# pdp8i-fpga.net
KiCad netlist of a schematic drawn in EAGLE
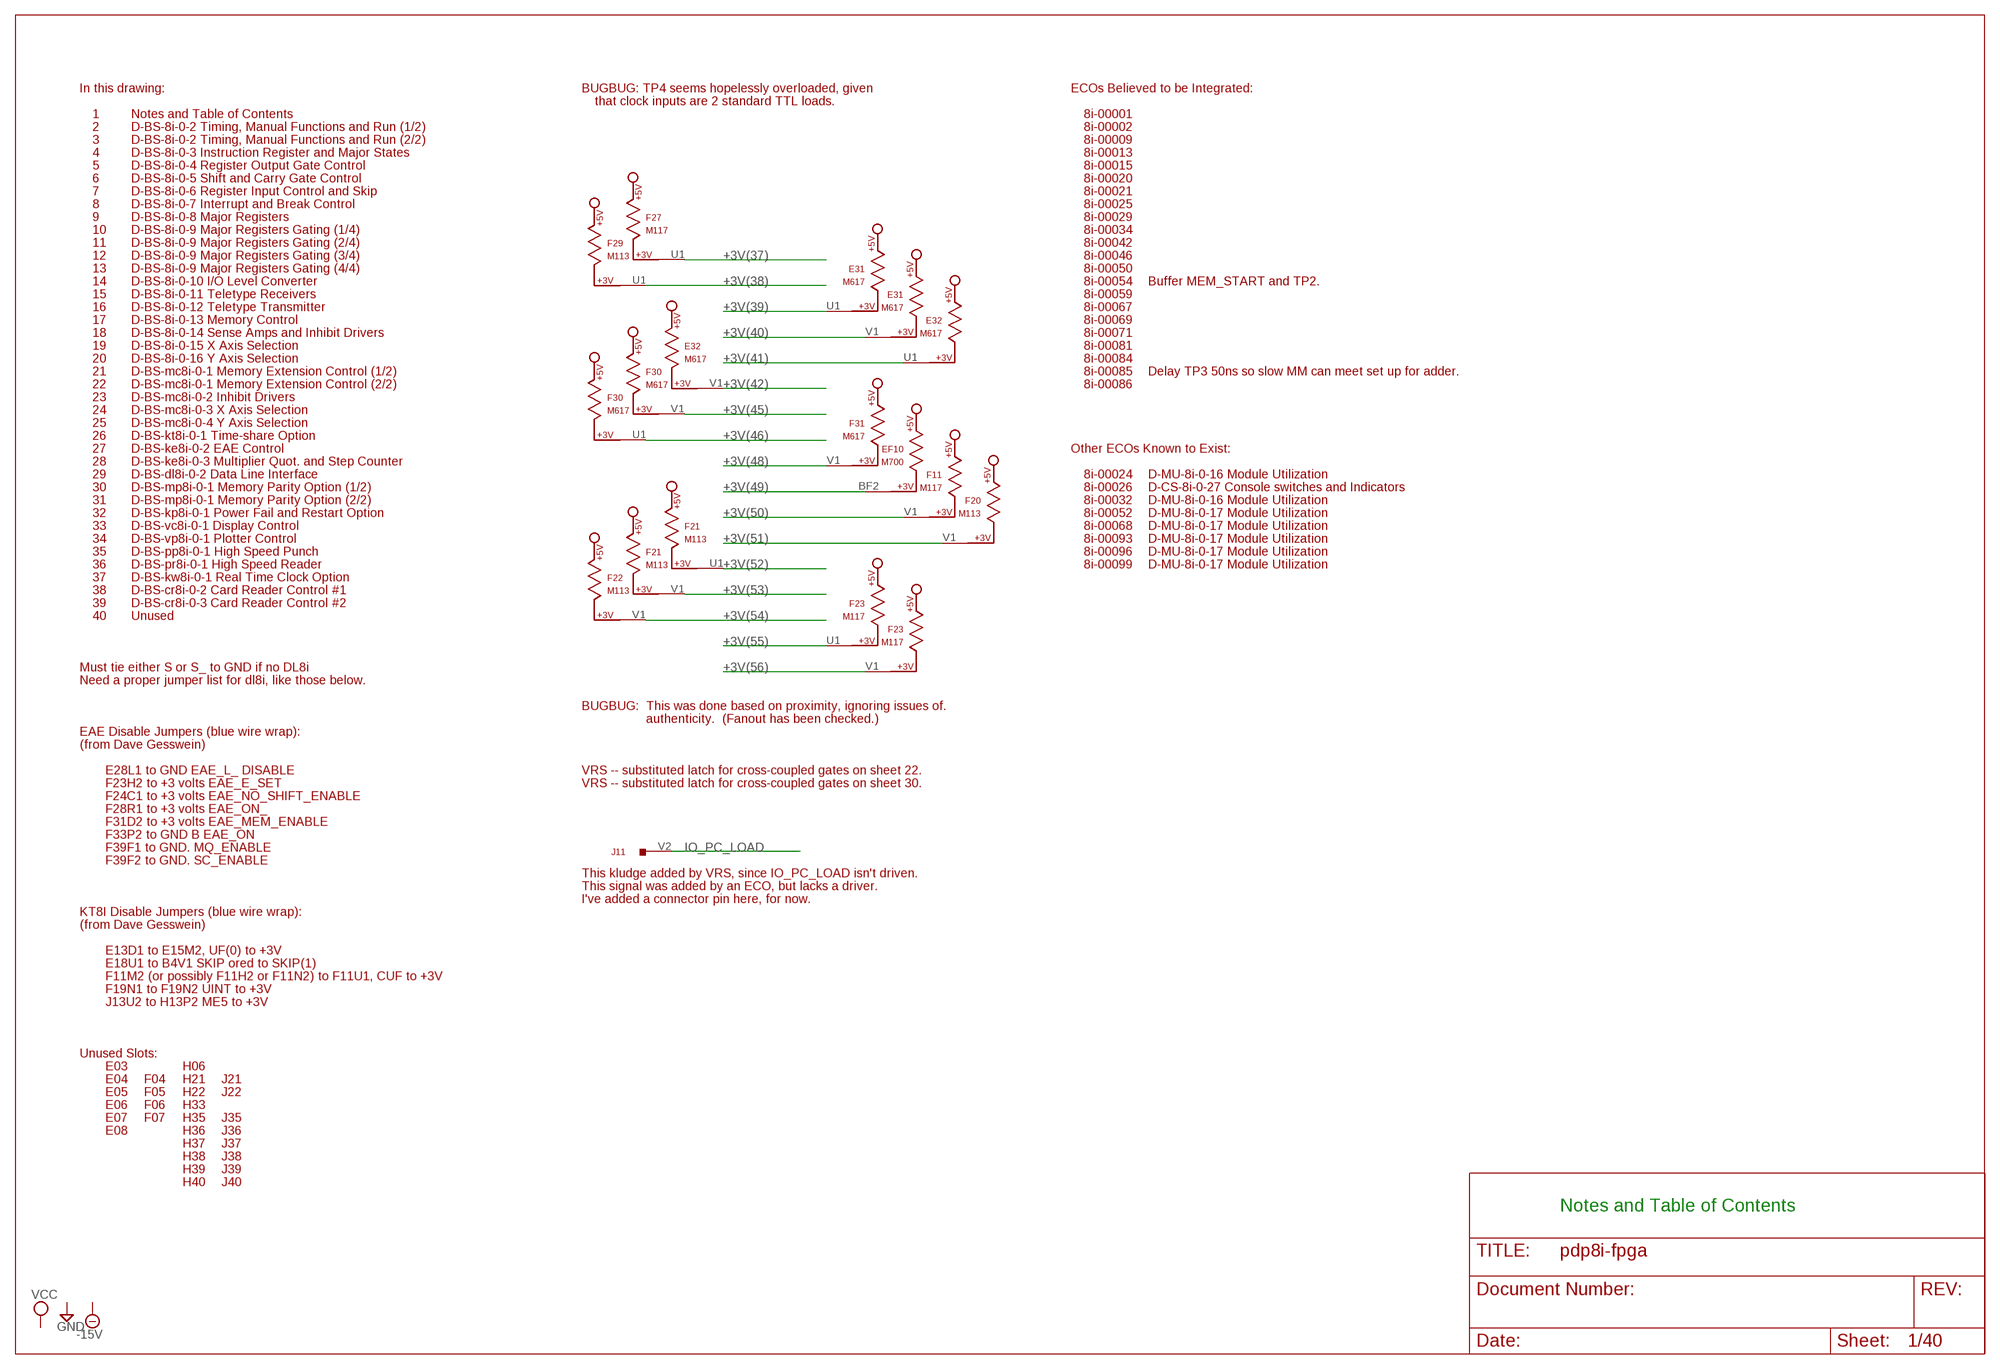
[diagram p0: schematic, sheet 1]
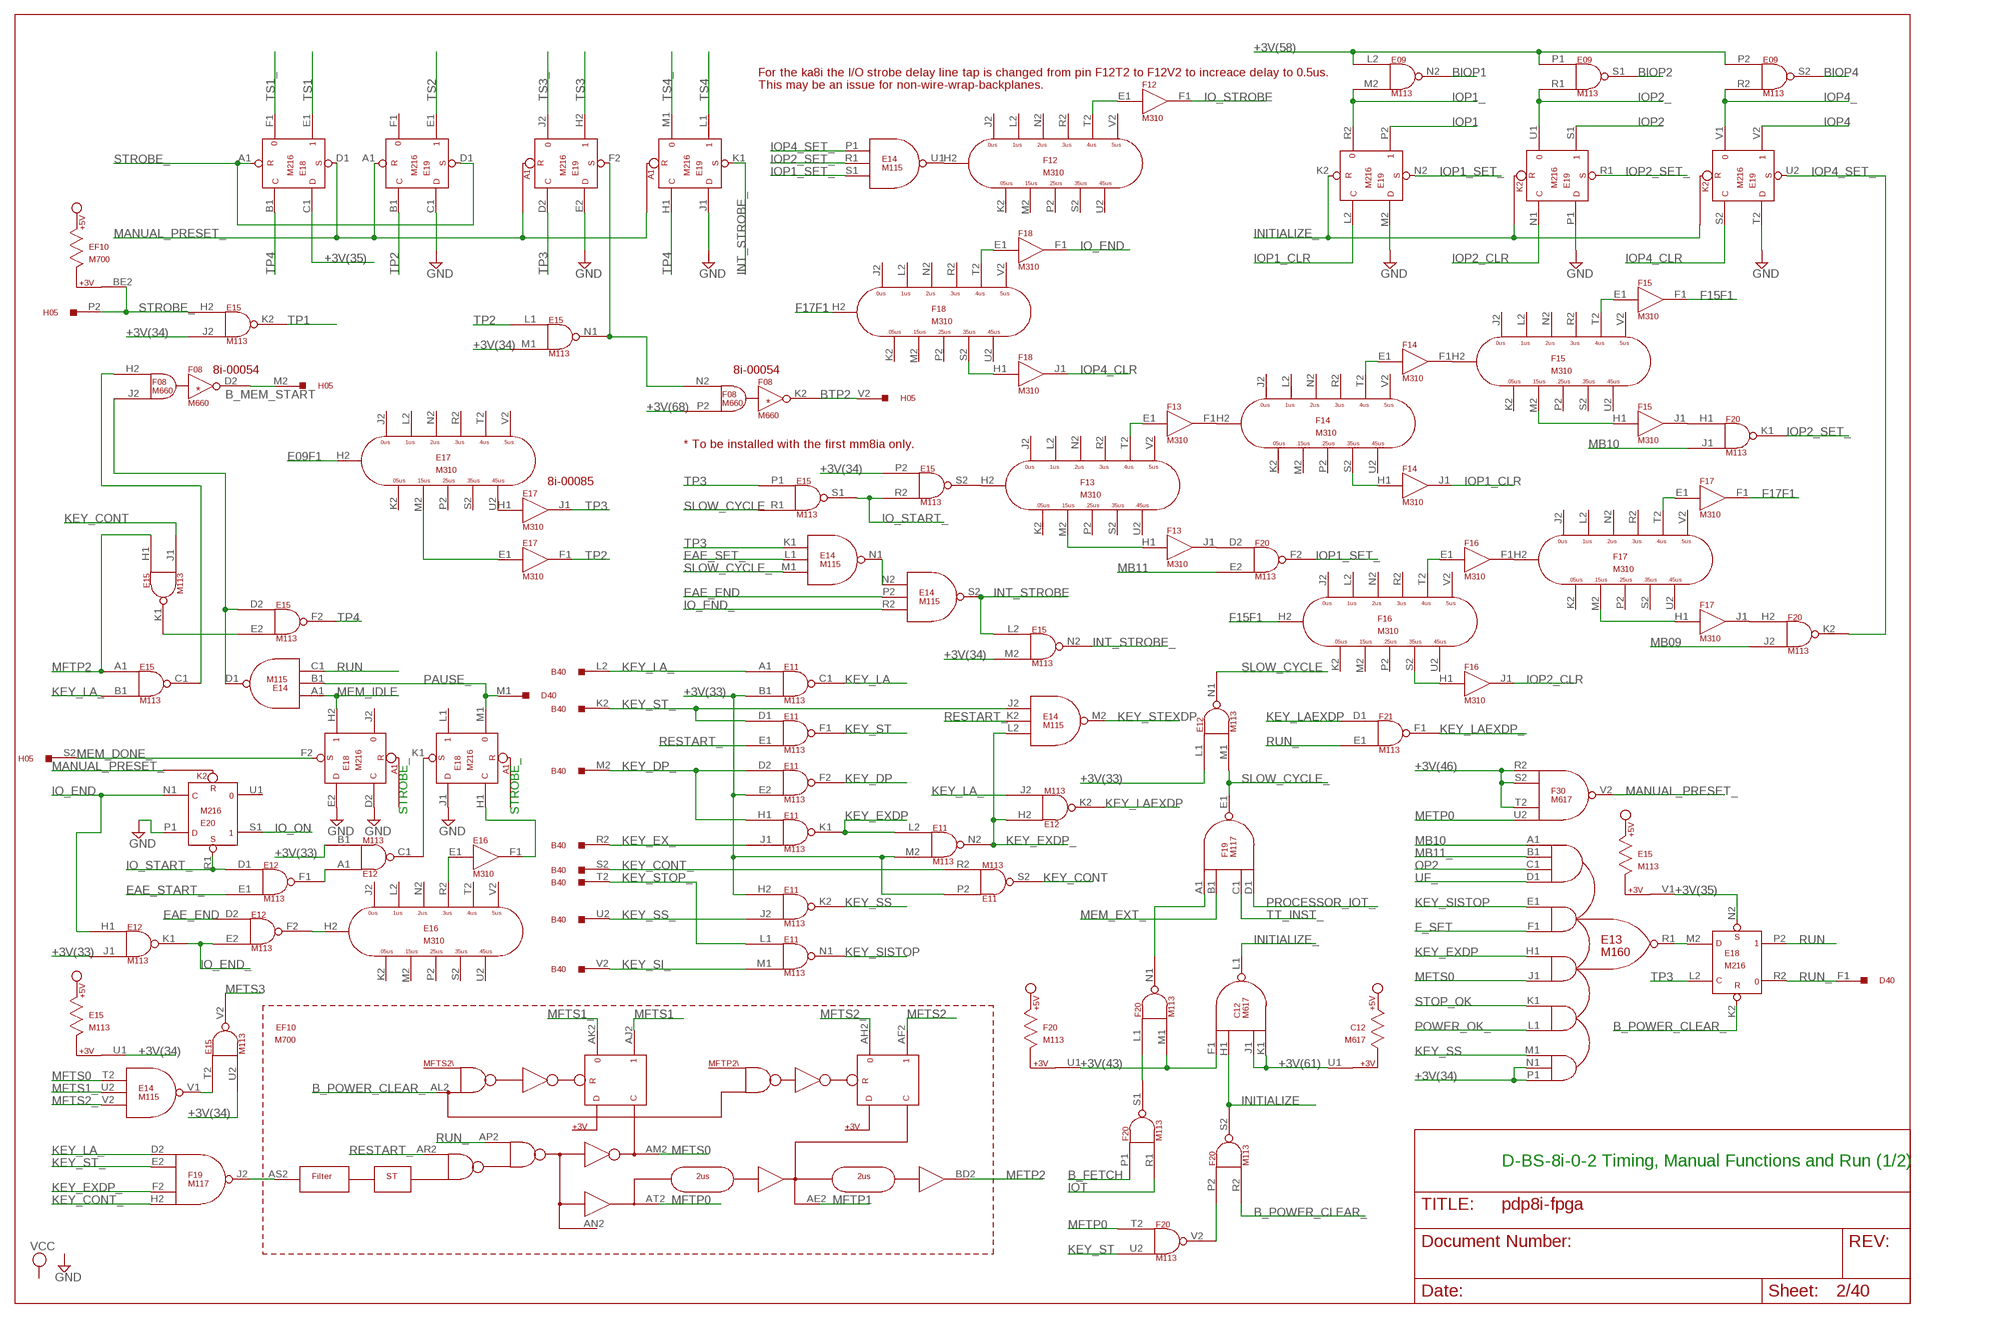
[diagram p1: schematic, sheet 2]
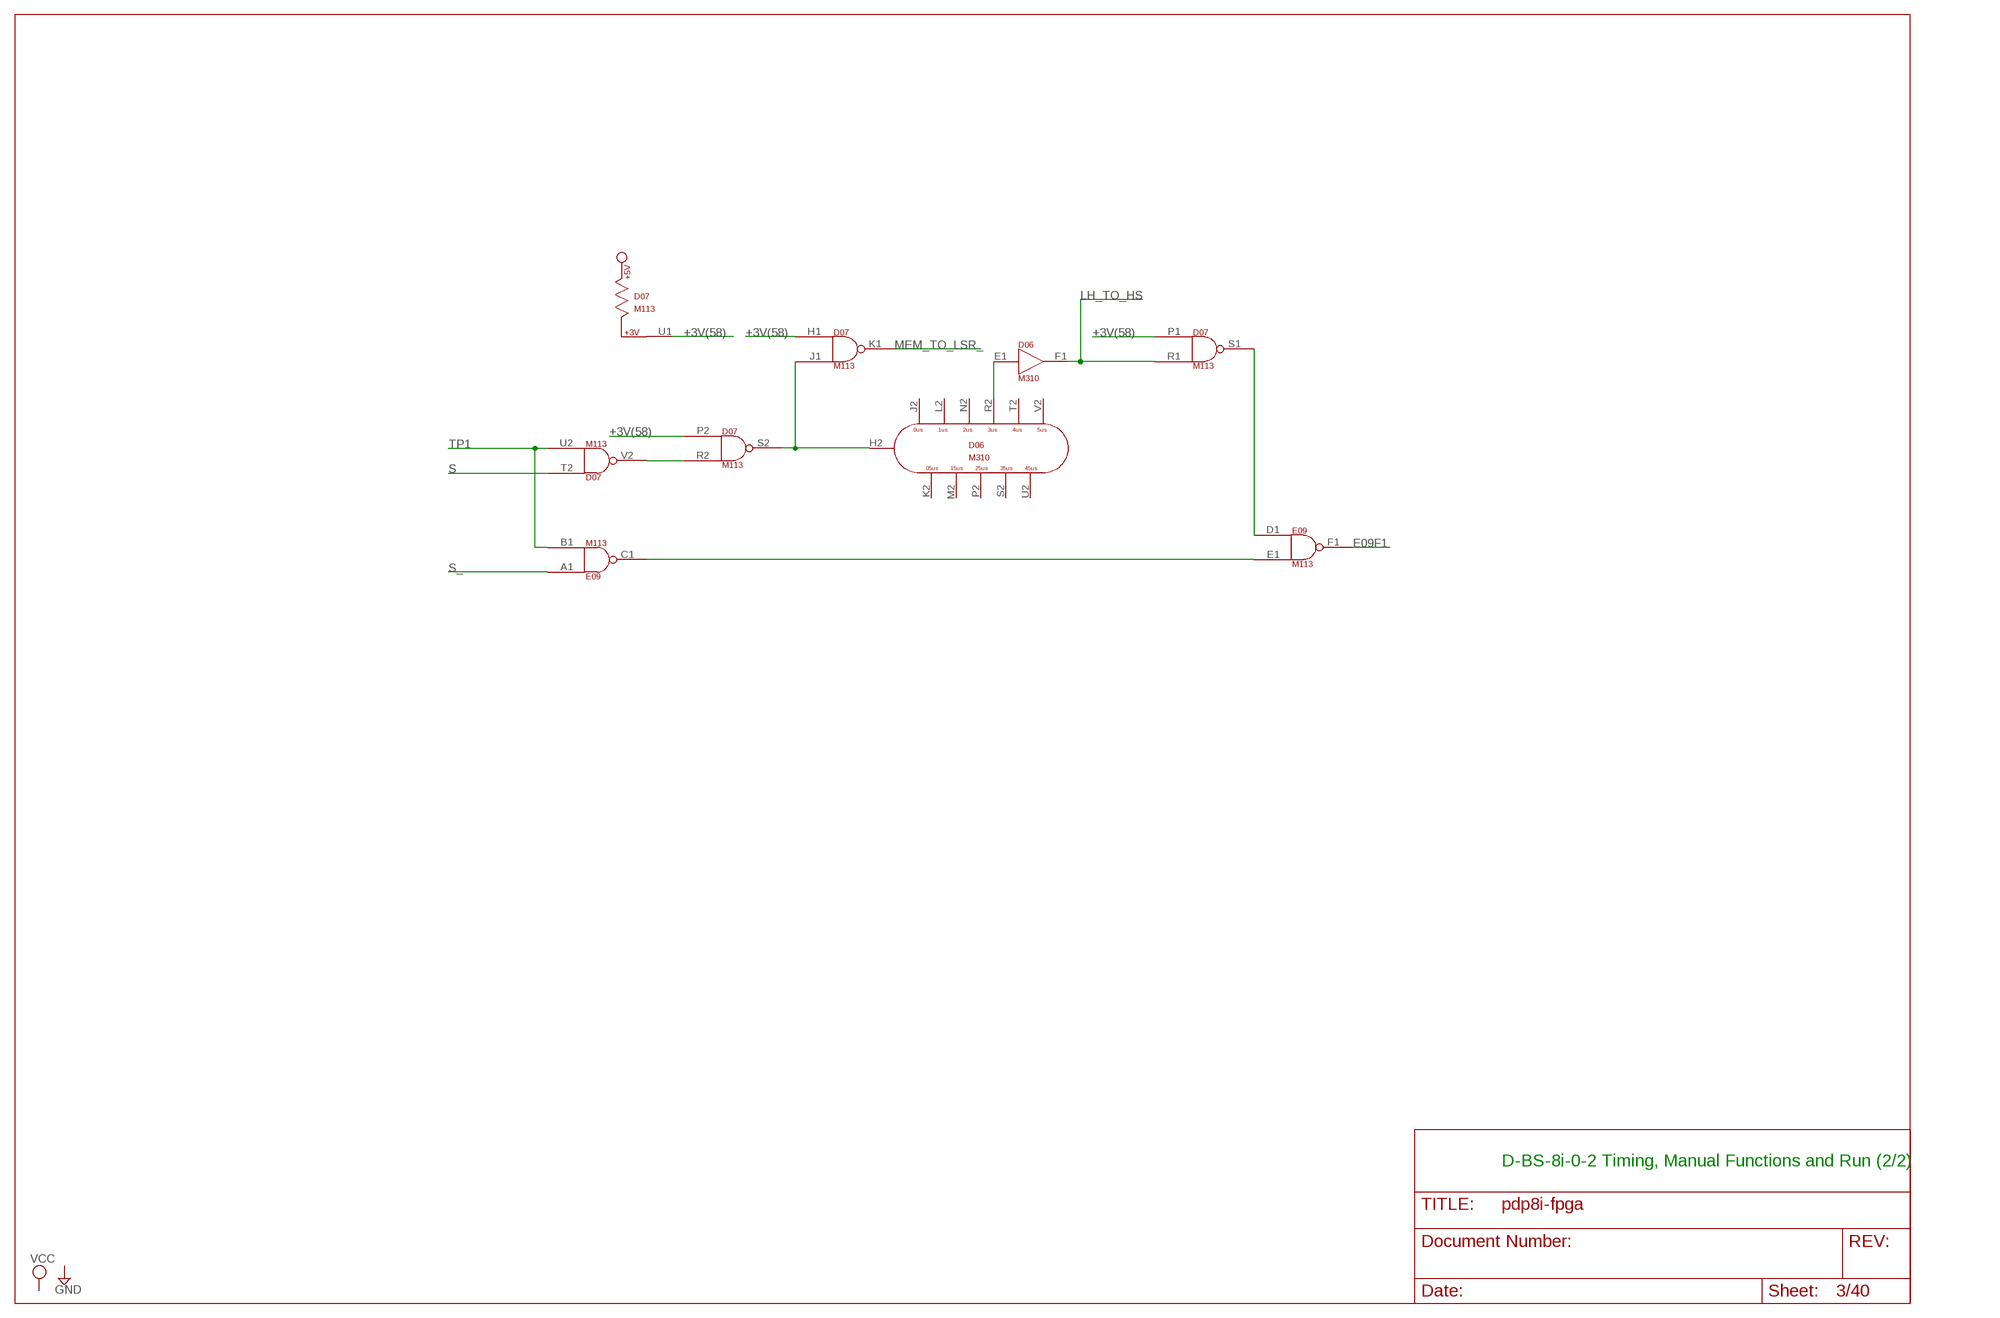
[diagram p2: schematic, sheet 3]
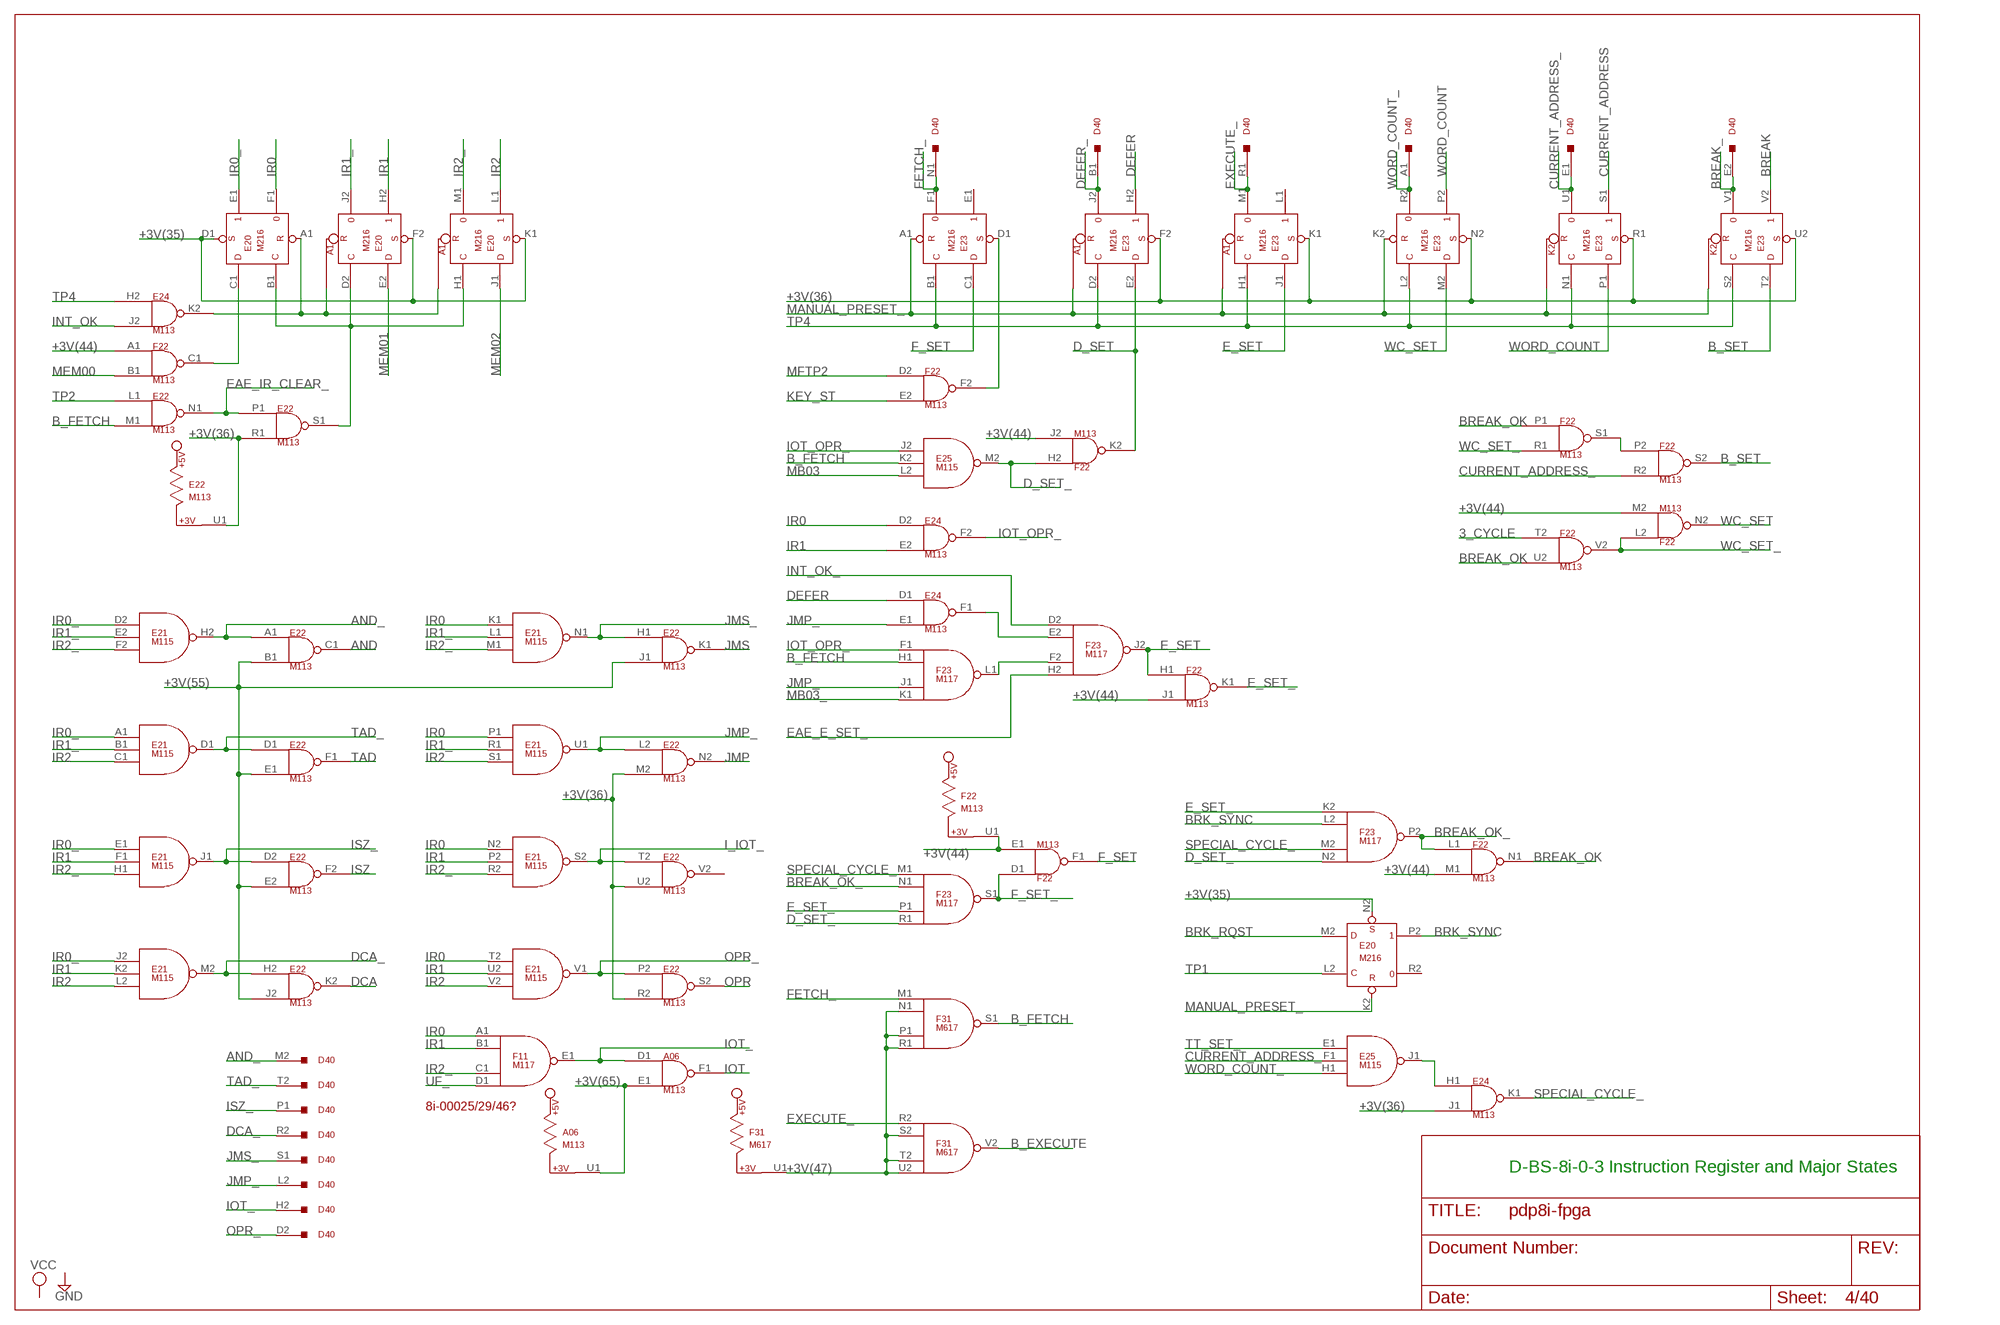
[diagram p3: schematic, sheet 4]
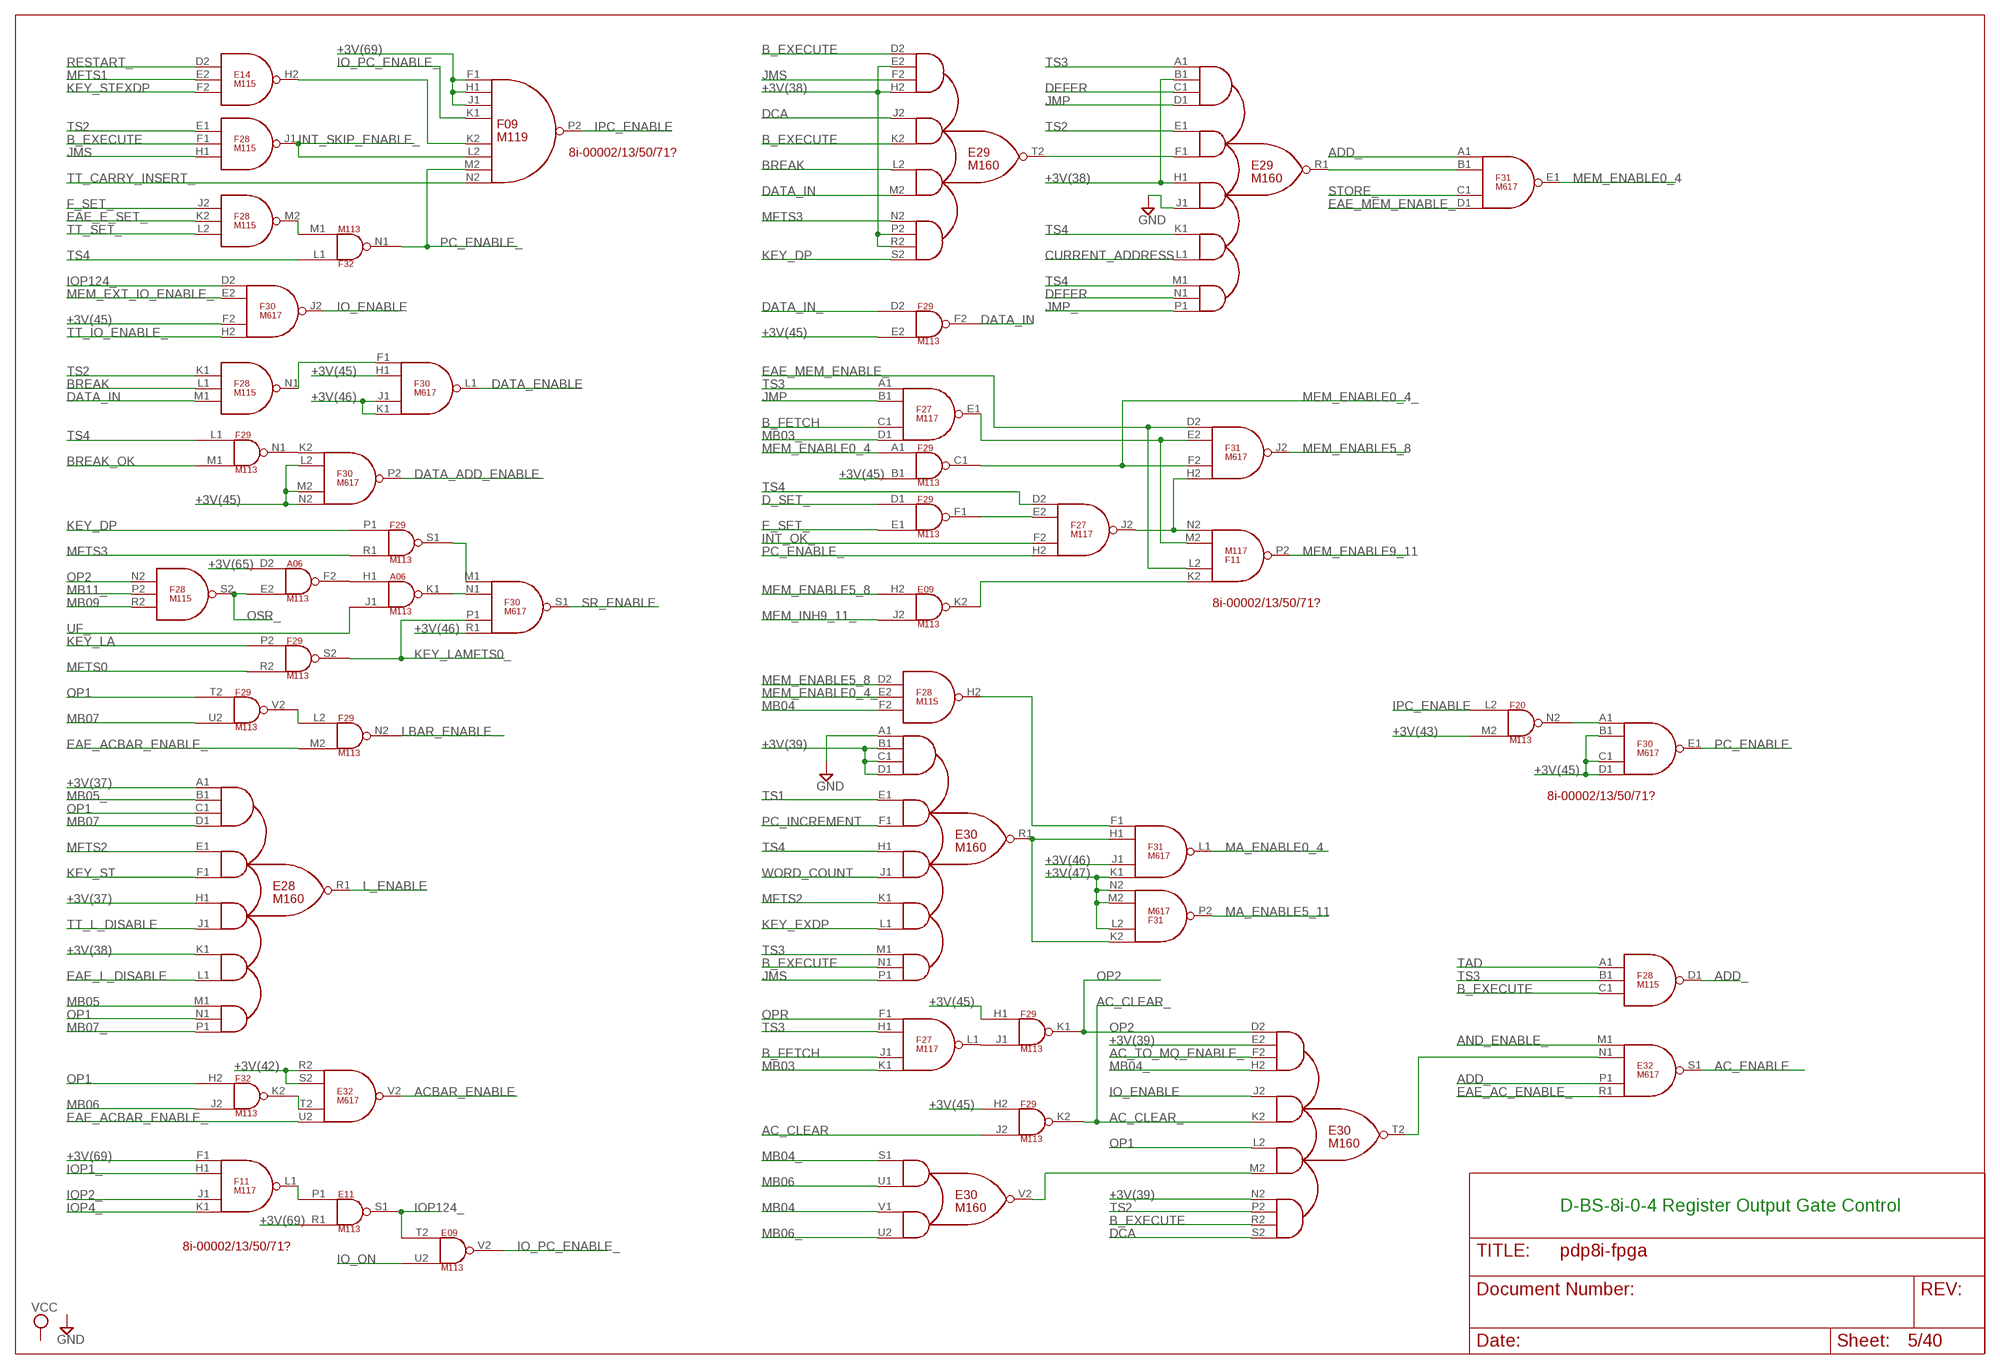
[diagram p4: schematic, sheet 5]
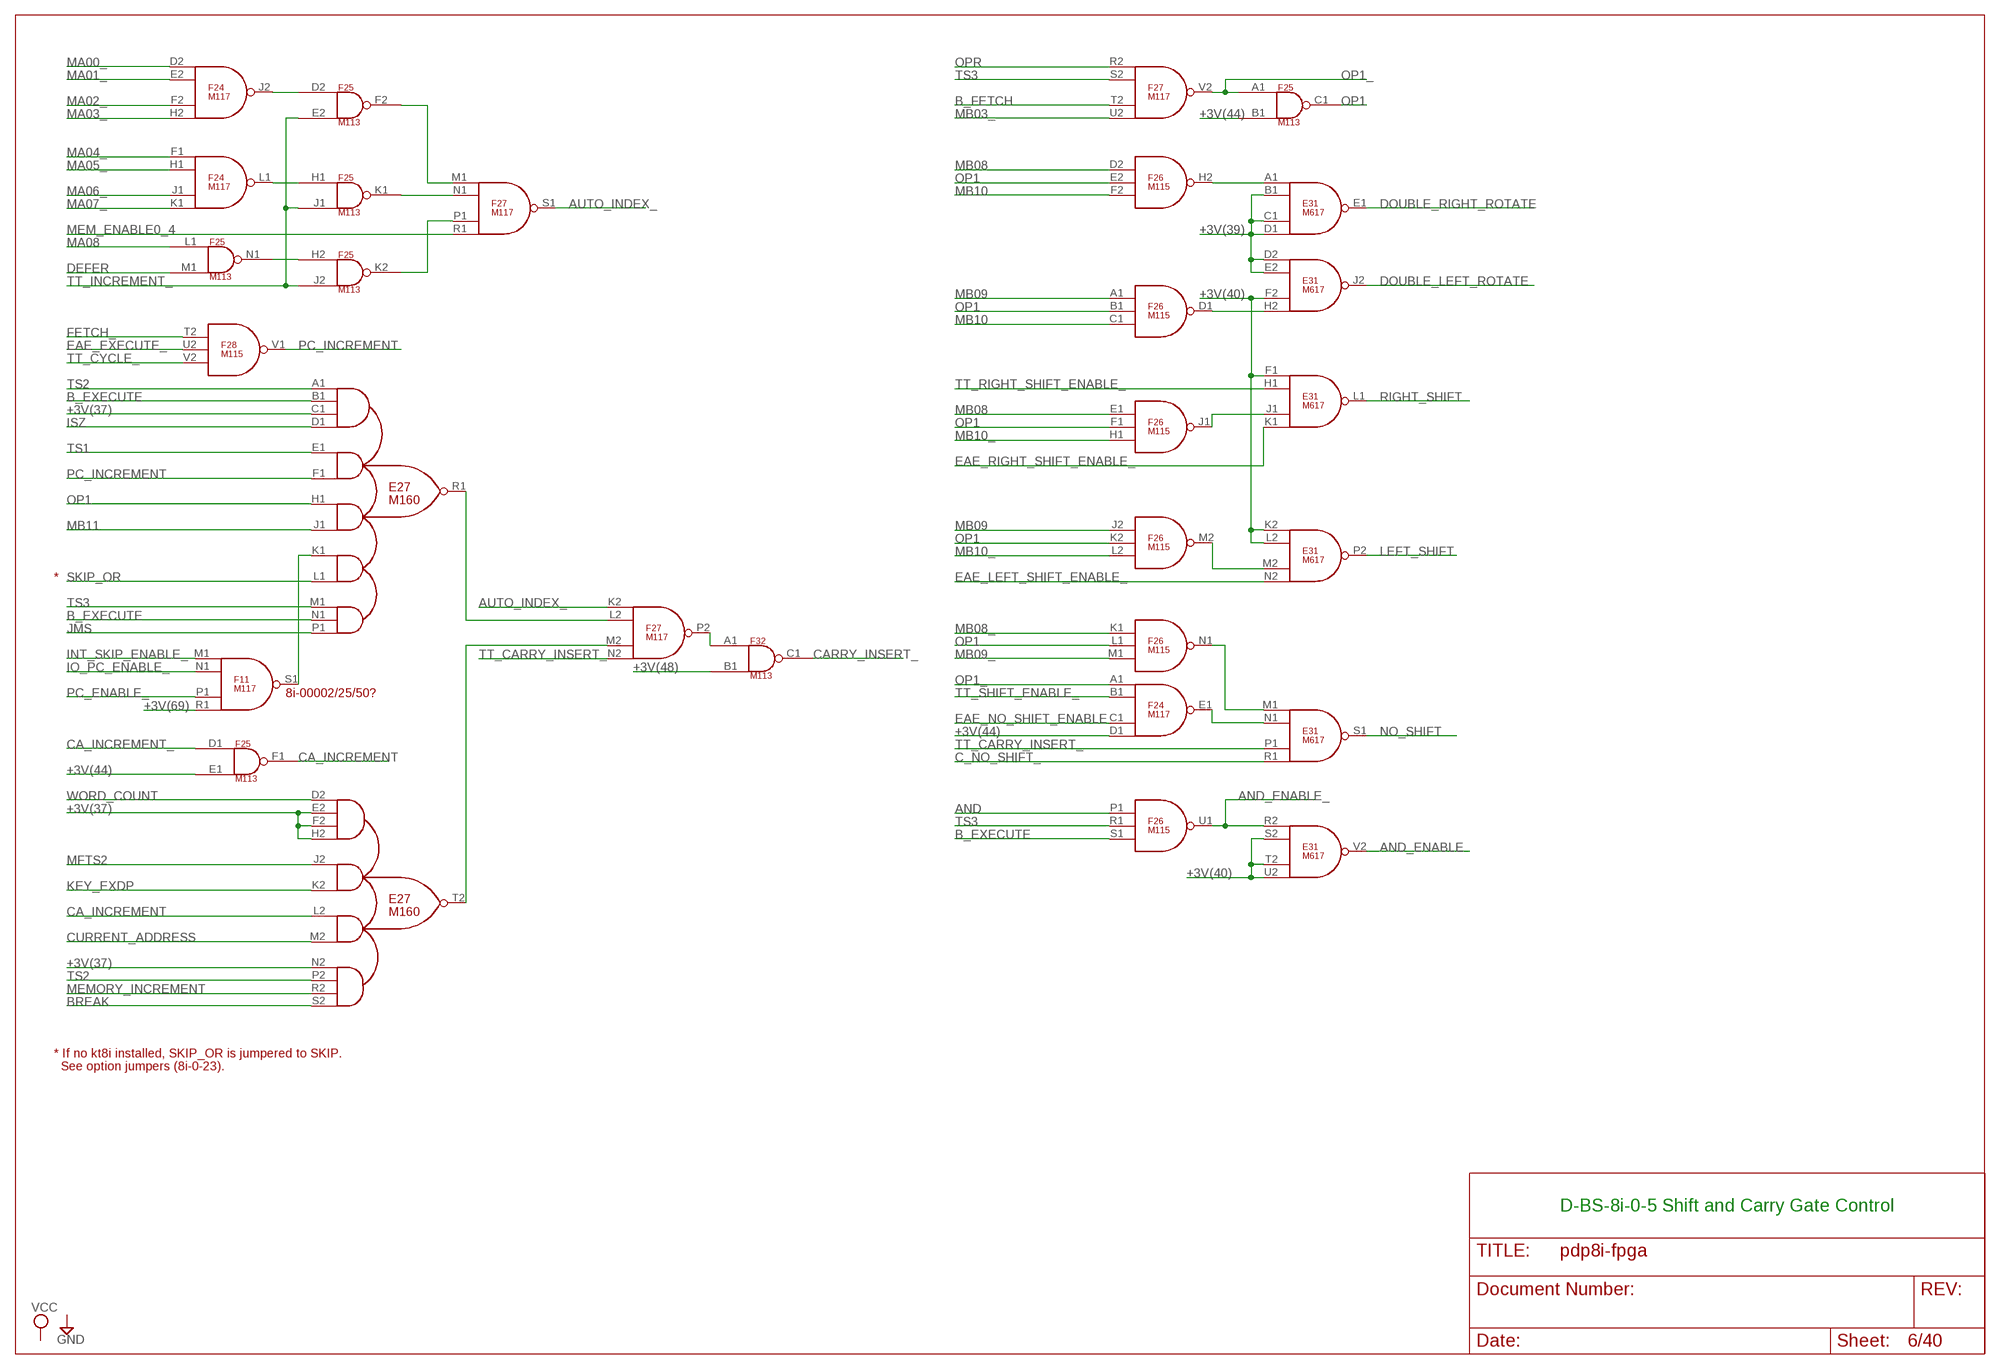
[diagram p5: schematic, sheet 6]
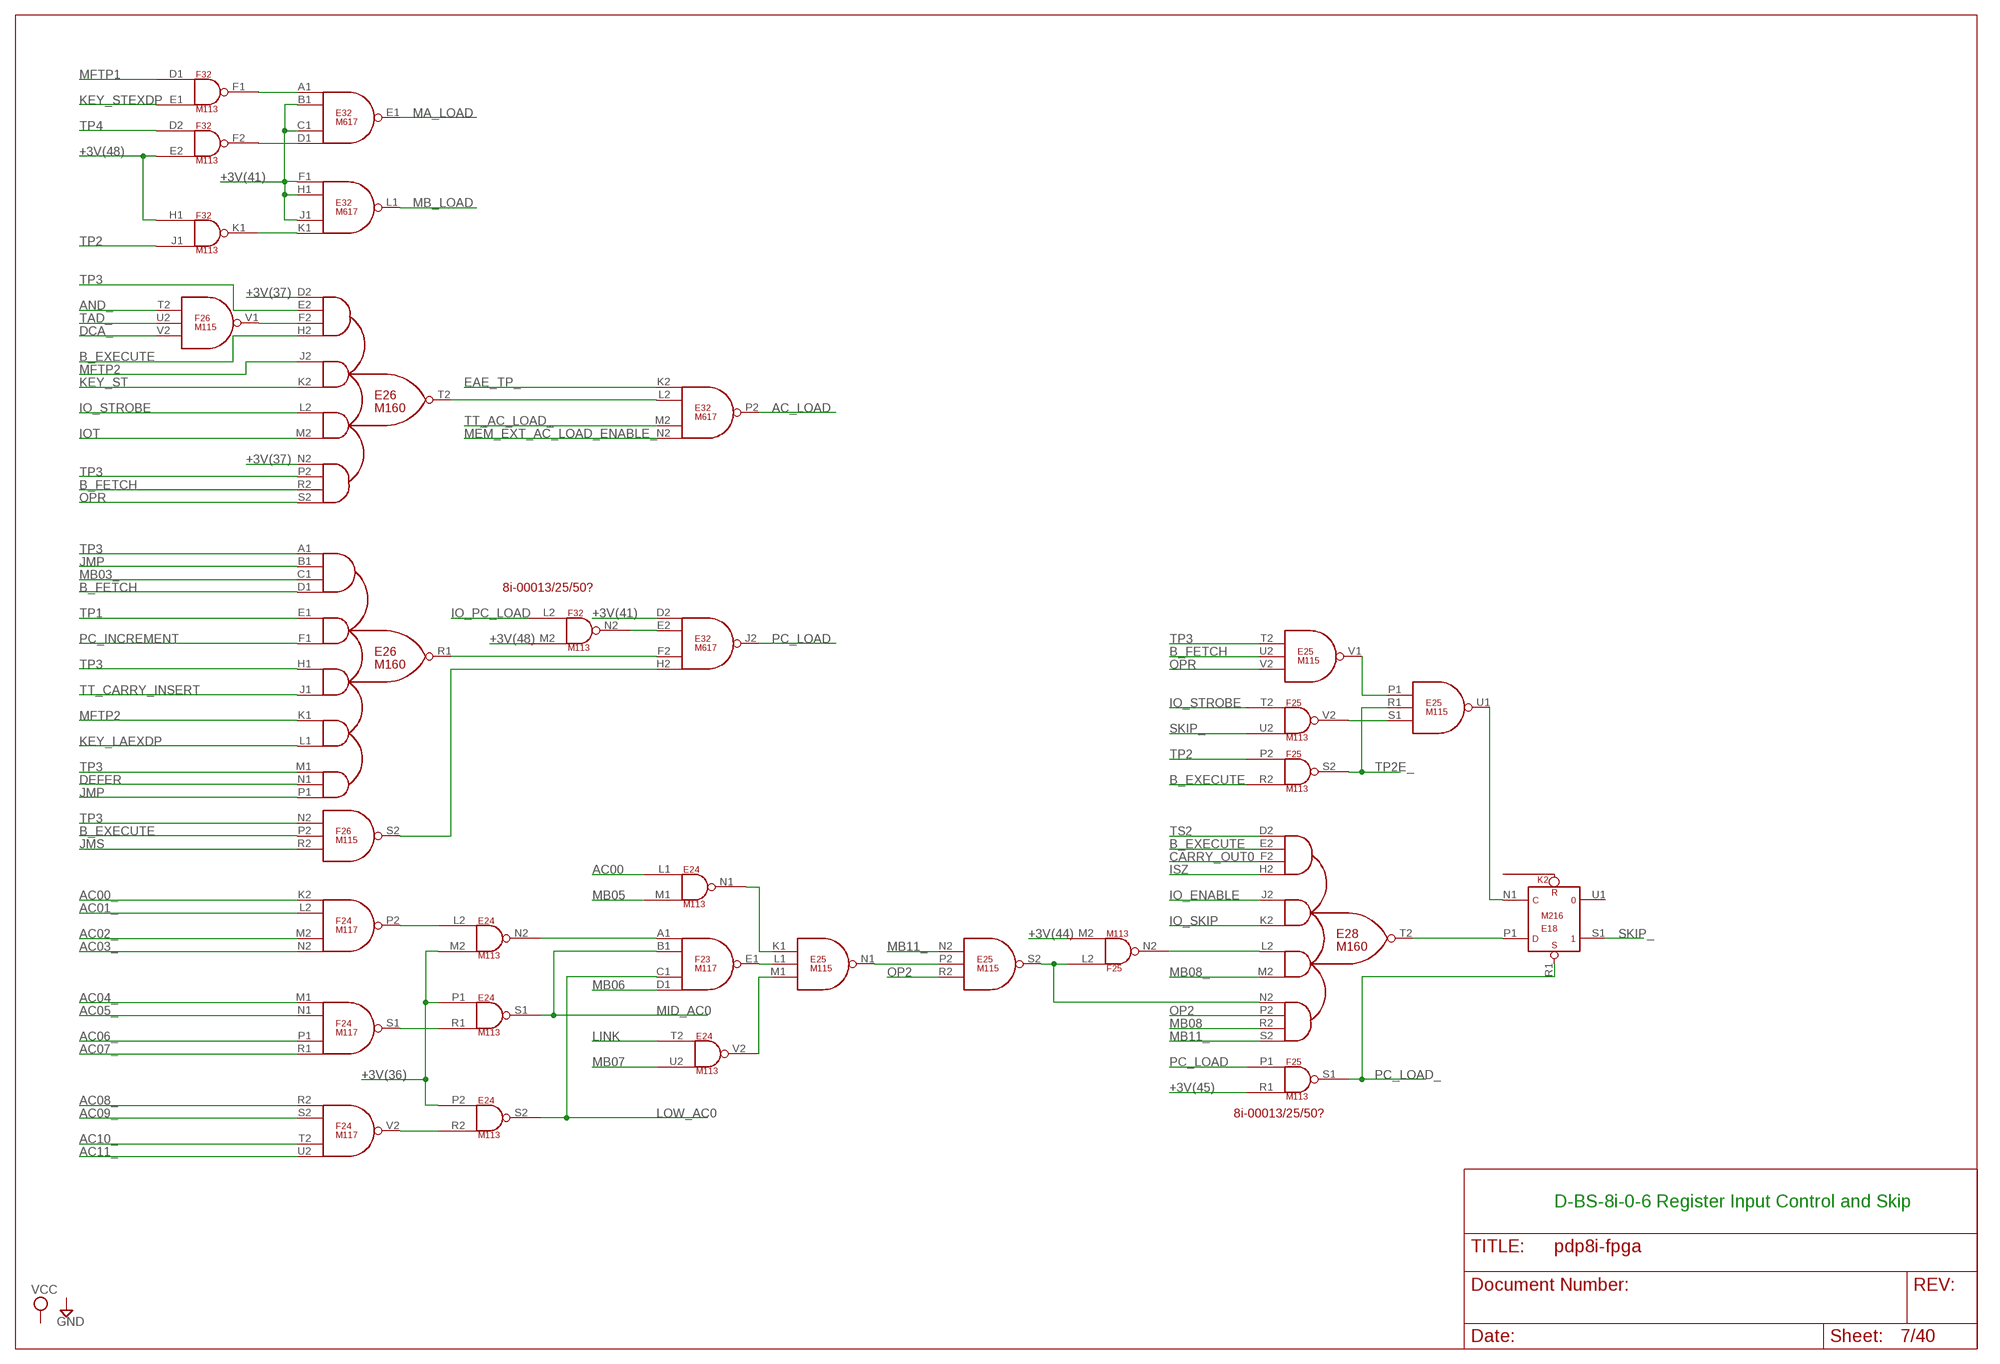
[diagram p6: schematic, sheet 7]
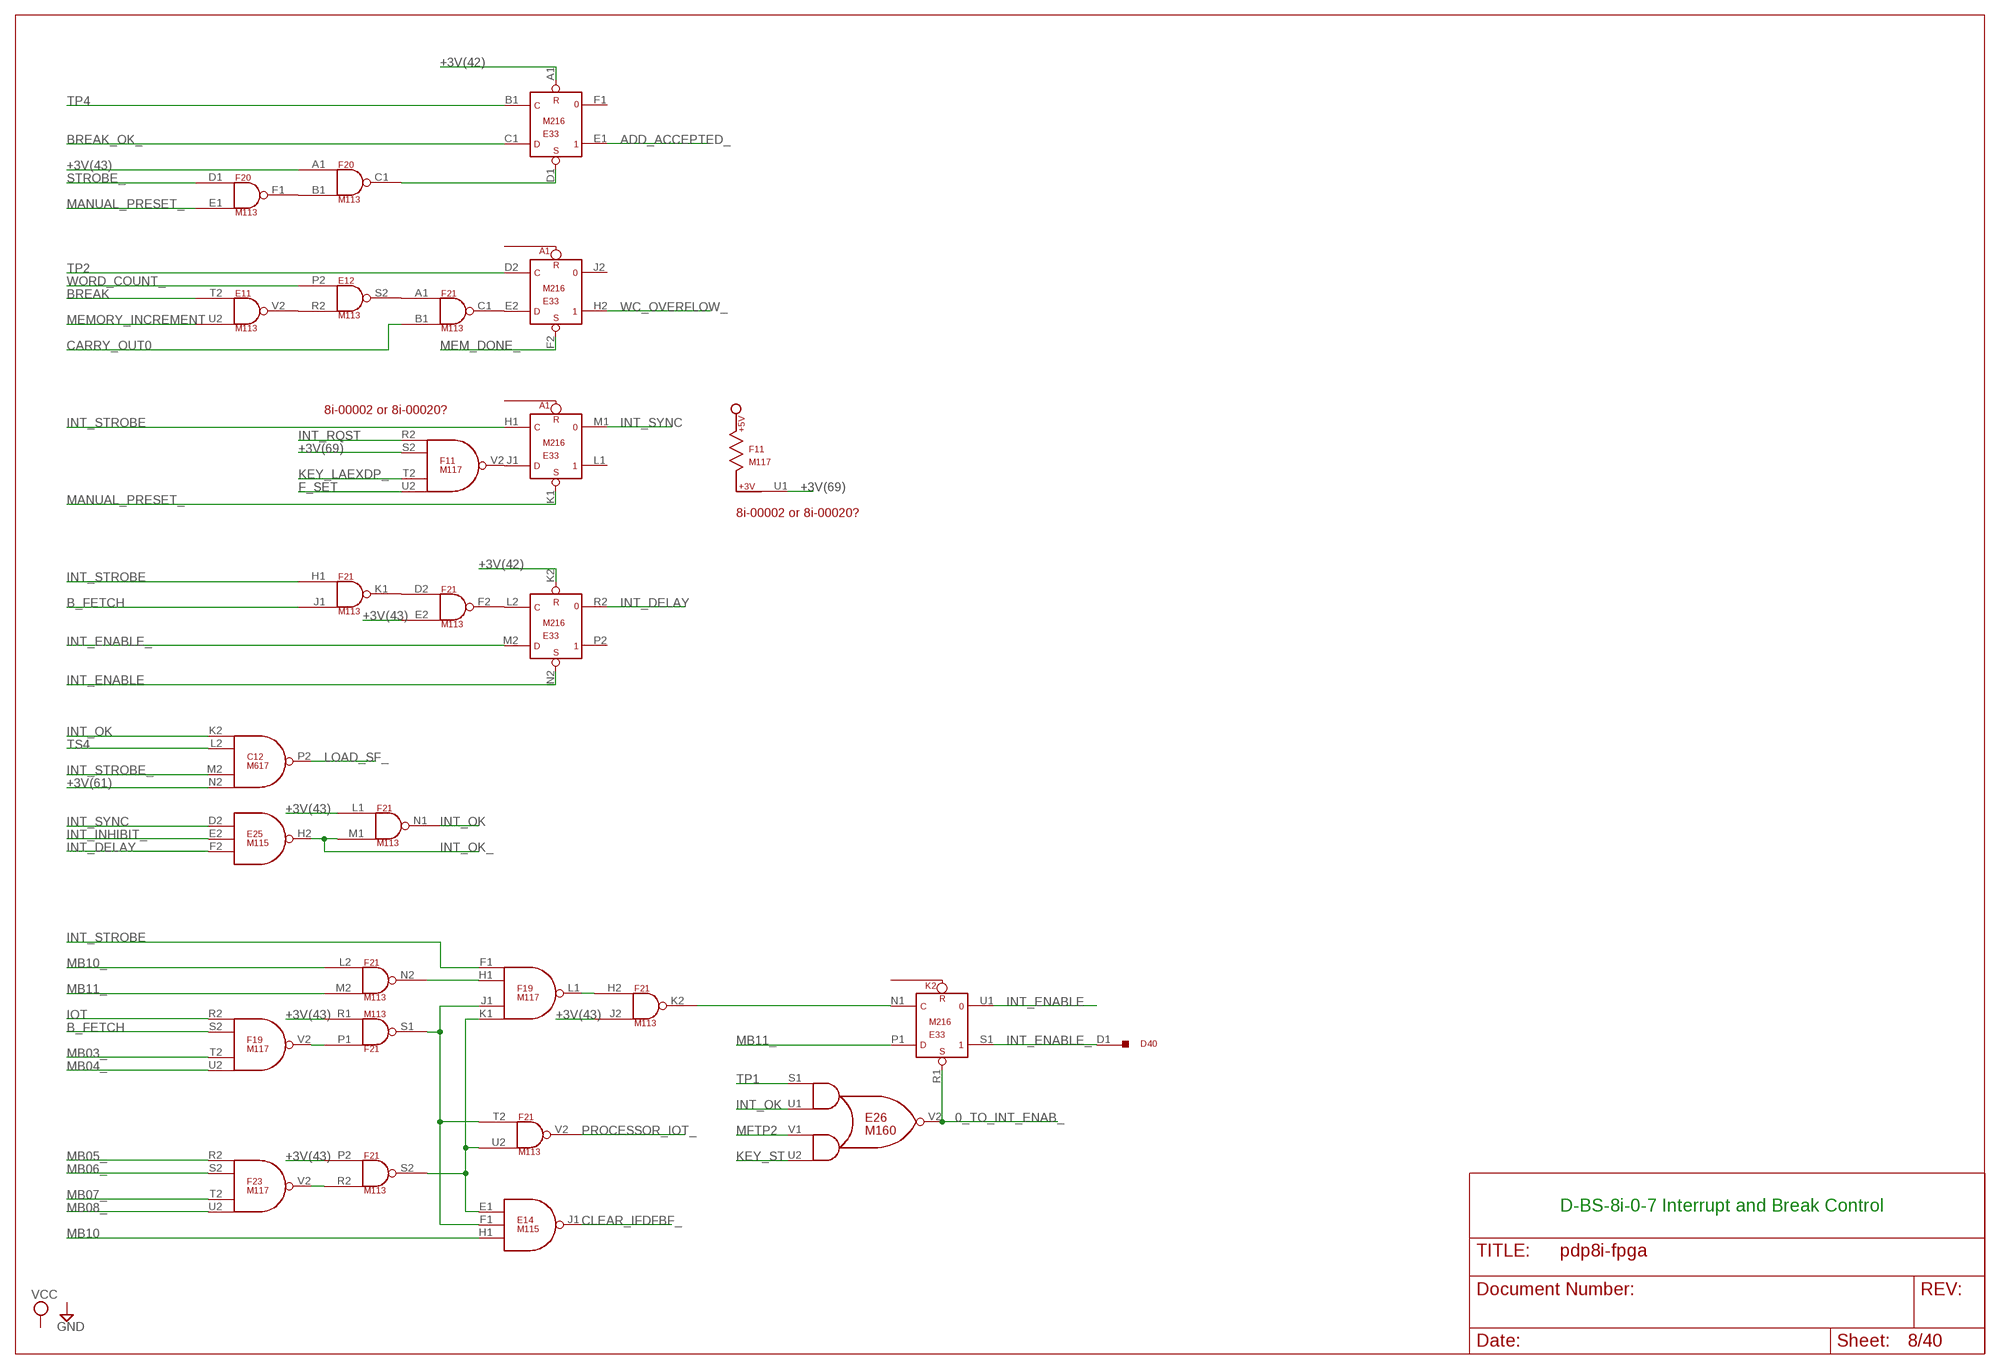
[diagram p7: schematic, sheet 8]
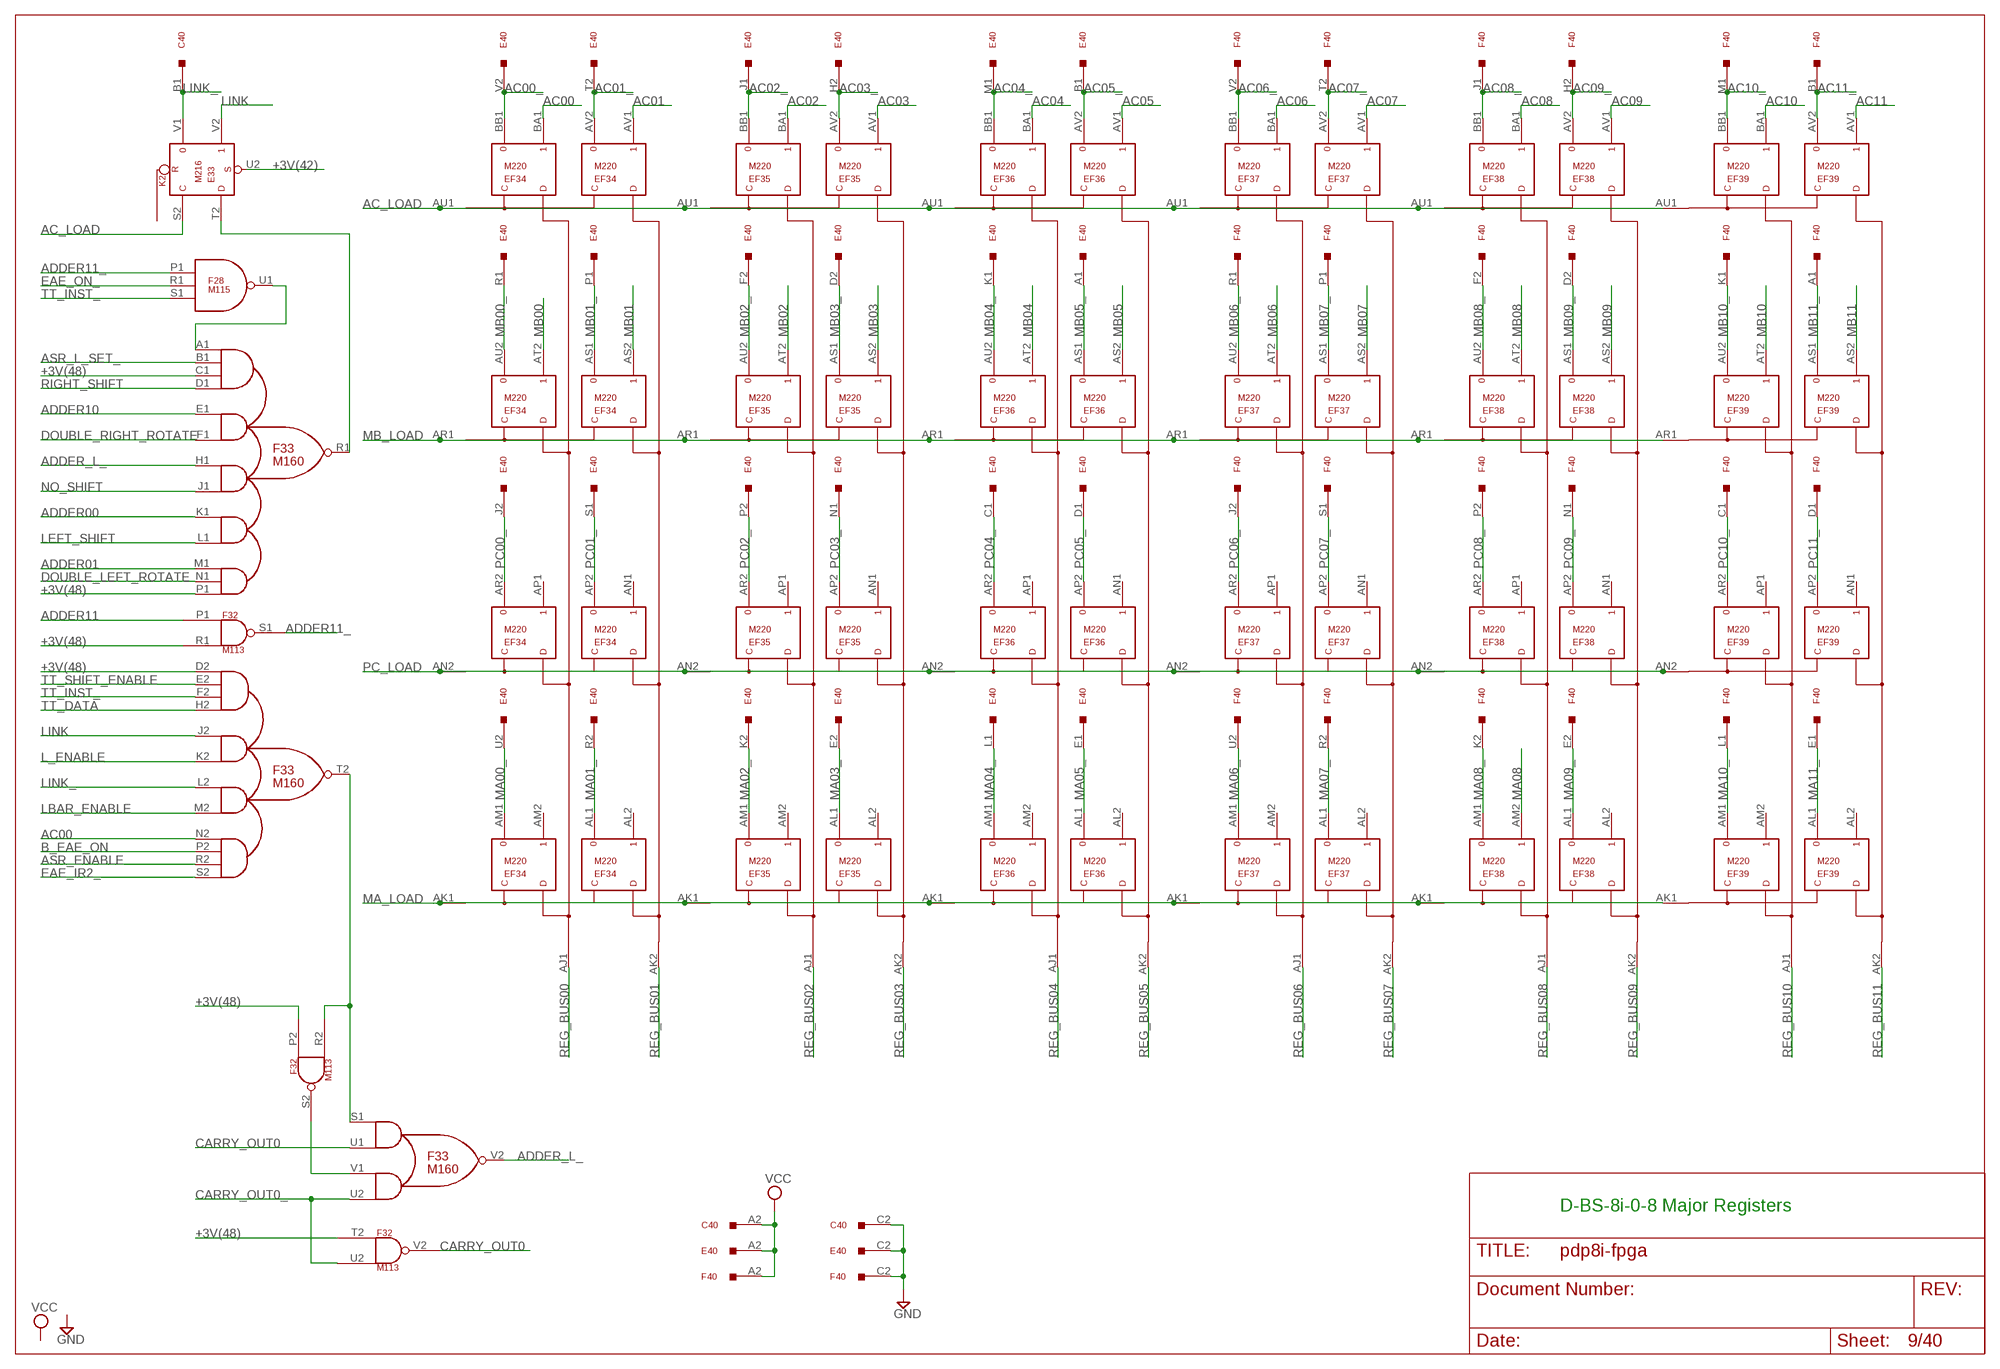
[diagram p8: schematic, sheet 9]
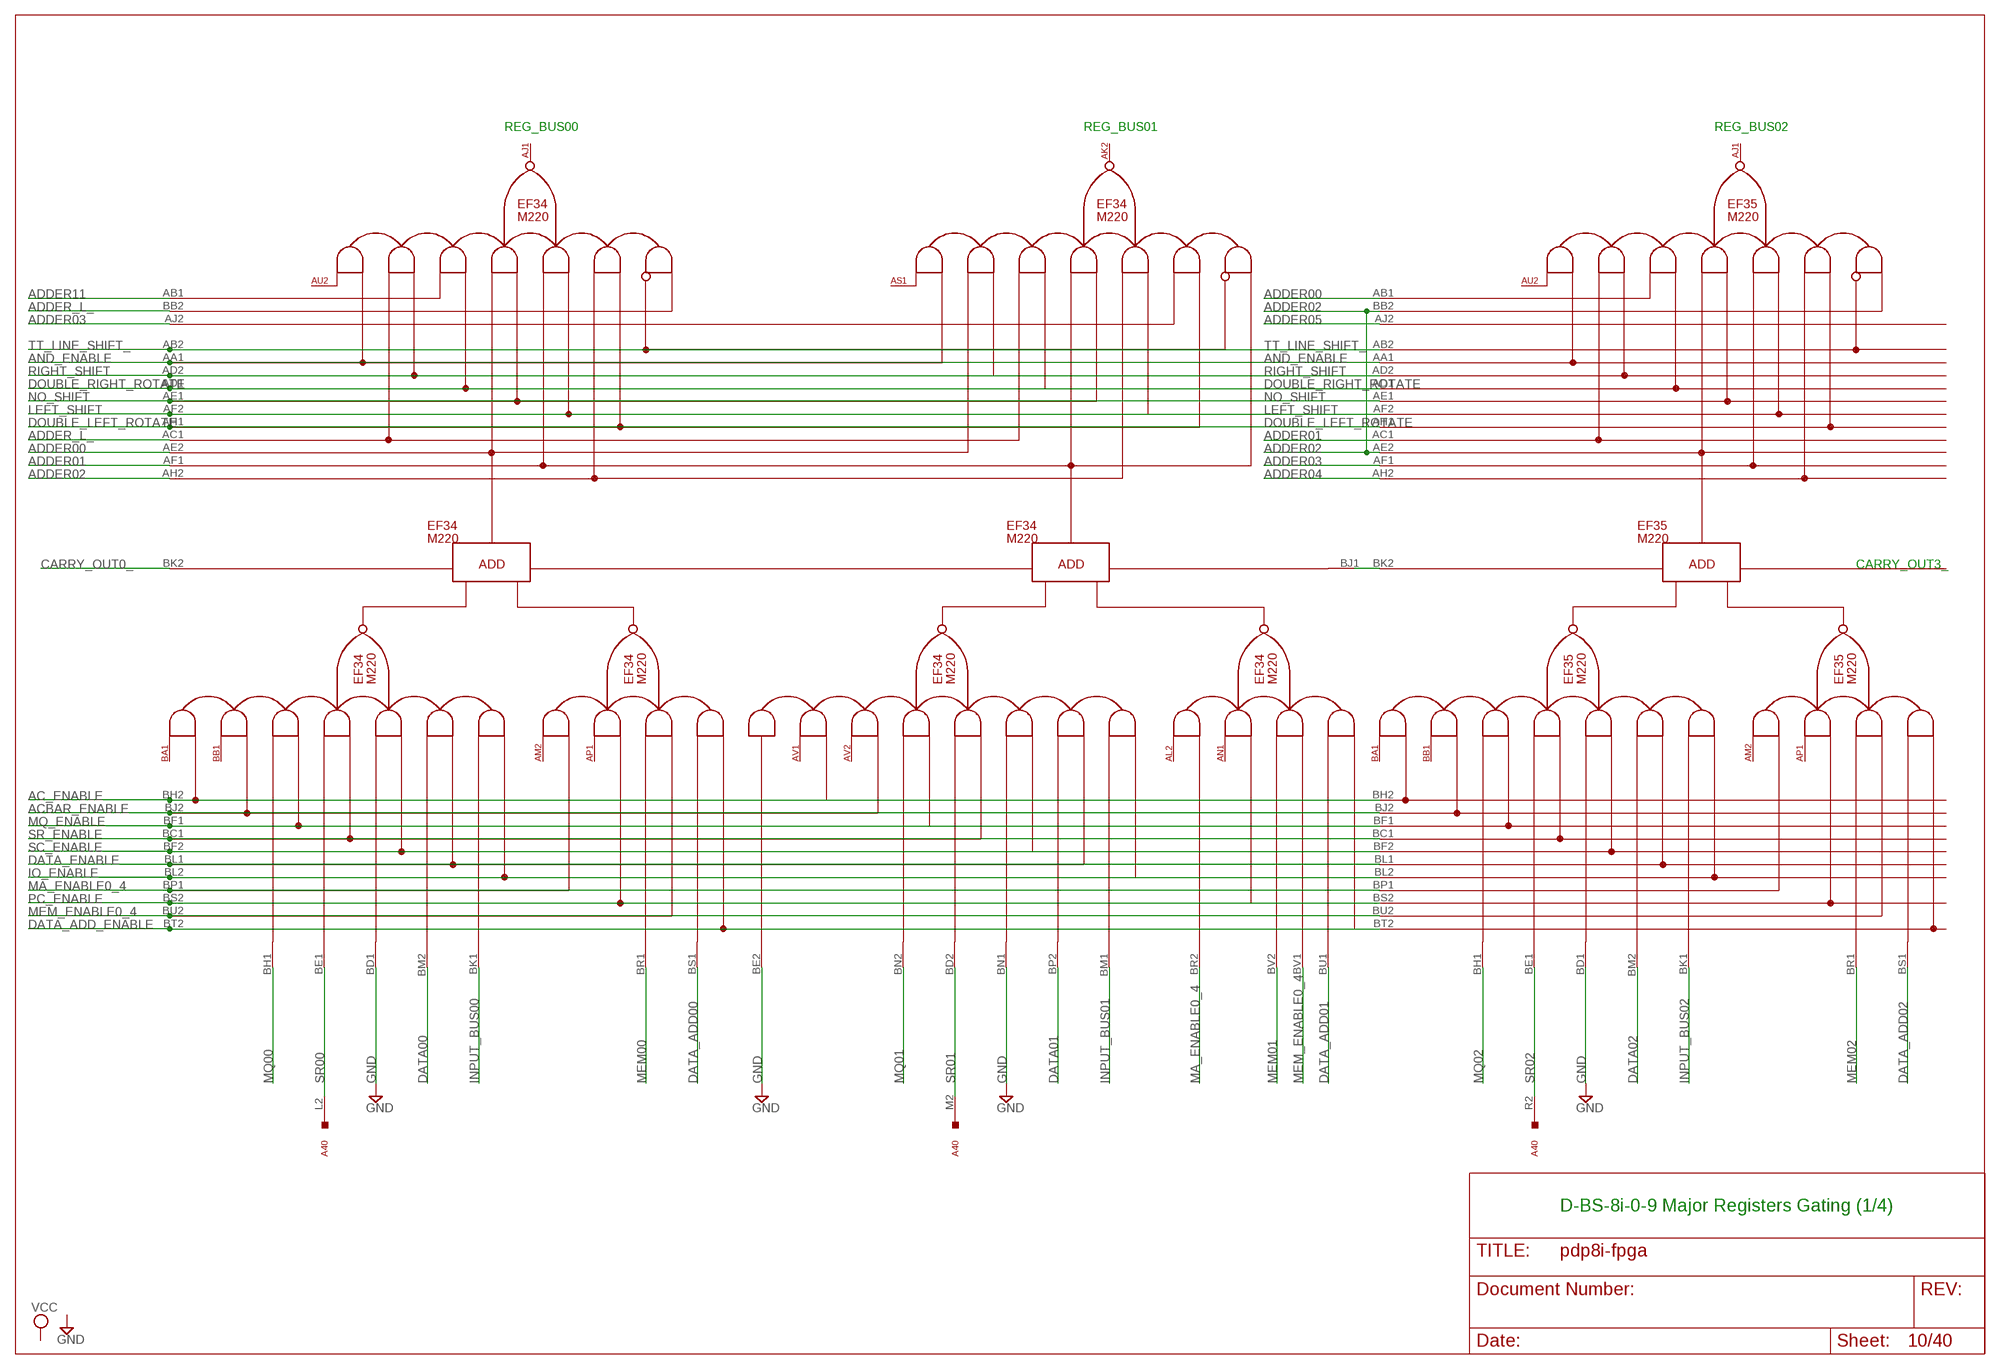
[diagram p9: schematic, sheet 10]
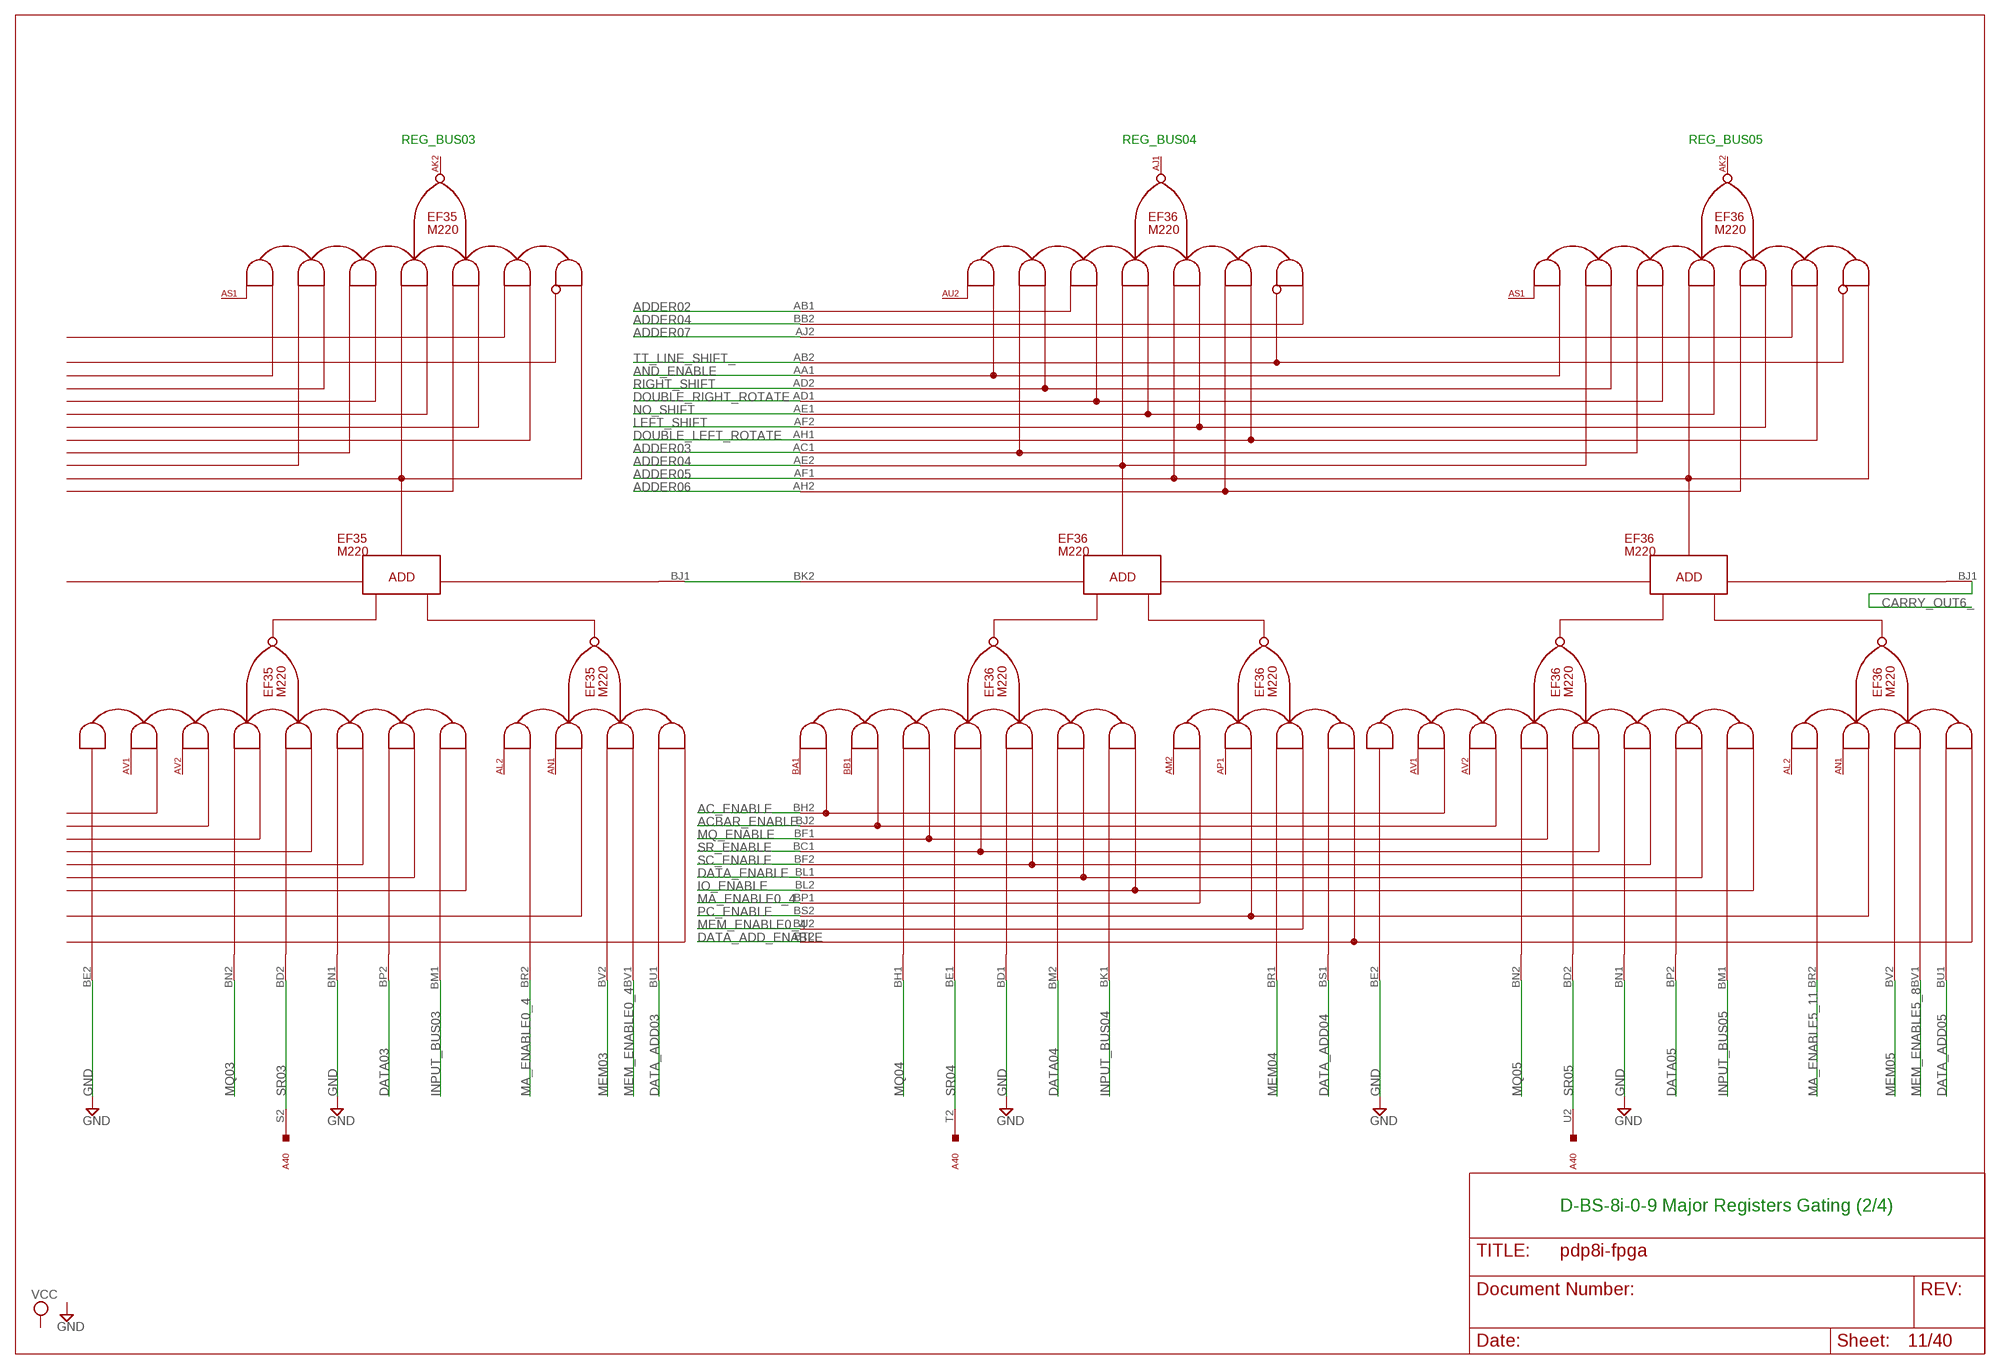
[diagram p10: schematic, sheet 11]
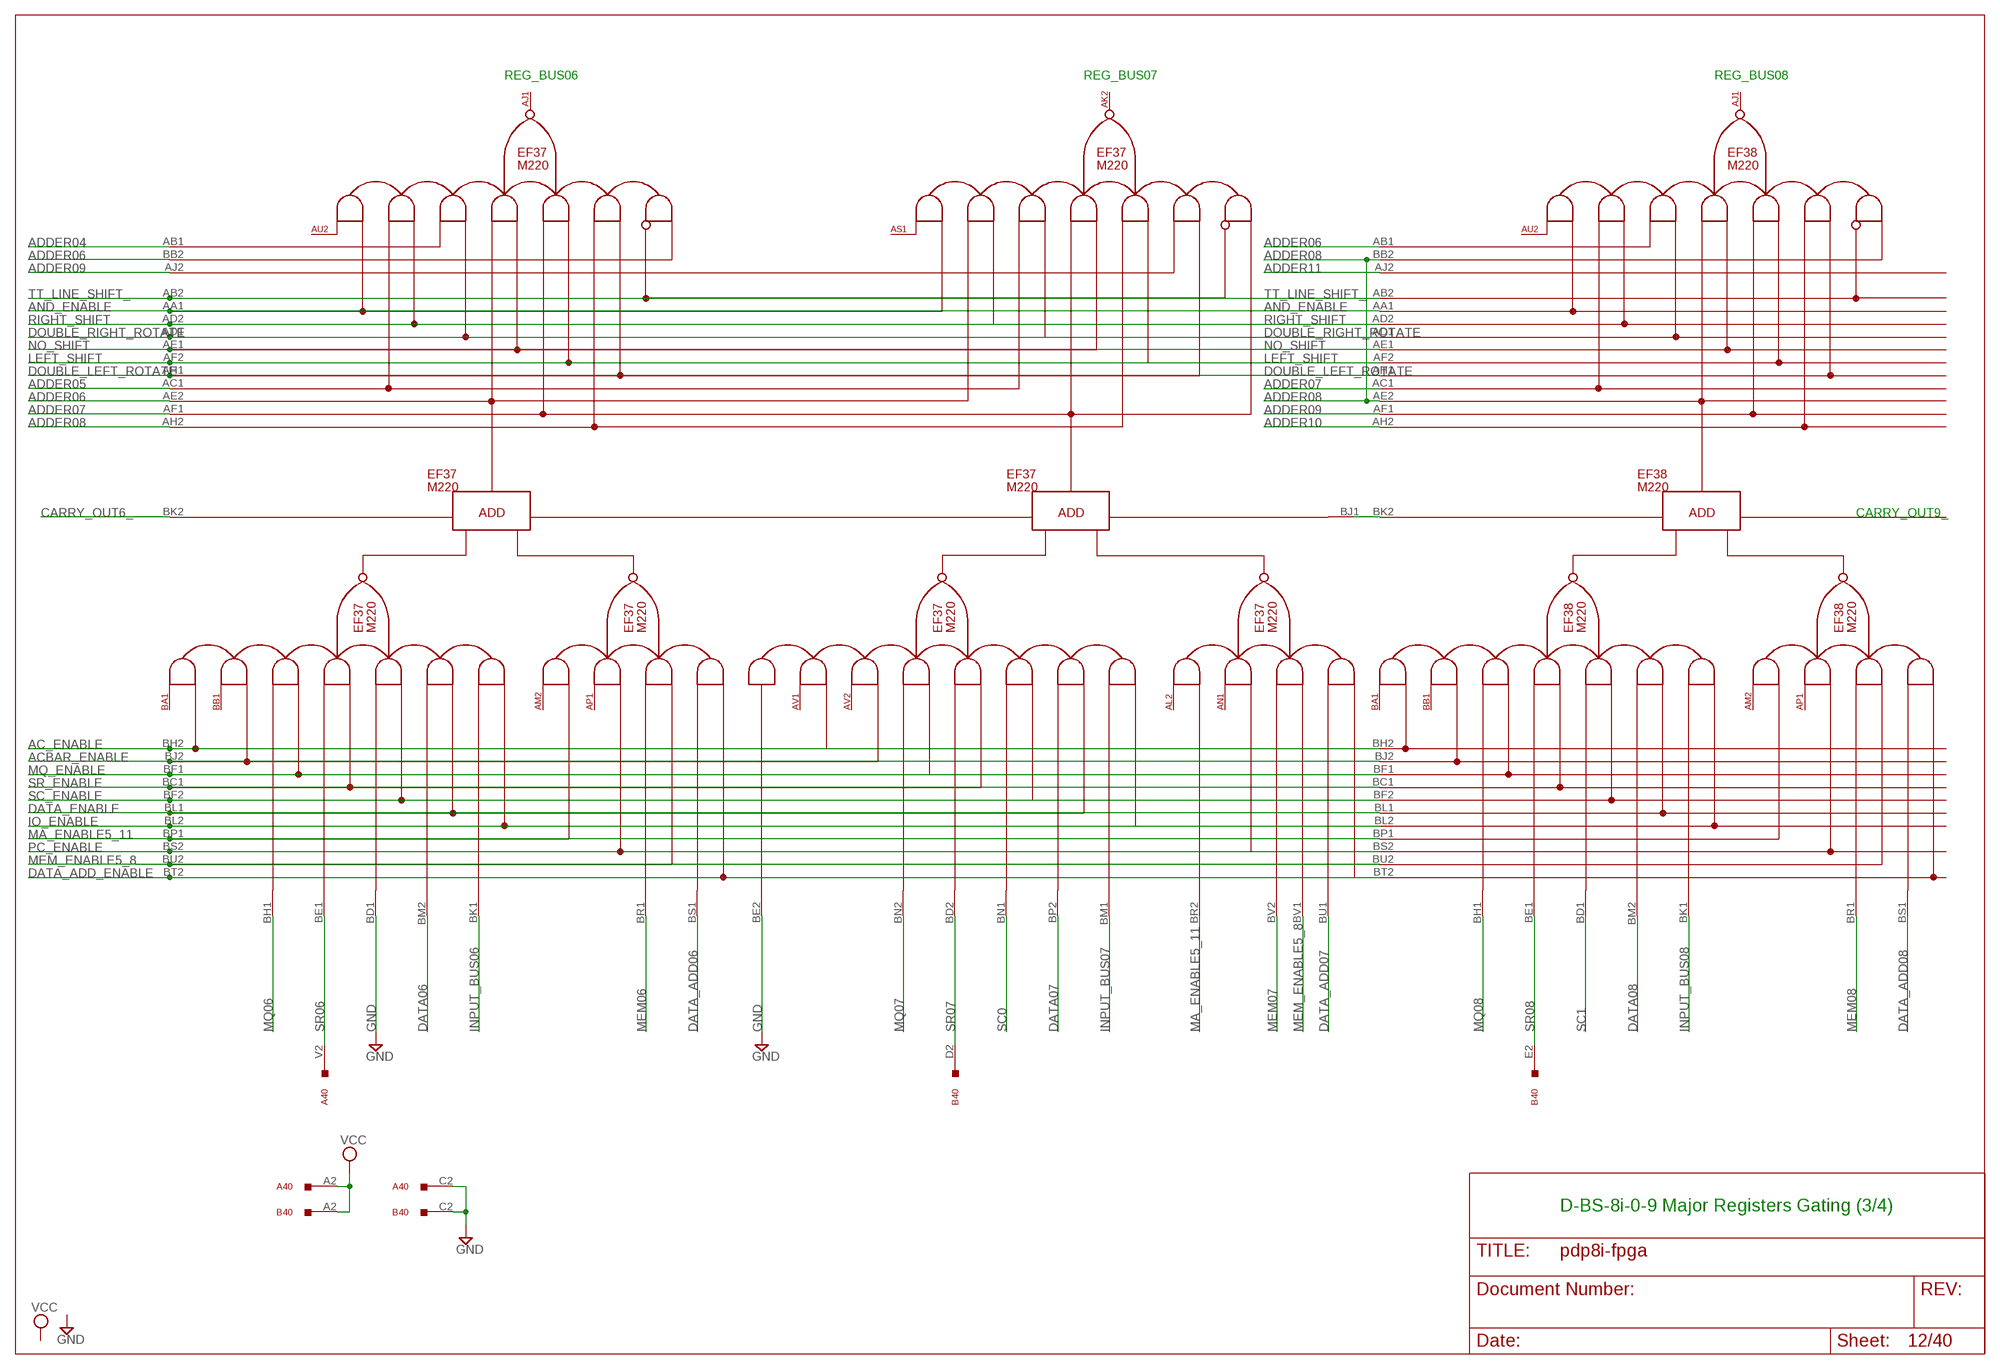
[diagram p11: schematic, sheet 12]
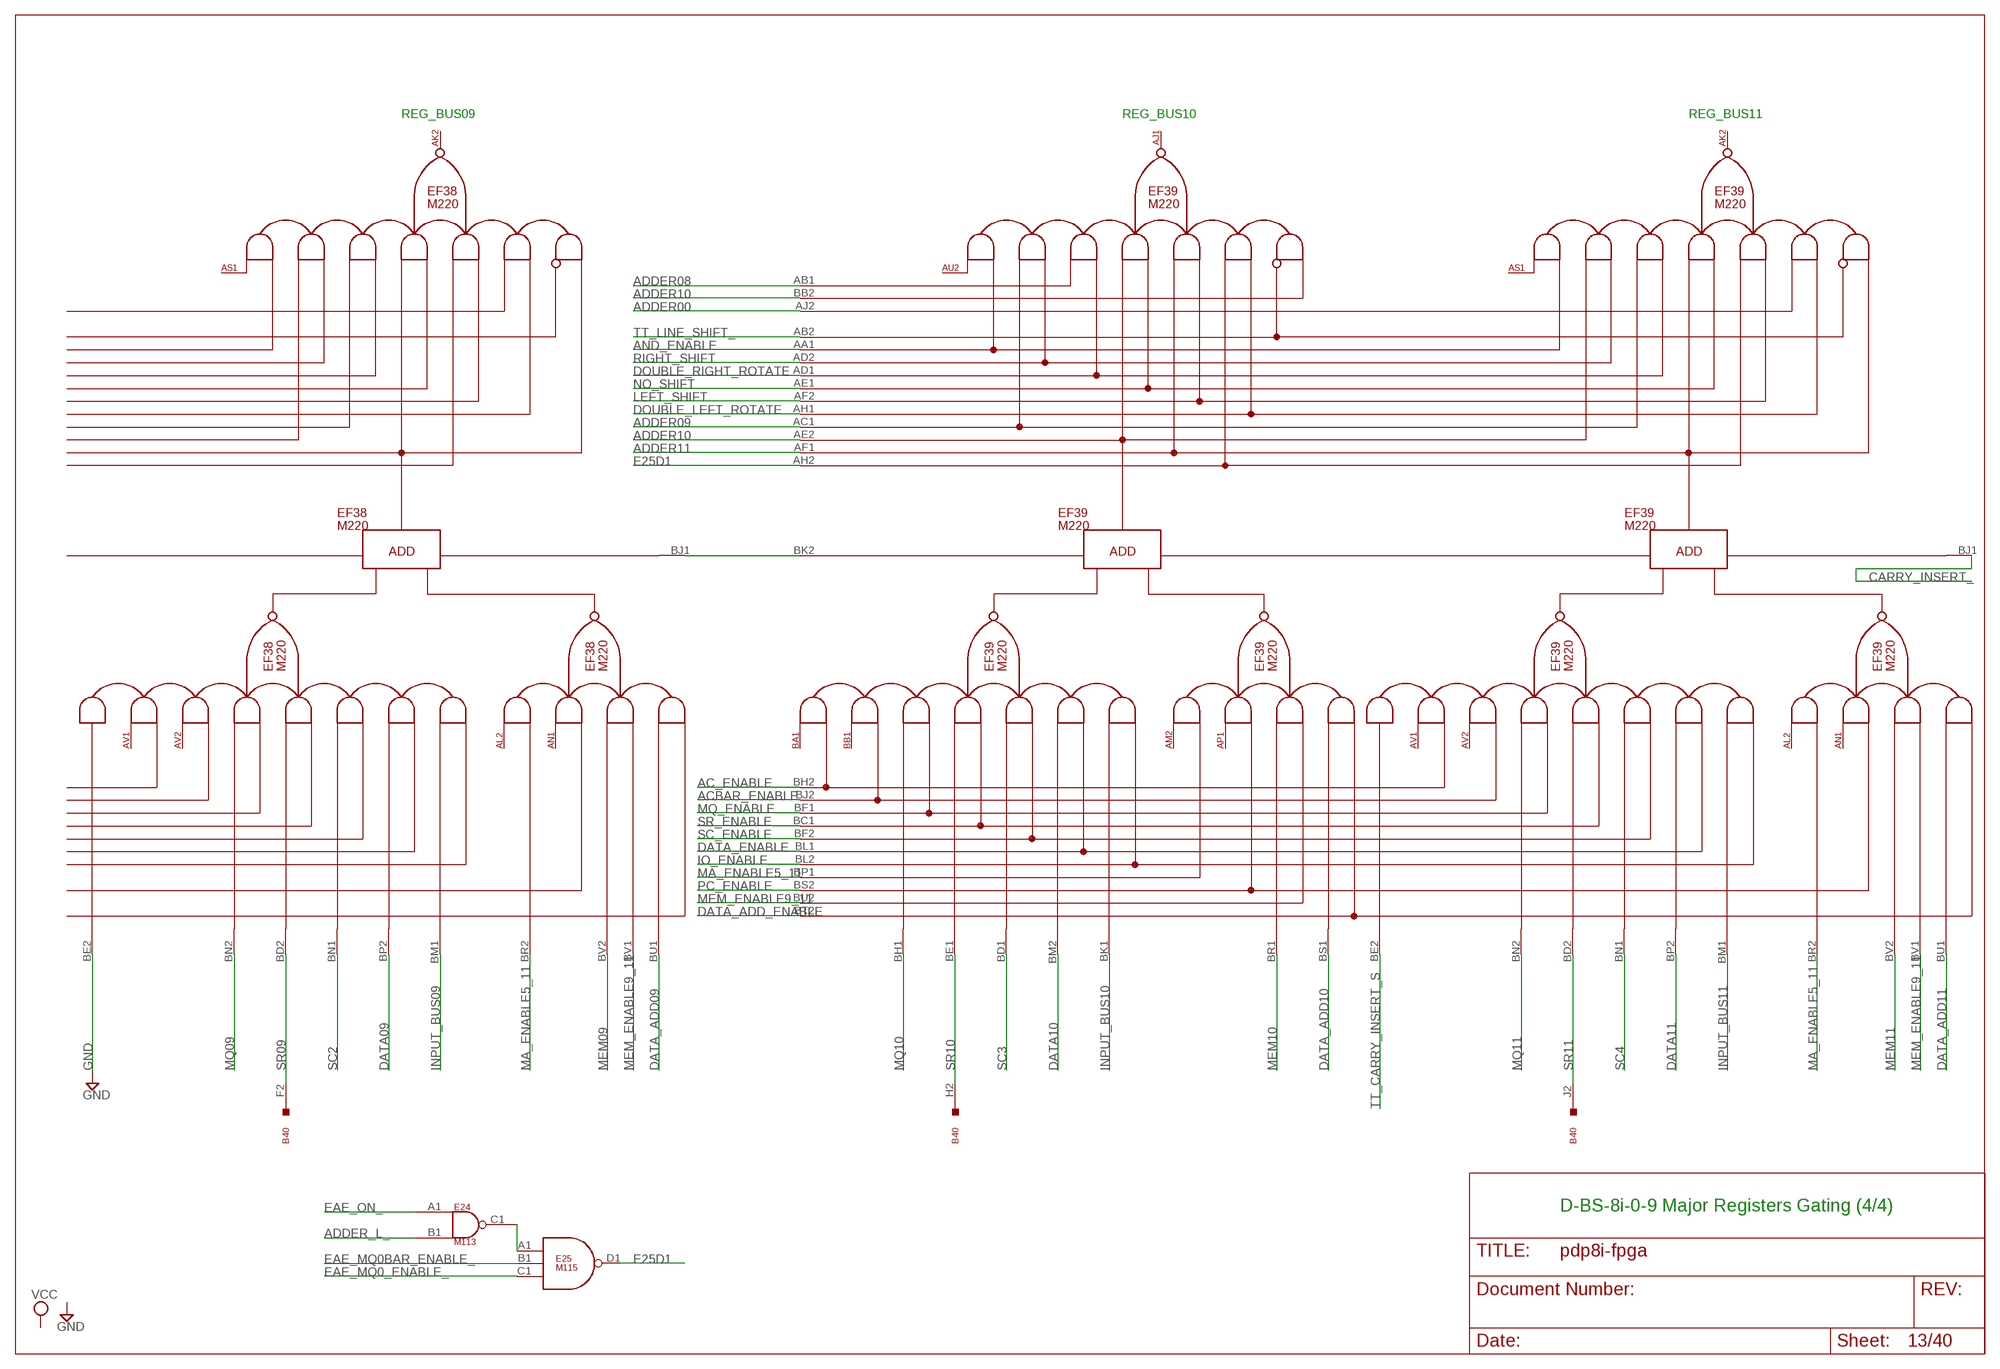
[diagram p12: schematic, sheet 13]
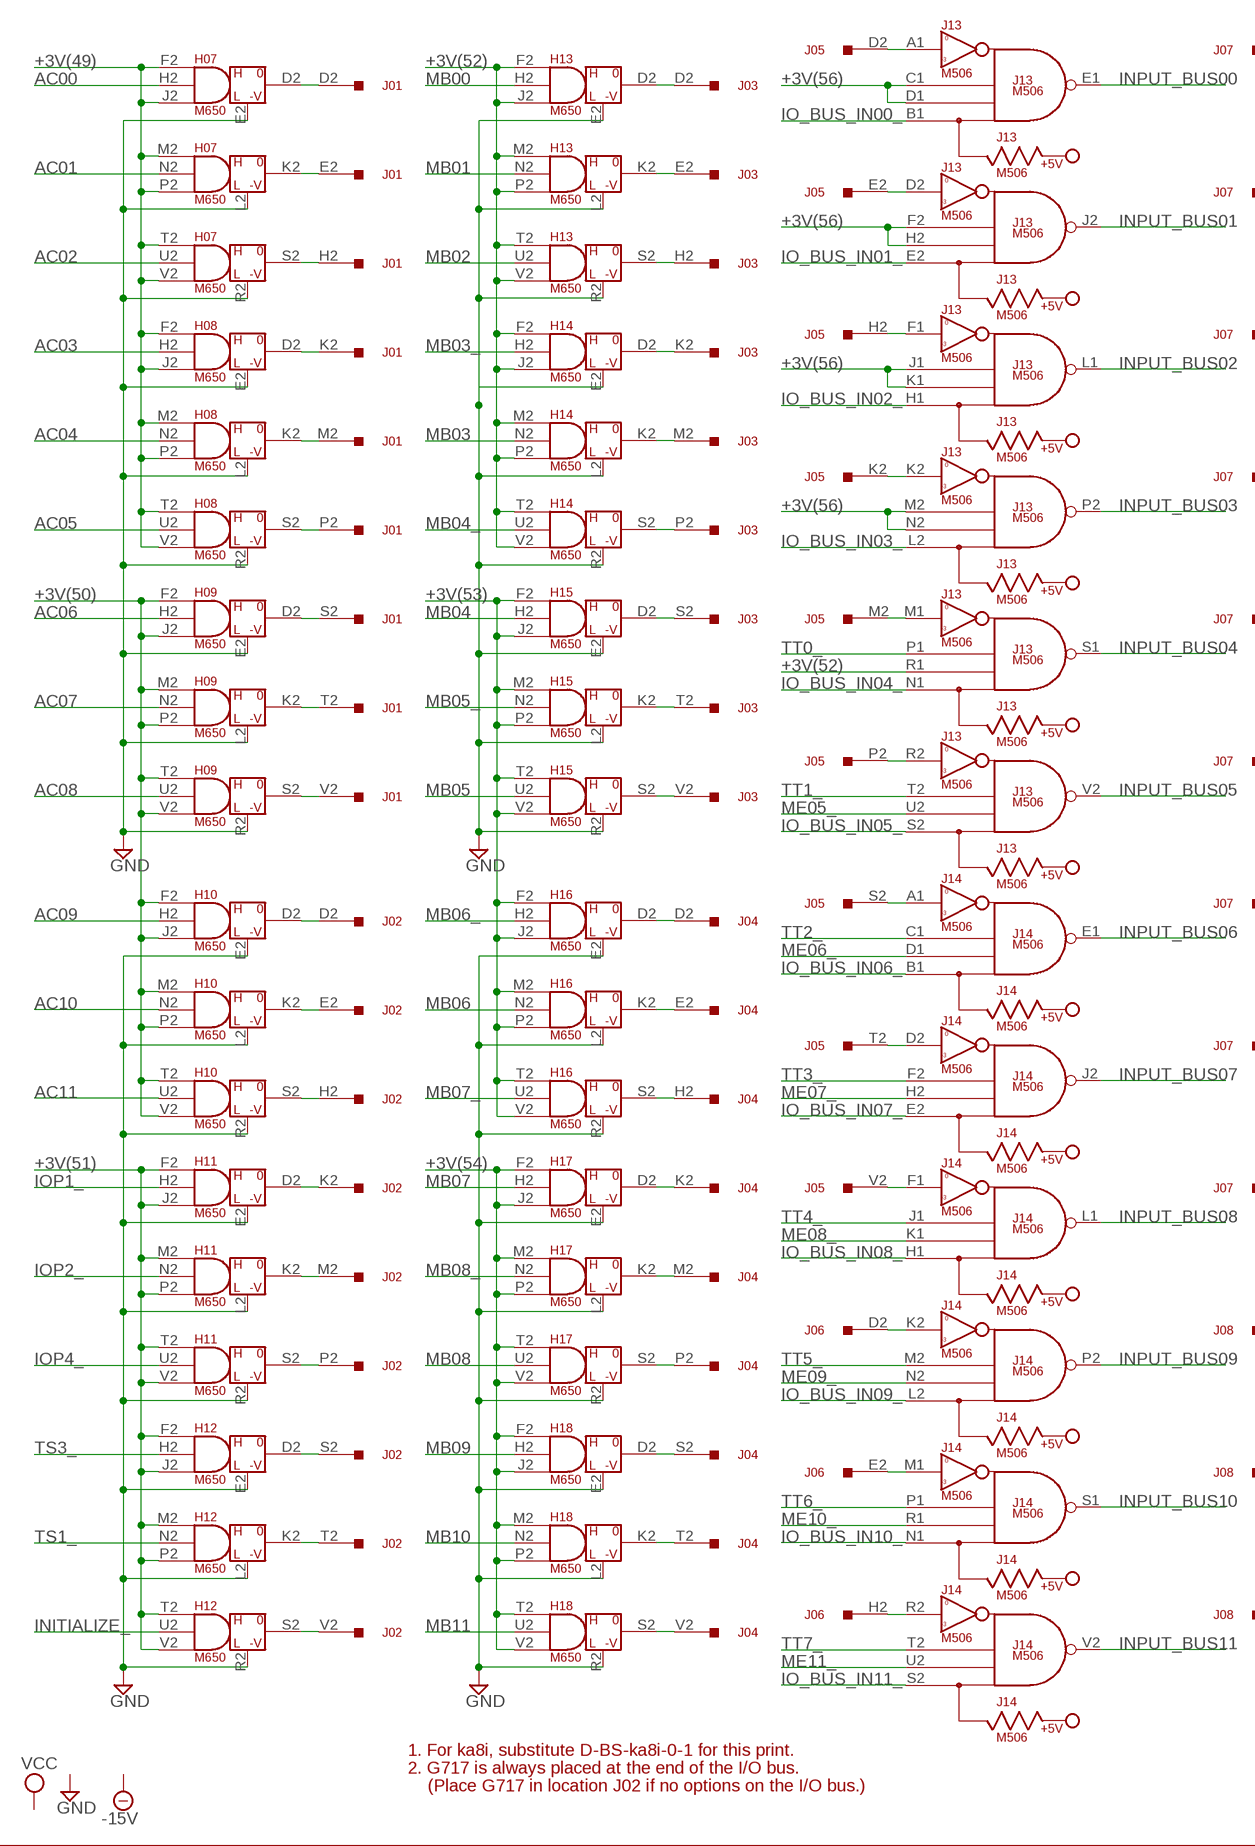
[diagram p13: schematic, sheet 14, part 1 of 2]
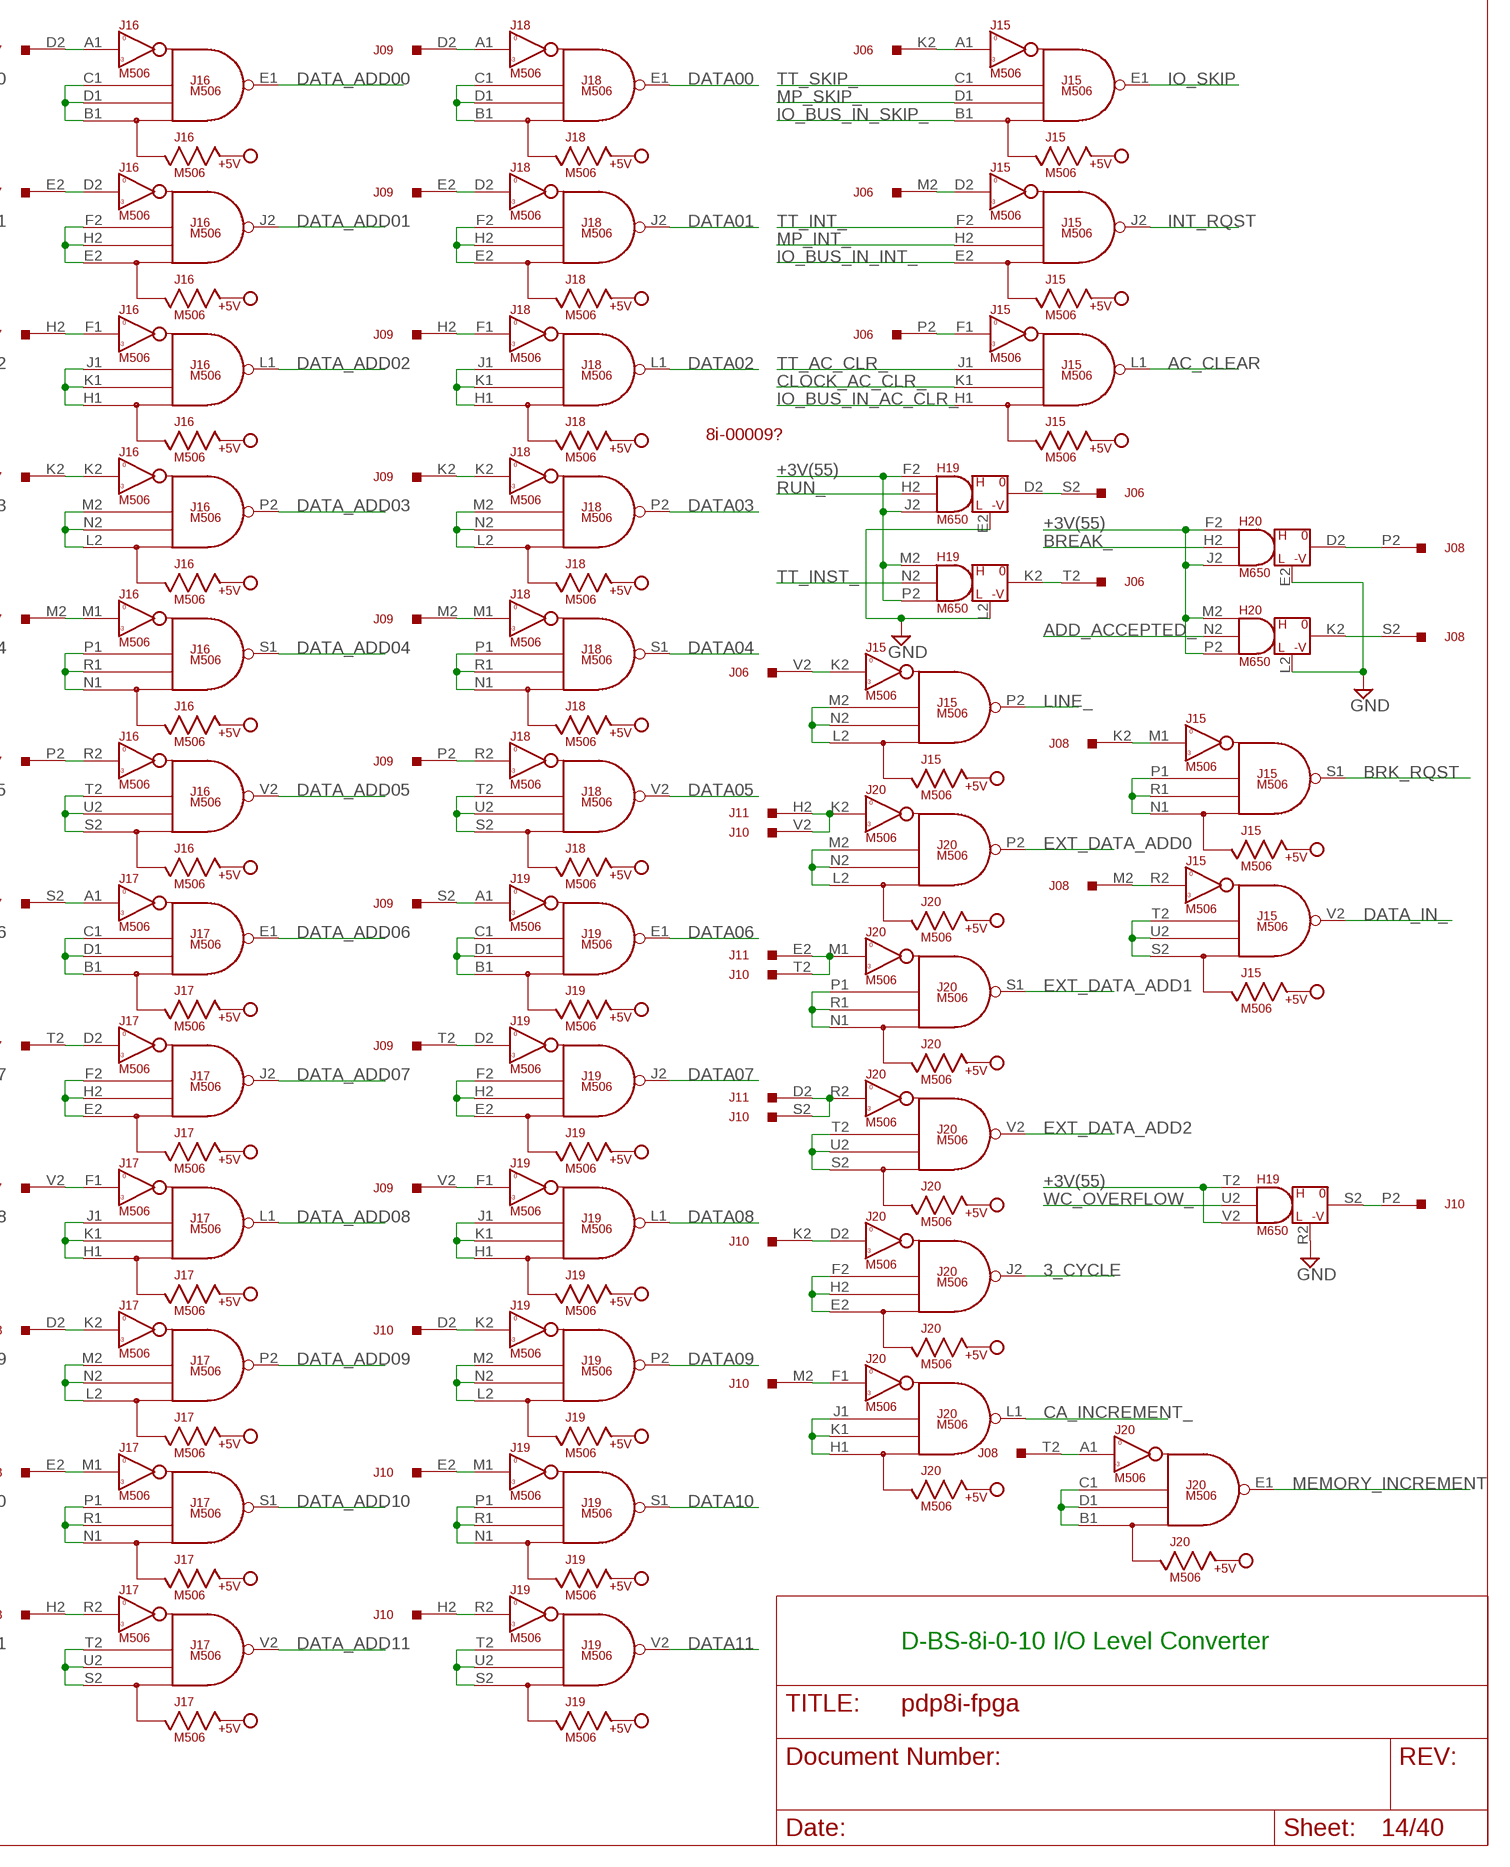
[diagram p14: schematic, sheet 14, part 2 of 2]
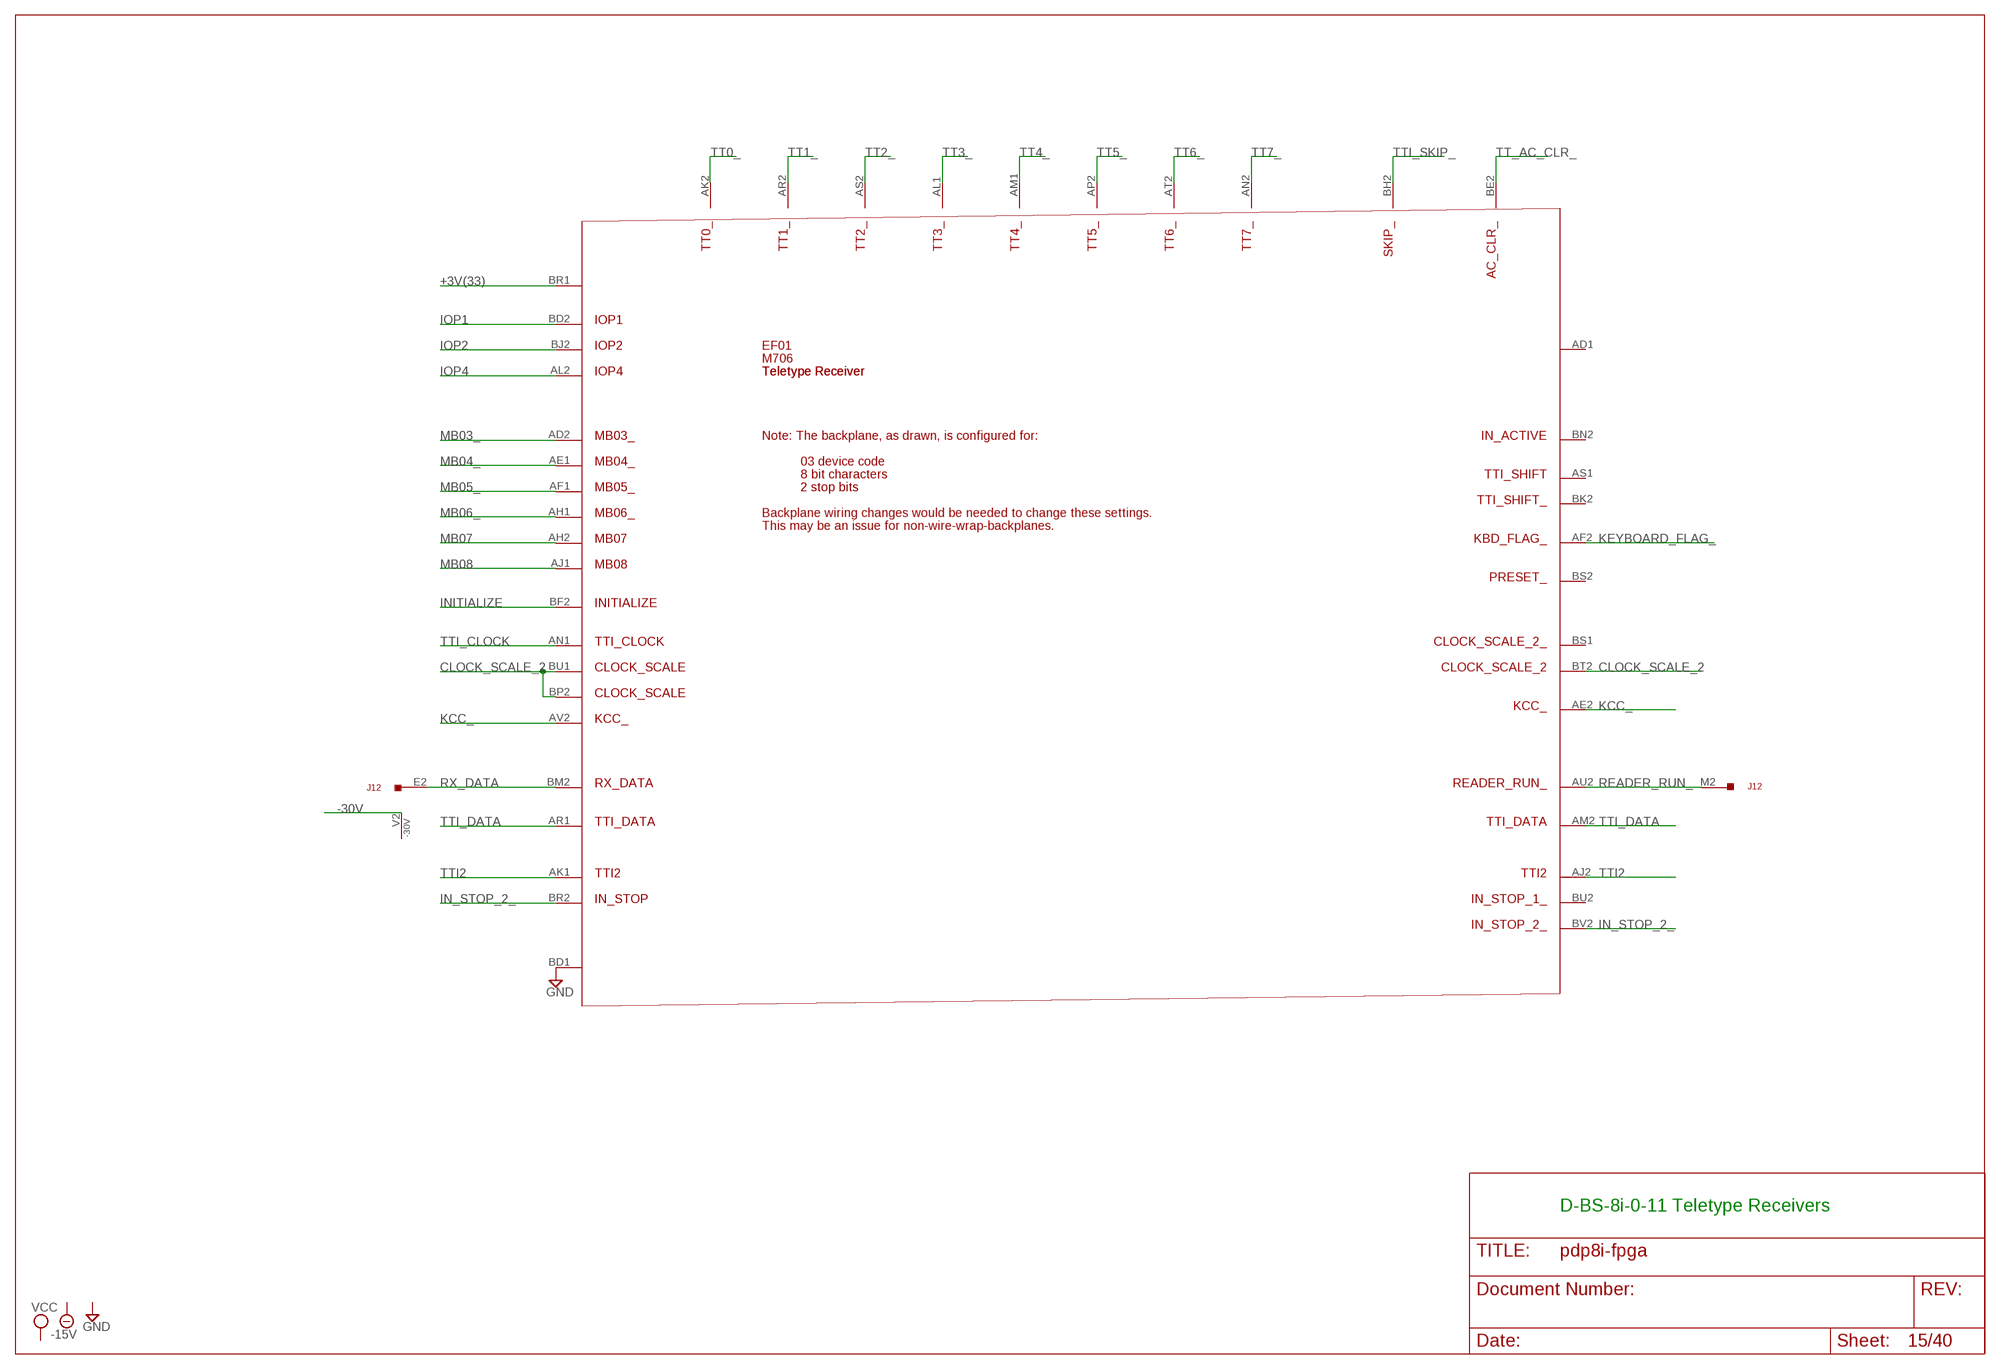
[diagram p15: schematic, sheet 15]
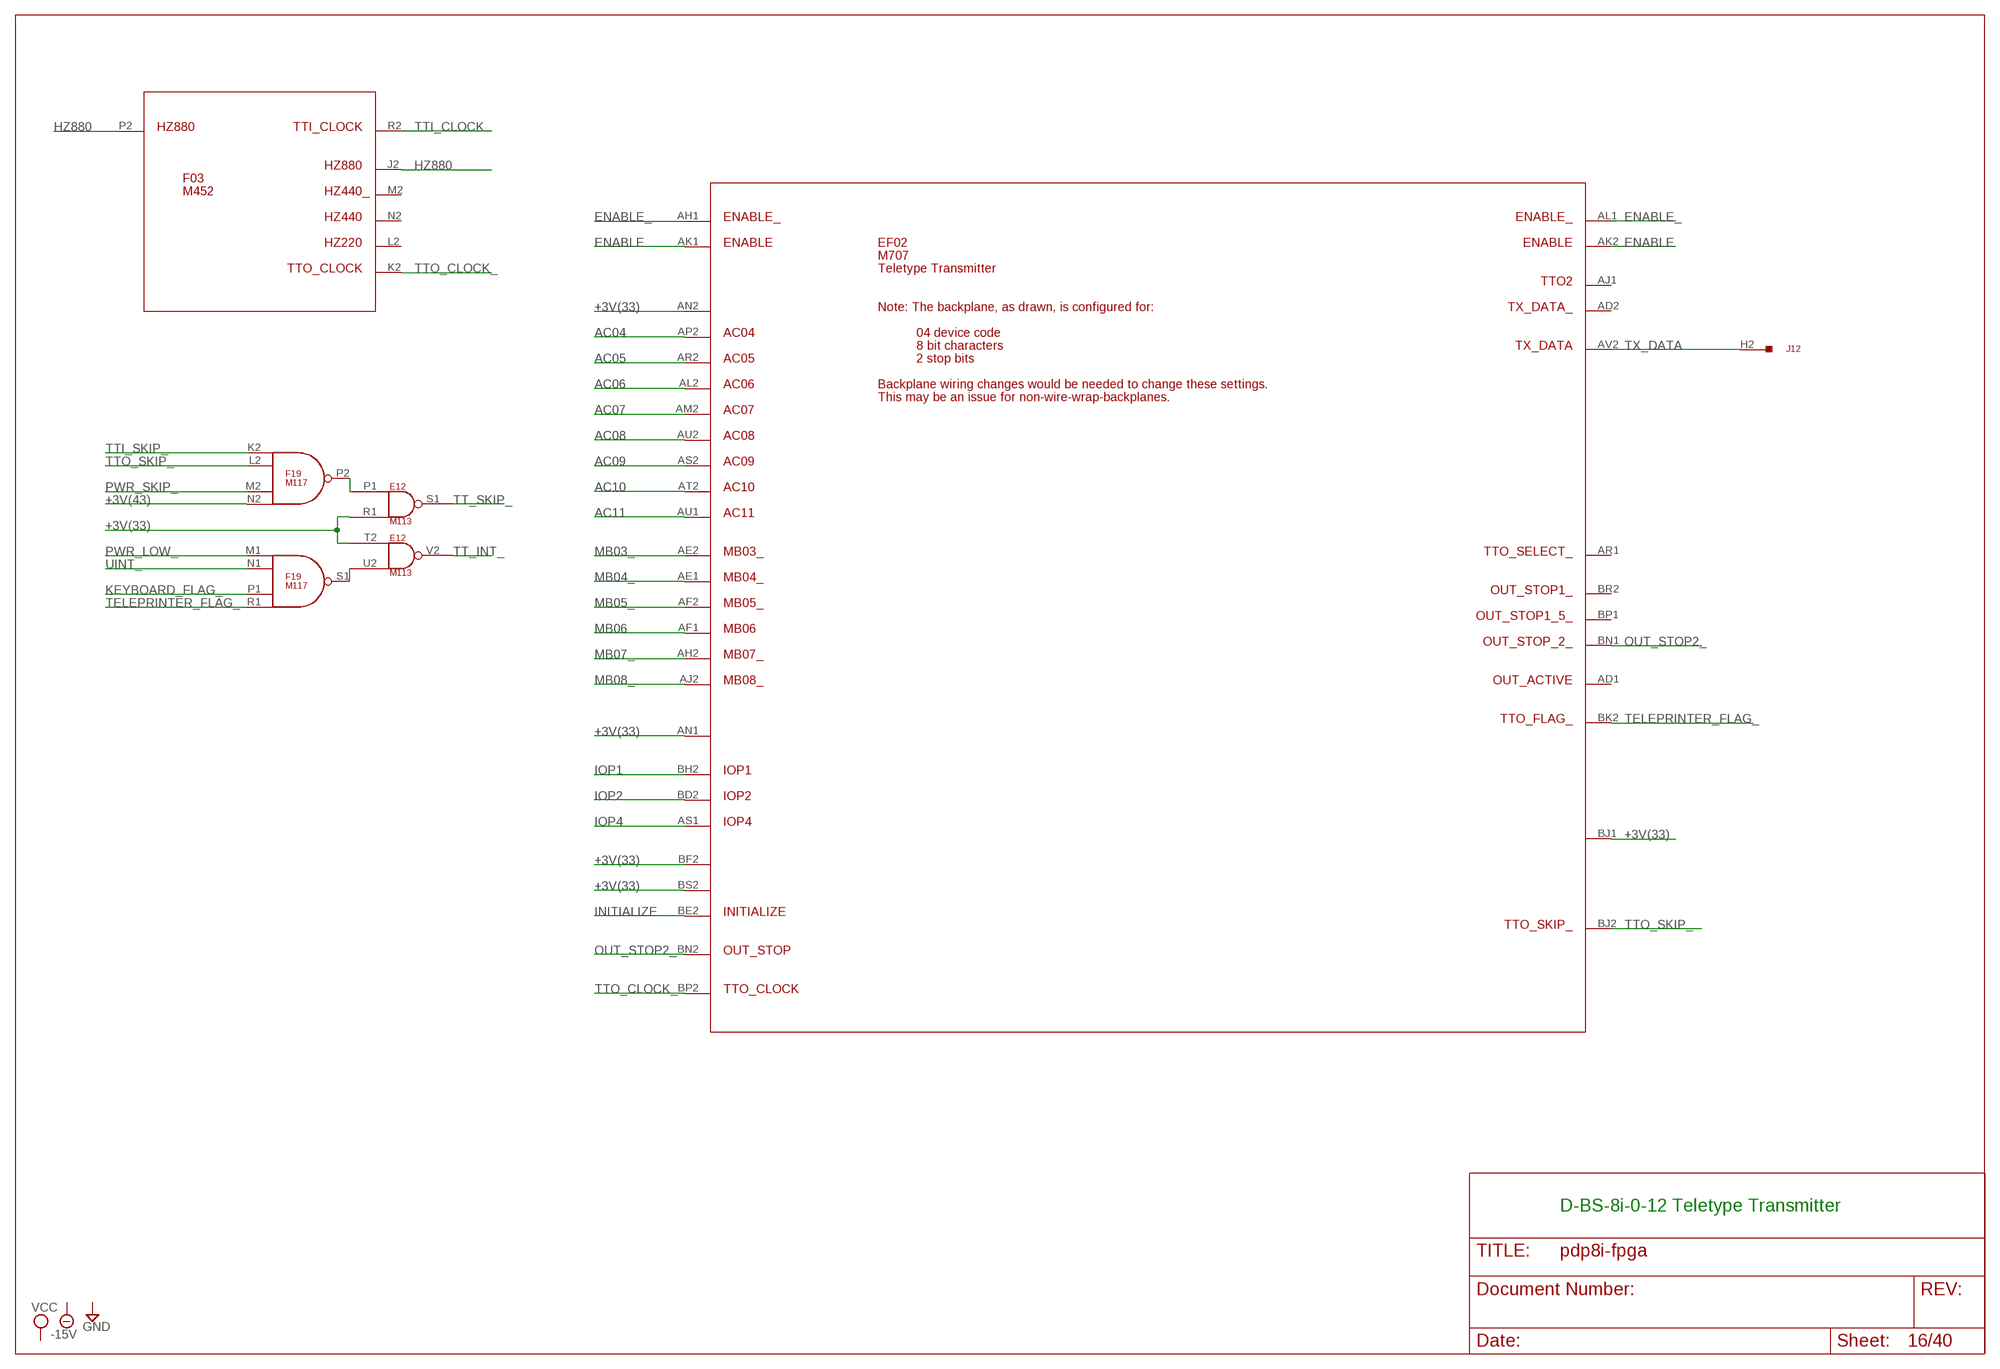
[diagram p16: schematic, sheet 16]
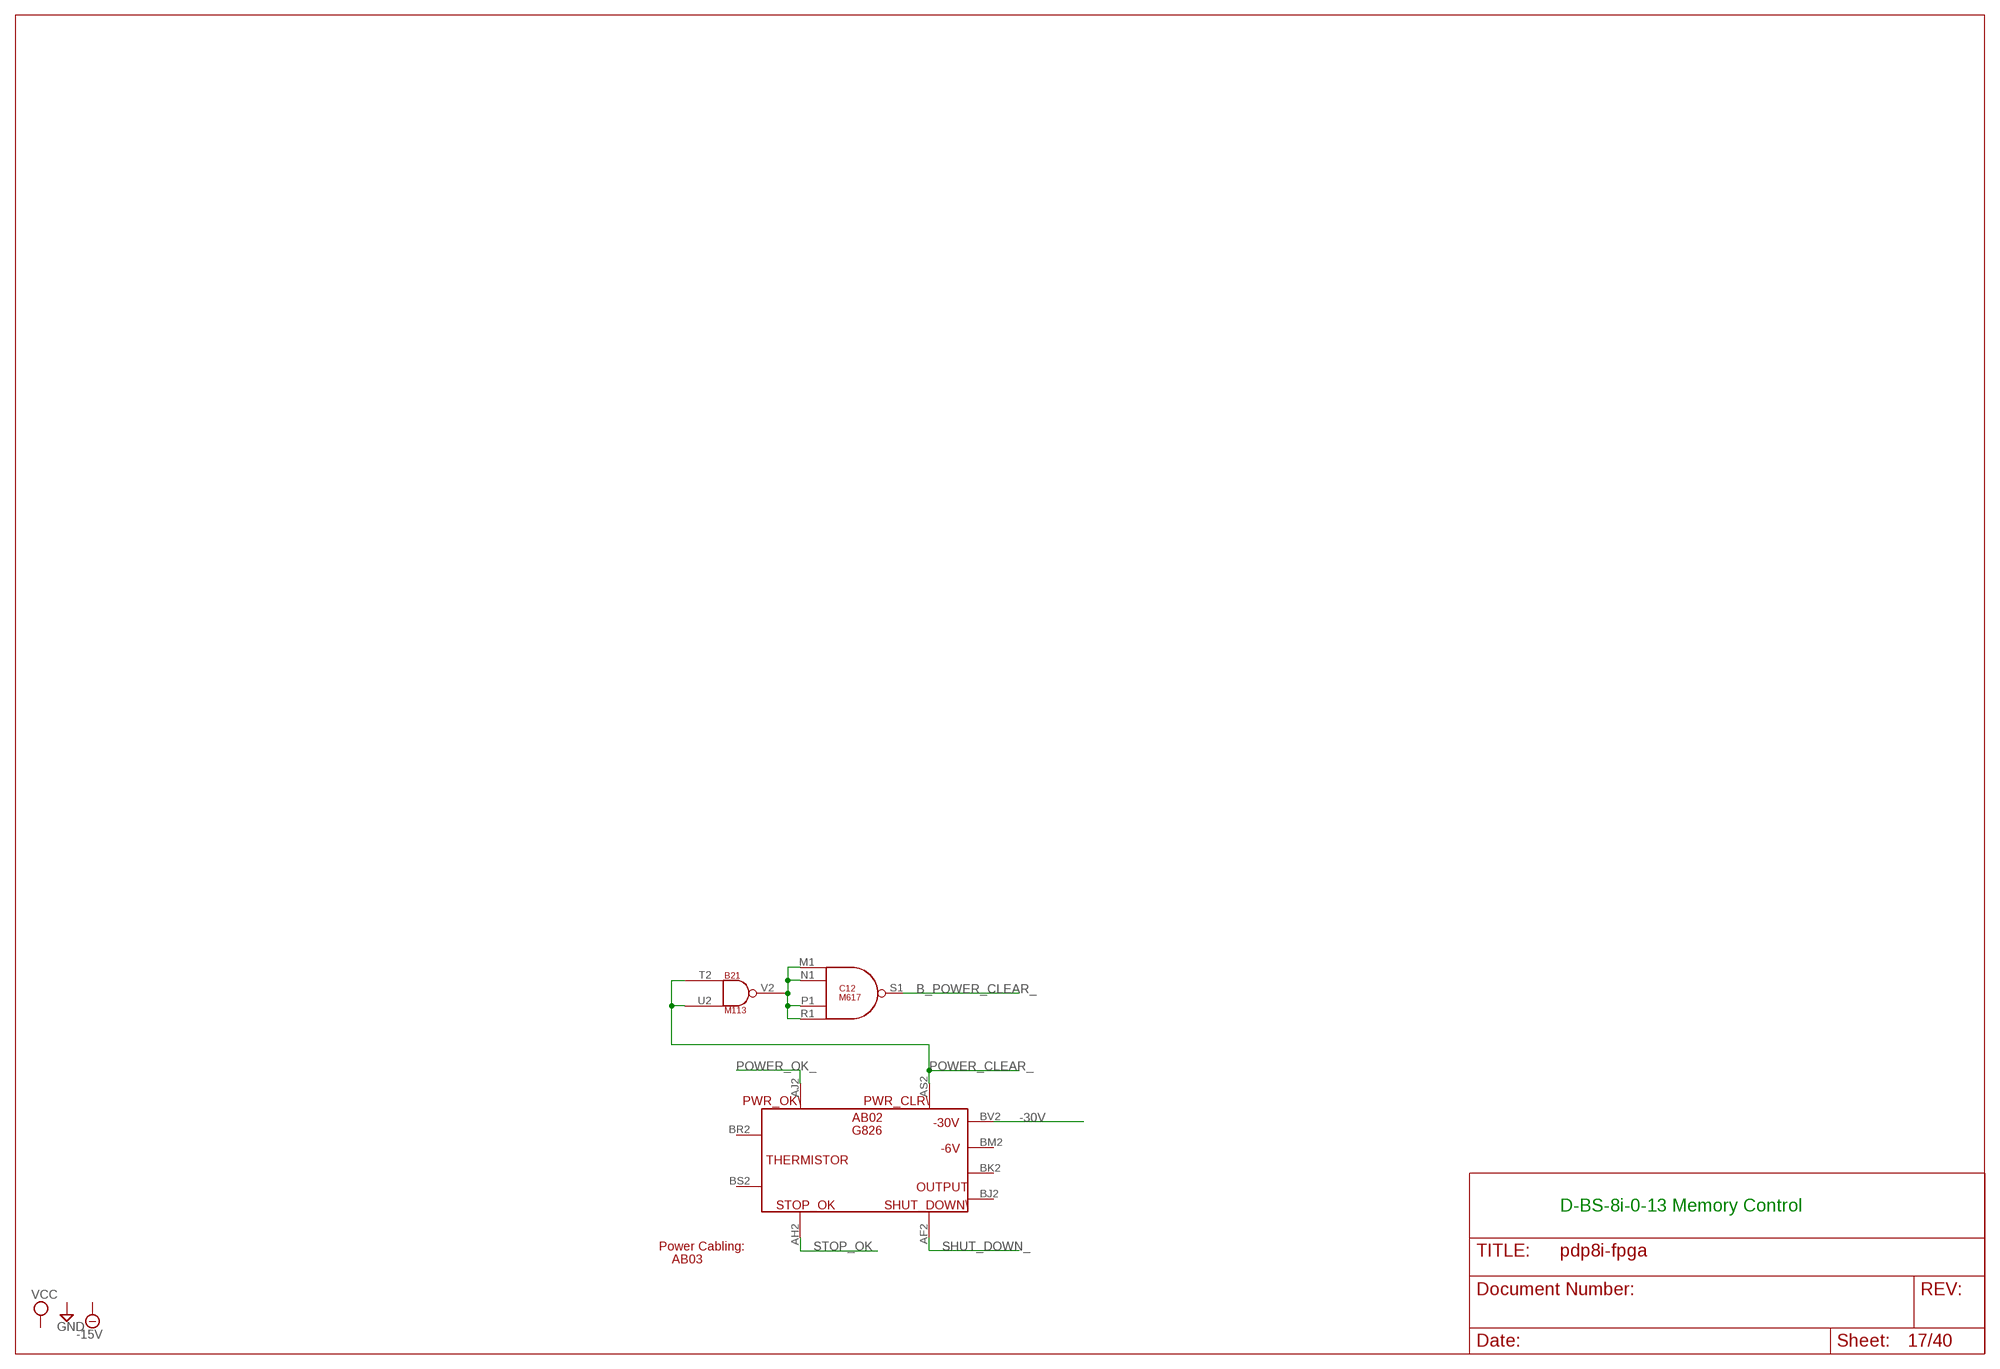
[diagram p17: schematic, sheet 17]
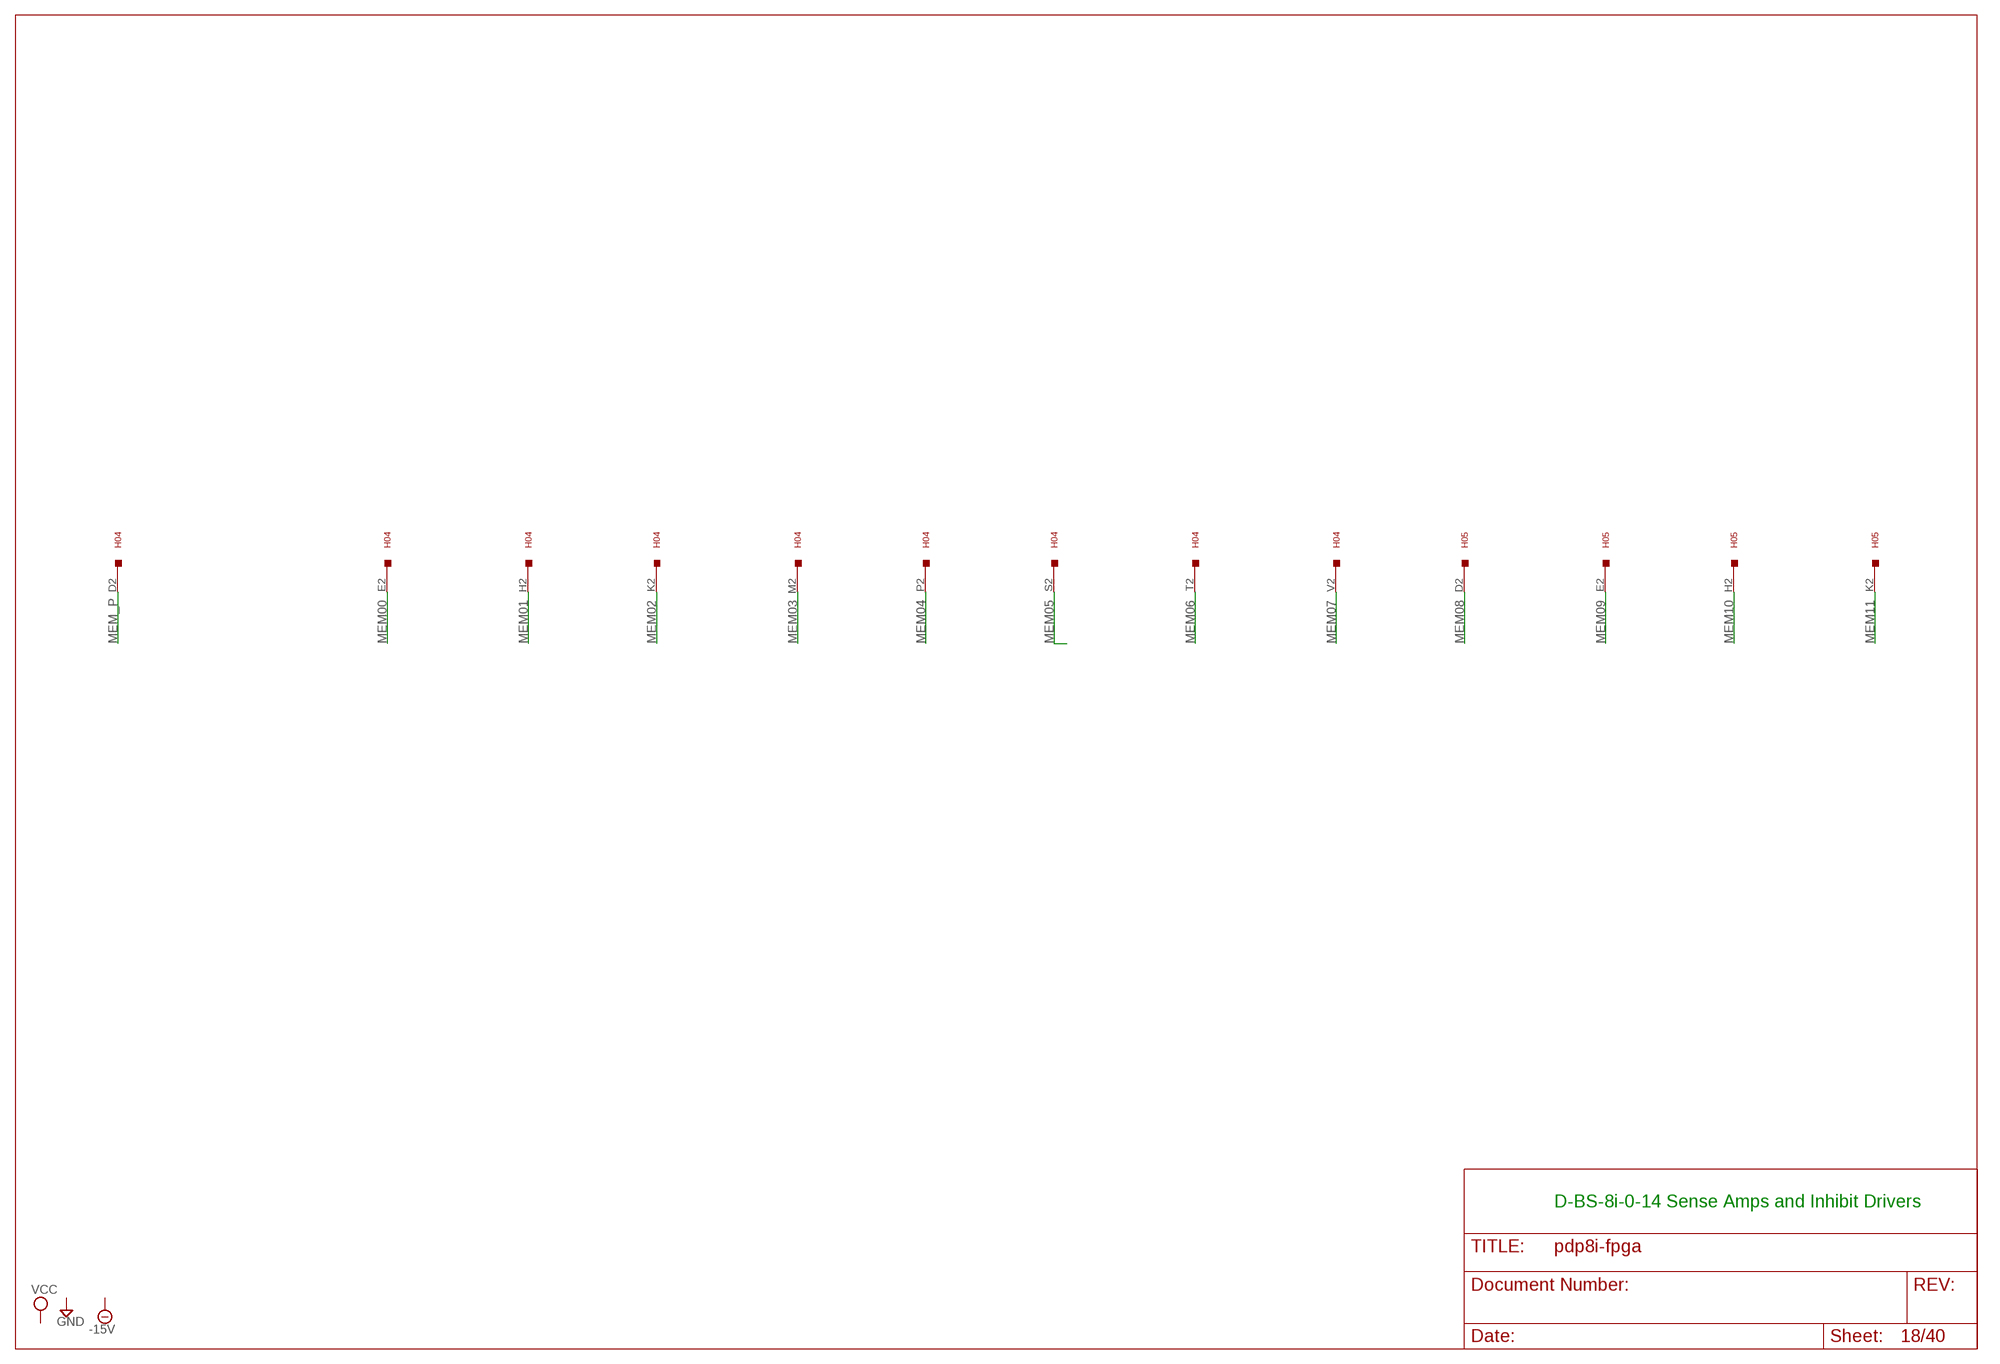
[diagram p18: schematic, sheet 18]
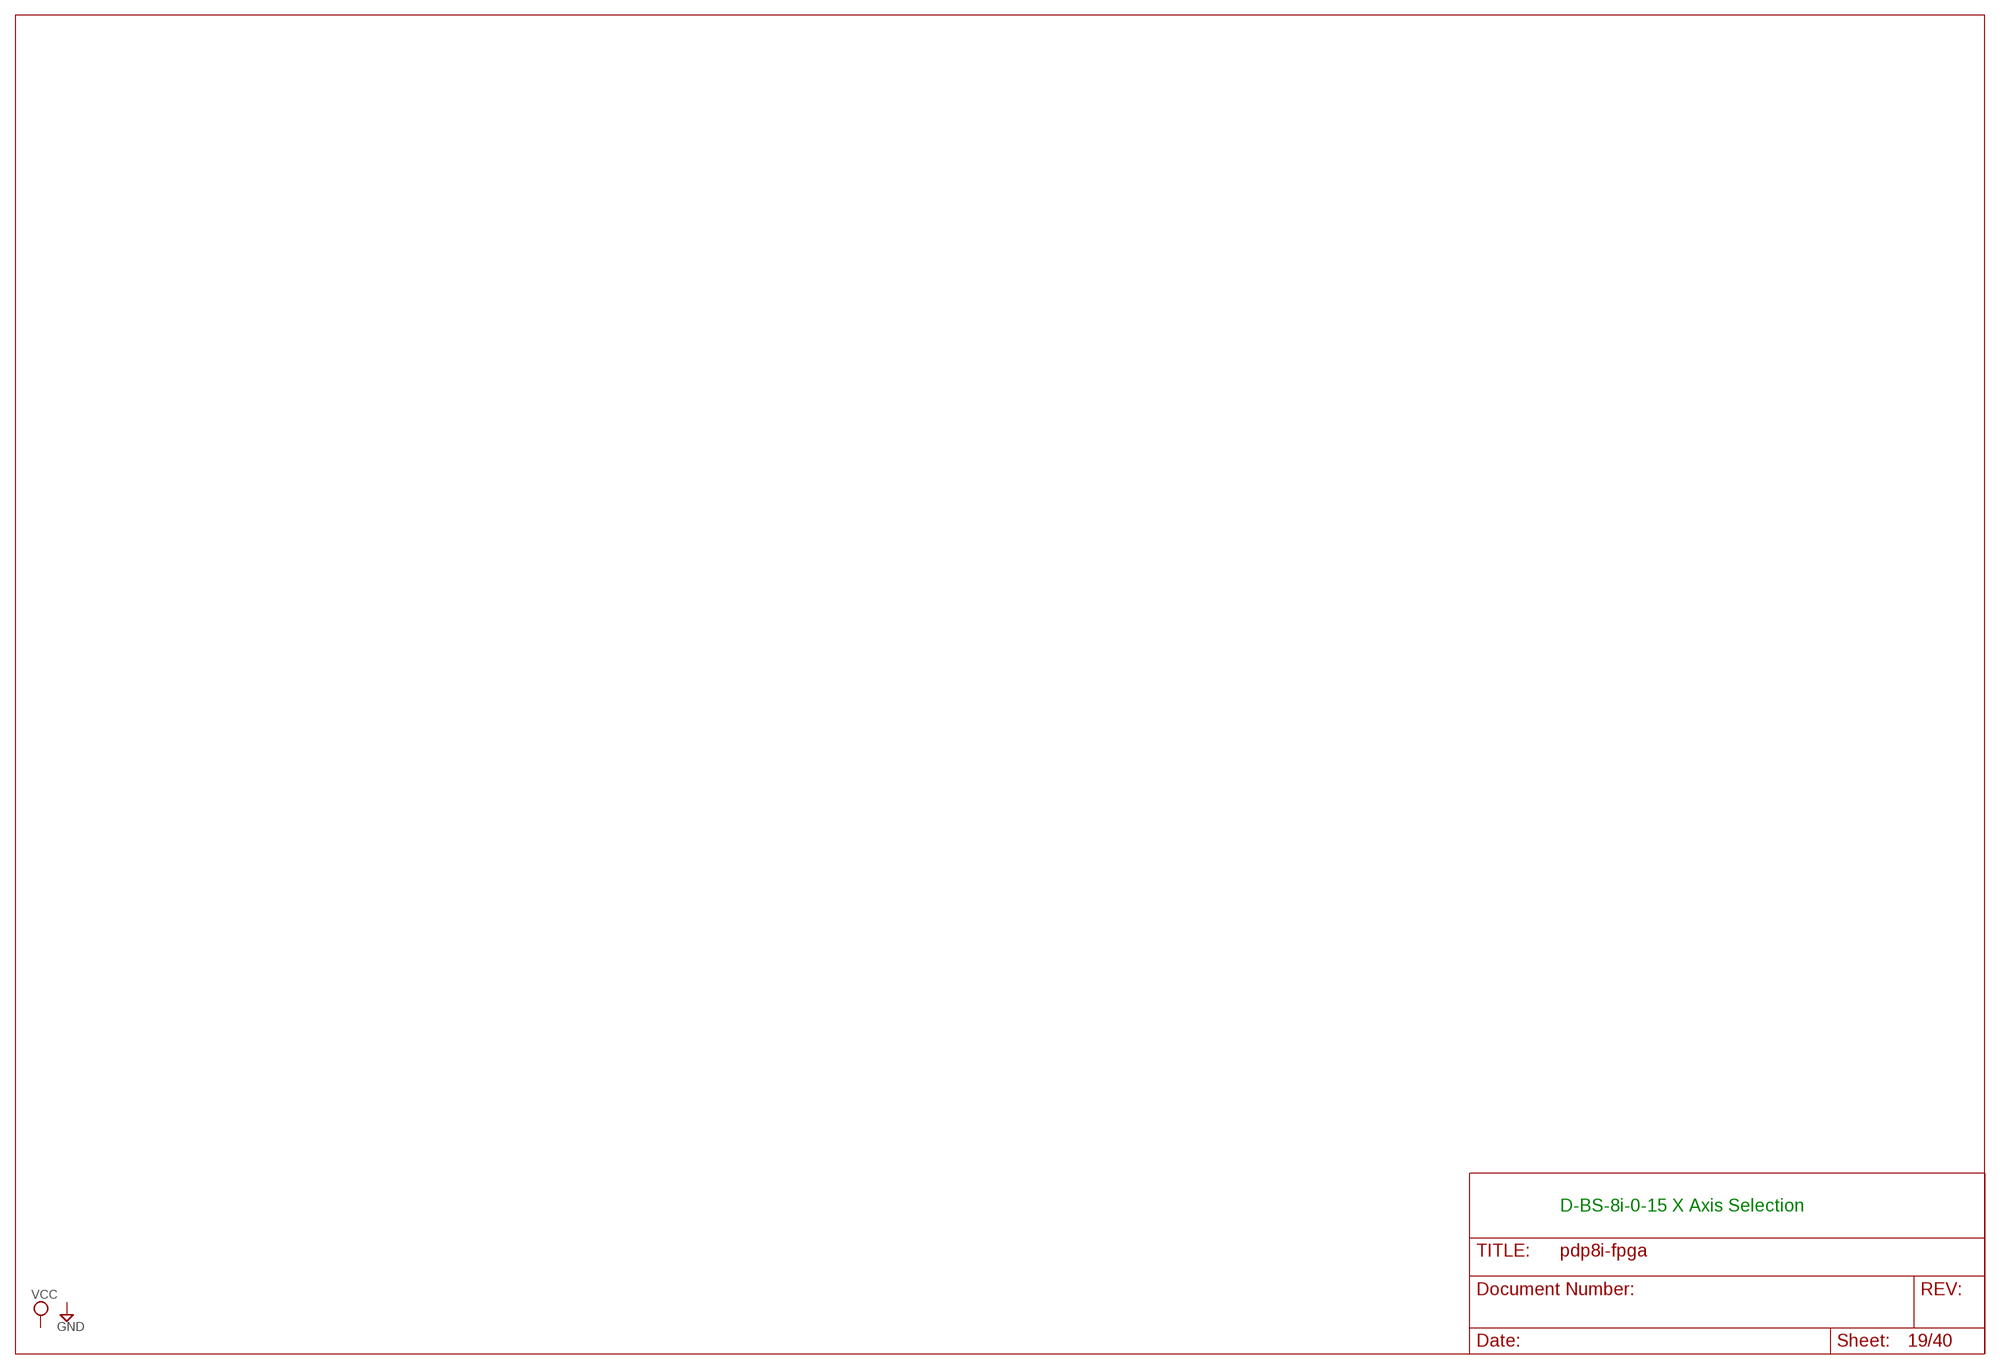
[diagram p19: schematic, sheet 19]
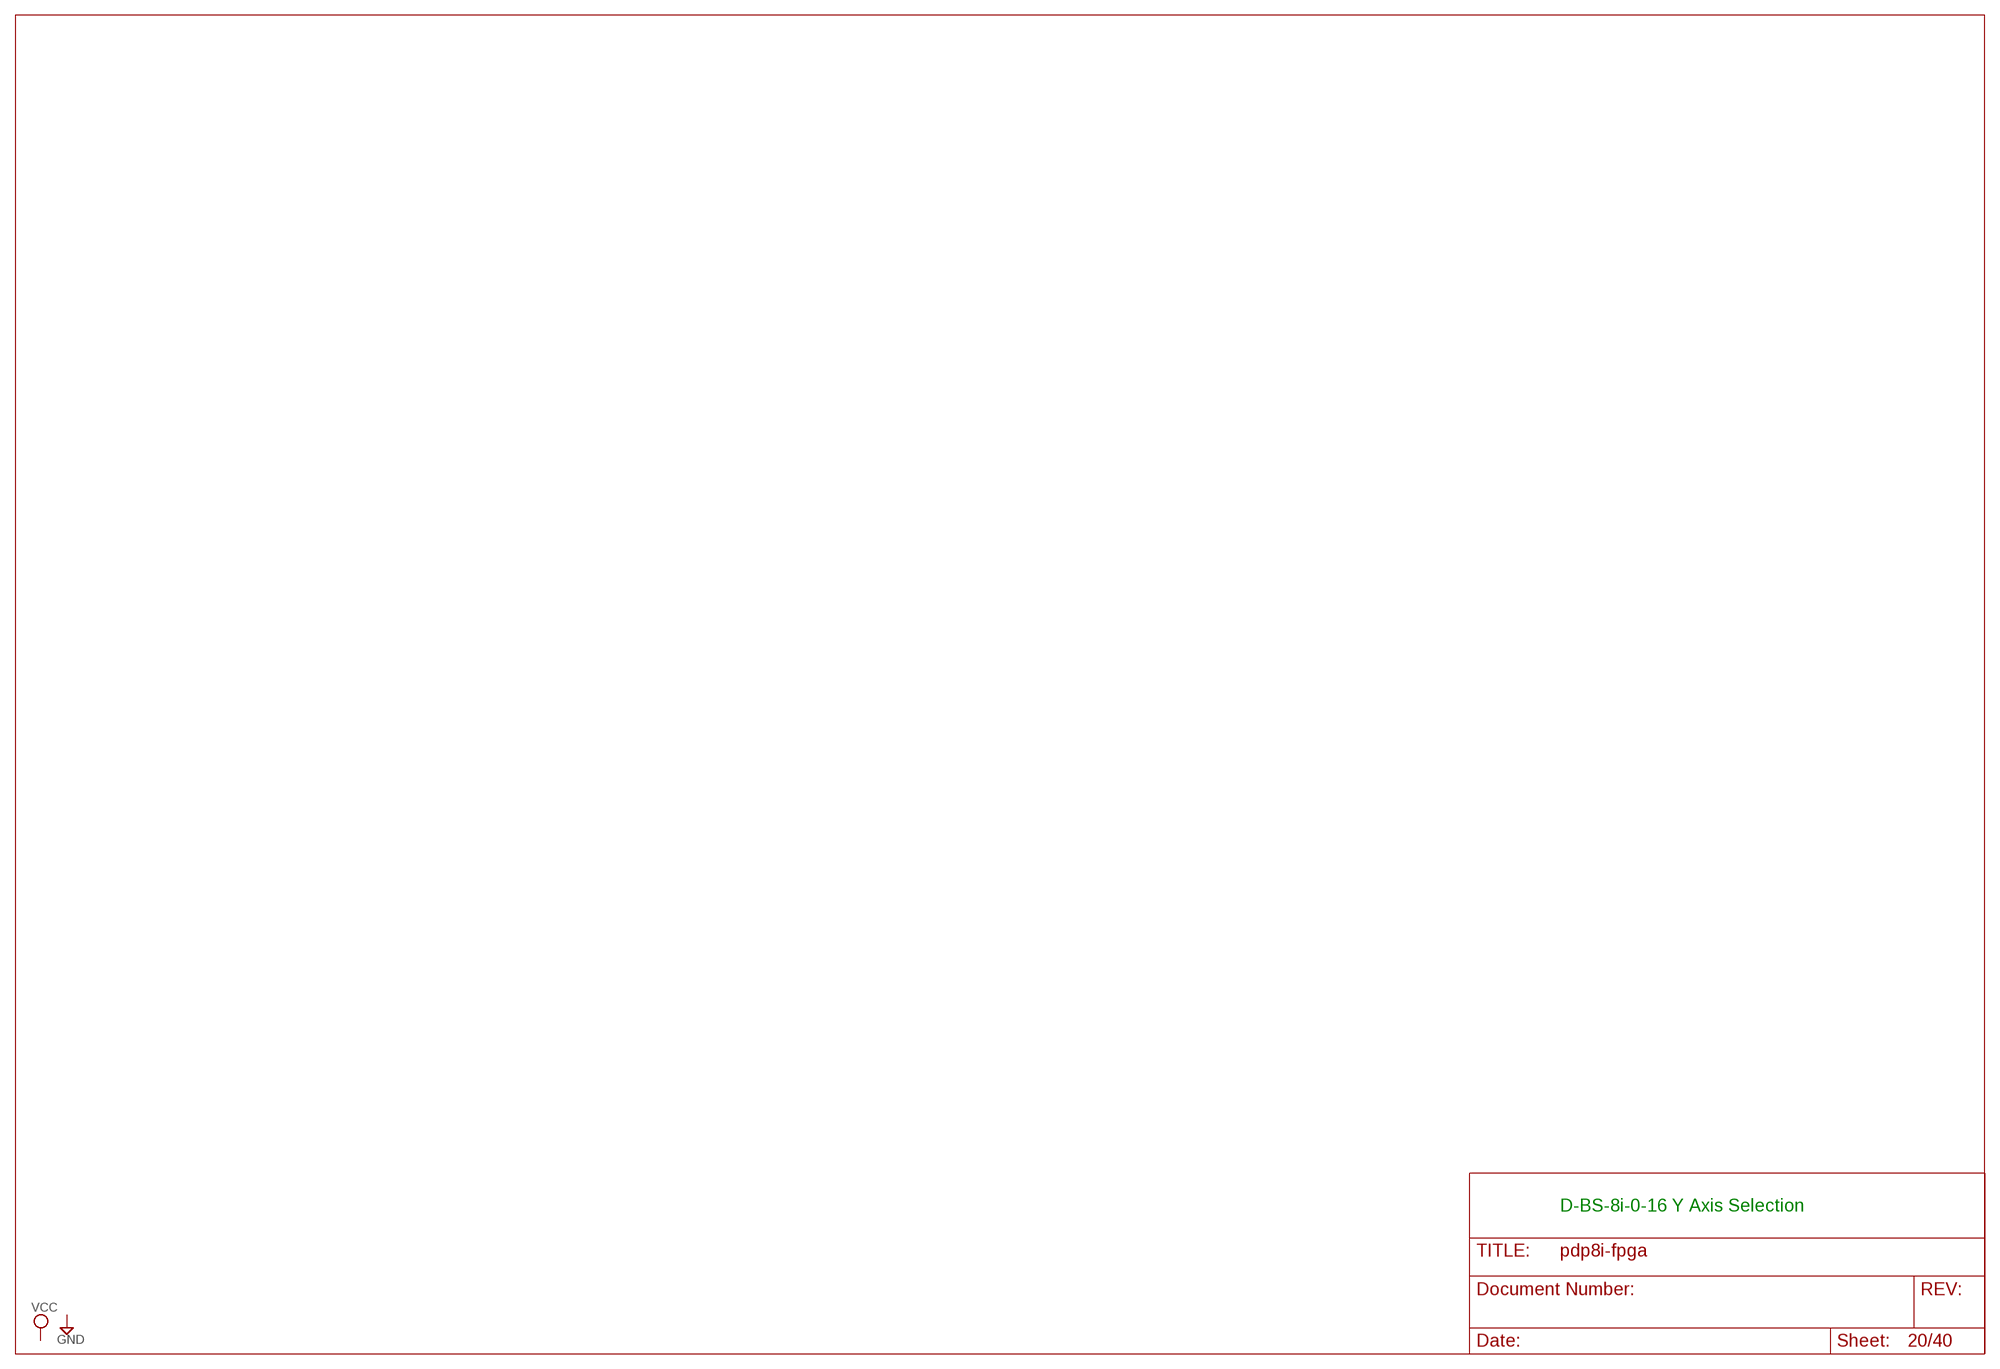
[diagram p20: schematic, sheet 20]
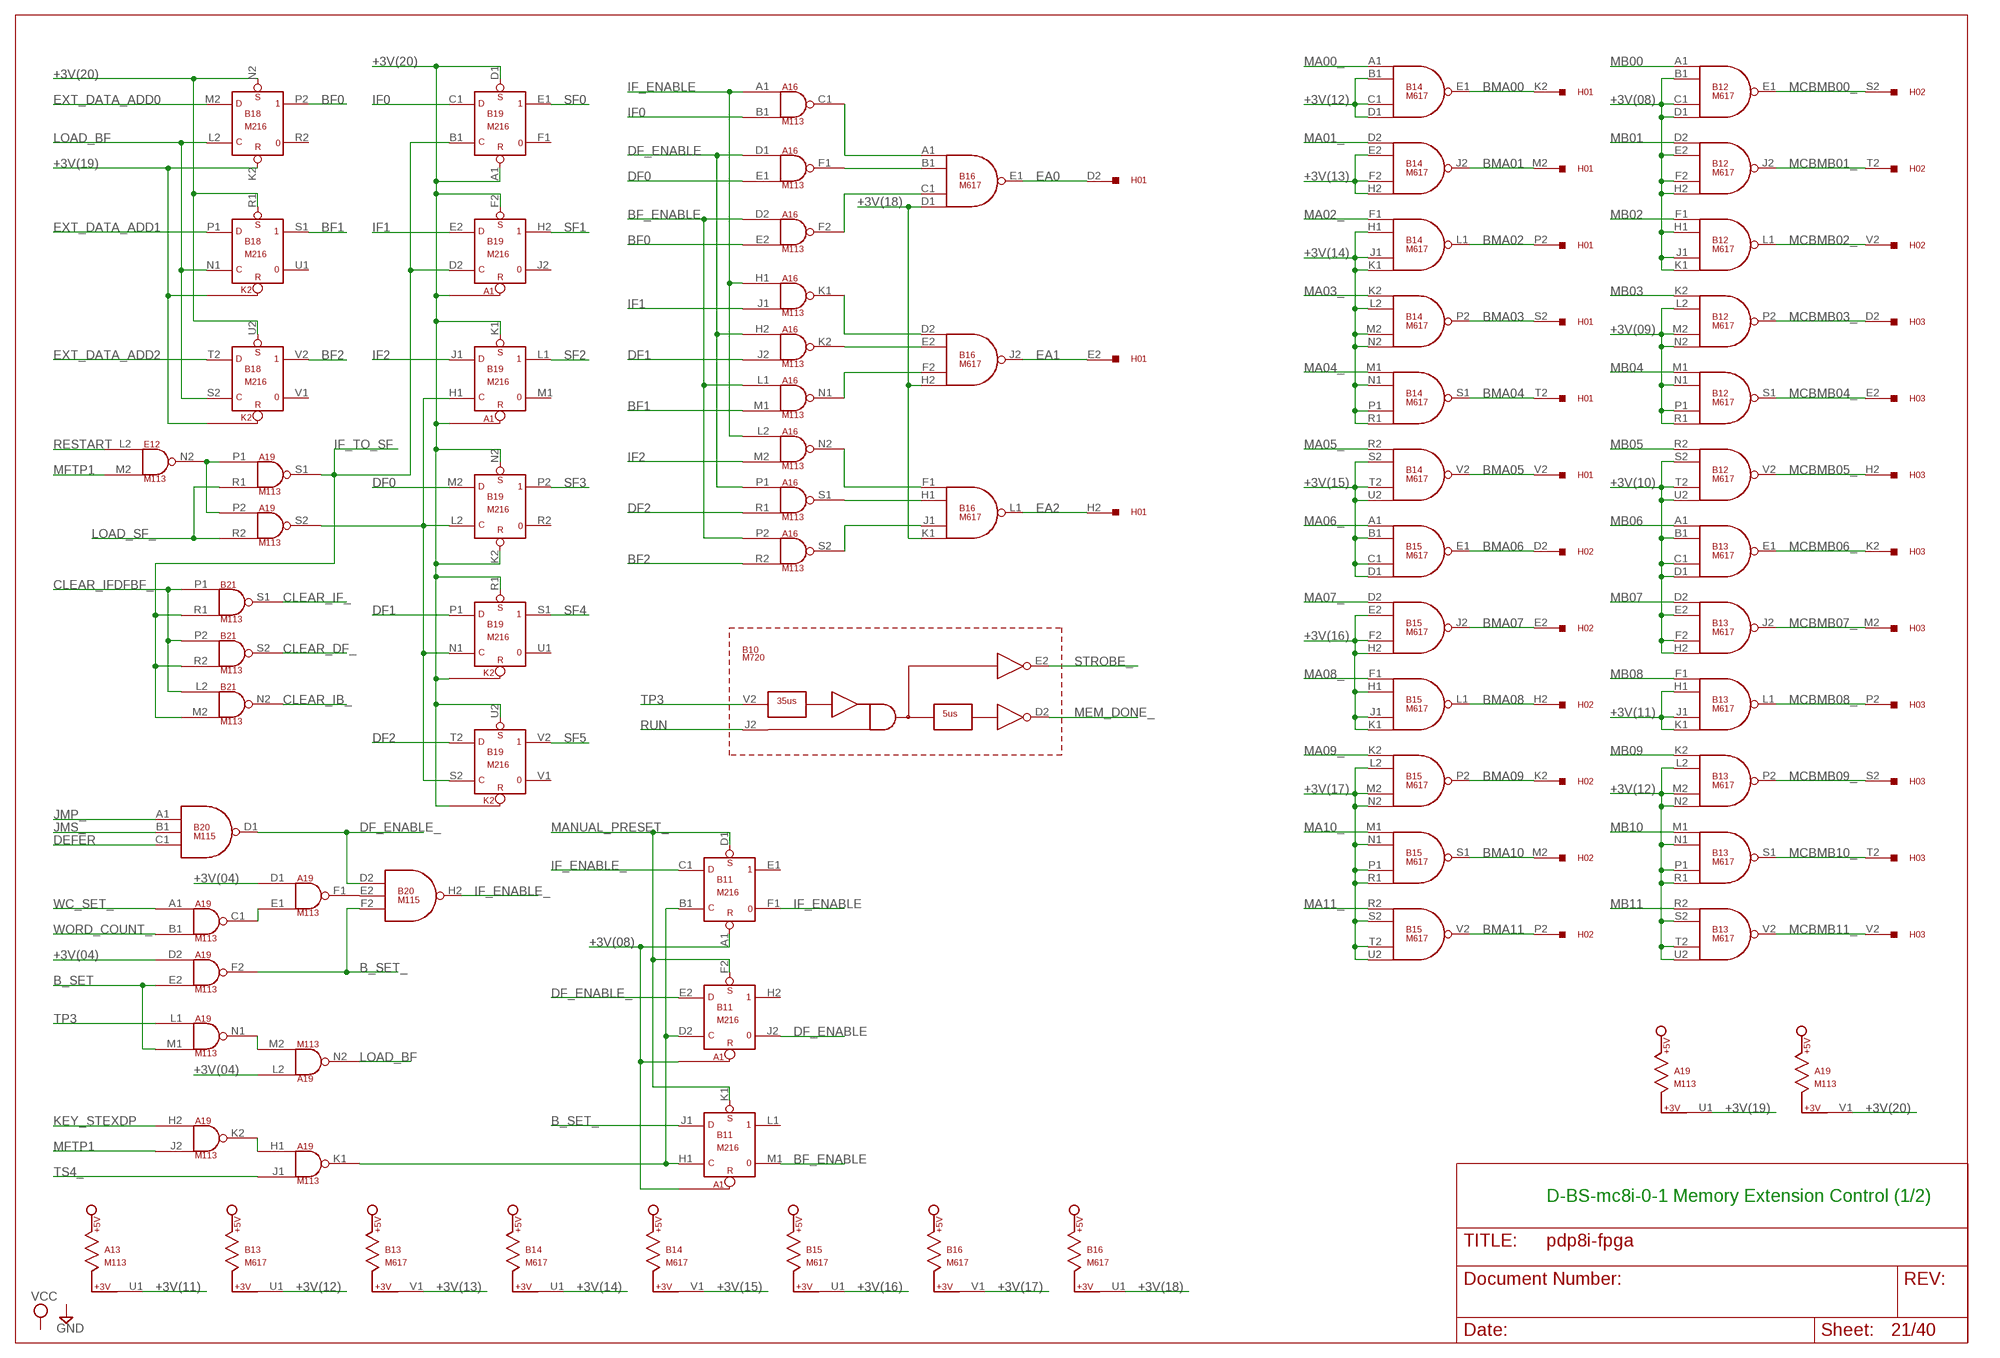
[diagram p21: schematic, sheet 21]
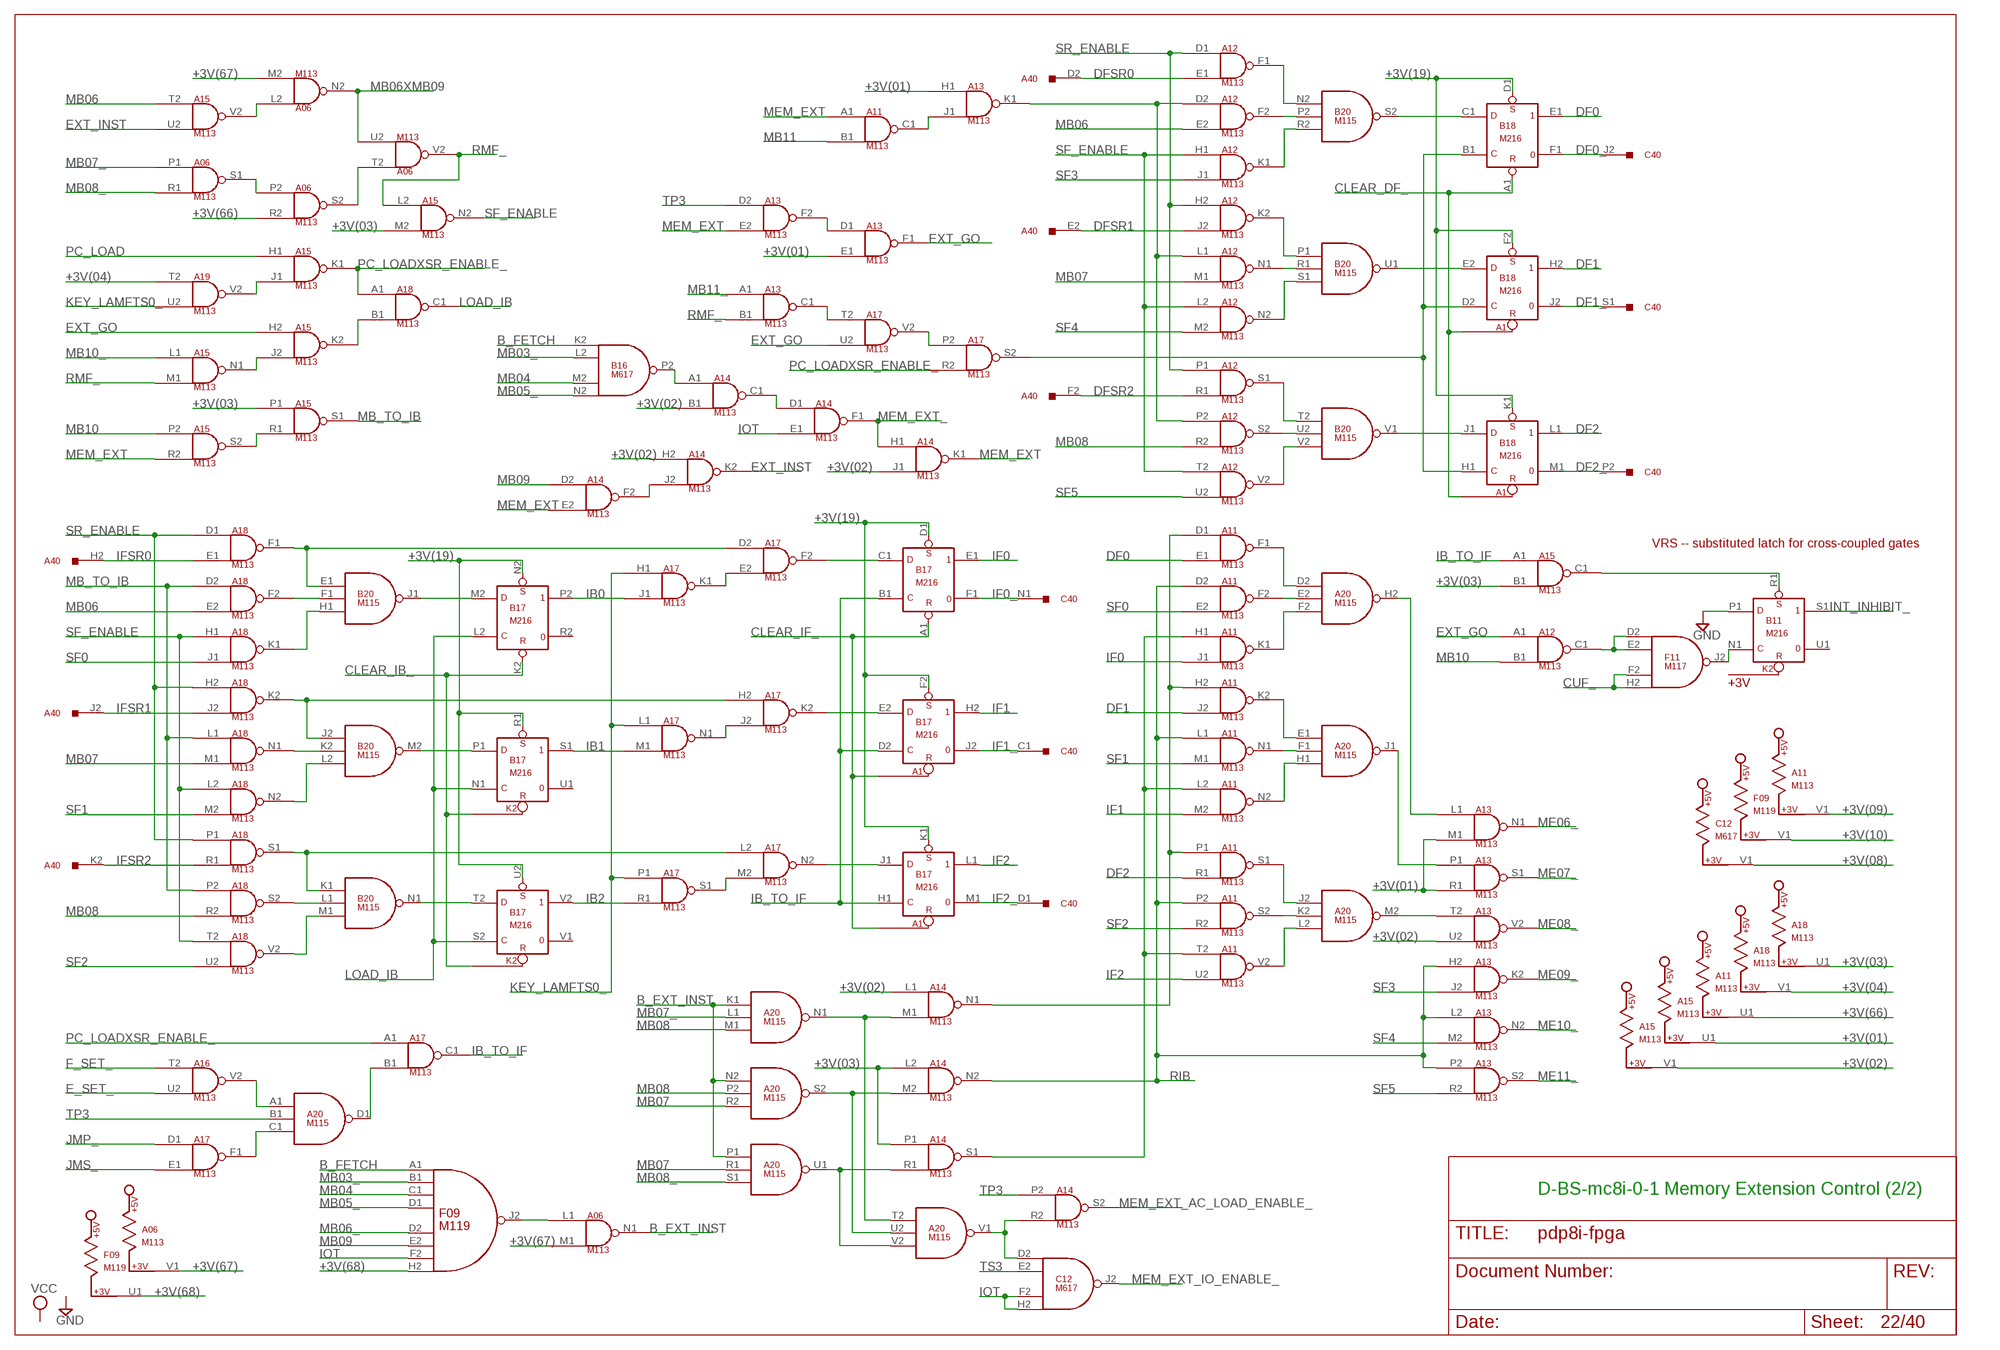
[diagram p22: schematic, sheet 22]
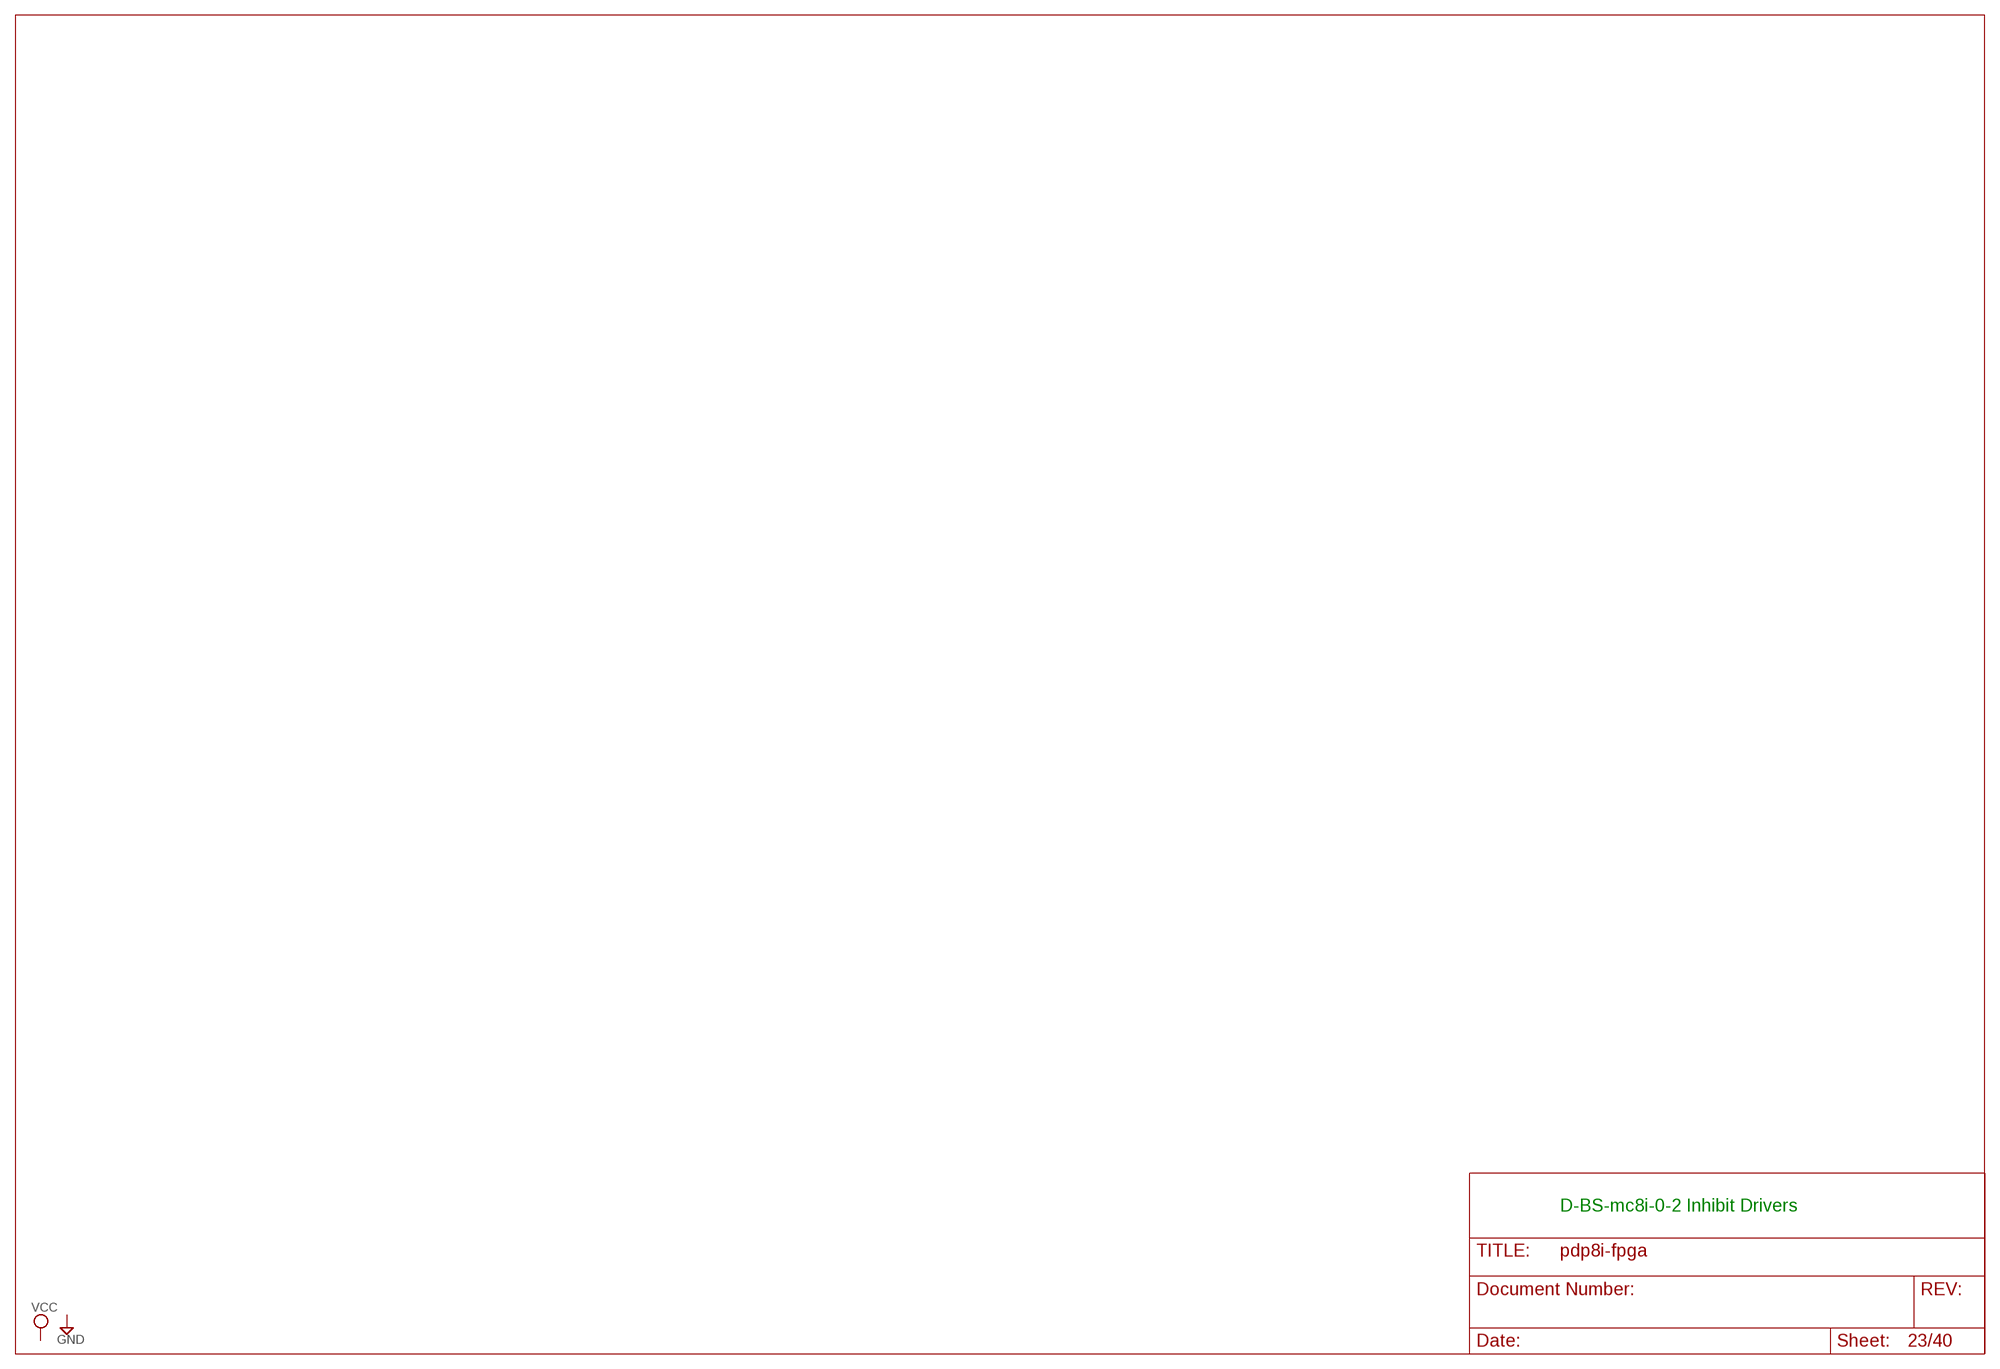
[diagram p23: schematic, sheet 23]
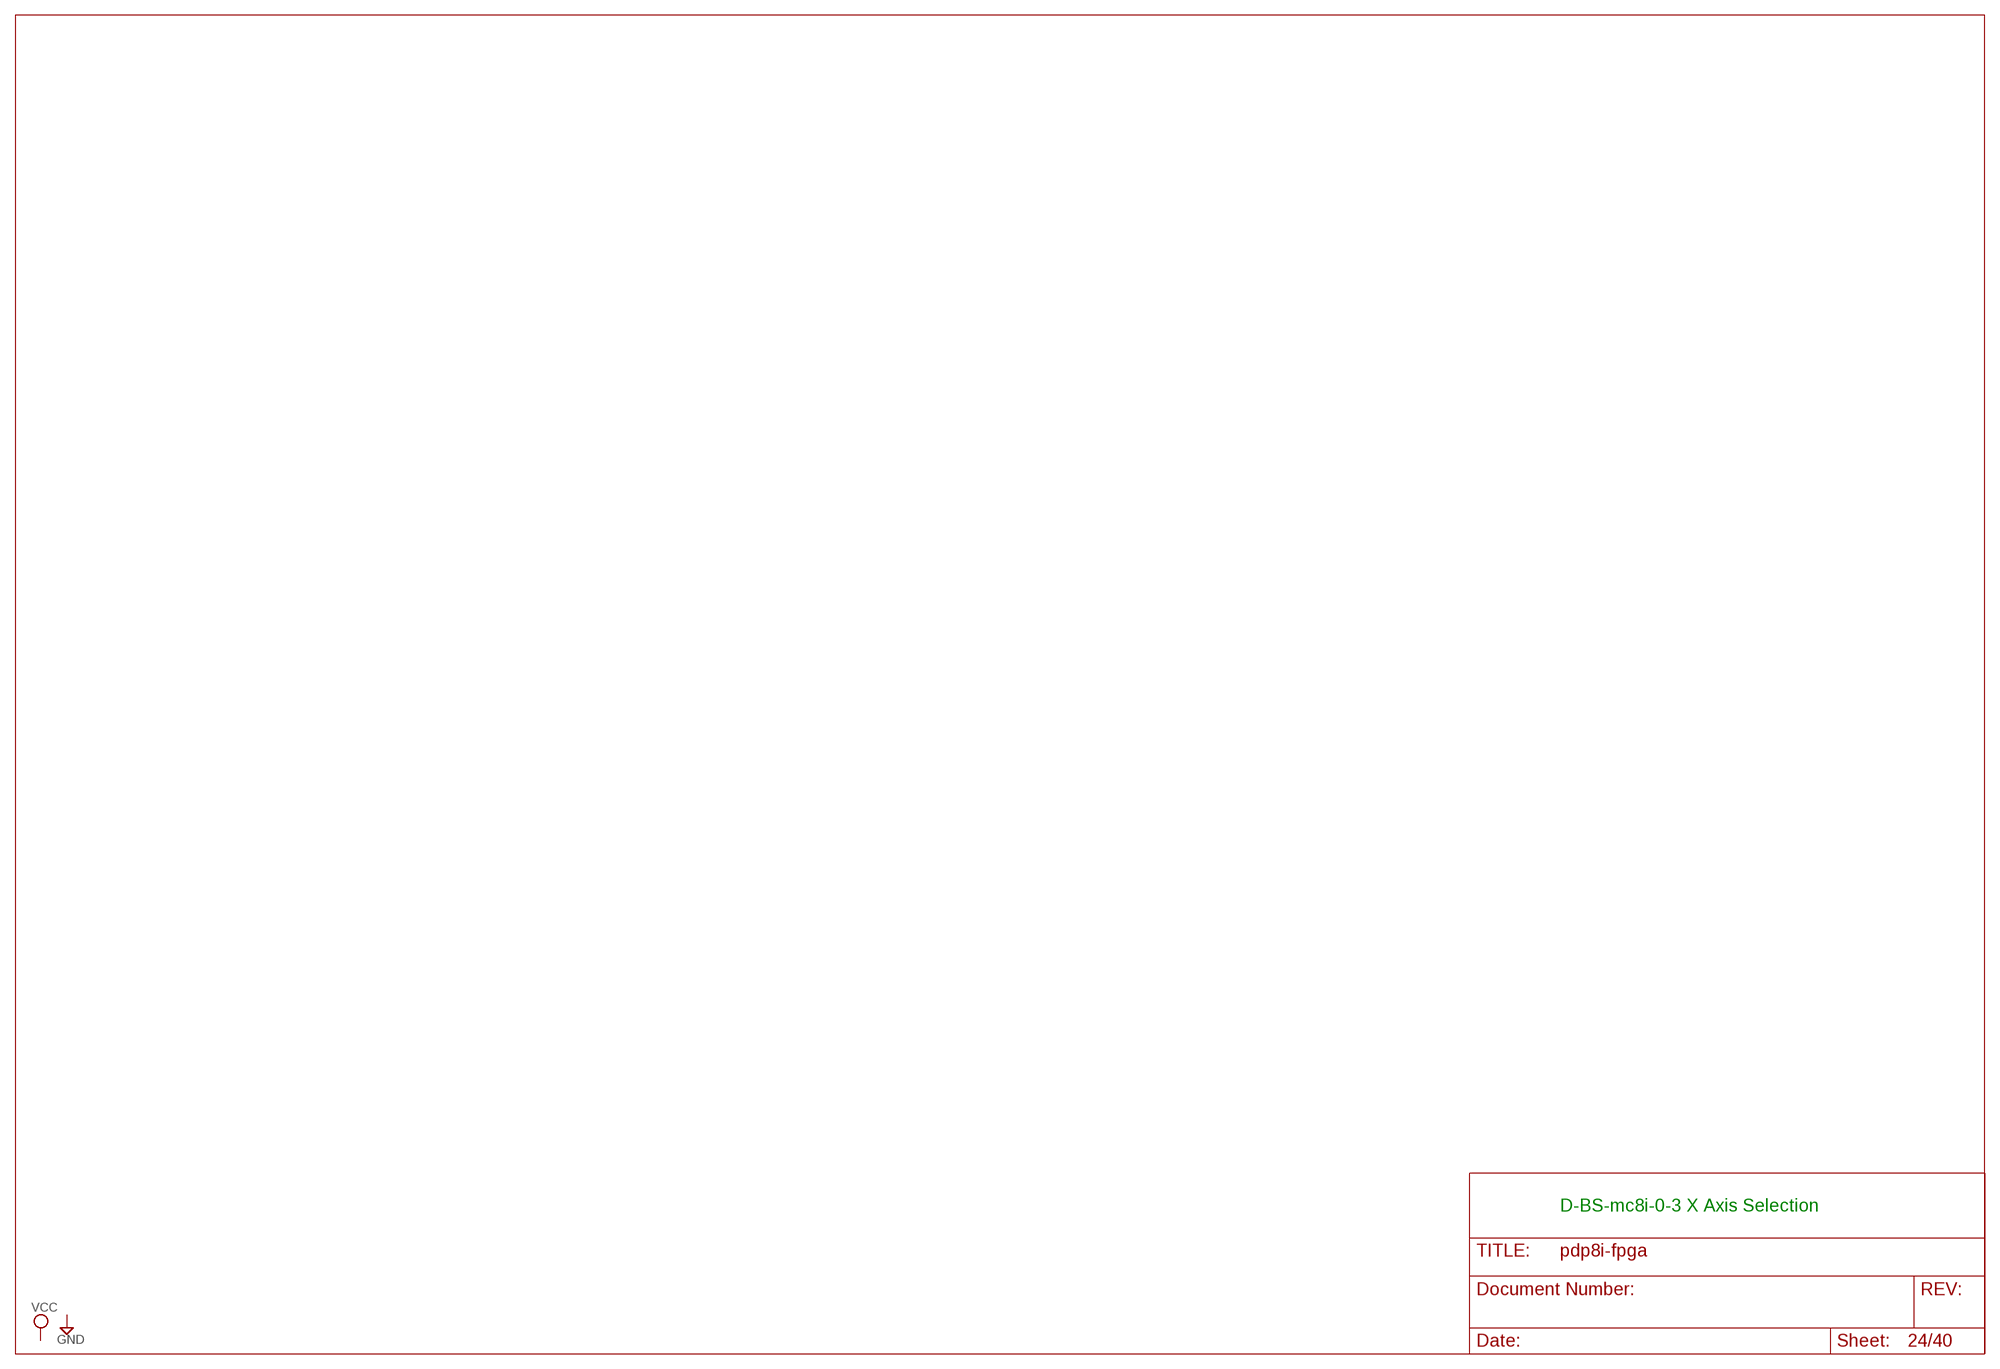
[diagram p24: schematic, sheet 24]
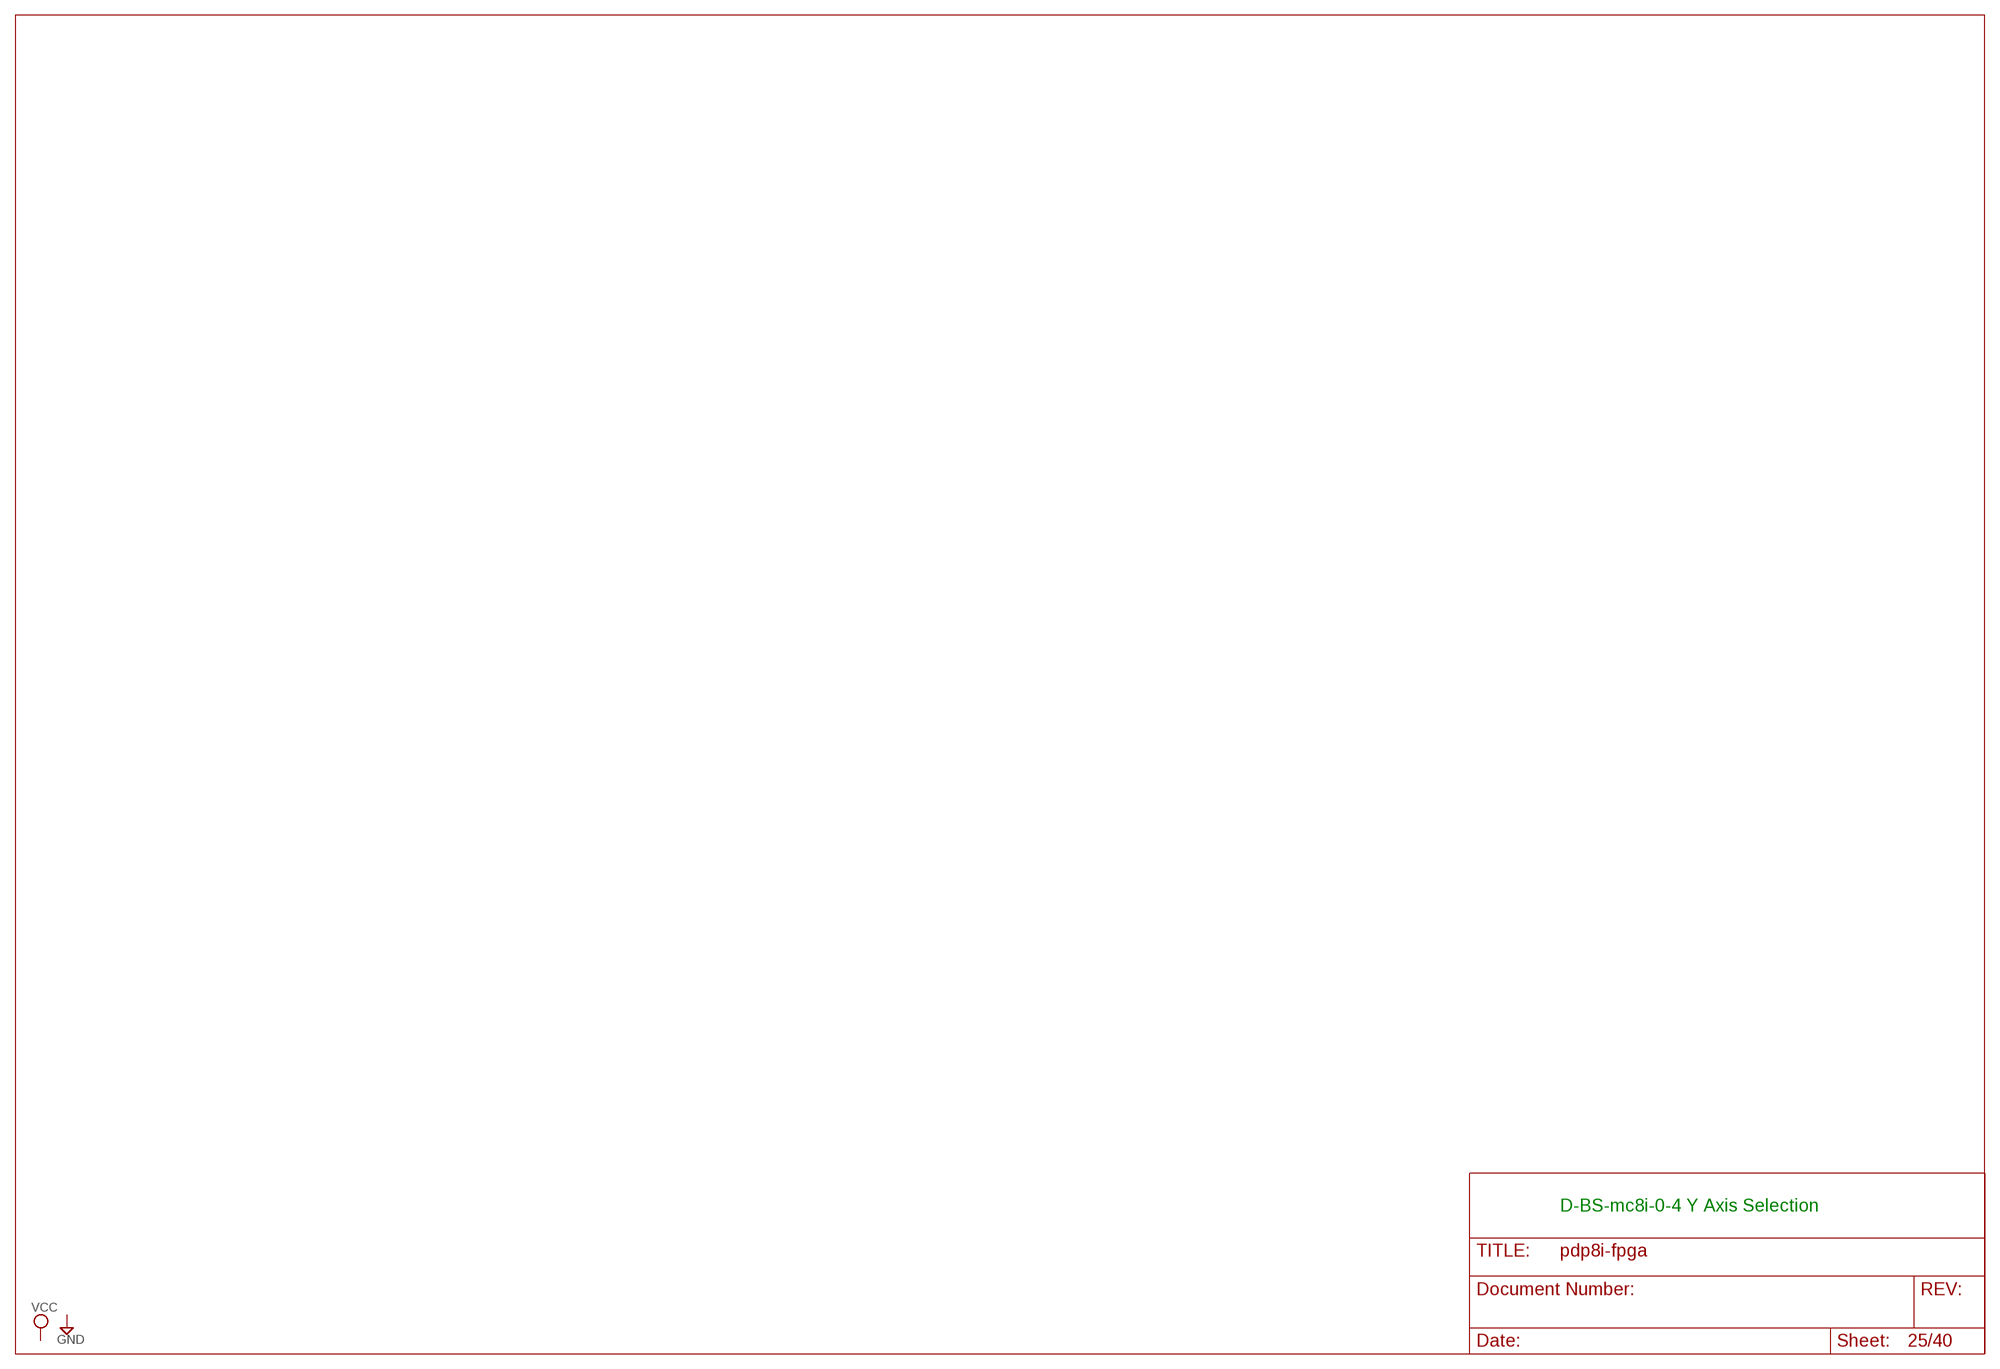
[diagram p25: schematic, sheet 25]
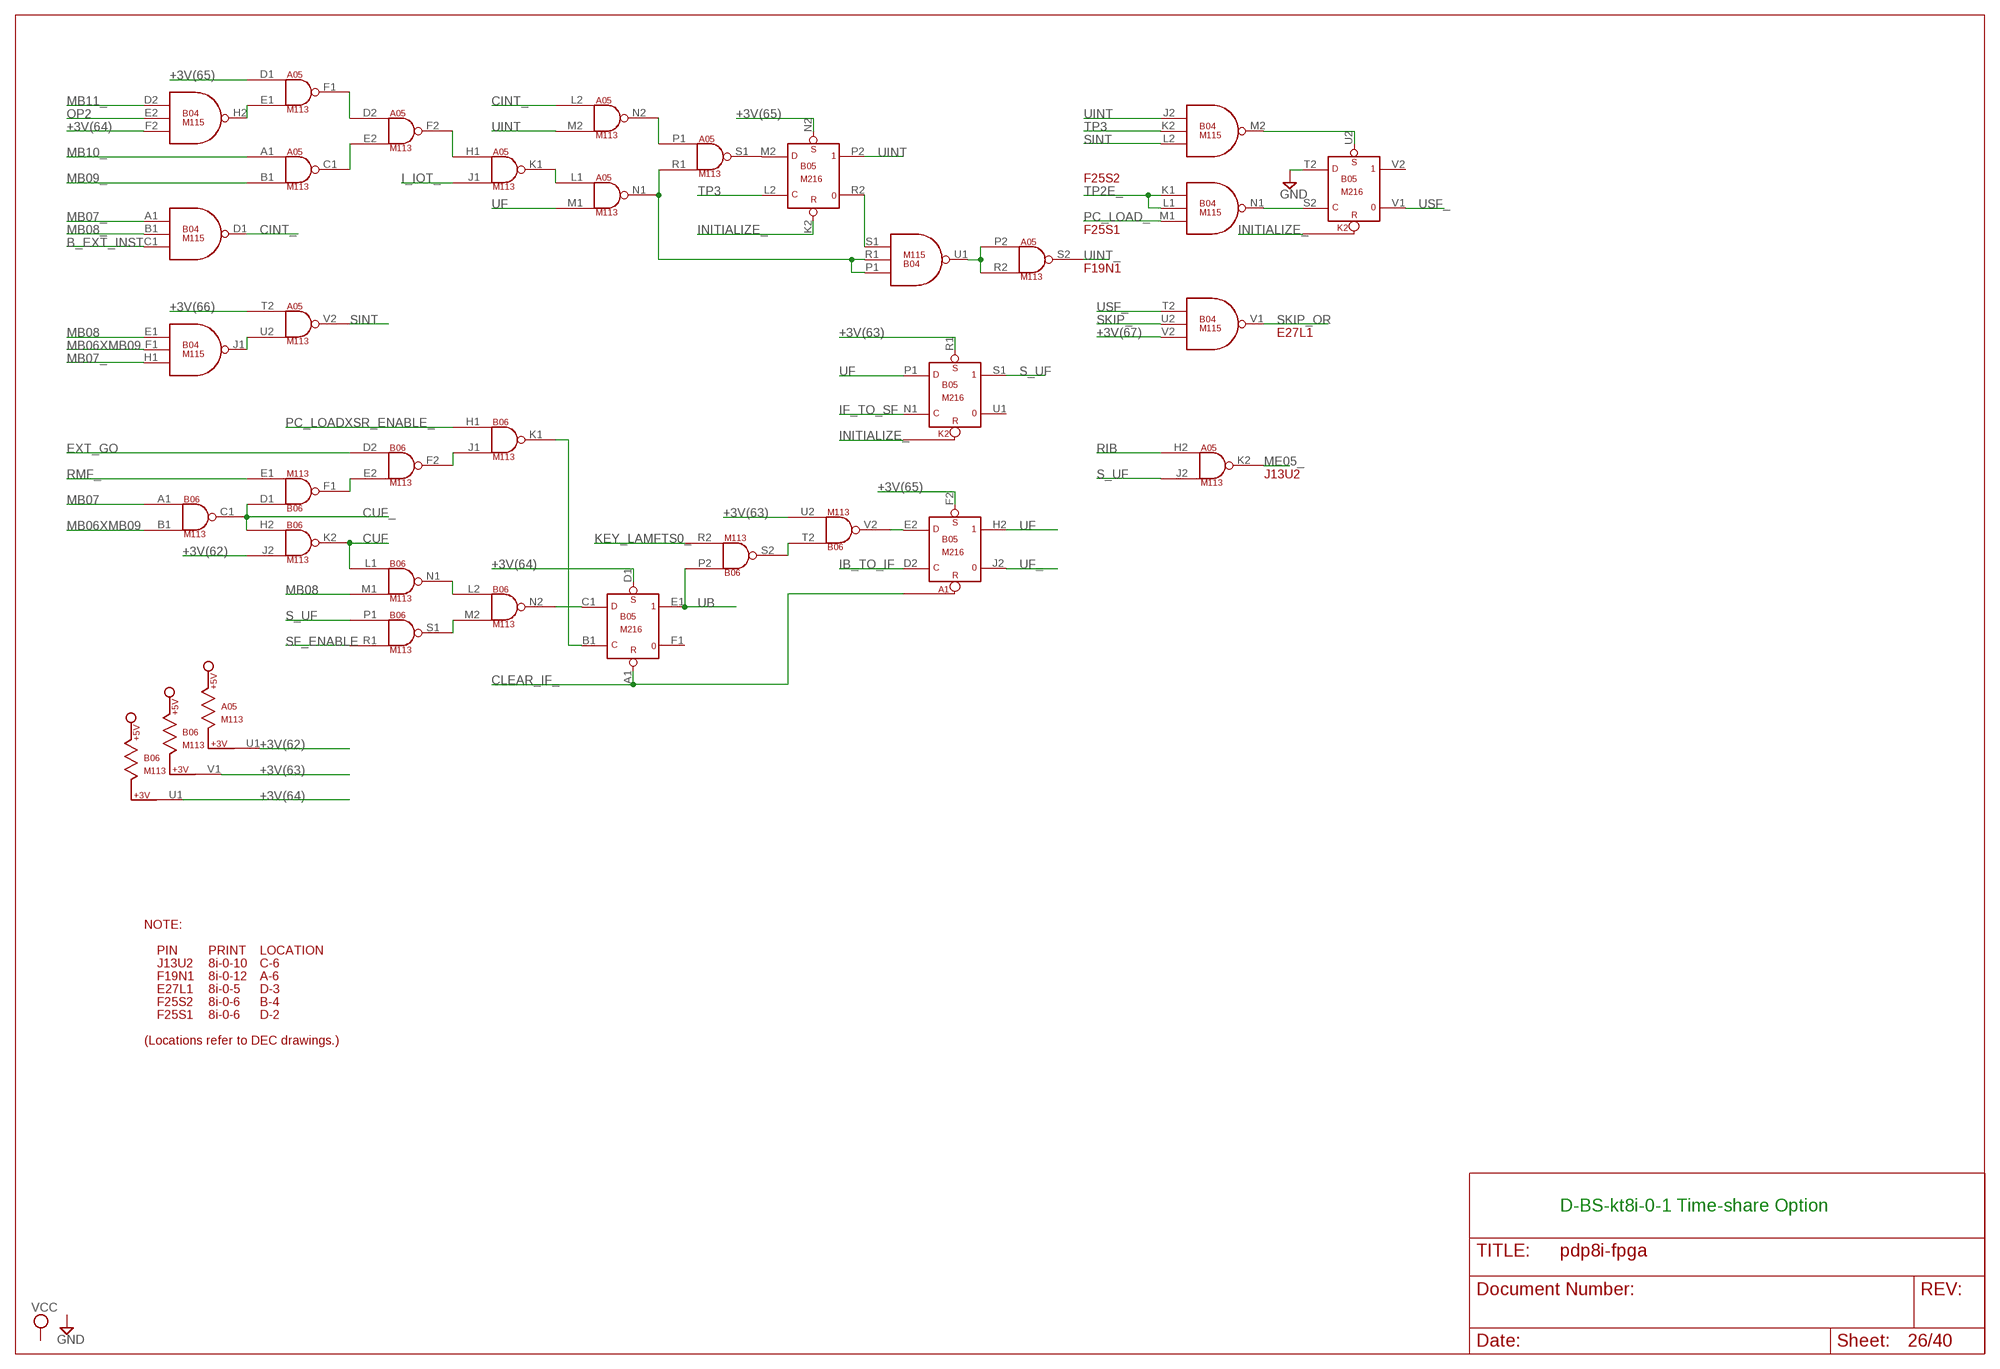
[diagram p26: schematic, sheet 26]
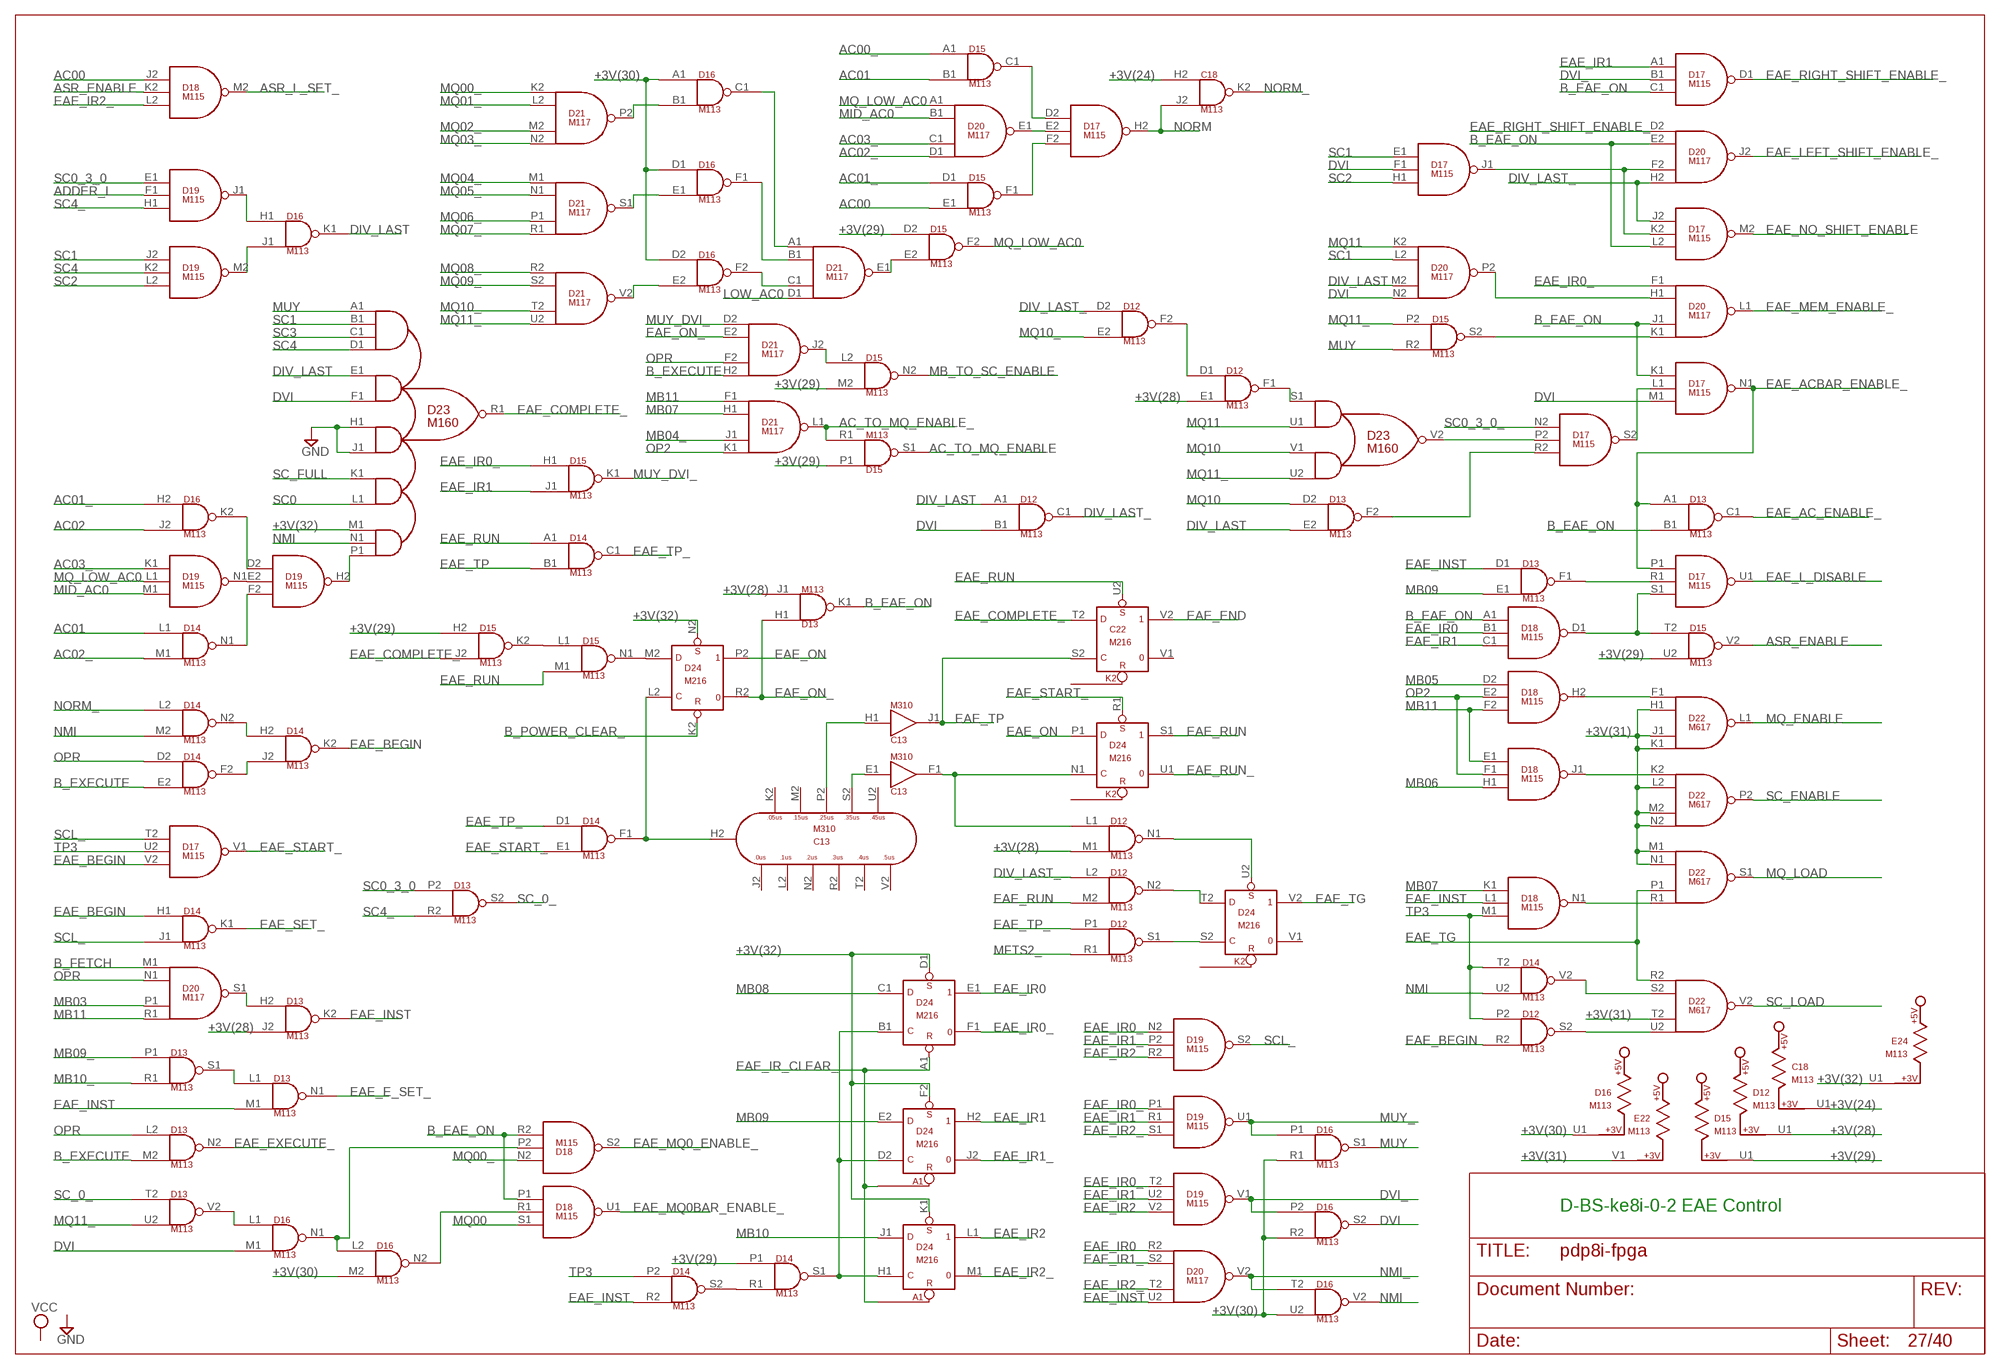
[diagram p27: schematic, sheet 27]
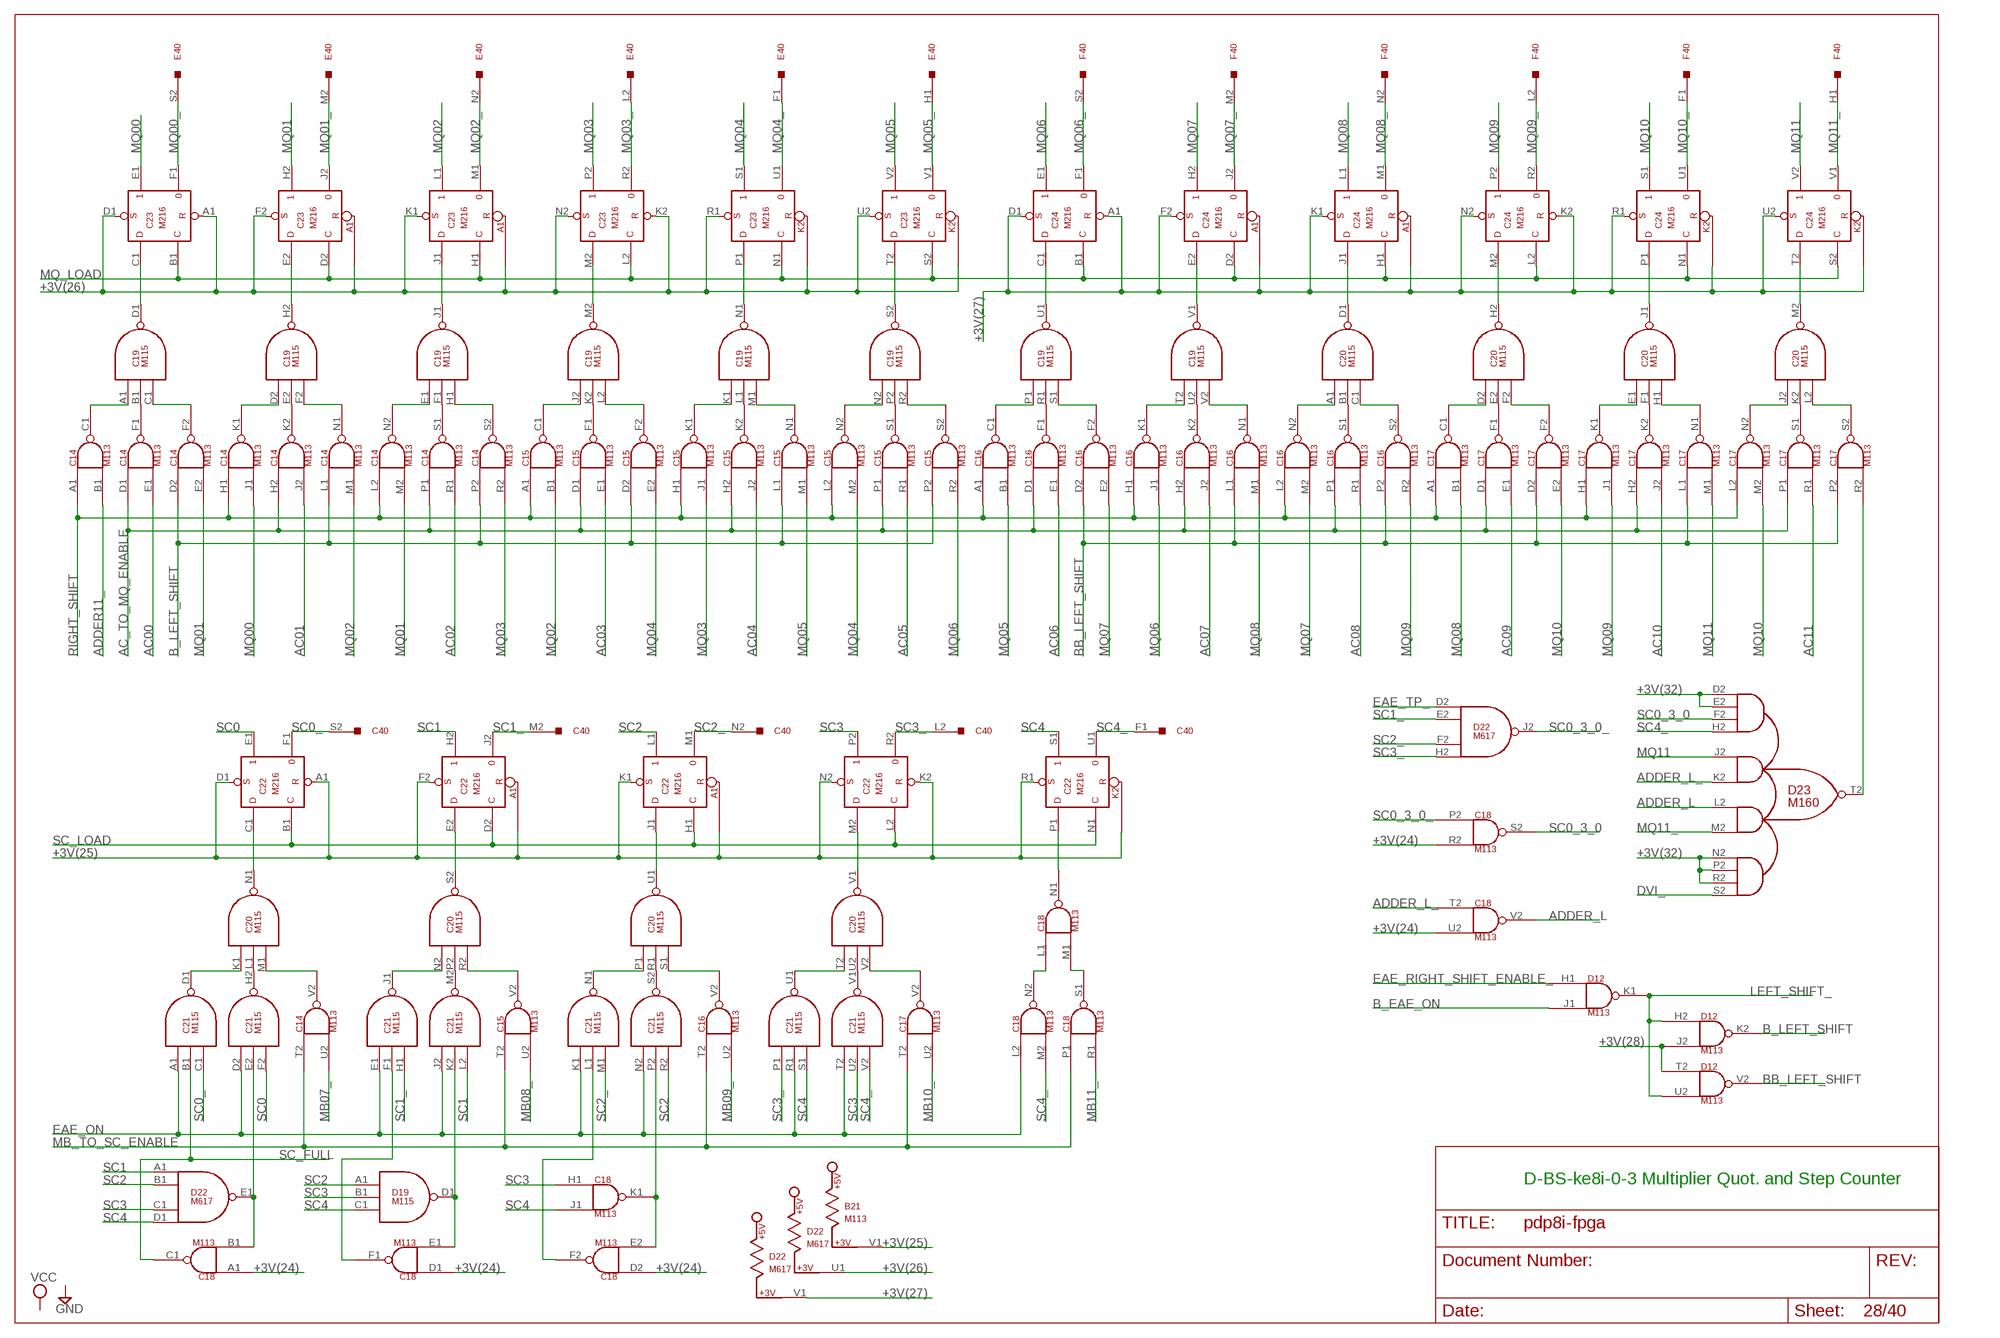
[diagram p28: schematic, sheet 28]
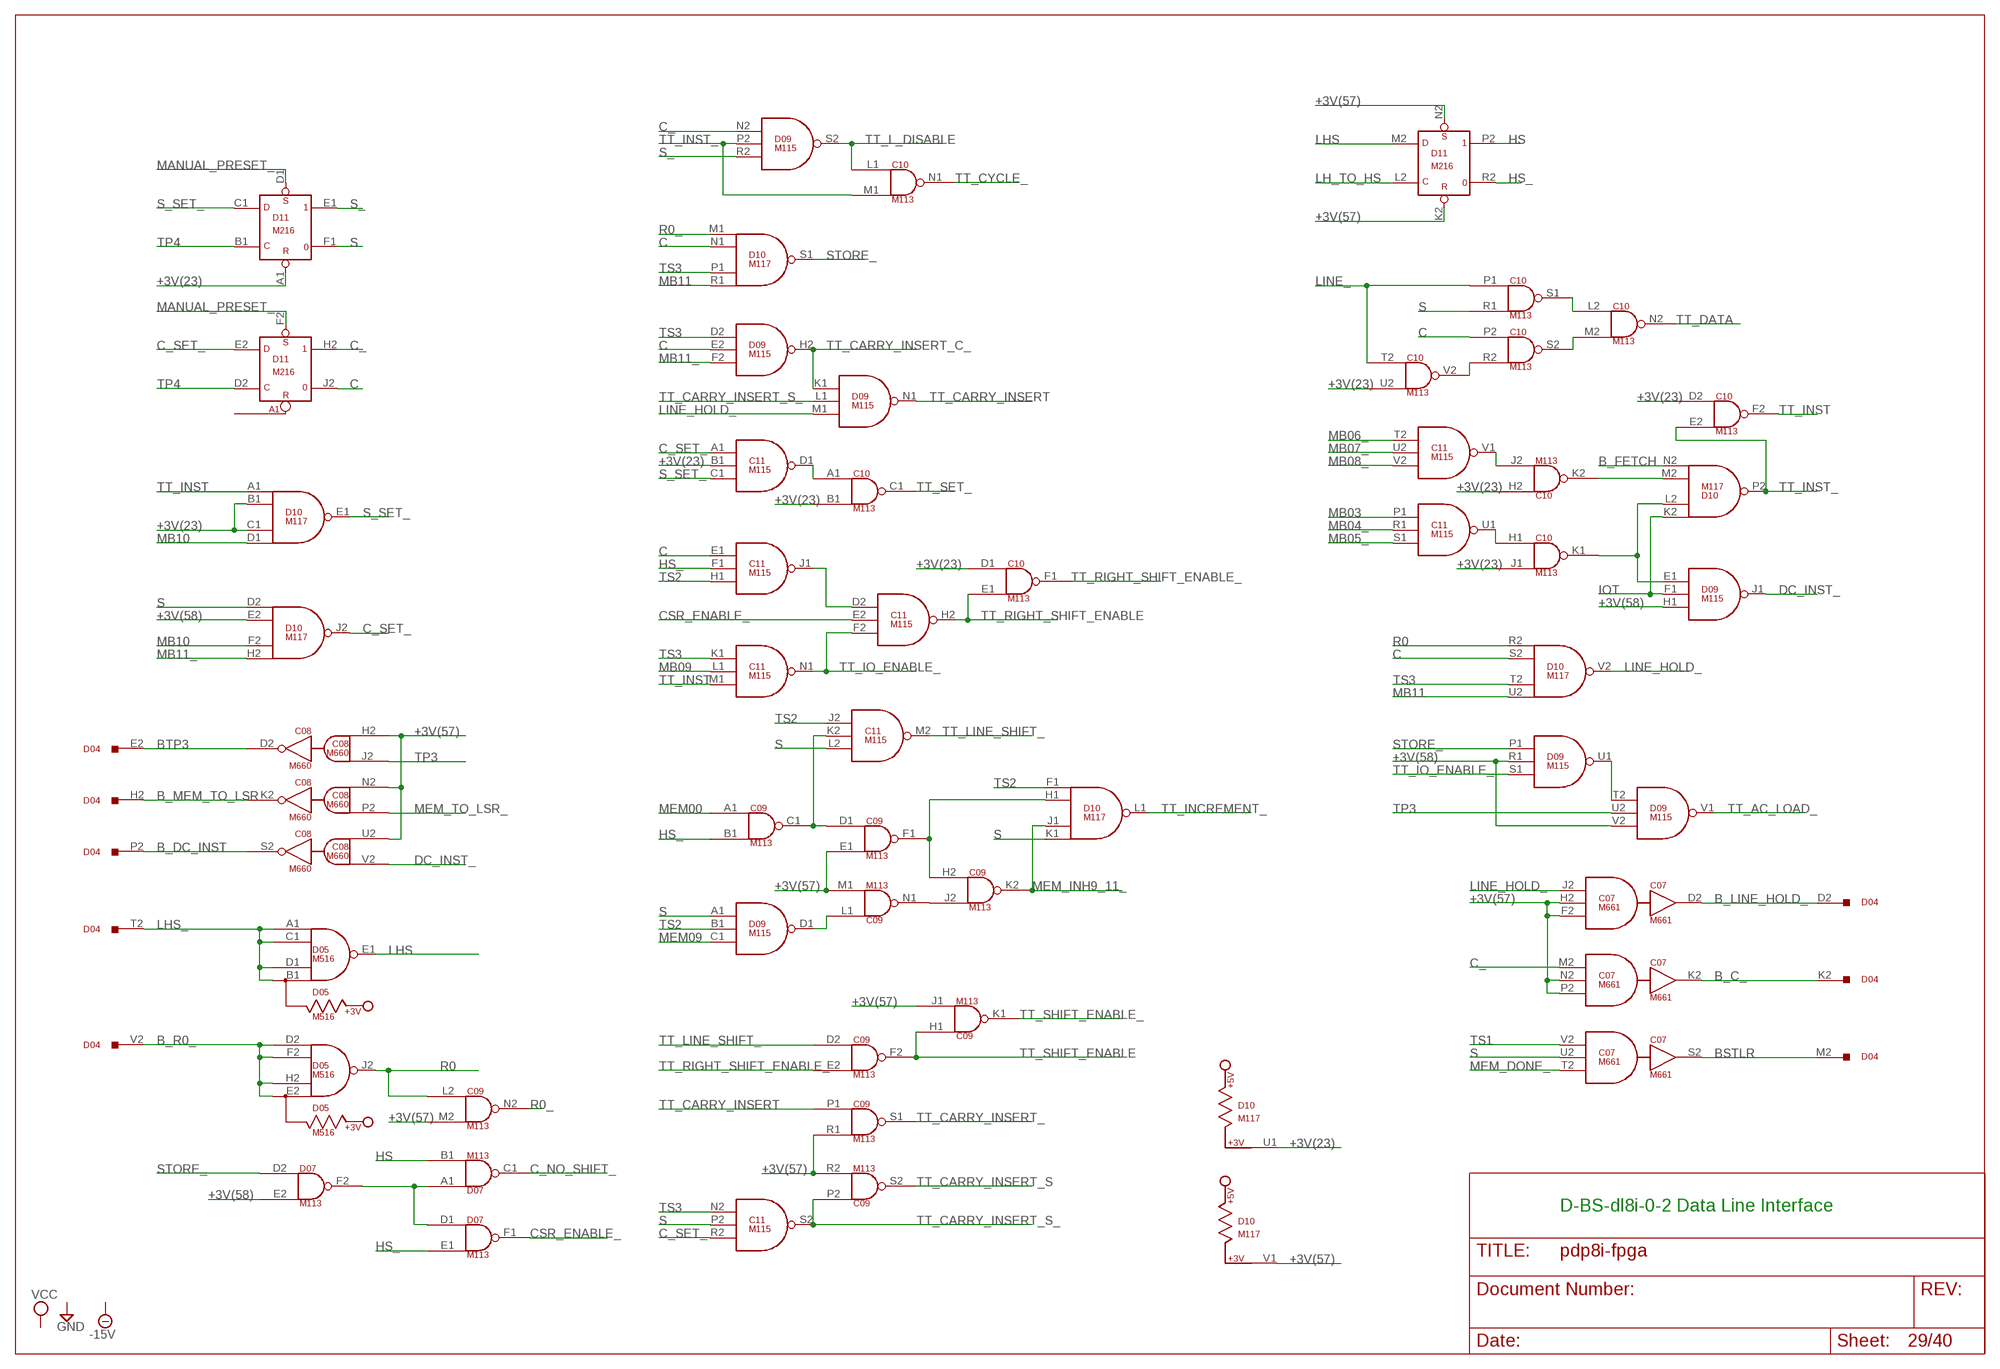
[diagram p29: schematic, sheet 29]
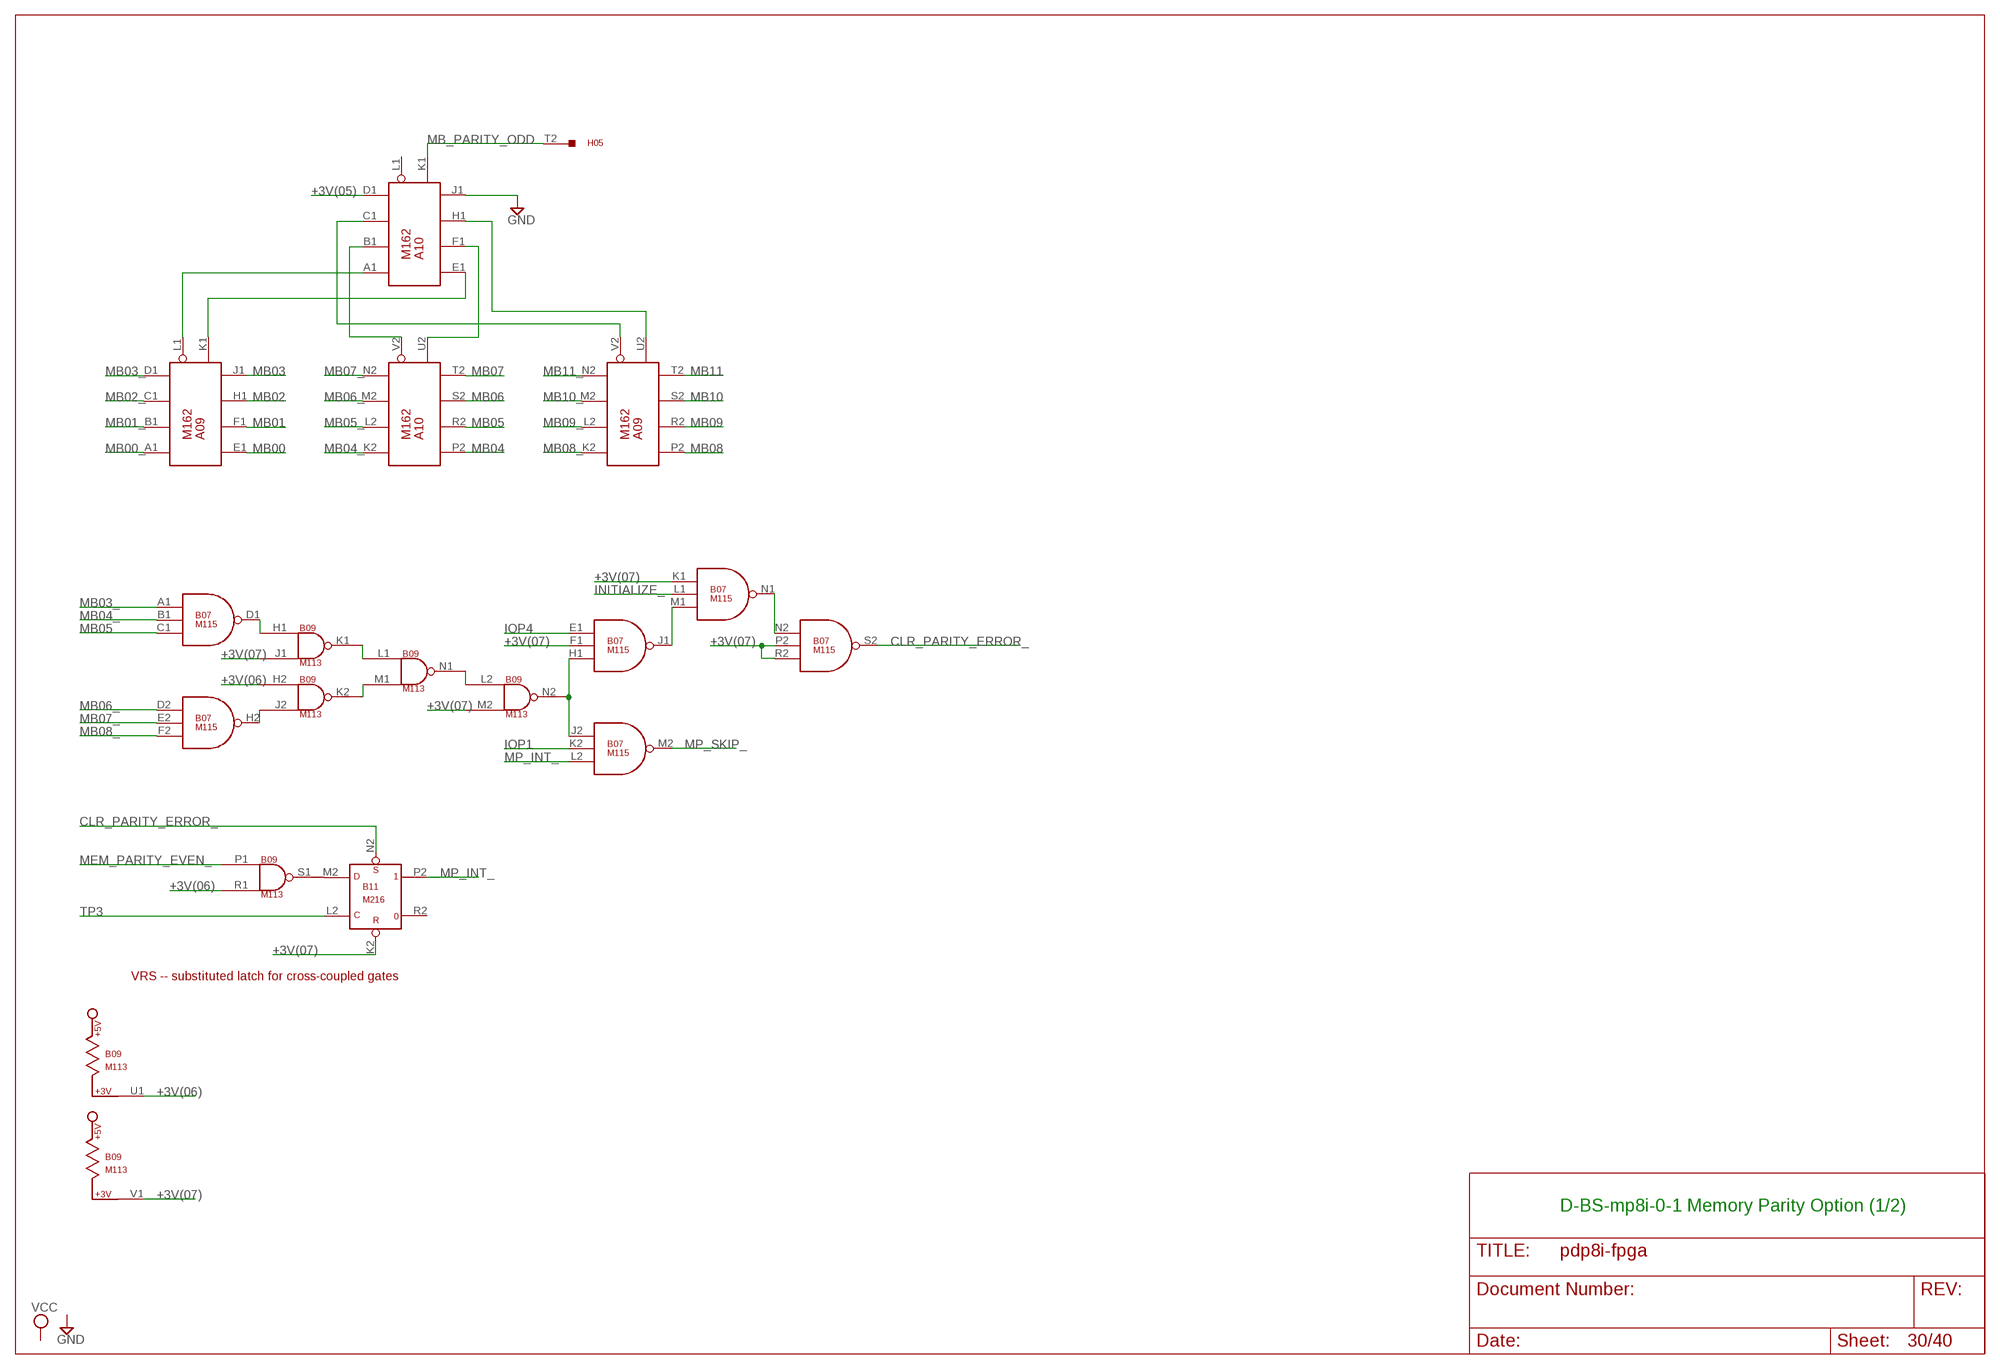
[diagram p30: schematic, sheet 30]
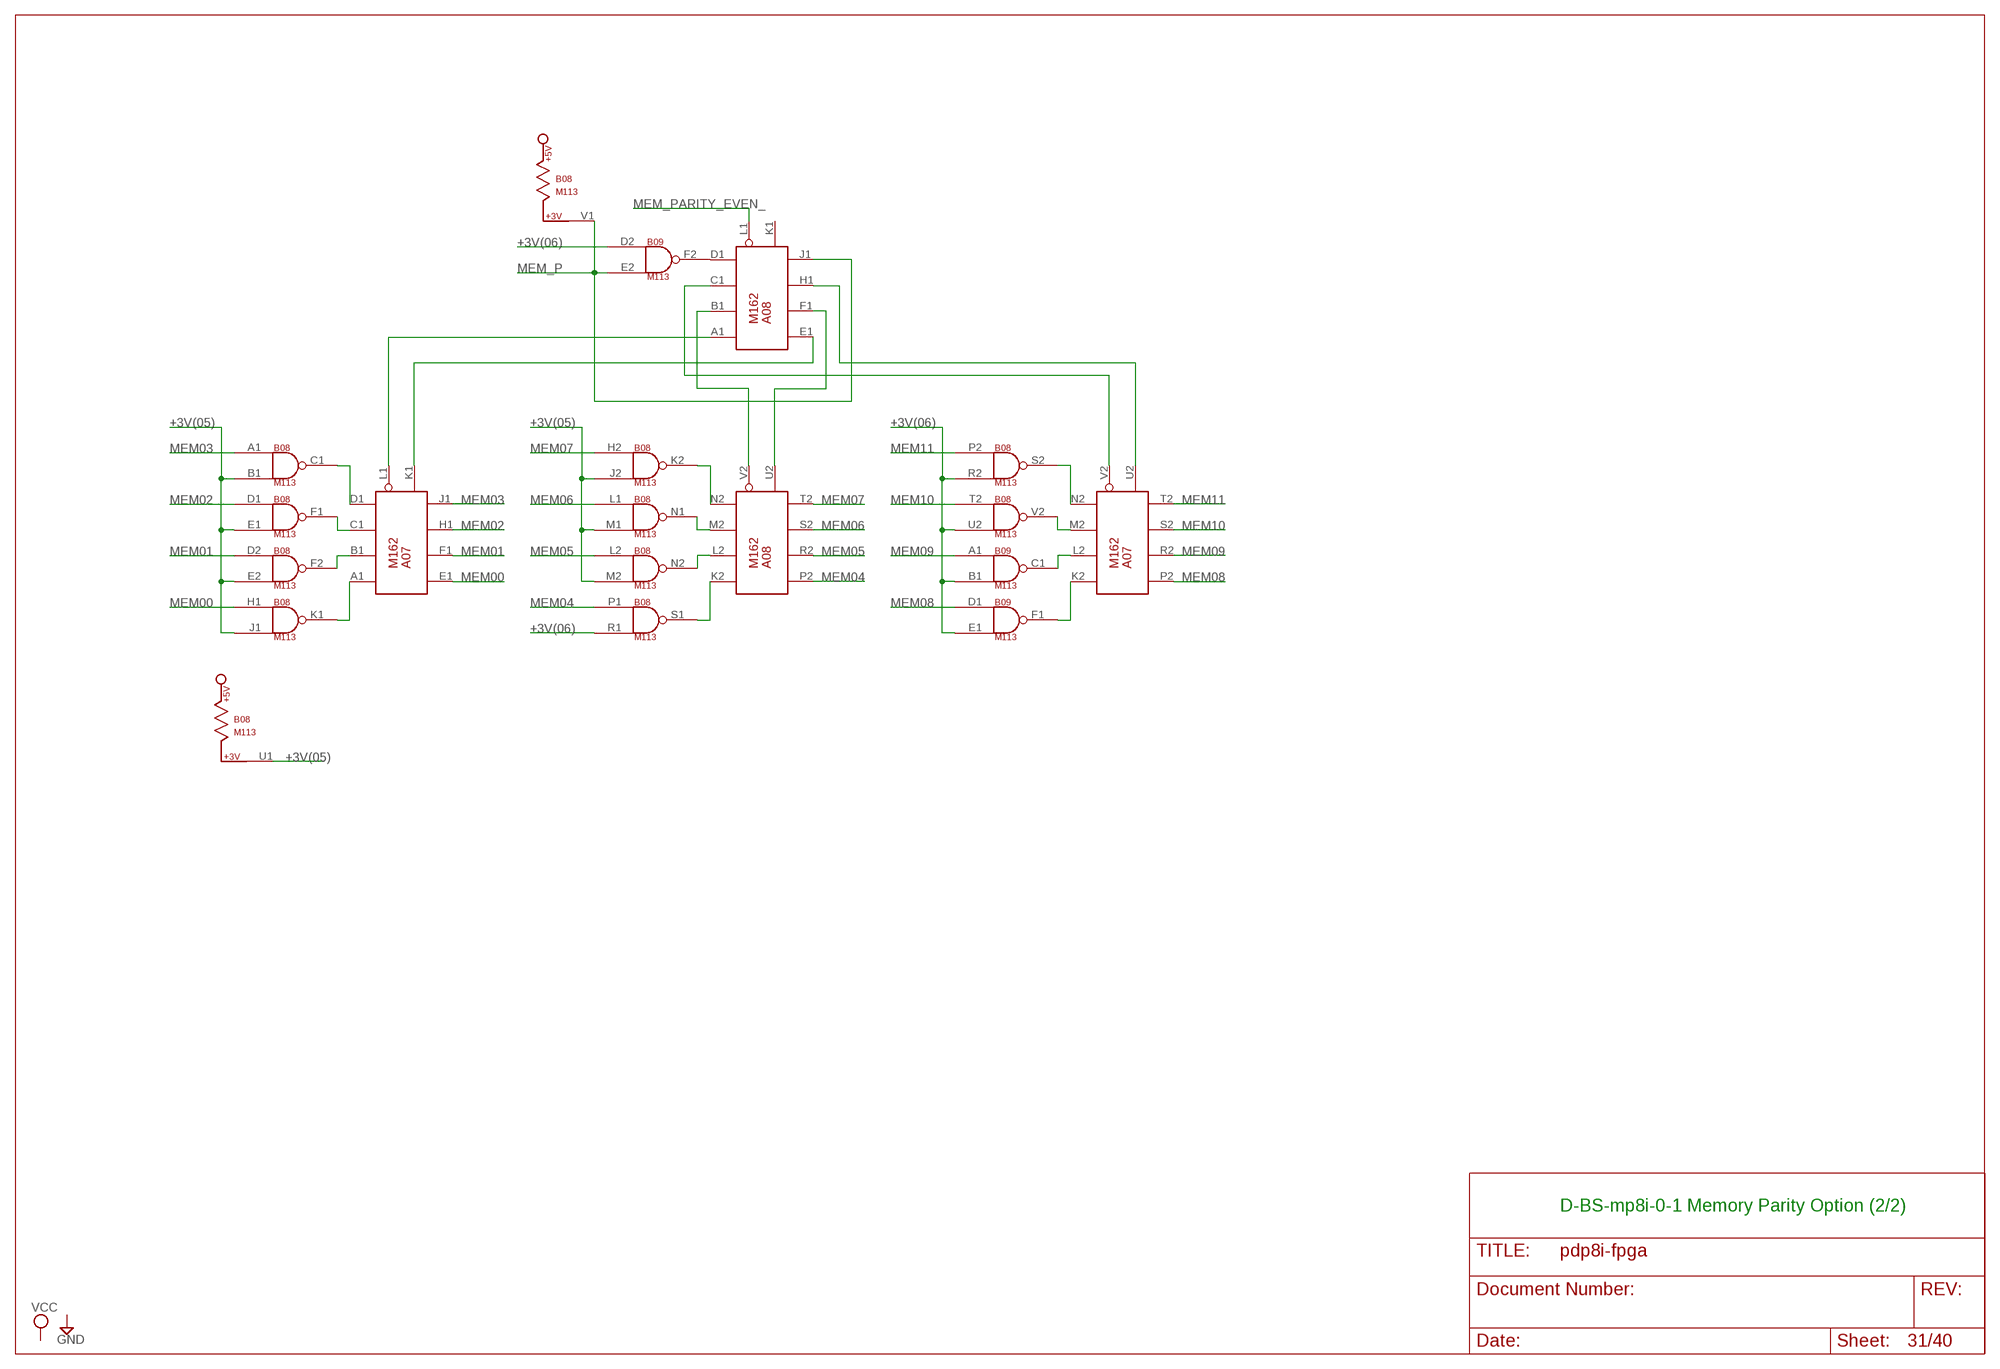
[diagram p31: schematic, sheet 31]
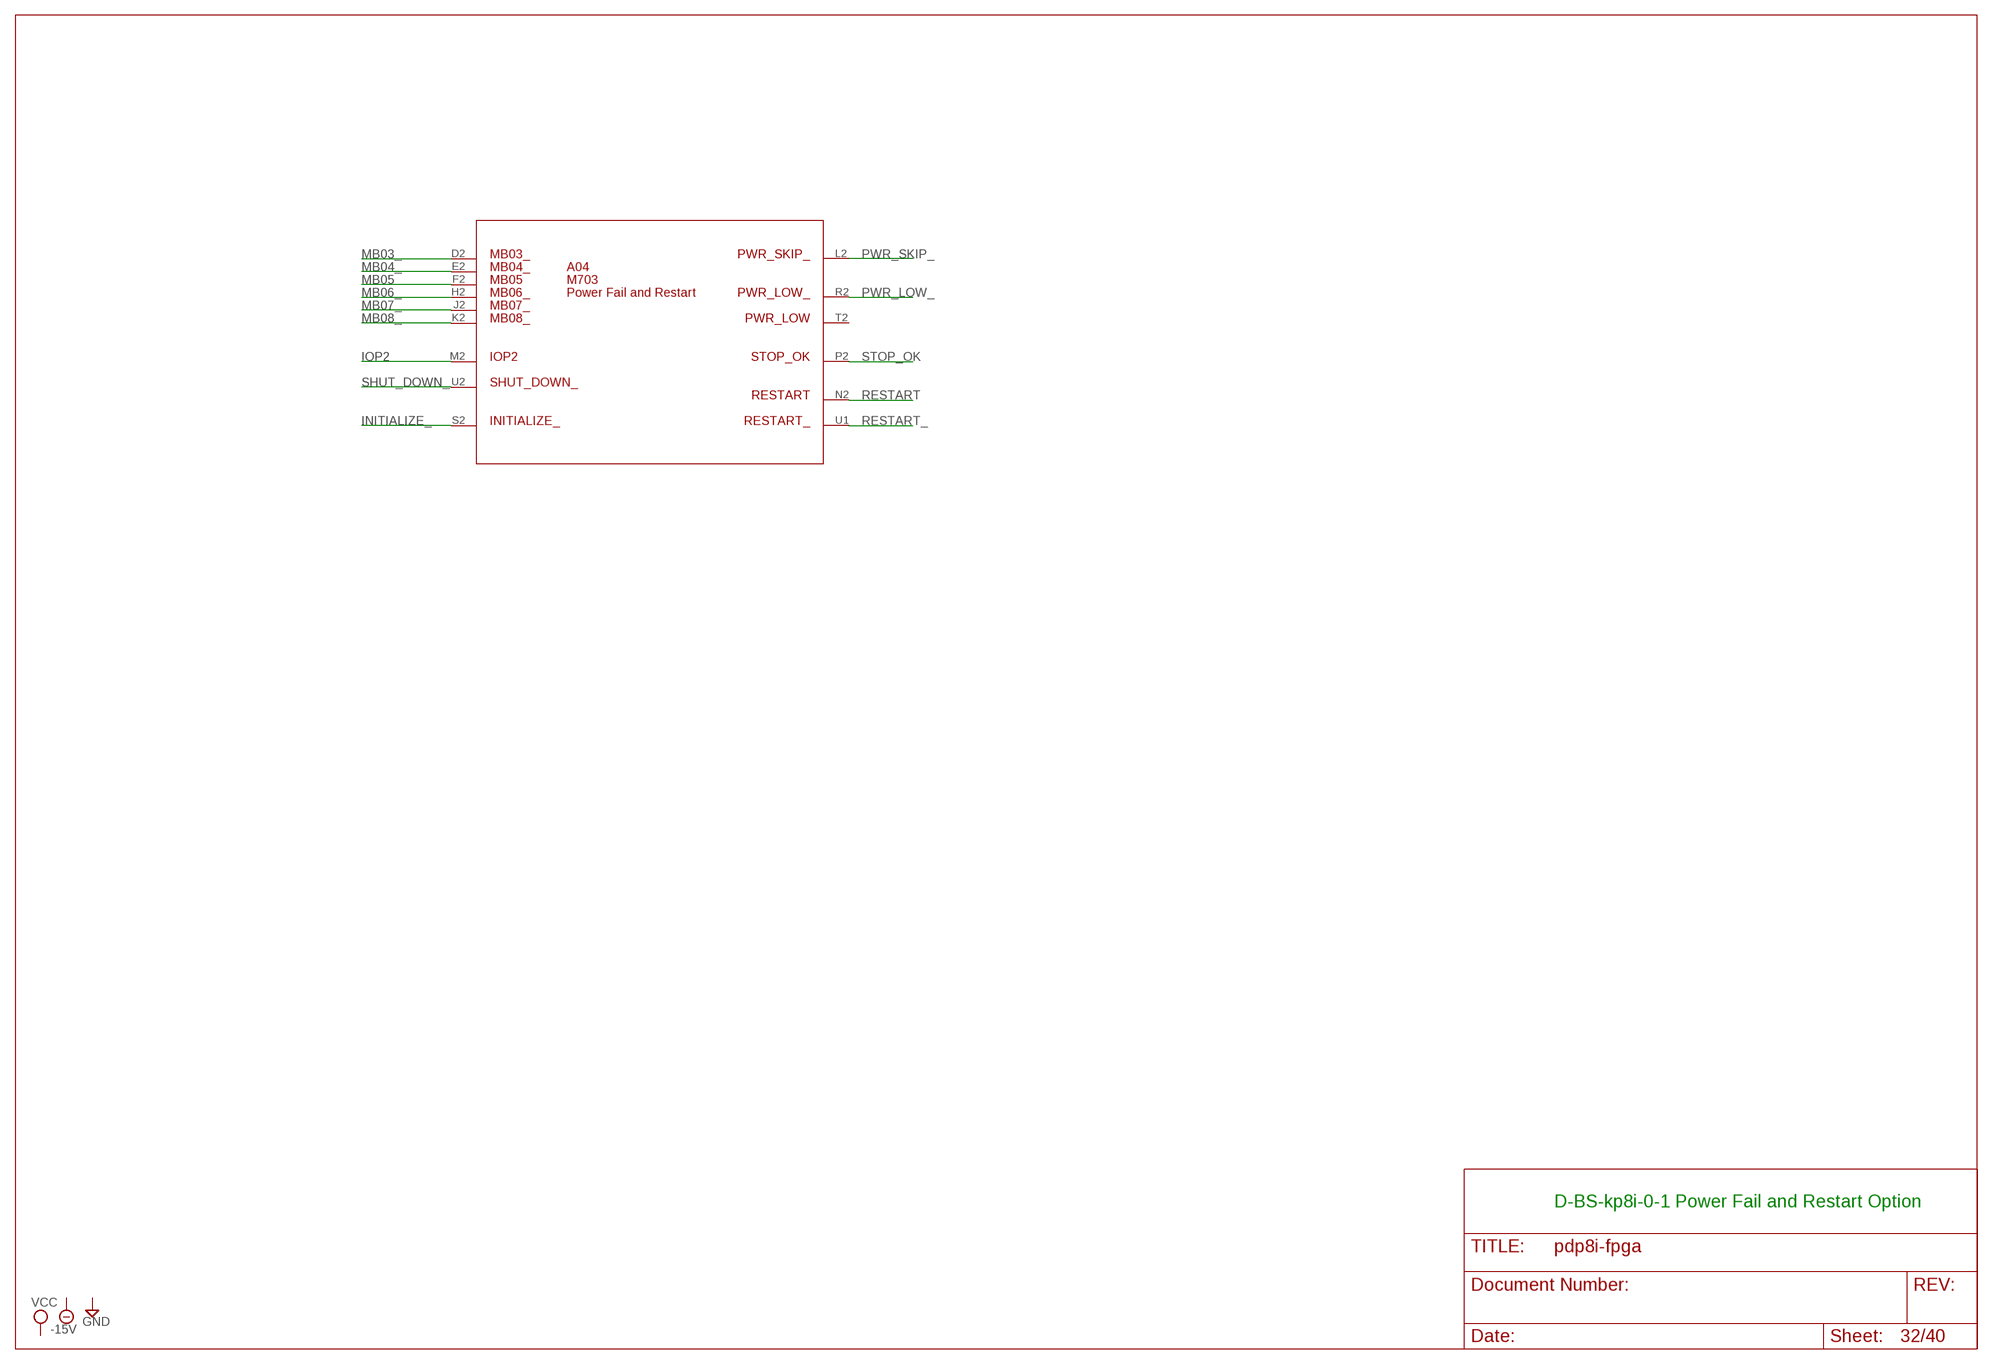
[diagram p32: schematic, sheet 32]
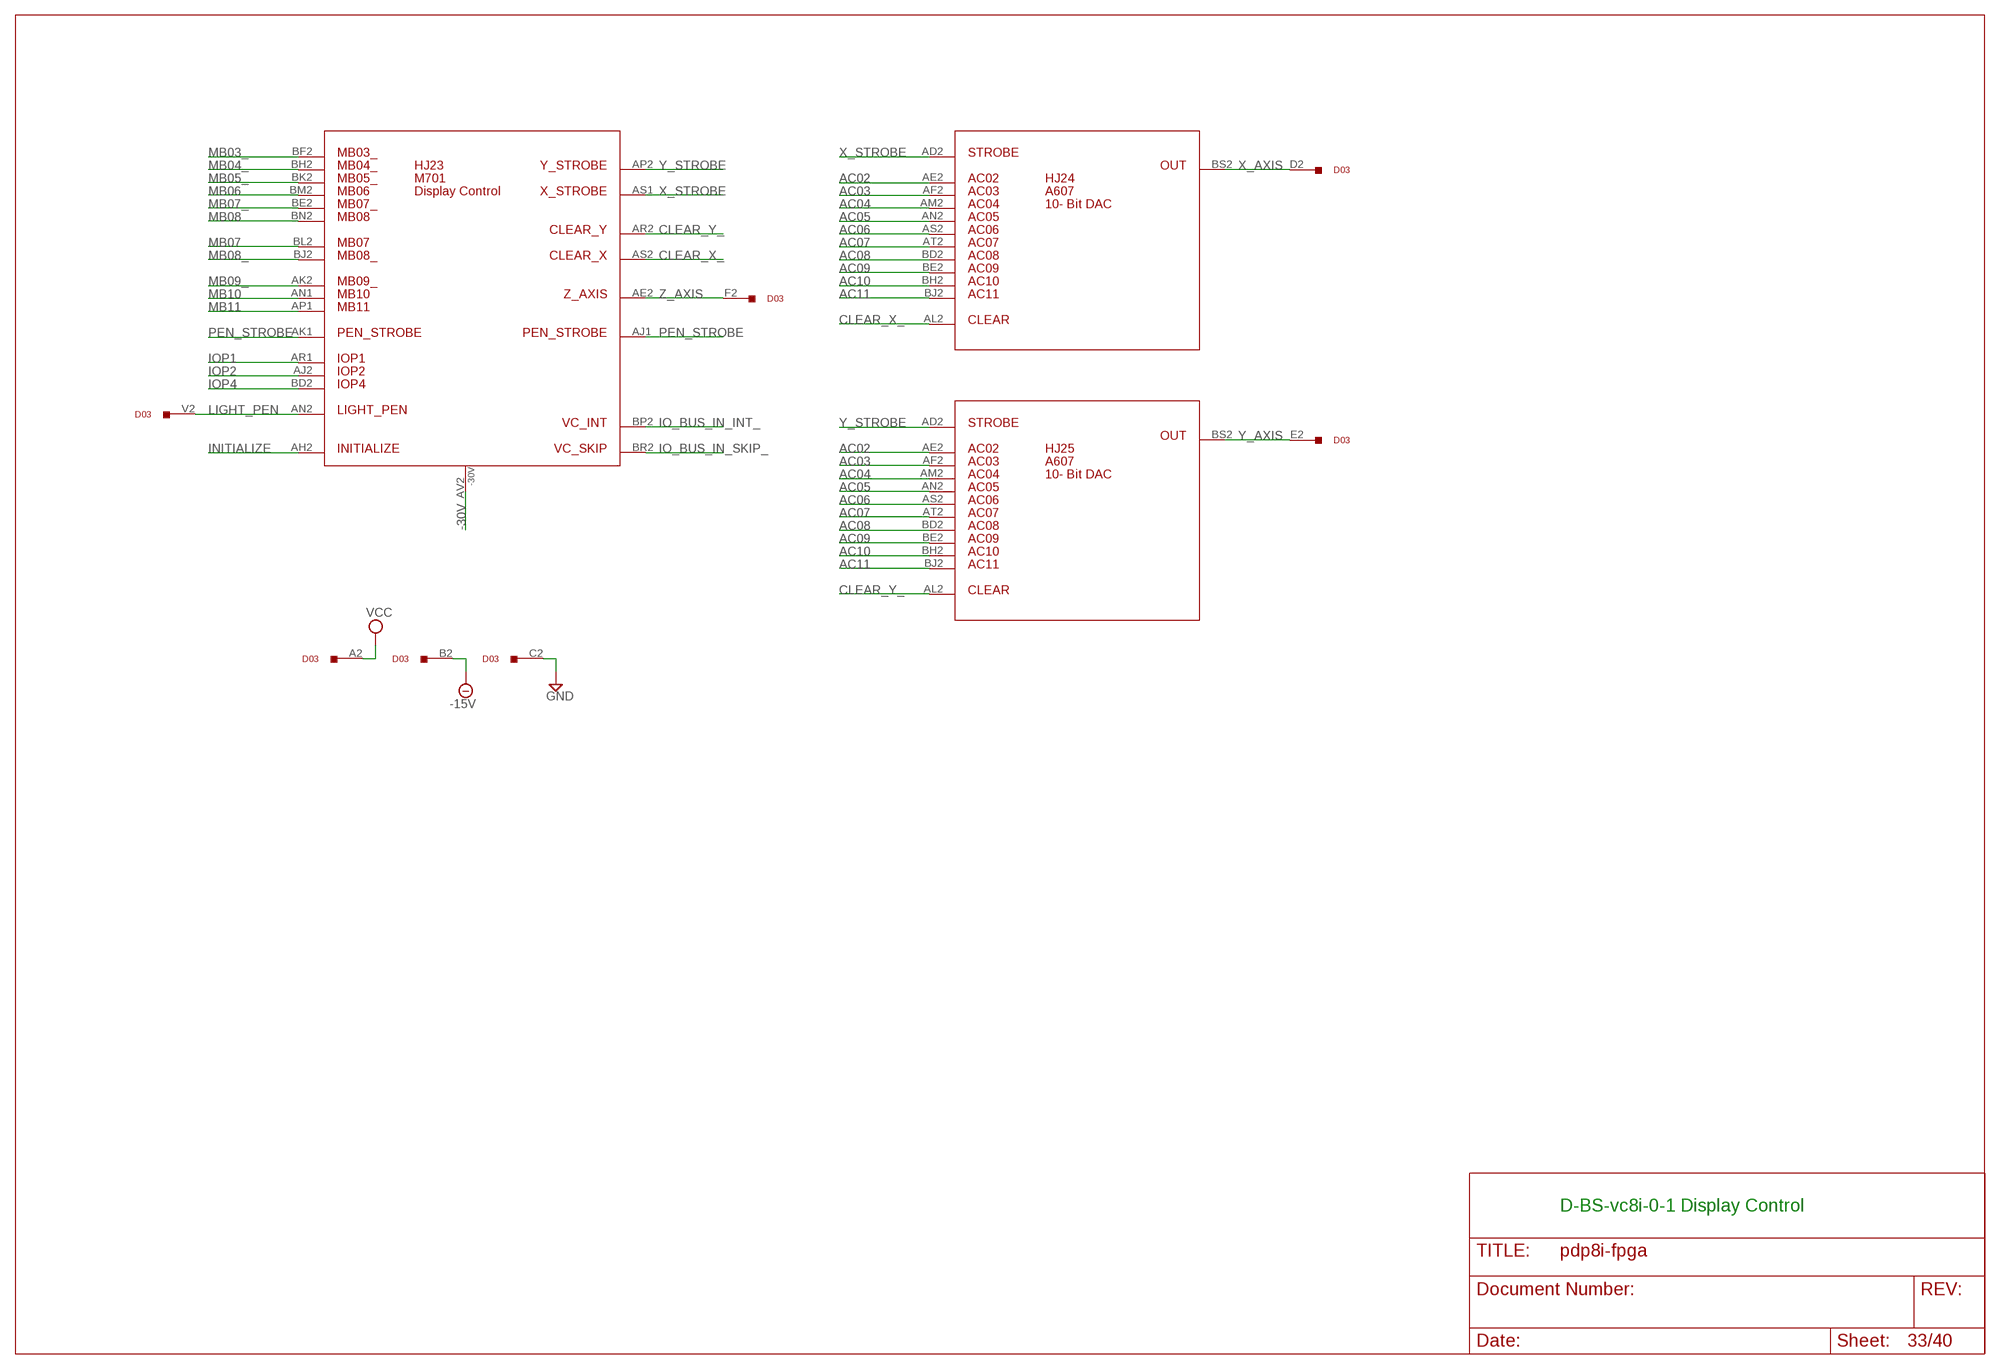
[diagram p33: schematic, sheet 33]
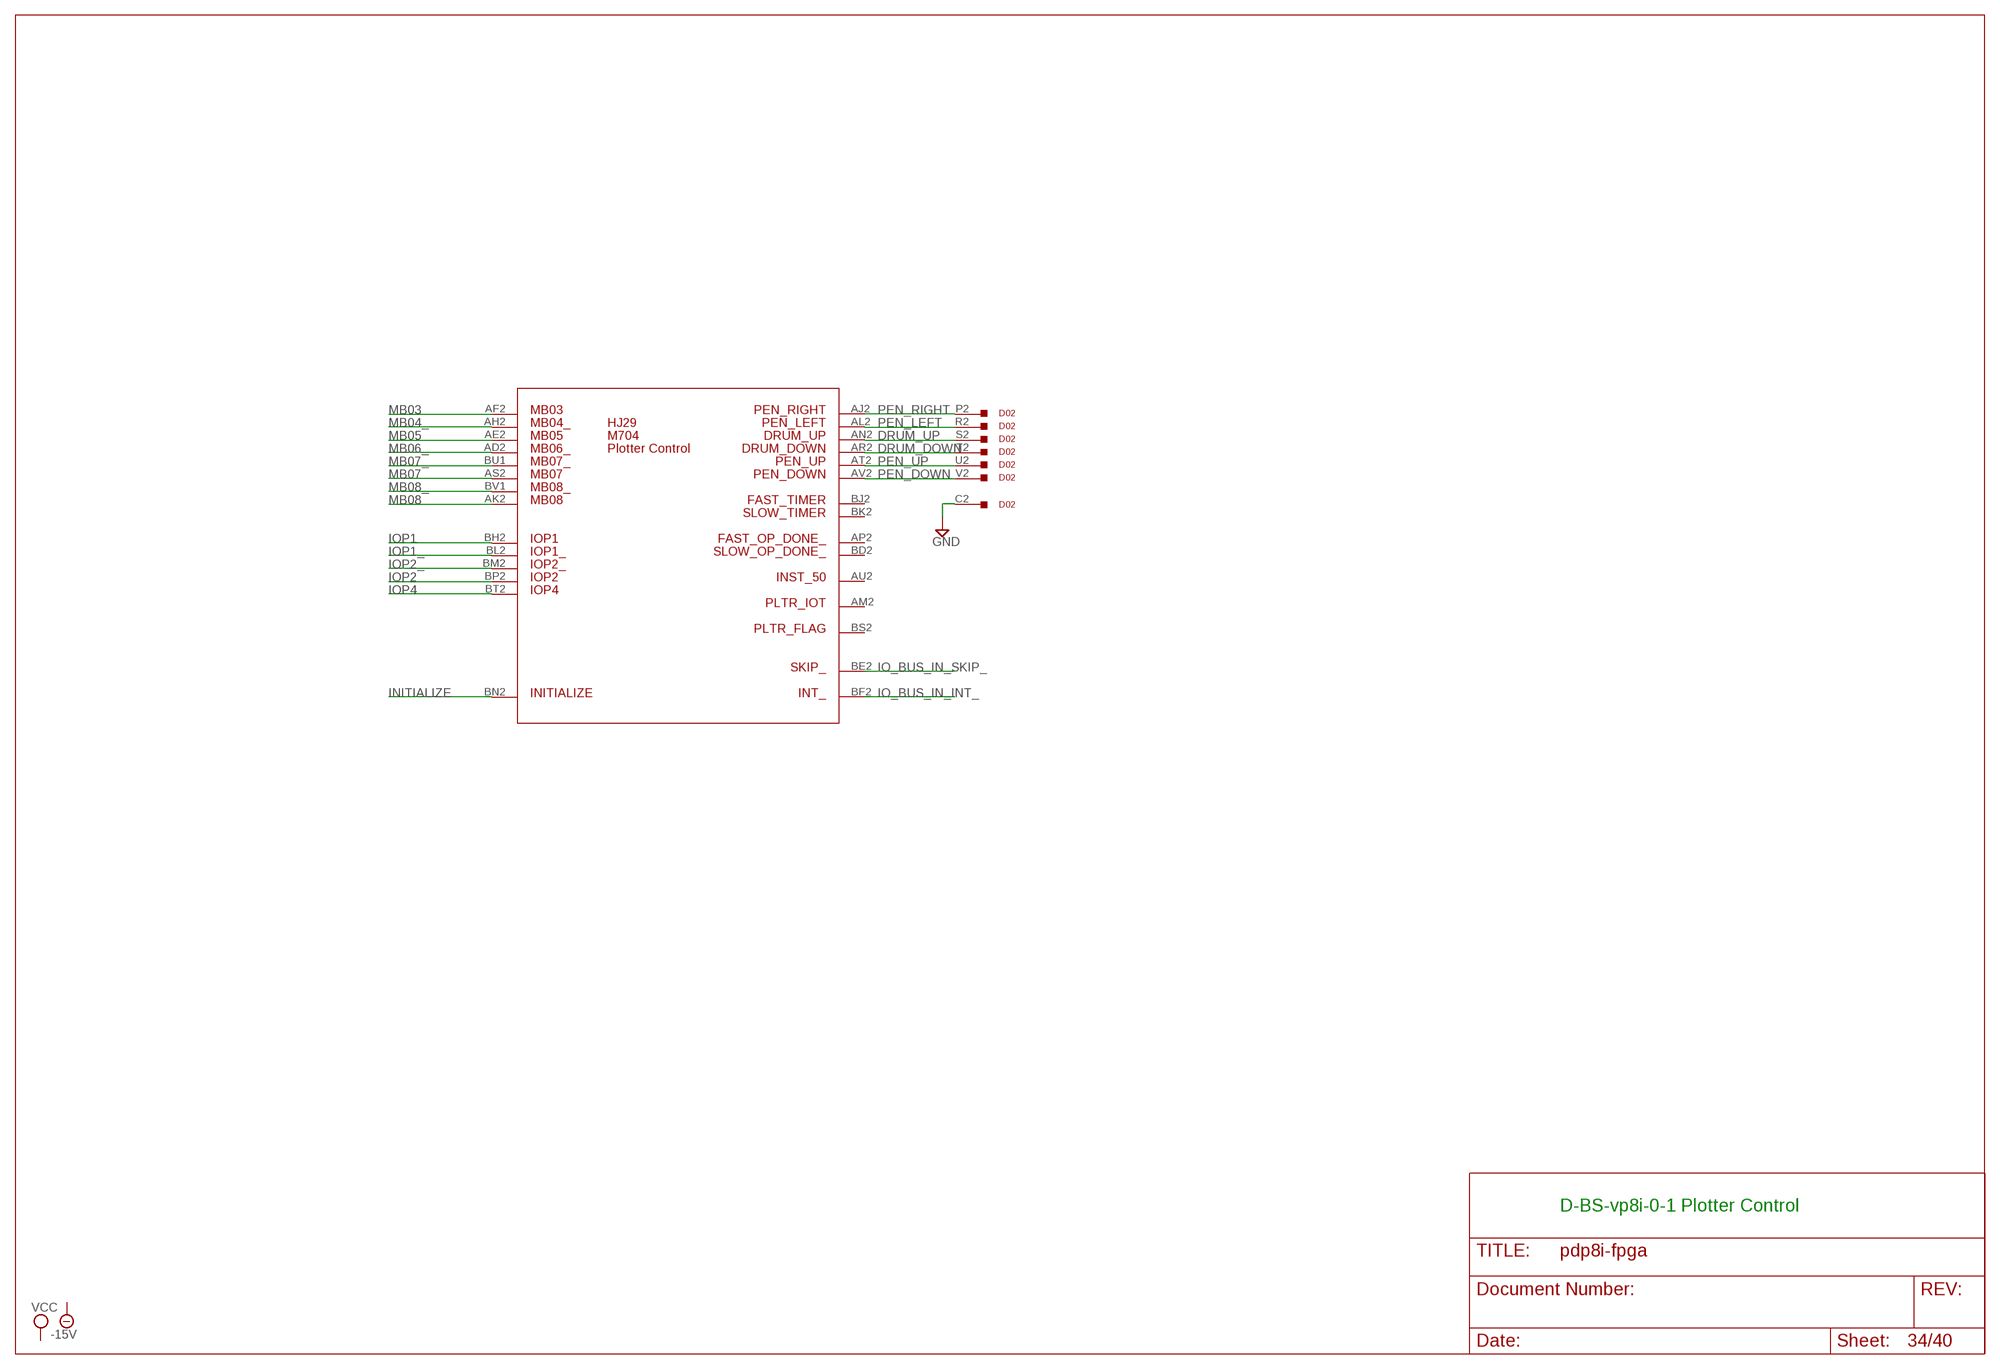
[diagram p34: schematic, sheet 34]
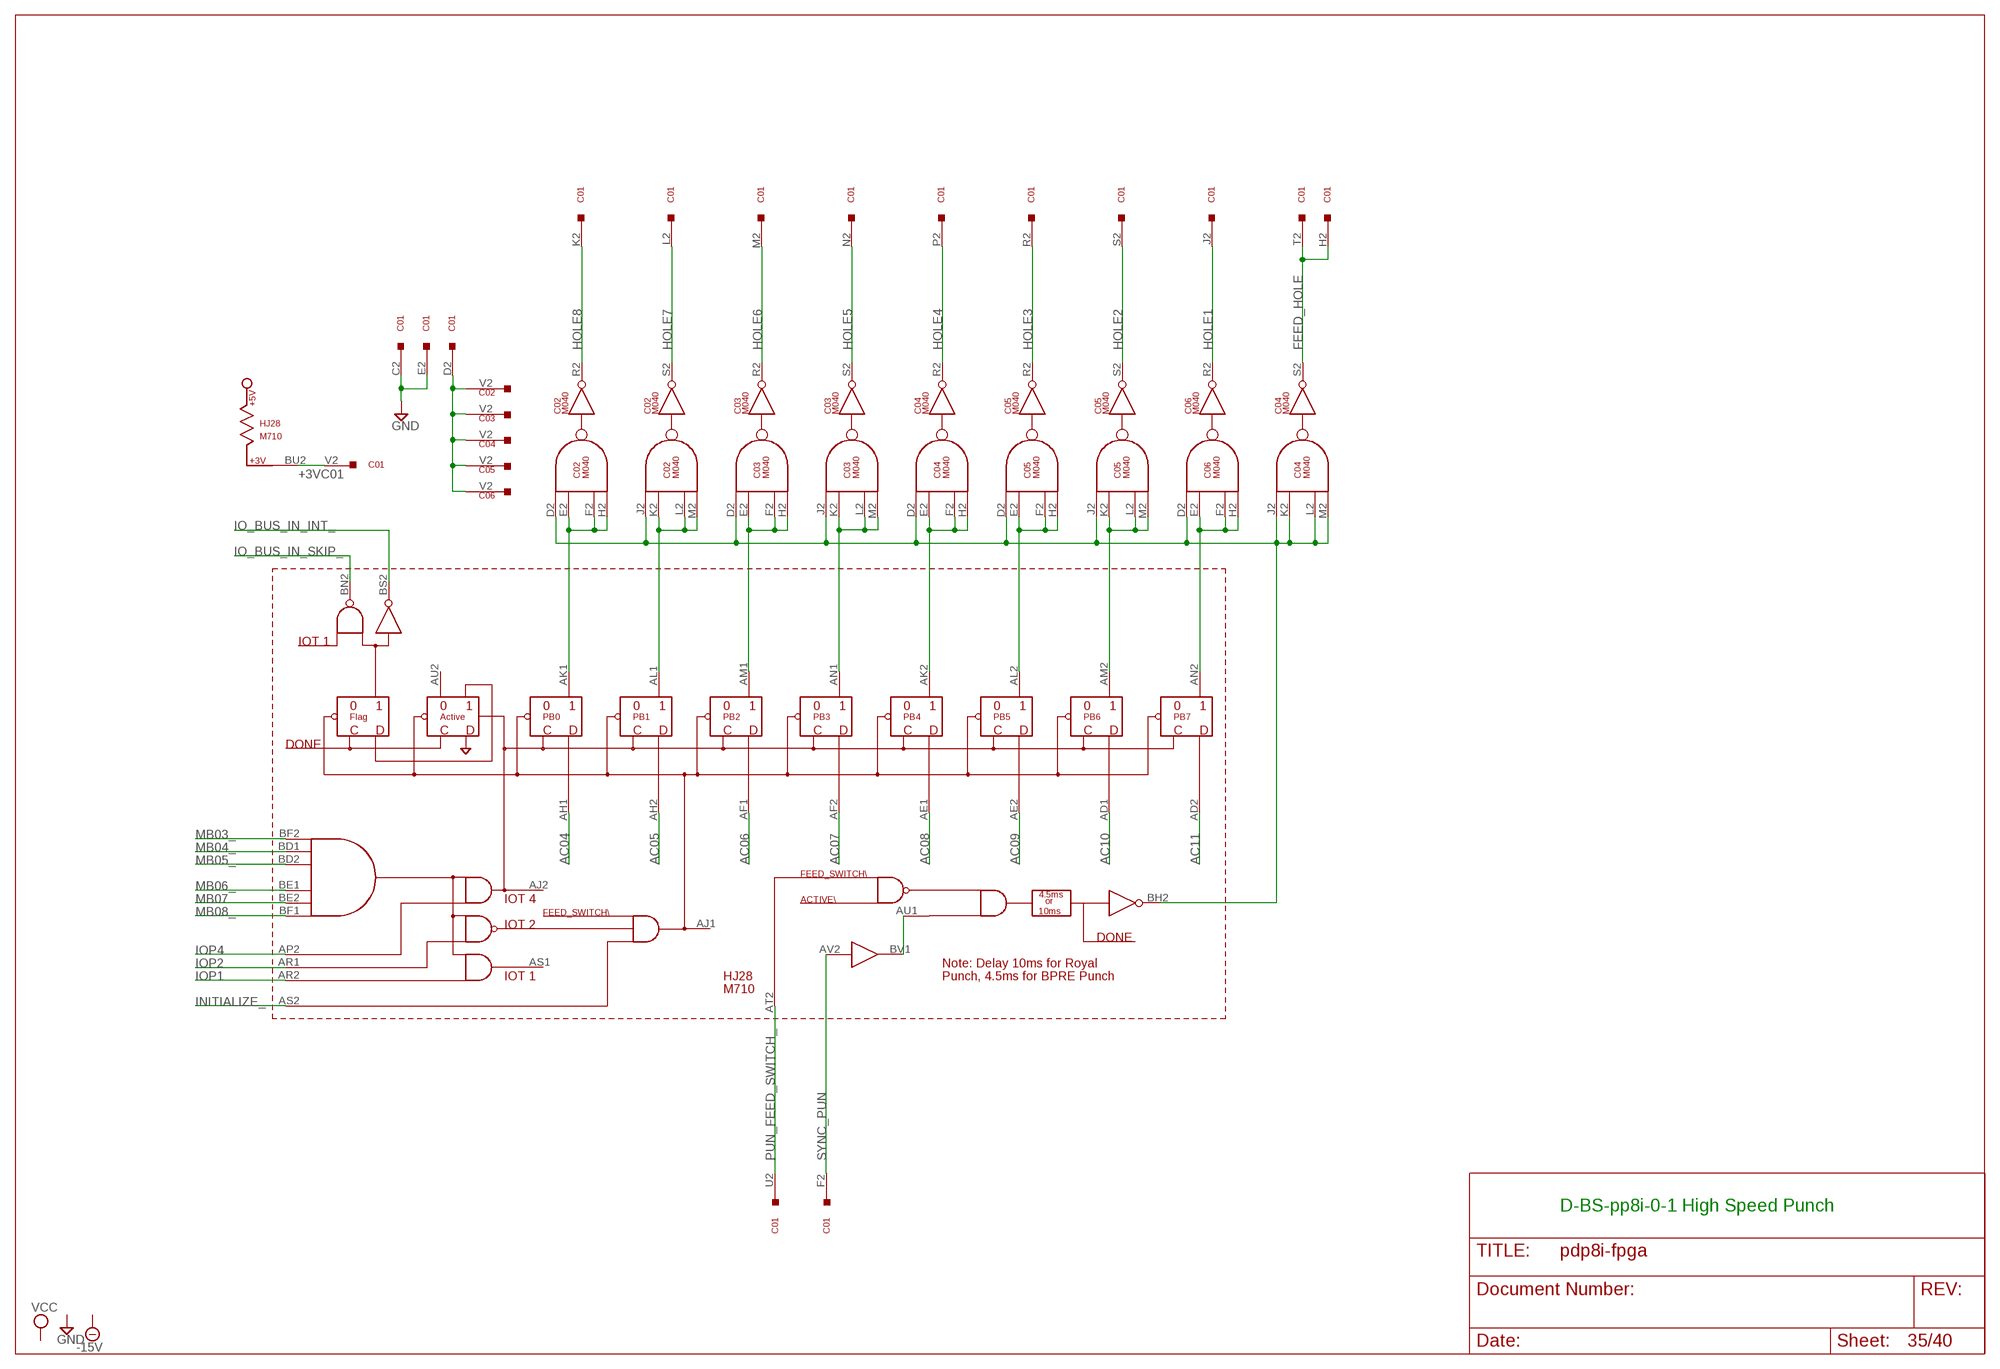
[diagram p35: schematic, sheet 35]
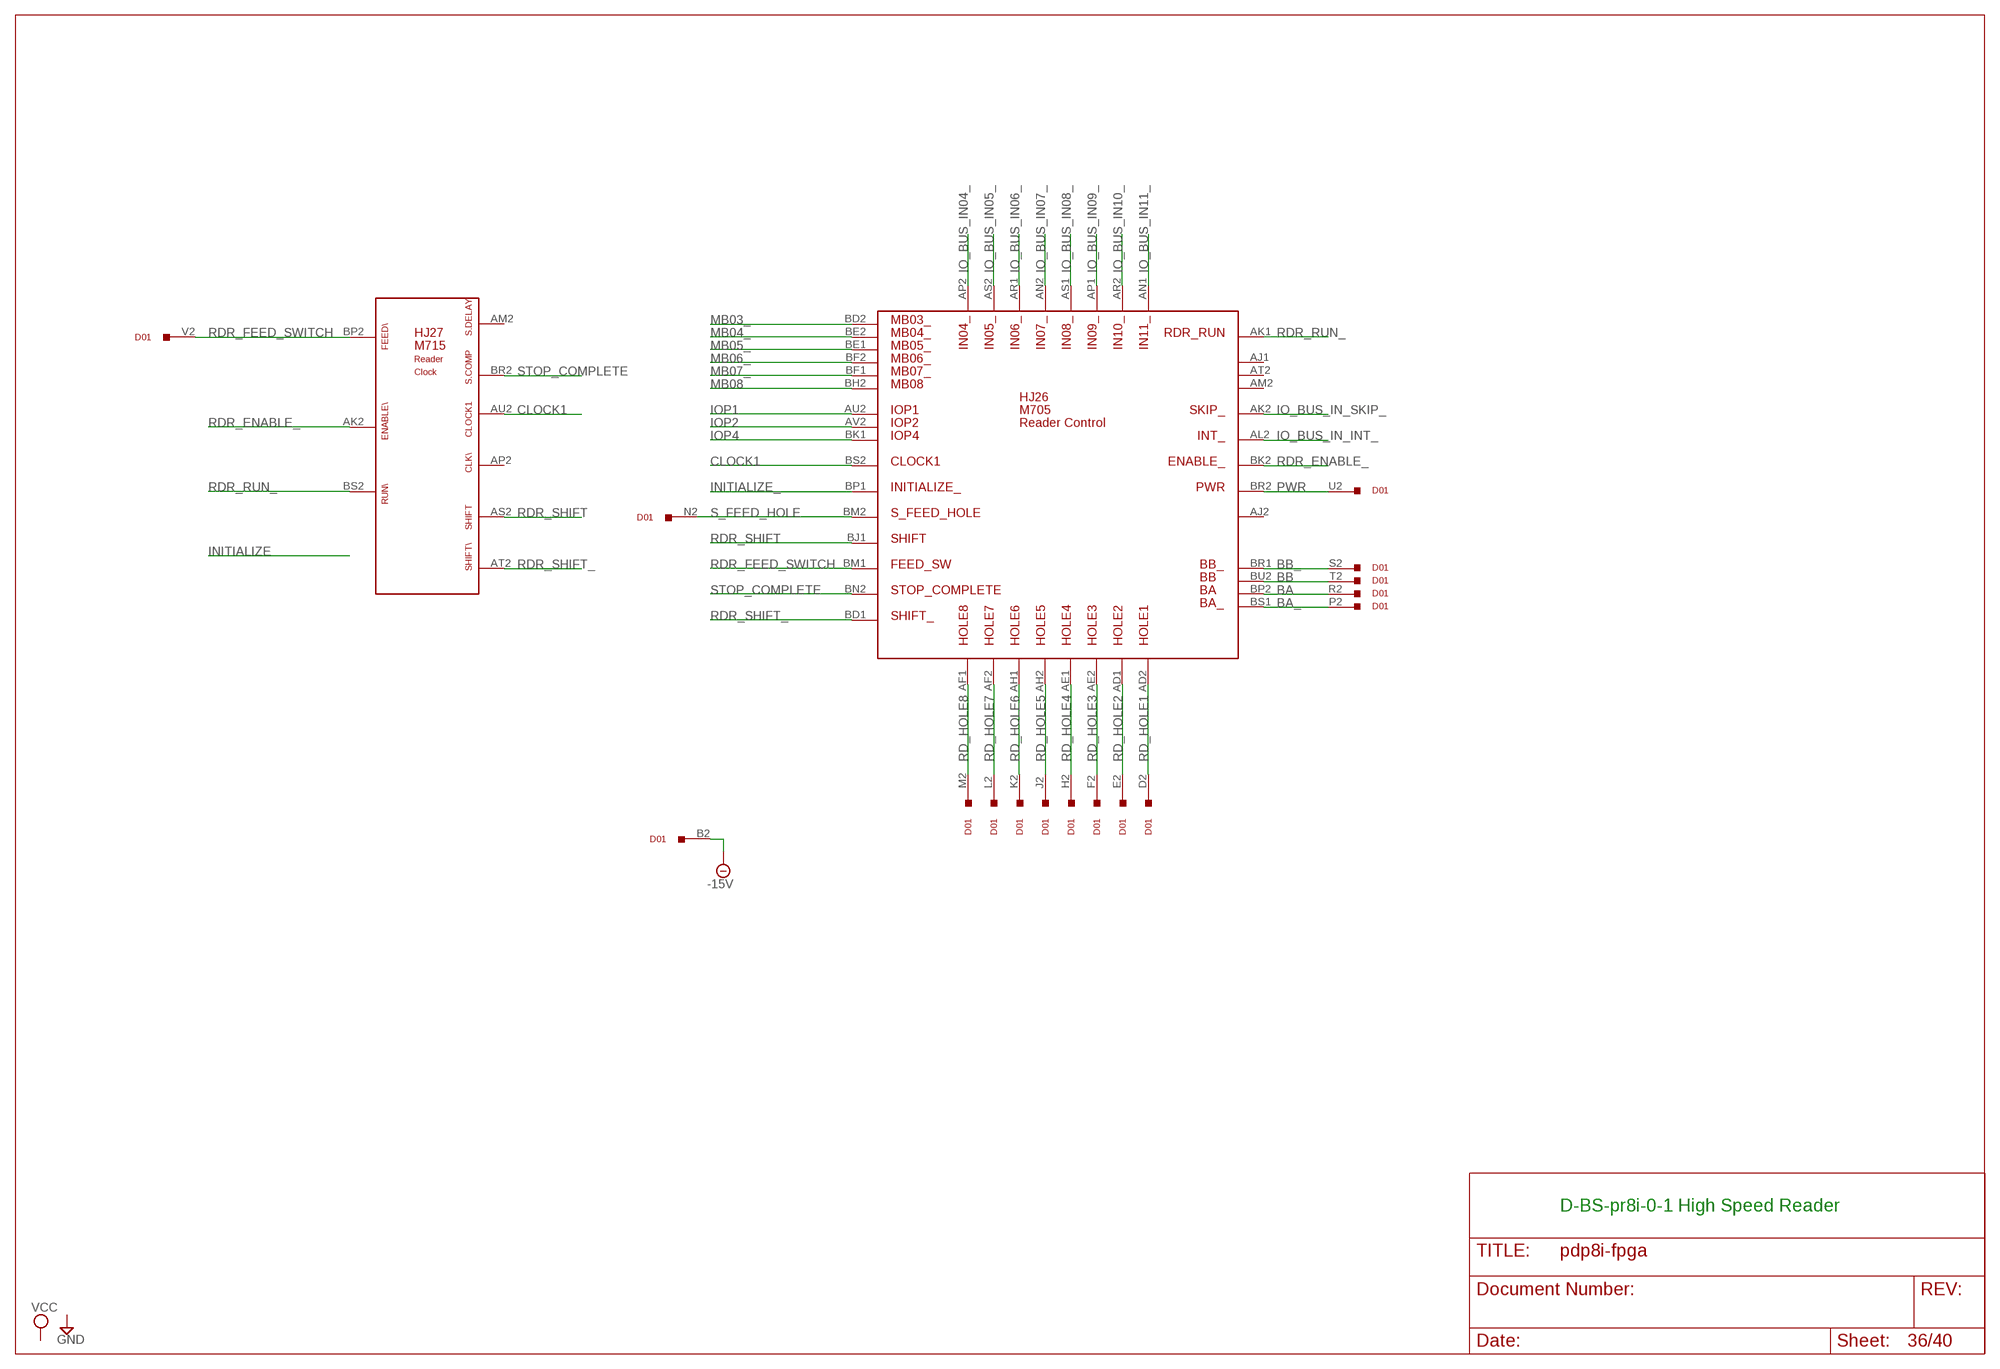
[diagram p36: schematic, sheet 36]
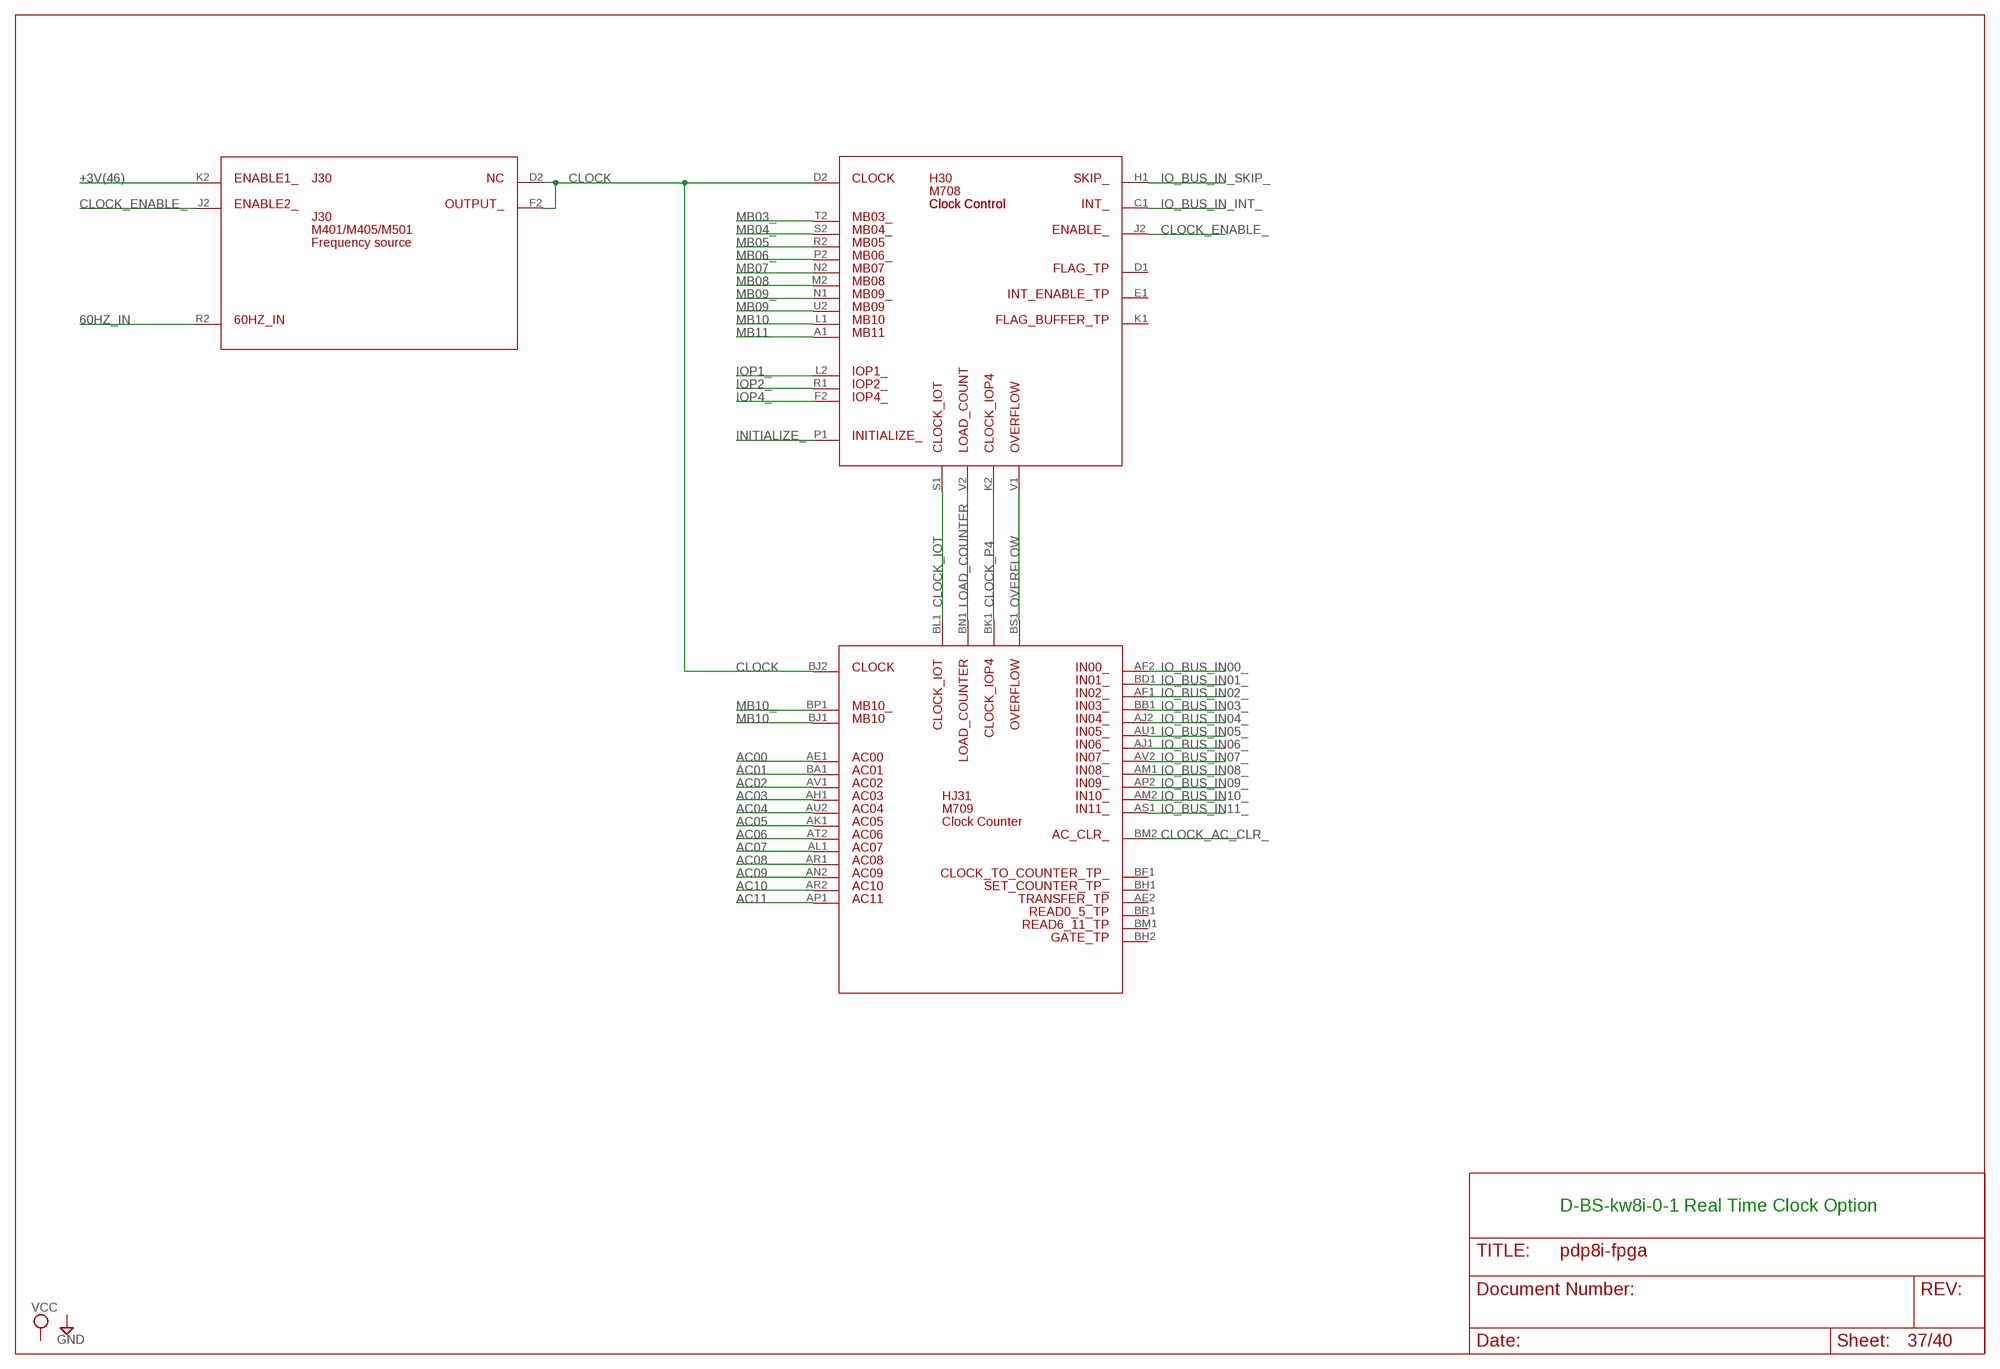
[diagram p37: schematic, sheet 37]
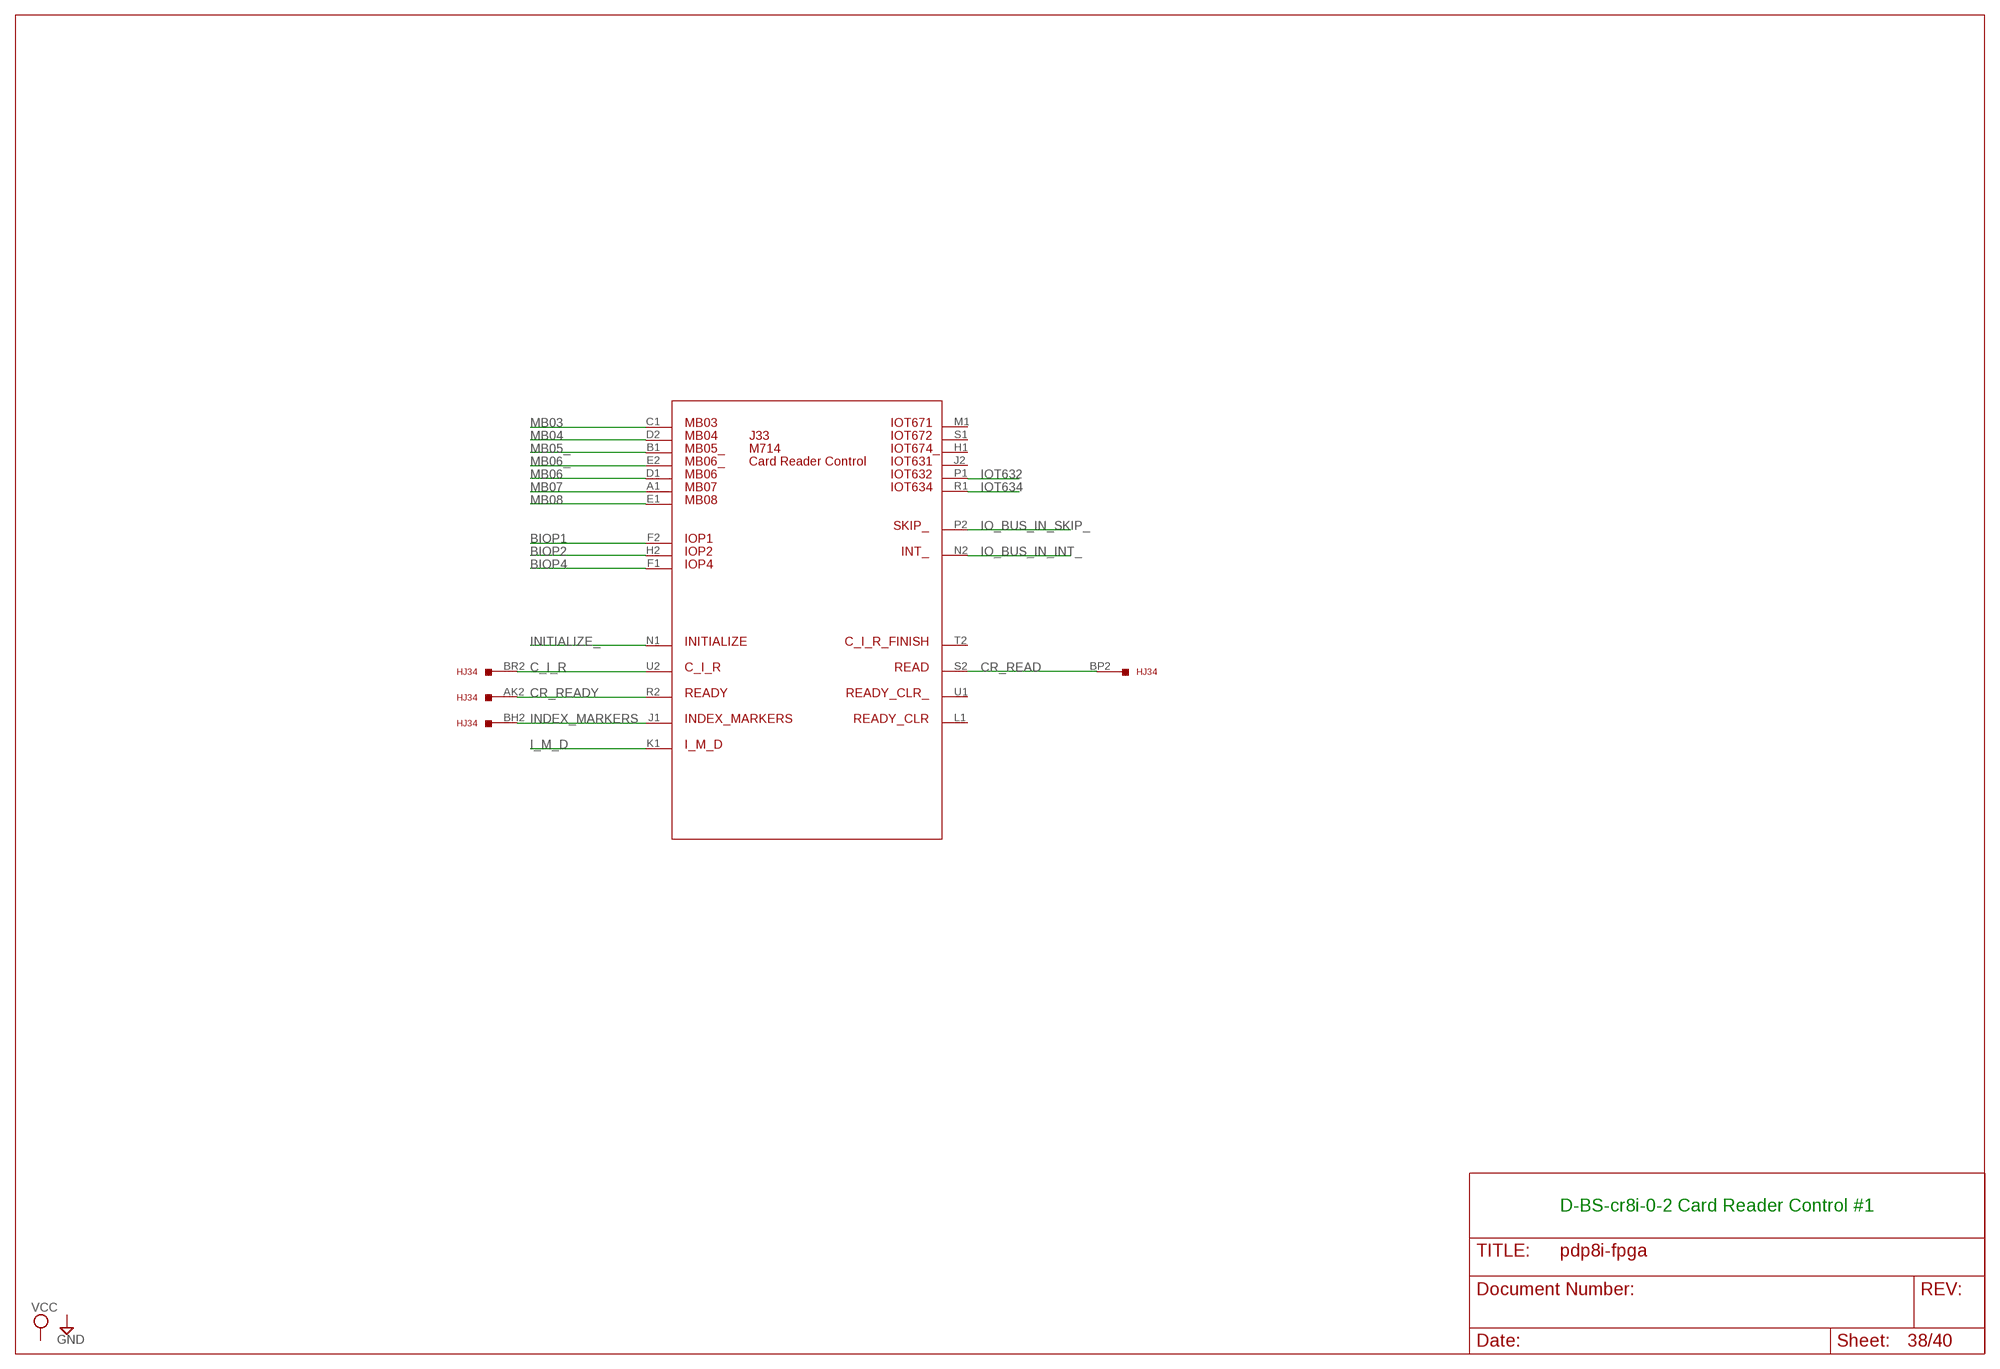
[diagram p38: schematic, sheet 38]
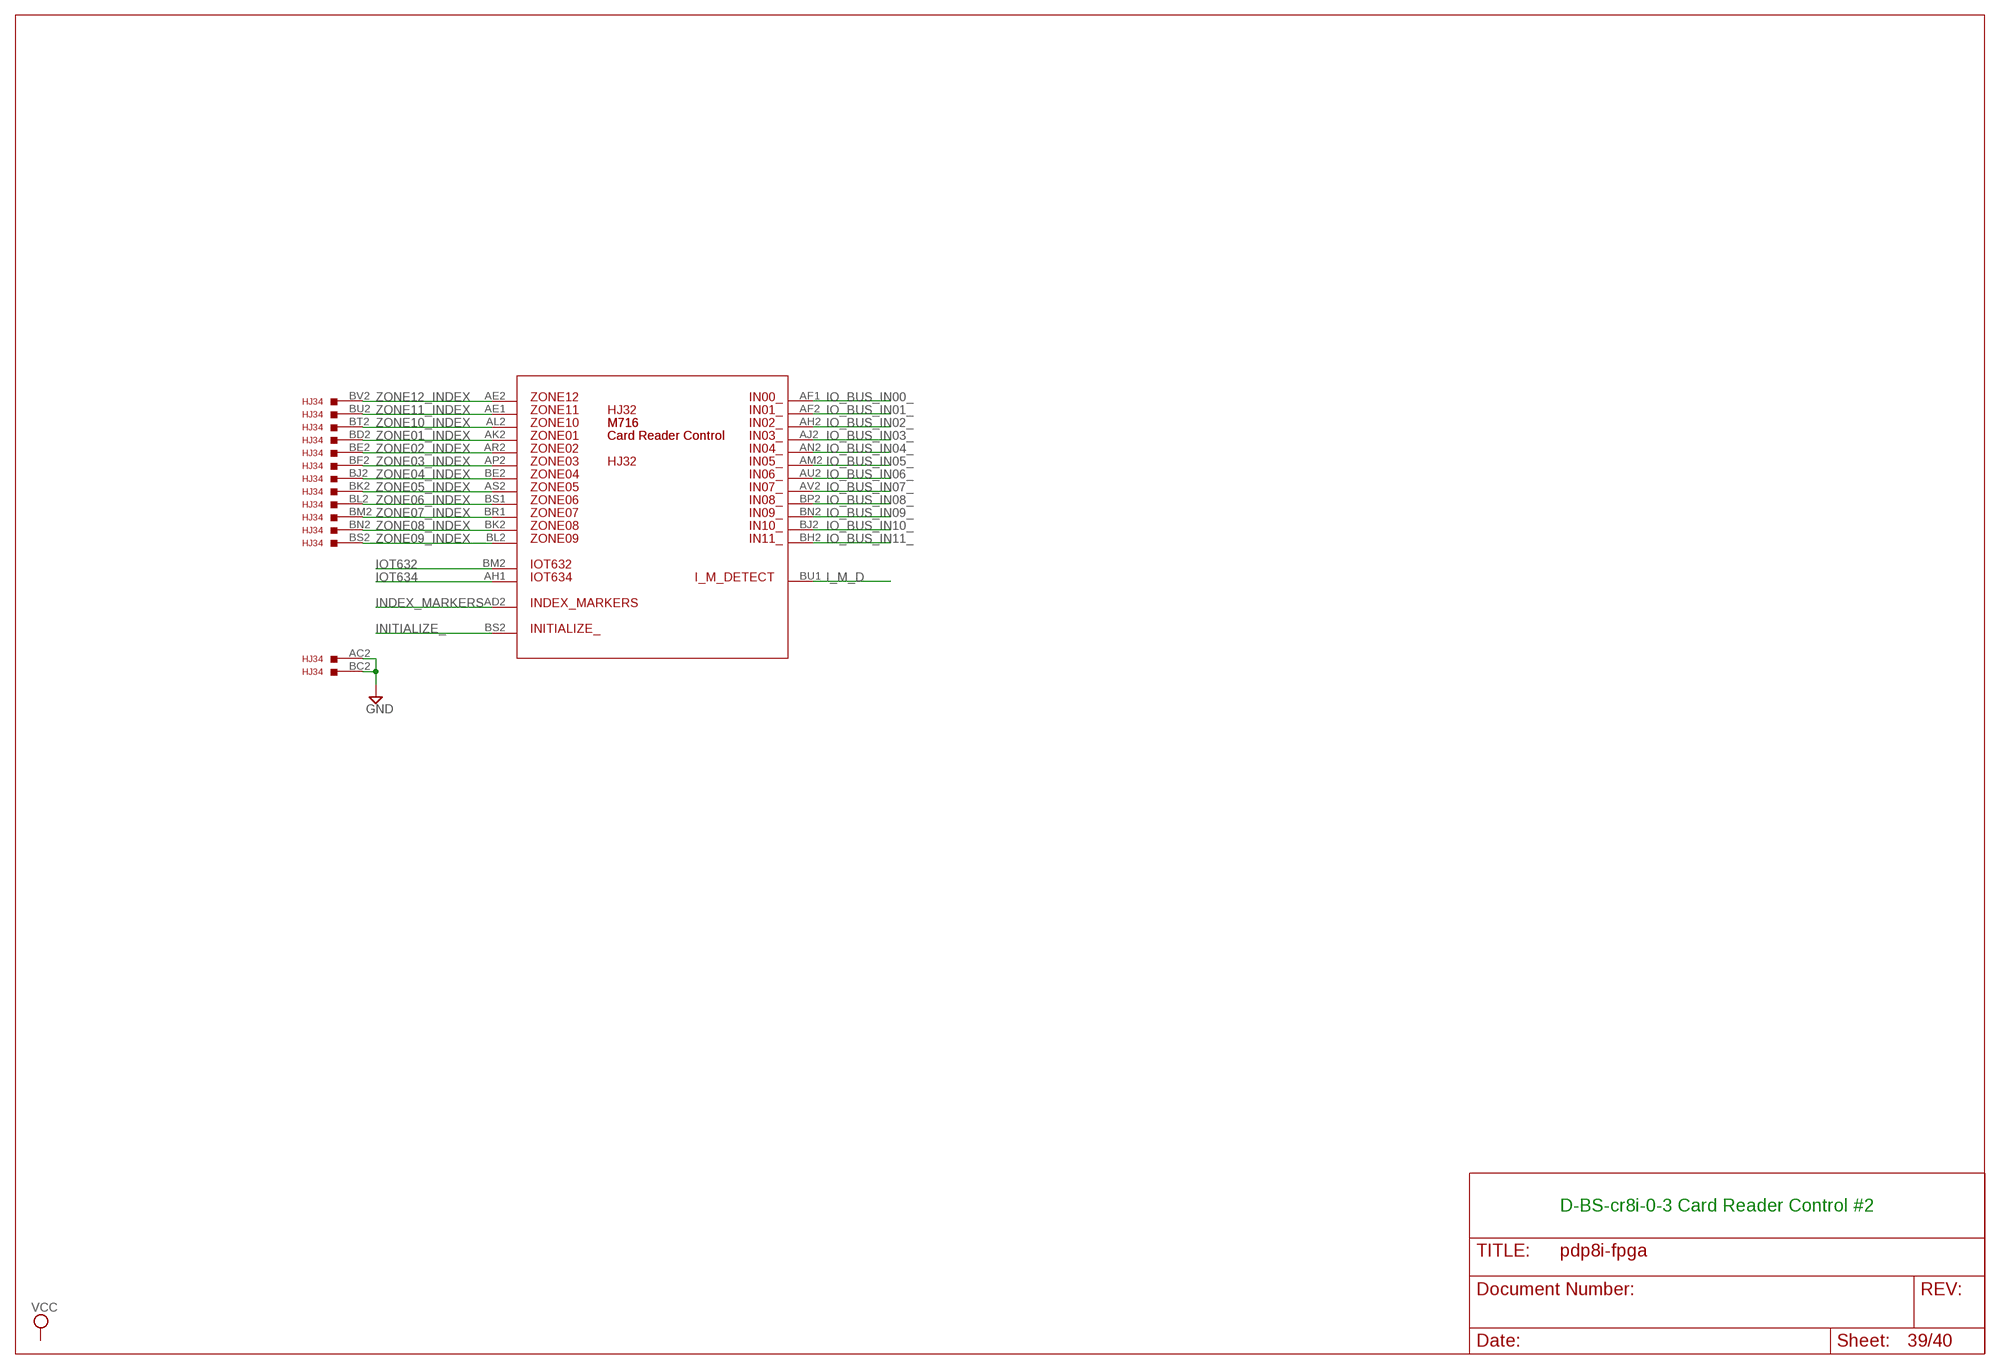
[diagram p39: schematic, sheet 39]
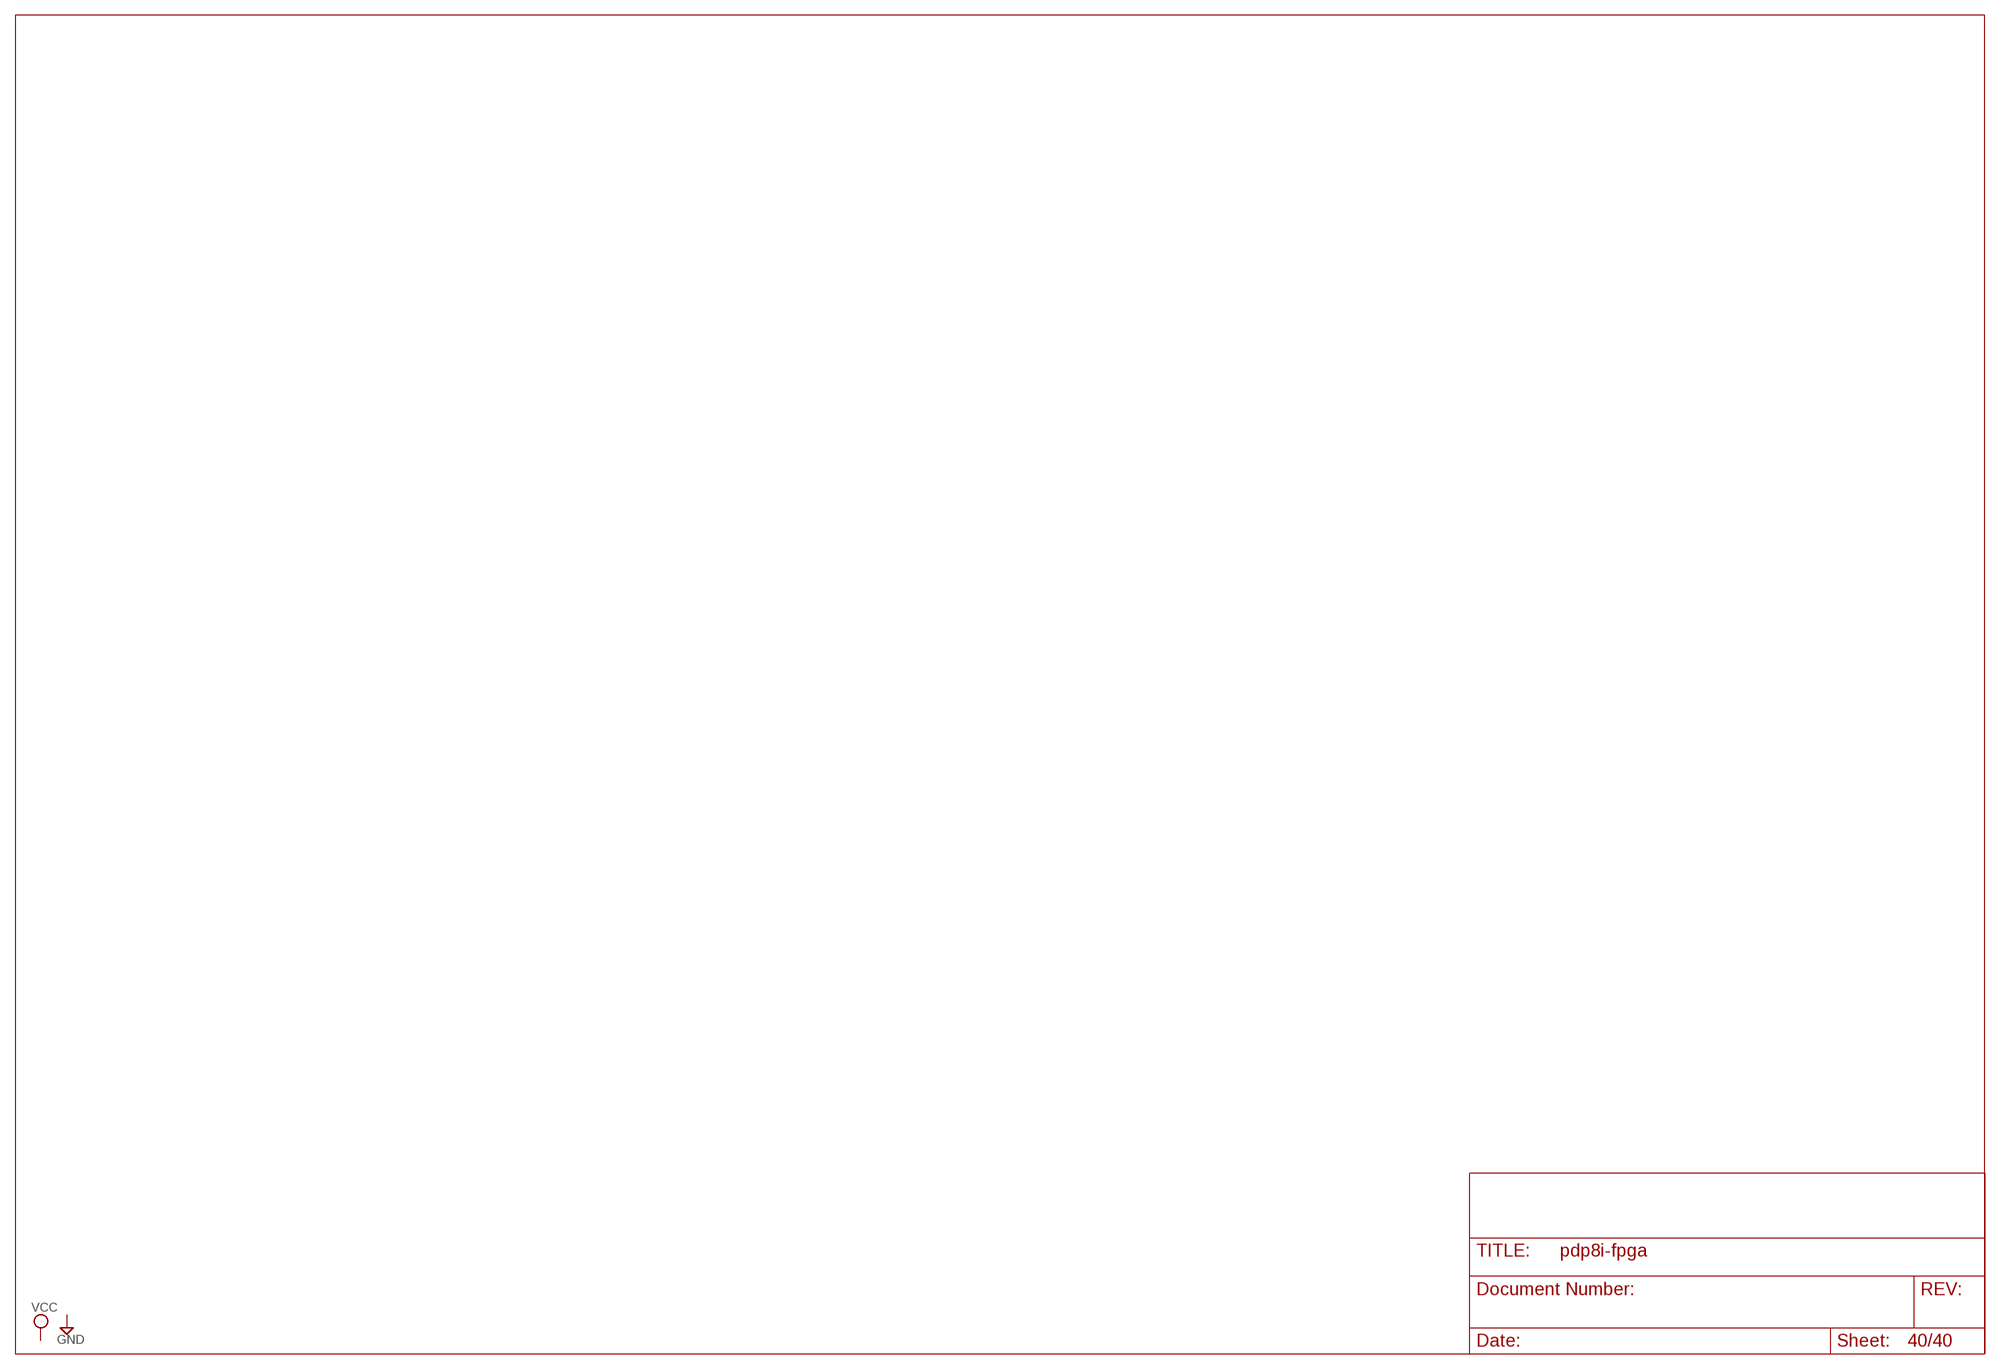
[diagram p40: schematic, sheet 40]

(export (version "E")
  (design (tool "Eeschema 10.0.6"))
  (components
    (comp (ref "C40")
      (value "M900")
      (footprint "eagle-import:H807")
      (libsource (lib "eagle-import") (part "M916"))
    )
    (comp (ref "E33")
      (value "M216")
      (footprint "eagle-import:H807")
      (libsource (lib "eagle-import") (part "M206X"))
    )
    (comp (ref "E40")
      (value "M900")
      (footprint "eagle-import:H807")
      (libsource (lib "eagle-import") (part "M916"))
    )
    (comp (ref "EF34")
      (value "M220")
      (footprint "eagle-import:H807-2")
      (libsource (lib "eagle-import") (part "M220"))
    )
    (comp (ref "EF35")
      (value "M220")
      (footprint "eagle-import:H807-2")
      (libsource (lib "eagle-import") (part "M220"))
    )
    (comp (ref "EF36")
      (value "M220")
      (footprint "eagle-import:H807-2")
      (libsource (lib "eagle-import") (part "M220"))
    )
    (comp (ref "EF37")
      (value "M220")
      (footprint "eagle-import:H807-2")
      (libsource (lib "eagle-import") (part "M220"))
    )
    (comp (ref "EF38")
      (value "M220")
      (footprint "eagle-import:H807-2")
      (libsource (lib "eagle-import") (part "M220"))
    )
    (comp (ref "EF39")
      (value "M220")
      (footprint "eagle-import:H807-2")
      (libsource (lib "eagle-import") (part "M220"))
    )
    (comp (ref "F28")
      (value "M115")
      (footprint "eagle-import:H807")
      (libsource (lib "eagle-import") (part "M115"))
    )
    (comp (ref "F32")
      (value "M113")
      (footprint "eagle-import:H807")
      (libsource (lib "eagle-import") (part "M113"))
    )
    (comp (ref "F33")
      (value "M160")
      (footprint "eagle-import:H807")
      (libsource (lib "eagle-import") (part "M160"))
    )
    (comp (ref "F40")
      (value "M900")
      (footprint "eagle-import:H807")
      (libsource (lib "eagle-import") (part "M916"))
    )
    (comp (ref "A06")
      (value "M113")
      (footprint "eagle-import:H807")
      (libsource (lib "eagle-import") (part "M113"))
    )
    (comp (ref "D40")
      (value "M900")
      (footprint "eagle-import:H807")
      (libsource (lib "eagle-import") (part "M916"))
    )
    (comp (ref "E20")
      (value "M216")
      (footprint "eagle-import:H807")
      (libsource (lib "eagle-import") (part "M206X"))
    )
    (comp (ref "E21")
      (value "M115")
      (footprint "eagle-import:H807")
      (libsource (lib "eagle-import") (part "M115"))
    )
    (comp (ref "E22")
      (value "M113")
      (footprint "eagle-import:H807")
      (libsource (lib "eagle-import") (part "M113"))
    )
    (comp (ref "E23")
      (value "M216")
      (footprint "eagle-import:H807")
      (libsource (lib "eagle-import") (part "M206X"))
    )
    (comp (ref "E24")
      (value "M113")
      (footprint "eagle-import:H807")
      (libsource (lib "eagle-import") (part "M113"))
    )
    (comp (ref "E25")
      (value "M115")
      (footprint "eagle-import:H807")
      (libsource (lib "eagle-import") (part "M115"))
    )
    (comp (ref "F11")
      (value "M117")
      (footprint "eagle-import:H807")
      (libsource (lib "eagle-import") (part "M117"))
    )
    (comp (ref "F22")
      (value "M113")
      (footprint "eagle-import:H807")
      (libsource (lib "eagle-import") (part "M113"))
    )
    (comp (ref "F23")
      (value "M117")
      (footprint "eagle-import:H807")
      (libsource (lib "eagle-import") (part "M117"))
    )
    (comp (ref "F31")
      (value "M617")
      (footprint "eagle-import:H807")
      (libsource (lib "eagle-import") (part "M617"))
    )
    (comp (ref "A11")
      (value "M113")
      (footprint "eagle-import:H807")
      (libsource (lib "eagle-import") (part "M113"))
    )
    (comp (ref "A12")
      (value "M113")
      (footprint "eagle-import:H807")
      (libsource (lib "eagle-import") (part "M113"))
    )
    (comp (ref "A13")
      (value "M113")
      (footprint "eagle-import:H807")
      (libsource (lib "eagle-import") (part "M113"))
    )
    (comp (ref "A14")
      (value "M113")
      (footprint "eagle-import:H807")
      (libsource (lib "eagle-import") (part "M113"))
    )
    (comp (ref "A15")
      (value "M113")
      (footprint "eagle-import:H807")
      (libsource (lib "eagle-import") (part "M113"))
    )
    (comp (ref "A16")
      (value "M113")
      (footprint "eagle-import:H807")
      (libsource (lib "eagle-import") (part "M113"))
    )
    (comp (ref "A17")
      (value "M113")
      (footprint "eagle-import:H807")
      (libsource (lib "eagle-import") (part "M113"))
    )
    (comp (ref "A18")
      (value "M113")
      (footprint "eagle-import:H807")
      (libsource (lib "eagle-import") (part "M113"))
    )
    (comp (ref "A19")
      (value "M113")
      (footprint "eagle-import:H807")
      (libsource (lib "eagle-import") (part "M113"))
    )
    (comp (ref "A20")
      (value "M115")
      (footprint "eagle-import:H807")
      (libsource (lib "eagle-import") (part "M115"))
    )
    (comp (ref "A40")
      (value "W077")
      (footprint "eagle-import:H807")
      (libsource (lib "eagle-import") (part "M916"))
    )
    (comp (ref "B11")
      (value "M216")
      (footprint "eagle-import:H807")
      (libsource (lib "eagle-import") (part "M216"))
    )
    (comp (ref "B16")
      (value "M617")
      (footprint "eagle-import:H807")
      (libsource (lib "eagle-import") (part "M617"))
    )
    (comp (ref "B17")
      (value "M216")
      (footprint "eagle-import:H807")
      (libsource (lib "eagle-import") (part "M216"))
    )
    (comp (ref "B18")
      (value "M216")
      (footprint "eagle-import:H807")
      (libsource (lib "eagle-import") (part "M216"))
    )
    (comp (ref "B20")
      (value "M115")
      (footprint "eagle-import:H807")
      (libsource (lib "eagle-import") (part "M115"))
    )
    (comp (ref "C12")
      (value "M617")
      (footprint "eagle-import:H807")
      (libsource (lib "eagle-import") (part "M617"))
    )
    (comp (ref "F09")
      (value "M119")
      (footprint "eagle-import:H807")
      (libsource (lib "eagle-import") (part "M119"))
    )
    (comp (ref "D02")
      (value "W023")
      (footprint "eagle-import:H807")
      (libsource (lib "eagle-import") (part "W023"))
    )
    (comp (ref "HJ29")
      (value "M704")
      (footprint "eagle-import:H807-2")
      (libsource (lib "eagle-import") (part "M704"))
    )
    (comp (ref "A09")
      (value "M162")
      (footprint "eagle-import:H807")
      (libsource (lib "eagle-import") (part "M162"))
    )
    (comp (ref "A10")
      (value "M162")
      (footprint "eagle-import:H807")
      (libsource (lib "eagle-import") (part "M162"))
    )
    (comp (ref "B07")
      (value "M115")
      (footprint "eagle-import:H807")
      (libsource (lib "eagle-import") (part "M115"))
    )
    (comp (ref "B09")
      (value "M113")
      (footprint "eagle-import:H807")
      (libsource (lib "eagle-import") (part "M113"))
    )
    (comp (ref "H05")
      (value "W011")
      (footprint "eagle-import:H807")
      (libsource (lib "eagle-import") (part "W011"))
    )
    (comp (ref "A04")
      (value "M703")
      (footprint "eagle-import:H807")
      (libsource (lib "eagle-import") (part "M703"))
    )
    (comp (ref "H07")
      (value "M650")
      (footprint "eagle-import:H807")
      (libsource (lib "eagle-import") (part "M650"))
    )
    (comp (ref "H08")
      (value "M650")
      (footprint "eagle-import:H807")
      (libsource (lib "eagle-import") (part "M650"))
    )
    (comp (ref "H09")
      (value "M650")
      (footprint "eagle-import:H807")
      (libsource (lib "eagle-import") (part "M650"))
    )
    (comp (ref "H10")
      (value "M650")
      (footprint "eagle-import:H807")
      (libsource (lib "eagle-import") (part "M650"))
    )
    (comp (ref "H11")
      (value "M650")
      (footprint "eagle-import:H807")
      (libsource (lib "eagle-import") (part "M650"))
    )
    (comp (ref "H12")
      (value "M650")
      (footprint "eagle-import:H807")
      (libsource (lib "eagle-import") (part "M650"))
    )
    (comp (ref "H13")
      (value "M650")
      (footprint "eagle-import:H807")
      (libsource (lib "eagle-import") (part "M650"))
    )
    (comp (ref "H14")
      (value "M650")
      (footprint "eagle-import:H807")
      (libsource (lib "eagle-import") (part "M650"))
    )
    (comp (ref "H15")
      (value "M650")
      (footprint "eagle-import:H807")
      (libsource (lib "eagle-import") (part "M650"))
    )
    (comp (ref "H16")
      (value "M650")
      (footprint "eagle-import:H807")
      (libsource (lib "eagle-import") (part "M650"))
    )
    (comp (ref "H17")
      (value "M650")
      (footprint "eagle-import:H807")
      (libsource (lib "eagle-import") (part "M650"))
    )
    (comp (ref "H18")
      (value "M650")
      (footprint "eagle-import:H807")
      (libsource (lib "eagle-import") (part "M650"))
    )
    (comp (ref "H19")
      (value "M650")
      (footprint "eagle-import:H807")
      (libsource (lib "eagle-import") (part "M650"))
    )
    (comp (ref "H20")
      (value "M650")
      (footprint "eagle-import:H807")
      (libsource (lib "eagle-import") (part "M650"))
    )
    (comp (ref "J01")
      (value "W011")
      (footprint "eagle-import:H807")
      (libsource (lib "eagle-import") (part "W011"))
    )
    (comp (ref "J02")
      (value "W011")
      (footprint "eagle-import:H807")
      (libsource (lib "eagle-import") (part "W011"))
    )
    (comp (ref "J03")
      (value "W011")
      (footprint "eagle-import:H807")
      (libsource (lib "eagle-import") (part "W011"))
    )
    (comp (ref "J04")
      (value "W011")
      (footprint "eagle-import:H807")
      (libsource (lib "eagle-import") (part "W011"))
    )
    (comp (ref "J05")
      (value "W011")
      (footprint "eagle-import:H807")
      (libsource (lib "eagle-import") (part "W011"))
    )
    (comp (ref "J06")
      (value "W011")
      (footprint "eagle-import:H807")
      (libsource (lib "eagle-import") (part "W011"))
    )
    (comp (ref "J07")
      (value "W011")
      (footprint "eagle-import:H807")
      (libsource (lib "eagle-import") (part "W011"))
    )
    (comp (ref "J08")
      (value "W011")
      (footprint "eagle-import:H807")
      (libsource (lib "eagle-import") (part "W011"))
    )
    (comp (ref "J09")
      (value "W011")
      (footprint "eagle-import:H807")
      (libsource (lib "eagle-import") (part "W011"))
    )
    (comp (ref "J10")
      (value "W011")
      (footprint "eagle-import:H807")
      (libsource (lib "eagle-import") (part "W011"))
    )
    (comp (ref "J11")
      (value "W011")
      (footprint "eagle-import:H807")
      (libsource (lib "eagle-import") (part "W011"))
    )
    (comp (ref "J13")
      (value "M506")
      (footprint "eagle-import:H807")
      (libsource (lib "eagle-import") (part "M506"))
    )
    (comp (ref "J14")
      (value "M506")
      (footprint "eagle-import:H807")
      (libsource (lib "eagle-import") (part "M506"))
    )
    (comp (ref "J15")
      (value "M506")
      (footprint "eagle-import:H807")
      (libsource (lib "eagle-import") (part "M506"))
    )
    (comp (ref "J16")
      (value "M506")
      (footprint "eagle-import:H807")
      (libsource (lib "eagle-import") (part "M506"))
    )
    (comp (ref "J17")
      (value "M506")
      (footprint "eagle-import:H807")
      (libsource (lib "eagle-import") (part "M506"))
    )
    (comp (ref "J18")
      (value "M506")
      (footprint "eagle-import:H807")
      (libsource (lib "eagle-import") (part "M506"))
    )
    (comp (ref "J19")
      (value "M506")
      (footprint "eagle-import:H807")
      (libsource (lib "eagle-import") (part "M506"))
    )
    (comp (ref "J20")
      (value "M506")
      (footprint "eagle-import:H807")
      (libsource (lib "eagle-import") (part "M506"))
    )
    (comp (ref "C01")
      (value "W023")
      (footprint "eagle-import:H807")
      (libsource (lib "eagle-import") (part "W023"))
    )
    (comp (ref "C02")
      (value "M040")
      (footprint "eagle-import:H807")
      (libsource (lib "eagle-import") (part "M040"))
    )
    (comp (ref "C03")
      (value "M040")
      (footprint "eagle-import:H807")
      (libsource (lib "eagle-import") (part "M040"))
    )
    (comp (ref "C04")
      (value "M040")
      (footprint "eagle-import:H807")
      (libsource (lib "eagle-import") (part "M040"))
    )
    (comp (ref "C05")
      (value "M040")
      (footprint "eagle-import:H807")
      (libsource (lib "eagle-import") (part "M040"))
    )
    (comp (ref "C06")
      (value "M040")
      (footprint "eagle-import:H807")
      (libsource (lib "eagle-import") (part "M040"))
    )
    (comp (ref "HJ28")
      (value "M710")
      (footprint "eagle-import:H807-2")
      (libsource (lib "eagle-import") (part "M710"))
    )
    (comp (ref "EF01")
      (value "M706")
      (footprint "eagle-import:H807-2")
      (libsource (lib "eagle-import") (part "M706"))
    )
    (comp (ref "J12")
      (value "W076")
      (footprint "eagle-import:H807")
      (libsource (lib "eagle-import") (part "W076"))
    )
    (comp (ref "C07")
      (value "M661")
      (footprint "eagle-import:H807")
      (libsource (lib "eagle-import") (part "M661"))
    )
    (comp (ref "C08")
      (value "M660")
      (footprint "eagle-import:H807")
      (libsource (lib "eagle-import") (part "M660"))
    )
    (comp (ref "C09")
      (value "M113")
      (footprint "eagle-import:H807")
      (libsource (lib "eagle-import") (part "M113"))
    )
    (comp (ref "C10")
      (value "M113")
      (footprint "eagle-import:H807")
      (libsource (lib "eagle-import") (part "M113"))
    )
    (comp (ref "C11")
      (value "M115")
      (footprint "eagle-import:H807")
      (libsource (lib "eagle-import") (part "M115"))
    )
    (comp (ref "D04")
      (value "W011")
      (footprint "eagle-import:H807")
      (libsource (lib "eagle-import") (part "W011"))
    )
    (comp (ref "D05")
      (value "M516")
      (footprint "eagle-import:H807")
      (libsource (lib "eagle-import") (part "M516"))
    )
    (comp (ref "D07")
      (value "M113")
      (footprint "eagle-import:H807")
      (libsource (lib "eagle-import") (part "M113"))
    )
    (comp (ref "D09")
      (value "M115")
      (footprint "eagle-import:H807")
      (libsource (lib "eagle-import") (part "M115"))
    )
    (comp (ref "D10")
      (value "M117")
      (footprint "eagle-import:H807")
      (libsource (lib "eagle-import") (part "M117"))
    )
    (comp (ref "D11")
      (value "M216")
      (footprint "eagle-import:H807")
      (libsource (lib "eagle-import") (part "M216"))
    )
    (comp (ref "C13")
      (value "M310")
      (footprint "eagle-import:H807")
      (libsource (lib "eagle-import") (part "M310"))
    )
    (comp (ref "C18")
      (value "M113")
      (footprint "eagle-import:H807")
      (libsource (lib "eagle-import") (part "M113"))
    )
    (comp (ref "C22")
      (value "M216")
      (footprint "eagle-import:H807")
      (libsource (lib "eagle-import") (part "M216"))
    )
    (comp (ref "D12")
      (value "M113")
      (footprint "eagle-import:H807")
      (libsource (lib "eagle-import") (part "M113"))
    )
    (comp (ref "D13")
      (value "M113")
      (footprint "eagle-import:H807")
      (libsource (lib "eagle-import") (part "M113"))
    )
    (comp (ref "D14")
      (value "M113")
      (footprint "eagle-import:H807")
      (libsource (lib "eagle-import") (part "M113"))
    )
    (comp (ref "D15")
      (value "M113")
      (footprint "eagle-import:H807")
      (libsource (lib "eagle-import") (part "M113"))
    )
    (comp (ref "D16")
      (value "M113")
      (footprint "eagle-import:H807")
      (libsource (lib "eagle-import") (part "M113"))
    )
    (comp (ref "D17")
      (value "M115")
      (footprint "eagle-import:H807")
      (libsource (lib "eagle-import") (part "M115"))
    )
    (comp (ref "D18")
      (value "M115")
      (footprint "eagle-import:H807")
      (libsource (lib "eagle-import") (part "M115"))
    )
    (comp (ref "D19")
      (value "M115")
      (footprint "eagle-import:H807")
      (libsource (lib "eagle-import") (part "M115"))
    )
    (comp (ref "D20")
      (value "M117")
      (footprint "eagle-import:H807")
      (libsource (lib "eagle-import") (part "M117"))
    )
    (comp (ref "D21")
      (value "M117")
      (footprint "eagle-import:H807")
      (libsource (lib "eagle-import") (part "M117"))
    )
    (comp (ref "D22")
      (value "M617")
      (footprint "eagle-import:H807")
      (libsource (lib "eagle-import") (part "M617"))
    )
    (comp (ref "D23")
      (value "M160")
      (footprint "eagle-import:H807")
      (libsource (lib "eagle-import") (part "M160"))
    )
    (comp (ref "D24")
      (value "M216")
      (footprint "eagle-import:H807")
      (libsource (lib "eagle-import") (part "M216"))
    )
    (comp (ref "D03")
      (value "W023")
      (footprint "eagle-import:H807")
      (libsource (lib "eagle-import") (part "W023"))
    )
    (comp (ref "HJ23")
      (value "M701")
      (footprint "eagle-import:H807-2")
      (libsource (lib "eagle-import") (part "M701"))
    )
    (comp (ref "HJ24")
      (value "A607")
      (footprint "eagle-import:H807-2")
      (libsource (lib "eagle-import") (part "A607"))
    )
    (comp (ref "HJ25")
      (value "A607")
      (footprint "eagle-import:H807-2")
      (libsource (lib "eagle-import") (part "A607"))
    )
    (comp (ref "HJ32")
      (value "M716")
      (footprint "eagle-import:H807-2")
      (libsource (lib "eagle-import") (part "M716"))
    )
    (comp (ref "HJ34")
      (value "W991")
      (footprint "eagle-import:H807-2")
      (libsource (lib "eagle-import") (part "W991"))
    )
    (comp (ref "D06")
      (value "M310")
      (footprint "eagle-import:H807")
      (libsource (lib "eagle-import") (part "M310"))
    )
    (comp (ref "E09")
      (value "M113")
      (footprint "eagle-import:H807")
      (libsource (lib "eagle-import") (part "M113"))
    )
    (comp (ref "B40")
      (value "W077")
      (footprint "eagle-import:H807")
      (libsource (lib "eagle-import") (part "M916"))
    )
    (comp (ref "E11")
      (value "M113")
      (footprint "eagle-import:H807")
      (libsource (lib "eagle-import") (part "M113"))
    )
    (comp (ref "E12")
      (value "M113")
      (footprint "eagle-import:H807")
      (libsource (lib "eagle-import") (part "M113"))
    )
    (comp (ref "E13")
      (value "M160")
      (footprint "eagle-import:H807")
      (libsource (lib "eagle-import") (part "M160"))
    )
    (comp (ref "E14")
      (value "M115")
      (footprint "eagle-import:H807")
      (libsource (lib "eagle-import") (part "M115"))
    )
    (comp (ref "E15")
      (value "M113")
      (footprint "eagle-import:H807")
      (libsource (lib "eagle-import") (part "M113"))
    )
    (comp (ref "E16")
      (value "M310")
      (footprint "eagle-import:H807")
      (libsource (lib "eagle-import") (part "M310"))
    )
    (comp (ref "E17")
      (value "M310")
      (footprint "eagle-import:H807")
      (libsource (lib "eagle-import") (part "M310"))
    )
    (comp (ref "E18")
      (value "M216")
      (footprint "eagle-import:H807")
      (libsource (lib "eagle-import") (part "M206X"))
    )
    (comp (ref "E19")
      (value "M216")
      (footprint "eagle-import:H807")
      (libsource (lib "eagle-import") (part "M206X"))
    )
    (comp (ref "EF10")
      (value "M700")
      (footprint "eagle-import:H807-2")
      (libsource (lib "eagle-import") (part "M700"))
    )
    (comp (ref "F08")
      (value "M660")
      (footprint "eagle-import:H807")
      (libsource (lib "eagle-import") (part "M660"))
    )
    (comp (ref "F12")
      (value "M310")
      (footprint "eagle-import:H807")
      (libsource (lib "eagle-import") (part "M310"))
    )
    (comp (ref "F13")
      (value "M310")
      (footprint "eagle-import:H807")
      (libsource (lib "eagle-import") (part "M310"))
    )
    (comp (ref "F14")
      (value "M310")
      (footprint "eagle-import:H807")
      (libsource (lib "eagle-import") (part "M310"))
    )
    (comp (ref "F15")
      (value "M310")
      (footprint "eagle-import:H807")
      (libsource (lib "eagle-import") (part "M310"))
    )
    (comp (ref "F16")
      (value "M310")
      (footprint "eagle-import:H807")
      (libsource (lib "eagle-import") (part "M310"))
    )
    (comp (ref "F17")
      (value "M310")
      (footprint "eagle-import:H807")
      (libsource (lib "eagle-import") (part "M310"))
    )
    (comp (ref "F18")
      (value "M310")
      (footprint "eagle-import:H807")
      (libsource (lib "eagle-import") (part "M310"))
    )
    (comp (ref "F19")
      (value "M117")
      (footprint "eagle-import:H807")
      (libsource (lib "eagle-import") (part "M117"))
    )
    (comp (ref "F20")
      (value "M113")
      (footprint "eagle-import:H807")
      (libsource (lib "eagle-import") (part "M113"))
    )
    (comp (ref "F21")
      (value "M113")
      (footprint "eagle-import:H807")
      (libsource (lib "eagle-import") (part "M113"))
    )
    (comp (ref "F30")
      (value "M617")
      (footprint "eagle-import:H807")
      (libsource (lib "eagle-import") (part "M617"))
    )
    (comp (ref "E26")
      (value "M160")
      (footprint "eagle-import:H807")
      (libsource (lib "eagle-import") (part "M160"))
    )
    (comp (ref "E28")
      (value "M160")
      (footprint "eagle-import:H807")
      (libsource (lib "eagle-import") (part "M160"))
    )
    (comp (ref "E29")
      (value "M160")
      (footprint "eagle-import:H807")
      (libsource (lib "eagle-import") (part "M160"))
    )
    (comp (ref "E30")
      (value "M160")
      (footprint "eagle-import:H807")
      (libsource (lib "eagle-import") (part "M160"))
    )
    (comp (ref "E32")
      (value "M617")
      (footprint "eagle-import:H807")
      (libsource (lib "eagle-import") (part "M617"))
    )
    (comp (ref "F27")
      (value "M117")
      (footprint "eagle-import:H807")
      (libsource (lib "eagle-import") (part "M117"))
    )
    (comp (ref "F29")
      (value "M113")
      (footprint "eagle-import:H807")
      (libsource (lib "eagle-import") (part "M113"))
    )
    (comp (ref "EF02")
      (value "M707")
      (footprint "eagle-import:H807-2")
      (libsource (lib "eagle-import") (part "M707"))
    )
    (comp (ref "F03")
      (value "M452")
      (footprint "eagle-import:H807")
      (libsource (lib "eagle-import") (part "M452"))
    )
    (comp (ref "B21")
      (value "M113")
      (footprint "eagle-import:H807")
      (libsource (lib "eagle-import") (part "M113"))
    )
    (comp (ref "C14")
      (value "M113")
      (footprint "eagle-import:H807")
      (libsource (lib "eagle-import") (part "M113"))
    )
    (comp (ref "C15")
      (value "M113")
      (footprint "eagle-import:H807")
      (libsource (lib "eagle-import") (part "M113"))
    )
    (comp (ref "C16")
      (value "M113")
      (footprint "eagle-import:H807")
      (libsource (lib "eagle-import") (part "M113"))
    )
    (comp (ref "C17")
      (value "M113")
      (footprint "eagle-import:H807")
      (libsource (lib "eagle-import") (part "M113"))
    )
    (comp (ref "C19")
      (value "M115")
      (footprint "eagle-import:H807")
      (libsource (lib "eagle-import") (part "M115"))
    )
    (comp (ref "C20")
      (value "M115")
      (footprint "eagle-import:H807")
      (libsource (lib "eagle-import") (part "M115"))
    )
    (comp (ref "C21")
      (value "M115")
      (footprint "eagle-import:H807")
      (libsource (lib "eagle-import") (part "M115"))
    )
    (comp (ref "C23")
      (value "M216")
      (footprint "eagle-import:H807")
      (libsource (lib "eagle-import") (part "M216"))
    )
    (comp (ref "C24")
      (value "M216")
      (footprint "eagle-import:H807")
      (libsource (lib "eagle-import") (part "M216"))
    )
    (comp (ref "D01")
      (value "W077")
      (footprint "eagle-import:H807")
      (libsource (lib "eagle-import") (part "W023"))
    )
    (comp (ref "HJ26")
      (value "M705")
      (footprint "eagle-import:H807-2")
      (libsource (lib "eagle-import") (part "M705"))
    )
    (comp (ref "HJ27")
      (value "M715")
      (footprint "eagle-import:H807-2")
      (libsource (lib "eagle-import") (part "M715"))
    )
    (comp (ref "A07")
      (value "M162")
      (footprint "eagle-import:H807")
      (libsource (lib "eagle-import") (part "M162"))
    )
    (comp (ref "A08")
      (value "M162")
      (footprint "eagle-import:H807")
      (libsource (lib "eagle-import") (part "M162"))
    )
    (comp (ref "B08")
      (value "M113")
      (footprint "eagle-import:H807")
      (libsource (lib "eagle-import") (part "M113"))
    )
    (comp (ref "H04")
      (value "W011")
      (footprint "eagle-import:H807")
      (libsource (lib "eagle-import") (part "W011"))
    )
    (comp (ref "A05")
      (value "M113")
      (footprint "eagle-import:H807")
      (libsource (lib "eagle-import") (part "M113"))
    )
    (comp (ref "B04")
      (value "M115")
      (footprint "eagle-import:H807")
      (libsource (lib "eagle-import") (part "M115"))
    )
    (comp (ref "B05")
      (value "M216")
      (footprint "eagle-import:H807")
      (libsource (lib "eagle-import") (part "M216"))
    )
    (comp (ref "B06")
      (value "M113")
      (footprint "eagle-import:H807")
      (libsource (lib "eagle-import") (part "M113"))
    )
    (comp (ref "E27")
      (value "M160")
      (footprint "eagle-import:H807")
      (libsource (lib "eagle-import") (part "M160"))
    )
    (comp (ref "E31")
      (value "M617")
      (footprint "eagle-import:H807")
      (libsource (lib "eagle-import") (part "M617"))
    )
    (comp (ref "F24")
      (value "M117")
      (footprint "eagle-import:H807")
      (libsource (lib "eagle-import") (part "M117"))
    )
    (comp (ref "F25")
      (value "M113")
      (footprint "eagle-import:H807")
      (libsource (lib "eagle-import") (part "M113"))
    )
    (comp (ref "F26")
      (value "M115")
      (footprint "eagle-import:H807")
      (libsource (lib "eagle-import") (part "M115"))
    )
    (comp (ref "AB02")
      (value "G826")
      (footprint "eagle-import:H807-2")
      (libsource (lib "eagle-import") (part "G826"))
    )
    (comp (ref "AB03")
      (value "G792")
      (footprint "eagle-import:H807-2")
      (libsource (lib "eagle-import") (part "G792"))
    )
    (comp (ref "E03")
      (value "EMPTY")
      (footprint "eagle-import:H807")
      (libsource (lib "eagle-import") (part "EMPTY"))
    )
    (comp (ref "E04")
      (value "EMPTY")
      (footprint "eagle-import:H807")
      (libsource (lib "eagle-import") (part "EMPTY"))
    )
    (comp (ref "E05")
      (value "EMPTY")
      (footprint "eagle-import:H807")
      (libsource (lib "eagle-import") (part "EMPTY"))
    )
    (comp (ref "E06")
      (value "EMPTY")
      (footprint "eagle-import:H807")
      (libsource (lib "eagle-import") (part "EMPTY"))
    )
    (comp (ref "E07")
      (value "EMPTY")
      (footprint "eagle-import:H807")
      (libsource (lib "eagle-import") (part "EMPTY"))
    )
    (comp (ref "E08")
      (value "EMPTY")
      (footprint "eagle-import:H807")
      (libsource (lib "eagle-import") (part "EMPTY"))
    )
    (comp (ref "F04")
      (value "EMPTY")
      (footprint "eagle-import:H807")
      (libsource (lib "eagle-import") (part "EMPTY"))
    )
    (comp (ref "F05")
      (value "EMPTY")
      (footprint "eagle-import:H807")
      (libsource (lib "eagle-import") (part "EMPTY"))
    )
    (comp (ref "F06")
      (value "EMPTY")
      (footprint "eagle-import:H807")
      (libsource (lib "eagle-import") (part "EMPTY"))
    )
    (comp (ref "F07")
      (value "EMPTY")
      (footprint "eagle-import:H807")
      (libsource (lib "eagle-import") (part "EMPTY"))
    )
    (comp (ref "H06")
      (value "EMPTY")
      (footprint "eagle-import:H807")
      (libsource (lib "eagle-import") (part "EMPTY"))
    )
    (comp (ref "H21")
      (value "EMPTY")
      (footprint "eagle-import:H807")
      (libsource (lib "eagle-import") (part "EMPTY"))
    )
    (comp (ref "H22")
      (value "EMPTY")
      (footprint "eagle-import:H807")
      (libsource (lib "eagle-import") (part "EMPTY"))
    )
    (comp (ref "H33")
      (value "EMPTY")
      (footprint "eagle-import:H807")
      (libsource (lib "eagle-import") (part "EMPTY"))
    )
    (comp (ref "H35")
      (value "EMPTY")
      (footprint "eagle-import:H807")
      (libsource (lib "eagle-import") (part "EMPTY"))
    )
    (comp (ref "H36")
      (value "EMPTY")
      (footprint "eagle-import:H807")
      (libsource (lib "eagle-import") (part "EMPTY"))
    )
    (comp (ref "H37")
      (value "EMPTY")
      (footprint "eagle-import:H807")
      (libsource (lib "eagle-import") (part "EMPTY"))
    )
    (comp (ref "H38")
      (value "EMPTY")
      (footprint "eagle-import:H807")
      (libsource (lib "eagle-import") (part "EMPTY"))
    )
    (comp (ref "H39")
      (value "EMPTY")
      (footprint "eagle-import:H807")
      (libsource (lib "eagle-import") (part "EMPTY"))
    )
    (comp (ref "H40")
      (value "EMPTY")
      (footprint "eagle-import:H807")
      (libsource (lib "eagle-import") (part "EMPTY"))
    )
    (comp (ref "J21")
      (value "EMPTY")
      (footprint "eagle-import:H807")
      (libsource (lib "eagle-import") (part "EMPTY"))
    )
    (comp (ref "J22")
      (value "EMPTY")
      (footprint "eagle-import:H807")
      (libsource (lib "eagle-import") (part "EMPTY"))
    )
    (comp (ref "J35")
      (value "EMPTY")
      (footprint "eagle-import:H807")
      (libsource (lib "eagle-import") (part "EMPTY"))
    )
    (comp (ref "J36")
      (value "EMPTY")
      (footprint "eagle-import:H807")
      (libsource (lib "eagle-import") (part "EMPTY"))
    )
    (comp (ref "J37")
      (value "EMPTY")
      (footprint "eagle-import:H807")
      (libsource (lib "eagle-import") (part "EMPTY"))
    )
    (comp (ref "J38")
      (value "EMPTY")
      (footprint "eagle-import:H807")
      (libsource (lib "eagle-import") (part "EMPTY"))
    )
    (comp (ref "J39")
      (value "EMPTY")
      (footprint "eagle-import:H807")
      (libsource (lib "eagle-import") (part "EMPTY"))
    )
    (comp (ref "J40")
      (value "EMPTY")
      (footprint "eagle-import:H807")
      (libsource (lib "eagle-import") (part "EMPTY"))
    )
    (comp (ref "B10")
      (value "M720")
      (footprint "eagle-import:H807")
      (libsource (lib "eagle-import") (part "M720"))
    )
    (comp (ref "B12")
      (value "M617")
      (footprint "eagle-import:H807")
      (libsource (lib "eagle-import") (part "M617"))
    )
    (comp (ref "B13")
      (value "M617")
      (footprint "eagle-import:H807")
      (libsource (lib "eagle-import") (part "M617"))
    )
    (comp (ref "B14")
      (value "M617")
      (footprint "eagle-import:H807")
      (libsource (lib "eagle-import") (part "M617"))
    )
    (comp (ref "B15")
      (value "M617")
      (footprint "eagle-import:H807")
      (libsource (lib "eagle-import") (part "M617"))
    )
    (comp (ref "B19")
      (value "M216")
      (footprint "eagle-import:H807")
      (libsource (lib "eagle-import") (part "M216"))
    )
    (comp (ref "H01")
      (value "W011")
      (footprint "eagle-import:H807")
      (libsource (lib "eagle-import") (part "W011"))
    )
    (comp (ref "H02")
      (value "W011")
      (footprint "eagle-import:H807")
      (libsource (lib "eagle-import") (part "W011"))
    )
    (comp (ref "H03")
      (value "W011")
      (footprint "eagle-import:H807")
      (libsource (lib "eagle-import") (part "W011"))
    )
    (comp (ref "J33")
      (value "M714")
      (footprint "eagle-import:H807")
      (libsource (lib "eagle-import") (part "M714"))
    )
    (comp (ref "H30")
      (value "M708")
      (footprint "eagle-import:H807")
      (libsource (lib "eagle-import") (part "M708"))
    )
    (comp (ref "HJ31")
      (value "M709")
      (footprint "eagle-import:H807-2")
      (libsource (lib "eagle-import") (part "M709"))
    )
    (comp (ref "J30")
      (value "M401/M405/M501")
      (footprint "eagle-import:H807")
      (libsource (lib "eagle-import") (part "M501"))
    )
  )
  (nets
    (net (code "1") (name "+3V(01)") (class "Default")
      (node (ref "A13") (pin "E1") (pinfunction "IN2_E1") (pintype "input"))
      (node (ref "A13") (pin "H1") (pinfunction "IN1_H1") (pintype "input"))
      (node (ref "A13") (pin "M1") (pinfunction "IN2_M1") (pintype "input"))
      (node (ref "A13") (pin "R1") (pinfunction "IN2_R1") (pintype "input"))
      (node (ref "A15") (pin "U1") (pinfunction "P$1_U1") (pintype "passive"))
    )
    (net (code "2") (name "+3V(02)") (class "Default")
      (node (ref "A13") (pin "U2") (pinfunction "IN2_U2") (pintype "input"))
      (node (ref "A14") (pin "B1") (pinfunction "IN2_B1") (pintype "input"))
      (node (ref "A14") (pin "H2") (pinfunction "IN1_H2") (pintype "input"))
      (node (ref "A14") (pin "J1") (pinfunction "IN2_J1") (pintype "input"))
      (node (ref "A14") (pin "L1") (pinfunction "IN1_L1") (pintype "input"))
      (node (ref "A15") (pin "V1") (pinfunction "P$1_V1") (pintype "passive"))
    )
    (net (code "3") (name "+3V(03)") (class "Default")
      (node (ref "A14") (pin "L2") (pinfunction "IN1_L2") (pintype "input"))
      (node (ref "A14") (pin "P1") (pinfunction "IN1_P1") (pintype "input"))
      (node (ref "A15") (pin "B1") (pinfunction "IN2_B1") (pintype "input"))
      (node (ref "A15") (pin "M2") (pinfunction "IN2_M2") (pintype "input"))
      (node (ref "A15") (pin "P1") (pinfunction "IN1_P1") (pintype "input"))
      (node (ref "A18") (pin "U1") (pinfunction "P$1_U1") (pintype "passive"))
    )
    (net (code "4") (name "+3V(04)") (class "Default")
      (node (ref "A18") (pin "V1") (pinfunction "P$1_V1") (pintype "passive"))
      (node (ref "A19") (pin "D1") (pinfunction "IN1_D1") (pintype "input"))
      (node (ref "A19") (pin "D2") (pinfunction "IN1_D2") (pintype "input"))
      (node (ref "A19") (pin "L2") (pinfunction "IN1_L2") (pintype "input"))
      (node (ref "A19") (pin "T2") (pinfunction "IN1_T2") (pintype "input"))
    )
    (net (code "5") (name "+3V(05)") (class "Default")
      (node (ref "A10") (pin "D1") (pinfunction "8B_D1") (pintype "input"))
      (node (ref "B08") (pin "B1") (pinfunction "IN2_B1") (pintype "input"))
      (node (ref "B08") (pin "E1") (pinfunction "IN2_E1") (pintype "input"))
      (node (ref "B08") (pin "E2") (pinfunction "IN2_E2") (pintype "input"))
      (node (ref "B08") (pin "J1") (pinfunction "IN2_J1") (pintype "input"))
      (node (ref "B08") (pin "J2") (pinfunction "IN2_J2") (pintype "input"))
      (node (ref "B08") (pin "M1") (pinfunction "IN2_M1") (pintype "input"))
      (node (ref "B08") (pin "M2") (pinfunction "IN2_M2") (pintype "input"))
      (node (ref "B08") (pin "U1") (pinfunction "P$1_U1") (pintype "passive"))
    )
    (net (code "6") (name "+3V(06)") (class "Default")
      (node (ref "B08") (pin "R1") (pinfunction "IN2_R1") (pintype "input"))
      (node (ref "B08") (pin "R2") (pinfunction "IN2_R2") (pintype "input"))
      (node (ref "B08") (pin "U2") (pinfunction "IN2_U2") (pintype "input"))
      (node (ref "B09") (pin "B1") (pinfunction "IN2_B1") (pintype "input"))
      (node (ref "B09") (pin "D2") (pinfunction "IN1_D2") (pintype "input"))
      (node (ref "B09") (pin "E1") (pinfunction "IN2_E1") (pintype "input"))
      (node (ref "B09") (pin "H2") (pinfunction "IN1_H2") (pintype "input"))
      (node (ref "B09") (pin "R1") (pinfunction "IN2_R1") (pintype "input"))
      (node (ref "B09") (pin "U1") (pinfunction "P$1_U1") (pintype "passive"))
    )
    (net (code "7") (name "+3V(07)") (class "Default")
      (node (ref "B07") (pin "F1") (pinfunction "IN2_F1") (pintype "input"))
      (node (ref "B07") (pin "K1") (pinfunction "IN1_K1") (pintype "input"))
      (node (ref "B07") (pin "P2") (pinfunction "IN2_P2") (pintype "input"))
      (node (ref "B07") (pin "R2") (pinfunction "IN3_R2") (pintype "input"))
      (node (ref "B09") (pin "J1") (pinfunction "IN2_J1") (pintype "input"))
      (node (ref "B09") (pin "M2") (pinfunction "IN2_M2") (pintype "input"))
      (node (ref "B09") (pin "V1") (pinfunction "P$1_V1") (pintype "passive"))
      (node (ref "B11") (pin "K2") (pinfunction "R_K2") (pintype "input"))
    )
    (net (code "8") (name "+3V(08)") (class "Default")
      (node (ref "B11") (pin "A1") (pinfunction "R_A1") (pintype "input"))
      (node (ref "B12") (pin "B1") (pinfunction "IN2_B1") (pintype "input"))
      (node (ref "B12") (pin "C1") (pinfunction "IN3_C1") (pintype "input"))
      (node (ref "B12") (pin "D1") (pinfunction "IN4_D1") (pintype "input"))
      (node (ref "B12") (pin "E2") (pinfunction "IN2_E2") (pintype "input"))
      (node (ref "B12") (pin "F2") (pinfunction "IN3_F2") (pintype "input"))
      (node (ref "B12") (pin "H1") (pinfunction "IN2_H1") (pintype "input"))
      (node (ref "B12") (pin "H2") (pinfunction "IN4_H2") (pintype "input"))
      (node (ref "B12") (pin "J1") (pinfunction "IN3_J1") (pintype "input"))
      (node (ref "B12") (pin "K1") (pinfunction "IN4_K1") (pintype "input"))
      (node (ref "C12") (pin "V1") (pinfunction "P$1_V1") (pintype "passive"))
    )
    (net (code "9") (name "+3V(09)") (class "Default")
      (node (ref "A11") (pin "V1") (pinfunction "P$1_V1") (pintype "passive"))
      (node (ref "B12") (pin "L2") (pinfunction "IN2_L2") (pintype "input"))
      (node (ref "B12") (pin "M2") (pinfunction "IN3_M2") (pintype "input"))
      (node (ref "B12") (pin "N1") (pinfunction "IN2_N1") (pintype "input"))
      (node (ref "B12") (pin "N2") (pinfunction "IN4_N2") (pintype "input"))
      (node (ref "B12") (pin "P1") (pinfunction "IN3_P1") (pintype "input"))
      (node (ref "B12") (pin "R1") (pinfunction "IN4_R1") (pintype "input"))
    )
    (net (code "10") (name "+3V(10)") (class "Default")
      (node (ref "B12") (pin "S2") (pinfunction "IN2_S2") (pintype "input"))
      (node (ref "B12") (pin "T2") (pinfunction "IN3_T2") (pintype "input"))
      (node (ref "B12") (pin "U2") (pinfunction "IN4_U2") (pintype "input"))
      (node (ref "B13") (pin "B1") (pinfunction "IN2_B1") (pintype "input"))
      (node (ref "B13") (pin "C1") (pinfunction "IN3_C1") (pintype "input"))
      (node (ref "B13") (pin "D1") (pinfunction "IN4_D1") (pintype "input"))
      (node (ref "B13") (pin "E2") (pinfunction "IN2_E2") (pintype "input"))
      (node (ref "B13") (pin "F2") (pinfunction "IN3_F2") (pintype "input"))
      (node (ref "B13") (pin "H2") (pinfunction "IN4_H2") (pintype "input"))
      (node (ref "F09") (pin "V1") (pinfunction "P$1_V1") (pintype "passive"))
    )
    (net (code "11") (name "+3V(11)") (class "Default")
      (node (ref "A13") (pin "U1") (pinfunction "P$1_U1") (pintype "passive"))
      (node (ref "B13") (pin "H1") (pinfunction "IN2_H1") (pintype "input"))
      (node (ref "B13") (pin "J1") (pinfunction "IN3_J1") (pintype "input"))
      (node (ref "B13") (pin "K1") (pinfunction "IN4_K1") (pintype "input"))
    )
    (net (code "12") (name "+3V(12)") (class "Default")
      (node (ref "B13") (pin "L2") (pinfunction "IN2_L2") (pintype "input"))
      (node (ref "B13") (pin "M2") (pinfunction "IN3_M2") (pintype "input"))
      (node (ref "B13") (pin "N1") (pinfunction "IN2_N1") (pintype "input"))
      (node (ref "B13") (pin "N2") (pinfunction "IN4_N2") (pintype "input"))
      (node (ref "B13") (pin "P1") (pinfunction "IN3_P1") (pintype "input"))
      (node (ref "B13") (pin "R1") (pinfunction "IN4_R1") (pintype "input"))
      (node (ref "B13") (pin "S2") (pinfunction "IN2_S2") (pintype "input"))
      (node (ref "B13") (pin "T2") (pinfunction "IN3_T2") (pintype "input"))
      (node (ref "B13") (pin "U1") (pinfunction "P$1_U1") (pintype "passive"))
      (node (ref "B13") (pin "U2") (pinfunction "IN4_U2") (pintype "input"))
      (node (ref "B14") (pin "B1") (pinfunction "IN2_B1") (pintype "input"))
      (node (ref "B14") (pin "C1") (pinfunction "IN3_C1") (pintype "input"))
      (node (ref "B14") (pin "D1") (pinfunction "IN4_D1") (pintype "input"))
    )
    (net (code "13") (name "+3V(13)") (class "Default")
      (node (ref "B13") (pin "V1") (pinfunction "P$1_V1") (pintype "passive"))
      (node (ref "B14") (pin "E2") (pinfunction "IN2_E2") (pintype "input"))
      (node (ref "B14") (pin "F2") (pinfunction "IN3_F2") (pintype "input"))
      (node (ref "B14") (pin "H2") (pinfunction "IN4_H2") (pintype "input"))
    )
    (net (code "14") (name "+3V(14)") (class "Default")
      (node (ref "B14") (pin "H1") (pinfunction "IN2_H1") (pintype "input"))
      (node (ref "B14") (pin "J1") (pinfunction "IN3_J1") (pintype "input"))
      (node (ref "B14") (pin "K1") (pinfunction "IN4_K1") (pintype "input"))
      (node (ref "B14") (pin "L2") (pinfunction "IN2_L2") (pintype "input"))
      (node (ref "B14") (pin "M2") (pinfunction "IN3_M2") (pintype "input"))
      (node (ref "B14") (pin "N1") (pinfunction "IN2_N1") (pintype "input"))
      (node (ref "B14") (pin "N2") (pinfunction "IN4_N2") (pintype "input"))
      (node (ref "B14") (pin "P1") (pinfunction "IN3_P1") (pintype "input"))
      (node (ref "B14") (pin "R1") (pinfunction "IN4_R1") (pintype "input"))
      (node (ref "B14") (pin "U1") (pinfunction "P$1_U1") (pintype "passive"))
    )
    (net (code "15") (name "+3V(15)") (class "Default")
      (node (ref "B14") (pin "S2") (pinfunction "IN2_S2") (pintype "input"))
      (node (ref "B14") (pin "T2") (pinfunction "IN3_T2") (pintype "input"))
      (node (ref "B14") (pin "U2") (pinfunction "IN4_U2") (pintype "input"))
      (node (ref "B14") (pin "V1") (pinfunction "P$1_V1") (pintype "passive"))
      (node (ref "B15") (pin "B1") (pinfunction "IN2_B1") (pintype "input"))
      (node (ref "B15") (pin "C1") (pinfunction "IN3_C1") (pintype "input"))
      (node (ref "B15") (pin "D1") (pinfunction "IN4_D1") (pintype "input"))
    )
    (net (code "16") (name "+3V(16)") (class "Default")
      (node (ref "B15") (pin "E2") (pinfunction "IN2_E2") (pintype "input"))
      (node (ref "B15") (pin "F2") (pinfunction "IN3_F2") (pintype "input"))
      (node (ref "B15") (pin "H1") (pinfunction "IN2_H1") (pintype "input"))
      (node (ref "B15") (pin "H2") (pinfunction "IN4_H2") (pintype "input"))
      (node (ref "B15") (pin "J1") (pinfunction "IN3_J1") (pintype "input"))
      (node (ref "B15") (pin "K1") (pinfunction "IN4_K1") (pintype "input"))
      (node (ref "B15") (pin "U1") (pinfunction "P$1_U1") (pintype "passive"))
    )
    (net (code "17") (name "+3V(17)") (class "Default")
      (node (ref "B15") (pin "L2") (pinfunction "IN2_L2") (pintype "input"))
      (node (ref "B15") (pin "M2") (pinfunction "IN3_M2") (pintype "input"))
      (node (ref "B15") (pin "N1") (pinfunction "IN2_N1") (pintype "input"))
      (node (ref "B15") (pin "N2") (pinfunction "IN4_N2") (pintype "input"))
      (node (ref "B15") (pin "P1") (pinfunction "IN3_P1") (pintype "input"))
      (node (ref "B15") (pin "R1") (pinfunction "IN4_R1") (pintype "input"))
      (node (ref "B15") (pin "S2") (pinfunction "IN2_S2") (pintype "input"))
      (node (ref "B15") (pin "T2") (pinfunction "IN3_T2") (pintype "input"))
      (node (ref "B15") (pin "U2") (pinfunction "IN4_U2") (pintype "input"))
      (node (ref "B16") (pin "V1") (pinfunction "P$1_V1") (pintype "passive"))
    )
    (net (code "18") (name "+3V(18)") (class "Default")
      (node (ref "B16") (pin "D1") (pinfunction "IN4_D1") (pintype "input"))
      (node (ref "B16") (pin "H2") (pinfunction "IN4_H2") (pintype "input"))
      (node (ref "B16") (pin "K1") (pinfunction "IN4_K1") (pintype "input"))
      (node (ref "B16") (pin "U1") (pinfunction "P$1_U1") (pintype "passive"))
    )
    (net (code "19") (name "+3V(19)") (class "Default")
      (node (ref "A19") (pin "U1") (pinfunction "P$1_U1") (pintype "passive"))
      (node (ref "B17") (pin "D1") (pinfunction "S_D1") (pintype "input"))
      (node (ref "B17") (pin "F2") (pinfunction "S_F2") (pintype "input"))
      (node (ref "B17") (pin "K1") (pinfunction "S_K1") (pintype "input"))
      (node (ref "B17") (pin "N2") (pinfunction "S_N2") (pintype "input"))
      (node (ref "B17") (pin "R1") (pinfunction "S_R1") (pintype "input"))
      (node (ref "B17") (pin "U2") (pinfunction "S_U2") (pintype "input"))
      (node (ref "B18") (pin "D1") (pinfunction "S_D1") (pintype "input"))
      (node (ref "B18") (pin "F2") (pinfunction "S_F2") (pintype "input"))
      (node (ref "B18") (pin "K1") (pinfunction "S_K1") (pintype "input"))
      (node (ref "B18") (pin "K2") (pinfunction "R_K2") (pintype "input"))
    )
    (net (code "20") (name "+3V(20)") (class "Default")
      (node (ref "A19") (pin "V1") (pinfunction "P$1_V1") (pintype "passive"))
      (node (ref "B18") (pin "N2") (pinfunction "S_N2") (pintype "input"))
      (node (ref "B18") (pin "R1") (pinfunction "S_R1") (pintype "input"))
      (node (ref "B18") (pin "U2") (pinfunction "S_U2") (pintype "input"))
      (node (ref "B19") (pin "A1") (pinfunction "R_A1") (pintype "input"))
      (node (ref "B19") (pin "D1") (pinfunction "S_D1") (pintype "input"))
      (node (ref "B19") (pin "F2") (pinfunction "S_F2") (pintype "input"))
      (node (ref "B19") (pin "K1") (pinfunction "S_K1") (pintype "input"))
      (node (ref "B19") (pin "K2") (pinfunction "R_K2") (pintype "input"))
      (node (ref "B19") (pin "N2") (pinfunction "S_N2") (pintype "input"))
      (node (ref "B19") (pin "R1") (pinfunction "S_R1") (pintype "input"))
      (node (ref "B19") (pin "U2") (pinfunction "S_U2") (pintype "input"))
    )
    (net (code "21") (name "+3V(23)") (class "Default")
      (node (ref "C10") (pin "B1") (pinfunction "IN2_B1") (pintype "input"))
      (node (ref "C10") (pin "D1") (pinfunction "IN1_D1") (pintype "input"))
      (node (ref "C10") (pin "D2") (pinfunction "IN1_D2") (pintype "input"))
      (node (ref "C10") (pin "H2") (pinfunction "IN1_H2") (pintype "input"))
      (node (ref "C10") (pin "J1") (pinfunction "IN2_J1") (pintype "input"))
      (node (ref "C10") (pin "U2") (pinfunction "IN2_U2") (pintype "input"))
      (node (ref "C11") (pin "B1") (pinfunction "IN2_B1") (pintype "input"))
      (node (ref "D10") (pin "B1") (pinfunction "IN2_B1") (pintype "input"))
      (node (ref "D10") (pin "C1") (pinfunction "IN3_C1") (pintype "input"))
      (node (ref "D10") (pin "U1") (pinfunction "P$1_U1") (pintype "passive"))
      (node (ref "D11") (pin "A1") (pinfunction "R_A1") (pintype "input"))
    )
    (net (code "22") (name "+3V(24)") (class "Default")
      (node (ref "C18") (pin "A1") (pinfunction "IN1_A1") (pintype "input"))
      (node (ref "C18") (pin "D1") (pinfunction "IN1_D1") (pintype "input"))
      (node (ref "C18") (pin "D2") (pinfunction "IN1_D2") (pintype "input"))
      (node (ref "C18") (pin "H2") (pinfunction "IN1_H2") (pintype "input"))
      (node (ref "C18") (pin "R2") (pinfunction "IN2_R2") (pintype "input"))
      (node (ref "C18") (pin "U1") (pinfunction "P$1_U1") (pintype "passive"))
      (node (ref "C18") (pin "U2") (pinfunction "IN2_U2") (pintype "input"))
    )
    (net (code "23") (name "+3V(25)") (class "Default")
      (node (ref "B21") (pin "V1") (pinfunction "P$1_V1") (pintype "passive"))
      (node (ref "C22") (pin "A1") (pinfunction "R_A1") (pintype "input"))
      (node (ref "C22") (pin "D1") (pinfunction "S_D1") (pintype "input"))
      (node (ref "C22") (pin "F2") (pinfunction "S_F2") (pintype "input"))
      (node (ref "C22") (pin "K1") (pinfunction "S_K1") (pintype "input"))
      (node (ref "C22") (pin "K2") (pinfunction "R_K2") (pintype "input"))
      (node (ref "C22") (pin "N2") (pinfunction "S_N2") (pintype "input"))
      (node (ref "C22") (pin "R1") (pinfunction "S_R1") (pintype "input"))
    )
    (net (code "24") (name "+3V(26)") (class "Default")
      (node (ref "C23") (pin "A1") (pinfunction "R_A1") (pintype "input"))
      (node (ref "C23") (pin "D1") (pinfunction "S_D1") (pintype "input"))
      (node (ref "C23") (pin "F2") (pinfunction "S_F2") (pintype "input"))
      (node (ref "C23") (pin "K1") (pinfunction "S_K1") (pintype "input"))
      (node (ref "C23") (pin "K2") (pinfunction "R_K2") (pintype "input"))
      (node (ref "C23") (pin "N2") (pinfunction "S_N2") (pintype "input"))
      (node (ref "C23") (pin "R1") (pinfunction "S_R1") (pintype "input"))
      (node (ref "C23") (pin "U2") (pinfunction "S_U2") (pintype "input"))
      (node (ref "D22") (pin "U1") (pinfunction "P$1_U1") (pintype "passive"))
    )
    (net (code "25") (name "+3V(27)") (class "Default")
      (node (ref "C24") (pin "A1") (pinfunction "R_A1") (pintype "input"))
      (node (ref "C24") (pin "D1") (pinfunction "S_D1") (pintype "input"))
      (node (ref "C24") (pin "F2") (pinfunction "S_F2") (pintype "input"))
      (node (ref "C24") (pin "K1") (pinfunction "S_K1") (pintype "input"))
      (node (ref "C24") (pin "K2") (pinfunction "R_K2") (pintype "input"))
      (node (ref "C24") (pin "N2") (pinfunction "S_N2") (pintype "input"))
      (node (ref "C24") (pin "R1") (pinfunction "S_R1") (pintype "input"))
      (node (ref "C24") (pin "U2") (pinfunction "S_U2") (pintype "input"))
      (node (ref "D22") (pin "V1") (pinfunction "P$1_V1") (pintype "passive"))
    )
    (net (code "26") (name "+3V(28)") (class "Default")
      (node (ref "D12") (pin "E1") (pinfunction "IN2_E1") (pintype "input"))
      (node (ref "D12") (pin "J2") (pinfunction "IN2_J2") (pintype "input"))
      (node (ref "D12") (pin "M1") (pinfunction "IN2_M1") (pintype "input"))
      (node (ref "D12") (pin "T2") (pinfunction "IN1_T2") (pintype "input"))
      (node (ref "D12") (pin "U1") (pinfunction "P$1_U1") (pintype "passive"))
      (node (ref "D13") (pin "J1") (pinfunction "IN2_J1") (pintype "input"))
      (node (ref "D13") (pin "J2") (pinfunction "IN2_J2") (pintype "input"))
    )
    (net (code "27") (name "+3V(29)") (class "Default")
      (node (ref "D14") (pin "P1") (pinfunction "IN1_P1") (pintype "input"))
      (node (ref "D15") (pin "D2") (pinfunction "IN1_D2") (pintype "input"))
      (node (ref "D15") (pin "H2") (pinfunction "IN1_H2") (pintype "input"))
      (node (ref "D15") (pin "M2") (pinfunction "IN2_M2") (pintype "input"))
      (node (ref "D15") (pin "P1") (pinfunction "IN1_P1") (pintype "input"))
      (node (ref "D15") (pin "U1") (pinfunction "P$1_U1") (pintype "passive"))
      (node (ref "D15") (pin "U2") (pinfunction "IN2_U2") (pintype "input"))
    )
    (net (code "28") (name "+3V(30)") (class "Default")
      (node (ref "D16") (pin "A1") (pinfunction "IN1_A1") (pintype "input"))
      (node (ref "D16") (pin "D1") (pinfunction "IN1_D1") (pintype "input"))
      (node (ref "D16") (pin "D2") (pinfunction "IN1_D2") (pintype "input"))
      (node (ref "D16") (pin "M2") (pinfunction "IN2_M2") (pintype "input"))
      (node (ref "D16") (pin "R1") (pinfunction "IN2_R1") (pintype "input"))
      (node (ref "D16") (pin "R2") (pinfunction "IN2_R2") (pintype "input"))
      (node (ref "D16") (pin "U1") (pinfunction "P$1_U1") (pintype "passive"))
      (node (ref "D16") (pin "U2") (pinfunction "IN2_U2") (pintype "input"))
    )
    (net (code "29") (name "+3V(31)") (class "Default")
      (node (ref "D22") (pin "H1") (pinfunction "IN2_H1") (pintype "input"))
      (node (ref "D22") (pin "J1") (pinfunction "IN3_J1") (pintype "input"))
      (node (ref "D22") (pin "K1") (pinfunction "IN4_K1") (pintype "input"))
      (node (ref "D22") (pin "L2") (pinfunction "IN2_L2") (pintype "input"))
      (node (ref "D22") (pin "M1") (pinfunction "IN1_M1") (pintype "input"))
      (node (ref "D22") (pin "M2") (pinfunction "IN3_M2") (pintype "input"))
      (node (ref "D22") (pin "N1") (pinfunction "IN2_N1") (pintype "input"))
      (node (ref "D22") (pin "N2") (pinfunction "IN4_N2") (pintype "input"))
      (node (ref "D22") (pin "T2") (pinfunction "IN3_T2") (pintype "input"))
      (node (ref "E22") (pin "V1") (pinfunction "P$1_V1") (pintype "passive"))
    )
    (net (code "30") (name "+3V(32)") (class "Default")
      (node (ref "D23") (pin "D2") (pinfunction "IN1A_D2") (pintype "input"))
      (node (ref "D23") (pin "E2") (pinfunction "IN1B_E2") (pintype "input"))
      (node (ref "D23") (pin "M1") (pinfunction "IN5A_M1") (pintype "input"))
      (node (ref "D23") (pin "N2") (pinfunction "IN4A_N2") (pintype "input"))
      (node (ref "D23") (pin "P2") (pinfunction "IN4B_P2") (pintype "input"))
      (node (ref "D23") (pin "R2") (pinfunction "IN4C_R2") (pintype "input"))
      (node (ref "D24") (pin "D1") (pinfunction "S_D1") (pintype "input"))
      (node (ref "D24") (pin "F2") (pinfunction "S_F2") (pintype "input"))
      (node (ref "D24") (pin "K1") (pinfunction "S_K1") (pintype "input"))
      (node (ref "D24") (pin "N2") (pinfunction "S_N2") (pintype "input"))
      (node (ref "E24") (pin "U1") (pinfunction "P$1_U1") (pintype "passive"))
    )
    (net (code "31") (name "+3V(33)") (class "Default")
      (node (ref "E11") (pin "B1") (pinfunction "IN2_B1") (pintype "input"))
      (node (ref "E11") (pin "E2") (pinfunction "IN2_E2") (pintype "input"))
      (node (ref "E11") (pin "H2") (pinfunction "IN1_H2") (pintype "input"))
      (node (ref "E11") (pin "M2") (pinfunction "IN2_M2") (pintype "input"))
      (node (ref "E11") (pin "P2") (pinfunction "IN1_P2") (pintype "input"))
      (node (ref "E12") (pin "B1") (pinfunction "IN2_B1") (pintype "input"))
      (node (ref "E12") (pin "J1") (pinfunction "IN2_J1") (pintype "input"))
      (node (ref "E12") (pin "L1") (pinfunction "IN1_L1") (pintype "input"))
      (node (ref "E12") (pin "R1") (pinfunction "IN2_R1") (pintype "input"))
      (node (ref "E12") (pin "T2") (pinfunction "IN1_T2") (pintype "input"))
      (node (ref "EF01") (pin "BR1") (pinfunction "BR1_BR1") (pintype "input"))
      (node (ref "EF02") (pin "AN1") (pinfunction "AN1_AN1") (pintype "input"))
      (node (ref "EF02") (pin "AN2") (pinfunction "AN2_AN2") (pintype "input"))
      (node (ref "EF02") (pin "BF2") (pinfunction "BF2_BF2") (pintype "input"))
      (node (ref "EF02") (pin "BJ1") (pinfunction "BJ1_BJ1") (pintype "output"))
      (node (ref "EF02") (pin "BS2") (pinfunction "BS2_BS2") (pintype "input"))
    )
    (net (code "32") (name "+3V(34)") (class "Default")
      (node (ref "E13") (pin "N1") (pinfunction "IN5B_N1") (pintype "input"))
      (node (ref "E13") (pin "P1") (pinfunction "IN5C_P1") (pintype "input"))
      (node (ref "E15") (pin "J2") (pinfunction "IN2_J2") (pintype "input"))
      (node (ref "E15") (pin "M1") (pinfunction "IN2_M1") (pintype "input"))
      (node (ref "E15") (pin "M2") (pinfunction "IN2_M2") (pintype "input"))
      (node (ref "E15") (pin "P2") (pinfunction "IN1_P2") (pintype "input"))
      (node (ref "E15") (pin "U1") (pinfunction "P$1_U1") (pintype "passive"))
      (node (ref "E15") (pin "U2") (pinfunction "IN2_U2") (pintype "input"))
    )
    (net (code "33") (name "+3V(35)") (class "Default")
      (node (ref "E15") (pin "V1") (pinfunction "P$1_V1") (pintype "passive"))
      (node (ref "E18") (pin "C1") (pinfunction "D_C1") (pintype "input"))
      (node (ref "E18") (pin "N2") (pinfunction "S_N2") (pintype "input"))
      (node (ref "E20") (pin "D1") (pinfunction "S_D1") (pintype "input"))
      (node (ref "E20") (pin "F2") (pinfunction "S_F2") (pintype "input"))
      (node (ref "E20") (pin "K1") (pinfunction "S_K1") (pintype "input"))
      (node (ref "E20") (pin "N2") (pinfunction "S_N2") (pintype "input"))
    )
    (net (code "34") (name "+3V(36)") (class "Default")
      (node (ref "E22") (pin "M2") (pinfunction "IN2_M2") (pintype "input"))
      (node (ref "E22") (pin "R1") (pinfunction "IN2_R1") (pintype "input"))
      (node (ref "E22") (pin "R2") (pinfunction "IN2_R2") (pintype "input"))
      (node (ref "E22") (pin "U1") (pinfunction "P$1_U1") (pintype "passive"))
      (node (ref "E22") (pin "U2") (pinfunction "IN2_U2") (pintype "input"))
      (node (ref "E23") (pin "F2") (pinfunction "S_F2") (pintype "input"))
      (node (ref "E23") (pin "K1") (pinfunction "S_K1") (pintype "input"))
      (node (ref "E23") (pin "N2") (pinfunction "S_N2") (pintype "input"))
      (node (ref "E23") (pin "R1") (pinfunction "S_R1") (pintype "input"))
      (node (ref "E23") (pin "U2") (pinfunction "S_U2") (pintype "input"))
      (node (ref "E24") (pin "J1") (pinfunction "IN2_J1") (pintype "input"))
      (node (ref "E24") (pin "M2") (pinfunction "IN2_M2") (pintype "input"))
      (node (ref "E24") (pin "P1") (pinfunction "IN1_P1") (pintype "input"))
      (node (ref "E24") (pin "P2") (pinfunction "IN1_P2") (pintype "input"))
    )
    (net (code "35") (name "+3V(37)") (class "Default")
      (node (ref "E26") (pin "D2") (pinfunction "IN1A_D2") (pintype "input"))
      (node (ref "E26") (pin "N2") (pinfunction "IN4A_N2") (pintype "input"))
      (node (ref "E27") (pin "C1") (pinfunction "IN1C_C1") (pintype "input"))
      (node (ref "E27") (pin "E2") (pinfunction "IN1B_E2") (pintype "input"))
      (node (ref "E27") (pin "F2") (pinfunction "IN1C_F2") (pintype "input"))
      (node (ref "E27") (pin "H2") (pinfunction "IN1D_H2") (pintype "input"))
      (node (ref "E27") (pin "N2") (pinfunction "IN4A_N2") (pintype "input"))
      (node (ref "E28") (pin "A1") (pinfunction "IN1A_A1") (pintype "input"))
      (node (ref "E28") (pin "H1") (pinfunction "IN3A_H1") (pintype "input"))
      (node (ref "F27") (pin "U1") (pinfunction "P$1_U1") (pintype "passive"))
    )
    (net (code "36") (name "+3V(38)") (class "Default")
      (node (ref "E28") (pin "K1") (pinfunction "IN4A_K1") (pintype "input"))
      (node (ref "E29") (pin "B1") (pinfunction "IN1B_B1") (pintype "input"))
      (node (ref "E29") (pin "E2") (pinfunction "IN1B_E2") (pintype "input"))
      (node (ref "E29") (pin "H1") (pinfunction "IN3A_H1") (pintype "input"))
      (node (ref "E29") (pin "H2") (pinfunction "IN1D_H2") (pintype "input"))
      (node (ref "E29") (pin "P2") (pinfunction "IN4B_P2") (pintype "input"))
      (node (ref "E29") (pin "R2") (pinfunction "IN4C_R2") (pintype "input"))
      (node (ref "F29") (pin "U1") (pinfunction "P$1_U1") (pintype "passive"))
    )
    (net (code "37") (name "+3V(39)") (class "Default")
      (node (ref "E30") (pin "B1") (pinfunction "IN1B_B1") (pintype "input"))
      (node (ref "E30") (pin "C1") (pinfunction "IN1C_C1") (pintype "input"))
      (node (ref "E30") (pin "D1") (pinfunction "IN1D_D1") (pintype "input"))
      (node (ref "E30") (pin "E2") (pinfunction "IN1B_E2") (pintype "input"))
      (node (ref "E30") (pin "N2") (pinfunction "IN4A_N2") (pintype "input"))
      (node (ref "E31") (pin "B1") (pinfunction "IN2_B1") (pintype "input"))
      (node (ref "E31") (pin "C1") (pinfunction "IN3_C1") (pintype "input"))
      (node (ref "E31") (pin "D1") (pinfunction "IN4_D1") (pintype "input"))
      (node (ref "E31") (pin "D2") (pinfunction "IN1_D2") (pintype "input"))
      (node (ref "E31") (pin "E2") (pinfunction "IN2_E2") (pintype "input"))
      (node (ref "E31") (pin "U1") (pinfunction "P$1_U1") (pintype "passive"))
    )
    (net (code "38") (name "+3V(40)") (class "Default")
      (node (ref "E31") (pin "F1") (pinfunction "IN1_F1") (pintype "input"))
      (node (ref "E31") (pin "F2") (pinfunction "IN3_F2") (pintype "input"))
      (node (ref "E31") (pin "K2") (pinfunction "IN1_K2") (pintype "input"))
      (node (ref "E31") (pin "L2") (pinfunction "IN2_L2") (pintype "input"))
      (node (ref "E31") (pin "S2") (pinfunction "IN2_S2") (pintype "input"))
      (node (ref "E31") (pin "T2") (pinfunction "IN3_T2") (pintype "input"))
      (node (ref "E31") (pin "U2") (pinfunction "IN4_U2") (pintype "input"))
      (node (ref "E31") (pin "V1") (pinfunction "P$1_V1") (pintype "passive"))
    )
    (net (code "39") (name "+3V(41)") (class "Default")
      (node (ref "E32") (pin "B1") (pinfunction "IN2_B1") (pintype "input"))
      (node (ref "E32") (pin "C1") (pinfunction "IN3_C1") (pintype "input"))
      (node (ref "E32") (pin "D2") (pinfunction "IN1_D2") (pintype "input"))
      (node (ref "E32") (pin "F1") (pinfunction "IN1_F1") (pintype "input"))
      (node (ref "E32") (pin "H1") (pinfunction "IN2_H1") (pintype "input"))
      (node (ref "E32") (pin "J1") (pinfunction "IN3_J1") (pintype "input"))
      (node (ref "E32") (pin "U1") (pinfunction "P$1_U1") (pintype "passive"))
    )
    (net (code "40") (name "+3V(42)") (class "Default")
      (node (ref "E32") (pin "R2") (pinfunction "IN1_R2") (pintype "input"))
      (node (ref "E32") (pin "S2") (pinfunction "IN2_S2") (pintype "input"))
      (node (ref "E32") (pin "V1") (pinfunction "P$1_V1") (pintype "passive"))
      (node (ref "E33") (pin "A1") (pinfunction "R_A1") (pintype "input"))
      (node (ref "E33") (pin "K2") (pinfunction "R_K2") (pintype "input"))
      (node (ref "E33") (pin "U2") (pinfunction "S_U2") (pintype "input"))
    )
    (net (code "41") (name "+3V(43)") (class "Default")
      (node (ref "C12") (pin "F1") (pinfunction "IN1_F1") (pintype "input"))
      (node (ref "F19") (pin "N2") (pinfunction "IN4_N2") (pintype "input"))
      (node (ref "F20") (pin "A1") (pinfunction "IN1_A1") (pintype "input"))
      (node (ref "F20") (pin "M1") (pinfunction "IN2_M1") (pintype "input"))
      (node (ref "F20") (pin "M2") (pinfunction "IN2_M2") (pintype "input"))
      (node (ref "F20") (pin "U1") (pinfunction "P$1_U1") (pintype "passive"))
      (node (ref "F21") (pin "E2") (pinfunction "IN2_E2") (pintype "input"))
      (node (ref "F21") (pin "J2") (pinfunction "IN2_J2") (pintype "input"))
      (node (ref "F21") (pin "L1") (pinfunction "IN1_L1") (pintype "input"))
      (node (ref "F21") (pin "P2") (pinfunction "IN1_P2") (pintype "input"))
      (node (ref "F21") (pin "R1") (pinfunction "IN2_R1") (pintype "input"))
    )
    (net (code "42") (name "+3V(44)") (class "Default")
      (node (ref "F22") (pin "A1") (pinfunction "IN1_A1") (pintype "input"))
      (node (ref "F22") (pin "E1") (pinfunction "IN2_E1") (pintype "input"))
      (node (ref "F22") (pin "J1") (pinfunction "IN2_J1") (pintype "input"))
      (node (ref "F22") (pin "J2") (pinfunction "IN2_J2") (pintype "input"))
      (node (ref "F22") (pin "M1") (pinfunction "IN2_M1") (pintype "input"))
      (node (ref "F22") (pin "M2") (pinfunction "IN2_M2") (pintype "input"))
      (node (ref "F22") (pin "U1") (pinfunction "P$1_U1") (pintype "passive"))
      (node (ref "F24") (pin "D1") (pinfunction "IN4_D1") (pintype "input"))
      (node (ref "F25") (pin "B1") (pinfunction "IN2_B1") (pintype "input"))
      (node (ref "F25") (pin "E1") (pinfunction "IN2_E1") (pintype "input"))
      (node (ref "F25") (pin "M2") (pinfunction "IN2_M2") (pintype "input"))
    )
    (net (code "43") (name "+3V(45)") (class "Default")
      (node (ref "F25") (pin "R1") (pinfunction "IN2_R1") (pintype "input"))
      (node (ref "F29") (pin "B1") (pinfunction "IN2_B1") (pintype "input"))
      (node (ref "F29") (pin "E2") (pinfunction "IN2_E2") (pintype "input"))
      (node (ref "F29") (pin "H1") (pinfunction "IN1_H1") (pintype "input"))
      (node (ref "F29") (pin "H2") (pinfunction "IN1_H2") (pintype "input"))
      (node (ref "F30") (pin "B1") (pinfunction "IN2_B1") (pintype "input"))
      (node (ref "F30") (pin "C1") (pinfunction "IN3_C1") (pintype "input"))
      (node (ref "F30") (pin "D1") (pinfunction "IN4_D1") (pintype "input"))
      (node (ref "F30") (pin "F2") (pinfunction "IN3_F2") (pintype "input"))
      (node (ref "F30") (pin "H1") (pinfunction "IN2_H1") (pintype "input"))
      (node (ref "F30") (pin "L2") (pinfunction "IN2_L2") (pintype "input"))
      (node (ref "F30") (pin "M2") (pinfunction "IN3_M2") (pintype "input"))
      (node (ref "F30") (pin "N2") (pinfunction "IN4_N2") (pintype "input"))
      (node (ref "F30") (pin "V1") (pinfunction "P$1_V1") (pintype "passive"))
    )
    (net (code "44") (name "+3V(46)") (class "Default")
      (node (ref "F30") (pin "J1") (pinfunction "IN3_J1") (pintype "input"))
      (node (ref "F30") (pin "K1") (pinfunction "IN4_K1") (pintype "input"))
      (node (ref "F30") (pin "R1") (pinfunction "IN4_R1") (pintype "input"))
      (node (ref "F30") (pin "R2") (pinfunction "IN1_R2") (pintype "input"))
      (node (ref "F30") (pin "S2") (pinfunction "IN2_S2") (pintype "input"))
      (node (ref "F30") (pin "T2") (pinfunction "IN3_T2") (pintype "input"))
      (node (ref "F30") (pin "U1") (pinfunction "P$1_U1") (pintype "passive"))
      (node (ref "F31") (pin "J1") (pinfunction "IN3_J1") (pintype "input"))
      (node (ref "J30") (pin "K2") (pinfunction "K2_K2") (pintype "input"))
    )
    (net (code "45") (name "+3V(47)") (class "Default")
      (node (ref "F31") (pin "K1") (pinfunction "IN4_K1") (pintype "input"))
      (node (ref "F31") (pin "L2") (pinfunction "IN2_L2") (pintype "input"))
      (node (ref "F31") (pin "M2") (pinfunction "IN3_M2") (pintype "input"))
      (node (ref "F31") (pin "N1") (pinfunction "IN2_N1") (pintype "input"))
      (node (ref "F31") (pin "N2") (pinfunction "IN4_N2") (pintype "input"))
      (node (ref "F31") (pin "P1") (pinfunction "IN3_P1") (pintype "input"))
      (node (ref "F31") (pin "R1") (pinfunction "IN4_R1") (pintype "input"))
      (node (ref "F31") (pin "S2") (pinfunction "IN2_S2") (pintype "input"))
      (node (ref "F31") (pin "T2") (pinfunction "IN3_T2") (pintype "input"))
      (node (ref "F31") (pin "U1") (pinfunction "P$1_U1") (pintype "passive"))
      (node (ref "F31") (pin "U2") (pinfunction "IN4_U2") (pintype "input"))
    )
    (net (code "46") (name "+3V(48)") (class "Default")
      (node (ref "F31") (pin "V1") (pinfunction "P$1_V1") (pintype "passive"))
      (node (ref "F32") (pin "B1") (pinfunction "IN2_B1") (pintype "input"))
      (node (ref "F32") (pin "E2") (pinfunction "IN2_E2") (pintype "input"))
      (node (ref "F32") (pin "H1") (pinfunction "IN1_H1") (pintype "input"))
      (node (ref "F32") (pin "M2") (pinfunction "IN2_M2") (pintype "input"))
      (node (ref "F32") (pin "P2") (pinfunction "IN1_P2") (pintype "input"))
      (node (ref "F32") (pin "R1") (pinfunction "IN2_R1") (pintype "input"))
      (node (ref "F32") (pin "T2") (pinfunction "IN1_T2") (pintype "input"))
      (node (ref "F33") (pin "C1") (pinfunction "IN1C_C1") (pintype "input"))
      (node (ref "F33") (pin "D2") (pinfunction "IN1A_D2") (pintype "input"))
      (node (ref "F33") (pin "P1") (pinfunction "IN5C_P1") (pintype "input"))
    )
    (net (code "47") (name "+3V(49)") (class "Default")
      (node (ref "EF10") (pin "BF2") (pinfunction "P$1_BF2") (pintype "passive"))
      (node (ref "H07") (pin "F2") (pinfunction "IN1_F2") (pintype "input"))
      (node (ref "H07") (pin "J2") (pinfunction "IN3_J2") (pintype "input"))
      (node (ref "H07") (pin "M2") (pinfunction "IN1_M2") (pintype "input"))
      (node (ref "H07") (pin "P2") (pinfunction "IN3_P2") (pintype "input"))
      (node (ref "H07") (pin "T2") (pinfunction "IN1_T2") (pintype "input"))
      (node (ref "H07") (pin "V2") (pinfunction "IN3_V2") (pintype "input"))
      (node (ref "H08") (pin "F2") (pinfunction "IN1_F2") (pintype "input"))
      (node (ref "H08") (pin "J2") (pinfunction "IN3_J2") (pintype "input"))
      (node (ref "H08") (pin "M2") (pinfunction "IN1_M2") (pintype "input"))
      (node (ref "H08") (pin "P2") (pinfunction "IN3_P2") (pintype "input"))
      (node (ref "H08") (pin "T2") (pinfunction "IN1_T2") (pintype "input"))
      (node (ref "H08") (pin "V2") (pinfunction "IN3_V2") (pintype "input"))
    )
    (net (code "48") (name "+3V(50)") (class "Default")
      (node (ref "F11") (pin "V1") (pinfunction "P$1_V1") (pintype "passive"))
      (node (ref "H09") (pin "F2") (pinfunction "IN1_F2") (pintype "input"))
      (node (ref "H09") (pin "J2") (pinfunction "IN3_J2") (pintype "input"))
      (node (ref "H09") (pin "M2") (pinfunction "IN1_M2") (pintype "input"))
      (node (ref "H09") (pin "P2") (pinfunction "IN3_P2") (pintype "input"))
      (node (ref "H09") (pin "T2") (pinfunction "IN1_T2") (pintype "input"))
      (node (ref "H09") (pin "V2") (pinfunction "IN3_V2") (pintype "input"))
      (node (ref "H10") (pin "F2") (pinfunction "IN1_F2") (pintype "input"))
      (node (ref "H10") (pin "J2") (pinfunction "IN3_J2") (pintype "input"))
      (node (ref "H10") (pin "M2") (pinfunction "IN1_M2") (pintype "input"))
      (node (ref "H10") (pin "P2") (pinfunction "IN3_P2") (pintype "input"))
      (node (ref "H10") (pin "T2") (pinfunction "IN1_T2") (pintype "input"))
      (node (ref "H10") (pin "V2") (pinfunction "IN3_V2") (pintype "input"))
    )
    (net (code "49") (name "+3V(51)") (class "Default")
      (node (ref "F20") (pin "V1") (pinfunction "P$1_V1") (pintype "passive"))
      (node (ref "H11") (pin "F2") (pinfunction "IN1_F2") (pintype "input"))
      (node (ref "H11") (pin "J2") (pinfunction "IN3_J2") (pintype "input"))
      (node (ref "H11") (pin "M2") (pinfunction "IN1_M2") (pintype "input"))
      (node (ref "H11") (pin "P2") (pinfunction "IN3_P2") (pintype "input"))
      (node (ref "H11") (pin "T2") (pinfunction "IN1_T2") (pintype "input"))
      (node (ref "H11") (pin "V2") (pinfunction "IN3_V2") (pintype "input"))
      (node (ref "H12") (pin "F2") (pinfunction "IN1_F2") (pintype "input"))
      (node (ref "H12") (pin "J2") (pinfunction "IN3_J2") (pintype "input"))
      (node (ref "H12") (pin "M2") (pinfunction "IN1_M2") (pintype "input"))
      (node (ref "H12") (pin "P2") (pinfunction "IN3_P2") (pintype "input"))
      (node (ref "H12") (pin "T2") (pinfunction "IN1_T2") (pintype "input"))
      (node (ref "H12") (pin "V2") (pinfunction "IN3_V2") (pintype "input"))
    )
    (net (code "50") (name "+3V(52)") (class "Default")
      (node (ref "F21") (pin "U1") (pinfunction "P$1_U1") (pintype "passive"))
      (node (ref "H13") (pin "F2") (pinfunction "IN1_F2") (pintype "input"))
      (node (ref "H13") (pin "J2") (pinfunction "IN3_J2") (pintype "input"))
      (node (ref "H13") (pin "M2") (pinfunction "IN1_M2") (pintype "input"))
      (node (ref "H13") (pin "P2") (pinfunction "IN3_P2") (pintype "input"))
      (node (ref "H13") (pin "T2") (pinfunction "IN1_T2") (pintype "input"))
      (node (ref "H13") (pin "V2") (pinfunction "IN3_V2") (pintype "input"))
      (node (ref "H14") (pin "F2") (pinfunction "IN1_F2") (pintype "input"))
      (node (ref "H14") (pin "J2") (pinfunction "IN3_J2") (pintype "input"))
      (node (ref "H14") (pin "M2") (pinfunction "IN1_M2") (pintype "input"))
      (node (ref "H14") (pin "P2") (pinfunction "IN3_P2") (pintype "input"))
      (node (ref "H14") (pin "T2") (pinfunction "IN1_T2") (pintype "input"))
      (node (ref "H14") (pin "V2") (pinfunction "IN3_V2") (pintype "input"))
      (node (ref "J13") (pin "R1") (pinfunction "IN4_R1") (pintype "input"))
    )
    (net (code "51") (name "+3V(53)") (class "Default")
      (node (ref "F21") (pin "V1") (pinfunction "P$1_V1") (pintype "passive"))
      (node (ref "H15") (pin "F2") (pinfunction "IN1_F2") (pintype "input"))
      (node (ref "H15") (pin "J2") (pinfunction "IN3_J2") (pintype "input"))
      (node (ref "H15") (pin "M2") (pinfunction "IN1_M2") (pintype "input"))
      (node (ref "H15") (pin "P2") (pinfunction "IN3_P2") (pintype "input"))
      (node (ref "H15") (pin "T2") (pinfunction "IN1_T2") (pintype "input"))
      (node (ref "H15") (pin "V2") (pinfunction "IN3_V2") (pintype "input"))
      (node (ref "H16") (pin "F2") (pinfunction "IN1_F2") (pintype "input"))
      (node (ref "H16") (pin "J2") (pinfunction "IN3_J2") (pintype "input"))
      (node (ref "H16") (pin "M2") (pinfunction "IN1_M2") (pintype "input"))
      (node (ref "H16") (pin "P2") (pinfunction "IN3_P2") (pintype "input"))
      (node (ref "H16") (pin "T2") (pinfunction "IN1_T2") (pintype "input"))
      (node (ref "H16") (pin "V2") (pinfunction "IN3_V2") (pintype "input"))
    )
    (net (code "52") (name "+3V(54)") (class "Default")
      (node (ref "F22") (pin "V1") (pinfunction "P$1_V1") (pintype "passive"))
      (node (ref "H17") (pin "F2") (pinfunction "IN1_F2") (pintype "input"))
      (node (ref "H17") (pin "J2") (pinfunction "IN3_J2") (pintype "input"))
      (node (ref "H17") (pin "M2") (pinfunction "IN1_M2") (pintype "input"))
      (node (ref "H17") (pin "P2") (pinfunction "IN3_P2") (pintype "input"))
      (node (ref "H17") (pin "T2") (pinfunction "IN1_T2") (pintype "input"))
      (node (ref "H17") (pin "V2") (pinfunction "IN3_V2") (pintype "input"))
      (node (ref "H18") (pin "F2") (pinfunction "IN1_F2") (pintype "input"))
      (node (ref "H18") (pin "J2") (pinfunction "IN3_J2") (pintype "input"))
      (node (ref "H18") (pin "M2") (pinfunction "IN1_M2") (pintype "input"))
      (node (ref "H18") (pin "P2") (pinfunction "IN3_P2") (pintype "input"))
      (node (ref "H18") (pin "T2") (pinfunction "IN1_T2") (pintype "input"))
      (node (ref "H18") (pin "V2") (pinfunction "IN3_V2") (pintype "input"))
    )
    (net (code "53") (name "+3V(55)") (class "Default")
      (node (ref "E22") (pin "B1") (pinfunction "IN2_B1") (pintype "input"))
      (node (ref "E22") (pin "E1") (pinfunction "IN2_E1") (pintype "input"))
      (node (ref "E22") (pin "E2") (pinfunction "IN2_E2") (pintype "input"))
      (node (ref "E22") (pin "J1") (pinfunction "IN2_J1") (pintype "input"))
      (node (ref "E22") (pin "J2") (pinfunction "IN2_J2") (pintype "input"))
      (node (ref "F23") (pin "U1") (pinfunction "P$1_U1") (pintype "passive"))
      (node (ref "H19") (pin "F2") (pinfunction "IN1_F2") (pintype "input"))
      (node (ref "H19") (pin "J2") (pinfunction "IN3_J2") (pintype "input"))
      (node (ref "H19") (pin "M2") (pinfunction "IN1_M2") (pintype "input"))
      (node (ref "H19") (pin "P2") (pinfunction "IN3_P2") (pintype "input"))
      (node (ref "H19") (pin "T2") (pinfunction "IN1_T2") (pintype "input"))
      (node (ref "H19") (pin "V2") (pinfunction "IN3_V2") (pintype "input"))
      (node (ref "H20") (pin "F2") (pinfunction "IN1_F2") (pintype "input"))
      (node (ref "H20") (pin "J2") (pinfunction "IN3_J2") (pintype "input"))
      (node (ref "H20") (pin "M2") (pinfunction "IN1_M2") (pintype "input"))
      (node (ref "H20") (pin "P2") (pinfunction "IN3_P2") (pintype "input"))
    )
    (net (code "54") (name "+3V(56)") (class "Default")
      (node (ref "F23") (pin "V1") (pinfunction "P$1_V1") (pintype "passive"))
      (node (ref "J13") (pin "C1") (pinfunction "IN3_C1") (pintype "input"))
      (node (ref "J13") (pin "D1") (pinfunction "IN4_D1") (pintype "input"))
      (node (ref "J13") (pin "F2") (pinfunction "IN3_F2") (pintype "input"))
      (node (ref "J13") (pin "H2") (pinfunction "IN4_H2") (pintype "input"))
      (node (ref "J13") (pin "J1") (pinfunction "IN3_J1") (pintype "input"))
      (node (ref "J13") (pin "K1") (pinfunction "IN4_K1") (pintype "input"))
      (node (ref "J13") (pin "M2") (pinfunction "IN3_M2") (pintype "input"))
      (node (ref "J13") (pin "N2") (pinfunction "IN4_N2") (pintype "input"))
    )
    (net (code "55") (name "+3V(57)") (class "Default")
      (node (ref "C07") (pin "F2") (pinfunction "IN3_F2") (pintype "input"))
      (node (ref "C07") (pin "H2") (pinfunction "IN2_H2") (pintype "input"))
      (node (ref "C07") (pin "N2") (pinfunction "IN2_N2") (pintype "input"))
      (node (ref "C07") (pin "P2") (pinfunction "IN3_P2") (pintype "input"))
      (node (ref "C08") (pin "H2") (pinfunction "IN1_H2") (pintype "input"))
      (node (ref "C08") (pin "N2") (pinfunction "IN1_N2") (pintype "input"))
      (node (ref "C08") (pin "U2") (pinfunction "IN1_U2") (pintype "input"))
      (node (ref "C09") (pin "E1") (pinfunction "IN2_E1") (pintype "input"))
      (node (ref "C09") (pin "J1") (pinfunction "IN2_J1") (pintype "input"))
      (node (ref "C09") (pin "M1") (pinfunction "IN2_M1") (pintype "input"))
      (node (ref "C09") (pin "M2") (pinfunction "IN2_M2") (pintype "input"))
      (node (ref "C09") (pin "R1") (pinfunction "IN2_R1") (pintype "input"))
      (node (ref "C09") (pin "R2") (pinfunction "IN2_R2") (pintype "input"))
      (node (ref "D10") (pin "V1") (pinfunction "P$1_V1") (pintype "passive"))
      (node (ref "D11") (pin "K2") (pinfunction "R_K2") (pintype "input"))
      (node (ref "D11") (pin "N2") (pinfunction "S_N2") (pintype "input"))
    )
    (net (code "56") (name "+3V(58)") (class "Default")
      (node (ref "D07") (pin "E2") (pinfunction "IN2_E2") (pintype "input"))
      (node (ref "D07") (pin "H1") (pinfunction "IN1_H1") (pintype "input"))
      (node (ref "D07") (pin "P1") (pinfunction "IN1_P1") (pintype "input"))
      (node (ref "D07") (pin "P2") (pinfunction "IN1_P2") (pintype "input"))
      (node (ref "D07") (pin "U1") (pinfunction "P$1_U1") (pintype "passive"))
      (node (ref "D09") (pin "H1") (pinfunction "IN3_H1") (pintype "input"))
      (node (ref "D09") (pin "R1") (pinfunction "IN2_R1") (pintype "input"))
      (node (ref "D09") (pin "V2") (pinfunction "IN3_V2") (pintype "input"))
      (node (ref "D10") (pin "E2") (pinfunction "IN2_E2") (pintype "input"))
      (node (ref "E09") (pin "L2") (pinfunction "IN1_L2") (pintype "input"))
      (node (ref "E09") (pin "P1") (pinfunction "IN1_P1") (pintype "input"))
      (node (ref "E09") (pin "P2") (pinfunction "IN1_P2") (pintype "input"))
    )
    (net (code "57") (name "+3V(61)") (class "Default")
      (node (ref "C12") (pin "J1") (pinfunction "IN3_J1") (pintype "input"))
      (node (ref "C12") (pin "K1") (pinfunction "IN4_K1") (pintype "input"))
      (node (ref "C12") (pin "N2") (pinfunction "IN4_N2") (pintype "input"))
      (node (ref "C12") (pin "U1") (pinfunction "P$1_U1") (pintype "passive"))
    )
    (net (code "58") (name "+3V(62)") (class "Default")
      (node (ref "A05") (pin "U1") (pinfunction "P$1_U1") (pintype "passive"))
      (node (ref "B06") (pin "J2") (pinfunction "IN2_J2") (pintype "input"))
    )
    (net (code "59") (name "+3V(63)") (class "Default")
      (node (ref "B05") (pin "R1") (pinfunction "S_R1") (pintype "input"))
      (node (ref "B06") (pin "U2") (pinfunction "IN2_U2") (pintype "input"))
      (node (ref "B06") (pin "V1") (pinfunction "P$1_V1") (pintype "passive"))
    )
    (net (code "60") (name "+3V(64)") (class "Default")
      (node (ref "B04") (pin "F2") (pinfunction "IN3_F2") (pintype "input"))
      (node (ref "B05") (pin "D1") (pinfunction "S_D1") (pintype "input"))
      (node (ref "B06") (pin "U1") (pinfunction "P$1_U1") (pintype "passive"))
    )
    (net (code "61") (name "+3V(65)") (class "Default")
      (node (ref "A05") (pin "D1") (pinfunction "IN1_D1") (pintype "input"))
      (node (ref "A06") (pin "D2") (pinfunction "IN1_D2") (pintype "input"))
      (node (ref "A06") (pin "E1") (pinfunction "IN2_E1") (pintype "input"))
      (node (ref "A06") (pin "U1") (pinfunction "P$1_U1") (pintype "passive"))
      (node (ref "B05") (pin "F2") (pinfunction "S_F2") (pintype "input"))
      (node (ref "B05") (pin "N2") (pinfunction "S_N2") (pintype "input"))
    )
    (net (code "62") (name "+3V(66)") (class "Default")
      (node (ref "A05") (pin "T2") (pinfunction "IN1_T2") (pintype "input"))
      (node (ref "A06") (pin "R2") (pinfunction "IN2_R2") (pintype "input"))
      (node (ref "A11") (pin "U1") (pinfunction "P$1_U1") (pintype "passive"))
    )
    (net (code "63") (name "+3V(67)") (class "Default")
      (node (ref "A06") (pin "M1") (pinfunction "IN2_M1") (pintype "input"))
      (node (ref "A06") (pin "M2") (pinfunction "IN2_M2") (pintype "input"))
      (node (ref "A06") (pin "V1") (pinfunction "P$1_V1") (pintype "passive"))
      (node (ref "B04") (pin "V2") (pinfunction "IN3_V2") (pintype "input"))
    )
    (net (code "64") (name "+3V(68)") (class "Default")
      (node (ref "F08") (pin "P2") (pinfunction "IN2_P2") (pintype "input"))
      (node (ref "F09") (pin "H2") (pinfunction "IN8_H2") (pintype "input"))
      (node (ref "F09") (pin "U1") (pinfunction "P$1_U1") (pintype "passive"))
    )
    (net (code "65") (name "+3V(69)") (class "Default")
      (node (ref "E11") (pin "R1") (pinfunction "IN2_R1") (pintype "input"))
      (node (ref "F09") (pin "F1") (pinfunction "IN1_F1") (pintype "input"))
      (node (ref "F09") (pin "H1") (pinfunction "IN2_H1") (pintype "input"))
      (node (ref "F09") (pin "J1") (pinfunction "IN3_J1") (pintype "input"))
      (node (ref "F11") (pin "F1") (pinfunction "IN1_F1") (pintype "input"))
      (node (ref "F11") (pin "R1") (pinfunction "IN4_R1") (pintype "input"))
      (node (ref "F11") (pin "S2") (pinfunction "IN2_S2") (pintype "input"))
      (node (ref "F11") (pin "U1") (pinfunction "P$1_U1") (pintype "passive"))
    )
    (net (code "66") (name "+3VC01") (class "Default")
      (node (ref "C01") (pin "V2") (pinfunction "P$2_V2") (pintype "bidirectional"))
      (node (ref "HJ28") (pin "BU2") (pinfunction "P$1_BU2") (pintype "passive"))
    )
    (net (code "67") (name "-6V") (class "Default")
      (node (ref "AB02") (pin "BM2") (pinfunction "-6V_BM2") (pintype "power_in"))
    )
    (net (code "68") (name "-15V") (class "Default")
      (node (ref "D01") (pin "B2") (pinfunction "P$2_B2") (pintype "bidirectional"))
      (node (ref "D03") (pin "B2") (pinfunction "P$2_B2") (pintype "bidirectional"))
    )
    (net (code "69") (name "-30V") (class "Default")
      (node (ref "AB02") (pin "BV2") (pinfunction "-30V_BV2") (pintype "power_in"))
      (node (ref "HJ23") (pin "AV2") (pinfunction "-30V_AV2") (pintype "power_in"))
      (node (ref "J12") (pin "V2") (pinfunction "-30V_V2") (pintype "power_in"))
    )
    (net (code "70") (name "0_TO_INT_ENAB_") (class "Default")
      (node (ref "E26") (pin "V2") (pinfunction "OUT_V2") (pintype "output"))
      (node (ref "E33") (pin "R1") (pinfunction "S_R1") (pintype "input"))
    )
    (net (code "71") (name "3_CYCLE") (class "Default")
      (node (ref "F22") (pin "T2") (pinfunction "IN1_T2") (pintype "input"))
      (node (ref "J20") (pin "J2") (pinfunction "OUT_J2") (pintype "output"))
    )
    (net (code "72") (name "60HZ_IN") (class "Default")
      (node (ref "J30") (pin "R2") (pinfunction "R2_R2") (pintype "input"))
    )
    (net (code "73") (name "AC00") (class "Default")
      (node (ref "C14") (pin "E1") (pinfunction "IN2_E1") (pintype "input"))
      (node (ref "D15") (pin "E1") (pinfunction "IN2_E1") (pintype "input"))
      (node (ref "D18") (pin "J2") (pinfunction "IN1_J2") (pintype "input"))
      (node (ref "E24") (pin "L1") (pinfunction "IN1_L1") (pintype "input"))
      (node (ref "EF34") (pin "BA1") (pinfunction "BA1_BA1") (pintype "output"))
      (node (ref "F33") (pin "N2") (pinfunction "IN4A_N2") (pintype "input"))
      (node (ref "H07") (pin "H2") (pinfunction "IN2_H2") (pintype "input"))
      (node (ref "HJ31") (pin "AE1") (pinfunction "AE1_AE1") (pintype "input"))
    )
    (net (code "74") (name "AC00_") (class "Default")
      (node (ref "D15") (pin "A1") (pinfunction "IN1_A1") (pintype "input"))
      (node (ref "E40") (pin "V2") (pinfunction "P$2_V2") (pintype "bidirectional"))
      (node (ref "EF34") (pin "BB1") (pinfunction "BB1_BB1") (pintype "output"))
      (node (ref "F24") (pin "K2") (pinfunction "IN1_K2") (pintype "input"))
    )
    (net (code "75") (name "AC01") (class "Default")
      (node (ref "C14") (pin "J2") (pinfunction "IN2_J2") (pintype "input"))
      (node (ref "D14") (pin "L1") (pinfunction "IN1_L1") (pintype "input"))
      (node (ref "D15") (pin "B1") (pinfunction "IN2_B1") (pintype "input"))
      (node (ref "EF34") (pin "AV1") (pinfunction "AV1_AV1") (pintype "output"))
      (node (ref "H07") (pin "N2") (pinfunction "IN2_N2") (pintype "input"))
      (node (ref "HJ31") (pin "BA1") (pinfunction "BA1_BA1") (pintype "input"))
    )
    (net (code "76") (name "AC01_") (class "Default")
      (node (ref "D15") (pin "D1") (pinfunction "IN1_D1") (pintype "input"))
      (node (ref "D16") (pin "H2") (pinfunction "IN1_H2") (pintype "input"))
      (node (ref "E40") (pin "T2") (pinfunction "P$2_T2") (pintype "bidirectional"))
      (node (ref "EF34") (pin "AV2") (pinfunction "AV2_AV2") (pintype "output"))
      (node (ref "F24") (pin "L2") (pinfunction "IN2_L2") (pintype "input"))
    )
    (net (code "77") (name "AC02") (class "Default")
      (node (ref "C14") (pin "R1") (pinfunction "IN2_R1") (pintype "input"))
      (node (ref "D16") (pin "J2") (pinfunction "IN2_J2") (pintype "input"))
      (node (ref "EF35") (pin "BA1") (pinfunction "BA1_BA1") (pintype "output"))
      (node (ref "H07") (pin "U2") (pinfunction "IN2_U2") (pintype "input"))
      (node (ref "HJ24") (pin "AE2") (pinfunction "AE2_AE2") (pintype "input"))
      (node (ref "HJ25") (pin "AE2") (pinfunction "AE2_AE2") (pintype "input"))
      (node (ref "HJ31") (pin "AV1") (pinfunction "AV1_AV1") (pintype "input"))
    )
    (net (code "78") (name "AC02_") (class "Default")
      (node (ref "D14") (pin "M1") (pinfunction "IN2_M1") (pintype "input"))
      (node (ref "D20") (pin "D1") (pinfunction "IN4_D1") (pintype "input"))
      (node (ref "E40") (pin "J1") (pinfunction "P$2_J1") (pintype "bidirectional"))
      (node (ref "EF35") (pin "BB1") (pinfunction "BB1_BB1") (pintype "output"))
      (node (ref "F24") (pin "M2") (pinfunction "IN3_M2") (pintype "input"))
    )
    (net (code "79") (name "AC03") (class "Default")
      (node (ref "C15") (pin "E1") (pinfunction "IN2_E1") (pintype "input"))
      (node (ref "EF35") (pin "AV1") (pinfunction "AV1_AV1") (pintype "output"))
      (node (ref "H08") (pin "H2") (pinfunction "IN2_H2") (pintype "input"))
      (node (ref "HJ24") (pin "AF2") (pinfunction "AF2_AF2") (pintype "input"))
      (node (ref "HJ25") (pin "AF2") (pinfunction "AF2_AF2") (pintype "input"))
      (node (ref "HJ31") (pin "AH1") (pinfunction "AH1_AH1") (pintype "input"))
    )
    (net (code "80") (name "AC03_") (class "Default")
      (node (ref "D19") (pin "K1") (pinfunction "IN1_K1") (pintype "input"))
      (node (ref "D20") (pin "C1") (pinfunction "IN3_C1") (pintype "input"))
      (node (ref "E40") (pin "H2") (pinfunction "P$2_H2") (pintype "bidirectional"))
      (node (ref "EF35") (pin "AV2") (pinfunction "AV2_AV2") (pintype "output"))
      (node (ref "F24") (pin "N2") (pinfunction "IN4_N2") (pintype "input"))
    )
    (net (code "81") (name "AC04") (class "Default")
      (node (ref "C15") (pin "J2") (pinfunction "IN2_J2") (pintype "input"))
      (node (ref "EF02") (pin "AP2") (pinfunction "AP2_AP2") (pintype "input"))
      (node (ref "EF36") (pin "BA1") (pinfunction "BA1_BA1") (pintype "output"))
      (node (ref "H08") (pin "N2") (pinfunction "IN2_N2") (pintype "input"))
      (node (ref "HJ24") (pin "AM2") (pinfunction "AM2_AM2") (pintype "input"))
      (node (ref "HJ25") (pin "AM2") (pinfunction "AM2_AM2") (pintype "input"))
      (node (ref "HJ28") (pin "AH1") (pinfunction "AH1_AH1") (pintype "input"))
      (node (ref "HJ31") (pin "AU2") (pinfunction "AU2_AU2") (pintype "input"))
    )
    (net (code "82") (name "AC04_") (class "Default")
      (node (ref "E40") (pin "M1") (pinfunction "P$2_M1") (pintype "bidirectional"))
      (node (ref "EF36") (pin "BB1") (pinfunction "BB1_BB1") (pintype "output"))
      (node (ref "F24") (pin "M1") (pinfunction "IN1_M1") (pintype "input"))
    )
    (net (code "83") (name "AC05") (class "Default")
      (node (ref "C15") (pin "R1") (pinfunction "IN2_R1") (pintype "input"))
      (node (ref "EF02") (pin "AR2") (pinfunction "AR2_AR2") (pintype "input"))
      (node (ref "EF36") (pin "AV1") (pinfunction "AV1_AV1") (pintype "output"))
      (node (ref "H08") (pin "U2") (pinfunction "IN2_U2") (pintype "input"))
      (node (ref "HJ24") (pin "AN2") (pinfunction "AN2_AN2") (pintype "input"))
      (node (ref "HJ25") (pin "AN2") (pinfunction "AN2_AN2") (pintype "input"))
      (node (ref "HJ28") (pin "AH2") (pinfunction "AH2_AH2") (pintype "input"))
      (node (ref "HJ31") (pin "AK1") (pinfunction "AK1_AK1") (pintype "input"))
    )
    (net (code "84") (name "AC05_") (class "Default")
      (node (ref "E40") (pin "B1") (pinfunction "P$2_B1") (pintype "bidirectional"))
      (node (ref "EF36") (pin "AV2") (pinfunction "AV2_AV2") (pintype "output"))
      (node (ref "F24") (pin "N1") (pinfunction "IN2_N1") (pintype "input"))
    )
    (net (code "85") (name "AC06") (class "Default")
      (node (ref "C16") (pin "E1") (pinfunction "IN2_E1") (pintype "input"))
      (node (ref "EF02") (pin "AL2") (pinfunction "AL2_AL2") (pintype "input"))
      (node (ref "EF37") (pin "BA1") (pinfunction "BA1_BA1") (pintype "output"))
      (node (ref "H09") (pin "H2") (pinfunction "IN2_H2") (pintype "input"))
      (node (ref "HJ24") (pin "AS2") (pinfunction "AS2_AS2") (pintype "input"))
      (node (ref "HJ25") (pin "AS2") (pinfunction "AS2_AS2") (pintype "input"))
      (node (ref "HJ28") (pin "AF1") (pinfunction "AF1_AF1") (pintype "input"))
      (node (ref "HJ31") (pin "AT2") (pinfunction "AT2_AT2") (pintype "input"))
    )
    (net (code "86") (name "AC06_") (class "Default")
      (node (ref "EF37") (pin "BB1") (pinfunction "BB1_BB1") (pintype "output"))
      (node (ref "F24") (pin "P1") (pinfunction "IN3_P1") (pintype "input"))
      (node (ref "F40") (pin "V2") (pinfunction "P$2_V2") (pintype "bidirectional"))
    )
    (net (code "87") (name "AC07") (class "Default")
      (node (ref "C16") (pin "J2") (pinfunction "IN2_J2") (pintype "input"))
      (node (ref "EF02") (pin "AM2") (pinfunction "AM2_AM2") (pintype "input"))
      (node (ref "EF37") (pin "AV1") (pinfunction "AV1_AV1") (pintype "output"))
      (node (ref "H09") (pin "N2") (pinfunction "IN2_N2") (pintype "input"))
      (node (ref "HJ24") (pin "AT2") (pinfunction "AT2_AT2") (pintype "input"))
      (node (ref "HJ25") (pin "AT2") (pinfunction "AT2_AT2") (pintype "input"))
      (node (ref "HJ28") (pin "AF2") (pinfunction "AF2_AF2") (pintype "input"))
      (node (ref "HJ31") (pin "AL1") (pinfunction "AL1_AL1") (pintype "input"))
    )
    (net (code "88") (name "AC07_") (class "Default")
      (node (ref "EF37") (pin "AV2") (pinfunction "AV2_AV2") (pintype "output"))
      (node (ref "F24") (pin "R1") (pinfunction "IN4_R1") (pintype "input"))
      (node (ref "F40") (pin "T2") (pinfunction "P$2_T2") (pintype "bidirectional"))
    )
    (net (code "89") (name "AC08") (class "Default")
      (node (ref "C16") (pin "R1") (pinfunction "IN2_R1") (pintype "input"))
      (node (ref "EF02") (pin "AU2") (pinfunction "AU2_AU2") (pintype "input"))
      (node (ref "EF38") (pin "BA1") (pinfunction "BA1_BA1") (pintype "output"))
      (node (ref "H09") (pin "U2") (pinfunction "IN2_U2") (pintype "input"))
      (node (ref "HJ24") (pin "BD2") (pinfunction "BD2_BD2") (pintype "input"))
      (node (ref "HJ25") (pin "BD2") (pinfunction "BD2_BD2") (pintype "input"))
      (node (ref "HJ28") (pin "AE1") (pinfunction "AE1_AE1") (pintype "input"))
      (node (ref "HJ31") (pin "AR1") (pinfunction "AR1_AR1") (pintype "input"))
    )
    (net (code "90") (name "AC08_") (class "Default")
      (node (ref "EF38") (pin "BB1") (pinfunction "BB1_BB1") (pintype "output"))
      (node (ref "F24") (pin "R2") (pinfunction "IN1_R2") (pintype "input"))
      (node (ref "F40") (pin "J1") (pinfunction "P$2_J1") (pintype "bidirectional"))
    )
    (net (code "91") (name "AC09") (class "Default")
      (node (ref "C17") (pin "E1") (pinfunction "IN2_E1") (pintype "input"))
      (node (ref "EF02") (pin "AS2") (pinfunction "AS2_AS2") (pintype "input"))
      (node (ref "EF38") (pin "AV1") (pinfunction "AV1_AV1") (pintype "output"))
      (node (ref "H10") (pin "H2") (pinfunction "IN2_H2") (pintype "input"))
      (node (ref "HJ24") (pin "BE2") (pinfunction "BE2_BE2") (pintype "input"))
      (node (ref "HJ25") (pin "BE2") (pinfunction "BE2_BE2") (pintype "input"))
      (node (ref "HJ28") (pin "AE2") (pinfunction "AE2_AE2") (pintype "input"))
      (node (ref "HJ31") (pin "AN2") (pinfunction "AN2_AN2") (pintype "input"))
    )
    (net (code "92") (name "AC09_") (class "Default")
      (node (ref "EF38") (pin "AV2") (pinfunction "AV2_AV2") (pintype "output"))
      (node (ref "F24") (pin "S2") (pinfunction "IN2_S2") (pintype "input"))
      (node (ref "F40") (pin "H2") (pinfunction "P$2_H2") (pintype "bidirectional"))
    )
    (net (code "93") (name "AC10") (class "Default")
      (node (ref "C17") (pin "J2") (pinfunction "IN2_J2") (pintype "input"))
      (node (ref "EF02") (pin "AT2") (pinfunction "AT2_AT2") (pintype "input"))
      (node (ref "EF39") (pin "BA1") (pinfunction "BA1_BA1") (pintype "output"))
      (node (ref "H10") (pin "N2") (pinfunction "IN2_N2") (pintype "input"))
      (node (ref "HJ24") (pin "BH2") (pinfunction "BH2_BH2") (pintype "input"))
      (node (ref "HJ25") (pin "BH2") (pinfunction "BH2_BH2") (pintype "input"))
      (node (ref "HJ28") (pin "AD1") (pinfunction "AD1_AD1") (pintype "input"))
      (node (ref "HJ31") (pin "AR2") (pinfunction "AR2_AR2") (pintype "input"))
    )
    (net (code "94") (name "AC10_") (class "Default")
      (node (ref "EF39") (pin "BB1") (pinfunction "BB1_BB1") (pintype "output"))
      (node (ref "F24") (pin "T2") (pinfunction "IN3_T2") (pintype "input"))
      (node (ref "F40") (pin "M1") (pinfunction "P$2_M1") (pintype "bidirectional"))
    )
    (net (code "95") (name "AC11") (class "Default")
      (node (ref "C17") (pin "R1") (pinfunction "IN2_R1") (pintype "input"))
      (node (ref "EF02") (pin "AU1") (pinfunction "AU1_AU1") (pintype "input"))
      (node (ref "EF39") (pin "AV1") (pinfunction "AV1_AV1") (pintype "output"))
      (node (ref "H10") (pin "U2") (pinfunction "IN2_U2") (pintype "input"))
      (node (ref "HJ24") (pin "BJ2") (pinfunction "BJ2_BJ2") (pintype "input"))
      (node (ref "HJ25") (pin "BJ2") (pinfunction "BJ2_BJ2") (pintype "input"))
      (node (ref "HJ28") (pin "AD2") (pinfunction "AD2_AD2") (pintype "input"))
      (node (ref "HJ31") (pin "AP1") (pinfunction "AP1_AP1") (pintype "input"))
    )
    (net (code "96") (name "AC11_") (class "Default")
      (node (ref "EF39") (pin "AV2") (pinfunction "AV2_AV2") (pintype "output"))
      (node (ref "F24") (pin "U2") (pinfunction "IN4_U2") (pintype "input"))
      (node (ref "F40") (pin "B1") (pinfunction "P$2_B1") (pintype "bidirectional"))
    )
    (net (code "97") (name "ACBAR_ENABLE") (class "Default")
      (node (ref "E32") (pin "V2") (pinfunction "OUT_V2") (pintype "output"))
      (node (ref "EF34") (pin "BJ2") (pinfunction "BJ2_BJ2") (pintype "input"))
      (node (ref "EF35") (pin "BJ2") (pinfunction "BJ2_BJ2") (pintype "input"))
      (node (ref "EF36") (pin "BJ2") (pinfunction "BJ2_BJ2") (pintype "input"))
      (node (ref "EF37") (pin "BJ2") (pinfunction "BJ2_BJ2") (pintype "input"))
      (node (ref "EF38") (pin "BJ2") (pinfunction "BJ2_BJ2") (pintype "input"))
      (node (ref "EF39") (pin "BJ2") (pinfunction "BJ2_BJ2") (pintype "input"))
    )
    (net (code "98") (name "AC_CLEAR") (class "Default")
      (node (ref "F29") (pin "J2") (pinfunction "IN2_J2") (pintype "input"))
      (node (ref "J15") (pin "L1") (pinfunction "OUT_L1") (pintype "output"))
    )
    (net (code "99") (name "AC_CLEAR_") (class "Default")
      (node (ref "E30") (pin "K2") (pinfunction "IN2B_K2") (pintype "input"))
      (node (ref "F29") (pin "K2") (pinfunction "OUT_K2") (pintype "output"))
    )
    (net (code "100") (name "AC_ENABLE") (class "Default")
      (node (ref "E32") (pin "S1") (pinfunction "OUT_S1") (pintype "output"))
      (node (ref "EF34") (pin "BH2") (pinfunction "BH2_BH2") (pintype "input"))
      (node (ref "EF35") (pin "BH2") (pinfunction "BH2_BH2") (pintype "input"))
      (node (ref "EF36") (pin "BH2") (pinfunction "BH2_BH2") (pintype "input"))
      (node (ref "EF37") (pin "BH2") (pinfunction "BH2_BH2") (pintype "input"))
      (node (ref "EF38") (pin "BH2") (pinfunction "BH2_BH2") (pintype "input"))
      (node (ref "EF39") (pin "BH2") (pinfunction "BH2_BH2") (pintype "input"))
    )
    (net (code "101") (name "AC_LOAD") (class "Default")
      (node (ref "E32") (pin "P2") (pinfunction "OUT_P2") (pintype "output"))
      (node (ref "E33") (pin "S2") (pinfunction "C_S2") (pintype "input"))
      (node (ref "EF34") (pin "AU1") (pinfunction "AU1_AU1") (pintype "input"))
      (node (ref "EF35") (pin "AU1") (pinfunction "AU1_AU1") (pintype "input"))
      (node (ref "EF36") (pin "AU1") (pinfunction "AU1_AU1") (pintype "input"))
      (node (ref "EF37") (pin "AU1") (pinfunction "AU1_AU1") (pintype "input"))
      (node (ref "EF38") (pin "AU1") (pinfunction "AU1_AU1") (pintype "input"))
      (node (ref "EF39") (pin "AU1") (pinfunction "AU1_AU1") (pintype "input"))
    )
    (net (code "102") (name "AC_TO_MQ_ENABLE") (class "Default")
      (node (ref "C14") (pin "D1") (pinfunction "IN1_D1") (pintype "input"))
      (node (ref "C14") (pin "H2") (pinfunction "IN1_H2") (pintype "input"))
      (node (ref "C14") (pin "P1") (pinfunction "IN1_P1") (pintype "input"))
      (node (ref "C15") (pin "D1") (pinfunction "IN1_D1") (pintype "input"))
      (node (ref "C15") (pin "H2") (pinfunction "IN1_H2") (pintype "input"))
      (node (ref "C15") (pin "P1") (pinfunction "IN1_P1") (pintype "input"))
      (node (ref "C16") (pin "D1") (pinfunction "IN1_D1") (pintype "input"))
      (node (ref "C16") (pin "H2") (pinfunction "IN1_H2") (pintype "input"))
      (node (ref "C16") (pin "P1") (pinfunction "IN1_P1") (pintype "input"))
      (node (ref "C17") (pin "D1") (pinfunction "IN1_D1") (pintype "input"))
      (node (ref "C17") (pin "H2") (pinfunction "IN1_H2") (pintype "input"))
      (node (ref "C17") (pin "P1") (pinfunction "IN1_P1") (pintype "input"))
      (node (ref "D15") (pin "S1") (pinfunction "OUT_S1") (pintype "output"))
    )
    (net (code "103") (name "AC_TO_MQ_ENABLE_") (class "Default")
      (node (ref "D15") (pin "R1") (pinfunction "IN2_R1") (pintype "input"))
      (node (ref "D21") (pin "L1") (pinfunction "OUT_L1") (pintype "output"))
      (node (ref "E30") (pin "F2") (pinfunction "IN1C_F2") (pintype "input"))
    )
    (net (code "104") (name "ADDER00") (class "Default")
      (node (ref "EF34") (pin "AE2") (pinfunction "AE2_AE2") (pintype "output"))
      (node (ref "EF35") (pin "AB1") (pinfunction "AB1_AB1") (pintype "input"))
      (node (ref "EF39") (pin "AJ2") (pinfunction "AJ2_AJ2") (pintype "input"))
      (node (ref "F33") (pin "K1") (pinfunction "IN4A_K1") (pintype "input"))
    )
    (net (code "105") (name "ADDER01") (class "Default")
      (node (ref "EF34") (pin "AF1") (pinfunction "AF1_AF1") (pintype "output"))
      (node (ref "EF35") (pin "AC1") (pinfunction "AC1_AC1") (pintype "input"))
      (node (ref "F33") (pin "M1") (pinfunction "IN5A_M1") (pintype "input"))
    )
    (net (code "106") (name "ADDER02") (class "Default")
      (node (ref "EF34") (pin "AH2") (pinfunction "AH2_AH2") (pintype "input"))
      (node (ref "EF35") (pin "AE2") (pinfunction "AE2_AE2") (pintype "output"))
      (node (ref "EF35") (pin "BB2") (pinfunction "BB2_BB2") (pintype "input"))
      (node (ref "EF36") (pin "AB1") (pinfunction "AB1_AB1") (pintype "input"))
    )
    (net (code "107") (name "ADDER03") (class "Default")
      (node (ref "EF34") (pin "AJ2") (pinfunction "AJ2_AJ2") (pintype "input"))
      (node (ref "EF35") (pin "AF1") (pinfunction "AF1_AF1") (pintype "output"))
      (node (ref "EF36") (pin "AC1") (pinfunction "AC1_AC1") (pintype "input"))
    )
    (net (code "108") (name "ADDER04") (class "Default")
      (node (ref "EF35") (pin "AH2") (pinfunction "AH2_AH2") (pintype "input"))
      (node (ref "EF36") (pin "AE2") (pinfunction "AE2_AE2") (pintype "output"))
      (node (ref "EF36") (pin "BB2") (pinfunction "BB2_BB2") (pintype "input"))
      (node (ref "EF37") (pin "AB1") (pinfunction "AB1_AB1") (pintype "input"))
    )
    (net (code "109") (name "ADDER05") (class "Default")
      (node (ref "EF35") (pin "AJ2") (pinfunction "AJ2_AJ2") (pintype "input"))
      (node (ref "EF36") (pin "AF1") (pinfunction "AF1_AF1") (pintype "output"))
      (node (ref "EF37") (pin "AC1") (pinfunction "AC1_AC1") (pintype "input"))
    )
    (net (code "110") (name "ADDER06") (class "Default")
      (node (ref "EF36") (pin "AH2") (pinfunction "AH2_AH2") (pintype "input"))
      (node (ref "EF37") (pin "AE2") (pinfunction "AE2_AE2") (pintype "output"))
      (node (ref "EF37") (pin "BB2") (pinfunction "BB2_BB2") (pintype "input"))
      (node (ref "EF38") (pin "AB1") (pinfunction "AB1_AB1") (pintype "input"))
    )
    (net (code "111") (name "ADDER07") (class "Default")
      (node (ref "EF36") (pin "AJ2") (pinfunction "AJ2_AJ2") (pintype "input"))
      (node (ref "EF37") (pin "AF1") (pinfunction "AF1_AF1") (pintype "output"))
      (node (ref "EF38") (pin "AC1") (pinfunction "AC1_AC1") (pintype "input"))
    )
    (net (code "112") (name "ADDER08") (class "Default")
      (node (ref "EF37") (pin "AH2") (pinfunction "AH2_AH2") (pintype "input"))
      (node (ref "EF38") (pin "AE2") (pinfunction "AE2_AE2") (pintype "output"))
      (node (ref "EF38") (pin "BB2") (pinfunction "BB2_BB2") (pintype "input"))
      (node (ref "EF39") (pin "AB1") (pinfunction "AB1_AB1") (pintype "input"))
    )
    (net (code "113") (name "ADDER09") (class "Default")
      (node (ref "EF37") (pin "AJ2") (pinfunction "AJ2_AJ2") (pintype "input"))
      (node (ref "EF38") (pin "AF1") (pinfunction "AF1_AF1") (pintype "output"))
      (node (ref "EF39") (pin "AC1") (pinfunction "AC1_AC1") (pintype "input"))
    )
    (net (code "114") (name "ADDER10") (class "Default")
      (node (ref "EF38") (pin "AH2") (pinfunction "AH2_AH2") (pintype "input"))
      (node (ref "EF39") (pin "AE2") (pinfunction "AE2_AE2") (pintype "output"))
      (node (ref "EF39") (pin "BB2") (pinfunction "BB2_BB2") (pintype "input"))
      (node (ref "F33") (pin "E1") (pinfunction "IN2A_E1") (pintype "input"))
    )
    (net (code "115") (name "ADDER11") (class "Default")
      (node (ref "EF34") (pin "AB1") (pinfunction "AB1_AB1") (pintype "input"))
      (node (ref "EF38") (pin "AJ2") (pinfunction "AJ2_AJ2") (pintype "input"))
      (node (ref "EF39") (pin "AF1") (pinfunction "AF1_AF1") (pintype "output"))
      (node (ref "F32") (pin "P1") (pinfunction "IN1_P1") (pintype "input"))
    )
    (net (code "116") (name "ADDER11_") (class "Default")
      (node (ref "C14") (pin "B1") (pinfunction "IN2_B1") (pintype "input"))
      (node (ref "F28") (pin "P1") (pinfunction "IN1_P1") (pintype "input"))
      (node (ref "F32") (pin "S1") (pinfunction "OUT_S1") (pintype "output"))
    )
    (net (code "117") (name "ADDER_L") (class "Default")
      (node (ref "C18") (pin "V2") (pinfunction "OUT_V2") (pintype "output"))
      (node (ref "D19") (pin "F1") (pinfunction "IN2_F1") (pintype "input"))
      (node (ref "D23") (pin "L2") (pinfunction "IN3A_L2") (pintype "input"))
    )
    (net (code "118") (name "ADDER_L_") (class "Default")
      (node (ref "C18") (pin "T2") (pinfunction "IN1_T2") (pintype "input"))
      (node (ref "D23") (pin "K2") (pinfunction "IN2B_K2") (pintype "input"))
      (node (ref "E24") (pin "B1") (pinfunction "IN2_B1") (pintype "input"))
      (node (ref "EF34") (pin "AC1") (pinfunction "AC1_AC1") (pintype "input"))
      (node (ref "EF34") (pin "BB2") (pinfunction "BB2_BB2") (pintype "input"))
      (node (ref "F33") (pin "H1") (pinfunction "IN3A_H1") (pintype "input"))
      (node (ref "F33") (pin "V2") (pinfunction "OUT_V2") (pintype "output"))
    )
    (net (code "119") (name "ADD_") (class "Default")
      (node (ref "E32") (pin "P1") (pinfunction "IN3_P1") (pintype "input"))
      (node (ref "F28") (pin "D1") (pinfunction "OUT_D1") (pintype "output"))
      (node (ref "F31") (pin "A1") (pinfunction "IN1_A1") (pintype "input"))
    )
    (net (code "120") (name "ADD_ACCEPTED_") (class "Default")
      (node (ref "E33") (pin "E1") (pinfunction "1_E1") (pintype "output"))
      (node (ref "H20") (pin "N2") (pinfunction "IN2_N2") (pintype "input"))
    )
    (net (code "121") (name "AND") (class "Default")
      (node (ref "E22") (pin "C1") (pinfunction "OUT_C1") (pintype "output"))
      (node (ref "F26") (pin "P1") (pinfunction "IN1_P1") (pintype "input"))
    )
    (net (code "122") (name "AND_") (class "Default")
      (node (ref "D40") (pin "M2") (pinfunction "P$2_M2") (pintype "bidirectional"))
      (node (ref "E21") (pin "H2") (pinfunction "OUT_H2") (pintype "output"))
      (node (ref "E22") (pin "A1") (pinfunction "IN1_A1") (pintype "input"))
      (node (ref "F26") (pin "T2") (pinfunction "IN1_T2") (pintype "input"))
    )
    (net (code "123") (name "AND_ENABLE") (class "Default")
      (node (ref "E31") (pin "V2") (pinfunction "OUT_V2") (pintype "output"))
      (node (ref "EF34") (pin "AA1") (pinfunction "AA1_AA1") (pintype "input"))
      (node (ref "EF35") (pin "AA1") (pinfunction "AA1_AA1") (pintype "input"))
      (node (ref "EF36") (pin "AA1") (pinfunction "AA1_AA1") (pintype "input"))
      (node (ref "EF37") (pin "AA1") (pinfunction "AA1_AA1") (pintype "input"))
      (node (ref "EF38") (pin "AA1") (pinfunction "AA1_AA1") (pintype "input"))
      (node (ref "EF39") (pin "AA1") (pinfunction "AA1_AA1") (pintype "input"))
    )
    (net (code "124") (name "AND_ENABLE_") (class "Default")
      (node (ref "E31") (pin "R2") (pinfunction "IN1_R2") (pintype "input"))
      (node (ref "E32") (pin "M1") (pinfunction "IN1_M1") (pintype "input"))
      (node (ref "F26") (pin "U1") (pinfunction "OUT_U1") (pintype "output"))
    )
    (net (code "125") (name "ASR_ENABLE") (class "Default")
      (node (ref "D15") (pin "V2") (pinfunction "OUT_V2") (pintype "output"))
      (node (ref "D18") (pin "K2") (pinfunction "IN2_K2") (pintype "input"))
      (node (ref "F33") (pin "R2") (pinfunction "IN4C_R2") (pintype "input"))
    )
    (net (code "126") (name "ASR_L_SET_") (class "Default")
      (node (ref "D18") (pin "M2") (pinfunction "OUT_M2") (pintype "output"))
      (node (ref "F33") (pin "B1") (pinfunction "IN1B_B1") (pintype "input"))
    )
    (net (code "127") (name "AUTO_INDEX_") (class "Default")
      (node (ref "F27") (pin "K2") (pinfunction "IN1_K2") (pintype "input"))
      (node (ref "F27") (pin "S1") (pinfunction "OUT_S1") (pintype "output"))
    )
    (net (code "128") (name "BA") (class "Default")
      (node (ref "D01") (pin "R2") (pinfunction "P$2_R2") (pintype "bidirectional"))
      (node (ref "HJ26") (pin "BP2") (pinfunction "BP2_BP2") (pintype "output"))
    )
    (net (code "129") (name "BA_") (class "Default")
      (node (ref "D01") (pin "P2") (pinfunction "P$2_P2") (pintype "bidirectional"))
      (node (ref "HJ26") (pin "BS1") (pinfunction "BS1_BS1") (pintype "output"))
    )
    (net (code "130") (name "BB") (class "Default")
      (node (ref "D01") (pin "T2") (pinfunction "P$2_T2") (pintype "bidirectional"))
      (node (ref "HJ26") (pin "BU2") (pinfunction "BU2_BU2") (pintype "output"))
    )
    (net (code "131") (name "BB_") (class "Default")
      (node (ref "D01") (pin "S2") (pinfunction "P$2_S2") (pintype "bidirectional"))
      (node (ref "HJ26") (pin "BR1") (pinfunction "BR1_BR1") (pintype "output"))
    )
    (net (code "132") (name "BB_LEFT_SHIFT") (class "Default")
      (node (ref "C16") (pin "D2") (pinfunction "IN1_D2") (pintype "input"))
      (node (ref "C16") (pin "L1") (pinfunction "IN1_L1") (pintype "input"))
      (node (ref "C16") (pin "P2") (pinfunction "IN1_P2") (pintype "input"))
      (node (ref "C17") (pin "D2") (pinfunction "IN1_D2") (pintype "input"))
      (node (ref "C17") (pin "L1") (pinfunction "IN1_L1") (pintype "input"))
      (node (ref "C17") (pin "P2") (pinfunction "IN1_P2") (pintype "input"))
      (node (ref "D12") (pin "V2") (pinfunction "OUT_V2") (pintype "output"))
    )
    (net (code "133") (name "BF0") (class "Default")
      (node (ref "A16") (pin "E2") (pinfunction "IN2_E2") (pintype "input"))
      (node (ref "B18") (pin "P2") (pinfunction "1_P2") (pintype "output"))
    )
    (net (code "134") (name "BF1") (class "Default")
      (node (ref "A16") (pin "M1") (pinfunction "IN2_M1") (pintype "input"))
      (node (ref "B18") (pin "S1") (pinfunction "1_S1") (pintype "output"))
    )
    (net (code "135") (name "BF2") (class "Default")
      (node (ref "A16") (pin "R2") (pinfunction "IN2_R2") (pintype "input"))
      (node (ref "B18") (pin "V2") (pinfunction "1_V2") (pintype "output"))
    )
    (net (code "136") (name "BF_ENABLE") (class "Default")
      (node (ref "A16") (pin "D2") (pinfunction "IN1_D2") (pintype "input"))
      (node (ref "A16") (pin "L1") (pinfunction "IN1_L1") (pintype "input"))
      (node (ref "A16") (pin "P2") (pinfunction "IN1_P2") (pintype "input"))
      (node (ref "B11") (pin "M1") (pinfunction "0_M1") (pintype "output"))
    )
    (net (code "137") (name "BIOP1") (class "Default")
      (node (ref "E09") (pin "N2") (pinfunction "OUT_N2") (pintype "output"))
      (node (ref "J33") (pin "F2") (pinfunction "F2_F2") (pintype "input"))
    )
    (net (code "138") (name "BIOP2") (class "Default")
      (node (ref "E09") (pin "S1") (pinfunction "OUT_S1") (pintype "output"))
      (node (ref "J33") (pin "H2") (pinfunction "H2_H2") (pintype "input"))
    )
    (net (code "139") (name "BIOP4") (class "Default")
      (node (ref "E09") (pin "S2") (pinfunction "OUT_S2") (pintype "output"))
      (node (ref "J33") (pin "F1") (pinfunction "F1_F1") (pintype "input"))
    )
    (net (code "140") (name "BMA00") (class "Default")
      (node (ref "B14") (pin "E1") (pinfunction "OUT_E1") (pintype "output"))
      (node (ref "H01") (pin "K2") (pinfunction "P$2_K2") (pintype "bidirectional"))
    )
    (net (code "141") (name "BMA01") (class "Default")
      (node (ref "B14") (pin "J2") (pinfunction "OUT_J2") (pintype "output"))
      (node (ref "H01") (pin "M2") (pinfunction "P$2_M2") (pintype "bidirectional"))
    )
    (net (code "142") (name "BMA02") (class "Default")
      (node (ref "B14") (pin "L1") (pinfunction "OUT_L1") (pintype "output"))
      (node (ref "H01") (pin "P2") (pinfunction "P$2_P2") (pintype "bidirectional"))
    )
    (net (code "143") (name "BMA03") (class "Default")
      (node (ref "B14") (pin "P2") (pinfunction "OUT_P2") (pintype "output"))
      (node (ref "H01") (pin "S2") (pinfunction "P$2_S2") (pintype "bidirectional"))
    )
    (net (code "144") (name "BMA04") (class "Default")
      (node (ref "B14") (pin "S1") (pinfunction "OUT_S1") (pintype "output"))
      (node (ref "H01") (pin "T2") (pinfunction "P$2_T2") (pintype "bidirectional"))
    )
    (net (code "145") (name "BMA05") (class "Default")
      (node (ref "B14") (pin "V2") (pinfunction "OUT_V2") (pintype "output"))
      (node (ref "H01") (pin "V2") (pinfunction "P$2_V2") (pintype "bidirectional"))
    )
    (net (code "146") (name "BMA06") (class "Default")
      (node (ref "B15") (pin "E1") (pinfunction "OUT_E1") (pintype "output"))
      (node (ref "H02") (pin "D2") (pinfunction "P$2_D2") (pintype "bidirectional"))
    )
    (net (code "147") (name "BMA07") (class "Default")
      (node (ref "B15") (pin "J2") (pinfunction "OUT_J2") (pintype "output"))
      (node (ref "H02") (pin "E2") (pinfunction "P$2_E2") (pintype "bidirectional"))
    )
    (net (code "148") (name "BMA08") (class "Default")
      (node (ref "B15") (pin "L1") (pinfunction "OUT_L1") (pintype "output"))
      (node (ref "H02") (pin "H2") (pinfunction "P$2_H2") (pintype "bidirectional"))
    )
    (net (code "149") (name "BMA09") (class "Default")
      (node (ref "B15") (pin "P2") (pinfunction "OUT_P2") (pintype "output"))
      (node (ref "H02") (pin "K2") (pinfunction "P$2_K2") (pintype "bidirectional"))
    )
    (net (code "150") (name "BMA10") (class "Default")
      (node (ref "B15") (pin "S1") (pinfunction "OUT_S1") (pintype "output"))
      (node (ref "H02") (pin "M2") (pinfunction "P$2_M2") (pintype "bidirectional"))
    )
    (net (code "151") (name "BMA11") (class "Default")
      (node (ref "B15") (pin "V2") (pinfunction "OUT_V2") (pintype "output"))
      (node (ref "H02") (pin "P2") (pinfunction "P$2_P2") (pintype "bidirectional"))
    )
    (net (code "152") (name "BREAK") (class "Default")
      (node (ref "E11") (pin "T2") (pinfunction "IN1_T2") (pintype "input"))
      (node (ref "E23") (pin "V2") (pinfunction "1_V2") (pintype "output"))
      (node (ref "E27") (pin "S2") (pinfunction "IN4D_S2") (pintype "input"))
      (node (ref "E29") (pin "L2") (pinfunction "IN3A_L2") (pintype "input"))
      (node (ref "F28") (pin "L1") (pinfunction "IN2_L1") (pintype "input"))
    )
    (net (code "153") (name "BREAK_") (class "Default")
      (node (ref "D40") (pin "E2") (pinfunction "P$2_E2") (pintype "bidirectional"))
      (node (ref "E23") (pin "V1") (pinfunction "0_V1") (pintype "output"))
      (node (ref "H20") (pin "H2") (pinfunction "IN2_H2") (pintype "input"))
    )
    (net (code "154") (name "BREAK_OK") (class "Default")
      (node (ref "F22") (pin "N1") (pinfunction "OUT_N1") (pintype "output"))
      (node (ref "F22") (pin "P1") (pinfunction "IN1_P1") (pintype "input"))
      (node (ref "F22") (pin "U2") (pinfunction "IN2_U2") (pintype "input"))
      (node (ref "F29") (pin "M1") (pinfunction "IN2_M1") (pintype "input"))
    )
    (net (code "155") (name "BREAK_OK_") (class "Default")
      (node (ref "E33") (pin "C1") (pinfunction "D_C1") (pintype "input"))
      (node (ref "F22") (pin "L1") (pinfunction "IN1_L1") (pintype "input"))
      (node (ref "F23") (pin "N1") (pinfunction "IN2_N1") (pintype "input"))
      (node (ref "F23") (pin "P2") (pinfunction "OUT_P2") (pintype "output"))
    )
    (net (code "156") (name "BRK_RQST") (class "Default")
      (node (ref "E20") (pin "M2") (pinfunction "D_M2") (pintype "input"))
      (node (ref "J15") (pin "S1") (pinfunction "OUT_S1") (pintype "output"))
    )
    (net (code "157") (name "BRK_SYNC") (class "Default")
      (node (ref "E20") (pin "P2") (pinfunction "1_P2") (pintype "output"))
      (node (ref "F23") (pin "L2") (pinfunction "IN2_L2") (pintype "input"))
    )
    (net (code "158") (name "BSTLR") (class "Default")
      (node (ref "C07") (pin "S2") (pinfunction "OUT_S2") (pintype "output"))
      (node (ref "D04") (pin "M2") (pinfunction "P$2_M2") (pintype "bidirectional"))
    )
    (net (code "159") (name "BTP2") (class "Default")
      (node (ref "F08") (pin "K2") (pinfunction "OUT_K2") (pintype "output"))
      (node (ref "H05") (pin "V2") (pinfunction "P$2_V2") (pintype "bidirectional"))
    )
    (net (code "160") (name "BTP3") (class "Default")
      (node (ref "C08") (pin "D2") (pinfunction "OUT_D2") (pintype "output"))
      (node (ref "D04") (pin "E2") (pinfunction "P$2_E2") (pintype "bidirectional"))
    )
    (net (code "161") (name "B_C_") (class "Default")
      (node (ref "C07") (pin "K2") (pinfunction "OUT_K2") (pintype "output"))
      (node (ref "D04") (pin "K2") (pinfunction "P$2_K2") (pintype "bidirectional"))
    )
    (net (code "162") (name "B_DC_INST") (class "Default")
      (node (ref "C08") (pin "S2") (pinfunction "OUT_S2") (pintype "output"))
      (node (ref "D04") (pin "P2") (pinfunction "P$2_P2") (pintype "bidirectional"))
    )
    (net (code "163") (name "B_EAE_ON") (class "Default")
      (node (ref "D12") (pin "J1") (pinfunction "IN2_J1") (pintype "input"))
      (node (ref "D13") (pin "B1") (pinfunction "IN2_B1") (pintype "input"))
      (node (ref "D13") (pin "K1") (pinfunction "OUT_K1") (pintype "output"))
      (node (ref "D17") (pin "C1") (pinfunction "IN3_C1") (pintype "input"))
      (node (ref "D17") (pin "K1") (pinfunction "IN1_K1") (pintype "input"))
      (node (ref "D17") (pin "L2") (pinfunction "IN3_L2") (pintype "input"))
      (node (ref "D18") (pin "A1") (pinfunction "IN1_A1") (pintype "input"))
      (node (ref "D18") (pin "P1") (pinfunction "IN1_P1") (pintype "input"))
      (node (ref "D18") (pin "R2") (pinfunction "IN3_R2") (pintype "input"))
      (node (ref "D20") (pin "E2") (pinfunction "IN2_E2") (pintype "input"))
      (node (ref "D20") (pin "J1") (pinfunction "IN3_J1") (pintype "input"))
      (node (ref "F33") (pin "P2") (pinfunction "IN4B_P2") (pintype "input"))
    )
    (net (code "164") (name "B_EXECUTE") (class "Default")
      (node (ref "D13") (pin "M2") (pinfunction "IN2_M2") (pintype "input"))
      (node (ref "D14") (pin "E2") (pinfunction "IN2_E2") (pintype "input"))
      (node (ref "D21") (pin "H2") (pinfunction "IN4_H2") (pintype "input"))
      (node (ref "E26") (pin "H2") (pinfunction "IN1D_H2") (pintype "input"))
      (node (ref "E27") (pin "B1") (pinfunction "IN1B_B1") (pintype "input"))
      (node (ref "E27") (pin "N1") (pinfunction "IN5B_N1") (pintype "input"))
      (node (ref "E28") (pin "E2") (pinfunction "IN1B_E2") (pintype "input"))
      (node (ref "E29") (pin "D2") (pinfunction "IN1A_D2") (pintype "input"))
      (node (ref "E29") (pin "K2") (pinfunction "IN2B_K2") (pintype "input"))
      (node (ref "E30") (pin "N1") (pinfunction "IN5B_N1") (pintype "input"))
      (node (ref "E30") (pin "R2") (pinfunction "IN4C_R2") (pintype "input"))
      (node (ref "F25") (pin "R2") (pinfunction "IN2_R2") (pintype "input"))
      (node (ref "F26") (pin "P2") (pinfunction "IN2_P2") (pintype "input"))
      (node (ref "F26") (pin "S1") (pinfunction "IN3_S1") (pintype "input"))
      (node (ref "F28") (pin "C1") (pinfunction "IN3_C1") (pintype "input"))
      (node (ref "F28") (pin "F1") (pinfunction "IN2_F1") (pintype "input"))
      (node (ref "F31") (pin "V2") (pinfunction "OUT_V2") (pintype "output"))
    )
    (net (code "165") (name "B_EXT_INST") (class "Default")
      (node (ref "A06") (pin "N1") (pinfunction "OUT_N1") (pintype "output"))
      (node (ref "A20") (pin "K1") (pinfunction "IN1_K1") (pintype "input"))
      (node (ref "A20") (pin "N2") (pinfunction "IN1_N2") (pintype "input"))
      (node (ref "A20") (pin "P1") (pinfunction "IN1_P1") (pintype "input"))
      (node (ref "B04") (pin "C1") (pinfunction "IN3_C1") (pintype "input"))
    )
    (net (code "166") (name "B_FETCH") (class "Default")
      (node (ref "B16") (pin "K2") (pinfunction "IN1_K2") (pintype "input"))
      (node (ref "D10") (pin "N2") (pinfunction "IN4_N2") (pintype "input"))
      (node (ref "D20") (pin "M1") (pinfunction "IN1_M1") (pintype "input"))
      (node (ref "E22") (pin "M1") (pinfunction "IN2_M1") (pintype "input"))
      (node (ref "E25") (pin "K2") (pinfunction "IN2_K2") (pintype "input"))
      (node (ref "E25") (pin "U2") (pinfunction "IN2_U2") (pintype "input"))
      (node (ref "E26") (pin "D1") (pinfunction "IN1D_D1") (pintype "input"))
      (node (ref "E26") (pin "R2") (pinfunction "IN4C_R2") (pintype "input"))
      (node (ref "F09") (pin "A1") (pinfunction "IN1_A1") (pintype "input"))
      (node (ref "F19") (pin "S2") (pinfunction "IN2_S2") (pintype "input"))
      (node (ref "F20") (pin "P1") (pinfunction "IN1_P1") (pintype "input"))
      (node (ref "F21") (pin "J1") (pinfunction "IN2_J1") (pintype "input"))
      (node (ref "F23") (pin "H1") (pinfunction "IN2_H1") (pintype "input"))
      (node (ref "F27") (pin "C1") (pinfunction "IN3_C1") (pintype "input"))
      (node (ref "F27") (pin "J1") (pinfunction "IN3_J1") (pintype "input"))
      (node (ref "F27") (pin "T2") (pinfunction "IN3_T2") (pintype "input"))
      (node (ref "F31") (pin "S1") (pinfunction "OUT_S1") (pintype "output"))
    )
    (net (code "167") (name "B_LEFT_SHIFT") (class "Default")
      (node (ref "C14") (pin "D2") (pinfunction "IN1_D2") (pintype "input"))
      (node (ref "C14") (pin "L1") (pinfunction "IN1_L1") (pintype "input"))
      (node (ref "C14") (pin "P2") (pinfunction "IN1_P2") (pintype "input"))
      (node (ref "C15") (pin "D2") (pinfunction "IN1_D2") (pintype "input"))
      (node (ref "C15") (pin "L1") (pinfunction "IN1_L1") (pintype "input"))
      (node (ref "C15") (pin "P2") (pinfunction "IN1_P2") (pintype "input"))
      (node (ref "D12") (pin "K2") (pinfunction "OUT_K2") (pintype "output"))
    )
    (net (code "168") (name "B_LINE_HOLD_") (class "Default")
      (node (ref "C07") (pin "D2") (pinfunction "OUT_D2") (pintype "output"))
      (node (ref "D04") (pin "D2") (pinfunction "P$2_D2") (pintype "bidirectional"))
    )
    (net (code "169") (name "B_MEM_START") (class "Default")
      (node (ref "F08") (pin "D2") (pinfunction "OUT_D2") (pintype "output"))
      (node (ref "H05") (pin "M2") (pinfunction "P$2_M2") (pintype "bidirectional"))
    )
    (net (code "170") (name "B_MEM_TO_LSR") (class "Default")
      (node (ref "C08") (pin "K2") (pinfunction "OUT_K2") (pintype "output"))
      (node (ref "D04") (pin "H2") (pinfunction "P$2_H2") (pintype "bidirectional"))
    )
    (net (code "171") (name "B_POWER_CLEAR_") (class "Default")
      (node (ref "C12") (pin "S1") (pinfunction "OUT_S1") (pintype "output"))
      (node (ref "D24") (pin "K2") (pinfunction "R_K2") (pintype "input"))
      (node (ref "E18") (pin "K2") (pinfunction "R_K2") (pintype "input"))
      (node (ref "EF10") (pin "AL2") (pinfunction "CL2_AL2") (pintype "input"))
      (node (ref "F20") (pin "R2") (pinfunction "IN2_R2") (pintype "input"))
    )
    (net (code "172") (name "B_R0_") (class "Default")
      (node (ref "D04") (pin "V2") (pinfunction "P$2_V2") (pintype "bidirectional"))
      (node (ref "D05") (pin "D2") (pinfunction "IN_D2") (pintype "input"))
      (node (ref "D05") (pin "E2") (pinfunction "IN2_E2") (pintype "bidirectional"))
      (node (ref "D05") (pin "F2") (pinfunction "IN3_F2") (pintype "input"))
      (node (ref "D05") (pin "H2") (pinfunction "IN4_H2") (pintype "input"))
    )
    (net (code "173") (name "B_SET") (class "Default")
      (node (ref "A19") (pin "E2") (pinfunction "IN2_E2") (pintype "input"))
      (node (ref "A19") (pin "M1") (pinfunction "IN2_M1") (pintype "input"))
      (node (ref "E23") (pin "T2") (pinfunction "D_T2") (pintype "input"))
      (node (ref "F22") (pin "S2") (pinfunction "OUT_S2") (pintype "output"))
    )
    (net (code "174") (name "B_SET_") (class "Default")
      (node (ref "A19") (pin "F2") (pinfunction "OUT_F2") (pintype "output"))
      (node (ref "B11") (pin "J1") (pinfunction "D_J1") (pintype "input"))
      (node (ref "B20") (pin "F2") (pinfunction "IN3_F2") (pintype "input"))
    )
    (net (code "175") (name "C") (class "Default")
      (node (ref "C10") (pin "P2") (pinfunction "IN1_P2") (pintype "input"))
      (node (ref "C11") (pin "E1") (pinfunction "IN1_E1") (pintype "input"))
      (node (ref "D09") (pin "E2") (pinfunction "IN2_E2") (pintype "input"))
      (node (ref "D10") (pin "N1") (pinfunction "IN2_N1") (pintype "input"))
      (node (ref "D10") (pin "S2") (pinfunction "IN2_S2") (pintype "input"))
      (node (ref "D11") (pin "J2") (pinfunction "0_J2") (pintype "output"))
    )
    (net (code "176") (name "CARRY_INSERT_") (class "Default")
      (node (ref "EF39") (pin "BJ1") (pinfunction "BJ1_BJ1") (pintype "input"))
      (node (ref "F32") (pin "C1") (pinfunction "OUT_C1") (pintype "output"))
    )
    (net (code "177") (name "CARRY_OUT0") (class "Default")
      (node (ref "E28") (pin "F2") (pinfunction "IN1C_F2") (pintype "input"))
      (node (ref "F21") (pin "B1") (pinfunction "IN2_B1") (pintype "input"))
      (node (ref "F32") (pin "V2") (pinfunction "OUT_V2") (pintype "output"))
      (node (ref "F33") (pin "U1") (pinfunction "IN1B_U1") (pintype "input"))
    )
    (net (code "178") (name "CARRY_OUT0_") (class "Default")
      (node (ref "EF34") (pin "BK2") (pinfunction "BK2_BK2") (pintype "output"))
      (node (ref "F32") (pin "U2") (pinfunction "IN2_U2") (pintype "input"))
      (node (ref "F33") (pin "U2") (pinfunction "IN2B_U2") (pintype "input"))
    )
    (net (code "179") (name "CARRY_OUT6_") (class "Default")
      (node (ref "EF36") (pin "BJ1") (pinfunction "BJ1_BJ1") (pintype "input"))
      (node (ref "EF37") (pin "BK2") (pinfunction "BK2_BK2") (pintype "output"))
    )
    (net (code "180") (name "CA_INCREMENT") (class "Default")
      (node (ref "E27") (pin "L2") (pinfunction "IN3A_L2") (pintype "input"))
      (node (ref "F25") (pin "F1") (pinfunction "OUT_F1") (pintype "output"))
    )
    (net (code "181") (name "CA_INCREMENT_") (class "Default")
      (node (ref "F25") (pin "D1") (pinfunction "IN1_D1") (pintype "input"))
      (node (ref "J20") (pin "L1") (pinfunction "OUT_L1") (pintype "output"))
    )
    (net (code "182") (name "CINT_") (class "Default")
      (node (ref "A05") (pin "L2") (pinfunction "IN1_L2") (pintype "input"))
      (node (ref "B04") (pin "D1") (pinfunction "OUT_D1") (pintype "output"))
    )
    (net (code "183") (name "CLEAR_DF_") (class "Default")
      (node (ref "B18") (pin "A1") (pinfunction "R_A1") (pintype "input"))
      (node (ref "B21") (pin "S2") (pinfunction "OUT_S2") (pintype "output"))
    )
    (net (code "184") (name "CLEAR_IB_") (class "Default")
      (node (ref "B17") (pin "K2") (pinfunction "R_K2") (pintype "input"))
      (node (ref "B21") (pin "N2") (pinfunction "OUT_N2") (pintype "output"))
    )
    (net (code "185") (name "CLEAR_IFDFBF_") (class "Default")
      (node (ref "B21") (pin "L2") (pinfunction "IN1_L2") (pintype "input"))
      (node (ref "B21") (pin "P1") (pinfunction "IN1_P1") (pintype "input"))
      (node (ref "B21") (pin "P2") (pinfunction "IN1_P2") (pintype "input"))
      (node (ref "E14") (pin "J1") (pinfunction "OUT_J1") (pintype "output"))
    )
    (net (code "186") (name "CLEAR_IF_") (class "Default")
      (node (ref "B05") (pin "A1") (pinfunction "R_A1") (pintype "input"))
      (node (ref "B17") (pin "A1") (pinfunction "R_A1") (pintype "input"))
      (node (ref "B21") (pin "S1") (pinfunction "OUT_S1") (pintype "output"))
    )
    (net (code "187") (name "CLEAR_X_") (class "Default")
      (node (ref "HJ23") (pin "AS2") (pinfunction "AS2_AS2") (pintype "output"))
      (node (ref "HJ24") (pin "AL2") (pinfunction "AL2_AL2") (pintype "bidirectional"))
    )
    (net (code "188") (name "CLEAR_Y_") (class "Default")
      (node (ref "HJ23") (pin "AR2") (pinfunction "AR2_AR2") (pintype "output"))
      (node (ref "HJ25") (pin "AL2") (pinfunction "AL2_AL2") (pintype "bidirectional"))
    )
    (net (code "189") (name "CLOCK") (class "Default")
      (node (ref "H30") (pin "D2") (pinfunction "D2_D2") (pintype "input"))
      (node (ref "HJ31") (pin "BJ2") (pinfunction "BJ2_BJ2") (pintype "input"))
      (node (ref "J30") (pin "D2") (pinfunction "D2_D2") (pintype "output"))
      (node (ref "J30") (pin "F2") (pinfunction "F2_F2") (pintype "bidirectional"))
    )
    (net (code "190") (name "CLOCK1") (class "Default")
      (node (ref "HJ26") (pin "BS2") (pinfunction "BS2_BS2") (pintype "input"))
      (node (ref "HJ27") (pin "AU2") (pinfunction "AU_AU2") (pintype "output"))
    )
    (net (code "191") (name "CLOCK_AC_CLR_") (class "Default")
      (node (ref "HJ31") (pin "BM2") (pinfunction "BM2_BM2") (pintype "open_collector"))
      (node (ref "J15") (pin "K1") (pinfunction "IN4_K1") (pintype "input"))
    )
    (net (code "192") (name "CLOCK_ENABLE_") (class "Default")
      (node (ref "H30") (pin "J2") (pinfunction "J2_J2") (pintype "output"))
      (node (ref "J30") (pin "J2") (pinfunction "J2_J2") (pintype "input"))
    )
    (net (code "193") (name "CLOCK_IOT") (class "Default")
      (node (ref "H30") (pin "S1") (pinfunction "S1_S1") (pintype "output"))
      (node (ref "HJ31") (pin "BL1") (pinfunction "BL1_BL1") (pintype "input"))
    )
    (net (code "194") (name "CLOCK_P4") (class "Default")
      (node (ref "H30") (pin "K2") (pinfunction "K2_K2") (pintype "output"))
      (node (ref "HJ31") (pin "BK1") (pinfunction "BK1_BK1") (pintype "input"))
    )
    (net (code "195") (name "CLOCK_SCALE_2") (class "Default")
      (node (ref "EF01") (pin "BP2") (pinfunction "BP2_BP2") (pintype "input"))
      (node (ref "EF01") (pin "BT2") (pinfunction "BT2_BT2") (pintype "output"))
      (node (ref "EF01") (pin "BU1") (pinfunction "BU1_BU1") (pintype "input"))
    )
    (net (code "196") (name "CLR_PARITY_ERROR_") (class "Default")
      (node (ref "B07") (pin "S2") (pinfunction "OUT_S2") (pintype "output"))
      (node (ref "B11") (pin "N2") (pinfunction "S_N2") (pintype "input"))
    )
    (net (code "197") (name "CR_READ") (class "Default")
      (node (ref "HJ34") (pin "BP2") (pinfunction "P$2_BP2") (pintype "bidirectional"))
      (node (ref "J33") (pin "S2") (pinfunction "S2_S2") (pintype "output"))
    )
    (net (code "198") (name "CR_READY") (class "Default")
      (node (ref "HJ34") (pin "AK2") (pinfunction "P$2_AK2") (pintype "bidirectional"))
      (node (ref "J33") (pin "R2") (pinfunction "R2_R2") (pintype "input"))
    )
    (net (code "199") (name "CSR_ENABLE_") (class "Default")
      (node (ref "C11") (pin "E2") (pinfunction "IN2_E2") (pintype "input"))
      (node (ref "D07") (pin "F1") (pinfunction "OUT_F1") (pintype "output"))
    )
    (net (code "200") (name "CUF") (class "Default")
      (node (ref "B06") (pin "K2") (pinfunction "OUT_K2") (pintype "output"))
      (node (ref "B06") (pin "L1") (pinfunction "IN1_L1") (pintype "input"))
    )
    (net (code "201") (name "CUF_") (class "Default")
      (node (ref "B06") (pin "C1") (pinfunction "OUT_C1") (pintype "output"))
      (node (ref "B06") (pin "D1") (pinfunction "IN1_D1") (pintype "input"))
      (node (ref "B06") (pin "H2") (pinfunction "IN1_H2") (pintype "input"))
      (node (ref "F11") (pin "F2") (pinfunction "IN3_F2") (pintype "input"))
      (node (ref "F11") (pin "H2") (pinfunction "IN4_H2") (pintype "input"))
    )
    (net (code "202") (name "CURRENT_ADDRESS") (class "Default")
      (node (ref "E23") (pin "S1") (pinfunction "1_S1") (pintype "output"))
      (node (ref "E27") (pin "M2") (pinfunction "IN3B_M2") (pintype "input"))
      (node (ref "E29") (pin "L1") (pinfunction "IN4B_L1") (pintype "input"))
    )
    (net (code "203") (name "CURRENT_ADDRESS_") (class "Default")
      (node (ref "D40") (pin "E1") (pinfunction "P$2_E1") (pintype "bidirectional"))
      (node (ref "E23") (pin "U1") (pinfunction "0_U1") (pintype "output"))
      (node (ref "E25") (pin "F1") (pinfunction "IN2_F1") (pintype "input"))
      (node (ref "F22") (pin "R2") (pinfunction "IN2_R2") (pintype "input"))
    )
    (net (code "204") (name "C_") (class "Default")
      (node (ref "C07") (pin "M2") (pinfunction "IN1_M2") (pintype "input"))
      (node (ref "D09") (pin "N2") (pinfunction "IN1_N2") (pintype "input"))
      (node (ref "D11") (pin "H2") (pinfunction "1_H2") (pintype "output"))
    )
    (net (code "205") (name "C_I_R") (class "Default")
      (node (ref "HJ34") (pin "BR2") (pinfunction "P$2_BR2") (pintype "bidirectional"))
      (node (ref "J33") (pin "U2") (pinfunction "U2_U2") (pintype "input"))
    )
    (net (code "206") (name "C_NO_SHIFT_") (class "Default")
      (node (ref "D07") (pin "C1") (pinfunction "OUT_C1") (pintype "output"))
      (node (ref "E31") (pin "R1") (pinfunction "IN4_R1") (pintype "input"))
    )
    (net (code "207") (name "C_SET_") (class "Default")
      (node (ref "C11") (pin "A1") (pinfunction "IN1_A1") (pintype "input"))
      (node (ref "C11") (pin "R2") (pinfunction "IN3_R2") (pintype "input"))
      (node (ref "D10") (pin "J2") (pinfunction "OUT_J2") (pintype "output"))
      (node (ref "D11") (pin "E2") (pinfunction "D_E2") (pintype "input"))
    )
    (net (code "208") (name "DATA00") (class "Default")
      (node (ref "EF34") (pin "BM2") (pinfunction "BM2_BM2") (pintype "input"))
      (node (ref "J18") (pin "E1") (pinfunction "OUT_E1") (pintype "output"))
    )
    (net (code "209") (name "DATA01") (class "Default")
      (node (ref "EF34") (pin "BP2") (pinfunction "BP2_BP2") (pintype "input"))
      (node (ref "J18") (pin "J2") (pinfunction "OUT_J2") (pintype "output"))
    )
    (net (code "210") (name "DATA02") (class "Default")
      (node (ref "EF35") (pin "BM2") (pinfunction "BM2_BM2") (pintype "input"))
      (node (ref "J18") (pin "L1") (pinfunction "OUT_L1") (pintype "output"))
    )
    (net (code "211") (name "DATA03") (class "Default")
      (node (ref "EF35") (pin "BP2") (pinfunction "BP2_BP2") (pintype "input"))
      (node (ref "J18") (pin "P2") (pinfunction "OUT_P2") (pintype "output"))
    )
    (net (code "212") (name "DATA04") (class "Default")
      (node (ref "EF36") (pin "BM2") (pinfunction "BM2_BM2") (pintype "input"))
      (node (ref "J18") (pin "S1") (pinfunction "OUT_S1") (pintype "output"))
    )
    (net (code "213") (name "DATA05") (class "Default")
      (node (ref "EF36") (pin "BP2") (pinfunction "BP2_BP2") (pintype "input"))
      (node (ref "J18") (pin "V2") (pinfunction "OUT_V2") (pintype "output"))
    )
    (net (code "214") (name "DATA06") (class "Default")
      (node (ref "EF37") (pin "BM2") (pinfunction "BM2_BM2") (pintype "input"))
      (node (ref "J19") (pin "E1") (pinfunction "OUT_E1") (pintype "output"))
    )
    (net (code "215") (name "DATA07") (class "Default")
      (node (ref "EF37") (pin "BP2") (pinfunction "BP2_BP2") (pintype "input"))
      (node (ref "J19") (pin "J2") (pinfunction "OUT_J2") (pintype "output"))
    )
    (net (code "216") (name "DATA08") (class "Default")
      (node (ref "EF38") (pin "BM2") (pinfunction "BM2_BM2") (pintype "input"))
      (node (ref "J19") (pin "L1") (pinfunction "OUT_L1") (pintype "output"))
    )
    (net (code "217") (name "DATA09") (class "Default")
      (node (ref "EF38") (pin "BP2") (pinfunction "BP2_BP2") (pintype "input"))
      (node (ref "J19") (pin "P2") (pinfunction "OUT_P2") (pintype "output"))
    )
    (net (code "218") (name "DATA10") (class "Default")
      (node (ref "EF39") (pin "BM2") (pinfunction "BM2_BM2") (pintype "input"))
      (node (ref "J19") (pin "S1") (pinfunction "OUT_S1") (pintype "output"))
    )
    (net (code "219") (name "DATA11") (class "Default")
      (node (ref "EF39") (pin "BP2") (pinfunction "BP2_BP2") (pintype "input"))
      (node (ref "J19") (pin "V2") (pinfunction "OUT_V2") (pintype "output"))
    )
    (net (code "220") (name "DATA_ADD00") (class "Default")
      (node (ref "EF34") (pin "BS1") (pinfunction "BS1_BS1") (pintype "input"))
      (node (ref "J16") (pin "E1") (pinfunction "OUT_E1") (pintype "output"))
    )
    (net (code "221") (name "DATA_ADD01") (class "Default")
      (node (ref "EF34") (pin "BU1") (pinfunction "BU1_BU1") (pintype "input"))
      (node (ref "J16") (pin "J2") (pinfunction "OUT_J2") (pintype "output"))
    )
    (net (code "222") (name "DATA_ADD02") (class "Default")
      (node (ref "EF35") (pin "BS1") (pinfunction "BS1_BS1") (pintype "input"))
      (node (ref "J16") (pin "L1") (pinfunction "OUT_L1") (pintype "output"))
    )
    (net (code "223") (name "DATA_ADD03") (class "Default")
      (node (ref "EF35") (pin "BU1") (pinfunction "BU1_BU1") (pintype "input"))
      (node (ref "J16") (pin "P2") (pinfunction "OUT_P2") (pintype "output"))
    )
    (net (code "224") (name "DATA_ADD04") (class "Default")
      (node (ref "EF36") (pin "BS1") (pinfunction "BS1_BS1") (pintype "input"))
      (node (ref "J16") (pin "S1") (pinfunction "OUT_S1") (pintype "output"))
    )
    (net (code "225") (name "DATA_ADD05") (class "Default")
      (node (ref "EF36") (pin "BU1") (pinfunction "BU1_BU1") (pintype "input"))
      (node (ref "J16") (pin "V2") (pinfunction "OUT_V2") (pintype "output"))
    )
    (net (code "226") (name "DATA_ADD06") (class "Default")
      (node (ref "EF37") (pin "BS1") (pinfunction "BS1_BS1") (pintype "input"))
      (node (ref "J17") (pin "E1") (pinfunction "OUT_E1") (pintype "output"))
    )
    (net (code "227") (name "DATA_ADD07") (class "Default")
      (node (ref "EF37") (pin "BU1") (pinfunction "BU1_BU1") (pintype "input"))
      (node (ref "J17") (pin "J2") (pinfunction "OUT_J2") (pintype "output"))
    )
    (net (code "228") (name "DATA_ADD08") (class "Default")
      (node (ref "EF38") (pin "BS1") (pinfunction "BS1_BS1") (pintype "input"))
      (node (ref "J17") (pin "L1") (pinfunction "OUT_L1") (pintype "output"))
    )
    (net (code "229") (name "DATA_ADD09") (class "Default")
      (node (ref "EF38") (pin "BU1") (pinfunction "BU1_BU1") (pintype "input"))
      (node (ref "J17") (pin "P2") (pinfunction "OUT_P2") (pintype "output"))
    )
    (net (code "230") (name "DATA_ADD10") (class "Default")
      (node (ref "EF39") (pin "BS1") (pinfunction "BS1_BS1") (pintype "input"))
      (node (ref "J17") (pin "S1") (pinfunction "OUT_S1") (pintype "output"))
    )
    (net (code "231") (name "DATA_ADD11") (class "Default")
      (node (ref "EF39") (pin "BU1") (pinfunction "BU1_BU1") (pintype "input"))
      (node (ref "J17") (pin "V2") (pinfunction "OUT_V2") (pintype "output"))
    )
    (net (code "232") (name "DATA_ADD_ENABLE") (class "Default")
      (node (ref "EF34") (pin "BT2") (pinfunction "BT2_BT2") (pintype "input"))
      (node (ref "EF35") (pin "BT2") (pinfunction "BT2_BT2") (pintype "input"))
      (node (ref "EF36") (pin "BT2") (pinfunction "BT2_BT2") (pintype "input"))
      (node (ref "EF37") (pin "BT2") (pinfunction "BT2_BT2") (pintype "input"))
      (node (ref "EF38") (pin "BT2") (pinfunction "BT2_BT2") (pintype "input"))
      (node (ref "EF39") (pin "BT2") (pinfunction "BT2_BT2") (pintype "input"))
      (node (ref "F30") (pin "P2") (pinfunction "OUT_P2") (pintype "output"))
    )
    (net (code "233") (name "DATA_ENABLE") (class "Default")
      (node (ref "EF34") (pin "BL1") (pinfunction "BL1_BL1") (pintype "input"))
      (node (ref "EF35") (pin "BL1") (pinfunction "BL1_BL1") (pintype "input"))
      (node (ref "EF36") (pin "BL1") (pinfunction "BL1_BL1") (pintype "input"))
      (node (ref "EF37") (pin "BL1") (pinfunction "BL1_BL1") (pintype "input"))
      (node (ref "EF38") (pin "BL1") (pinfunction "BL1_BL1") (pintype "input"))
      (node (ref "EF39") (pin "BL1") (pinfunction "BL1_BL1") (pintype "input"))
      (node (ref "F30") (pin "L1") (pinfunction "OUT_L1") (pintype "output"))
    )
    (net (code "234") (name "DATA_IN") (class "Default")
      (node (ref "E29") (pin "M2") (pinfunction "IN3B_M2") (pintype "input"))
      (node (ref "F28") (pin "M1") (pinfunction "IN3_M1") (pintype "input"))
      (node (ref "F29") (pin "F2") (pinfunction "OUT_F2") (pintype "output"))
    )
    (net (code "235") (name "DATA_IN_") (class "Default")
      (node (ref "F29") (pin "D2") (pinfunction "IN1_D2") (pintype "input"))
      (node (ref "J15") (pin "V2") (pinfunction "OUT_V2") (pintype "output"))
    )
    (net (code "236") (name "DCA") (class "Default")
      (node (ref "E22") (pin "K2") (pinfunction "OUT_K2") (pintype "output"))
      (node (ref "E29") (pin "J2") (pinfunction "IN2A_J2") (pintype "input"))
      (node (ref "E30") (pin "S2") (pinfunction "IN4D_S2") (pintype "input"))
    )
    (net (code "237") (name "DCA_") (class "Default")
      (node (ref "D40") (pin "R2") (pinfunction "P$2_R2") (pintype "bidirectional"))
      (node (ref "E21") (pin "M2") (pinfunction "OUT_M2") (pintype "output"))
      (node (ref "E22") (pin "H2") (pinfunction "IN1_H2") (pintype "input"))
      (node (ref "F26") (pin "V2") (pinfunction "IN3_V2") (pintype "input"))
    )
    (net (code "238") (name "DC_INST_") (class "Default")
      (node (ref "C08") (pin "V2") (pinfunction "IN2_V2") (pintype "input"))
      (node (ref "D09") (pin "J1") (pinfunction "OUT_J1") (pintype "output"))
    )
    (net (code "239") (name "DEFER") (class "Default")
      (node (ref "B20") (pin "C1") (pinfunction "IN3_C1") (pintype "input"))
      (node (ref "E23") (pin "H2") (pinfunction "1_H2") (pintype "output"))
      (node (ref "E24") (pin "D1") (pinfunction "IN1_D1") (pintype "input"))
      (node (ref "E26") (pin "N1") (pinfunction "IN5B_N1") (pintype "input"))
      (node (ref "E29") (pin "C1") (pinfunction "IN1C_C1") (pintype "input"))
      (node (ref "E29") (pin "N1") (pinfunction "IN5B_N1") (pintype "input"))
      (node (ref "F25") (pin "M1") (pinfunction "IN2_M1") (pintype "input"))
    )
    (net (code "240") (name "DEFER_") (class "Default")
      (node (ref "D40") (pin "B1") (pinfunction "P$2_B1") (pintype "bidirectional"))
      (node (ref "E23") (pin "J2") (pinfunction "0_J2") (pintype "output"))
    )
    (net (code "241") (name "DF0") (class "Default")
      (node (ref "A11") (pin "E1") (pinfunction "IN2_E1") (pintype "input"))
      (node (ref "A16") (pin "E1") (pinfunction "IN2_E1") (pintype "input"))
      (node (ref "B18") (pin "E1") (pinfunction "1_E1") (pintype "output"))
      (node (ref "B19") (pin "M2") (pinfunction "D_M2") (pintype "input"))
    )
    (net (code "242") (name "DF0_") (class "Default")
      (node (ref "B18") (pin "F1") (pinfunction "0_F1") (pintype "output"))
      (node (ref "C40") (pin "J2") (pinfunction "P$2_J2") (pintype "bidirectional"))
    )
    (net (code "243") (name "DF1") (class "Default")
      (node (ref "A11") (pin "J2") (pinfunction "IN2_J2") (pintype "input"))
      (node (ref "A16") (pin "J2") (pinfunction "IN2_J2") (pintype "input"))
      (node (ref "B18") (pin "H2") (pinfunction "1_H2") (pintype "output"))
      (node (ref "B19") (pin "P1") (pinfunction "D_P1") (pintype "input"))
    )
    (net (code "244") (name "DF1_") (class "Default")
      (node (ref "B18") (pin "J2") (pinfunction "0_J2") (pintype "output"))
      (node (ref "C40") (pin "S1") (pinfunction "P$2_S1") (pintype "bidirectional"))
    )
    (net (code "245") (name "DF2") (class "Default")
      (node (ref "A11") (pin "R1") (pinfunction "IN2_R1") (pintype "input"))
      (node (ref "A16") (pin "R1") (pinfunction "IN2_R1") (pintype "input"))
      (node (ref "B18") (pin "L1") (pinfunction "1_L1") (pintype "output"))
      (node (ref "B19") (pin "T2") (pinfunction "D_T2") (pintype "input"))
    )
    (net (code "246") (name "DF2_") (class "Default")
      (node (ref "B18") (pin "M1") (pinfunction "0_M1") (pintype "output"))
      (node (ref "C40") (pin "P2") (pinfunction "P$2_P2") (pintype "bidirectional"))
    )
    (net (code "247") (name "DFSR0") (class "Default")
      (node (ref "A12") (pin "E1") (pinfunction "IN2_E1") (pintype "input"))
      (node (ref "A40") (pin "D2") (pinfunction "P$2_D2") (pintype "bidirectional"))
    )
    (net (code "248") (name "DFSR1") (class "Default")
      (node (ref "A12") (pin "J2") (pinfunction "IN2_J2") (pintype "input"))
      (node (ref "A40") (pin "E2") (pinfunction "P$2_E2") (pintype "bidirectional"))
    )
    (net (code "249") (name "DFSR2") (class "Default")
      (node (ref "A12") (pin "R1") (pinfunction "IN2_R1") (pintype "input"))
      (node (ref "A40") (pin "F2") (pinfunction "P$2_F2") (pintype "bidirectional"))
    )
    (net (code "250") (name "DF_ENABLE") (class "Default")
      (node (ref "A16") (pin "D1") (pinfunction "IN1_D1") (pintype "input"))
      (node (ref "A16") (pin "H2") (pinfunction "IN1_H2") (pintype "input"))
      (node (ref "A16") (pin "P1") (pinfunction "IN1_P1") (pintype "input"))
      (node (ref "B11") (pin "J2") (pinfunction "0_J2") (pintype "output"))
    )
    (net (code "251") (name "DF_ENABLE_") (class "Default")
      (node (ref "B11") (pin "E2") (pinfunction "D_E2") (pintype "input"))
      (node (ref "B20") (pin "D1") (pinfunction "OUT_D1") (pintype "output"))
      (node (ref "B20") (pin "D2") (pinfunction "IN1_D2") (pintype "input"))
    )
    (net (code "252") (name "DIV_LAST") (class "Default")
      (node (ref "D12") (pin "A1") (pinfunction "IN1_A1") (pintype "input"))
      (node (ref "D13") (pin "E2") (pinfunction "IN2_E2") (pintype "input"))
      (node (ref "D16") (pin "K1") (pinfunction "OUT_K1") (pintype "output"))
      (node (ref "D20") (pin "M2") (pinfunction "IN3_M2") (pintype "input"))
      (node (ref "D23") (pin "E1") (pinfunction "IN2A_E1") (pintype "input"))
    )
    (net (code "253") (name "DIV_LAST_") (class "Default")
      (node (ref "D12") (pin "C1") (pinfunction "OUT_C1") (pintype "output"))
      (node (ref "D12") (pin "D2") (pinfunction "IN1_D2") (pintype "input"))
      (node (ref "D12") (pin "L2") (pinfunction "IN1_L2") (pintype "input"))
      (node (ref "D17") (pin "J2") (pinfunction "IN1_J2") (pintype "input"))
      (node (ref "D20") (pin "H2") (pinfunction "IN4_H2") (pintype "input"))
    )
    (net (code "254") (name "DOUBLE_LEFT_ROTATE") (class "Default")
      (node (ref "E31") (pin "J2") (pinfunction "OUT_J2") (pintype "output"))
      (node (ref "EF34") (pin "AH1") (pinfunction "AH1_AH1") (pintype "input"))
      (node (ref "EF35") (pin "AH1") (pinfunction "AH1_AH1") (pintype "input"))
      (node (ref "EF36") (pin "AH1") (pinfunction "AH1_AH1") (pintype "input"))
      (node (ref "EF37") (pin "AH1") (pinfunction "AH1_AH1") (pintype "input"))
      (node (ref "EF38") (pin "AH1") (pinfunction "AH1_AH1") (pintype "input"))
      (node (ref "EF39") (pin "AH1") (pinfunction "AH1_AH1") (pintype "input"))
      (node (ref "F33") (pin "N1") (pinfunction "IN5B_N1") (pintype "input"))
    )
    (net (code "255") (name "DOUBLE_RIGHT_ROTATE") (class "Default")
      (node (ref "E31") (pin "E1") (pinfunction "OUT_E1") (pintype "output"))
      (node (ref "EF34") (pin "AD1") (pinfunction "AD1_AD1") (pintype "input"))
      (node (ref "EF35") (pin "AD1") (pinfunction "AD1_AD1") (pintype "input"))
      (node (ref "EF36") (pin "AD1") (pinfunction "AD1_AD1") (pintype "input"))
      (node (ref "EF37") (pin "AD1") (pinfunction "AD1_AD1") (pintype "input"))
      (node (ref "EF38") (pin "AD1") (pinfunction "AD1_AD1") (pintype "input"))
      (node (ref "EF39") (pin "AD1") (pinfunction "AD1_AD1") (pintype "input"))
      (node (ref "F33") (pin "F1") (pinfunction "IN2B_F1") (pintype "input"))
    )
    (net (code "256") (name "DRUM_DOWN") (class "Default")
      (node (ref "D02") (pin "T2") (pinfunction "P$2_T2") (pintype "bidirectional"))
      (node (ref "HJ29") (pin "AR2") (pinfunction "AR2_AR2") (pintype "output"))
    )
    (net (code "257") (name "DRUM_UP") (class "Default")
      (node (ref "D02") (pin "S2") (pinfunction "P$2_S2") (pintype "bidirectional"))
      (node (ref "HJ29") (pin "AN2") (pinfunction "AN2_AN2") (pintype "output"))
    )
    (net (code "258") (name "DVI") (class "Default")
      (node (ref "D12") (pin "B1") (pinfunction "IN2_B1") (pintype "input"))
      (node (ref "D16") (pin "M1") (pinfunction "IN2_M1") (pintype "input"))
      (node (ref "D16") (pin "S2") (pinfunction "OUT_S2") (pintype "output"))
      (node (ref "D17") (pin "F1") (pinfunction "IN2_F1") (pintype "input"))
      (node (ref "D17") (pin "M1") (pinfunction "IN3_M1") (pintype "input"))
      (node (ref "D20") (pin "N2") (pinfunction "IN4_N2") (pintype "input"))
      (node (ref "D23") (pin "F1") (pinfunction "IN2B_F1") (pintype "input"))
    )
    (net (code "259") (name "DVI_") (class "Default")
      (node (ref "D16") (pin "P2") (pinfunction "IN1_P2") (pintype "input"))
      (node (ref "D17") (pin "B1") (pinfunction "IN2_B1") (pintype "input"))
      (node (ref "D19") (pin "V1") (pinfunction "OUT_V1") (pintype "output"))
      (node (ref "D23") (pin "S2") (pinfunction "IN4D_S2") (pintype "input"))
    )
    (net (code "260") (name "D_SET") (class "Default")
      (node (ref "E23") (pin "E2") (pinfunction "D_E2") (pintype "input"))
      (node (ref "F22") (pin "K2") (pinfunction "OUT_K2") (pintype "output"))
    )
    (net (code "261") (name "D_SET_") (class "Default")
      (node (ref "E25") (pin "M2") (pinfunction "OUT_M2") (pintype "output"))
      (node (ref "F22") (pin "H2") (pinfunction "IN1_H2") (pintype "input"))
      (node (ref "F23") (pin "N2") (pinfunction "IN4_N2") (pintype "input"))
      (node (ref "F23") (pin "R1") (pinfunction "IN4_R1") (pintype "input"))
      (node (ref "F29") (pin "D1") (pinfunction "IN1_D1") (pintype "input"))
    )
    (net (code "262") (name "E09F1") (class "Default")
      (node (ref "E09") (pin "F1") (pinfunction "OUT_F1") (pintype "output"))
      (node (ref "E17") (pin "H2") (pinfunction "H2_H2") (pintype "input"))
    )
    (net (code "263") (name "E25D1") (class "Default")
      (node (ref "E25") (pin "D1") (pinfunction "OUT_D1") (pintype "output"))
      (node (ref "EF39") (pin "AH2") (pinfunction "AH2_AH2") (pintype "input"))
    )
    (net (code "264") (name "EA0") (class "Default")
      (node (ref "B16") (pin "E1") (pinfunction "OUT_E1") (pintype "output"))
      (node (ref "H01") (pin "D2") (pinfunction "P$2_D2") (pintype "bidirectional"))
    )
    (net (code "265") (name "EA1") (class "Default")
      (node (ref "B16") (pin "J2") (pinfunction "OUT_J2") (pintype "output"))
      (node (ref "H01") (pin "E2") (pinfunction "P$2_E2") (pintype "bidirectional"))
    )
    (net (code "266") (name "EA2") (class "Default")
      (node (ref "B16") (pin "L1") (pinfunction "OUT_L1") (pintype "output"))
      (node (ref "H01") (pin "H2") (pinfunction "P$2_H2") (pintype "bidirectional"))
    )
    (net (code "267") (name "EAE_ACBAR_ENABLE_") (class "Default")
      (node (ref "D13") (pin "A1") (pinfunction "IN1_A1") (pintype "input"))
      (node (ref "D17") (pin "N1") (pinfunction "OUT_N1") (pintype "output"))
      (node (ref "D17") (pin "P1") (pinfunction "IN1_P1") (pintype "input"))
      (node (ref "E32") (pin "U2") (pinfunction "IN4_U2") (pintype "input"))
      (node (ref "F29") (pin "M2") (pinfunction "IN2_M2") (pintype "input"))
    )
    (net (code "268") (name "EAE_AC_ENABLE_") (class "Default")
      (node (ref "D13") (pin "C1") (pinfunction "OUT_C1") (pintype "output"))
      (node (ref "E32") (pin "R1") (pinfunction "IN4_R1") (pintype "input"))
    )
    (net (code "269") (name "EAE_BEGIN") (class "Default")
      (node (ref "D12") (pin "R2") (pinfunction "IN2_R2") (pintype "input"))
      (node (ref "D14") (pin "H1") (pinfunction "IN1_H1") (pintype "input"))
      (node (ref "D14") (pin "K2") (pinfunction "OUT_K2") (pintype "output"))
      (node (ref "D17") (pin "V2") (pinfunction "IN3_V2") (pintype "input"))
    )
    (net (code "270") (name "EAE_COMPLETE_") (class "Default")
      (node (ref "C22") (pin "T2") (pinfunction "D_T2") (pintype "input"))
      (node (ref "D15") (pin "J2") (pinfunction "IN2_J2") (pintype "input"))
      (node (ref "D23") (pin "R1") (pinfunction "OUT_R1") (pintype "output"))
    )
    (net (code "271") (name "EAE_END") (class "Default")
      (node (ref "C22") (pin "V2") (pinfunction "1_V2") (pintype "output"))
      (node (ref "E12") (pin "D2") (pinfunction "IN1_D2") (pintype "input"))
      (node (ref "E14") (pin "P2") (pinfunction "IN2_P2") (pintype "input"))
    )
    (net (code "272") (name "EAE_EXECUTE_") (class "Default")
      (node (ref "D13") (pin "N2") (pinfunction "OUT_N2") (pintype "output"))
      (node (ref "F28") (pin "U2") (pinfunction "IN2_U2") (pintype "input"))
    )
    (net (code "273") (name "EAE_E_SET_") (class "Default")
      (node (ref "D13") (pin "N1") (pinfunction "OUT_N1") (pintype "output"))
      (node (ref "F23") (pin "H2") (pinfunction "IN4_H2") (pintype "input"))
      (node (ref "F28") (pin "K2") (pinfunction "IN2_K2") (pintype "input"))
    )
    (net (code "274") (name "EAE_INST") (class "Default")
      (node (ref "D13") (pin "D1") (pinfunction "IN1_D1") (pintype "input"))
      (node (ref "D13") (pin "K2") (pinfunction "OUT_K2") (pintype "output"))
      (node (ref "D13") (pin "M1") (pinfunction "IN2_M1") (pintype "input"))
      (node (ref "D14") (pin "R2") (pinfunction "IN2_R2") (pintype "input"))
      (node (ref "D18") (pin "L1") (pinfunction "IN2_L1") (pintype "input"))
      (node (ref "D20") (pin "U2") (pinfunction "IN4_U2") (pintype "input"))
    )
    (net (code "275") (name "EAE_IR0") (class "Default")
      (node (ref "D18") (pin "B1") (pinfunction "IN2_B1") (pintype "input"))
      (node (ref "D20") (pin "R2") (pinfunction "IN1_R2") (pintype "input"))
      (node (ref "D24") (pin "E1") (pinfunction "1_E1") (pintype "output"))
    )
    (net (code "276") (name "EAE_IR0_") (class "Default")
      (node (ref "D15") (pin "H1") (pinfunction "IN1_H1") (pintype "input"))
      (node (ref "D19") (pin "N2") (pinfunction "IN1_N2") (pintype "input"))
      (node (ref "D19") (pin "P1") (pinfunction "IN1_P1") (pintype "input"))
      (node (ref "D19") (pin "T2") (pinfunction "IN1_T2") (pintype "input"))
      (node (ref "D20") (pin "F1") (pinfunction "IN1_F1") (pintype "input"))
      (node (ref "D24") (pin "F1") (pinfunction "0_F1") (pintype "output"))
    )
    (net (code "277") (name "EAE_IR1") (class "Default")
      (node (ref "D15") (pin "J1") (pinfunction "IN2_J1") (pintype "input"))
      (node (ref "D17") (pin "A1") (pinfunction "IN1_A1") (pintype "input"))
      (node (ref "D18") (pin "C1") (pinfunction "IN3_C1") (pintype "input"))
      (node (ref "D19") (pin "R1") (pinfunction "IN2_R1") (pintype "input"))
      (node (ref "D19") (pin "U2") (pinfunction "IN2_U2") (pintype "input"))
      (node (ref "D24") (pin "H2") (pinfunction "1_H2") (pintype "output"))
    )
    (net (code "278") (name "EAE_IR1_") (class "Default")
      (node (ref "D19") (pin "P2") (pinfunction "IN2_P2") (pintype "input"))
      (node (ref "D20") (pin "S2") (pinfunction "IN2_S2") (pintype "input"))
      (node (ref "D24") (pin "J2") (pinfunction "0_J2") (pintype "output"))
    )
    (net (code "279") (name "EAE_IR2") (class "Default")
      (node (ref "D19") (pin "R2") (pinfunction "IN3_R2") (pintype "input"))
      (node (ref "D19") (pin "V2") (pinfunction "IN3_V2") (pintype "input"))
      (node (ref "D24") (pin "L1") (pinfunction "1_L1") (pintype "output"))
    )
    (net (code "280") (name "EAE_IR2_") (class "Default")
      (node (ref "D18") (pin "L2") (pinfunction "IN3_L2") (pintype "input"))
      (node (ref "D19") (pin "S1") (pinfunction "IN3_S1") (pintype "input"))
      (node (ref "D20") (pin "T2") (pinfunction "IN3_T2") (pintype "input"))
      (node (ref "D24") (pin "M1") (pinfunction "0_M1") (pintype "output"))
      (node (ref "F33") (pin "S2") (pinfunction "IN4D_S2") (pintype "input"))
    )
    (net (code "281") (name "EAE_IR_CLEAR_") (class "Default")
      (node (ref "D24") (pin "A1") (pinfunction "R_A1") (pintype "input"))
      (node (ref "E22") (pin "N1") (pinfunction "OUT_N1") (pintype "output"))
      (node (ref "E22") (pin "P1") (pinfunction "IN1_P1") (pintype "input"))
    )
    (net (code "282") (name "EAE_LEFT_SHIFT_ENABLE_") (class "Default")
      (node (ref "D20") (pin "J2") (pinfunction "OUT_J2") (pintype "output"))
      (node (ref "E31") (pin "N2") (pinfunction "IN4_N2") (pintype "input"))
    )
    (net (code "283") (name "EAE_L_DISABLE") (class "Default")
      (node (ref "D17") (pin "U1") (pinfunction "OUT_U1") (pintype "output"))
      (node (ref "E28") (pin "L1") (pinfunction "IN4B_L1") (pintype "input"))
    )
    (net (code "284") (name "EAE_MEM_ENABLE_") (class "Default")
      (node (ref "D20") (pin "L1") (pinfunction "OUT_L1") (pintype "output"))
      (node (ref "F11") (pin "L2") (pinfunction "IN2_L2") (pintype "input"))
      (node (ref "F31") (pin "D1") (pinfunction "IN4_D1") (pintype "input"))
      (node (ref "F31") (pin "D2") (pinfunction "IN1_D2") (pintype "input"))
    )
    (net (code "285") (name "EAE_MQ0BAR_ENABLE_") (class "Default")
      (node (ref "D18") (pin "U1") (pinfunction "OUT_U1") (pintype "output"))
      (node (ref "E25") (pin "B1") (pinfunction "IN2_B1") (pintype "input"))
    )
    (net (code "286") (name "EAE_MQ0_ENABLE_") (class "Default")
      (node (ref "D18") (pin "S2") (pinfunction "OUT_S2") (pintype "output"))
      (node (ref "E25") (pin "C1") (pinfunction "IN3_C1") (pintype "input"))
    )
    (net (code "287") (name "EAE_NO_SHIFT_ENABLE") (class "Default")
      (node (ref "D17") (pin "M2") (pinfunction "OUT_M2") (pintype "output"))
      (node (ref "F24") (pin "C1") (pinfunction "IN3_C1") (pintype "input"))
    )
    (net (code "288") (name "EAE_ON") (class "Default")
      (node (ref "C18") (pin "L2") (pinfunction "IN1_L2") (pintype "input"))
      (node (ref "C21") (pin "A1") (pinfunction "IN1_A1") (pintype "input"))
      (node (ref "C21") (pin "D2") (pinfunction "IN1_D2") (pintype "input"))
      (node (ref "C21") (pin "E1") (pinfunction "IN1_E1") (pintype "input"))
      (node (ref "C21") (pin "J2") (pinfunction "IN1_J2") (pintype "input"))
      (node (ref "C21") (pin "K1") (pinfunction "IN1_K1") (pintype "input"))
      (node (ref "C21") (pin "N2") (pinfunction "IN1_N2") (pintype "input"))
      (node (ref "C21") (pin "R1") (pinfunction "IN2_R1") (pintype "input"))
      (node (ref "C21") (pin "T2") (pinfunction "IN1_T2") (pintype "input"))
      (node (ref "D24") (pin "P1") (pinfunction "D_P1") (pintype "input"))
      (node (ref "D24") (pin "P2") (pinfunction "1_P2") (pintype "output"))
    )
    (net (code "289") (name "EAE_ON_") (class "Default")
      (node (ref "D13") (pin "H1") (pinfunction "IN1_H1") (pintype "input"))
      (node (ref "D21") (pin "E2") (pinfunction "IN2_E2") (pintype "input"))
      (node (ref "D24") (pin "R2") (pinfunction "0_R2") (pintype "output"))
      (node (ref "E24") (pin "A1") (pinfunction "IN1_A1") (pintype "input"))
      (node (ref "F28") (pin "R1") (pinfunction "IN2_R1") (pintype "input"))
    )
    (net (code "290") (name "EAE_RIGHT_SHIFT_ENABLE_") (class "Default")
      (node (ref "D12") (pin "H1") (pinfunction "IN1_H1") (pintype "input"))
      (node (ref "D17") (pin "D1") (pinfunction "OUT_D1") (pintype "output"))
      (node (ref "D20") (pin "D2") (pinfunction "IN1_D2") (pintype "input"))
      (node (ref "E31") (pin "K1") (pinfunction "IN4_K1") (pintype "input"))
    )
    (net (code "291") (name "EAE_RUN") (class "Default")
      (node (ref "C22") (pin "U2") (pinfunction "S_U2") (pintype "input"))
      (node (ref "D12") (pin "M2") (pinfunction "IN2_M2") (pintype "input"))
      (node (ref "D14") (pin "A1") (pinfunction "IN1_A1") (pintype "input"))
      (node (ref "D15") (pin "M1") (pinfunction "IN2_M1") (pintype "input"))
      (node (ref "D24") (pin "S1") (pinfunction "1_S1") (pintype "output"))
    )
    (net (code "292") (name "EAE_RUN_") (class "Default")
      (node (ref "D24") (pin "U1") (pinfunction "0_U1") (pintype "output"))
    )
    (net (code "293") (name "EAE_SET_") (class "Default")
      (node (ref "D14") (pin "K1") (pinfunction "OUT_K1") (pintype "output"))
      (node (ref "E14") (pin "L1") (pinfunction "IN2_L1") (pintype "input"))
    )
    (net (code "294") (name "EAE_START_") (class "Default")
      (node (ref "D14") (pin "E1") (pinfunction "IN2_E1") (pintype "input"))
      (node (ref "D17") (pin "V1") (pinfunction "OUT_V1") (pintype "output"))
      (node (ref "D24") (pin "R1") (pinfunction "S_R1") (pintype "input"))
      (node (ref "E12") (pin "E1") (pinfunction "IN2_E1") (pintype "input"))
    )
    (net (code "295") (name "EAE_TG") (class "Default")
      (node (ref "D22") (pin "P1") (pinfunction "IN3_P1") (pintype "input"))
      (node (ref "D22") (pin "R2") (pinfunction "IN1_R2") (pintype "input"))
      (node (ref "D24") (pin "V2") (pinfunction "1_V2") (pintype "output"))
    )
    (net (code "296") (name "EAE_TP") (class "Default")
      (node (ref "C13") (pin "J1") (pinfunction "OUT_J1") (pintype "output"))
      (node (ref "C22") (pin "S2") (pinfunction "C_S2") (pintype "input"))
      (node (ref "D14") (pin "B1") (pinfunction "IN2_B1") (pintype "input"))
    )
    (net (code "297") (name "EAE_TP_") (class "Default")
      (node (ref "D12") (pin "P1") (pinfunction "IN1_P1") (pintype "input"))
      (node (ref "D14") (pin "C1") (pinfunction "OUT_C1") (pintype "output"))
      (node (ref "D14") (pin "D1") (pinfunction "IN1_D1") (pintype "input"))
      (node (ref "D22") (pin "D2") (pinfunction "IN1_D2") (pintype "input"))
      (node (ref "E32") (pin "K2") (pinfunction "IN1_K2") (pintype "input"))
    )
    (net (code "298") (name "ENABLE") (class "Default")
      (node (ref "EF02") (pin "AK1") (pinfunction "AK1_AK1") (pintype "input"))
      (node (ref "EF02") (pin "AK2") (pinfunction "AK2_AK2") (pintype "output"))
    )
    (net (code "299") (name "ENABLE_") (class "Default")
      (node (ref "EF02") (pin "AH1") (pinfunction "AH1_AH1") (pintype "input"))
      (node (ref "EF02") (pin "AL1") (pinfunction "AL1_AL1") (pintype "output"))
    )
    (net (code "300") (name "EXECUTE_") (class "Default")
      (node (ref "D40") (pin "R1") (pinfunction "P$2_R1") (pintype "bidirectional"))
      (node (ref "E23") (pin "M1") (pinfunction "0_M1") (pintype "output"))
      (node (ref "F31") (pin "R2") (pinfunction "IN1_R2") (pintype "input"))
    )
    (net (code "301") (name "EXT_DATA_ADD0") (class "Default")
      (node (ref "B18") (pin "M2") (pinfunction "D_M2") (pintype "input"))
      (node (ref "J20") (pin "P2") (pinfunction "OUT_P2") (pintype "output"))
    )
    (net (code "302") (name "EXT_DATA_ADD1") (class "Default")
      (node (ref "B18") (pin "P1") (pinfunction "D_P1") (pintype "input"))
      (node (ref "J20") (pin "S1") (pinfunction "OUT_S1") (pintype "output"))
    )
    (net (code "303") (name "EXT_DATA_ADD2") (class "Default")
      (node (ref "B18") (pin "T2") (pinfunction "D_T2") (pintype "input"))
      (node (ref "J20") (pin "V2") (pinfunction "OUT_V2") (pintype "output"))
    )
    (net (code "304") (name "EXT_GO") (class "Default")
      (node (ref "A12") (pin "A1") (pinfunction "IN1_A1") (pintype "input"))
      (node (ref "A13") (pin "F1") (pinfunction "OUT_F1") (pintype "output"))
      (node (ref "A15") (pin "H2") (pinfunction "IN1_H2") (pintype "input"))
      (node (ref "A17") (pin "U2") (pinfunction "IN2_U2") (pintype "input"))
      (node (ref "B06") (pin "D2") (pinfunction "IN1_D2") (pintype "input"))
    )
    (net (code "305") (name "EXT_INST") (class "Default")
      (node (ref "A14") (pin "K2") (pinfunction "OUT_K2") (pintype "output"))
      (node (ref "A15") (pin "U2") (pinfunction "IN2_U2") (pintype "input"))
    )
    (net (code "306") (name "E_SET") (class "Default")
      (node (ref "E23") (pin "J1") (pinfunction "D_J1") (pintype "input"))
      (node (ref "F22") (pin "H1") (pinfunction "IN1_H1") (pintype "input"))
      (node (ref "F23") (pin "J2") (pinfunction "OUT_J2") (pintype "output"))
    )
    (net (code "307") (name "E_SET_") (class "Default")
      (node (ref "A16") (pin "U2") (pinfunction "IN2_U2") (pintype "input"))
      (node (ref "F22") (pin "K1") (pinfunction "OUT_K1") (pintype "output"))
      (node (ref "F23") (pin "K2") (pinfunction "IN1_K2") (pintype "input"))
      (node (ref "F23") (pin "P1") (pinfunction "IN3_P1") (pintype "input"))
      (node (ref "F29") (pin "E1") (pinfunction "IN2_E1") (pintype "input"))
    )
    (net (code "308") (name "F15F1") (class "Default")
      (node (ref "F15") (pin "F1") (pinfunction "OUT_F1") (pintype "output"))
      (node (ref "F16") (pin "H2") (pinfunction "H2_H2") (pintype "input"))
    )
    (net (code "309") (name "F17F1") (class "Default")
      (node (ref "F17") (pin "F1") (pinfunction "OUT_F1") (pintype "output"))
      (node (ref "F18") (pin "H2") (pinfunction "H2_H2") (pintype "input"))
    )
    (net (code "310") (name "FEED_HOLE") (class "Default")
      (node (ref "C01") (pin "H2") (pinfunction "P$2_H2") (pintype "bidirectional"))
      (node (ref "C01") (pin "T2") (pinfunction "P$2_T2") (pintype "bidirectional"))
      (node (ref "C04") (pin "S2") (pinfunction "R_S2") (pintype "open_collector"))
    )
    (net (code "311") (name "FETCH_") (class "Default")
      (node (ref "D40") (pin "N1") (pinfunction "P$2_N1") (pintype "bidirectional"))
      (node (ref "E23") (pin "F1") (pinfunction "0_F1") (pintype "output"))
      (node (ref "F28") (pin "T2") (pinfunction "IN1_T2") (pintype "input"))
      (node (ref "F31") (pin "M1") (pinfunction "IN1_M1") (pintype "input"))
    )
    (net (code "312") (name "F_SET") (class "Default")
      (node (ref "E13") (pin "F1") (pinfunction "IN2B_F1") (pintype "input"))
      (node (ref "E23") (pin "C1") (pinfunction "D_C1") (pintype "input"))
      (node (ref "F11") (pin "U2") (pinfunction "IN4_U2") (pintype "input"))
      (node (ref "F22") (pin "F1") (pinfunction "OUT_F1") (pintype "output"))
    )
    (net (code "313") (name "F_SET_") (class "Default")
      (node (ref "A16") (pin "T2") (pinfunction "IN1_T2") (pintype "input"))
      (node (ref "F22") (pin "D1") (pinfunction "IN1_D1") (pintype "input"))
      (node (ref "F23") (pin "S1") (pinfunction "OUT_S1") (pintype "output"))
      (node (ref "F28") (pin "J2") (pinfunction "IN1_J2") (pintype "input"))
    )
    (net (code "314") (name "GND") (class "Default")
      (node (ref "A10") (pin "J1") (pinfunction "8A_J1") (pintype "input"))
      (node (ref "A40") (pin "C2") (pinfunction "P$2_C2") (pintype "bidirectional"))
      (node (ref "B05") (pin "T2") (pinfunction "D_T2") (pintype "input"))
      (node (ref "B11") (pin "P1") (pinfunction "D_P1") (pintype "input"))
      (node (ref "B40") (pin "C2") (pinfunction "P$2_C2") (pintype "bidirectional"))
      (node (ref "C01") (pin "C2") (pinfunction "P$2_C2") (pintype "bidirectional"))
      (node (ref "C01") (pin "E2") (pinfunction "P$2_E2") (pintype "bidirectional"))
      (node (ref "C40") (pin "C2") (pinfunction "P$2_C2") (pintype "bidirectional"))
      (node (ref "D02") (pin "C2") (pinfunction "P$2_C2") (pintype "bidirectional"))
      (node (ref "D03") (pin "C2") (pinfunction "P$2_C2") (pintype "bidirectional"))
      (node (ref "D23") (pin "H1") (pinfunction "IN3A_H1") (pintype "input"))
      (node (ref "D23") (pin "J1") (pinfunction "IN3B_J1") (pintype "input"))
      (node (ref "E18") (pin "D2") (pinfunction "C_D2") (pintype "input"))
      (node (ref "E18") (pin "E2") (pinfunction "D_E2") (pintype "input"))
      (node (ref "E18") (pin "J1") (pinfunction "D_J1") (pintype "input"))
      (node (ref "E19") (pin "C1") (pinfunction "D_C1") (pintype "input"))
      (node (ref "E19") (pin "E2") (pinfunction "D_E2") (pintype "input"))
      (node (ref "E19") (pin "J1") (pinfunction "D_J1") (pintype "input"))
      (node (ref "E19") (pin "M2") (pinfunction "D_M2") (pintype "input"))
      (node (ref "E19") (pin "P1") (pinfunction "D_P1") (pintype "input"))
      (node (ref "E19") (pin "T2") (pinfunction "D_T2") (pintype "input"))
      (node (ref "E20") (pin "P1") (pinfunction "D_P1") (pintype "input"))
      (node (ref "E29") (pin "J1") (pinfunction "IN3B_J1") (pintype "input"))
      (node (ref "E30") (pin "A1") (pinfunction "IN1A_A1") (pintype "input"))
      (node (ref "E40") (pin "C2") (pinfunction "P$2_C2") (pintype "bidirectional"))
      (node (ref "EF01") (pin "BD1") (pinfunction "BD1_BD1") (pintype "input"))
      (node (ref "EF34") (pin "BD1") (pinfunction "BD1_BD1") (pintype "input"))
      (node (ref "EF34") (pin "BE2") (pinfunction "BE2_BE2") (pintype "input"))
      (node (ref "EF34") (pin "BN1") (pinfunction "BN1_BN1") (pintype "input"))
      (node (ref "EF35") (pin "BD1") (pinfunction "BD1_BD1") (pintype "input"))
      (node (ref "EF35") (pin "BE2") (pinfunction "BE2_BE2") (pintype "input"))
      (node (ref "EF35") (pin "BN1") (pinfunction "BN1_BN1") (pintype "input"))
      (node (ref "EF36") (pin "BD1") (pinfunction "BD1_BD1") (pintype "input"))
      (node (ref "EF36") (pin "BE2") (pinfunction "BE2_BE2") (pintype "input"))
      (node (ref "EF36") (pin "BN1") (pinfunction "BN1_BN1") (pintype "input"))
      (node (ref "EF37") (pin "BD1") (pinfunction "BD1_BD1") (pintype "input"))
      (node (ref "EF37") (pin "BE2") (pinfunction "BE2_BE2") (pintype "input"))
      (node (ref "EF38") (pin "BE2") (pinfunction "BE2_BE2") (pintype "input"))
      (node (ref "F40") (pin "C2") (pinfunction "P$2_C2") (pintype "bidirectional"))
      (node (ref "H07") (pin "E2") (pinfunction "SLOW_E2") (pintype "passive"))
      (node (ref "H07") (pin "L2") (pinfunction "SLOW_L2") (pintype "passive"))
      (node (ref "H07") (pin "R2") (pinfunction "SLOW_R2") (pintype "passive"))
      (node (ref "H08") (pin "E2") (pinfunction "SLOW_E2") (pintype "passive"))
      (node (ref "H08") (pin "L2") (pinfunction "SLOW_L2") (pintype "passive"))
      (node (ref "H08") (pin "R2") (pinfunction "SLOW_R2") (pintype "passive"))
      (node (ref "H09") (pin "E2") (pinfunction "SLOW_E2") (pintype "passive"))
      (node (ref "H09") (pin "L2") (pinfunction "SLOW_L2") (pintype "passive"))
      (node (ref "H09") (pin "R2") (pinfunction "SLOW_R2") (pintype "passive"))
      (node (ref "H10") (pin "E2") (pinfunction "SLOW_E2") (pintype "passive"))
      (node (ref "H10") (pin "L2") (pinfunction "SLOW_L2") (pintype "passive"))
      (node (ref "H10") (pin "R2") (pinfunction "SLOW_R2") (pintype "passive"))
      (node (ref "H11") (pin "E2") (pinfunction "SLOW_E2") (pintype "passive"))
      (node (ref "H11") (pin "L2") (pinfunction "SLOW_L2") (pintype "passive"))
      (node (ref "H11") (pin "R2") (pinfunction "SLOW_R2") (pintype "passive"))
      (node (ref "H12") (pin "E2") (pinfunction "SLOW_E2") (pintype "passive"))
      (node (ref "H12") (pin "L2") (pinfunction "SLOW_L2") (pintype "passive"))
      (node (ref "H12") (pin "R2") (pinfunction "SLOW_R2") (pintype "passive"))
      (node (ref "H13") (pin "E2") (pinfunction "SLOW_E2") (pintype "passive"))
      (node (ref "H13") (pin "L2") (pinfunction "SLOW_L2") (pintype "passive"))
      (node (ref "H13") (pin "R2") (pinfunction "SLOW_R2") (pintype "passive"))
      (node (ref "H14") (pin "E2") (pinfunction "SLOW_E2") (pintype "passive"))
      (node (ref "H14") (pin "L2") (pinfunction "SLOW_L2") (pintype "passive"))
      (node (ref "H14") (pin "R2") (pinfunction "SLOW_R2") (pintype "passive"))
      (node (ref "H15") (pin "E2") (pinfunction "SLOW_E2") (pintype "passive"))
      (node (ref "H15") (pin "L2") (pinfunction "SLOW_L2") (pintype "passive"))
      (node (ref "H15") (pin "R2") (pinfunction "SLOW_R2") (pintype "passive"))
      (node (ref "H16") (pin "E2") (pinfunction "SLOW_E2") (pintype "passive"))
      (node (ref "H16") (pin "L2") (pinfunction "SLOW_L2") (pintype "passive"))
      (node (ref "H16") (pin "R2") (pinfunction "SLOW_R2") (pintype "passive"))
      (node (ref "H17") (pin "E2") (pinfunction "SLOW_E2") (pintype "passive"))
      (node (ref "H17") (pin "L2") (pinfunction "SLOW_L2") (pintype "passive"))
      (node (ref "H17") (pin "R2") (pinfunction "SLOW_R2") (pintype "passive"))
      (node (ref "H18") (pin "E2") (pinfunction "SLOW_E2") (pintype "passive"))
      (node (ref "H18") (pin "L2") (pinfunction "SLOW_L2") (pintype "passive"))
      (node (ref "H18") (pin "R2") (pinfunction "SLOW_R2") (pintype "passive"))
      (node (ref "H19") (pin "E2") (pinfunction "SLOW_E2") (pintype "passive"))
      (node (ref "H19") (pin "L2") (pinfunction "SLOW_L2") (pintype "passive"))
      (node (ref "H19") (pin "R2") (pinfunction "SLOW_R2") (pintype "passive"))
      (node (ref "H20") (pin "E2") (pinfunction "SLOW_E2") (pintype "passive"))
      (node (ref "H20") (pin "L2") (pinfunction "SLOW_L2") (pintype "passive"))
      (node (ref "HJ34") (pin "AC2") (pinfunction "P$2_AC2") (pintype "bidirectional"))
      (node (ref "HJ34") (pin "BC2") (pinfunction "P$2_BC2") (pintype "bidirectional"))
    )
    (net (code "315") (name "HOLE1") (class "Default")
      (node (ref "C01") (pin "J2") (pinfunction "P$2_J2") (pintype "bidirectional"))
      (node (ref "C06") (pin "R2") (pinfunction "R_R2") (pintype "open_collector"))
    )
    (net (code "316") (name "HOLE2") (class "Default")
      (node (ref "C01") (pin "S2") (pinfunction "P$2_S2") (pintype "bidirectional"))
      (node (ref "C05") (pin "S2") (pinfunction "R_S2") (pintype "open_collector"))
    )
    (net (code "317") (name "HOLE3") (class "Default")
      (node (ref "C01") (pin "R2") (pinfunction "P$2_R2") (pintype "bidirectional"))
      (node (ref "C05") (pin "R2") (pinfunction "R_R2") (pintype "open_collector"))
    )
    (net (code "318") (name "HOLE4") (class "Default")
      (node (ref "C01") (pin "P2") (pinfunction "P$2_P2") (pintype "bidirectional"))
      (node (ref "C04") (pin "R2") (pinfunction "R_R2") (pintype "open_collector"))
    )
    (net (code "319") (name "HOLE5") (class "Default")
      (node (ref "C01") (pin "N2") (pinfunction "P$2_N2") (pintype "bidirectional"))
      (node (ref "C03") (pin "S2") (pinfunction "R_S2") (pintype "open_collector"))
    )
    (net (code "320") (name "HOLE6") (class "Default")
      (node (ref "C01") (pin "M2") (pinfunction "P$2_M2") (pintype "bidirectional"))
      (node (ref "C03") (pin "R2") (pinfunction "R_R2") (pintype "open_collector"))
    )
    (net (code "321") (name "HOLE7") (class "Default")
      (node (ref "C01") (pin "L2") (pinfunction "P$2_L2") (pintype "bidirectional"))
      (node (ref "C02") (pin "S2") (pinfunction "R_S2") (pintype "open_collector"))
    )
    (net (code "322") (name "HOLE8") (class "Default")
      (node (ref "C01") (pin "K2") (pinfunction "P$2_K2") (pintype "bidirectional"))
      (node (ref "C02") (pin "R2") (pinfunction "R_R2") (pintype "open_collector"))
    )
    (net (code "323") (name "HS") (class "Default")
      (node (ref "D07") (pin "B1") (pinfunction "IN2_B1") (pintype "input"))
      (node (ref "D11") (pin "P2") (pinfunction "1_P2") (pintype "output"))
    )
    (net (code "324") (name "HS_") (class "Default")
      (node (ref "C09") (pin "B1") (pinfunction "IN2_B1") (pintype "input"))
      (node (ref "C11") (pin "F1") (pinfunction "IN2_F1") (pintype "input"))
      (node (ref "D07") (pin "E1") (pinfunction "IN2_E1") (pintype "input"))
      (node (ref "D11") (pin "R2") (pinfunction "0_R2") (pintype "output"))
    )
    (net (code "325") (name "HZ880") (class "Default")
      (node (ref "F03") (pin "J2") (pinfunction "J2_J2") (pintype "output"))
      (node (ref "F03") (pin "P2") (pinfunction "P2_P2") (pintype "input"))
    )
    (net (code "326") (name "IB0") (class "Default")
      (node (ref "A17") (pin "J1") (pinfunction "IN2_J1") (pintype "input"))
      (node (ref "B17") (pin "P2") (pinfunction "1_P2") (pintype "output"))
    )
    (net (code "327") (name "IB1") (class "Default")
      (node (ref "A17") (pin "M1") (pinfunction "IN2_M1") (pintype "input"))
      (node (ref "B17") (pin "S1") (pinfunction "1_S1") (pintype "output"))
    )
    (net (code "328") (name "IB2") (class "Default")
      (node (ref "A17") (pin "R1") (pinfunction "IN2_R1") (pintype "input"))
      (node (ref "B17") (pin "V2") (pinfunction "1_V2") (pintype "output"))
    )
    (net (code "329") (name "IB_TO_IF") (class "Default")
      (node (ref "A15") (pin "A1") (pinfunction "IN1_A1") (pintype "input"))
      (node (ref "A17") (pin "C1") (pinfunction "OUT_C1") (pintype "output"))
      (node (ref "B05") (pin "D2") (pinfunction "C_D2") (pintype "input"))
      (node (ref "B17") (pin "B1") (pinfunction "C_B1") (pintype "input"))
      (node (ref "B17") (pin "D2") (pinfunction "C_D2") (pintype "input"))
      (node (ref "B17") (pin "H1") (pinfunction "C_H1") (pintype "input"))
    )
    (net (code "330") (name "IF0") (class "Default")
      (node (ref "A11") (pin "J1") (pinfunction "IN2_J1") (pintype "input"))
      (node (ref "A16") (pin "B1") (pinfunction "IN2_B1") (pintype "input"))
      (node (ref "B17") (pin "E1") (pinfunction "1_E1") (pintype "output"))
      (node (ref "B19") (pin "C1") (pinfunction "D_C1") (pintype "input"))
    )
    (net (code "331") (name "IF0_") (class "Default")
      (node (ref "B17") (pin "F1") (pinfunction "0_F1") (pintype "output"))
      (node (ref "C40") (pin "N1") (pinfunction "P$2_N1") (pintype "bidirectional"))
    )
    (net (code "332") (name "IF1") (class "Default")
      (node (ref "A11") (pin "M2") (pinfunction "IN2_M2") (pintype "input"))
      (node (ref "A16") (pin "J1") (pinfunction "IN2_J1") (pintype "input"))
      (node (ref "B17") (pin "H2") (pinfunction "1_H2") (pintype "output"))
      (node (ref "B19") (pin "E2") (pinfunction "D_E2") (pintype "input"))
    )
    (net (code "333") (name "IF1_") (class "Default")
      (node (ref "B17") (pin "J2") (pinfunction "0_J2") (pintype "output"))
      (node (ref "C40") (pin "C1") (pinfunction "P$2_C1") (pintype "bidirectional"))
    )
    (net (code "334") (name "IF2") (class "Default")
      (node (ref "A11") (pin "U2") (pinfunction "IN2_U2") (pintype "input"))
      (node (ref "A16") (pin "M2") (pinfunction "IN2_M2") (pintype "input"))
      (node (ref "B17") (pin "L1") (pinfunction "1_L1") (pintype "output"))
      (node (ref "B19") (pin "J1") (pinfunction "D_J1") (pintype "input"))
    )
    (net (code "335") (name "IF2_") (class "Default")
      (node (ref "B17") (pin "M1") (pinfunction "0_M1") (pintype "output"))
      (node (ref "C40") (pin "D1") (pinfunction "P$2_D1") (pintype "bidirectional"))
    )
    (net (code "336") (name "IFSR0") (class "Default")
      (node (ref "A18") (pin "E1") (pinfunction "IN2_E1") (pintype "input"))
      (node (ref "A40") (pin "H2") (pinfunction "P$2_H2") (pintype "bidirectional"))
    )
    (net (code "337") (name "IFSR1") (class "Default")
      (node (ref "A18") (pin "J2") (pinfunction "IN2_J2") (pintype "input"))
      (node (ref "A40") (pin "J2") (pinfunction "P$2_J2") (pintype "bidirectional"))
    )
    (net (code "338") (name "IFSR2") (class "Default")
      (node (ref "A18") (pin "R1") (pinfunction "IN2_R1") (pintype "input"))
      (node (ref "A40") (pin "K2") (pinfunction "P$2_K2") (pintype "bidirectional"))
    )
    (net (code "339") (name "IF_ENABLE") (class "Default")
      (node (ref "A16") (pin "A1") (pinfunction "IN1_A1") (pintype "input"))
      (node (ref "A16") (pin "H1") (pinfunction "IN1_H1") (pintype "input"))
      (node (ref "A16") (pin "L2") (pinfunction "IN1_L2") (pintype "input"))
      (node (ref "B11") (pin "F1") (pinfunction "0_F1") (pintype "output"))
    )
    (net (code "340") (name "IF_ENABLE_") (class "Default")
      (node (ref "B11") (pin "C1") (pinfunction "D_C1") (pintype "input"))
      (node (ref "B20") (pin "H2") (pinfunction "OUT_H2") (pintype "output"))
    )
    (net (code "341") (name "IF_TO_SF") (class "Default")
      (node (ref "A19") (pin "S1") (pinfunction "OUT_S1") (pintype "output"))
      (node (ref "B05") (pin "N1") (pinfunction "C_N1") (pintype "input"))
      (node (ref "B19") (pin "B1") (pinfunction "C_B1") (pintype "input"))
      (node (ref "B19") (pin "D2") (pinfunction "C_D2") (pintype "input"))
      (node (ref "B21") (pin "M2") (pinfunction "IN2_M2") (pintype "input"))
      (node (ref "B21") (pin "R1") (pinfunction "IN2_R1") (pintype "input"))
      (node (ref "B21") (pin "R2") (pinfunction "IN2_R2") (pintype "input"))
    )
    (net (code "342") (name "INDEX_MARKERS") (class "Default")
      (node (ref "HJ32") (pin "AD2") (pinfunction "AD2_AD2") (pintype "input"))
      (node (ref "HJ34") (pin "BH2") (pinfunction "P$2_BH2") (pintype "bidirectional"))
      (node (ref "J33") (pin "J1") (pinfunction "J1_J1") (pintype "input"))
    )
    (net (code "343") (name "INITIALIZE") (class "Default")
      (node (ref "C12") (pin "H1") (pinfunction "IN2_H1") (pintype "input"))
      (node (ref "EF01") (pin "BF2") (pinfunction "BF2_BF2") (pintype "input"))
      (node (ref "EF02") (pin "BE2") (pinfunction "BE2_BE2") (pintype "input"))
      (node (ref "F20") (pin "S2") (pinfunction "OUT_S2") (pintype "output"))
      (node (ref "HJ23") (pin "AH2") (pinfunction "AH2_AH2") (pintype "input"))
      (node (ref "HJ29") (pin "BN2") (pinfunction "BN2_BN2") (pintype "input"))
    )
    (net (code "344") (name "INITIALIZE_") (class "Default")
      (node (ref "A04") (pin "S2") (pinfunction "S2_S2") (pintype "input"))
      (node (ref "B05") (pin "K2") (pinfunction "R_K2") (pintype "input"))
      (node (ref "B07") (pin "L1") (pinfunction "IN2_L1") (pintype "input"))
      (node (ref "C12") (pin "L1") (pinfunction "OUT_L1") (pintype "output"))
      (node (ref "E19") (pin "K2") (pinfunction "R_K2") (pintype "input"))
      (node (ref "H12") (pin "U2") (pinfunction "IN2_U2") (pintype "input"))
      (node (ref "H30") (pin "P1") (pinfunction "P1_P1") (pintype "input"))
      (node (ref "HJ26") (pin "BP1") (pinfunction "BP1_BP1") (pintype "input"))
      (node (ref "HJ28") (pin "AS2") (pinfunction "AS2_AS2") (pintype "input"))
      (node (ref "HJ32") (pin "BS2") (pinfunction "BS2_BS2") (pintype "input"))
      (node (ref "J33") (pin "N1") (pinfunction "N1_N1") (pintype "input"))
    )
    (net (code "345") (name "INPUT_BUS00") (class "Default")
      (node (ref "EF34") (pin "BK1") (pinfunction "BK1_BK1") (pintype "input"))
      (node (ref "J13") (pin "E1") (pinfunction "OUT_E1") (pintype "output"))
    )
    (net (code "346") (name "INPUT_BUS01") (class "Default")
      (node (ref "EF34") (pin "BM1") (pinfunction "BM1_BM1") (pintype "input"))
      (node (ref "J13") (pin "J2") (pinfunction "OUT_J2") (pintype "output"))
    )
    (net (code "347") (name "INPUT_BUS02") (class "Default")
      (node (ref "EF35") (pin "BK1") (pinfunction "BK1_BK1") (pintype "input"))
      (node (ref "J13") (pin "L1") (pinfunction "OUT_L1") (pintype "output"))
    )
    (net (code "348") (name "INPUT_BUS03") (class "Default")
      (node (ref "EF35") (pin "BM1") (pinfunction "BM1_BM1") (pintype "input"))
      (node (ref "J13") (pin "P2") (pinfunction "OUT_P2") (pintype "output"))
    )
    (net (code "349") (name "INPUT_BUS04") (class "Default")
      (node (ref "EF36") (pin "BK1") (pinfunction "BK1_BK1") (pintype "input"))
      (node (ref "J13") (pin "S1") (pinfunction "OUT_S1") (pintype "output"))
    )
    (net (code "350") (name "INPUT_BUS05") (class "Default")
      (node (ref "EF36") (pin "BM1") (pinfunction "BM1_BM1") (pintype "input"))
      (node (ref "J13") (pin "V2") (pinfunction "OUT_V2") (pintype "output"))
    )
    (net (code "351") (name "INPUT_BUS06") (class "Default")
      (node (ref "EF37") (pin "BK1") (pinfunction "BK1_BK1") (pintype "input"))
      (node (ref "J14") (pin "E1") (pinfunction "OUT_E1") (pintype "output"))
    )
    (net (code "352") (name "INPUT_BUS07") (class "Default")
      (node (ref "EF37") (pin "BM1") (pinfunction "BM1_BM1") (pintype "input"))
      (node (ref "J14") (pin "J2") (pinfunction "OUT_J2") (pintype "output"))
    )
    (net (code "353") (name "INPUT_BUS08") (class "Default")
      (node (ref "EF38") (pin "BK1") (pinfunction "BK1_BK1") (pintype "input"))
      (node (ref "J14") (pin "L1") (pinfunction "OUT_L1") (pintype "output"))
    )
    (net (code "354") (name "INPUT_BUS09") (class "Default")
      (node (ref "EF38") (pin "BM1") (pinfunction "BM1_BM1") (pintype "input"))
      (node (ref "J14") (pin "P2") (pinfunction "OUT_P2") (pintype "output"))
    )
    (net (code "355") (name "INPUT_BUS10") (class "Default")
      (node (ref "EF39") (pin "BK1") (pinfunction "BK1_BK1") (pintype "input"))
      (node (ref "J14") (pin "S1") (pinfunction "OUT_S1") (pintype "output"))
    )
    (net (code "356") (name "INPUT_BUS11") (class "Default")
      (node (ref "EF39") (pin "BM1") (pinfunction "BM1_BM1") (pintype "input"))
      (node (ref "J14") (pin "V2") (pinfunction "OUT_V2") (pintype "output"))
    )
    (net (code "357") (name "INT_DELAY") (class "Default")
      (node (ref "E25") (pin "F2") (pinfunction "IN3_F2") (pintype "input"))
      (node (ref "E33") (pin "R2") (pinfunction "0_R2") (pintype "output"))
    )
    (net (code "358") (name "INT_ENABLE") (class "Default")
      (node (ref "E33") (pin "N2") (pinfunction "S_N2") (pintype "input"))
      (node (ref "E33") (pin "U1") (pinfunction "0_U1") (pintype "output"))
    )
    (net (code "359") (name "INT_ENABLE_") (class "Default")
      (node (ref "D40") (pin "D1") (pinfunction "P$2_D1") (pintype "bidirectional"))
      (node (ref "E33") (pin "M2") (pinfunction "D_M2") (pintype "input"))
      (node (ref "E33") (pin "S1") (pinfunction "1_S1") (pintype "output"))
    )
    (net (code "360") (name "INT_INHIBIT_") (class "Default")
      (node (ref "B11") (pin "S1") (pinfunction "1_S1") (pintype "output"))
      (node (ref "E25") (pin "E2") (pinfunction "IN2_E2") (pintype "input"))
    )
    (net (code "361") (name "INT_OK") (class "Default")
      (node (ref "C12") (pin "K2") (pinfunction "IN1_K2") (pintype "input"))
      (node (ref "E24") (pin "J2") (pinfunction "IN2_J2") (pintype "input"))
      (node (ref "E26") (pin "U1") (pinfunction "IN1B_U1") (pintype "input"))
      (node (ref "F21") (pin "N1") (pinfunction "OUT_N1") (pintype "output"))
    )
    (net (code "362") (name "INT_OK_") (class "Default")
      (node (ref "E25") (pin "H2") (pinfunction "OUT_H2") (pintype "output"))
      (node (ref "F21") (pin "M1") (pinfunction "IN2_M1") (pintype "input"))
      (node (ref "F23") (pin "D2") (pinfunction "IN1_D2") (pintype "input"))
      (node (ref "F27") (pin "F2") (pinfunction "IN3_F2") (pintype "input"))
    )
    (net (code "363") (name "INT_RQST") (class "Default")
      (node (ref "F11") (pin "R2") (pinfunction "IN1_R2") (pintype "input"))
      (node (ref "J15") (pin "J2") (pinfunction "OUT_J2") (pintype "output"))
    )
    (net (code "364") (name "INT_SKIP_ENABLE_") (class "Default")
      (node (ref "F09") (pin "L2") (pinfunction "IN6_L2") (pintype "input"))
      (node (ref "F11") (pin "M1") (pinfunction "IN1_M1") (pintype "input"))
      (node (ref "F28") (pin "J1") (pinfunction "OUT_J1") (pintype "output"))
    )
    (net (code "365") (name "INT_STROBE") (class "Default")
      (node (ref "E14") (pin "S2") (pinfunction "OUT_S2") (pintype "output"))
      (node (ref "E15") (pin "L2") (pinfunction "IN1_L2") (pintype "input"))
      (node (ref "E33") (pin "H1") (pinfunction "C_H1") (pintype "input"))
      (node (ref "F19") (pin "F1") (pinfunction "IN1_F1") (pintype "input"))
      (node (ref "F21") (pin "H1") (pinfunction "IN1_H1") (pintype "input"))
    )
    (net (code "366") (name "INT_STROBE_") (class "Default")
      (node (ref "C12") (pin "M2") (pinfunction "IN3_M2") (pintype "input"))
      (node (ref "E15") (pin "N2") (pinfunction "OUT_N2") (pintype "output"))
      (node (ref "E19") (pin "K1") (pinfunction "S_K1") (pintype "input"))
    )
    (net (code "367") (name "INT_SYNC") (class "Default")
      (node (ref "E25") (pin "D2") (pinfunction "IN1_D2") (pintype "input"))
      (node (ref "E33") (pin "M1") (pinfunction "0_M1") (pintype "output"))
    )
    (net (code "368") (name "IN_STOP_2_") (class "Default")
      (node (ref "EF01") (pin "BR2") (pinfunction "BR2_BR2") (pintype "input"))
      (node (ref "EF01") (pin "BV2") (pinfunction "BV2_BV2") (pintype "output"))
    )
    (net (code "369") (name "IOP1") (class "Default")
      (node (ref "B07") (pin "K2") (pinfunction "IN2_K2") (pintype "input"))
      (node (ref "E19") (pin "P2") (pinfunction "1_P2") (pintype "output"))
      (node (ref "EF01") (pin "BD2") (pinfunction "BD2_BD2") (pintype "input"))
      (node (ref "EF02") (pin "BH2") (pinfunction "BH2_BH2") (pintype "input"))
      (node (ref "HJ23") (pin "AR1") (pinfunction "AR1_AR1") (pintype "input"))
      (node (ref "HJ26") (pin "AU2") (pinfunction "AU2_AU2") (pintype "input"))
      (node (ref "HJ28") (pin "AR2") (pinfunction "AR2_AR2") (pintype "input"))
      (node (ref "HJ29") (pin "BH2") (pinfunction "BH2_BH2") (pintype "input"))
    )
    (net (code "370") (name "IOP1_") (class "Default")
      (node (ref "E09") (pin "M2") (pinfunction "IN2_M2") (pintype "input"))
      (node (ref "E19") (pin "R2") (pinfunction "0_R2") (pintype "output"))
      (node (ref "F11") (pin "H1") (pinfunction "IN2_H1") (pintype "input"))
      (node (ref "H11") (pin "H2") (pinfunction "IN2_H2") (pintype "input"))
      (node (ref "H30") (pin "L2") (pinfunction "L2_L2") (pintype "input"))
      (node (ref "HJ29") (pin "BL2") (pinfunction "BL2_BL2") (pintype "input"))
    )
    (net (code "371") (name "IOP1_CLR") (class "Default")
      (node (ref "E19") (pin "L2") (pinfunction "C_L2") (pintype "input"))
      (node (ref "F14") (pin "J1") (pinfunction "OUT_J1") (pintype "output"))
    )
    (net (code "372") (name "IOP1_SET_") (class "Default")
      (node (ref "E14") (pin "S1") (pinfunction "IN3_S1") (pintype "input"))
      (node (ref "E19") (pin "N2") (pinfunction "S_N2") (pintype "input"))
      (node (ref "F20") (pin "F2") (pinfunction "OUT_F2") (pintype "output"))
    )
    (net (code "373") (name "IOP2") (class "Default")
      (node (ref "A04") (pin "M2") (pinfunction "M2_M2") (pintype "input"))
      (node (ref "E19") (pin "S1") (pinfunction "1_S1") (pintype "output"))
      (node (ref "EF01") (pin "BJ2") (pinfunction "BJ2_BJ2") (pintype "input"))
      (node (ref "EF02") (pin "BD2") (pinfunction "BD2_BD2") (pintype "input"))
      (node (ref "HJ23") (pin "AJ2") (pinfunction "AJ2_AJ2") (pintype "input"))
      (node (ref "HJ26") (pin "AV2") (pinfunction "AV2_AV2") (pintype "input"))
      (node (ref "HJ28") (pin "AR1") (pinfunction "AR1_AR1") (pintype "input"))
      (node (ref "HJ29") (pin "BP2") (pinfunction "BP2_BP2") (pintype "input"))
    )
    (net (code "374") (name "IOP2_") (class "Default")
      (node (ref "E09") (pin "R1") (pinfunction "IN2_R1") (pintype "input"))
      (node (ref "E19") (pin "U1") (pinfunction "0_U1") (pintype "output"))
      (node (ref "F11") (pin "J1") (pinfunction "IN3_J1") (pintype "input"))
      (node (ref "H11") (pin "N2") (pinfunction "IN2_N2") (pintype "input"))
      (node (ref "H30") (pin "R1") (pinfunction "R1_R1") (pintype "input"))
      (node (ref "HJ29") (pin "BM2") (pinfunction "BM2_BM2") (pintype "input"))
    )
    (net (code "375") (name "IOP2_CLR") (class "Default")
      (node (ref "E19") (pin "N1") (pinfunction "C_N1") (pintype "input"))
      (node (ref "F16") (pin "J1") (pinfunction "OUT_J1") (pintype "output"))
    )
    (net (code "376") (name "IOP2_SET_") (class "Default")
      (node (ref "E14") (pin "R1") (pinfunction "IN2_R1") (pintype "input"))
      (node (ref "E19") (pin "R1") (pinfunction "S_R1") (pintype "input"))
      (node (ref "F20") (pin "K1") (pinfunction "OUT_K1") (pintype "output"))
    )
    (net (code "377") (name "IOP4") (class "Default")
      (node (ref "B07") (pin "E1") (pinfunction "IN1_E1") (pintype "input"))
      (node (ref "E19") (pin "V2") (pinfunction "1_V2") (pintype "output"))
      (node (ref "EF01") (pin "AL2") (pinfunction "AL2_AL2") (pintype "input"))
      (node (ref "EF02") (pin "AS1") (pinfunction "AS1_AS1") (pintype "input"))
      (node (ref "HJ23") (pin "BD2") (pinfunction "BD2_BD2") (pintype "input"))
      (node (ref "HJ26") (pin "BK1") (pinfunction "BK1_BK1") (pintype "input"))
      (node (ref "HJ28") (pin "AP2") (pinfunction "AP2_AP2") (pintype "input"))
      (node (ref "HJ29") (pin "BT2") (pinfunction "BT2_BT2") (pintype "input"))
    )
    (net (code "378") (name "IOP4_") (class "Default")
      (node (ref "E09") (pin "R2") (pinfunction "IN2_R2") (pintype "input"))
      (node (ref "E19") (pin "V1") (pinfunction "0_V1") (pintype "output"))
      (node (ref "F11") (pin "K1") (pinfunction "IN4_K1") (pintype "input"))
      (node (ref "H11") (pin "U2") (pinfunction "IN2_U2") (pintype "input"))
      (node (ref "H30") (pin "F2") (pinfunction "F2_F2") (pintype "input"))
    )
    (net (code "379") (name "IOP4_CLR") (class "Default")
      (node (ref "E19") (pin "S2") (pinfunction "C_S2") (pintype "input"))
      (node (ref "F18") (pin "J1") (pinfunction "OUT_J1") (pintype "output"))
    )
    (net (code "380") (name "IOP4_SET_") (class "Default")
      (node (ref "E14") (pin "P1") (pinfunction "IN1_P1") (pintype "input"))
      (node (ref "E19") (pin "U2") (pinfunction "S_U2") (pintype "input"))
      (node (ref "F20") (pin "K2") (pinfunction "OUT_K2") (pintype "output"))
    )
    (net (code "381") (name "IOP124_") (class "Default")
      (node (ref "E09") (pin "T2") (pinfunction "IN1_T2") (pintype "input"))
      (node (ref "E11") (pin "S1") (pinfunction "OUT_S1") (pintype "output"))
      (node (ref "F30") (pin "D2") (pinfunction "IN1_D2") (pintype "input"))
    )
    (net (code "382") (name "IOT") (class "Default")
      (node (ref "A06") (pin "F1") (pinfunction "OUT_F1") (pintype "output"))
      (node (ref "A14") (pin "E1") (pinfunction "IN2_E1") (pintype "input"))
      (node (ref "C12") (pin "F2") (pinfunction "IN3_F2") (pintype "input"))
      (node (ref "C12") (pin "H2") (pinfunction "IN4_H2") (pintype "input"))
      (node (ref "D09") (pin "F1") (pinfunction "IN2_F1") (pintype "input"))
      (node (ref "D10") (pin "K2") (pinfunction "IN1_K2") (pintype "input"))
      (node (ref "E26") (pin "M2") (pinfunction "IN3B_M2") (pintype "input"))
      (node (ref "F09") (pin "F2") (pinfunction "IN7_F2") (pintype "input"))
      (node (ref "F19") (pin "R2") (pinfunction "IN1_R2") (pintype "input"))
      (node (ref "F20") (pin "R1") (pinfunction "IN2_R1") (pintype "input"))
    )
    (net (code "383") (name "IOT632") (class "Default")
      (node (ref "HJ32") (pin "BM2") (pinfunction "BM2_BM2") (pintype "input"))
      (node (ref "J33") (pin "P1") (pinfunction "P1_P1") (pintype "output"))
    )
    (net (code "384") (name "IOT634") (class "Default")
      (node (ref "HJ32") (pin "AH1") (pinfunction "AH1_AH1") (pintype "input"))
      (node (ref "J33") (pin "R1") (pinfunction "R1_R1") (pintype "output"))
    )
    (net (code "385") (name "IOT_") (class "Default")
      (node (ref "A06") (pin "D1") (pinfunction "IN1_D1") (pintype "input"))
      (node (ref "D40") (pin "H2") (pinfunction "P$2_H2") (pintype "bidirectional"))
      (node (ref "F11") (pin "E1") (pinfunction "OUT_E1") (pintype "output"))
    )
    (net (code "386") (name "IOT_OPR_") (class "Default")
      (node (ref "E24") (pin "F2") (pinfunction "OUT_F2") (pintype "output"))
      (node (ref "E25") (pin "J2") (pinfunction "IN1_J2") (pintype "input"))
      (node (ref "F23") (pin "F1") (pinfunction "IN1_F1") (pintype "input"))
    )
    (net (code "387") (name "IO_BUS_IN00_") (class "Default")
      (node (ref "HJ31") (pin "AF2") (pinfunction "AF2_AF2") (pintype "open_collector"))
      (node (ref "HJ32") (pin "AF1") (pinfunction "AF1_AF1") (pintype "open_collector"))
      (node (ref "J13") (pin "B1") (pinfunction "IN2_B1") (pintype "passive"))
    )
    (net (code "388") (name "IO_BUS_IN01_") (class "Default")
      (node (ref "HJ31") (pin "BD1") (pinfunction "BD1_BD1") (pintype "open_collector"))
      (node (ref "HJ32") (pin "AF2") (pinfunction "AF2_AF2") (pintype "open_collector"))
      (node (ref "J13") (pin "E2") (pinfunction "IN2_E2") (pintype "passive"))
    )
    (net (code "389") (name "IO_BUS_IN02_") (class "Default")
      (node (ref "HJ31") (pin "AF1") (pinfunction "AF1_AF1") (pintype "open_collector"))
      (node (ref "HJ32") (pin "AH2") (pinfunction "AH2_AH2") (pintype "open_collector"))
      (node (ref "J13") (pin "H1") (pinfunction "IN2_H1") (pintype "passive"))
    )
    (net (code "390") (name "IO_BUS_IN03_") (class "Default")
      (node (ref "HJ31") (pin "BB1") (pinfunction "BB1_BB1") (pintype "open_collector"))
      (node (ref "HJ32") (pin "AJ2") (pinfunction "AJ2_AJ2") (pintype "open_collector"))
      (node (ref "J13") (pin "L2") (pinfunction "IN2_L2") (pintype "passive"))
    )
    (net (code "391") (name "IO_BUS_IN04_") (class "Default")
      (node (ref "HJ26") (pin "AP2") (pinfunction "AP2_AP2") (pintype "open_collector"))
      (node (ref "HJ31") (pin "AJ2") (pinfunction "AJ2_AJ2") (pintype "open_collector"))
      (node (ref "HJ32") (pin "AN2") (pinfunction "AN2_AN2") (pintype "open_collector"))
      (node (ref "J13") (pin "N1") (pinfunction "IN2_N1") (pintype "passive"))
    )
    (net (code "392") (name "IO_BUS_IN05_") (class "Default")
      (node (ref "HJ26") (pin "AS2") (pinfunction "AS2_AS2") (pintype "open_collector"))
      (node (ref "HJ31") (pin "AU1") (pinfunction "AU1_AU1") (pintype "open_collector"))
      (node (ref "HJ32") (pin "AM2") (pinfunction "AM2_AM2") (pintype "open_collector"))
      (node (ref "J13") (pin "S2") (pinfunction "IN2_S2") (pintype "passive"))
    )
    (net (code "393") (name "IO_BUS_IN06_") (class "Default")
      (node (ref "HJ26") (pin "AR1") (pinfunction "AR1_AR1") (pintype "open_collector"))
      (node (ref "HJ31") (pin "AJ1") (pinfunction "AJ1_AJ1") (pintype "open_collector"))
      (node (ref "HJ32") (pin "AU2") (pinfunction "AU2_AU2") (pintype "open_collector"))
      (node (ref "J14") (pin "B1") (pinfunction "IN2_B1") (pintype "passive"))
    )
    (net (code "394") (name "IO_BUS_IN07_") (class "Default")
      (node (ref "HJ26") (pin "AN2") (pinfunction "AN2_AN2") (pintype "open_collector"))
      (node (ref "HJ31") (pin "AV2") (pinfunction "AV2_AV2") (pintype "open_collector"))
      (node (ref "HJ32") (pin "AV2") (pinfunction "AV2_AV2") (pintype "open_collector"))
      (node (ref "J14") (pin "E2") (pinfunction "IN2_E2") (pintype "passive"))
    )
    (net (code "395") (name "IO_BUS_IN08_") (class "Default")
      (node (ref "HJ26") (pin "AS1") (pinfunction "AS1_AS1") (pintype "open_collector"))
      (node (ref "HJ31") (pin "AM1") (pinfunction "AM1_AM1") (pintype "open_collector"))
      (node (ref "HJ32") (pin "BP2") (pinfunction "BP2_BP2") (pintype "open_collector"))
      (node (ref "J14") (pin "H1") (pinfunction "IN2_H1") (pintype "passive"))
    )
    (net (code "396") (name "IO_BUS_IN09_") (class "Default")
      (node (ref "HJ26") (pin "AP1") (pinfunction "AP1_AP1") (pintype "open_collector"))
      (node (ref "HJ31") (pin "AP2") (pinfunction "AP2_AP2") (pintype "open_collector"))
      (node (ref "HJ32") (pin "BN2") (pinfunction "BN2_BN2") (pintype "open_collector"))
      (node (ref "J14") (pin "L2") (pinfunction "IN2_L2") (pintype "passive"))
    )
    (net (code "397") (name "IO_BUS_IN10_") (class "Default")
      (node (ref "HJ26") (pin "AR2") (pinfunction "AR2_AR2") (pintype "open_collector"))
      (node (ref "HJ31") (pin "AM2") (pinfunction "AM2_AM2") (pintype "open_collector"))
      (node (ref "HJ32") (pin "BJ2") (pinfunction "BJ2_BJ2") (pintype "open_collector"))
      (node (ref "J14") (pin "N1") (pinfunction "IN2_N1") (pintype "passive"))
    )
    (net (code "398") (name "IO_BUS_IN11_") (class "Default")
      (node (ref "HJ26") (pin "AN1") (pinfunction "AN1_AN1") (pintype "open_collector"))
      (node (ref "HJ31") (pin "AS1") (pinfunction "AS1_AS1") (pintype "open_collector"))
      (node (ref "HJ32") (pin "BH2") (pinfunction "BH2_BH2") (pintype "open_collector"))
      (node (ref "J14") (pin "S2") (pinfunction "IN2_S2") (pintype "passive"))
    )
    (net (code "399") (name "IO_BUS_IN_AC_CLR_") (class "Default")
      (node (ref "J15") (pin "H1") (pinfunction "IN2_H1") (pintype "passive"))
    )
    (net (code "400") (name "IO_BUS_IN_INT_") (class "Default")
      (node (ref "H30") (pin "C1") (pinfunction "C1_C1") (pintype "open_collector"))
      (node (ref "HJ23") (pin "BP2") (pinfunction "BP2_BP2") (pintype "open_collector"))
      (node (ref "HJ26") (pin "AL2") (pinfunction "AL2_AL2") (pintype "open_collector"))
      (node (ref "HJ28") (pin "BS2") (pinfunction "BS2_BS2") (pintype "open_collector"))
      (node (ref "HJ29") (pin "BF2") (pinfunction "BF2_BF2") (pintype "open_collector"))
      (node (ref "J15") (pin "E2") (pinfunction "IN2_E2") (pintype "passive"))
      (node (ref "J33") (pin "N2") (pinfunction "N2_N2") (pintype "open_collector"))
    )
    (net (code "401") (name "IO_BUS_IN_SKIP_") (class "Default")
      (node (ref "H30") (pin "H1") (pinfunction "H1_H1") (pintype "open_collector"))
      (node (ref "HJ23") (pin "BR2") (pinfunction "BR2_BR2") (pintype "open_collector"))
      (node (ref "HJ26") (pin "AK2") (pinfunction "AK2_AK2") (pintype "open_collector"))
      (node (ref "HJ28") (pin "BN2") (pinfunction "BN2_BN2") (pintype "open_collector"))
      (node (ref "HJ29") (pin "BE2") (pinfunction "BE2_BE2") (pintype "open_collector"))
      (node (ref "J15") (pin "B1") (pinfunction "IN2_B1") (pintype "passive"))
      (node (ref "J33") (pin "P2") (pinfunction "P2_P2") (pintype "open_collector"))
    )
    (net (code "402") (name "IO_ENABLE") (class "Default")
      (node (ref "E28") (pin "J2") (pinfunction "IN2A_J2") (pintype "input"))
      (node (ref "E30") (pin "J2") (pinfunction "IN2A_J2") (pintype "input"))
      (node (ref "EF34") (pin "BL2") (pinfunction "BL2_BL2") (pintype "input"))
      (node (ref "EF35") (pin "BL2") (pinfunction "BL2_BL2") (pintype "input"))
      (node (ref "EF36") (pin "BL2") (pinfunction "BL2_BL2") (pintype "input"))
      (node (ref "EF37") (pin "BL2") (pinfunction "BL2_BL2") (pintype "input"))
      (node (ref "EF38") (pin "BL2") (pinfunction "BL2_BL2") (pintype "input"))
      (node (ref "EF39") (pin "BL2") (pinfunction "BL2_BL2") (pintype "input"))
      (node (ref "F30") (pin "J2") (pinfunction "OUT_J2") (pintype "output"))
    )
    (net (code "403") (name "IO_END") (class "Default")
      (node (ref "E12") (pin "H1") (pinfunction "IN1_H1") (pintype "input"))
      (node (ref "E20") (pin "N1") (pinfunction "C_N1") (pintype "input"))
      (node (ref "F18") (pin "F1") (pinfunction "OUT_F1") (pintype "output"))
    )
    (net (code "404") (name "IO_END_") (class "Default")
      (node (ref "E12") (pin "E2") (pinfunction "IN2_E2") (pintype "input"))
      (node (ref "E12") (pin "K1") (pinfunction "OUT_K1") (pintype "output"))
      (node (ref "E14") (pin "R2") (pinfunction "IN3_R2") (pintype "input"))
    )
    (net (code "405") (name "IO_ON") (class "Default")
      (node (ref "E09") (pin "U2") (pinfunction "IN2_U2") (pintype "input"))
      (node (ref "E20") (pin "S1") (pinfunction "1_S1") (pintype "output"))
    )
    (net (code "406") (name "IO_PC_ENABLE_") (class "Default")
      (node (ref "E09") (pin "V2") (pinfunction "OUT_V2") (pintype "output"))
      (node (ref "F09") (pin "K1") (pinfunction "IN4_K1") (pintype "input"))
      (node (ref "F11") (pin "N1") (pinfunction "IN2_N1") (pintype "input"))
    )
    (net (code "407") (name "IO_PC_LOAD") (class "Default")
      (node (ref "F32") (pin "L2") (pinfunction "IN1_L2") (pintype "input"))
      (node (ref "J11") (pin "V2") (pinfunction "P$2_V2") (pintype "bidirectional"))
    )
    (net (code "408") (name "IO_SKIP") (class "Default")
      (node (ref "E28") (pin "K2") (pinfunction "IN2B_K2") (pintype "input"))
      (node (ref "J15") (pin "E1") (pinfunction "OUT_E1") (pintype "output"))
    )
    (net (code "409") (name "IO_START_") (class "Default")
      (node (ref "E12") (pin "D1") (pinfunction "IN1_D1") (pintype "input"))
      (node (ref "E15") (pin "R2") (pinfunction "IN2_R2") (pintype "input"))
      (node (ref "E15") (pin "S1") (pinfunction "OUT_S1") (pintype "output"))
      (node (ref "E20") (pin "R1") (pinfunction "S_R1") (pintype "input"))
    )
    (net (code "410") (name "IO_STROBE") (class "Default")
      (node (ref "E26") (pin "L2") (pinfunction "IN3A_L2") (pintype "input"))
      (node (ref "F12") (pin "F1") (pinfunction "OUT_F1") (pintype "output"))
      (node (ref "F25") (pin "T2") (pinfunction "IN1_T2") (pintype "input"))
    )
    (net (code "411") (name "IPC_ENABLE") (class "Default")
      (node (ref "F09") (pin "P2") (pinfunction "OUT_P2") (pintype "output"))
      (node (ref "F20") (pin "L2") (pinfunction "IN1_L2") (pintype "input"))
    )
    (net (code "412") (name "IR0") (class "Default")
      (node (ref "E20") (pin "F1") (pinfunction "0_F1") (pintype "output"))
      (node (ref "E21") (pin "K1") (pinfunction "IN1_K1") (pintype "input"))
      (node (ref "E21") (pin "N2") (pinfunction "IN1_N2") (pintype "input"))
      (node (ref "E21") (pin "P1") (pinfunction "IN1_P1") (pintype "input"))
      (node (ref "E21") (pin "T2") (pinfunction "IN1_T2") (pintype "input"))
      (node (ref "E24") (pin "D2") (pinfunction "IN1_D2") (pintype "input"))
      (node (ref "F11") (pin "A1") (pinfunction "IN1_A1") (pintype "input"))
    )
    (net (code "413") (name "IR0_") (class "Default")
      (node (ref "E20") (pin "E1") (pinfunction "1_E1") (pintype "output"))
      (node (ref "E21") (pin "A1") (pinfunction "IN1_A1") (pintype "input"))
      (node (ref "E21") (pin "D2") (pinfunction "IN1_D2") (pintype "input"))
      (node (ref "E21") (pin "E1") (pinfunction "IN1_E1") (pintype "input"))
      (node (ref "E21") (pin "J2") (pinfunction "IN1_J2") (pintype "input"))
    )
    (net (code "414") (name "IR1") (class "Default")
      (node (ref "E20") (pin "H2") (pinfunction "1_H2") (pintype "output"))
      (node (ref "E21") (pin "F1") (pinfunction "IN2_F1") (pintype "input"))
      (node (ref "E21") (pin "K2") (pinfunction "IN2_K2") (pintype "input"))
      (node (ref "E21") (pin "P2") (pinfunction "IN2_P2") (pintype "input"))
      (node (ref "E21") (pin "U2") (pinfunction "IN2_U2") (pintype "input"))
      (node (ref "E24") (pin "E2") (pinfunction "IN2_E2") (pintype "input"))
      (node (ref "F11") (pin "B1") (pinfunction "IN2_B1") (pintype "input"))
    )
    (net (code "415") (name "IR1_") (class "Default")
      (node (ref "E20") (pin "J2") (pinfunction "0_J2") (pintype "output"))
      (node (ref "E21") (pin "B1") (pinfunction "IN2_B1") (pintype "input"))
      (node (ref "E21") (pin "E2") (pinfunction "IN2_E2") (pintype "input"))
      (node (ref "E21") (pin "L1") (pinfunction "IN2_L1") (pintype "input"))
      (node (ref "E21") (pin "R1") (pinfunction "IN2_R1") (pintype "input"))
    )
    (net (code "416") (name "IR2") (class "Default")
      (node (ref "E20") (pin "L1") (pinfunction "1_L1") (pintype "output"))
      (node (ref "E21") (pin "C1") (pinfunction "IN3_C1") (pintype "input"))
      (node (ref "E21") (pin "L2") (pinfunction "IN3_L2") (pintype "input"))
      (node (ref "E21") (pin "S1") (pinfunction "IN3_S1") (pintype "input"))
      (node (ref "E21") (pin "V2") (pinfunction "IN3_V2") (pintype "input"))
    )
    (net (code "417") (name "IR2_") (class "Default")
      (node (ref "E20") (pin "M1") (pinfunction "0_M1") (pintype "output"))
      (node (ref "E21") (pin "F2") (pinfunction "IN3_F2") (pintype "input"))
      (node (ref "E21") (pin "H1") (pinfunction "IN3_H1") (pintype "input"))
      (node (ref "E21") (pin "M1") (pinfunction "IN3_M1") (pintype "input"))
      (node (ref "E21") (pin "R2") (pinfunction "IN3_R2") (pintype "input"))
      (node (ref "F11") (pin "C1") (pinfunction "IN3_C1") (pintype "input"))
    )
    (net (code "418") (name "ISZ") (class "Default")
      (node (ref "E22") (pin "F2") (pinfunction "OUT_F2") (pintype "output"))
      (node (ref "E27") (pin "D1") (pinfunction "IN1D_D1") (pintype "input"))
      (node (ref "E28") (pin "H2") (pinfunction "IN1D_H2") (pintype "input"))
    )
    (net (code "419") (name "ISZ_") (class "Default")
      (node (ref "D40") (pin "P1") (pinfunction "P$2_P1") (pintype "bidirectional"))
      (node (ref "E21") (pin "J1") (pinfunction "OUT_J1") (pintype "output"))
      (node (ref "E22") (pin "D2") (pinfunction "IN1_D2") (pintype "input"))
    )
    (net (code "420") (name "I_IOT_") (class "Default")
      (node (ref "A05") (pin "J1") (pinfunction "IN2_J1") (pintype "input"))
      (node (ref "E21") (pin "S2") (pinfunction "OUT_S2") (pintype "output"))
      (node (ref "E22") (pin "T2") (pinfunction "IN1_T2") (pintype "input"))
    )
    (net (code "421") (name "I_M_D") (class "Default")
      (node (ref "HJ32") (pin "BU1") (pinfunction "BU1_BU1") (pintype "output"))
      (node (ref "J33") (pin "K1") (pinfunction "K1_K1") (pintype "input"))
    )
    (net (code "422") (name "JMP") (class "Default")
      (node (ref "E22") (pin "N2") (pinfunction "OUT_N2") (pintype "output"))
      (node (ref "E26") (pin "B1") (pinfunction "IN1B_B1") (pintype "input"))
      (node (ref "E26") (pin "P1") (pinfunction "IN5C_P1") (pintype "input"))
      (node (ref "E29") (pin "D1") (pinfunction "IN1D_D1") (pintype "input"))
      (node (ref "F27") (pin "B1") (pinfunction "IN2_B1") (pintype "input"))
    )
    (net (code "423") (name "JMP_") (class "Default")
      (node (ref "A17") (pin "D1") (pinfunction "IN1_D1") (pintype "input"))
      (node (ref "B20") (pin "A1") (pinfunction "IN1_A1") (pintype "input"))
      (node (ref "D40") (pin "L2") (pinfunction "P$2_L2") (pintype "bidirectional"))
      (node (ref "E21") (pin "U1") (pinfunction "OUT_U1") (pintype "output"))
      (node (ref "E22") (pin "L2") (pinfunction "IN1_L2") (pintype "input"))
      (node (ref "E24") (pin "E1") (pinfunction "IN2_E1") (pintype "input"))
      (node (ref "E29") (pin "P1") (pinfunction "IN5C_P1") (pintype "input"))
      (node (ref "F23") (pin "J1") (pinfunction "IN3_J1") (pintype "input"))
    )
    (net (code "424") (name "JMS") (class "Default")
      (node (ref "E22") (pin "K1") (pinfunction "OUT_K1") (pintype "output"))
      (node (ref "E27") (pin "P1") (pinfunction "IN5C_P1") (pintype "input"))
      (node (ref "E29") (pin "F2") (pinfunction "IN1C_F2") (pintype "input"))
      (node (ref "E30") (pin "P1") (pinfunction "IN5C_P1") (pintype "input"))
      (node (ref "F26") (pin "R2") (pinfunction "IN3_R2") (pintype "input"))
      (node (ref "F28") (pin "H1") (pinfunction "IN3_H1") (pintype "input"))
    )
    (net (code "425") (name "JMS_") (class "Default")
      (node (ref "A17") (pin "E1") (pinfunction "IN2_E1") (pintype "input"))
      (node (ref "B20") (pin "B1") (pinfunction "IN2_B1") (pintype "input"))
      (node (ref "D40") (pin "S1") (pinfunction "P$2_S1") (pintype "bidirectional"))
      (node (ref "E21") (pin "N1") (pinfunction "OUT_N1") (pintype "output"))
      (node (ref "E22") (pin "H1") (pinfunction "IN1_H1") (pintype "input"))
    )
    (net (code "426") (name "KCC_") (class "Default")
      (node (ref "EF01") (pin "AE2") (pinfunction "AE2_AE2") (pintype "output"))
      (node (ref "EF01") (pin "AV2") (pinfunction "AV2_AV2") (pintype "input"))
    )
    (net (code "427") (name "KEYBOARD_FLAG_") (class "Default")
      (node (ref "EF01") (pin "AF2") (pinfunction "AF2_AF2") (pintype "output"))
      (node (ref "F19") (pin "P1") (pinfunction "IN3_P1") (pintype "input"))
    )
    (net (code "428") (name "KEY_CONT") (class "Default")
      (node (ref "E11") (pin "S2") (pinfunction "OUT_S2") (pintype "output"))
      (node (ref "E15") (pin "J1") (pinfunction "IN2_J1") (pintype "input"))
    )
    (net (code "429") (name "KEY_CONT_") (class "Default")
      (node (ref "B40") (pin "S2") (pinfunction "P$2_S2") (pintype "bidirectional"))
      (node (ref "E11") (pin "R2") (pinfunction "IN2_R2") (pintype "input"))
      (node (ref "F19") (pin "H2") (pinfunction "IN4_H2") (pintype "input"))
    )
    (net (code "430") (name "KEY_DP") (class "Default")
      (node (ref "E11") (pin "F2") (pinfunction "OUT_F2") (pintype "output"))
      (node (ref "E29") (pin "S2") (pinfunction "IN4D_S2") (pintype "input"))
      (node (ref "F29") (pin "P1") (pinfunction "IN1_P1") (pintype "input"))
    )
    (net (code "431") (name "KEY_DP_") (class "Default")
      (node (ref "B40") (pin "M2") (pinfunction "P$2_M2") (pintype "bidirectional"))
      (node (ref "E11") (pin "D2") (pinfunction "IN1_D2") (pintype "input"))
      (node (ref "E11") (pin "H1") (pinfunction "IN1_H1") (pintype "input"))
    )
    (net (code "432") (name "KEY_EXDP") (class "Default")
      (node (ref "E11") (pin "K1") (pinfunction "OUT_K1") (pintype "output"))
      (node (ref "E11") (pin "L2") (pinfunction "IN1_L2") (pintype "input"))
      (node (ref "E13") (pin "H1") (pinfunction "IN3A_H1") (pintype "input"))
      (node (ref "E27") (pin "K2") (pinfunction "IN2B_K2") (pintype "input"))
      (node (ref "E30") (pin "L1") (pinfunction "IN4B_L1") (pintype "input"))
    )
    (net (code "433") (name "KEY_EXDP_") (class "Default")
      (node (ref "E11") (pin "N2") (pinfunction "OUT_N2") (pintype "output"))
      (node (ref "E12") (pin "H2") (pinfunction "IN1_H2") (pintype "input"))
      (node (ref "E14") (pin "L2") (pinfunction "IN3_L2") (pintype "input"))
      (node (ref "F19") (pin "F2") (pinfunction "IN3_F2") (pintype "input"))
    )
    (net (code "434") (name "KEY_EX_") (class "Default")
      (node (ref "B40") (pin "R2") (pinfunction "P$2_R2") (pintype "bidirectional"))
      (node (ref "E11") (pin "J1") (pinfunction "IN2_J1") (pintype "input"))
    )
    (net (code "435") (name "KEY_LA") (class "Default")
      (node (ref "E11") (pin "C1") (pinfunction "OUT_C1") (pintype "output"))
      (node (ref "F29") (pin "P2") (pinfunction "IN1_P2") (pintype "input"))
    )
    (net (code "436") (name "KEY_LAEXDP") (class "Default")
      (node (ref "E12") (pin "K2") (pinfunction "OUT_K2") (pintype "output"))
      (node (ref "E26") (pin "L1") (pinfunction "IN4B_L1") (pintype "input"))
      (node (ref "F21") (pin "D1") (pinfunction "IN1_D1") (pintype "input"))
    )
    (net (code "437") (name "KEY_LAEXDP_") (class "Default")
      (node (ref "F11") (pin "T2") (pinfunction "IN3_T2") (pintype "input"))
      (node (ref "F21") (pin "F1") (pinfunction "OUT_F1") (pintype "output"))
    )
    (net (code "438") (name "KEY_LAMFTS0_") (class "Default")
      (node (ref "A17") (pin "H1") (pinfunction "IN1_H1") (pintype "input"))
      (node (ref "A17") (pin "L1") (pinfunction "IN1_L1") (pintype "input"))
      (node (ref "A17") (pin "P1") (pinfunction "IN1_P1") (pintype "input"))
      (node (ref "A19") (pin "U2") (pinfunction "IN2_U2") (pintype "input"))
      (node (ref "B06") (pin "R2") (pinfunction "IN2_R2") (pintype "input"))
      (node (ref "F29") (pin "S2") (pinfunction "OUT_S2") (pintype "output"))
      (node (ref "F30") (pin "P1") (pinfunction "IN3_P1") (pintype "input"))
    )
    (net (code "439") (name "KEY_LA_") (class "Default")
      (node (ref "B40") (pin "L2") (pinfunction "P$2_L2") (pintype "bidirectional"))
      (node (ref "E11") (pin "A1") (pinfunction "IN1_A1") (pintype "input"))
      (node (ref "E12") (pin "J2") (pinfunction "IN2_J2") (pintype "input"))
      (node (ref "E15") (pin "B1") (pinfunction "IN2_B1") (pintype "input"))
      (node (ref "F19") (pin "D2") (pinfunction "IN1_D2") (pintype "input"))
    )
    (net (code "440") (name "KEY_SISTOP") (class "Default")
      (node (ref "E11") (pin "N1") (pinfunction "OUT_N1") (pintype "output"))
      (node (ref "E13") (pin "E1") (pinfunction "IN2A_E1") (pintype "input"))
    )
    (net (code "441") (name "KEY_SI_") (class "Default")
      (node (ref "B40") (pin "V2") (pinfunction "P$2_V2") (pintype "bidirectional"))
      (node (ref "E11") (pin "M1") (pinfunction "IN2_M1") (pintype "input"))
    )
    (net (code "442") (name "KEY_SS") (class "Default")
      (node (ref "E11") (pin "K2") (pinfunction "OUT_K2") (pintype "output"))
      (node (ref "E13") (pin "M1") (pinfunction "IN5A_M1") (pintype "input"))
    )
    (net (code "443") (name "KEY_SS_") (class "Default")
      (node (ref "B40") (pin "U2") (pinfunction "P$2_U2") (pintype "bidirectional"))
      (node (ref "E11") (pin "J2") (pinfunction "IN2_J2") (pintype "input"))
    )
    (net (code "444") (name "KEY_ST") (class "Default")
      (node (ref "E11") (pin "F1") (pinfunction "OUT_F1") (pintype "output"))
      (node (ref "E26") (pin "K2") (pinfunction "IN2B_K2") (pintype "input"))
      (node (ref "E26") (pin "U2") (pinfunction "IN2B_U2") (pintype "input"))
      (node (ref "E28") (pin "F1") (pinfunction "IN2B_F1") (pintype "input"))
      (node (ref "F20") (pin "U2") (pinfunction "IN2_U2") (pintype "input"))
      (node (ref "F22") (pin "E2") (pinfunction "IN2_E2") (pintype "input"))
    )
    (net (code "445") (name "KEY_STEXDP") (class "Default")
      (node (ref "A19") (pin "H2") (pinfunction "IN1_H2") (pintype "input"))
      (node (ref "E14") (pin "F2") (pinfunction "IN3_F2") (pintype "input"))
      (node (ref "E14") (pin "M2") (pinfunction "OUT_M2") (pintype "output"))
      (node (ref "F32") (pin "E1") (pinfunction "IN2_E1") (pintype "input"))
    )
    (net (code "446") (name "KEY_STOP_") (class "Default")
      (node (ref "B40") (pin "T2") (pinfunction "P$2_T2") (pintype "bidirectional"))
      (node (ref "E11") (pin "L1") (pinfunction "IN1_L1") (pintype "input"))
    )
    (net (code "447") (name "KEY_ST_") (class "Default")
      (node (ref "B40") (pin "K2") (pinfunction "P$2_K2") (pintype "bidirectional"))
      (node (ref "E11") (pin "D1") (pinfunction "IN1_D1") (pintype "input"))
      (node (ref "E14") (pin "J2") (pinfunction "IN1_J2") (pintype "input"))
      (node (ref "F19") (pin "E2") (pinfunction "IN2_E2") (pintype "input"))
    )
    (net (code "448") (name "LBAR_ENABLE") (class "Default")
      (node (ref "F29") (pin "N2") (pinfunction "OUT_N2") (pintype "output"))
      (node (ref "F33") (pin "M2") (pinfunction "IN3B_M2") (pintype "input"))
    )
    (net (code "449") (name "LEFT_SHIFT") (class "Default")
      (node (ref "E31") (pin "P2") (pinfunction "OUT_P2") (pintype "output"))
      (node (ref "EF34") (pin "AF2") (pinfunction "AF2_AF2") (pintype "input"))
      (node (ref "EF35") (pin "AF2") (pinfunction "AF2_AF2") (pintype "input"))
      (node (ref "EF36") (pin "AF2") (pinfunction "AF2_AF2") (pintype "input"))
      (node (ref "EF37") (pin "AF2") (pinfunction "AF2_AF2") (pintype "input"))
      (node (ref "EF38") (pin "AF2") (pinfunction "AF2_AF2") (pintype "input"))
      (node (ref "EF39") (pin "AF2") (pinfunction "AF2_AF2") (pintype "input"))
      (node (ref "F33") (pin "L1") (pinfunction "IN4B_L1") (pintype "input"))
    )
    (net (code "450") (name "LEFT_SHIFT_") (class "Default")
      (node (ref "D12") (pin "H2") (pinfunction "IN1_H2") (pintype "input"))
      (node (ref "D12") (pin "K1") (pinfunction "OUT_K1") (pintype "output"))
      (node (ref "D12") (pin "U2") (pinfunction "IN2_U2") (pintype "input"))
    )
    (net (code "451") (name "LHS") (class "Default")
      (node (ref "D05") (pin "E1") (pinfunction "OUT_E1") (pintype "output"))
      (node (ref "D11") (pin "M2") (pinfunction "D_M2") (pintype "input"))
    )
    (net (code "452") (name "LHS_") (class "Default")
      (node (ref "D04") (pin "T2") (pinfunction "P$2_T2") (pintype "bidirectional"))
      (node (ref "D05") (pin "A1") (pinfunction "IN_A1") (pintype "input"))
      (node (ref "D05") (pin "B1") (pinfunction "IN2_B1") (pintype "bidirectional"))
      (node (ref "D05") (pin "C1") (pinfunction "IN3_C1") (pintype "input"))
      (node (ref "D05") (pin "D1") (pinfunction "IN4_D1") (pintype "input"))
    )
    (net (code "453") (name "LH_TO_HS") (class "Default")
      (node (ref "D06") (pin "F1") (pinfunction "OUT_F1") (pintype "output"))
      (node (ref "D07") (pin "R1") (pinfunction "IN2_R1") (pintype "input"))
      (node (ref "D11") (pin "L2") (pinfunction "C_L2") (pintype "input"))
    )
    (net (code "454") (name "LIGHT_PEN") (class "Default")
      (node (ref "D03") (pin "V2") (pinfunction "P$2_V2") (pintype "bidirectional"))
      (node (ref "HJ23") (pin "AN2") (pinfunction "AN2_AN2") (pintype "input"))
    )
    (net (code "455") (name "LINE_") (class "Default")
      (node (ref "C10") (pin "P1") (pinfunction "IN1_P1") (pintype "input"))
      (node (ref "C10") (pin "T2") (pinfunction "IN1_T2") (pintype "input"))
      (node (ref "J15") (pin "P2") (pinfunction "OUT_P2") (pintype "output"))
    )
    (net (code "456") (name "LINE_HOLD_") (class "Default")
      (node (ref "C07") (pin "J2") (pinfunction "IN1_J2") (pintype "input"))
      (node (ref "D09") (pin "M1") (pinfunction "IN3_M1") (pintype "input"))
      (node (ref "D10") (pin "V2") (pinfunction "OUT_V2") (pintype "output"))
    )
    (net (code "457") (name "LINK") (class "Default")
      (node (ref "E24") (pin "T2") (pinfunction "IN1_T2") (pintype "input"))
      (node (ref "E33") (pin "V2") (pinfunction "1_V2") (pintype "output"))
      (node (ref "F33") (pin "J2") (pinfunction "IN2A_J2") (pintype "input"))
    )
    (net (code "458") (name "LINK_") (class "Default")
      (node (ref "C40") (pin "B1") (pinfunction "P$2_B1") (pintype "bidirectional"))
      (node (ref "E33") (pin "V1") (pinfunction "0_V1") (pintype "output"))
      (node (ref "F33") (pin "L2") (pinfunction "IN3A_L2") (pintype "input"))
    )
    (net (code "459") (name "LOAD_BF") (class "Default")
      (node (ref "A19") (pin "N2") (pinfunction "OUT_N2") (pintype "output"))
      (node (ref "B18") (pin "L2") (pinfunction "C_L2") (pintype "input"))
      (node (ref "B18") (pin "N1") (pinfunction "C_N1") (pintype "input"))
      (node (ref "B18") (pin "S2") (pinfunction "C_S2") (pintype "input"))
    )
    (net (code "460") (name "LOAD_COUNTER") (class "Default")
      (node (ref "H30") (pin "V2") (pinfunction "V2_V2") (pintype "input"))
      (node (ref "HJ31") (pin "BN1") (pinfunction "BN1_BN1") (pintype "output"))
    )
    (net (code "461") (name "LOAD_IB") (class "Default")
      (node (ref "A18") (pin "C1") (pinfunction "OUT_C1") (pintype "output"))
      (node (ref "B17") (pin "L2") (pinfunction "C_L2") (pintype "input"))
      (node (ref "B17") (pin "N1") (pinfunction "C_N1") (pintype "input"))
      (node (ref "B17") (pin "S2") (pinfunction "C_S2") (pintype "input"))
    )
    (net (code "462") (name "LOAD_SF_") (class "Default")
      (node (ref "A19") (pin "R1") (pinfunction "IN2_R1") (pintype "input"))
      (node (ref "A19") (pin "R2") (pinfunction "IN2_R2") (pintype "input"))
      (node (ref "C12") (pin "P2") (pinfunction "OUT_P2") (pintype "output"))
    )
    (net (code "463") (name "LOW_AC0") (class "Default")
      (node (ref "D21") (pin "D1") (pinfunction "IN4_D1") (pintype "input"))
      (node (ref "E24") (pin "S2") (pinfunction "OUT_S2") (pintype "output"))
      (node (ref "F23") (pin "C1") (pinfunction "IN3_C1") (pintype "input"))
    )
    (net (code "464") (name "L_ENABLE") (class "Default")
      (node (ref "E28") (pin "R1") (pinfunction "OUT_R1") (pintype "output"))
      (node (ref "F33") (pin "K2") (pinfunction "IN2B_K2") (pintype "input"))
    )
    (net (code "465") (name "MA00_") (class "Default")
      (node (ref "B14") (pin "A1") (pinfunction "IN1_A1") (pintype "input"))
      (node (ref "E40") (pin "U2") (pinfunction "P$2_U2") (pintype "bidirectional"))
      (node (ref "EF34") (pin "AM1") (pinfunction "AM1_AM1") (pintype "output"))
      (node (ref "F24") (pin "D2") (pinfunction "IN1_D2") (pintype "input"))
    )
    (net (code "466") (name "MA01_") (class "Default")
      (node (ref "B14") (pin "D2") (pinfunction "IN1_D2") (pintype "input"))
      (node (ref "E40") (pin "R2") (pinfunction "P$2_R2") (pintype "bidirectional"))
      (node (ref "EF34") (pin "AL1") (pinfunction "AL1_AL1") (pintype "output"))
      (node (ref "F24") (pin "E2") (pinfunction "IN2_E2") (pintype "input"))
    )
    (net (code "467") (name "MA02_") (class "Default")
      (node (ref "B14") (pin "F1") (pinfunction "IN1_F1") (pintype "input"))
      (node (ref "E40") (pin "K2") (pinfunction "P$2_K2") (pintype "bidirectional"))
      (node (ref "EF35") (pin "AM1") (pinfunction "AM1_AM1") (pintype "output"))
      (node (ref "F24") (pin "F2") (pinfunction "IN3_F2") (pintype "input"))
    )
    (net (code "468") (name "MA03_") (class "Default")
      (node (ref "B14") (pin "K2") (pinfunction "IN1_K2") (pintype "input"))
      (node (ref "E40") (pin "E2") (pinfunction "P$2_E2") (pintype "bidirectional"))
      (node (ref "EF35") (pin "AL1") (pinfunction "AL1_AL1") (pintype "output"))
      (node (ref "F24") (pin "H2") (pinfunction "IN4_H2") (pintype "input"))
    )
    (net (code "469") (name "MA04_") (class "Default")
      (node (ref "B14") (pin "M1") (pinfunction "IN1_M1") (pintype "input"))
      (node (ref "E40") (pin "L1") (pinfunction "P$2_L1") (pintype "bidirectional"))
      (node (ref "EF36") (pin "AM1") (pinfunction "AM1_AM1") (pintype "output"))
      (node (ref "F24") (pin "F1") (pinfunction "IN1_F1") (pintype "input"))
    )
    (net (code "470") (name "MA05_") (class "Default")
      (node (ref "B14") (pin "R2") (pinfunction "IN1_R2") (pintype "input"))
      (node (ref "E40") (pin "E1") (pinfunction "P$2_E1") (pintype "bidirectional"))
      (node (ref "EF36") (pin "AL1") (pinfunction "AL1_AL1") (pintype "output"))
      (node (ref "F24") (pin "H1") (pinfunction "IN2_H1") (pintype "input"))
    )
    (net (code "471") (name "MA06_") (class "Default")
      (node (ref "B15") (pin "A1") (pinfunction "IN1_A1") (pintype "input"))
      (node (ref "EF37") (pin "AM1") (pinfunction "AM1_AM1") (pintype "output"))
      (node (ref "F24") (pin "J1") (pinfunction "IN3_J1") (pintype "input"))
      (node (ref "F40") (pin "U2") (pinfunction "P$2_U2") (pintype "bidirectional"))
    )
    (net (code "472") (name "MA07_") (class "Default")
      (node (ref "B15") (pin "D2") (pinfunction "IN1_D2") (pintype "input"))
      (node (ref "EF37") (pin "AL1") (pinfunction "AL1_AL1") (pintype "output"))
      (node (ref "F24") (pin "K1") (pinfunction "IN4_K1") (pintype "input"))
      (node (ref "F40") (pin "R2") (pinfunction "P$2_R2") (pintype "bidirectional"))
    )
    (net (code "473") (name "MA08") (class "Default")
      (node (ref "EF38") (pin "AM2") (pinfunction "AM2_AM2") (pintype "output"))
      (node (ref "F25") (pin "L1") (pinfunction "IN1_L1") (pintype "input"))
    )
    (net (code "474") (name "MA08_") (class "Default")
      (node (ref "B15") (pin "F1") (pinfunction "IN1_F1") (pintype "input"))
      (node (ref "EF38") (pin "AM1") (pinfunction "AM1_AM1") (pintype "output"))
      (node (ref "F40") (pin "K2") (pinfunction "P$2_K2") (pintype "bidirectional"))
    )
    (net (code "475") (name "MA09_") (class "Default")
      (node (ref "B15") (pin "K2") (pinfunction "IN1_K2") (pintype "input"))
      (node (ref "EF38") (pin "AL1") (pinfunction "AL1_AL1") (pintype "output"))
      (node (ref "F40") (pin "E2") (pinfunction "P$2_E2") (pintype "bidirectional"))
    )
    (net (code "476") (name "MA10_") (class "Default")
      (node (ref "B15") (pin "M1") (pinfunction "IN1_M1") (pintype "input"))
      (node (ref "EF39") (pin "AM1") (pinfunction "AM1_AM1") (pintype "output"))
      (node (ref "F40") (pin "L1") (pinfunction "P$2_L1") (pintype "bidirectional"))
    )
    (net (code "477") (name "MA11_") (class "Default")
      (node (ref "B15") (pin "R2") (pinfunction "IN1_R2") (pintype "input"))
      (node (ref "EF39") (pin "AL1") (pinfunction "AL1_AL1") (pintype "output"))
      (node (ref "F40") (pin "E1") (pinfunction "P$2_E1") (pintype "bidirectional"))
    )
    (net (code "478") (name "MANUAL_PRESET_") (class "Default")
      (node (ref "B11") (pin "D1") (pinfunction "S_D1") (pintype "input"))
      (node (ref "B11") (pin "F2") (pinfunction "S_F2") (pintype "input"))
      (node (ref "B11") (pin "K1") (pinfunction "S_K1") (pintype "input"))
      (node (ref "D11") (pin "D1") (pinfunction "S_D1") (pintype "input"))
      (node (ref "D11") (pin "F2") (pinfunction "S_F2") (pintype "input"))
      (node (ref "E18") (pin "D1") (pinfunction "S_D1") (pintype "input"))
      (node (ref "E19") (pin "A1") (pinfunction "R_A1") (pintype "input"))
      (node (ref "E20") (pin "K2") (pinfunction "R_K2") (pintype "input"))
      (node (ref "E23") (pin "A1") (pinfunction "R_A1") (pintype "input"))
      (node (ref "E23") (pin "K2") (pinfunction "R_K2") (pintype "input"))
      (node (ref "E33") (pin "K1") (pinfunction "S_K1") (pintype "input"))
      (node (ref "F20") (pin "E1") (pinfunction "IN2_E1") (pintype "input"))
      (node (ref "F30") (pin "V2") (pinfunction "OUT_V2") (pintype "output"))
    )
    (net (code "479") (name "MA_ENABLE0_4") (class "Default")
      (node (ref "EF34") (pin "BP1") (pinfunction "BP1_BP1") (pintype "input"))
      (node (ref "EF34") (pin "BR2") (pinfunction "BR2_BR2") (pintype "input"))
      (node (ref "EF35") (pin "BP1") (pinfunction "BP1_BP1") (pintype "input"))
      (node (ref "EF35") (pin "BR2") (pinfunction "BR2_BR2") (pintype "input"))
      (node (ref "EF36") (pin "BP1") (pinfunction "BP1_BP1") (pintype "input"))
      (node (ref "F31") (pin "L1") (pinfunction "OUT_L1") (pintype "output"))
    )
    (net (code "480") (name "MA_ENABLE5_11") (class "Default")
      (node (ref "EF36") (pin "BR2") (pinfunction "BR2_BR2") (pintype "input"))
      (node (ref "EF37") (pin "BP1") (pinfunction "BP1_BP1") (pintype "input"))
      (node (ref "EF37") (pin "BR2") (pinfunction "BR2_BR2") (pintype "input"))
      (node (ref "EF38") (pin "BP1") (pinfunction "BP1_BP1") (pintype "input"))
      (node (ref "EF38") (pin "BR2") (pinfunction "BR2_BR2") (pintype "input"))
      (node (ref "EF39") (pin "BP1") (pinfunction "BP1_BP1") (pintype "input"))
      (node (ref "EF39") (pin "BR2") (pinfunction "BR2_BR2") (pintype "input"))
      (node (ref "F31") (pin "P2") (pinfunction "OUT_P2") (pintype "output"))
    )
    (net (code "481") (name "MA_LOAD") (class "Default")
      (node (ref "E32") (pin "E1") (pinfunction "OUT_E1") (pintype "output"))
      (node (ref "EF34") (pin "AK1") (pinfunction "AK1_AK1") (pintype "input"))
      (node (ref "EF35") (pin "AK1") (pinfunction "AK1_AK1") (pintype "input"))
      (node (ref "EF36") (pin "AK1") (pinfunction "AK1_AK1") (pintype "input"))
      (node (ref "EF37") (pin "AK1") (pinfunction "AK1_AK1") (pintype "input"))
      (node (ref "EF38") (pin "AK1") (pinfunction "AK1_AK1") (pintype "input"))
      (node (ref "EF39") (pin "AK1") (pinfunction "AK1_AK1") (pintype "input"))
    )
    (net (code "482") (name "MB00") (class "Default")
      (node (ref "A09") (pin "E1") (pinfunction "1A_E1") (pintype "input"))
      (node (ref "B12") (pin "A1") (pinfunction "IN1_A1") (pintype "input"))
      (node (ref "EF34") (pin "AT2") (pinfunction "AT2_AT2") (pintype "output"))
      (node (ref "H13") (pin "H2") (pinfunction "IN2_H2") (pintype "input"))
    )
    (net (code "483") (name "MB00_") (class "Default")
      (node (ref "A09") (pin "A1") (pinfunction "1B_A1") (pintype "input"))
      (node (ref "E40") (pin "R1") (pinfunction "P$2_R1") (pintype "bidirectional"))
      (node (ref "EF34") (pin "AU2") (pinfunction "AU2_AU2") (pintype "output"))
    )
    (net (code "484") (name "MB01") (class "Default")
      (node (ref "A09") (pin "F1") (pinfunction "2A_F1") (pintype "input"))
      (node (ref "B12") (pin "D2") (pinfunction "IN1_D2") (pintype "input"))
      (node (ref "EF34") (pin "AS2") (pinfunction "AS2_AS2") (pintype "output"))
      (node (ref "H13") (pin "N2") (pinfunction "IN2_N2") (pintype "input"))
    )
    (net (code "485") (name "MB01_") (class "Default")
      (node (ref "A09") (pin "B1") (pinfunction "2B_B1") (pintype "input"))
      (node (ref "E40") (pin "P1") (pinfunction "P$2_P1") (pintype "bidirectional"))
      (node (ref "EF34") (pin "AS1") (pinfunction "AS1_AS1") (pintype "output"))
    )
    (net (code "486") (name "MB02") (class "Default")
      (node (ref "A09") (pin "H1") (pinfunction "4A_H1") (pintype "input"))
      (node (ref "B12") (pin "F1") (pinfunction "IN1_F1") (pintype "input"))
      (node (ref "EF35") (pin "AT2") (pinfunction "AT2_AT2") (pintype "output"))
      (node (ref "H13") (pin "U2") (pinfunction "IN2_U2") (pintype "input"))
    )
    (net (code "487") (name "MB02_") (class "Default")
      (node (ref "A09") (pin "C1") (pinfunction "4B_C1") (pintype "input"))
      (node (ref "E40") (pin "F2") (pinfunction "P$2_F2") (pintype "bidirectional"))
      (node (ref "EF35") (pin "AU2") (pinfunction "AU2_AU2") (pintype "output"))
    )
    (net (code "488") (name "MB03") (class "Default")
      (node (ref "A09") (pin "J1") (pinfunction "8A_J1") (pintype "input"))
      (node (ref "B12") (pin "K2") (pinfunction "IN1_K2") (pintype "input"))
      (node (ref "C11") (pin "P1") (pinfunction "IN1_P1") (pintype "input"))
      (node (ref "D20") (pin "P1") (pinfunction "IN3_P1") (pintype "input"))
      (node (ref "E25") (pin "L2") (pinfunction "IN3_L2") (pintype "input"))
      (node (ref "EF35") (pin "AS2") (pinfunction "AS2_AS2") (pintype "output"))
      (node (ref "F27") (pin "K1") (pinfunction "IN4_K1") (pintype "input"))
      (node (ref "H14") (pin "N2") (pinfunction "IN2_N2") (pintype "input"))
      (node (ref "HJ29") (pin "AF2") (pinfunction "AF2_AF2") (pintype "input"))
      (node (ref "J33") (pin "C1") (pinfunction "C1_C1") (pintype "input"))
    )
    (net (code "489") (name "MB03_") (class "Default")
      (node (ref "A04") (pin "D2") (pinfunction "D2_D2") (pintype "input"))
      (node (ref "A09") (pin "D1") (pinfunction "8B_D1") (pintype "input"))
      (node (ref "B07") (pin "A1") (pinfunction "IN1_A1") (pintype "input"))
      (node (ref "B16") (pin "L2") (pinfunction "IN2_L2") (pintype "input"))
      (node (ref "E26") (pin "C1") (pinfunction "IN1C_C1") (pintype "input"))
      (node (ref "E40") (pin "D2") (pinfunction "P$2_D2") (pintype "bidirectional"))
      (node (ref "EF01") (pin "AD2") (pinfunction "AD2_AD2") (pintype "input"))
      (node (ref "EF02") (pin "AE2") (pinfunction "AE2_AE2") (pintype "input"))
      (node (ref "EF35") (pin "AS1") (pinfunction "AS1_AS1") (pintype "output"))
      (node (ref "F09") (pin "B1") (pinfunction "IN2_B1") (pintype "input"))
      (node (ref "F19") (pin "T2") (pinfunction "IN3_T2") (pintype "input"))
      (node (ref "F23") (pin "K1") (pinfunction "IN4_K1") (pintype "input"))
      (node (ref "F27") (pin "D1") (pinfunction "IN4_D1") (pintype "input"))
      (node (ref "F27") (pin "U2") (pinfunction "IN4_U2") (pintype "input"))
      (node (ref "H14") (pin "H2") (pinfunction "IN2_H2") (pintype "input"))
      (node (ref "H30") (pin "T2") (pinfunction "T2_T2") (pintype "input"))
      (node (ref "HJ23") (pin "BF2") (pinfunction "BF2_BF2") (pintype "input"))
      (node (ref "HJ26") (pin "BD2") (pinfunction "BD2_BD2") (pintype "input"))
      (node (ref "HJ28") (pin "BF2") (pinfunction "BF2_BF2") (pintype "input"))
    )
    (net (code "490") (name "MB04") (class "Default")
      (node (ref "A10") (pin "P2") (pinfunction "1A_P2") (pintype "input"))
      (node (ref "B12") (pin "M1") (pinfunction "IN1_M1") (pintype "input"))
      (node (ref "B16") (pin "M2") (pinfunction "IN3_M2") (pintype "input"))
      (node (ref "E30") (pin "V1") (pinfunction "IN2A_V1") (pintype "input"))
      (node (ref "EF36") (pin "AT2") (pinfunction "AT2_AT2") (pintype "output"))
      (node (ref "F09") (pin "C1") (pinfunction "IN3_C1") (pintype "input"))
      (node (ref "F28") (pin "F2") (pinfunction "IN3_F2") (pintype "input"))
      (node (ref "H15") (pin "H2") (pinfunction "IN2_H2") (pintype "input"))
      (node (ref "J33") (pin "D2") (pinfunction "D2_D2") (pintype "input"))
    )
    (net (code "491") (name "MB04_") (class "Default")
      (node (ref "A04") (pin "E2") (pinfunction "E2_E2") (pintype "input"))
      (node (ref "A10") (pin "K2") (pinfunction "1B_K2") (pintype "input"))
      (node (ref "B07") (pin "B1") (pinfunction "IN2_B1") (pintype "input"))
      (node (ref "C11") (pin "R1") (pinfunction "IN2_R1") (pintype "input"))
      (node (ref "D21") (pin "J1") (pinfunction "IN3_J1") (pintype "input"))
      (node (ref "E30") (pin "H2") (pinfunction "IN1D_H2") (pintype "input"))
      (node (ref "E30") (pin "S1") (pinfunction "IN1A_S1") (pintype "input"))
      (node (ref "E40") (pin "K1") (pinfunction "P$2_K1") (pintype "bidirectional"))
      (node (ref "EF01") (pin "AE1") (pinfunction "AE1_AE1") (pintype "input"))
      (node (ref "EF02") (pin "AE1") (pinfunction "AE1_AE1") (pintype "input"))
      (node (ref "EF36") (pin "AU2") (pinfunction "AU2_AU2") (pintype "output"))
      (node (ref "F19") (pin "U2") (pinfunction "IN4_U2") (pintype "input"))
      (node (ref "H14") (pin "U2") (pinfunction "IN2_U2") (pintype "input"))
      (node (ref "H30") (pin "S2") (pinfunction "S2_S2") (pintype "input"))
      (node (ref "HJ23") (pin "BH2") (pinfunction "BH2_BH2") (pintype "input"))
      (node (ref "HJ26") (pin "BE2") (pinfunction "BE2_BE2") (pintype "input"))
      (node (ref "HJ28") (pin "BD1") (pinfunction "BD1_BD1") (pintype "input"))
      (node (ref "HJ29") (pin "AH2") (pinfunction "AH2_AH2") (pintype "input"))
    )
    (net (code "492") (name "MB05") (class "Default")
      (node (ref "A04") (pin "F2") (pinfunction "F2_F2") (pintype "input"))
      (node (ref "A10") (pin "R2") (pinfunction "2A_R2") (pintype "input"))
      (node (ref "B07") (pin "C1") (pinfunction "IN3_C1") (pintype "input"))
      (node (ref "B12") (pin "R2") (pinfunction "IN1_R2") (pintype "input"))
      (node (ref "D18") (pin "D2") (pinfunction "IN1_D2") (pintype "input"))
      (node (ref "E24") (pin "M1") (pinfunction "IN2_M1") (pintype "input"))
      (node (ref "E28") (pin "M1") (pinfunction "IN5A_M1") (pintype "input"))
      (node (ref "EF36") (pin "AS2") (pinfunction "AS2_AS2") (pintype "output"))
      (node (ref "H15") (pin "U2") (pinfunction "IN2_U2") (pintype "input"))
      (node (ref "H30") (pin "R2") (pinfunction "R2_R2") (pintype "input"))
      (node (ref "HJ29") (pin "AE2") (pinfunction "AE2_AE2") (pintype "input"))
    )
    (net (code "493") (name "MB05_") (class "Default")
      (node (ref "A10") (pin "L2") (pinfunction "2B_L2") (pintype "input"))
      (node (ref "B16") (pin "N2") (pinfunction "IN4_N2") (pintype "input"))
      (node (ref "C11") (pin "S1") (pinfunction "IN3_S1") (pintype "input"))
      (node (ref "E28") (pin "B1") (pinfunction "IN1B_B1") (pintype "input"))
      (node (ref "E40") (pin "A1") (pinfunction "P$2_A1") (pintype "bidirectional"))
      (node (ref "EF01") (pin "AF1") (pinfunction "AF1_AF1") (pintype "input"))
      (node (ref "EF02") (pin "AF2") (pinfunction "AF2_AF2") (pintype "input"))
      (node (ref "EF36") (pin "AS1") (pinfunction "AS1_AS1") (pintype "output"))
      (node (ref "F09") (pin "D1") (pinfunction "IN4_D1") (pintype "input"))
      (node (ref "F23") (pin "R2") (pinfunction "IN1_R2") (pintype "input"))
      (node (ref "H15") (pin "N2") (pinfunction "IN2_N2") (pintype "input"))
      (node (ref "HJ23") (pin "BK2") (pinfunction "BK2_BK2") (pintype "input"))
      (node (ref "HJ26") (pin "BE1") (pinfunction "BE1_BE1") (pintype "input"))
      (node (ref "HJ28") (pin "BD2") (pinfunction "BD2_BD2") (pintype "input"))
      (node (ref "J33") (pin "B1") (pinfunction "B1_B1") (pintype "input"))
    )
    (net (code "494") (name "MB06") (class "Default")
      (node (ref "A10") (pin "S2") (pinfunction "4A_S2") (pintype "input"))
      (node (ref "A12") (pin "E2") (pinfunction "IN2_E2") (pintype "input"))
      (node (ref "A15") (pin "T2") (pinfunction "IN1_T2") (pintype "input"))
      (node (ref "A18") (pin "E2") (pinfunction "IN2_E2") (pintype "input"))
      (node (ref "B13") (pin "A1") (pinfunction "IN1_A1") (pintype "input"))
      (node (ref "D18") (pin "H1") (pinfunction "IN3_H1") (pintype "input"))
      (node (ref "E30") (pin "U1") (pinfunction "IN1B_U1") (pintype "input"))
      (node (ref "EF02") (pin "AF1") (pinfunction "AF1_AF1") (pintype "input"))
      (node (ref "EF37") (pin "AT2") (pinfunction "AT2_AT2") (pintype "output"))
      (node (ref "F23") (pin "D1") (pinfunction "IN4_D1") (pintype "input"))
      (node (ref "F32") (pin "J2") (pinfunction "IN2_J2") (pintype "input"))
      (node (ref "H16") (pin "N2") (pinfunction "IN2_N2") (pintype "input"))
      (node (ref "HJ23") (pin "BM2") (pinfunction "BM2_BM2") (pintype "input"))
      (node (ref "J33") (pin "D1") (pinfunction "D1_D1") (pintype "input"))
    )
    (net (code "495") (name "MB06XMB09") (class "Default")
      (node (ref "A06") (pin "N2") (pinfunction "OUT_N2") (pintype "output"))
      (node (ref "A06") (pin "U2") (pinfunction "IN2_U2") (pintype "input"))
      (node (ref "B04") (pin "F1") (pinfunction "IN2_F1") (pintype "input"))
      (node (ref "B06") (pin "B1") (pinfunction "IN2_B1") (pintype "input"))
    )
    (net (code "496") (name "MB06_") (class "Default")
      (node (ref "A04") (pin "H2") (pinfunction "H2_H2") (pintype "input"))
      (node (ref "A10") (pin "M2") (pinfunction "4B_M2") (pintype "input"))
      (node (ref "B07") (pin "D2") (pinfunction "IN1_D2") (pintype "input"))
      (node (ref "C11") (pin "T2") (pinfunction "IN1_T2") (pintype "input"))
      (node (ref "E30") (pin "U2") (pinfunction "IN2B_U2") (pintype "input"))
      (node (ref "EF01") (pin "AH1") (pinfunction "AH1_AH1") (pintype "input"))
      (node (ref "EF37") (pin "AU2") (pinfunction "AU2_AU2") (pintype "output"))
      (node (ref "F09") (pin "D2") (pinfunction "IN5_D2") (pintype "input"))
      (node (ref "F23") (pin "S2") (pinfunction "IN2_S2") (pintype "input"))
      (node (ref "F40") (pin "R1") (pinfunction "P$2_R1") (pintype "bidirectional"))
      (node (ref "H16") (pin "H2") (pinfunction "IN2_H2") (pintype "input"))
      (node (ref "H30") (pin "P2") (pinfunction "P2_P2") (pintype "input"))
      (node (ref "HJ26") (pin "BF2") (pinfunction "BF2_BF2") (pintype "input"))
      (node (ref "HJ28") (pin "BE1") (pinfunction "BE1_BE1") (pintype "input"))
      (node (ref "HJ29") (pin "AD2") (pinfunction "AD2_AD2") (pintype "input"))
      (node (ref "J33") (pin "E2") (pinfunction "E2_E2") (pintype "input"))
    )
    (net (code "497") (name "MB07") (class "Default")
      (node (ref "A10") (pin "T2") (pinfunction "8A_T2") (pintype "input"))
      (node (ref "A12") (pin "M1") (pinfunction "IN2_M1") (pintype "input"))
      (node (ref "A18") (pin "M1") (pinfunction "IN2_M1") (pintype "input"))
      (node (ref "A20") (pin "R1") (pinfunction "IN2_R1") (pintype "input"))
      (node (ref "A20") (pin "R2") (pinfunction "IN3_R2") (pintype "input"))
      (node (ref "B06") (pin "A1") (pinfunction "IN1_A1") (pintype "input"))
      (node (ref "B13") (pin "D2") (pinfunction "IN1_D2") (pintype "input"))
      (node (ref "D18") (pin "K1") (pinfunction "IN1_K1") (pintype "input"))
      (node (ref "D21") (pin "H1") (pinfunction "IN2_H1") (pintype "input"))
      (node (ref "E24") (pin "U2") (pinfunction "IN2_U2") (pintype "input"))
      (node (ref "E28") (pin "D1") (pinfunction "IN1D_D1") (pintype "input"))
      (node (ref "EF01") (pin "AH2") (pinfunction "AH2_AH2") (pintype "input"))
      (node (ref "EF37") (pin "AS2") (pinfunction "AS2_AS2") (pintype "output"))
      (node (ref "F29") (pin "U2") (pinfunction "IN2_U2") (pintype "input"))
      (node (ref "H17") (pin "H2") (pinfunction "IN2_H2") (pintype "input"))
      (node (ref "H30") (pin "N2") (pinfunction "N2_N2") (pintype "input"))
      (node (ref "HJ23") (pin "BL2") (pinfunction "BL2_BL2") (pintype "input"))
      (node (ref "HJ28") (pin "BE2") (pinfunction "BE2_BE2") (pintype "input"))
      (node (ref "HJ29") (pin "AS2") (pinfunction "AS2_AS2") (pintype "input"))
      (node (ref "J33") (pin "A1") (pinfunction "A1_A1") (pintype "input"))
    )
    (net (code "498") (name "MB07_") (class "Default")
      (node (ref "A04") (pin "J2") (pinfunction "J2_J2") (pintype "input"))
      (node (ref "A06") (pin "P1") (pinfunction "IN1_P1") (pintype "input"))
      (node (ref "A10") (pin "N2") (pinfunction "8B_N2") (pintype "input"))
      (node (ref "A20") (pin "L1") (pinfunction "IN2_L1") (pintype "input"))
      (node (ref "B04") (pin "A1") (pinfunction "IN1_A1") (pintype "input"))
      (node (ref "B04") (pin "H1") (pinfunction "IN3_H1") (pintype "input"))
      (node (ref "B07") (pin "E2") (pinfunction "IN2_E2") (pintype "input"))
      (node (ref "C11") (pin "U2") (pinfunction "IN2_U2") (pintype "input"))
      (node (ref "C14") (pin "U2") (pinfunction "IN2_U2") (pintype "input"))
      (node (ref "E28") (pin "P1") (pinfunction "IN5C_P1") (pintype "input"))
      (node (ref "EF02") (pin "AH2") (pinfunction "AH2_AH2") (pintype "input"))
      (node (ref "EF37") (pin "AS1") (pinfunction "AS1_AS1") (pintype "output"))
      (node (ref "F23") (pin "T2") (pinfunction "IN3_T2") (pintype "input"))
      (node (ref "F40") (pin "P1") (pinfunction "P$2_P1") (pintype "bidirectional"))
      (node (ref "H16") (pin "U2") (pinfunction "IN2_U2") (pintype "input"))
      (node (ref "HJ23") (pin "BE2") (pinfunction "BE2_BE2") (pintype "input"))
      (node (ref "HJ26") (pin "BF1") (pinfunction "BF1_BF1") (pintype "input"))
      (node (ref "HJ29") (pin "BU1") (pinfunction "BU1_BU1") (pintype "input"))
    )
    (net (code "499") (name "MB08") (class "Default")
      (node (ref "A09") (pin "P2") (pinfunction "1A_P2") (pintype "input"))
      (node (ref "A12") (pin "R2") (pinfunction "IN2_R2") (pintype "input"))
      (node (ref "A18") (pin "R2") (pinfunction "IN2_R2") (pintype "input"))
      (node (ref "A20") (pin "M1") (pinfunction "IN3_M1") (pintype "input"))
      (node (ref "A20") (pin "P2") (pinfunction "IN2_P2") (pintype "input"))
      (node (ref "B04") (pin "E1") (pinfunction "IN1_E1") (pintype "input"))
      (node (ref "B06") (pin "M1") (pinfunction "IN2_M1") (pintype "input"))
      (node (ref "B13") (pin "F1") (pinfunction "IN1_F1") (pintype "input"))
      (node (ref "D24") (pin "C1") (pinfunction "D_C1") (pintype "input"))
      (node (ref "E28") (pin "R2") (pinfunction "IN4C_R2") (pintype "input"))
      (node (ref "EF01") (pin "AJ1") (pinfunction "AJ1_AJ1") (pintype "input"))
      (node (ref "EF38") (pin "AT2") (pinfunction "AT2_AT2") (pintype "output"))
      (node (ref "F26") (pin "D2") (pinfunction "IN1_D2") (pintype "input"))
      (node (ref "F26") (pin "E1") (pinfunction "IN1_E1") (pintype "input"))
      (node (ref "H17") (pin "U2") (pinfunction "IN2_U2") (pintype "input"))
      (node (ref "H30") (pin "M2") (pinfunction "M2_M2") (pintype "input"))
      (node (ref "HJ23") (pin "BN2") (pinfunction "BN2_BN2") (pintype "input"))
      (node (ref "HJ26") (pin "BH2") (pinfunction "BH2_BH2") (pintype "input"))
      (node (ref "HJ29") (pin "AK2") (pinfunction "AK2_AK2") (pintype "input"))
      (node (ref "J33") (pin "E1") (pinfunction "E1_E1") (pintype "input"))
    )
    (net (code "500") (name "MB08_") (class "Default")
      (node (ref "A04") (pin "K2") (pinfunction "K2_K2") (pintype "input"))
      (node (ref "A06") (pin "R1") (pinfunction "IN2_R1") (pintype "input"))
      (node (ref "A09") (pin "K2") (pinfunction "1B_K2") (pintype "input"))
      (node (ref "A20") (pin "S1") (pinfunction "IN3_S1") (pintype "input"))
      (node (ref "B04") (pin "B1") (pinfunction "IN2_B1") (pintype "input"))
      (node (ref "B07") (pin "F2") (pinfunction "IN3_F2") (pintype "input"))
      (node (ref "C11") (pin "V2") (pinfunction "IN3_V2") (pintype "input"))
      (node (ref "C15") (pin "U2") (pinfunction "IN2_U2") (pintype "input"))
      (node (ref "E28") (pin "M2") (pinfunction "IN3B_M2") (pintype "input"))
      (node (ref "EF02") (pin "AJ2") (pinfunction "AJ2_AJ2") (pintype "input"))
      (node (ref "EF38") (pin "AU2") (pinfunction "AU2_AU2") (pintype "output"))
      (node (ref "F23") (pin "U2") (pinfunction "IN4_U2") (pintype "input"))
      (node (ref "F26") (pin "K1") (pinfunction "IN1_K1") (pintype "input"))
      (node (ref "F40") (pin "F2") (pinfunction "P$2_F2") (pintype "bidirectional"))
      (node (ref "H17") (pin "N2") (pinfunction "IN2_N2") (pintype "input"))
      (node (ref "HJ23") (pin "BJ2") (pinfunction "BJ2_BJ2") (pintype "input"))
      (node (ref "HJ28") (pin "BF1") (pinfunction "BF1_BF1") (pintype "input"))
      (node (ref "HJ29") (pin "BV1") (pinfunction "BV1_BV1") (pintype "input"))
    )
    (net (code "501") (name "MB09") (class "Default")
      (node (ref "A09") (pin "R2") (pinfunction "2A_R2") (pintype "input"))
      (node (ref "A14") (pin "D2") (pinfunction "IN1_D2") (pintype "input"))
      (node (ref "B13") (pin "K2") (pinfunction "IN1_K2") (pintype "input"))
      (node (ref "C11") (pin "L1") (pinfunction "IN2_L1") (pintype "input"))
      (node (ref "D13") (pin "E1") (pinfunction "IN2_E1") (pintype "input"))
      (node (ref "D24") (pin "E2") (pinfunction "D_E2") (pintype "input"))
      (node (ref "EF38") (pin "AS2") (pinfunction "AS2_AS2") (pintype "output"))
      (node (ref "F09") (pin "E2") (pinfunction "IN6_E2") (pintype "input"))
      (node (ref "F20") (pin "J2") (pinfunction "IN2_J2") (pintype "input"))
      (node (ref "F26") (pin "A1") (pinfunction "IN1_A1") (pintype "input"))
      (node (ref "F26") (pin "J2") (pinfunction "IN1_J2") (pintype "input"))
      (node (ref "F28") (pin "R2") (pinfunction "IN3_R2") (pintype "input"))
      (node (ref "H18") (pin "H2") (pinfunction "IN2_H2") (pintype "input"))
      (node (ref "H30") (pin "U2") (pinfunction "U2_U2") (pintype "input"))
    )
    (net (code "502") (name "MB09_") (class "Default")
      (node (ref "A05") (pin "B1") (pinfunction "IN2_B1") (pintype "input"))
      (node (ref "A09") (pin "L2") (pinfunction "2B_L2") (pintype "input"))
      (node (ref "C16") (pin "U2") (pinfunction "IN2_U2") (pintype "input"))
      (node (ref "D13") (pin "P1") (pinfunction "IN1_P1") (pintype "input"))
      (node (ref "EF38") (pin "AS1") (pinfunction "AS1_AS1") (pintype "output"))
      (node (ref "F26") (pin "M1") (pinfunction "IN3_M1") (pintype "input"))
      (node (ref "F40") (pin "D2") (pinfunction "P$2_D2") (pintype "bidirectional"))
      (node (ref "H30") (pin "N1") (pinfunction "N1_N1") (pintype "input"))
      (node (ref "HJ23") (pin "AK2") (pinfunction "AK2_AK2") (pintype "input"))
    )
    (net (code "503") (name "MB10") (class "Default")
      (node (ref "A09") (pin "S2") (pinfunction "4A_S2") (pintype "input"))
      (node (ref "A12") (pin "B1") (pinfunction "IN2_B1") (pintype "input"))
      (node (ref "A15") (pin "P2") (pinfunction "IN1_P2") (pintype "input"))
      (node (ref "B13") (pin "M1") (pinfunction "IN1_M1") (pintype "input"))
      (node (ref "D10") (pin "D1") (pinfunction "IN4_D1") (pintype "input"))
      (node (ref "D10") (pin "F2") (pinfunction "IN3_F2") (pintype "input"))
      (node (ref "D24") (pin "J1") (pinfunction "D_J1") (pintype "input"))
      (node (ref "E13") (pin "A1") (pinfunction "IN1A_A1") (pintype "input"))
      (node (ref "E14") (pin "H1") (pinfunction "IN3_H1") (pintype "input"))
      (node (ref "EF39") (pin "AT2") (pinfunction "AT2_AT2") (pintype "output"))
      (node (ref "F20") (pin "J1") (pinfunction "IN2_J1") (pintype "input"))
      (node (ref "F26") (pin "C1") (pinfunction "IN3_C1") (pintype "input"))
      (node (ref "F26") (pin "F2") (pinfunction "IN3_F2") (pintype "input"))
      (node (ref "H18") (pin "N2") (pinfunction "IN2_N2") (pintype "input"))
      (node (ref "H30") (pin "L1") (pinfunction "L1_L1") (pintype "input"))
      (node (ref "HJ23") (pin "AN1") (pinfunction "AN1_AN1") (pintype "input"))
      (node (ref "HJ31") (pin "BJ1") (pinfunction "BJ1_BJ1") (pintype "input"))
    )
    (net (code "504") (name "MB10_") (class "Default")
      (node (ref "A05") (pin "A1") (pinfunction "IN1_A1") (pintype "input"))
      (node (ref "A09") (pin "M2") (pinfunction "4B_M2") (pintype "input"))
      (node (ref "A15") (pin "L1") (pinfunction "IN1_L1") (pintype "input"))
      (node (ref "C17") (pin "U2") (pinfunction "IN2_U2") (pintype "input"))
      (node (ref "D13") (pin "R1") (pinfunction "IN2_R1") (pintype "input"))
      (node (ref "EF39") (pin "AU2") (pinfunction "AU2_AU2") (pintype "output"))
      (node (ref "F21") (pin "L2") (pinfunction "IN1_L2") (pintype "input"))
      (node (ref "F26") (pin "H1") (pinfunction "IN3_H1") (pintype "input"))
      (node (ref "F26") (pin "L2") (pinfunction "IN3_L2") (pintype "input"))
      (node (ref "F40") (pin "K1") (pinfunction "P$2_K1") (pintype "bidirectional"))
      (node (ref "HJ31") (pin "BP1") (pinfunction "BP1_BP1") (pintype "input"))
    )
    (net (code "505") (name "MB11") (class "Default")
      (node (ref "A09") (pin "T2") (pinfunction "8A_T2") (pintype "input"))
      (node (ref "A11") (pin "B1") (pinfunction "IN2_B1") (pintype "input"))
      (node (ref "B13") (pin "R2") (pinfunction "IN1_R2") (pintype "input"))
      (node (ref "D10") (pin "R1") (pinfunction "IN4_R1") (pintype "input"))
      (node (ref "D10") (pin "U2") (pinfunction "IN4_U2") (pintype "input"))
      (node (ref "D18") (pin "E1") (pinfunction "IN1_E1") (pintype "input"))
      (node (ref "D18") (pin "F2") (pinfunction "IN3_F2") (pintype "input"))
      (node (ref "D20") (pin "R1") (pinfunction "IN4_R1") (pintype "input"))
      (node (ref "D21") (pin "F1") (pinfunction "IN1_F1") (pintype "input"))
      (node (ref "E27") (pin "J1") (pinfunction "IN3B_J1") (pintype "input"))
      (node (ref "EF39") (pin "AS2") (pinfunction "AS2_AS2") (pintype "output"))
      (node (ref "F20") (pin "E2") (pinfunction "IN2_E2") (pintype "input"))
      (node (ref "H18") (pin "U2") (pinfunction "IN2_U2") (pintype "input"))
      (node (ref "H30") (pin "A1") (pinfunction "A1_A1") (pintype "input"))
      (node (ref "HJ23") (pin "AP1") (pinfunction "AP1_AP1") (pintype "input"))
    )
    (net (code "506") (name "MB11_") (class "Default")
      (node (ref "A09") (pin "N2") (pinfunction "8B_N2") (pintype "input"))
      (node (ref "A13") (pin "A1") (pinfunction "IN1_A1") (pintype "input"))
      (node (ref "B04") (pin "D2") (pinfunction "IN1_D2") (pintype "input"))
      (node (ref "C18") (pin "R1") (pinfunction "IN2_R1") (pintype "input"))
      (node (ref "D09") (pin "F2") (pinfunction "IN3_F2") (pintype "input"))
      (node (ref "D10") (pin "H2") (pinfunction "IN4_H2") (pintype "input"))
      (node (ref "E13") (pin "B1") (pinfunction "IN1B_B1") (pintype "input"))
      (node (ref "E25") (pin "N2") (pinfunction "IN1_N2") (pintype "input"))
      (node (ref "E28") (pin "S2") (pinfunction "IN4D_S2") (pintype "input"))
      (node (ref "E33") (pin "P1") (pinfunction "D_P1") (pintype "input"))
      (node (ref "EF39") (pin "AS1") (pinfunction "AS1_AS1") (pintype "output"))
      (node (ref "F21") (pin "M2") (pinfunction "IN2_M2") (pintype "input"))
      (node (ref "F28") (pin "P2") (pinfunction "IN2_P2") (pintype "input"))
      (node (ref "F40") (pin "A1") (pinfunction "P$2_A1") (pintype "bidirectional"))
    )
    (net (code "507") (name "MB_LOAD") (class "Default")
      (node (ref "E32") (pin "L1") (pinfunction "OUT_L1") (pintype "output"))
      (node (ref "EF34") (pin "AR1") (pinfunction "AR1_AR1") (pintype "input"))
      (node (ref "EF35") (pin "AR1") (pinfunction "AR1_AR1") (pintype "input"))
      (node (ref "EF36") (pin "AR1") (pinfunction "AR1_AR1") (pintype "input"))
      (node (ref "EF37") (pin "AR1") (pinfunction "AR1_AR1") (pintype "input"))
      (node (ref "EF38") (pin "AR1") (pinfunction "AR1_AR1") (pintype "input"))
      (node (ref "EF39") (pin "AR1") (pinfunction "AR1_AR1") (pintype "input"))
    )
    (net (code "508") (name "MB_PARITY_ODD") (class "Default")
      (node (ref "A10") (pin "K1") (pinfunction "ODD_K1") (pintype "output"))
      (node (ref "H05") (pin "T2") (pinfunction "P$2_T2") (pintype "bidirectional"))
    )
    (net (code "509") (name "MB_TO_IB") (class "Default")
      (node (ref "A15") (pin "S1") (pinfunction "OUT_S1") (pintype "output"))
      (node (ref "A18") (pin "D2") (pinfunction "IN1_D2") (pintype "input"))
      (node (ref "A18") (pin "L1") (pinfunction "IN1_L1") (pintype "input"))
      (node (ref "A18") (pin "P2") (pinfunction "IN1_P2") (pintype "input"))
    )
    (net (code "510") (name "MB_TO_SC_ENABLE") (class "Default")
      (node (ref "C14") (pin "T2") (pinfunction "IN1_T2") (pintype "input"))
      (node (ref "C15") (pin "T2") (pinfunction "IN1_T2") (pintype "input"))
      (node (ref "C16") (pin "T2") (pinfunction "IN1_T2") (pintype "input"))
      (node (ref "C17") (pin "T2") (pinfunction "IN1_T2") (pintype "input"))
      (node (ref "C18") (pin "P1") (pinfunction "IN1_P1") (pintype "input"))
      (node (ref "D15") (pin "N2") (pinfunction "OUT_N2") (pintype "output"))
    )
    (net (code "511") (name "MCBMB00_") (class "Default")
      (node (ref "B12") (pin "E1") (pinfunction "OUT_E1") (pintype "output"))
      (node (ref "H02") (pin "S2") (pinfunction "P$2_S2") (pintype "bidirectional"))
    )
    (net (code "512") (name "MCBMB01_") (class "Default")
      (node (ref "B12") (pin "J2") (pinfunction "OUT_J2") (pintype "output"))
      (node (ref "H02") (pin "T2") (pinfunction "P$2_T2") (pintype "bidirectional"))
    )
    (net (code "513") (name "MCBMB02_") (class "Default")
      (node (ref "B12") (pin "L1") (pinfunction "OUT_L1") (pintype "output"))
      (node (ref "H02") (pin "V2") (pinfunction "P$2_V2") (pintype "bidirectional"))
    )
    (net (code "514") (name "MCBMB03_") (class "Default")
      (node (ref "B12") (pin "P2") (pinfunction "OUT_P2") (pintype "output"))
      (node (ref "H03") (pin "D2") (pinfunction "P$2_D2") (pintype "bidirectional"))
    )
    (net (code "515") (name "MCBMB04_") (class "Default")
      (node (ref "B12") (pin "S1") (pinfunction "OUT_S1") (pintype "output"))
      (node (ref "H03") (pin "E2") (pinfunction "P$2_E2") (pintype "bidirectional"))
    )
    (net (code "516") (name "MCBMB05_") (class "Default")
      (node (ref "B12") (pin "V2") (pinfunction "OUT_V2") (pintype "output"))
      (node (ref "H03") (pin "H2") (pinfunction "P$2_H2") (pintype "bidirectional"))
    )
    (net (code "517") (name "MCBMB06_") (class "Default")
      (node (ref "B13") (pin "E1") (pinfunction "OUT_E1") (pintype "output"))
      (node (ref "H03") (pin "K2") (pinfunction "P$2_K2") (pintype "bidirectional"))
    )
    (net (code "518") (name "MCBMB07_") (class "Default")
      (node (ref "B13") (pin "J2") (pinfunction "OUT_J2") (pintype "output"))
      (node (ref "H03") (pin "M2") (pinfunction "P$2_M2") (pintype "bidirectional"))
    )
    (net (code "519") (name "MCBMB08_") (class "Default")
      (node (ref "B13") (pin "L1") (pinfunction "OUT_L1") (pintype "output"))
      (node (ref "H03") (pin "P2") (pinfunction "P$2_P2") (pintype "bidirectional"))
    )
    (net (code "520") (name "MCBMB09_") (class "Default")
      (node (ref "B13") (pin "P2") (pinfunction "OUT_P2") (pintype "output"))
      (node (ref "H03") (pin "S2") (pinfunction "P$2_S2") (pintype "bidirectional"))
    )
    (net (code "521") (name "MCBMB10_") (class "Default")
      (node (ref "B13") (pin "S1") (pinfunction "OUT_S1") (pintype "output"))
      (node (ref "H03") (pin "T2") (pinfunction "P$2_T2") (pintype "bidirectional"))
    )
    (net (code "522") (name "MCBMB11_") (class "Default")
      (node (ref "B13") (pin "V2") (pinfunction "OUT_V2") (pintype "output"))
      (node (ref "H03") (pin "V2") (pinfunction "P$2_V2") (pintype "bidirectional"))
    )
    (net (code "523") (name "ME05_") (class "Default")
      (node (ref "A05") (pin "K2") (pinfunction "OUT_K2") (pintype "output"))
      (node (ref "J13") (pin "U2") (pinfunction "IN4_U2") (pintype "input"))
    )
    (net (code "524") (name "ME06_") (class "Default")
      (node (ref "A13") (pin "N1") (pinfunction "OUT_N1") (pintype "output"))
      (node (ref "J14") (pin "D1") (pinfunction "IN4_D1") (pintype "input"))
    )
    (net (code "525") (name "ME07_") (class "Default")
      (node (ref "A13") (pin "S1") (pinfunction "OUT_S1") (pintype "output"))
      (node (ref "J14") (pin "H2") (pinfunction "IN4_H2") (pintype "input"))
    )
    (net (code "526") (name "ME08_") (class "Default")
      (node (ref "A13") (pin "V2") (pinfunction "OUT_V2") (pintype "output"))
      (node (ref "J14") (pin "K1") (pinfunction "IN4_K1") (pintype "input"))
    )
    (net (code "527") (name "ME09_") (class "Default")
      (node (ref "A13") (pin "K2") (pinfunction "OUT_K2") (pintype "output"))
      (node (ref "J14") (pin "N2") (pinfunction "IN4_N2") (pintype "input"))
    )
    (net (code "528") (name "ME10_") (class "Default")
      (node (ref "A13") (pin "N2") (pinfunction "OUT_N2") (pintype "output"))
      (node (ref "J14") (pin "R1") (pinfunction "IN4_R1") (pintype "input"))
    )
    (net (code "529") (name "ME11_") (class "Default")
      (node (ref "A13") (pin "S2") (pinfunction "OUT_S2") (pintype "output"))
      (node (ref "J14") (pin "U2") (pinfunction "IN4_U2") (pintype "input"))
    )
    (net (code "530") (name "MEM00") (class "Default")
      (node (ref "A07") (pin "E1") (pinfunction "1A_E1") (pintype "input"))
      (node (ref "B08") (pin "H1") (pinfunction "IN1_H1") (pintype "input"))
      (node (ref "C09") (pin "A1") (pinfunction "IN1_A1") (pintype "input"))
      (node (ref "EF34") (pin "BR1") (pinfunction "BR1_BR1") (pintype "input"))
      (node (ref "F22") (pin "B1") (pinfunction "IN2_B1") (pintype "input"))
      (node (ref "H04") (pin "E2") (pinfunction "P$2_E2") (pintype "bidirectional"))
    )
    (net (code "531") (name "MEM01") (class "Default")
      (node (ref "A07") (pin "F1") (pinfunction "2A_F1") (pintype "input"))
      (node (ref "B08") (pin "D2") (pinfunction "IN1_D2") (pintype "input"))
      (node (ref "E20") (pin "E2") (pinfunction "D_E2") (pintype "input"))
      (node (ref "EF34") (pin "BV2") (pinfunction "BV2_BV2") (pintype "input"))
      (node (ref "H04") (pin "H2") (pinfunction "P$2_H2") (pintype "bidirectional"))
    )
    (net (code "532") (name "MEM02") (class "Default")
      (node (ref "A07") (pin "H1") (pinfunction "4A_H1") (pintype "input"))
      (node (ref "B08") (pin "D1") (pinfunction "IN1_D1") (pintype "input"))
      (node (ref "E20") (pin "J1") (pinfunction "D_J1") (pintype "input"))
      (node (ref "EF35") (pin "BR1") (pinfunction "BR1_BR1") (pintype "input"))
      (node (ref "H04") (pin "K2") (pinfunction "P$2_K2") (pintype "bidirectional"))
    )
    (net (code "533") (name "MEM03") (class "Default")
      (node (ref "A07") (pin "J1") (pinfunction "8A_J1") (pintype "input"))
      (node (ref "B08") (pin "A1") (pinfunction "IN1_A1") (pintype "input"))
      (node (ref "EF35") (pin "BV2") (pinfunction "BV2_BV2") (pintype "input"))
      (node (ref "H04") (pin "M2") (pinfunction "P$2_M2") (pintype "bidirectional"))
    )
    (net (code "534") (name "MEM04") (class "Default")
      (node (ref "A08") (pin "P2") (pinfunction "1A_P2") (pintype "input"))
      (node (ref "B08") (pin "P1") (pinfunction "IN1_P1") (pintype "input"))
      (node (ref "EF36") (pin "BR1") (pinfunction "BR1_BR1") (pintype "input"))
      (node (ref "H04") (pin "P2") (pinfunction "P$2_P2") (pintype "bidirectional"))
    )
    (net (code "535") (name "MEM05") (class "Default")
      (node (ref "A08") (pin "R2") (pinfunction "2A_R2") (pintype "input"))
      (node (ref "B08") (pin "L2") (pinfunction "IN1_L2") (pintype "input"))
      (node (ref "EF36") (pin "BV2") (pinfunction "BV2_BV2") (pintype "input"))
      (node (ref "H04") (pin "S2") (pinfunction "P$2_S2") (pintype "bidirectional"))
    )
    (net (code "536") (name "MEM06") (class "Default")
      (node (ref "A08") (pin "S2") (pinfunction "4A_S2") (pintype "input"))
      (node (ref "B08") (pin "L1") (pinfunction "IN1_L1") (pintype "input"))
      (node (ref "EF37") (pin "BR1") (pinfunction "BR1_BR1") (pintype "input"))
      (node (ref "H04") (pin "T2") (pinfunction "P$2_T2") (pintype "bidirectional"))
    )
    (net (code "537") (name "MEM07") (class "Default")
      (node (ref "A08") (pin "T2") (pinfunction "8A_T2") (pintype "input"))
      (node (ref "B08") (pin "H2") (pinfunction "IN1_H2") (pintype "input"))
      (node (ref "EF37") (pin "BV2") (pinfunction "BV2_BV2") (pintype "input"))
      (node (ref "H04") (pin "V2") (pinfunction "P$2_V2") (pintype "bidirectional"))
    )
    (net (code "538") (name "MEM08") (class "Default")
      (node (ref "A07") (pin "P2") (pinfunction "1A_P2") (pintype "input"))
      (node (ref "B09") (pin "D1") (pinfunction "IN1_D1") (pintype "input"))
      (node (ref "EF38") (pin "BR1") (pinfunction "BR1_BR1") (pintype "input"))
      (node (ref "H05") (pin "D2") (pinfunction "P$2_D2") (pintype "bidirectional"))
    )
    (net (code "539") (name "MEM09") (class "Default")
      (node (ref "A07") (pin "R2") (pinfunction "2A_R2") (pintype "input"))
      (node (ref "B09") (pin "A1") (pinfunction "IN1_A1") (pintype "input"))
      (node (ref "D09") (pin "C1") (pinfunction "IN3_C1") (pintype "input"))
      (node (ref "EF38") (pin "BV2") (pinfunction "BV2_BV2") (pintype "input"))
      (node (ref "H05") (pin "E2") (pinfunction "P$2_E2") (pintype "bidirectional"))
    )
    (net (code "540") (name "MEM10") (class "Default")
      (node (ref "A07") (pin "S2") (pinfunction "4A_S2") (pintype "input"))
      (node (ref "B08") (pin "T2") (pinfunction "IN1_T2") (pintype "input"))
      (node (ref "EF39") (pin "BR1") (pinfunction "BR1_BR1") (pintype "input"))
      (node (ref "H05") (pin "H2") (pinfunction "P$2_H2") (pintype "bidirectional"))
    )
    (net (code "541") (name "MEM11") (class "Default")
      (node (ref "A07") (pin "T2") (pinfunction "8A_T2") (pintype "input"))
      (node (ref "B08") (pin "P2") (pinfunction "IN1_P2") (pintype "input"))
      (node (ref "EF39") (pin "BV2") (pinfunction "BV2_BV2") (pintype "input"))
      (node (ref "H05") (pin "K2") (pinfunction "P$2_K2") (pintype "bidirectional"))
    )
    (net (code "542") (name "MEMORY_INCREMENT") (class "Default")
      (node (ref "E11") (pin "U2") (pinfunction "IN2_U2") (pintype "input"))
      (node (ref "E27") (pin "R2") (pinfunction "IN4C_R2") (pintype "input"))
      (node (ref "J20") (pin "E1") (pinfunction "OUT_E1") (pintype "output"))
    )
    (net (code "543") (name "MEM_DONE_") (class "Default")
      (node (ref "B10") (pin "D2") (pinfunction "D2_D2") (pintype "open_collector"))
      (node (ref "C07") (pin "T2") (pinfunction "IN3_T2") (pintype "input"))
      (node (ref "E18") (pin "F2") (pinfunction "S_F2") (pintype "input"))
      (node (ref "E33") (pin "F2") (pinfunction "S_F2") (pintype "input"))
      (node (ref "H05") (pin "S2") (pinfunction "P$2_S2") (pintype "bidirectional"))
    )
    (net (code "544") (name "MEM_ENABLE0_4") (class "Default")
      (node (ref "EF34") (pin "BU2") (pinfunction "BU2_BU2") (pintype "input"))
      (node (ref "EF34") (pin "BV1") (pinfunction "BV1_BV1") (pintype "input"))
      (node (ref "EF35") (pin "BU2") (pinfunction "BU2_BU2") (pintype "input"))
      (node (ref "EF35") (pin "BV1") (pinfunction "BV1_BV1") (pintype "input"))
      (node (ref "EF36") (pin "BU2") (pinfunction "BU2_BU2") (pintype "input"))
      (node (ref "F27") (pin "R1") (pinfunction "IN4_R1") (pintype "input"))
      (node (ref "F29") (pin "A1") (pinfunction "IN1_A1") (pintype "input"))
      (node (ref "F31") (pin "E1") (pinfunction "OUT_E1") (pintype "output"))
    )
    (net (code "545") (name "MEM_ENABLE0_4_") (class "Default")
      (node (ref "F28") (pin "E2") (pinfunction "IN2_E2") (pintype "input"))
      (node (ref "F29") (pin "C1") (pinfunction "OUT_C1") (pintype "output"))
      (node (ref "F31") (pin "F2") (pinfunction "IN3_F2") (pintype "input"))
    )
    (net (code "546") (name "MEM_ENABLE5_8") (class "Default")
      (node (ref "E09") (pin "H2") (pinfunction "IN1_H2") (pintype "input"))
      (node (ref "EF36") (pin "BV1") (pinfunction "BV1_BV1") (pintype "input"))
      (node (ref "EF37") (pin "BU2") (pinfunction "BU2_BU2") (pintype "input"))
      (node (ref "EF37") (pin "BV1") (pinfunction "BV1_BV1") (pintype "input"))
      (node (ref "EF38") (pin "BU2") (pinfunction "BU2_BU2") (pintype "input"))
      (node (ref "F28") (pin "D2") (pinfunction "IN1_D2") (pintype "input"))
      (node (ref "F31") (pin "J2") (pinfunction "OUT_J2") (pintype "output"))
    )
    (net (code "547") (name "MEM_ENABLE9_11") (class "Default")
      (node (ref "EF38") (pin "BV1") (pinfunction "BV1_BV1") (pintype "input"))
      (node (ref "EF39") (pin "BU2") (pinfunction "BU2_BU2") (pintype "input"))
      (node (ref "EF39") (pin "BV1") (pinfunction "BV1_BV1") (pintype "input"))
      (node (ref "F11") (pin "P2") (pinfunction "OUT_P2") (pintype "output"))
    )
    (net (code "548") (name "MEM_EXT") (class "Default")
      (node (ref "A11") (pin "A1") (pinfunction "IN1_A1") (pintype "input"))
      (node (ref "A13") (pin "E2") (pinfunction "IN2_E2") (pintype "input"))
      (node (ref "A14") (pin "E2") (pinfunction "IN2_E2") (pintype "input"))
      (node (ref "A14") (pin "K1") (pinfunction "OUT_K1") (pintype "output"))
      (node (ref "A15") (pin "R2") (pinfunction "IN2_R2") (pintype "input"))
    )
    (net (code "549") (name "MEM_EXT_") (class "Default")
      (node (ref "A14") (pin "F1") (pinfunction "OUT_F1") (pintype "output"))
      (node (ref "A14") (pin "H1") (pinfunction "IN1_H1") (pintype "input"))
      (node (ref "F19") (pin "B1") (pinfunction "IN2_B1") (pintype "input"))
    )
    (net (code "550") (name "MEM_EXT_AC_LOAD_ENABLE_") (class "Default")
      (node (ref "A14") (pin "S2") (pinfunction "OUT_S2") (pintype "output"))
      (node (ref "E32") (pin "N2") (pinfunction "IN4_N2") (pintype "input"))
    )
    (net (code "551") (name "MEM_EXT_IO_ENABLE_") (class "Default")
      (node (ref "C12") (pin "J2") (pinfunction "OUT_J2") (pintype "output"))
      (node (ref "F30") (pin "E2") (pinfunction "IN2_E2") (pintype "input"))
    )
    (net (code "552") (name "MEM_IDLE") (class "Default")
      (node (ref "E14") (pin "A1") (pinfunction "IN1_A1") (pintype "input"))
      (node (ref "E18") (pin "H2") (pinfunction "1_H2") (pintype "output"))
    )
    (net (code "553") (name "MEM_INH9_11_") (class "Default")
      (node (ref "C09") (pin "K2") (pinfunction "OUT_K2") (pintype "output"))
      (node (ref "D10") (pin "J1") (pinfunction "IN3_J1") (pintype "input"))
      (node (ref "E09") (pin "J2") (pinfunction "IN2_J2") (pintype "input"))
    )
    (net (code "554") (name "MEM_P") (class "Default")
      (node (ref "A08") (pin "J1") (pinfunction "8A_J1") (pintype "input"))
      (node (ref "B08") (pin "V1") (pinfunction "P$1_V1") (pintype "passive"))
      (node (ref "B09") (pin "E2") (pinfunction "IN2_E2") (pintype "input"))
      (node (ref "H04") (pin "D2") (pinfunction "P$2_D2") (pintype "bidirectional"))
    )
    (net (code "555") (name "MEM_PARITY_EVEN_") (class "Default")
      (node (ref "A08") (pin "L1") (pinfunction "EVEN_L1") (pintype "output"))
      (node (ref "B09") (pin "P1") (pinfunction "IN1_P1") (pintype "input"))
    )
    (net (code "556") (name "MEM_TO_LSR_") (class "Default")
      (node (ref "C08") (pin "P2") (pinfunction "IN2_P2") (pintype "input"))
      (node (ref "D07") (pin "K1") (pinfunction "OUT_K1") (pintype "output"))
    )
    (net (code "557") (name "MFTP0") (class "Default")
      (node (ref "EF10") (pin "AT2") (pinfunction "CT2_AT2") (pintype "output"))
      (node (ref "F20") (pin "T2") (pinfunction "IN1_T2") (pintype "input"))
      (node (ref "F30") (pin "U2") (pinfunction "IN4_U2") (pintype "input"))
    )
    (net (code "558") (name "MFTP1") (class "Default")
      (node (ref "A19") (pin "J2") (pinfunction "IN2_J2") (pintype "input"))
      (node (ref "E12") (pin "M2") (pinfunction "IN2_M2") (pintype "input"))
      (node (ref "EF10") (pin "AE2") (pinfunction "CE2_AE2") (pintype "output"))
      (node (ref "F32") (pin "D1") (pinfunction "IN1_D1") (pintype "input"))
    )
    (net (code "559") (name "MFTP2") (class "Default")
      (node (ref "E15") (pin "A1") (pinfunction "IN1_A1") (pintype "input"))
      (node (ref "E15") (pin "H1") (pinfunction "IN1_H1") (pintype "input"))
      (node (ref "E26") (pin "J2") (pinfunction "IN2A_J2") (pintype "input"))
      (node (ref "E26") (pin "K1") (pinfunction "IN4A_K1") (pintype "input"))
      (node (ref "E26") (pin "V1") (pinfunction "IN2A_V1") (pintype "input"))
      (node (ref "EF10") (pin "BD2") (pinfunction "DD2_BD2") (pintype "output"))
      (node (ref "F22") (pin "D2") (pinfunction "IN1_D2") (pintype "input"))
    )
    (net (code "560") (name "MFTS0") (class "Default")
      (node (ref "E13") (pin "J1") (pinfunction "IN3B_J1") (pintype "input"))
      (node (ref "E14") (pin "T2") (pinfunction "IN1_T2") (pintype "input"))
      (node (ref "EF10") (pin "AM2") (pinfunction "CM2_AM2") (pintype "output"))
      (node (ref "F29") (pin "R2") (pinfunction "IN2_R2") (pintype "input"))
    )
    (net (code "561") (name "MFTS1") (class "Default")
      (node (ref "E14") (pin "E2") (pinfunction "IN2_E2") (pintype "input"))
      (node (ref "EF10") (pin "AJ2") (pinfunction "CJ2_AJ2") (pintype "output"))
    )
    (net (code "562") (name "MFTS1_") (class "Default")
      (node (ref "E14") (pin "U2") (pinfunction "IN2_U2") (pintype "input"))
      (node (ref "EF10") (pin "AK2") (pinfunction "CK2_AK2") (pintype "output"))
    )
    (net (code "563") (name "MFTS2") (class "Default")
      (node (ref "E27") (pin "J2") (pinfunction "IN2A_J2") (pintype "input"))
      (node (ref "E28") (pin "E1") (pinfunction "IN2A_E1") (pintype "input"))
      (node (ref "E30") (pin "K1") (pinfunction "IN4A_K1") (pintype "input"))
      (node (ref "EF10") (pin "AF2") (pinfunction "CF2_AF2") (pintype "output"))
    )
    (net (code "564") (name "MFTS2_") (class "Default")
      (node (ref "D12") (pin "R1") (pinfunction "IN2_R1") (pintype "input"))
      (node (ref "E14") (pin "V2") (pinfunction "IN3_V2") (pintype "input"))
      (node (ref "EF10") (pin "AH2") (pinfunction "CH2_AH2") (pintype "output"))
    )
    (net (code "565") (name "MFTS3") (class "Default")
      (node (ref "E15") (pin "V2") (pinfunction "OUT_V2") (pintype "output"))
      (node (ref "E29") (pin "N2") (pinfunction "IN4A_N2") (pintype "input"))
      (node (ref "F29") (pin "R1") (pinfunction "IN2_R1") (pintype "input"))
    )
    (net (code "566") (name "MID_AC0") (class "Default")
      (node (ref "D19") (pin "M1") (pinfunction "IN3_M1") (pintype "input"))
      (node (ref "D20") (pin "B1") (pinfunction "IN2_B1") (pintype "input"))
      (node (ref "E24") (pin "S1") (pinfunction "OUT_S1") (pintype "output"))
      (node (ref "F23") (pin "B1") (pinfunction "IN2_B1") (pintype "input"))
    )
    (net (code "567") (name "MP_INT_") (class "Default")
      (node (ref "B07") (pin "L2") (pinfunction "IN3_L2") (pintype "input"))
      (node (ref "B11") (pin "P2") (pinfunction "1_P2") (pintype "output"))
      (node (ref "J15") (pin "H2") (pinfunction "IN4_H2") (pintype "input"))
    )
    (net (code "568") (name "MP_SKIP_") (class "Default")
      (node (ref "B07") (pin "M2") (pinfunction "OUT_M2") (pintype "output"))
      (node (ref "J15") (pin "D1") (pinfunction "IN4_D1") (pintype "input"))
    )
    (net (code "569") (name "MQ00") (class "Default")
      (node (ref "C14") (pin "J1") (pinfunction "IN2_J1") (pintype "input"))
      (node (ref "C23") (pin "E1") (pinfunction "1_E1") (pintype "output"))
      (node (ref "D18") (pin "S1") (pinfunction "IN3_S1") (pintype "input"))
      (node (ref "EF34") (pin "BH1") (pinfunction "BH1_BH1") (pintype "input"))
    )
    (net (code "570") (name "MQ00_") (class "Default")
      (node (ref "C23") (pin "F1") (pinfunction "0_F1") (pintype "output"))
      (node (ref "D18") (pin "N2") (pinfunction "IN1_N2") (pintype "input"))
      (node (ref "D21") (pin "K2") (pinfunction "IN1_K2") (pintype "input"))
      (node (ref "E40") (pin "S2") (pinfunction "P$2_S2") (pintype "bidirectional"))
    )
    (net (code "571") (name "MQ01") (class "Default")
      (node (ref "C14") (pin "E2") (pinfunction "IN2_E2") (pintype "input"))
      (node (ref "C14") (pin "M2") (pinfunction "IN2_M2") (pintype "input"))
      (node (ref "C23") (pin "H2") (pinfunction "1_H2") (pintype "output"))
      (node (ref "EF34") (pin "BN2") (pinfunction "BN2_BN2") (pintype "input"))
    )
    (net (code "572") (name "MQ01_") (class "Default")
      (node (ref "C23") (pin "J2") (pinfunction "0_J2") (pintype "output"))
      (node (ref "D21") (pin "L2") (pinfunction "IN2_L2") (pintype "input"))
      (node (ref "E40") (pin "M2") (pinfunction "P$2_M2") (pintype "bidirectional"))
    )
    (net (code "573") (name "MQ02") (class "Default")
      (node (ref "C14") (pin "M1") (pinfunction "IN2_M1") (pintype "input"))
      (node (ref "C15") (pin "B1") (pinfunction "IN2_B1") (pintype "input"))
      (node (ref "C23") (pin "L1") (pinfunction "1_L1") (pintype "output"))
      (node (ref "EF35") (pin "BH1") (pinfunction "BH1_BH1") (pintype "input"))
    )
    (net (code "574") (name "MQ02_") (class "Default")
      (node (ref "C23") (pin "M1") (pinfunction "0_M1") (pintype "output"))
      (node (ref "D21") (pin "M2") (pinfunction "IN3_M2") (pintype "input"))
      (node (ref "E40") (pin "N2") (pinfunction "P$2_N2") (pintype "bidirectional"))
    )
    (net (code "575") (name "MQ03") (class "Default")
      (node (ref "C14") (pin "R2") (pinfunction "IN2_R2") (pintype "input"))
      (node (ref "C15") (pin "J1") (pinfunction "IN2_J1") (pintype "input"))
      (node (ref "C23") (pin "P2") (pinfunction "1_P2") (pintype "output"))
      (node (ref "EF35") (pin "BN2") (pinfunction "BN2_BN2") (pintype "input"))
    )
    (net (code "576") (name "MQ03_") (class "Default")
      (node (ref "C23") (pin "R2") (pinfunction "0_R2") (pintype "output"))
      (node (ref "D21") (pin "N2") (pinfunction "IN4_N2") (pintype "input"))
      (node (ref "E40") (pin "L2") (pinfunction "P$2_L2") (pintype "bidirectional"))
    )
    (net (code "577") (name "MQ04") (class "Default")
      (node (ref "C15") (pin "E2") (pinfunction "IN2_E2") (pintype "input"))
      (node (ref "C15") (pin "M2") (pinfunction "IN2_M2") (pintype "input"))
      (node (ref "C23") (pin "S1") (pinfunction "1_S1") (pintype "output"))
      (node (ref "EF36") (pin "BH1") (pinfunction "BH1_BH1") (pintype "input"))
    )
    (net (code "578") (name "MQ04_") (class "Default")
      (node (ref "C23") (pin "U1") (pinfunction "0_U1") (pintype "output"))
      (node (ref "D21") (pin "M1") (pinfunction "IN1_M1") (pintype "input"))
      (node (ref "E40") (pin "F1") (pinfunction "P$2_F1") (pintype "bidirectional"))
    )
    (net (code "579") (name "MQ05") (class "Default")
      (node (ref "C15") (pin "M1") (pinfunction "IN2_M1") (pintype "input"))
      (node (ref "C16") (pin "B1") (pinfunction "IN2_B1") (pintype "input"))
      (node (ref "C23") (pin "V2") (pinfunction "1_V2") (pintype "output"))
      (node (ref "EF36") (pin "BN2") (pinfunction "BN2_BN2") (pintype "input"))
    )
    (net (code "580") (name "MQ05_") (class "Default")
      (node (ref "C23") (pin "V1") (pinfunction "0_V1") (pintype "output"))
      (node (ref "D21") (pin "N1") (pinfunction "IN2_N1") (pintype "input"))
      (node (ref "E40") (pin "H1") (pinfunction "P$2_H1") (pintype "bidirectional"))
    )
    (net (code "581") (name "MQ06") (class "Default")
      (node (ref "C15") (pin "R2") (pinfunction "IN2_R2") (pintype "input"))
      (node (ref "C16") (pin "J1") (pinfunction "IN2_J1") (pintype "input"))
      (node (ref "C24") (pin "E1") (pinfunction "1_E1") (pintype "output"))
      (node (ref "EF37") (pin "BH1") (pinfunction "BH1_BH1") (pintype "input"))
    )
    (net (code "582") (name "MQ06_") (class "Default")
      (node (ref "C24") (pin "F1") (pinfunction "0_F1") (pintype "output"))
      (node (ref "D21") (pin "P1") (pinfunction "IN3_P1") (pintype "input"))
      (node (ref "F40") (pin "S2") (pinfunction "P$2_S2") (pintype "bidirectional"))
    )
    (net (code "583") (name "MQ07") (class "Default")
      (node (ref "C16") (pin "E2") (pinfunction "IN2_E2") (pintype "input"))
      (node (ref "C16") (pin "M2") (pinfunction "IN2_M2") (pintype "input"))
      (node (ref "C24") (pin "H2") (pinfunction "1_H2") (pintype "output"))
      (node (ref "EF37") (pin "BN2") (pinfunction "BN2_BN2") (pintype "input"))
    )
    (net (code "584") (name "MQ07_") (class "Default")
      (node (ref "C24") (pin "J2") (pinfunction "0_J2") (pintype "output"))
      (node (ref "D21") (pin "R1") (pinfunction "IN4_R1") (pintype "input"))
      (node (ref "F40") (pin "M2") (pinfunction "P$2_M2") (pintype "bidirectional"))
    )
    (net (code "585") (name "MQ08") (class "Default")
      (node (ref "C16") (pin "M1") (pinfunction "IN2_M1") (pintype "input"))
      (node (ref "C17") (pin "B1") (pinfunction "IN2_B1") (pintype "input"))
      (node (ref "C24") (pin "L1") (pinfunction "1_L1") (pintype "output"))
      (node (ref "EF38") (pin "BH1") (pinfunction "BH1_BH1") (pintype "input"))
    )
    (net (code "586") (name "MQ08_") (class "Default")
      (node (ref "C24") (pin "M1") (pinfunction "0_M1") (pintype "output"))
      (node (ref "D21") (pin "R2") (pinfunction "IN1_R2") (pintype "input"))
      (node (ref "F40") (pin "N2") (pinfunction "P$2_N2") (pintype "bidirectional"))
    )
    (net (code "587") (name "MQ09") (class "Default")
      (node (ref "C16") (pin "R2") (pinfunction "IN2_R2") (pintype "input"))
      (node (ref "C17") (pin "J1") (pinfunction "IN2_J1") (pintype "input"))
      (node (ref "C24") (pin "P2") (pinfunction "1_P2") (pintype "output"))
      (node (ref "EF38") (pin "BN2") (pinfunction "BN2_BN2") (pintype "input"))
    )
    (net (code "588") (name "MQ09_") (class "Default")
      (node (ref "C24") (pin "R2") (pinfunction "0_R2") (pintype "output"))
      (node (ref "D21") (pin "S2") (pinfunction "IN2_S2") (pintype "input"))
      (node (ref "F40") (pin "L2") (pinfunction "P$2_L2") (pintype "bidirectional"))
    )
    (net (code "589") (name "MQ10") (class "Default")
      (node (ref "C17") (pin "E2") (pinfunction "IN2_E2") (pintype "input"))
      (node (ref "C17") (pin "M2") (pinfunction "IN2_M2") (pintype "input"))
      (node (ref "C24") (pin "S1") (pinfunction "1_S1") (pintype "output"))
      (node (ref "D13") (pin "D2") (pinfunction "IN1_D2") (pintype "input"))
      (node (ref "D23") (pin "V1") (pinfunction "IN2A_V1") (pintype "input"))
      (node (ref "EF39") (pin "BH1") (pinfunction "BH1_BH1") (pintype "input"))
    )
    (net (code "590") (name "MQ10_") (class "Default")
      (node (ref "C24") (pin "U1") (pinfunction "0_U1") (pintype "output"))
      (node (ref "D12") (pin "E2") (pinfunction "IN2_E2") (pintype "input"))
      (node (ref "D21") (pin "T2") (pinfunction "IN3_T2") (pintype "input"))
      (node (ref "F40") (pin "F1") (pinfunction "P$2_F1") (pintype "bidirectional"))
    )
    (net (code "591") (name "MQ11") (class "Default")
      (node (ref "C17") (pin "M1") (pinfunction "IN2_M1") (pintype "input"))
      (node (ref "C24") (pin "V2") (pinfunction "1_V2") (pintype "output"))
      (node (ref "D20") (pin "K2") (pinfunction "IN1_K2") (pintype "input"))
      (node (ref "D23") (pin "J2") (pinfunction "IN2A_J2") (pintype "input"))
      (node (ref "D23") (pin "U1") (pinfunction "IN1B_U1") (pintype "input"))
      (node (ref "EF39") (pin "BN2") (pinfunction "BN2_BN2") (pintype "input"))
    )
    (net (code "592") (name "MQ11_") (class "Default")
      (node (ref "C24") (pin "V1") (pinfunction "0_V1") (pintype "output"))
      (node (ref "D13") (pin "U2") (pinfunction "IN2_U2") (pintype "input"))
      (node (ref "D15") (pin "P2") (pinfunction "IN1_P2") (pintype "input"))
      (node (ref "D21") (pin "U2") (pinfunction "IN4_U2") (pintype "input"))
      (node (ref "D23") (pin "M2") (pinfunction "IN3B_M2") (pintype "input"))
      (node (ref "D23") (pin "U2") (pinfunction "IN2B_U2") (pintype "input"))
      (node (ref "F40") (pin "H1") (pinfunction "P$2_H1") (pintype "bidirectional"))
    )
    (net (code "593") (name "MQ_ENABLE") (class "Default")
      (node (ref "D22") (pin "L1") (pinfunction "OUT_L1") (pintype "output"))
      (node (ref "EF34") (pin "BF1") (pinfunction "BF1_BF1") (pintype "input"))
      (node (ref "EF35") (pin "BF1") (pinfunction "BF1_BF1") (pintype "input"))
      (node (ref "EF36") (pin "BF1") (pinfunction "BF1_BF1") (pintype "input"))
      (node (ref "EF37") (pin "BF1") (pinfunction "BF1_BF1") (pintype "input"))
      (node (ref "EF38") (pin "BF1") (pinfunction "BF1_BF1") (pintype "input"))
      (node (ref "EF39") (pin "BF1") (pinfunction "BF1_BF1") (pintype "input"))
    )
    (net (code "594") (name "MQ_LOAD") (class "Default")
      (node (ref "C23") (pin "B1") (pinfunction "C_B1") (pintype "input"))
      (node (ref "C23") (pin "D2") (pinfunction "C_D2") (pintype "input"))
      (node (ref "C23") (pin "H1") (pinfunction "C_H1") (pintype "input"))
      (node (ref "C23") (pin "L2") (pinfunction "C_L2") (pintype "input"))
      (node (ref "C23") (pin "N1") (pinfunction "C_N1") (pintype "input"))
      (node (ref "C23") (pin "S2") (pinfunction "C_S2") (pintype "input"))
      (node (ref "C24") (pin "B1") (pinfunction "C_B1") (pintype "input"))
      (node (ref "C24") (pin "D2") (pinfunction "C_D2") (pintype "input"))
      (node (ref "C24") (pin "H1") (pinfunction "C_H1") (pintype "input"))
      (node (ref "C24") (pin "L2") (pinfunction "C_L2") (pintype "input"))
      (node (ref "C24") (pin "N1") (pinfunction "C_N1") (pintype "input"))
      (node (ref "C24") (pin "S2") (pinfunction "C_S2") (pintype "input"))
      (node (ref "D22") (pin "S1") (pinfunction "OUT_S1") (pintype "output"))
    )
    (net (code "595") (name "MQ_LOW_AC0") (class "Default")
      (node (ref "D15") (pin "F2") (pinfunction "OUT_F2") (pintype "output"))
      (node (ref "D19") (pin "L1") (pinfunction "IN2_L1") (pintype "input"))
      (node (ref "D20") (pin "A1") (pinfunction "IN1_A1") (pintype "input"))
    )
    (net (code "596") (name "MUY") (class "Default")
      (node (ref "D15") (pin "R2") (pinfunction "IN2_R2") (pintype "input"))
      (node (ref "D16") (pin "S1") (pinfunction "OUT_S1") (pintype "output"))
      (node (ref "D23") (pin "A1") (pinfunction "IN1A_A1") (pintype "input"))
    )
    (net (code "597") (name "MUY_") (class "Default")
      (node (ref "D16") (pin "P1") (pinfunction "IN1_P1") (pintype "input"))
      (node (ref "D19") (pin "U1") (pinfunction "OUT_U1") (pintype "output"))
    )
    (net (code "598") (name "MUY_DVI_") (class "Default")
      (node (ref "D15") (pin "K1") (pinfunction "OUT_K1") (pintype "output"))
      (node (ref "D21") (pin "D2") (pinfunction "IN1_D2") (pintype "input"))
    )
    (net (code "599") (name "NMI") (class "Default")
      (node (ref "D14") (pin "M2") (pinfunction "IN2_M2") (pintype "input"))
      (node (ref "D14") (pin "U2") (pinfunction "IN2_U2") (pintype "input"))
      (node (ref "D16") (pin "V2") (pinfunction "OUT_V2") (pintype "output"))
      (node (ref "D23") (pin "N1") (pinfunction "IN5B_N1") (pintype "input"))
    )
    (net (code "600") (name "NMI_") (class "Default")
      (node (ref "D16") (pin "T2") (pinfunction "IN1_T2") (pintype "input"))
      (node (ref "D20") (pin "V2") (pinfunction "OUT_V2") (pintype "output"))
    )
    (net (code "601") (name "NORM") (class "Default")
      (node (ref "C18") (pin "J2") (pinfunction "IN2_J2") (pintype "input"))
      (node (ref "D17") (pin "H2") (pinfunction "OUT_H2") (pintype "output"))
    )
    (net (code "602") (name "NORM_") (class "Default")
      (node (ref "C18") (pin "K2") (pinfunction "OUT_K2") (pintype "output"))
      (node (ref "D14") (pin "L2") (pinfunction "IN1_L2") (pintype "input"))
    )
    (net (code "603") (name "NO_SHIFT") (class "Default")
      (node (ref "E31") (pin "S1") (pinfunction "OUT_S1") (pintype "output"))
      (node (ref "EF34") (pin "AE1") (pinfunction "AE1_AE1") (pintype "input"))
      (node (ref "EF35") (pin "AE1") (pinfunction "AE1_AE1") (pintype "input"))
      (node (ref "EF36") (pin "AE1") (pinfunction "AE1_AE1") (pintype "input"))
      (node (ref "EF37") (pin "AE1") (pinfunction "AE1_AE1") (pintype "input"))
      (node (ref "EF38") (pin "AE1") (pinfunction "AE1_AE1") (pintype "input"))
      (node (ref "EF39") (pin "AE1") (pinfunction "AE1_AE1") (pintype "input"))
      (node (ref "F33") (pin "J1") (pinfunction "IN3B_J1") (pintype "input"))
    )
    (net (code "604") (name "Net-(A05A-OUT)") (class "Default")
      (node (ref "A05") (pin "C1") (pinfunction "OUT_C1") (pintype "output"))
      (node (ref "A05") (pin "E2") (pinfunction "IN2_E2") (pintype "input"))
    )
    (net (code "605") (name "Net-(A05B-IN2)") (class "Default")
      (node (ref "A05") (pin "E1") (pinfunction "IN2_E1") (pintype "input"))
      (node (ref "B04") (pin "H2") (pinfunction "OUT_H2") (pintype "output"))
    )
    (net (code "606") (name "Net-(A05B-OUT)") (class "Default")
      (node (ref "A05") (pin "D2") (pinfunction "IN1_D2") (pintype "input"))
      (node (ref "A05") (pin "F1") (pinfunction "OUT_F1") (pintype "output"))
    )
    (net (code "607") (name "Net-(A05C-OUT)") (class "Default")
      (node (ref "A05") (pin "F2") (pinfunction "OUT_F2") (pintype "output"))
      (node (ref "A05") (pin "H1") (pinfunction "IN1_H1") (pintype "input"))
    )
    (net (code "608") (name "Net-(A05F-OUT)") (class "Default")
      (node (ref "A05") (pin "K1") (pinfunction "OUT_K1") (pintype "output"))
      (node (ref "A05") (pin "L1") (pinfunction "IN1_L1") (pintype "input"))
    )
    (net (code "609") (name "Net-(A05H-OUT)") (class "Default")
      (node (ref "A05") (pin "N1") (pinfunction "OUT_N1") (pintype "output"))
      (node (ref "A05") (pin "R1") (pinfunction "IN2_R1") (pintype "input"))
      (node (ref "B04") (pin "P1") (pinfunction "IN1_P1") (pintype "input"))
      (node (ref "B04") (pin "R1") (pinfunction "IN2_R1") (pintype "input"))
    )
    (net (code "610") (name "Net-(A05I-OUT)") (class "Default")
      (node (ref "A05") (pin "N2") (pinfunction "OUT_N2") (pintype "output"))
      (node (ref "A05") (pin "P1") (pinfunction "IN1_P1") (pintype "input"))
    )
    (net (code "611") (name "Net-(A05J-OUT)") (class "Default")
      (node (ref "A05") (pin "S1") (pinfunction "OUT_S1") (pintype "output"))
      (node (ref "B05") (pin "M2") (pinfunction "D_M2") (pintype "input"))
    )
    (net (code "612") (name "Net-(A05K-IN1)") (class "Default")
      (node (ref "A05") (pin "P2") (pinfunction "IN1_P2") (pintype "input"))
      (node (ref "A05") (pin "R2") (pinfunction "IN2_R2") (pintype "input"))
      (node (ref "B04") (pin "U1") (pinfunction "OUT_U1") (pintype "output"))
    )
    (net (code "613") (name "Net-(A05N-IN2)") (class "Default")
      (node (ref "A05") (pin "U2") (pinfunction "IN2_U2") (pintype "input"))
      (node (ref "B04") (pin "J1") (pinfunction "OUT_J1") (pintype "output"))
    )
    (net (code "614") (name "Net-(A06C-OUT)") (class "Default")
      (node (ref "A06") (pin "F2") (pinfunction "OUT_F2") (pintype "output"))
      (node (ref "A06") (pin "H1") (pinfunction "IN1_H1") (pintype "input"))
    )
    (net (code "615") (name "Net-(A06F-OUT)") (class "Default")
      (node (ref "A06") (pin "K1") (pinfunction "OUT_K1") (pintype "output"))
      (node (ref "F30") (pin "N1") (pinfunction "IN2_N1") (pintype "input"))
    )
    (net (code "616") (name "Net-(A06H-IN1)") (class "Default")
      (node (ref "A06") (pin "L1") (pinfunction "IN1_L1") (pintype "input"))
      (node (ref "F09") (pin "J2") (pinfunction "OUT_J2") (pintype "output"))
    )
    (net (code "617") (name "Net-(A06I-IN1)") (class "Default")
      (node (ref "A06") (pin "L2") (pinfunction "IN1_L2") (pintype "input"))
      (node (ref "A15") (pin "V2") (pinfunction "OUT_V2") (pintype "output"))
    )
    (net (code "618") (name "Net-(A06J-OUT)") (class "Default")
      (node (ref "A06") (pin "P2") (pinfunction "IN1_P2") (pintype "input"))
      (node (ref "A06") (pin "S1") (pinfunction "OUT_S1") (pintype "output"))
    )
    (net (code "619") (name "Net-(A06K-OUT)") (class "Default")
      (node (ref "A06") (pin "S2") (pinfunction "OUT_S2") (pintype "output"))
      (node (ref "A06") (pin "T2") (pinfunction "IN1_T2") (pintype "input"))
    )
    (net (code "620") (name "Net-(A07C-1B)") (class "Default")
      (node (ref "A07") (pin "A1") (pinfunction "1B_A1") (pintype "input"))
      (node (ref "B08") (pin "K1") (pinfunction "OUT_K1") (pintype "output"))
    )
    (net (code "621") (name "Net-(A07C-2B)") (class "Default")
      (node (ref "A07") (pin "B1") (pinfunction "2B_B1") (pintype "input"))
      (node (ref "B08") (pin "F2") (pinfunction "OUT_F2") (pintype "output"))
    )
    (net (code "622") (name "Net-(A07C-4B)") (class "Default")
      (node (ref "A07") (pin "C1") (pinfunction "4B_C1") (pintype "input"))
      (node (ref "B08") (pin "F1") (pinfunction "OUT_F1") (pintype "output"))
    )
    (net (code "623") (name "Net-(A07C-8B)") (class "Default")
      (node (ref "A07") (pin "D1") (pinfunction "8B_D1") (pintype "input"))
      (node (ref "B08") (pin "C1") (pinfunction "OUT_C1") (pintype "output"))
    )
    (net (code "624") (name "Net-(A07C-EVEN)") (class "Default")
      (node (ref "A07") (pin "L1") (pinfunction "EVEN_L1") (pintype "output"))
      (node (ref "A08") (pin "A1") (pinfunction "1B_A1") (pintype "input"))
    )
    (net (code "625") (name "Net-(A07C-ODD)") (class "Default")
      (node (ref "A07") (pin "K1") (pinfunction "ODD_K1") (pintype "output"))
      (node (ref "A08") (pin "E1") (pinfunction "1A_E1") (pintype "input"))
    )
    (net (code "626") (name "Net-(A07D-1B)") (class "Default")
      (node (ref "A07") (pin "K2") (pinfunction "1B_K2") (pintype "input"))
      (node (ref "B09") (pin "F1") (pinfunction "OUT_F1") (pintype "output"))
    )
    (net (code "627") (name "Net-(A07D-2B)") (class "Default")
      (node (ref "A07") (pin "L2") (pinfunction "2B_L2") (pintype "input"))
      (node (ref "B09") (pin "C1") (pinfunction "OUT_C1") (pintype "output"))
    )
    (net (code "628") (name "Net-(A07D-4B)") (class "Default")
      (node (ref "A07") (pin "M2") (pinfunction "4B_M2") (pintype "input"))
      (node (ref "B08") (pin "V2") (pinfunction "OUT_V2") (pintype "output"))
    )
    (net (code "629") (name "Net-(A07D-8B)") (class "Default")
      (node (ref "A07") (pin "N2") (pinfunction "8B_N2") (pintype "input"))
      (node (ref "B08") (pin "S2") (pinfunction "OUT_S2") (pintype "output"))
    )
    (net (code "630") (name "Net-(A07D-EVEN)") (class "Default")
      (node (ref "A07") (pin "V2") (pinfunction "EVEN_V2") (pintype "output"))
      (node (ref "A08") (pin "C1") (pinfunction "4B_C1") (pintype "input"))
    )
    (net (code "631") (name "Net-(A07D-ODD)") (class "Default")
      (node (ref "A07") (pin "U2") (pinfunction "ODD_U2") (pintype "output"))
      (node (ref "A08") (pin "H1") (pinfunction "4A_H1") (pintype "input"))
    )
    (net (code "632") (name "Net-(A08C-2A)") (class "Default")
      (node (ref "A08") (pin "F1") (pinfunction "2A_F1") (pintype "input"))
      (node (ref "A08") (pin "U2") (pinfunction "ODD_U2") (pintype "output"))
    )
    (net (code "633") (name "Net-(A08C-2B)") (class "Default")
      (node (ref "A08") (pin "B1") (pinfunction "2B_B1") (pintype "input"))
      (node (ref "A08") (pin "V2") (pinfunction "EVEN_V2") (pintype "output"))
    )
    (net (code "634") (name "Net-(A08C-8B)") (class "Default")
      (node (ref "A08") (pin "D1") (pinfunction "8B_D1") (pintype "input"))
      (node (ref "B09") (pin "F2") (pinfunction "OUT_F2") (pintype "output"))
    )
    (net (code "635") (name "Net-(A08D-1B)") (class "Default")
      (node (ref "A08") (pin "K2") (pinfunction "1B_K2") (pintype "input"))
      (node (ref "B08") (pin "S1") (pinfunction "OUT_S1") (pintype "output"))
    )
    (net (code "636") (name "Net-(A08D-2B)") (class "Default")
      (node (ref "A08") (pin "L2") (pinfunction "2B_L2") (pintype "input"))
      (node (ref "B08") (pin "N2") (pinfunction "OUT_N2") (pintype "output"))
    )
    (net (code "637") (name "Net-(A08D-4B)") (class "Default")
      (node (ref "A08") (pin "M2") (pinfunction "4B_M2") (pintype "input"))
      (node (ref "B08") (pin "N1") (pinfunction "OUT_N1") (pintype "output"))
    )
    (net (code "638") (name "Net-(A08D-8B)") (class "Default")
      (node (ref "A08") (pin "N2") (pinfunction "8B_N2") (pintype "input"))
      (node (ref "B08") (pin "K2") (pinfunction "OUT_K2") (pintype "output"))
    )
    (net (code "639") (name "Net-(A09C-EVEN)") (class "Default")
      (node (ref "A09") (pin "L1") (pinfunction "EVEN_L1") (pintype "output"))
      (node (ref "A10") (pin "A1") (pinfunction "1B_A1") (pintype "input"))
    )
    (net (code "640") (name "Net-(A09C-ODD)") (class "Default")
      (node (ref "A09") (pin "K1") (pinfunction "ODD_K1") (pintype "output"))
      (node (ref "A10") (pin "E1") (pinfunction "1A_E1") (pintype "input"))
    )
    (net (code "641") (name "Net-(A09D-EVEN)") (class "Default")
      (node (ref "A09") (pin "V2") (pinfunction "EVEN_V2") (pintype "output"))
      (node (ref "A10") (pin "C1") (pinfunction "4B_C1") (pintype "input"))
    )
    (net (code "642") (name "Net-(A09D-ODD)") (class "Default")
      (node (ref "A09") (pin "U2") (pinfunction "ODD_U2") (pintype "output"))
      (node (ref "A10") (pin "H1") (pinfunction "4A_H1") (pintype "input"))
    )
    (net (code "643") (name "Net-(A10C-2A)") (class "Default")
      (node (ref "A10") (pin "F1") (pinfunction "2A_F1") (pintype "input"))
      (node (ref "A10") (pin "U2") (pinfunction "ODD_U2") (pintype "output"))
    )
    (net (code "644") (name "Net-(A10C-2B)") (class "Default")
      (node (ref "A10") (pin "B1") (pinfunction "2B_B1") (pintype "input"))
      (node (ref "A10") (pin "V2") (pinfunction "EVEN_V2") (pintype "output"))
    )
    (net (code "645") (name "Net-(A11A-OUT)") (class "Default")
      (node (ref "A11") (pin "C1") (pinfunction "OUT_C1") (pintype "output"))
      (node (ref "A13") (pin "J1") (pinfunction "IN2_J1") (pintype "input"))
    )
    (net (code "646") (name "Net-(A11B-IN1)") (class "Default")
      (node (ref "A11") (pin "D1") (pinfunction "IN1_D1") (pintype "input"))
      (node (ref "A11") (pin "H2") (pinfunction "IN1_H2") (pintype "input"))
      (node (ref "A11") (pin "P1") (pinfunction "IN1_P1") (pintype "input"))
      (node (ref "A14") (pin "N1") (pinfunction "OUT_N1") (pintype "output"))
    )
    (net (code "647") (name "Net-(A11B-OUT)") (class "Default")
      (node (ref "A11") (pin "F1") (pinfunction "OUT_F1") (pintype "output"))
      (node (ref "A20") (pin "D2") (pinfunction "IN1_D2") (pintype "input"))
    )
    (net (code "648") (name "Net-(A11C-OUT)") (class "Default")
      (node (ref "A11") (pin "F2") (pinfunction "OUT_F2") (pintype "output"))
      (node (ref "A20") (pin "E2") (pinfunction "IN2_E2") (pintype "input"))
    )
    (net (code "649") (name "Net-(A11F-IN1)") (class "Default")
      (node (ref "A11") (pin "H1") (pinfunction "IN1_H1") (pintype "input"))
      (node (ref "A11") (pin "L2") (pinfunction "IN1_L2") (pintype "input"))
      (node (ref "A11") (pin "T2") (pinfunction "IN1_T2") (pintype "input"))
      (node (ref "A14") (pin "S1") (pinfunction "OUT_S1") (pintype "output"))
    )
    (net (code "650") (name "Net-(A11F-OUT)") (class "Default")
      (node (ref "A11") (pin "K1") (pinfunction "OUT_K1") (pintype "output"))
      (node (ref "A20") (pin "F2") (pinfunction "IN3_F2") (pintype "input"))
    )
    (net (code "651") (name "Net-(A11G-OUT)") (class "Default")
      (node (ref "A11") (pin "K2") (pinfunction "OUT_K2") (pintype "output"))
      (node (ref "A20") (pin "E1") (pinfunction "IN1_E1") (pintype "input"))
    )
    (net (code "652") (name "Net-(A11H-OUT)") (class "Default")
      (node (ref "A11") (pin "N1") (pinfunction "OUT_N1") (pintype "output"))
      (node (ref "A20") (pin "F1") (pinfunction "IN2_F1") (pintype "input"))
    )
    (net (code "653") (name "Net-(A11I-OUT)") (class "Default")
      (node (ref "A11") (pin "N2") (pinfunction "OUT_N2") (pintype "output"))
      (node (ref "A20") (pin "H1") (pinfunction "IN3_H1") (pintype "input"))
    )
    (net (code "654") (name "Net-(A11J-OUT)") (class "Default")
      (node (ref "A11") (pin "S1") (pinfunction "OUT_S1") (pintype "output"))
      (node (ref "A20") (pin "J2") (pinfunction "IN1_J2") (pintype "input"))
    )
    (net (code "655") (name "Net-(A11K-OUT)") (class "Default")
      (node (ref "A11") (pin "S2") (pinfunction "OUT_S2") (pintype "output"))
      (node (ref "A20") (pin "K2") (pinfunction "IN2_K2") (pintype "input"))
    )
    (net (code "656") (name "Net-(A11N-OUT)") (class "Default")
      (node (ref "A11") (pin "V2") (pinfunction "OUT_V2") (pintype "output"))
      (node (ref "A20") (pin "L2") (pinfunction "IN3_L2") (pintype "input"))
    )
    (net (code "657") (name "Net-(A12A-OUT)") (class "Default")
      (node (ref "A12") (pin "C1") (pinfunction "OUT_C1") (pintype "output"))
      (node (ref "F11") (pin "D2") (pinfunction "IN1_D2") (pintype "input"))
      (node (ref "F11") (pin "E2") (pinfunction "IN2_E2") (pintype "input"))
    )
    (net (code "658") (name "Net-(A12B-OUT)") (class "Default")
      (node (ref "A12") (pin "F1") (pinfunction "OUT_F1") (pintype "output"))
      (node (ref "B20") (pin "N2") (pinfunction "IN1_N2") (pintype "input"))
    )
    (net (code "659") (name "Net-(A12C-IN1)") (class "Default")
      (node (ref "A12") (pin "D2") (pinfunction "IN1_D2") (pintype "input"))
      (node (ref "A12") (pin "L1") (pinfunction "IN1_L1") (pintype "input"))
      (node (ref "A12") (pin "P2") (pinfunction "IN1_P2") (pintype "input"))
      (node (ref "A13") (pin "K1") (pinfunction "OUT_K1") (pintype "output"))
    )
    (net (code "660") (name "Net-(A12C-OUT)") (class "Default")
      (node (ref "A12") (pin "F2") (pinfunction "OUT_F2") (pintype "output"))
      (node (ref "B20") (pin "P2") (pinfunction "IN2_P2") (pintype "input"))
    )
    (net (code "661") (name "Net-(A12F-OUT)") (class "Default")
      (node (ref "A12") (pin "K1") (pinfunction "OUT_K1") (pintype "output"))
      (node (ref "B20") (pin "R2") (pinfunction "IN3_R2") (pintype "input"))
    )
    (net (code "662") (name "Net-(A12G-OUT)") (class "Default")
      (node (ref "A12") (pin "K2") (pinfunction "OUT_K2") (pintype "output"))
      (node (ref "B20") (pin "P1") (pinfunction "IN1_P1") (pintype "input"))
    )
    (net (code "663") (name "Net-(A12H-OUT)") (class "Default")
      (node (ref "A12") (pin "N1") (pinfunction "OUT_N1") (pintype "output"))
      (node (ref "B20") (pin "R1") (pinfunction "IN2_R1") (pintype "input"))
    )
    (net (code "664") (name "Net-(A12I-OUT)") (class "Default")
      (node (ref "A12") (pin "N2") (pinfunction "OUT_N2") (pintype "output"))
      (node (ref "B20") (pin "S1") (pinfunction "IN3_S1") (pintype "input"))
    )
    (net (code "665") (name "Net-(A12J-OUT)") (class "Default")
      (node (ref "A12") (pin "S1") (pinfunction "OUT_S1") (pintype "output"))
      (node (ref "B20") (pin "T2") (pinfunction "IN1_T2") (pintype "input"))
    )
    (net (code "666") (name "Net-(A12K-OUT)") (class "Default")
      (node (ref "A12") (pin "S2") (pinfunction "OUT_S2") (pintype "output"))
      (node (ref "B20") (pin "U2") (pinfunction "IN2_U2") (pintype "input"))
    )
    (net (code "667") (name "Net-(A12N-OUT)") (class "Default")
      (node (ref "A12") (pin "V2") (pinfunction "OUT_V2") (pintype "output"))
      (node (ref "B20") (pin "V2") (pinfunction "IN3_V2") (pintype "input"))
    )
    (net (code "668") (name "Net-(A13A-OUT)") (class "Default")
      (node (ref "A13") (pin "C1") (pinfunction "OUT_C1") (pintype "output"))
      (node (ref "A17") (pin "T2") (pinfunction "IN1_T2") (pintype "input"))
    )
    (net (code "669") (name "Net-(A13B-IN1)") (class "Default")
      (node (ref "A13") (pin "D1") (pinfunction "IN1_D1") (pintype "input"))
      (node (ref "A13") (pin "F2") (pinfunction "OUT_F2") (pintype "output"))
    )
    (net (code "670") (name "Net-(A13H-IN1)") (class "Default")
      (node (ref "A13") (pin "L1") (pinfunction "IN1_L1") (pintype "input"))
      (node (ref "A20") (pin "H2") (pinfunction "OUT_H2") (pintype "output"))
    )
    (net (code "671") (name "Net-(A13J-IN1)") (class "Default")
      (node (ref "A13") (pin "P1") (pinfunction "IN1_P1") (pintype "input"))
      (node (ref "A20") (pin "J1") (pinfunction "OUT_J1") (pintype "output"))
    )
    (net (code "672") (name "Net-(A13N-IN1)") (class "Default")
      (node (ref "A13") (pin "T2") (pinfunction "IN1_T2") (pintype "input"))
      (node (ref "A20") (pin "M2") (pinfunction "OUT_M2") (pintype "output"))
    )
    (net (code "673") (name "Net-(A14A-IN1)") (class "Default")
      (node (ref "A14") (pin "A1") (pinfunction "IN1_A1") (pintype "input"))
      (node (ref "B16") (pin "P2") (pinfunction "OUT_P2") (pintype "output"))
    )
    (net (code "674") (name "Net-(A14A-OUT)") (class "Default")
      (node (ref "A14") (pin "C1") (pinfunction "OUT_C1") (pintype "output"))
      (node (ref "A14") (pin "D1") (pinfunction "IN1_D1") (pintype "input"))
    )
    (net (code "675") (name "Net-(A14C-OUT)") (class "Default")
      (node (ref "A14") (pin "F2") (pinfunction "OUT_F2") (pintype "output"))
      (node (ref "A14") (pin "J2") (pinfunction "IN2_J2") (pintype "input"))
    )
    (net (code "676") (name "Net-(A14H-IN2)") (class "Default")
      (node (ref "A14") (pin "M1") (pinfunction "IN2_M1") (pintype "input"))
      (node (ref "A20") (pin "N1") (pinfunction "OUT_N1") (pintype "output"))
      (node (ref "A20") (pin "T2") (pinfunction "IN1_T2") (pintype "input"))
    )
    (net (code "677") (name "Net-(A14I-IN2)") (class "Default")
      (node (ref "A14") (pin "M2") (pinfunction "IN2_M2") (pintype "input"))
      (node (ref "A20") (pin "S2") (pinfunction "OUT_S2") (pintype "output"))
      (node (ref "A20") (pin "U2") (pinfunction "IN2_U2") (pintype "input"))
    )
    (net (code "678") (name "Net-(A14J-IN2)") (class "Default")
      (node (ref "A14") (pin "R1") (pinfunction "IN2_R1") (pintype "input"))
      (node (ref "A20") (pin "U1") (pinfunction "OUT_U1") (pintype "output"))
      (node (ref "A20") (pin "V2") (pinfunction "IN3_V2") (pintype "input"))
    )
    (net (code "679") (name "Net-(A14K-IN2)") (class "Default")
      (node (ref "A14") (pin "R2") (pinfunction "IN2_R2") (pintype "input"))
      (node (ref "A20") (pin "V1") (pinfunction "OUT_V1") (pintype "output"))
      (node (ref "C12") (pin "D2") (pinfunction "IN1_D2") (pintype "input"))
    )
    (net (code "680") (name "Net-(A15A-OUT)") (class "Default")
      (node (ref "A15") (pin "C1") (pinfunction "OUT_C1") (pintype "output"))
      (node (ref "B11") (pin "R1") (pinfunction "S_R1") (pintype "input"))
    )
    (net (code "681") (name "Net-(A15F-IN2)") (class "Default")
      (node (ref "A15") (pin "J1") (pinfunction "IN2_J1") (pintype "input"))
      (node (ref "A19") (pin "V2") (pinfunction "OUT_V2") (pintype "output"))
    )
    (net (code "682") (name "Net-(A15G-IN2)") (class "Default")
      (node (ref "A15") (pin "J2") (pinfunction "IN2_J2") (pintype "input"))
      (node (ref "A15") (pin "N1") (pinfunction "OUT_N1") (pintype "output"))
    )
    (net (code "683") (name "Net-(A15G-OUT)") (class "Default")
      (node (ref "A15") (pin "K2") (pinfunction "OUT_K2") (pintype "output"))
      (node (ref "A18") (pin "B1") (pinfunction "IN2_B1") (pintype "input"))
    )
    (net (code "684") (name "Net-(A15J-IN2)") (class "Default")
      (node (ref "A15") (pin "R1") (pinfunction "IN2_R1") (pintype "input"))
      (node (ref "A15") (pin "S2") (pinfunction "OUT_S2") (pintype "output"))
    )
    (net (code "685") (name "Net-(A16A-OUT)") (class "Default")
      (node (ref "A16") (pin "C1") (pinfunction "OUT_C1") (pintype "output"))
      (node (ref "B16") (pin "A1") (pinfunction "IN1_A1") (pintype "input"))
    )
    (net (code "686") (name "Net-(A16B-OUT)") (class "Default")
      (node (ref "A16") (pin "F1") (pinfunction "OUT_F1") (pintype "output"))
      (node (ref "B16") (pin "B1") (pinfunction "IN2_B1") (pintype "input"))
    )
    (net (code "687") (name "Net-(A16C-OUT)") (class "Default")
      (node (ref "A16") (pin "F2") (pinfunction "OUT_F2") (pintype "output"))
      (node (ref "B16") (pin "C1") (pinfunction "IN3_C1") (pintype "input"))
    )
    (net (code "688") (name "Net-(A16F-OUT)") (class "Default")
      (node (ref "A16") (pin "K1") (pinfunction "OUT_K1") (pintype "output"))
      (node (ref "B16") (pin "D2") (pinfunction "IN1_D2") (pintype "input"))
    )
    (net (code "689") (name "Net-(A16G-OUT)") (class "Default")
      (node (ref "A16") (pin "K2") (pinfunction "OUT_K2") (pintype "output"))
      (node (ref "B16") (pin "E2") (pinfunction "IN2_E2") (pintype "input"))
    )
    (net (code "690") (name "Net-(A16H-OUT)") (class "Default")
      (node (ref "A16") (pin "N1") (pinfunction "OUT_N1") (pintype "output"))
      (node (ref "B16") (pin "F2") (pinfunction "IN3_F2") (pintype "input"))
    )
    (net (code "691") (name "Net-(A16I-OUT)") (class "Default")
      (node (ref "A16") (pin "N2") (pinfunction "OUT_N2") (pintype "output"))
      (node (ref "B16") (pin "F1") (pinfunction "IN1_F1") (pintype "input"))
    )
    (net (code "692") (name "Net-(A16J-OUT)") (class "Default")
      (node (ref "A16") (pin "S1") (pinfunction "OUT_S1") (pintype "output"))
      (node (ref "B16") (pin "H1") (pinfunction "IN2_H1") (pintype "input"))
    )
    (net (code "693") (name "Net-(A16K-OUT)") (class "Default")
      (node (ref "A16") (pin "S2") (pinfunction "OUT_S2") (pintype "output"))
      (node (ref "B16") (pin "J1") (pinfunction "IN3_J1") (pintype "input"))
    )
    (net (code "694") (name "Net-(A16N-OUT)") (class "Default")
      (node (ref "A16") (pin "V2") (pinfunction "OUT_V2") (pintype "output"))
      (node (ref "A20") (pin "A1") (pinfunction "IN1_A1") (pintype "input"))
    )
    (net (code "695") (name "Net-(A17A-IN2)") (class "Default")
      (node (ref "A17") (pin "B1") (pinfunction "IN2_B1") (pintype "input"))
      (node (ref "A20") (pin "D1") (pinfunction "OUT_D1") (pintype "output"))
    )
    (net (code "696") (name "Net-(A17B-OUT)") (class "Default")
      (node (ref "A17") (pin "F1") (pinfunction "OUT_F1") (pintype "output"))
      (node (ref "A20") (pin "C1") (pinfunction "IN3_C1") (pintype "input"))
    )
    (net (code "697") (name "Net-(A17C-IN1)") (class "Default")
      (node (ref "A17") (pin "D2") (pinfunction "IN1_D2") (pintype "input"))
      (node (ref "A18") (pin "F1") (pinfunction "OUT_F1") (pintype "output"))
      (node (ref "B20") (pin "E1") (pinfunction "IN1_E1") (pintype "input"))
    )
    (net (code "698") (name "Net-(A17C-IN2)") (class "Default")
      (node (ref "A17") (pin "E2") (pinfunction "IN2_E2") (pintype "input"))
      (node (ref "A17") (pin "K1") (pinfunction "OUT_K1") (pintype "output"))
    )
    (net (code "699") (name "Net-(A17C-OUT)") (class "Default")
      (node (ref "A17") (pin "F2") (pinfunction "OUT_F2") (pintype "output"))
      (node (ref "B17") (pin "C1") (pinfunction "D_C1") (pintype "input"))
    )
    (net (code "700") (name "Net-(A17G-IN1)") (class "Default")
      (node (ref "A17") (pin "H2") (pinfunction "IN1_H2") (pintype "input"))
      (node (ref "A18") (pin "K2") (pinfunction "OUT_K2") (pintype "output"))
      (node (ref "B20") (pin "J2") (pinfunction "IN1_J2") (pintype "input"))
    )
    (net (code "701") (name "Net-(A17G-IN2)") (class "Default")
      (node (ref "A17") (pin "J2") (pinfunction "IN2_J2") (pintype "input"))
      (node (ref "A17") (pin "N1") (pinfunction "OUT_N1") (pintype "output"))
    )
    (net (code "702") (name "Net-(A17G-OUT)") (class "Default")
      (node (ref "A17") (pin "K2") (pinfunction "OUT_K2") (pintype "output"))
      (node (ref "B17") (pin "E2") (pinfunction "D_E2") (pintype "input"))
    )
    (net (code "703") (name "Net-(A17I-IN1)") (class "Default")
      (node (ref "A17") (pin "L2") (pinfunction "IN1_L2") (pintype "input"))
      (node (ref "A18") (pin "S1") (pinfunction "OUT_S1") (pintype "output"))
      (node (ref "B20") (pin "K1") (pinfunction "IN1_K1") (pintype "input"))
    )
    (net (code "704") (name "Net-(A17I-IN2)") (class "Default")
      (node (ref "A17") (pin "M2") (pinfunction "IN2_M2") (pintype "input"))
      (node (ref "A17") (pin "S1") (pinfunction "OUT_S1") (pintype "output"))
    )
    (net (code "705") (name "Net-(A17I-OUT)") (class "Default")
      (node (ref "A17") (pin "N2") (pinfunction "OUT_N2") (pintype "output"))
      (node (ref "B17") (pin "J1") (pinfunction "D_J1") (pintype "input"))
    )
    (net (code "706") (name "Net-(A17K-IN1)") (class "Default")
      (node (ref "A17") (pin "P2") (pinfunction "IN1_P2") (pintype "input"))
      (node (ref "A17") (pin "V2") (pinfunction "OUT_V2") (pintype "output"))
    )
    (net (code "707") (name "Net-(A17K-OUT)") (class "Default")
      (node (ref "A17") (pin "S2") (pinfunction "OUT_S2") (pintype "output"))
      (node (ref "B18") (pin "B1") (pinfunction "C_B1") (pintype "input"))
      (node (ref "B18") (pin "D2") (pinfunction "C_D2") (pintype "input"))
      (node (ref "B18") (pin "H1") (pinfunction "C_H1") (pintype "input"))
    )
    (net (code "708") (name "Net-(A18C-OUT)") (class "Default")
      (node (ref "A18") (pin "F2") (pinfunction "OUT_F2") (pintype "output"))
      (node (ref "B20") (pin "F1") (pinfunction "IN2_F1") (pintype "input"))
    )
    (net (code "709") (name "Net-(A18F-OUT)") (class "Default")
      (node (ref "A18") (pin "K1") (pinfunction "OUT_K1") (pintype "output"))
      (node (ref "B20") (pin "H1") (pinfunction "IN3_H1") (pintype "input"))
    )
    (net (code "710") (name "Net-(A18H-OUT)") (class "Default")
      (node (ref "A18") (pin "N1") (pinfunction "OUT_N1") (pintype "output"))
      (node (ref "B20") (pin "K2") (pinfunction "IN2_K2") (pintype "input"))
    )
    (net (code "711") (name "Net-(A18I-OUT)") (class "Default")
      (node (ref "A18") (pin "N2") (pinfunction "OUT_N2") (pintype "output"))
      (node (ref "B20") (pin "L2") (pinfunction "IN3_L2") (pintype "input"))
    )
    (net (code "712") (name "Net-(A18K-OUT)") (class "Default")
      (node (ref "A18") (pin "S2") (pinfunction "OUT_S2") (pintype "output"))
      (node (ref "B20") (pin "L1") (pinfunction "IN2_L1") (pintype "input"))
    )
    (net (code "713") (name "Net-(A18N-OUT)") (class "Default")
      (node (ref "A18") (pin "V2") (pinfunction "OUT_V2") (pintype "output"))
      (node (ref "B20") (pin "M1") (pinfunction "IN3_M1") (pintype "input"))
    )
    (net (code "714") (name "Net-(A19A-OUT)") (class "Default")
      (node (ref "A19") (pin "C1") (pinfunction "OUT_C1") (pintype "output"))
      (node (ref "A19") (pin "E1") (pinfunction "IN2_E1") (pintype "input"))
    )
    (net (code "715") (name "Net-(A19B-OUT)") (class "Default")
      (node (ref "A19") (pin "F1") (pinfunction "OUT_F1") (pintype "output"))
      (node (ref "B20") (pin "E2") (pinfunction "IN2_E2") (pintype "input"))
    )
    (net (code "716") (name "Net-(A19F-IN1)") (class "Default")
      (node (ref "A19") (pin "H1") (pinfunction "IN1_H1") (pintype "input"))
      (node (ref "A19") (pin "K2") (pinfunction "OUT_K2") (pintype "output"))
    )
    (net (code "717") (name "Net-(A19F-OUT)") (class "Default")
      (node (ref "A19") (pin "K1") (pinfunction "OUT_K1") (pintype "output"))
      (node (ref "B11") (pin "B1") (pinfunction "C_B1") (pintype "input"))
      (node (ref "B11") (pin "D2") (pinfunction "C_D2") (pintype "input"))
      (node (ref "B11") (pin "H1") (pinfunction "C_H1") (pintype "input"))
    )
    (net (code "718") (name "Net-(A19H-OUT)") (class "Default")
      (node (ref "A19") (pin "M2") (pinfunction "IN2_M2") (pintype "input"))
      (node (ref "A19") (pin "N1") (pinfunction "OUT_N1") (pintype "output"))
    )
    (net (code "719") (name "Net-(A19J-IN1)") (class "Default")
      (node (ref "A19") (pin "P1") (pinfunction "IN1_P1") (pintype "input"))
      (node (ref "A19") (pin "P2") (pinfunction "IN1_P2") (pintype "input"))
      (node (ref "E12") (pin "N2") (pinfunction "OUT_N2") (pintype "output"))
    )
    (net (code "720") (name "Net-(A19K-OUT)") (class "Default")
      (node (ref "A19") (pin "S2") (pinfunction "OUT_S2") (pintype "output"))
      (node (ref "B19") (pin "H1") (pinfunction "C_H1") (pintype "input"))
      (node (ref "B19") (pin "L2") (pinfunction "C_L2") (pintype "input"))
      (node (ref "B19") (pin "N1") (pinfunction "C_N1") (pintype "input"))
      (node (ref "B19") (pin "S2") (pinfunction "C_S2") (pintype "input"))
    )
    (net (code "721") (name "Net-(B04F-OUT)") (class "Default")
      (node (ref "B04") (pin "M2") (pinfunction "OUT_M2") (pintype "output"))
      (node (ref "B05") (pin "U2") (pinfunction "S_U2") (pintype "input"))
    )
    (net (code "722") (name "Net-(B04G-OUT)") (class "Default")
      (node (ref "B04") (pin "N1") (pinfunction "OUT_N1") (pintype "output"))
      (node (ref "B05") (pin "S2") (pinfunction "C_S2") (pintype "input"))
    )
    (net (code "723") (name "Net-(B04I-IN3)") (class "Default")
      (node (ref "B04") (pin "S1") (pinfunction "IN3_S1") (pintype "input"))
      (node (ref "B05") (pin "R2") (pinfunction "0_R2") (pintype "output"))
    )
    (net (code "724") (name "Net-(B05A-C)") (class "Default")
      (node (ref "B05") (pin "B1") (pinfunction "C_B1") (pintype "input"))
      (node (ref "B06") (pin "K1") (pinfunction "OUT_K1") (pintype "output"))
    )
    (net (code "725") (name "Net-(B05A-D)") (class "Default")
      (node (ref "B05") (pin "C1") (pinfunction "D_C1") (pintype "input"))
      (node (ref "B06") (pin "N2") (pinfunction "OUT_N2") (pintype "output"))
    )
    (net (code "726") (name "Net-(B05D-D)") (class "Default")
      (node (ref "B05") (pin "E2") (pinfunction "D_E2") (pintype "input"))
      (node (ref "B06") (pin "V2") (pinfunction "OUT_V2") (pintype "output"))
    )
    (net (code "727") (name "Net-(B06B-OUT)") (class "Default")
      (node (ref "B06") (pin "E2") (pinfunction "IN2_E2") (pintype "input"))
      (node (ref "B06") (pin "F1") (pinfunction "OUT_F1") (pintype "output"))
    )
    (net (code "728") (name "Net-(B06C-OUT)") (class "Default")
      (node (ref "B06") (pin "F2") (pinfunction "OUT_F2") (pintype "output"))
      (node (ref "B06") (pin "J1") (pinfunction "IN2_J1") (pintype "input"))
    )
    (net (code "729") (name "Net-(B06H-OUT)") (class "Default")
      (node (ref "B06") (pin "L2") (pinfunction "IN1_L2") (pintype "input"))
      (node (ref "B06") (pin "N1") (pinfunction "OUT_N1") (pintype "output"))
    )
    (net (code "730") (name "Net-(B06I-IN2)") (class "Default")
      (node (ref "B06") (pin "M2") (pinfunction "IN2_M2") (pintype "input"))
      (node (ref "B06") (pin "S1") (pinfunction "OUT_S1") (pintype "output"))
    )
    (net (code "731") (name "Net-(B06K-OUT)") (class "Default")
      (node (ref "B06") (pin "S2") (pinfunction "OUT_S2") (pintype "output"))
      (node (ref "B06") (pin "T2") (pinfunction "IN1_T2") (pintype "input"))
    )
    (net (code "732") (name "Net-(B07A-OUT)") (class "Default")
      (node (ref "B07") (pin "D1") (pinfunction "OUT_D1") (pintype "output"))
      (node (ref "B09") (pin "H1") (pinfunction "IN1_H1") (pintype "input"))
    )
    (net (code "733") (name "Net-(B07D-OUT)") (class "Default")
      (node (ref "B07") (pin "H2") (pinfunction "OUT_H2") (pintype "output"))
      (node (ref "B09") (pin "J2") (pinfunction "IN2_J2") (pintype "input"))
    )
    (net (code "734") (name "Net-(B07E-IN3)") (class "Default")
      (node (ref "B07") (pin "H1") (pinfunction "IN3_H1") (pintype "input"))
      (node (ref "B07") (pin "J2") (pinfunction "IN1_J2") (pintype "input"))
      (node (ref "B09") (pin "N2") (pinfunction "OUT_N2") (pintype "output"))
    )
    (net (code "735") (name "Net-(B07E-OUT)") (class "Default")
      (node (ref "B07") (pin "J1") (pinfunction "OUT_J1") (pintype "output"))
      (node (ref "B07") (pin "M1") (pinfunction "IN3_M1") (pintype "input"))
    )
    (net (code "736") (name "Net-(B07G-OUT)") (class "Default")
      (node (ref "B07") (pin "N1") (pinfunction "OUT_N1") (pintype "output"))
      (node (ref "B07") (pin "N2") (pinfunction "IN1_N2") (pintype "input"))
    )
    (net (code "737") (name "Net-(B09F-OUT)") (class "Default")
      (node (ref "B09") (pin "K1") (pinfunction "OUT_K1") (pintype "output"))
      (node (ref "B09") (pin "L1") (pinfunction "IN1_L1") (pintype "input"))
    )
    (net (code "738") (name "Net-(B09G-OUT)") (class "Default")
      (node (ref "B09") (pin "K2") (pinfunction "OUT_K2") (pintype "output"))
      (node (ref "B09") (pin "M1") (pinfunction "IN2_M1") (pintype "input"))
    )
    (net (code "739") (name "Net-(B09H-OUT)") (class "Default")
      (node (ref "B09") (pin "L2") (pinfunction "IN1_L2") (pintype "input"))
      (node (ref "B09") (pin "N1") (pinfunction "OUT_N1") (pintype "output"))
    )
    (net (code "740") (name "Net-(B09J-OUT)") (class "Default")
      (node (ref "B09") (pin "S1") (pinfunction "OUT_S1") (pintype "output"))
      (node (ref "B11") (pin "M2") (pinfunction "D_M2") (pintype "input"))
    )
    (net (code "741") (name "Net-(B11G-C)") (class "Default")
      (node (ref "B11") (pin "N1") (pinfunction "C_N1") (pintype "input"))
      (node (ref "F11") (pin "J2") (pinfunction "OUT_J2") (pintype "output"))
    )
    (net (code "742") (name "Net-(B17F-D)") (class "Default")
      (node (ref "B17") (pin "M2") (pinfunction "D_M2") (pintype "input"))
      (node (ref "B20") (pin "J1") (pinfunction "OUT_J1") (pintype "output"))
    )
    (net (code "743") (name "Net-(B17G-D)") (class "Default")
      (node (ref "B17") (pin "P1") (pinfunction "D_P1") (pintype "input"))
      (node (ref "B20") (pin "M2") (pinfunction "OUT_M2") (pintype "output"))
    )
    (net (code "744") (name "Net-(B17H-D)") (class "Default")
      (node (ref "B17") (pin "T2") (pinfunction "D_T2") (pintype "input"))
      (node (ref "B20") (pin "N1") (pinfunction "OUT_N1") (pintype "output"))
    )
    (net (code "745") (name "Net-(B18A-D)") (class "Default")
      (node (ref "B18") (pin "C1") (pinfunction "D_C1") (pintype "input"))
      (node (ref "B20") (pin "S2") (pinfunction "OUT_S2") (pintype "output"))
    )
    (net (code "746") (name "Net-(B18D-D)") (class "Default")
      (node (ref "B18") (pin "E2") (pinfunction "D_E2") (pintype "input"))
      (node (ref "B20") (pin "U1") (pinfunction "OUT_U1") (pintype "output"))
    )
    (net (code "747") (name "Net-(B18E-D)") (class "Default")
      (node (ref "B18") (pin "J1") (pinfunction "D_J1") (pintype "input"))
      (node (ref "B20") (pin "V1") (pinfunction "OUT_V1") (pintype "output"))
    )
    (net (code "748") (name "Net-(B21N-OUT)") (class "Default")
      (node (ref "B21") (pin "V2") (pinfunction "OUT_V2") (pintype "output"))
      (node (ref "C12") (pin "M1") (pinfunction "IN1_M1") (pintype "input"))
      (node (ref "C12") (pin "N1") (pinfunction "IN2_N1") (pintype "input"))
      (node (ref "C12") (pin "P1") (pinfunction "IN3_P1") (pintype "input"))
      (node (ref "C12") (pin "R1") (pinfunction "IN4_R1") (pintype "input"))
    )
    (net (code "749") (name "Net-(C01D-P$2)") (class "Default")
      (node (ref "C01") (pin "D2") (pinfunction "P$2_D2") (pintype "bidirectional"))
      (node (ref "C02") (pin "V2") (pinfunction "P$1_V2") (pintype "input"))
      (node (ref "C03") (pin "V2") (pinfunction "P$1_V2") (pintype "input"))
      (node (ref "C04") (pin "V2") (pinfunction "P$1_V2") (pintype "input"))
      (node (ref "C05") (pin "V2") (pinfunction "P$1_V2") (pintype "input"))
      (node (ref "C06") (pin "V2") (pinfunction "P$1_V2") (pintype "input"))
    )
    (net (code "750") (name "Net-(C02A-D)") (class "Default")
      (node (ref "C02") (pin "D2") (pinfunction "D_D2") (pintype "input"))
      (node (ref "C02") (pin "J2") (pinfunction "D_J2") (pintype "input"))
      (node (ref "C03") (pin "D2") (pinfunction "D_D2") (pintype "input"))
      (node (ref "C03") (pin "J2") (pinfunction "D_J2") (pintype "input"))
      (node (ref "C04") (pin "D2") (pinfunction "D_D2") (pintype "input"))
      (node (ref "C04") (pin "J2") (pinfunction "D_J2") (pintype "input"))
      (node (ref "C04") (pin "K2") (pinfunction "E_K2") (pintype "input"))
      (node (ref "C04") (pin "L2") (pinfunction "F_L2") (pintype "input"))
      (node (ref "C04") (pin "M2") (pinfunction "H_M2") (pintype "input"))
      (node (ref "C05") (pin "D2") (pinfunction "D_D2") (pintype "input"))
      (node (ref "C05") (pin "J2") (pinfunction "D_J2") (pintype "input"))
      (node (ref "C06") (pin "D2") (pinfunction "D_D2") (pintype "input"))
      (node (ref "HJ28") (pin "BH2") (pinfunction "BH2_BH2") (pintype "output"))
    )
    (net (code "751") (name "Net-(C02A-E)") (class "Default")
      (node (ref "C02") (pin "E2") (pinfunction "E_E2") (pintype "input"))
      (node (ref "C02") (pin "F2") (pinfunction "F_F2") (pintype "input"))
      (node (ref "C02") (pin "H2") (pinfunction "H_H2") (pintype "input"))
      (node (ref "HJ28") (pin "AK1") (pinfunction "AK1_AK1") (pintype "output"))
    )
    (net (code "752") (name "Net-(C02B-E)") (class "Default")
      (node (ref "C02") (pin "K2") (pinfunction "E_K2") (pintype "input"))
      (node (ref "C02") (pin "L2") (pinfunction "F_L2") (pintype "input"))
      (node (ref "C02") (pin "M2") (pinfunction "H_M2") (pintype "input"))
      (node (ref "HJ28") (pin "AL1") (pinfunction "AL1_AL1") (pintype "output"))
    )
    (net (code "753") (name "Net-(C03A-E)") (class "Default")
      (node (ref "C03") (pin "E2") (pinfunction "E_E2") (pintype "input"))
      (node (ref "C03") (pin "F2") (pinfunction "F_F2") (pintype "input"))
      (node (ref "C03") (pin "H2") (pinfunction "H_H2") (pintype "input"))
      (node (ref "HJ28") (pin "AM1") (pinfunction "AM1_AM1") (pintype "output"))
    )
    (net (code "754") (name "Net-(C03B-E)") (class "Default")
      (node (ref "C03") (pin "K2") (pinfunction "E_K2") (pintype "input"))
      (node (ref "C03") (pin "L2") (pinfunction "F_L2") (pintype "input"))
      (node (ref "C03") (pin "M2") (pinfunction "H_M2") (pintype "input"))
      (node (ref "HJ28") (pin "AN1") (pinfunction "AN1_AN1") (pintype "output"))
    )
    (net (code "755") (name "Net-(C04A-E)") (class "Default")
      (node (ref "C04") (pin "E2") (pinfunction "E_E2") (pintype "input"))
      (node (ref "C04") (pin "F2") (pinfunction "F_F2") (pintype "input"))
      (node (ref "C04") (pin "H2") (pinfunction "H_H2") (pintype "input"))
      (node (ref "HJ28") (pin "AK2") (pinfunction "AK2_AK2") (pintype "output"))
    )
    (net (code "756") (name "Net-(C05A-E)") (class "Default")
      (node (ref "C05") (pin "E2") (pinfunction "E_E2") (pintype "input"))
      (node (ref "C05") (pin "F2") (pinfunction "F_F2") (pintype "input"))
      (node (ref "C05") (pin "H2") (pinfunction "H_H2") (pintype "input"))
      (node (ref "HJ28") (pin "AL2") (pinfunction "AL2_AL2") (pintype "output"))
    )
    (net (code "757") (name "Net-(C05B-E)") (class "Default")
      (node (ref "C05") (pin "K2") (pinfunction "E_K2") (pintype "input"))
      (node (ref "C05") (pin "L2") (pinfunction "F_L2") (pintype "input"))
      (node (ref "C05") (pin "M2") (pinfunction "H_M2") (pintype "input"))
      (node (ref "HJ28") (pin "AM2") (pinfunction "AM2_AM2") (pintype "output"))
    )
    (net (code "758") (name "Net-(C06A-E)") (class "Default")
      (node (ref "C06") (pin "E2") (pinfunction "E_E2") (pintype "input"))
      (node (ref "C06") (pin "F2") (pinfunction "F_F2") (pintype "input"))
      (node (ref "C06") (pin "H2") (pinfunction "H_H2") (pintype "input"))
      (node (ref "HJ28") (pin "AN2") (pinfunction "AN2_AN2") (pintype "output"))
    )
    (net (code "759") (name "Net-(C09A-OUT)") (class "Default")
      (node (ref "C09") (pin "C1") (pinfunction "OUT_C1") (pintype "output"))
      (node (ref "C09") (pin "D1") (pinfunction "IN1_D1") (pintype "input"))
      (node (ref "C11") (pin "K2") (pinfunction "IN2_K2") (pintype "input"))
    )
    (net (code "760") (name "Net-(C09B-OUT)") (class "Default")
      (node (ref "C09") (pin "F1") (pinfunction "OUT_F1") (pintype "output"))
      (node (ref "C09") (pin "H2") (pinfunction "IN1_H2") (pintype "input"))
      (node (ref "D10") (pin "H1") (pinfunction "IN2_H1") (pintype "input"))
    )
    (net (code "761") (name "Net-(C09G-IN2)") (class "Default")
      (node (ref "C09") (pin "J2") (pinfunction "IN2_J2") (pintype "input"))
      (node (ref "C09") (pin "N1") (pinfunction "OUT_N1") (pintype "output"))
    )
    (net (code "762") (name "Net-(C09H-IN1)") (class "Default")
      (node (ref "C09") (pin "L1") (pinfunction "IN1_L1") (pintype "input"))
      (node (ref "D09") (pin "D1") (pinfunction "OUT_D1") (pintype "output"))
    )
    (net (code "763") (name "Net-(C10A-IN1)") (class "Default")
      (node (ref "C10") (pin "A1") (pinfunction "IN1_A1") (pintype "input"))
      (node (ref "C11") (pin "D1") (pinfunction "OUT_D1") (pintype "output"))
    )
    (net (code "764") (name "Net-(C10F-IN1)") (class "Default")
      (node (ref "C10") (pin "H1") (pinfunction "IN1_H1") (pintype "input"))
      (node (ref "C11") (pin "U1") (pinfunction "OUT_U1") (pintype "output"))
    )
    (net (code "765") (name "Net-(C10F-OUT)") (class "Default")
      (node (ref "C10") (pin "K1") (pinfunction "OUT_K1") (pintype "output"))
      (node (ref "D09") (pin "E1") (pinfunction "IN1_E1") (pintype "input"))
      (node (ref "D10") (pin "L2") (pinfunction "IN2_L2") (pintype "input"))
    )
    (net (code "766") (name "Net-(C10G-IN2)") (class "Default")
      (node (ref "C10") (pin "J2") (pinfunction "IN2_J2") (pintype "input"))
      (node (ref "C11") (pin "V1") (pinfunction "OUT_V1") (pintype "output"))
    )
    (net (code "767") (name "Net-(C10G-OUT)") (class "Default")
      (node (ref "C10") (pin "K2") (pinfunction "OUT_K2") (pintype "output"))
      (node (ref "D10") (pin "M2") (pinfunction "IN3_M2") (pintype "input"))
    )
    (net (code "768") (name "Net-(C10I-IN1)") (class "Default")
      (node (ref "C10") (pin "L2") (pinfunction "IN1_L2") (pintype "input"))
      (node (ref "C10") (pin "S1") (pinfunction "OUT_S1") (pintype "output"))
    )
    (net (code "769") (name "Net-(C10I-IN2)") (class "Default")
      (node (ref "C10") (pin "M2") (pinfunction "IN2_M2") (pintype "input"))
      (node (ref "C10") (pin "S2") (pinfunction "OUT_S2") (pintype "output"))
    )
    (net (code "770") (name "Net-(C10K-IN2)") (class "Default")
      (node (ref "C10") (pin "R2") (pinfunction "IN2_R2") (pintype "input"))
      (node (ref "C10") (pin "V2") (pinfunction "OUT_V2") (pintype "output"))
    )
    (net (code "771") (name "Net-(C11D-IN1)") (class "Default")
      (node (ref "C11") (pin "D2") (pinfunction "IN1_D2") (pintype "input"))
      (node (ref "C11") (pin "J1") (pinfunction "OUT_J1") (pintype "output"))
    )
    (net (code "772") (name "Net-(C13A-IN)") (class "Default")
      (node (ref "C13") (pin "E1") (pinfunction "IN_E1") (pintype "input"))
      (node (ref "C13") (pin "S2") (pinfunction "S2_S2") (pintype "output"))
    )
    (net (code "773") (name "Net-(C13A-OUT)") (class "Default")
      (node (ref "C13") (pin "F1") (pinfunction "OUT_F1") (pintype "output"))
      (node (ref "D12") (pin "L1") (pinfunction "IN1_L1") (pintype "input"))
      (node (ref "D24") (pin "N1") (pinfunction "C_N1") (pintype "input"))
    )
    (net (code "774") (name "Net-(C13E-IN)") (class "Default")
      (node (ref "C13") (pin "H1") (pinfunction "IN_H1") (pintype "input"))
      (node (ref "C13") (pin "P2") (pinfunction "P2_P2") (pintype "output"))
    )
    (net (code "775") (name "Net-(C14A-OUT)") (class "Default")
      (node (ref "C14") (pin "C1") (pinfunction "OUT_C1") (pintype "output"))
      (node (ref "C19") (pin "A1") (pinfunction "IN1_A1") (pintype "input"))
    )
    (net (code "776") (name "Net-(C14B-OUT)") (class "Default")
      (node (ref "C14") (pin "F1") (pinfunction "OUT_F1") (pintype "output"))
      (node (ref "C19") (pin "B1") (pinfunction "IN2_B1") (pintype "input"))
    )
    (net (code "777") (name "Net-(C14C-OUT)") (class "Default")
      (node (ref "C14") (pin "F2") (pinfunction "OUT_F2") (pintype "output"))
      (node (ref "C19") (pin "C1") (pinfunction "IN3_C1") (pintype "input"))
    )
    (net (code "778") (name "Net-(C14F-OUT)") (class "Default")
      (node (ref "C14") (pin "K1") (pinfunction "OUT_K1") (pintype "output"))
      (node (ref "C19") (pin "D2") (pinfunction "IN1_D2") (pintype "input"))
    )
    (net (code "779") (name "Net-(C14G-OUT)") (class "Default")
      (node (ref "C14") (pin "K2") (pinfunction "OUT_K2") (pintype "output"))
      (node (ref "C19") (pin "E2") (pinfunction "IN2_E2") (pintype "input"))
    )
    (net (code "780") (name "Net-(C14H-OUT)") (class "Default")
      (node (ref "C14") (pin "N1") (pinfunction "OUT_N1") (pintype "output"))
      (node (ref "C19") (pin "F2") (pinfunction "IN3_F2") (pintype "input"))
    )
    (net (code "781") (name "Net-(C14I-OUT)") (class "Default")
      (node (ref "C14") (pin "N2") (pinfunction "OUT_N2") (pintype "output"))
      (node (ref "C19") (pin "E1") (pinfunction "IN1_E1") (pintype "input"))
    )
    (net (code "782") (name "Net-(C14J-OUT)") (class "Default")
      (node (ref "C14") (pin "S1") (pinfunction "OUT_S1") (pintype "output"))
      (node (ref "C19") (pin "F1") (pinfunction "IN2_F1") (pintype "input"))
    )
    (net (code "783") (name "Net-(C14K-OUT)") (class "Default")
      (node (ref "C14") (pin "S2") (pinfunction "OUT_S2") (pintype "output"))
      (node (ref "C19") (pin "H1") (pinfunction "IN3_H1") (pintype "input"))
    )
    (net (code "784") (name "Net-(C14N-OUT)") (class "Default")
      (node (ref "C14") (pin "V2") (pinfunction "OUT_V2") (pintype "output"))
      (node (ref "C20") (pin "M1") (pinfunction "IN3_M1") (pintype "input"))
    )
    (net (code "785") (name "Net-(C15A-OUT)") (class "Default")
      (node (ref "C15") (pin "C1") (pinfunction "OUT_C1") (pintype "output"))
      (node (ref "C19") (pin "J2") (pinfunction "IN1_J2") (pintype "input"))
    )
    (net (code "786") (name "Net-(C15B-OUT)") (class "Default")
      (node (ref "C15") (pin "F1") (pinfunction "OUT_F1") (pintype "output"))
      (node (ref "C19") (pin "K2") (pinfunction "IN2_K2") (pintype "input"))
    )
    (net (code "787") (name "Net-(C15C-OUT)") (class "Default")
      (node (ref "C15") (pin "F2") (pinfunction "OUT_F2") (pintype "output"))
      (node (ref "C19") (pin "L2") (pinfunction "IN3_L2") (pintype "input"))
    )
    (net (code "788") (name "Net-(C15F-OUT)") (class "Default")
      (node (ref "C15") (pin "K1") (pinfunction "OUT_K1") (pintype "output"))
      (node (ref "C19") (pin "K1") (pinfunction "IN1_K1") (pintype "input"))
    )
    (net (code "789") (name "Net-(C15G-OUT)") (class "Default")
      (node (ref "C15") (pin "K2") (pinfunction "OUT_K2") (pintype "output"))
      (node (ref "C19") (pin "L1") (pinfunction "IN2_L1") (pintype "input"))
    )
    (net (code "790") (name "Net-(C15H-OUT)") (class "Default")
      (node (ref "C15") (pin "N1") (pinfunction "OUT_N1") (pintype "output"))
      (node (ref "C19") (pin "M1") (pinfunction "IN3_M1") (pintype "input"))
    )
    (net (code "791") (name "Net-(C15I-OUT)") (class "Default")
      (node (ref "C15") (pin "N2") (pinfunction "OUT_N2") (pintype "output"))
      (node (ref "C19") (pin "N2") (pinfunction "IN1_N2") (pintype "input"))
    )
    (net (code "792") (name "Net-(C15J-OUT)") (class "Default")
      (node (ref "C15") (pin "S1") (pinfunction "OUT_S1") (pintype "output"))
      (node (ref "C19") (pin "P2") (pinfunction "IN2_P2") (pintype "input"))
    )
    (net (code "793") (name "Net-(C15K-OUT)") (class "Default")
      (node (ref "C15") (pin "S2") (pinfunction "OUT_S2") (pintype "output"))
      (node (ref "C19") (pin "R2") (pinfunction "IN3_R2") (pintype "input"))
    )
    (net (code "794") (name "Net-(C15N-OUT)") (class "Default")
      (node (ref "C15") (pin "V2") (pinfunction "OUT_V2") (pintype "output"))
      (node (ref "C20") (pin "R2") (pinfunction "IN3_R2") (pintype "input"))
    )
    (net (code "795") (name "Net-(C16A-OUT)") (class "Default")
      (node (ref "C16") (pin "C1") (pinfunction "OUT_C1") (pintype "output"))
      (node (ref "C19") (pin "P1") (pinfunction "IN1_P1") (pintype "input"))
    )
    (net (code "796") (name "Net-(C16B-OUT)") (class "Default")
      (node (ref "C16") (pin "F1") (pinfunction "OUT_F1") (pintype "output"))
      (node (ref "C19") (pin "R1") (pinfunction "IN2_R1") (pintype "input"))
    )
    (net (code "797") (name "Net-(C16C-OUT)") (class "Default")
      (node (ref "C16") (pin "F2") (pinfunction "OUT_F2") (pintype "output"))
      (node (ref "C19") (pin "S1") (pinfunction "IN3_S1") (pintype "input"))
    )
    (net (code "798") (name "Net-(C16F-OUT)") (class "Default")
      (node (ref "C16") (pin "K1") (pinfunction "OUT_K1") (pintype "output"))
      (node (ref "C19") (pin "T2") (pinfunction "IN1_T2") (pintype "input"))
    )
    (net (code "799") (name "Net-(C16G-OUT)") (class "Default")
      (node (ref "C16") (pin "K2") (pinfunction "OUT_K2") (pintype "output"))
      (node (ref "C19") (pin "U2") (pinfunction "IN2_U2") (pintype "input"))
    )
    (net (code "800") (name "Net-(C16H-OUT)") (class "Default")
      (node (ref "C16") (pin "N1") (pinfunction "OUT_N1") (pintype "output"))
      (node (ref "C19") (pin "V2") (pinfunction "IN3_V2") (pintype "input"))
    )
    (net (code "801") (name "Net-(C16I-OUT)") (class "Default")
      (node (ref "C16") (pin "N2") (pinfunction "OUT_N2") (pintype "output"))
      (node (ref "C20") (pin "A1") (pinfunction "IN1_A1") (pintype "input"))
    )
    (net (code "802") (name "Net-(C16J-OUT)") (class "Default")
      (node (ref "C16") (pin "S1") (pinfunction "OUT_S1") (pintype "output"))
      (node (ref "C20") (pin "B1") (pinfunction "IN2_B1") (pintype "input"))
    )
    (net (code "803") (name "Net-(C16K-OUT)") (class "Default")
      (node (ref "C16") (pin "S2") (pinfunction "OUT_S2") (pintype "output"))
      (node (ref "C20") (pin "C1") (pinfunction "IN3_C1") (pintype "input"))
    )
    (net (code "804") (name "Net-(C16N-OUT)") (class "Default")
      (node (ref "C16") (pin "V2") (pinfunction "OUT_V2") (pintype "output"))
      (node (ref "C20") (pin "S1") (pinfunction "IN3_S1") (pintype "input"))
    )
    (net (code "805") (name "Net-(C17A-OUT)") (class "Default")
      (node (ref "C17") (pin "C1") (pinfunction "OUT_C1") (pintype "output"))
      (node (ref "C20") (pin "D2") (pinfunction "IN1_D2") (pintype "input"))
    )
    (net (code "806") (name "Net-(C17B-OUT)") (class "Default")
      (node (ref "C17") (pin "F1") (pinfunction "OUT_F1") (pintype "output"))
      (node (ref "C20") (pin "E2") (pinfunction "IN2_E2") (pintype "input"))
    )
    (net (code "807") (name "Net-(C17C-OUT)") (class "Default")
      (node (ref "C17") (pin "F2") (pinfunction "OUT_F2") (pintype "output"))
      (node (ref "C20") (pin "F2") (pinfunction "IN3_F2") (pintype "input"))
    )
    (net (code "808") (name "Net-(C17F-OUT)") (class "Default")
      (node (ref "C17") (pin "K1") (pinfunction "OUT_K1") (pintype "output"))
      (node (ref "C20") (pin "E1") (pinfunction "IN1_E1") (pintype "input"))
    )
    (net (code "809") (name "Net-(C17G-OUT)") (class "Default")
      (node (ref "C17") (pin "K2") (pinfunction "OUT_K2") (pintype "output"))
      (node (ref "C20") (pin "F1") (pinfunction "IN2_F1") (pintype "input"))
    )
    (net (code "810") (name "Net-(C17H-OUT)") (class "Default")
      (node (ref "C17") (pin "N1") (pinfunction "OUT_N1") (pintype "output"))
      (node (ref "C20") (pin "H1") (pinfunction "IN3_H1") (pintype "input"))
    )
    (net (code "811") (name "Net-(C17I-OUT)") (class "Default")
      (node (ref "C17") (pin "N2") (pinfunction "OUT_N2") (pintype "output"))
      (node (ref "C20") (pin "J2") (pinfunction "IN1_J2") (pintype "input"))
    )
    (net (code "812") (name "Net-(C17J-OUT)") (class "Default")
      (node (ref "C17") (pin "S1") (pinfunction "OUT_S1") (pintype "output"))
      (node (ref "C20") (pin "K2") (pinfunction "IN2_K2") (pintype "input"))
    )
    (net (code "813") (name "Net-(C17K-IN2)") (class "Default")
      (node (ref "C17") (pin "R2") (pinfunction "IN2_R2") (pintype "input"))
      (node (ref "D23") (pin "T2") (pinfunction "OUT_T2") (pintype "output"))
    )
    (net (code "814") (name "Net-(C17K-OUT)") (class "Default")
      (node (ref "C17") (pin "S2") (pinfunction "OUT_S2") (pintype "output"))
      (node (ref "C20") (pin "L2") (pinfunction "IN3_L2") (pintype "input"))
    )
    (net (code "815") (name "Net-(C17N-OUT)") (class "Default")
      (node (ref "C17") (pin "V2") (pinfunction "OUT_V2") (pintype "output"))
      (node (ref "C20") (pin "V2") (pinfunction "IN3_V2") (pintype "input"))
    )
    (net (code "816") (name "Net-(C18A-IN2)") (class "Default")
      (node (ref "C18") (pin "B1") (pinfunction "IN2_B1") (pintype "input"))
      (node (ref "C21") (pin "E2") (pinfunction "IN2_E2") (pintype "input"))
      (node (ref "D22") (pin "E1") (pinfunction "OUT_E1") (pintype "output"))
    )
    (net (code "817") (name "Net-(C18B-IN2)") (class "Default")
      (node (ref "C18") (pin "E1") (pinfunction "IN2_E1") (pintype "input"))
      (node (ref "C21") (pin "K2") (pinfunction "IN2_K2") (pintype "input"))
      (node (ref "D19") (pin "D1") (pinfunction "OUT_D1") (pintype "output"))
    )
    (net (code "818") (name "Net-(C18B-OUT)") (class "Default")
      (node (ref "C18") (pin "F1") (pinfunction "OUT_F1") (pintype "output"))
      (node (ref "C21") (pin "F1") (pinfunction "IN2_F1") (pintype "input"))
    )
    (net (code "819") (name "Net-(C18C-IN2)") (class "Default")
      (node (ref "C18") (pin "E2") (pinfunction "IN2_E2") (pintype "input"))
      (node (ref "C18") (pin "K1") (pinfunction "OUT_K1") (pintype "output"))
      (node (ref "C21") (pin "P2") (pinfunction "IN2_P2") (pintype "input"))
    )
    (net (code "820") (name "Net-(C18C-OUT)") (class "Default")
      (node (ref "C18") (pin "F2") (pinfunction "OUT_F2") (pintype "output"))
      (node (ref "C21") (pin "L1") (pinfunction "IN2_L1") (pintype "input"))
    )
    (net (code "821") (name "Net-(C18H-IN1)") (class "Default")
      (node (ref "C18") (pin "L1") (pinfunction "IN1_L1") (pintype "input"))
      (node (ref "C18") (pin "N2") (pinfunction "OUT_N2") (pintype "output"))
    )
    (net (code "822") (name "Net-(C18H-IN2)") (class "Default")
      (node (ref "C18") (pin "M1") (pinfunction "IN2_M1") (pintype "input"))
      (node (ref "C18") (pin "S1") (pinfunction "OUT_S1") (pintype "output"))
    )
    (net (code "823") (name "Net-(C18H-OUT)") (class "Default")
      (node (ref "C18") (pin "N1") (pinfunction "OUT_N1") (pintype "output"))
      (node (ref "C22") (pin "P1") (pinfunction "D_P1") (pintype "input"))
    )
    (net (code "824") (name "Net-(C19A-OUT)") (class "Default")
      (node (ref "C19") (pin "D1") (pinfunction "OUT_D1") (pintype "output"))
      (node (ref "C23") (pin "C1") (pinfunction "D_C1") (pintype "input"))
    )
    (net (code "825") (name "Net-(C19D-OUT)") (class "Default")
      (node (ref "C19") (pin "H2") (pinfunction "OUT_H2") (pintype "output"))
      (node (ref "C23") (pin "E2") (pinfunction "D_E2") (pintype "input"))
    )
    (net (code "826") (name "Net-(C19E-OUT)") (class "Default")
      (node (ref "C19") (pin "J1") (pinfunction "OUT_J1") (pintype "output"))
      (node (ref "C23") (pin "J1") (pinfunction "D_J1") (pintype "input"))
    )
    (net (code "827") (name "Net-(C19F-OUT)") (class "Default")
      (node (ref "C19") (pin "M2") (pinfunction "OUT_M2") (pintype "output"))
      (node (ref "C23") (pin "M2") (pinfunction "D_M2") (pintype "input"))
    )
    (net (code "828") (name "Net-(C19G-OUT)") (class "Default")
      (node (ref "C19") (pin "N1") (pinfunction "OUT_N1") (pintype "output"))
      (node (ref "C23") (pin "P1") (pinfunction "D_P1") (pintype "input"))
    )
    (net (code "829") (name "Net-(C19H-OUT)") (class "Default")
      (node (ref "C19") (pin "S2") (pinfunction "OUT_S2") (pintype "output"))
      (node (ref "C23") (pin "T2") (pinfunction "D_T2") (pintype "input"))
    )
    (net (code "830") (name "Net-(C19I-OUT)") (class "Default")
      (node (ref "C19") (pin "U1") (pinfunction "OUT_U1") (pintype "output"))
      (node (ref "C24") (pin "C1") (pinfunction "D_C1") (pintype "input"))
    )
    (net (code "831") (name "Net-(C19J-OUT)") (class "Default")
      (node (ref "C19") (pin "V1") (pinfunction "OUT_V1") (pintype "output"))
      (node (ref "C24") (pin "E2") (pinfunction "D_E2") (pintype "input"))
    )
    (net (code "832") (name "Net-(C20A-OUT)") (class "Default")
      (node (ref "C20") (pin "D1") (pinfunction "OUT_D1") (pintype "output"))
      (node (ref "C24") (pin "J1") (pinfunction "D_J1") (pintype "input"))
    )
    (net (code "833") (name "Net-(C20D-OUT)") (class "Default")
      (node (ref "C20") (pin "H2") (pinfunction "OUT_H2") (pintype "output"))
      (node (ref "C24") (pin "M2") (pinfunction "D_M2") (pintype "input"))
    )
    (net (code "834") (name "Net-(C20E-OUT)") (class "Default")
      (node (ref "C20") (pin "J1") (pinfunction "OUT_J1") (pintype "output"))
      (node (ref "C24") (pin "P1") (pinfunction "D_P1") (pintype "input"))
    )
    (net (code "835") (name "Net-(C20F-OUT)") (class "Default")
      (node (ref "C20") (pin "M2") (pinfunction "OUT_M2") (pintype "output"))
      (node (ref "C24") (pin "T2") (pinfunction "D_T2") (pintype "input"))
    )
    (net (code "836") (name "Net-(C20G-IN1)") (class "Default")
      (node (ref "C20") (pin "K1") (pinfunction "IN1_K1") (pintype "input"))
      (node (ref "C21") (pin "D1") (pinfunction "OUT_D1") (pintype "output"))
    )
    (net (code "837") (name "Net-(C20G-IN2)") (class "Default")
      (node (ref "C20") (pin "L1") (pinfunction "IN2_L1") (pintype "input"))
      (node (ref "C21") (pin "H2") (pinfunction "OUT_H2") (pintype "output"))
    )
    (net (code "838") (name "Net-(C20G-OUT)") (class "Default")
      (node (ref "C20") (pin "N1") (pinfunction "OUT_N1") (pintype "output"))
      (node (ref "C22") (pin "C1") (pinfunction "D_C1") (pintype "input"))
    )
    (net (code "839") (name "Net-(C20H-IN1)") (class "Default")
      (node (ref "C20") (pin "N2") (pinfunction "IN1_N2") (pintype "input"))
      (node (ref "C21") (pin "J1") (pinfunction "OUT_J1") (pintype "output"))
    )
    (net (code "840") (name "Net-(C20H-IN2)") (class "Default")
      (node (ref "C20") (pin "P2") (pinfunction "IN2_P2") (pintype "input"))
      (node (ref "C21") (pin "M2") (pinfunction "OUT_M2") (pintype "output"))
    )
    (net (code "841") (name "Net-(C20H-OUT)") (class "Default")
      (node (ref "C20") (pin "S2") (pinfunction "OUT_S2") (pintype "output"))
      (node (ref "C22") (pin "E2") (pinfunction "D_E2") (pintype "input"))
    )
    (net (code "842") (name "Net-(C20I-IN1)") (class "Default")
      (node (ref "C20") (pin "P1") (pinfunction "IN1_P1") (pintype "input"))
      (node (ref "C21") (pin "N1") (pinfunction "OUT_N1") (pintype "output"))
    )
    (net (code "843") (name "Net-(C20I-IN2)") (class "Default")
      (node (ref "C20") (pin "R1") (pinfunction "IN2_R1") (pintype "input"))
      (node (ref "C21") (pin "S2") (pinfunction "OUT_S2") (pintype "output"))
    )
    (net (code "844") (name "Net-(C20I-OUT)") (class "Default")
      (node (ref "C20") (pin "U1") (pinfunction "OUT_U1") (pintype "output"))
      (node (ref "C22") (pin "J1") (pinfunction "D_J1") (pintype "input"))
    )
    (net (code "845") (name "Net-(C20J-IN1)") (class "Default")
      (node (ref "C20") (pin "T2") (pinfunction "IN1_T2") (pintype "input"))
      (node (ref "C21") (pin "U1") (pinfunction "OUT_U1") (pintype "output"))
    )
    (net (code "846") (name "Net-(C20J-IN2)") (class "Default")
      (node (ref "C20") (pin "U2") (pinfunction "IN2_U2") (pintype "input"))
      (node (ref "C21") (pin "V1") (pinfunction "OUT_V1") (pintype "output"))
    )
    (net (code "847") (name "Net-(C20J-OUT)") (class "Default")
      (node (ref "C20") (pin "V1") (pinfunction "OUT_V1") (pintype "output"))
      (node (ref "C22") (pin "M2") (pinfunction "D_M2") (pintype "input"))
    )
    (net (code "848") (name "Net-(D06A-IN)") (class "Default")
      (node (ref "D06") (pin "E1") (pinfunction "IN_E1") (pintype "input"))
      (node (ref "D06") (pin "R2") (pinfunction "R2_R2") (pintype "output"))
    )
    (net (code "849") (name "Net-(D07A-IN1)") (class "Default")
      (node (ref "D07") (pin "A1") (pinfunction "IN1_A1") (pintype "input"))
      (node (ref "D07") (pin "D1") (pinfunction "IN1_D1") (pintype "input"))
      (node (ref "D07") (pin "F2") (pinfunction "OUT_F2") (pintype "output"))
    )
    (net (code "850") (name "Net-(D07F-IN2)") (class "Default")
      (node (ref "D06") (pin "H2") (pinfunction "H2_H2") (pintype "input"))
      (node (ref "D07") (pin "J1") (pinfunction "IN2_J1") (pintype "input"))
      (node (ref "D07") (pin "S2") (pinfunction "OUT_S2") (pintype "output"))
    )
    (net (code "851") (name "Net-(D07J-OUT)") (class "Default")
      (node (ref "D07") (pin "S1") (pinfunction "OUT_S1") (pintype "output"))
      (node (ref "E09") (pin "D1") (pinfunction "IN1_D1") (pintype "input"))
    )
    (net (code "852") (name "Net-(D07K-IN2)") (class "Default")
      (node (ref "D07") (pin "R2") (pinfunction "IN2_R2") (pintype "input"))
      (node (ref "D07") (pin "V2") (pinfunction "OUT_V2") (pintype "output"))
    )
    (net (code "853") (name "Net-(D09I-OUT)") (class "Default")
      (node (ref "D09") (pin "T2") (pinfunction "IN1_T2") (pintype "input"))
      (node (ref "D09") (pin "U1") (pinfunction "OUT_U1") (pintype "output"))
    )
    (net (code "854") (name "Net-(D12B-IN1)") (class "Default")
      (node (ref "D12") (pin "D1") (pinfunction "IN1_D1") (pintype "input"))
      (node (ref "D12") (pin "F2") (pinfunction "OUT_F2") (pintype "output"))
    )
    (net (code "855") (name "Net-(D12B-OUT)") (class "Default")
      (node (ref "D12") (pin "F1") (pinfunction "OUT_F1") (pintype "output"))
      (node (ref "D23") (pin "S1") (pinfunction "IN1A_S1") (pintype "input"))
    )
    (net (code "856") (name "Net-(D12H-OUT)") (class "Default")
      (node (ref "D12") (pin "N1") (pinfunction "OUT_N1") (pintype "output"))
      (node (ref "D24") (pin "U2") (pinfunction "S_U2") (pintype "input"))
    )
    (net (code "857") (name "Net-(D12I-OUT)") (class "Default")
      (node (ref "D12") (pin "N2") (pinfunction "OUT_N2") (pintype "output"))
      (node (ref "D24") (pin "T2") (pinfunction "D_T2") (pintype "input"))
    )
    (net (code "858") (name "Net-(D12J-OUT)") (class "Default")
      (node (ref "D12") (pin "S1") (pinfunction "OUT_S1") (pintype "output"))
      (node (ref "D24") (pin "S2") (pinfunction "C_S2") (pintype "input"))
    )
    (net (code "859") (name "Net-(D12K-OUT)") (class "Default")
      (node (ref "D12") (pin "S2") (pinfunction "OUT_S2") (pintype "output"))
      (node (ref "D22") (pin "U2") (pinfunction "IN4_U2") (pintype "input"))
    )
    (net (code "860") (name "Net-(D13B-OUT)") (class "Default")
      (node (ref "D13") (pin "F1") (pinfunction "OUT_F1") (pintype "output"))
      (node (ref "D17") (pin "R1") (pinfunction "IN2_R1") (pintype "input"))
    )
    (net (code "861") (name "Net-(D13C-OUT)") (class "Default")
      (node (ref "D13") (pin "F2") (pinfunction "OUT_F2") (pintype "output"))
      (node (ref "D17") (pin "R2") (pinfunction "IN3_R2") (pintype "input"))
    )
    (net (code "862") (name "Net-(D13G-IN1)") (class "Default")
      (node (ref "D13") (pin "H2") (pinfunction "IN1_H2") (pintype "input"))
      (node (ref "D20") (pin "S1") (pinfunction "OUT_S1") (pintype "output"))
    )
    (net (code "863") (name "Net-(D13H-IN1)") (class "Default")
      (node (ref "D13") (pin "L1") (pinfunction "IN1_L1") (pintype "input"))
      (node (ref "D13") (pin "S1") (pinfunction "OUT_S1") (pintype "output"))
    )
    (net (code "864") (name "Net-(D13N-OUT)") (class "Default")
      (node (ref "D13") (pin "V2") (pinfunction "OUT_V2") (pintype "output"))
      (node (ref "D16") (pin "L1") (pinfunction "IN1_L1") (pintype "input"))
    )
    (net (code "865") (name "Net-(D14B-OUT)") (class "Default")
      (node (ref "C13") (pin "H2") (pinfunction "H2_H2") (pintype "input"))
      (node (ref "D14") (pin "F1") (pinfunction "OUT_F1") (pintype "output"))
      (node (ref "D24") (pin "L2") (pinfunction "C_L2") (pintype "input"))
    )
    (net (code "866") (name "Net-(D14C-OUT)") (class "Default")
      (node (ref "D14") (pin "F2") (pinfunction "OUT_F2") (pintype "output"))
      (node (ref "D14") (pin "J2") (pinfunction "IN2_J2") (pintype "input"))
    )
    (net (code "867") (name "Net-(D14G-IN1)") (class "Default")
      (node (ref "D14") (pin "H2") (pinfunction "IN1_H2") (pintype "input"))
      (node (ref "D14") (pin "N2") (pinfunction "OUT_N2") (pintype "output"))
    )
    (net (code "868") (name "Net-(D14H-OUT)") (class "Default")
      (node (ref "D14") (pin "N1") (pinfunction "OUT_N1") (pintype "output"))
      (node (ref "D19") (pin "F2") (pinfunction "IN3_F2") (pintype "input"))
    )
    (net (code "869") (name "Net-(D14J-IN2)") (class "Default")
      (node (ref "D14") (pin "R1") (pinfunction "IN2_R1") (pintype "input"))
      (node (ref "D14") (pin "S2") (pinfunction "OUT_S2") (pintype "output"))
    )
    (net (code "870") (name "Net-(D14J-OUT)") (class "Default")
      (node (ref "D14") (pin "S1") (pinfunction "OUT_S1") (pintype "output"))
      (node (ref "D24") (pin "B1") (pinfunction "C_B1") (pintype "input"))
      (node (ref "D24") (pin "D2") (pinfunction "C_D2") (pintype "input"))
      (node (ref "D24") (pin "H1") (pinfunction "C_H1") (pintype "input"))
    )
    (net (code "871") (name "Net-(D14N-OUT)") (class "Default")
      (node (ref "D14") (pin "V2") (pinfunction "OUT_V2") (pintype "output"))
      (node (ref "D22") (pin "S2") (pinfunction "IN2_S2") (pintype "input"))
    )
    (net (code "872") (name "Net-(D15A-OUT)") (class "Default")
      (node (ref "D15") (pin "C1") (pinfunction "OUT_C1") (pintype "output"))
      (node (ref "D17") (pin "D2") (pinfunction "IN1_D2") (pintype "input"))
    )
    (net (code "873") (name "Net-(D15B-OUT)") (class "Default")
      (node (ref "D15") (pin "F1") (pinfunction "OUT_F1") (pintype "output"))
      (node (ref "D17") (pin "F2") (pinfunction "IN3_F2") (pintype "input"))
    )
    (net (code "874") (name "Net-(D15C-IN2)") (class "Default")
      (node (ref "D15") (pin "E2") (pinfunction "IN2_E2") (pintype "input"))
      (node (ref "D21") (pin "E1") (pinfunction "OUT_E1") (pintype "output"))
    )
    (net (code "875") (name "Net-(D15G-OUT)") (class "Default")
      (node (ref "D15") (pin "K2") (pinfunction "OUT_K2") (pintype "output"))
      (node (ref "D15") (pin "L1") (pinfunction "IN1_L1") (pintype "input"))
    )
    (net (code "876") (name "Net-(D15H-OUT)") (class "Default")
      (node (ref "D15") (pin "N1") (pinfunction "OUT_N1") (pintype "output"))
      (node (ref "D24") (pin "M2") (pinfunction "D_M2") (pintype "input"))
    )
    (net (code "877") (name "Net-(D15I-IN1)") (class "Default")
      (node (ref "D15") (pin "L2") (pinfunction "IN1_L2") (pintype "input"))
      (node (ref "D21") (pin "J2") (pinfunction "OUT_J2") (pintype "output"))
    )
    (net (code "878") (name "Net-(D15K-OUT)") (class "Default")
      (node (ref "D15") (pin "S2") (pinfunction "OUT_S2") (pintype "output"))
      (node (ref "D20") (pin "K1") (pinfunction "IN4_K1") (pintype "input"))
    )
    (net (code "879") (name "Net-(D15N-IN1)") (class "Default")
      (node (ref "D15") (pin "T2") (pinfunction "IN1_T2") (pintype "input"))
      (node (ref "D17") (pin "S1") (pinfunction "IN3_S1") (pintype "input"))
      (node (ref "D18") (pin "D1") (pinfunction "OUT_D1") (pintype "output"))
    )
    (net (code "880") (name "Net-(D16A-IN2)") (class "Default")
      (node (ref "D16") (pin "B1") (pinfunction "IN2_B1") (pintype "input"))
      (node (ref "D21") (pin "P2") (pinfunction "OUT_P2") (pintype "output"))
    )
    (net (code "881") (name "Net-(D16A-OUT)") (class "Default")
      (node (ref "D16") (pin "C1") (pinfunction "OUT_C1") (pintype "output"))
      (node (ref "D21") (pin "A1") (pinfunction "IN1_A1") (pintype "input"))
    )
    (net (code "882") (name "Net-(D16B-IN2)") (class "Default")
      (node (ref "D16") (pin "E1") (pinfunction "IN2_E1") (pintype "input"))
      (node (ref "D21") (pin "S1") (pinfunction "OUT_S1") (pintype "output"))
    )
    (net (code "883") (name "Net-(D16B-OUT)") (class "Default")
      (node (ref "D16") (pin "F1") (pinfunction "OUT_F1") (pintype "output"))
      (node (ref "D21") (pin "B1") (pinfunction "IN2_B1") (pintype "input"))
    )
    (net (code "884") (name "Net-(D16C-IN2)") (class "Default")
      (node (ref "D16") (pin "E2") (pinfunction "IN2_E2") (pintype "input"))
      (node (ref "D21") (pin "V2") (pinfunction "OUT_V2") (pintype "output"))
    )
    (net (code "885") (name "Net-(D16C-OUT)") (class "Default")
      (node (ref "D16") (pin "F2") (pinfunction "OUT_F2") (pintype "output"))
      (node (ref "D21") (pin "C1") (pinfunction "IN3_C1") (pintype "input"))
    )
    (net (code "886") (name "Net-(D16F-IN1)") (class "Default")
      (node (ref "D16") (pin "H1") (pinfunction "IN1_H1") (pintype "input"))
      (node (ref "D19") (pin "J1") (pinfunction "OUT_J1") (pintype "output"))
    )
    (net (code "887") (name "Net-(D16F-IN2)") (class "Default")
      (node (ref "D16") (pin "J1") (pinfunction "IN2_J1") (pintype "input"))
      (node (ref "D19") (pin "M2") (pinfunction "OUT_M2") (pintype "output"))
    )
    (net (code "888") (name "Net-(D16G-OUT)") (class "Default")
      (node (ref "D16") (pin "K2") (pinfunction "OUT_K2") (pintype "output"))
      (node (ref "D19") (pin "D2") (pinfunction "IN1_D2") (pintype "input"))
    )
    (net (code "889") (name "Net-(D16H-OUT)") (class "Default")
      (node (ref "D16") (pin "L2") (pinfunction "IN1_L2") (pintype "input"))
      (node (ref "D16") (pin "N1") (pinfunction "OUT_N1") (pintype "output"))
      (node (ref "D18") (pin "P2") (pinfunction "IN2_P2") (pintype "input"))
    )
    (net (code "890") (name "Net-(D16I-OUT)") (class "Default")
      (node (ref "D16") (pin "N2") (pinfunction "OUT_N2") (pintype "output"))
      (node (ref "D18") (pin "R1") (pinfunction "IN2_R1") (pintype "input"))
    )
    (net (code "891") (name "Net-(D17D-IN2)") (class "Default")
      (node (ref "D17") (pin "E2") (pinfunction "IN2_E2") (pintype "input"))
      (node (ref "D20") (pin "E1") (pinfunction "OUT_E1") (pintype "output"))
    )
    (net (code "892") (name "Net-(D17E-OUT)") (class "Default")
      (node (ref "D17") (pin "J1") (pinfunction "OUT_J1") (pintype "output"))
      (node (ref "D17") (pin "K2") (pinfunction "IN2_K2") (pintype "input"))
      (node (ref "D20") (pin "F2") (pinfunction "IN3_F2") (pintype "input"))
    )
    (net (code "893") (name "Net-(D17G-IN2)") (class "Default")
      (node (ref "D17") (pin "L1") (pinfunction "IN2_L1") (pintype "input"))
      (node (ref "D17") (pin "S2") (pinfunction "OUT_S2") (pintype "output"))
    )
    (net (code "894") (name "Net-(D17H-IN2)") (class "Default")
      (node (ref "D17") (pin "P2") (pinfunction "IN2_P2") (pintype "input"))
      (node (ref "D23") (pin "V2") (pinfunction "OUT_V2") (pintype "output"))
    )
    (net (code "895") (name "Net-(D18D-OUT)") (class "Default")
      (node (ref "D18") (pin "H2") (pinfunction "OUT_H2") (pintype "output"))
      (node (ref "D22") (pin "F1") (pinfunction "IN1_F1") (pintype "input"))
    )
    (net (code "896") (name "Net-(D18E-OUT)") (class "Default")
      (node (ref "D18") (pin "J1") (pinfunction "OUT_J1") (pintype "output"))
      (node (ref "D22") (pin "K2") (pinfunction "IN1_K2") (pintype "input"))
    )
    (net (code "897") (name "Net-(D18G-OUT)") (class "Default")
      (node (ref "D18") (pin "N1") (pinfunction "OUT_N1") (pintype "output"))
      (node (ref "D22") (pin "R1") (pinfunction "IN4_R1") (pintype "input"))
    )
    (net (code "898") (name "Net-(D19D-IN2)") (class "Default")
      (node (ref "D19") (pin "E2") (pinfunction "IN2_E2") (pintype "input"))
      (node (ref "D19") (pin "N1") (pinfunction "OUT_N1") (pintype "output"))
    )
    (net (code "899") (name "Net-(D19D-OUT)") (class "Default")
      (node (ref "D19") (pin "H2") (pinfunction "OUT_H2") (pintype "output"))
      (node (ref "D23") (pin "P1") (pinfunction "IN5C_P1") (pintype "input"))
    )
    (net (code "900") (name "Net-(D20E-IN2)") (class "Default")
      (node (ref "D20") (pin "H1") (pinfunction "IN2_H1") (pintype "input"))
      (node (ref "D20") (pin "P2") (pinfunction "OUT_P2") (pintype "output"))
    )
    (net (code "901") (name "Net-(E09A-OUT)") (class "Default")
      (node (ref "E09") (pin "C1") (pinfunction "OUT_C1") (pintype "output"))
      (node (ref "E09") (pin "E1") (pinfunction "IN2_E1") (pintype "input"))
    )
    (net (code "902") (name "Net-(E09G-OUT)") (class "Default")
      (node (ref "E09") (pin "K2") (pinfunction "OUT_K2") (pintype "output"))
      (node (ref "F11") (pin "K2") (pinfunction "IN1_K2") (pintype "input"))
    )
    (net (code "903") (name "Net-(E11J-IN1)") (class "Default")
      (node (ref "E11") (pin "P1") (pinfunction "IN1_P1") (pintype "input"))
      (node (ref "F11") (pin "L1") (pinfunction "OUT_L1") (pintype "output"))
    )
    (net (code "904") (name "Net-(E11N-OUT)") (class "Default")
      (node (ref "E11") (pin "V2") (pinfunction "OUT_V2") (pintype "output"))
      (node (ref "E12") (pin "R2") (pinfunction "IN2_R2") (pintype "input"))
    )
    (net (code "905") (name "Net-(E12A-IN1)") (class "Default")
      (node (ref "E12") (pin "A1") (pinfunction "IN1_A1") (pintype "input"))
      (node (ref "E12") (pin "F1") (pinfunction "OUT_F1") (pintype "output"))
    )
    (net (code "906") (name "Net-(E12A-OUT)") (class "Default")
      (node (ref "E12") (pin "C1") (pinfunction "OUT_C1") (pintype "output"))
      (node (ref "E18") (pin "K1") (pinfunction "S_K1") (pintype "input"))
    )
    (net (code "907") (name "Net-(E12C-OUT)") (class "Default")
      (node (ref "E12") (pin "F2") (pinfunction "OUT_F2") (pintype "output"))
      (node (ref "E16") (pin "H2") (pinfunction "H2_H2") (pintype "input"))
    )
    (net (code "908") (name "Net-(E12J-IN1)") (class "Default")
      (node (ref "E12") (pin "P1") (pinfunction "IN1_P1") (pintype "input"))
      (node (ref "F19") (pin "P2") (pinfunction "OUT_P2") (pintype "output"))
    )
    (net (code "909") (name "Net-(E12K-OUT)") (class "Default")
      (node (ref "E12") (pin "S2") (pinfunction "OUT_S2") (pintype "output"))
      (node (ref "F21") (pin "A1") (pinfunction "IN1_A1") (pintype "input"))
    )
    (net (code "910") (name "Net-(E12N-IN2)") (class "Default")
      (node (ref "E12") (pin "U2") (pinfunction "IN2_U2") (pintype "input"))
      (node (ref "F19") (pin "S1") (pinfunction "OUT_S1") (pintype "output"))
    )
    (net (code "911") (name "Net-(E13C-OUT)") (class "Default")
      (node (ref "E13") (pin "R1") (pinfunction "OUT_R1") (pintype "output"))
      (node (ref "E18") (pin "M2") (pinfunction "D_M2") (pintype "input"))
    )
    (net (code "912") (name "Net-(E14A-OUT)") (class "Default")
      (node (ref "E14") (pin "D1") (pinfunction "OUT_D1") (pintype "output"))
      (node (ref "E15") (pin "D2") (pinfunction "IN1_D2") (pintype "input"))
      (node (ref "F08") (pin "J2") (pinfunction "IN2_J2") (pintype "input"))
    )
    (net (code "913") (name "Net-(E14D-OUT)") (class "Default")
      (node (ref "E14") (pin "H2") (pinfunction "OUT_H2") (pintype "output"))
      (node (ref "F09") (pin "K2") (pinfunction "IN5_K2") (pintype "input"))
    )
    (net (code "914") (name "Net-(E14E-IN1)") (class "Default")
      (node (ref "E14") (pin "E1") (pinfunction "IN1_E1") (pintype "input"))
      (node (ref "F19") (pin "K1") (pinfunction "IN4_K1") (pintype "input"))
      (node (ref "F21") (pin "S2") (pinfunction "OUT_S2") (pintype "output"))
      (node (ref "F21") (pin "U2") (pinfunction "IN2_U2") (pintype "input"))
    )
    (net (code "915") (name "Net-(E14E-IN2)") (class "Default")
      (node (ref "E14") (pin "F1") (pinfunction "IN2_F1") (pintype "input"))
      (node (ref "F19") (pin "J1") (pinfunction "IN3_J1") (pintype "input"))
      (node (ref "F21") (pin "S1") (pinfunction "OUT_S1") (pintype "output"))
      (node (ref "F21") (pin "T2") (pinfunction "IN1_T2") (pintype "input"))
    )
    (net (code "916") (name "Net-(E14G-OUT)") (class "Default")
      (node (ref "E14") (pin "N1") (pinfunction "OUT_N1") (pintype "output"))
      (node (ref "E14") (pin "N2") (pinfunction "IN1_N2") (pintype "input"))
    )
    (net (code "917") (name "Net-(E14I-OUT)") (class "Default")
      (node (ref "E14") (pin "U1") (pinfunction "OUT_U1") (pintype "output"))
      (node (ref "F12") (pin "H2") (pinfunction "H2_H2") (pintype "input"))
    )
    (net (code "918") (name "Net-(E14J-OUT)") (class "Default")
      (node (ref "E14") (pin "V1") (pinfunction "OUT_V1") (pintype "output"))
      (node (ref "E15") (pin "T2") (pinfunction "IN1_T2") (pintype "input"))
    )
    (net (code "919") (name "Net-(E15A-OUT)") (class "Default")
      (node (ref "E15") (pin "C1") (pinfunction "OUT_C1") (pintype "output"))
      (node (ref "F08") (pin "H2") (pinfunction "IN1_H2") (pintype "input"))
    )
    (net (code "920") (name "Net-(E15C-IN2)") (class "Default")
      (node (ref "E15") (pin "E2") (pinfunction "IN2_E2") (pintype "input"))
      (node (ref "E15") (pin "K1") (pinfunction "OUT_K1") (pintype "output"))
    )
    (net (code "921") (name "Net-(E15H-OUT)") (class "Default")
      (node (ref "E15") (pin "N1") (pinfunction "OUT_N1") (pintype "output"))
      (node (ref "E19") (pin "F2") (pinfunction "S_F2") (pintype "input"))
      (node (ref "F08") (pin "N2") (pinfunction "IN1_N2") (pintype "input"))
    )
    (net (code "922") (name "Net-(E15K-OUT)") (class "Default")
      (node (ref "E15") (pin "S2") (pinfunction "OUT_S2") (pintype "output"))
      (node (ref "F13") (pin "H2") (pinfunction "H2_H2") (pintype "input"))
    )
    (net (code "923") (name "Net-(E16A-IN)") (class "Default")
      (node (ref "E16") (pin "E1") (pinfunction "IN_E1") (pintype "input"))
      (node (ref "E16") (pin "R2") (pinfunction "R2_R2") (pintype "output"))
    )
    (net (code "924") (name "Net-(E16A-OUT)") (class "Default")
      (node (ref "E16") (pin "F1") (pinfunction "OUT_F1") (pintype "output"))
      (node (ref "E18") (pin "H1") (pinfunction "C_H1") (pintype "input"))
    )
    (net (code "925") (name "Net-(E17A-IN)") (class "Default")
      (node (ref "E17") (pin "E1") (pinfunction "IN_E1") (pintype "input"))
      (node (ref "E17") (pin "M2") (pinfunction "M2_M2") (pintype "output"))
    )
    (net (code "926") (name "Net-(E17E-IN)") (class "Default")
      (node (ref "E17") (pin "H1") (pinfunction "IN_H1") (pintype "input"))
      (node (ref "E17") (pin "U2") (pinfunction "U2_U2") (pintype "output"))
    )
    (net (code "927") (name "Net-(E18G-C)") (class "Default")
      (node (ref "E18") (pin "N1") (pinfunction "C_N1") (pintype "input"))
      (node (ref "E25") (pin "U1") (pinfunction "OUT_U1") (pintype "output"))
    )
    (net (code "928") (name "Net-(E18G-D)") (class "Default")
      (node (ref "E18") (pin "P1") (pinfunction "D_P1") (pintype "input"))
      (node (ref "E28") (pin "T2") (pinfunction "OUT_T2") (pintype "output"))
    )
    (net (code "929") (name "Net-(E20A-C)") (class "Default")
      (node (ref "E20") (pin "B1") (pinfunction "C_B1") (pintype "input"))
      (node (ref "E20") (pin "D2") (pinfunction "C_D2") (pintype "input"))
      (node (ref "E20") (pin "H1") (pinfunction "C_H1") (pintype "input"))
      (node (ref "E22") (pin "S1") (pinfunction "OUT_S1") (pintype "output"))
    )
    (net (code "930") (name "Net-(E20A-D)") (class "Default")
      (node (ref "E20") (pin "C1") (pinfunction "D_C1") (pintype "input"))
      (node (ref "F22") (pin "C1") (pinfunction "OUT_C1") (pintype "output"))
    )
    (net (code "931") (name "Net-(E20A-R)") (class "Default")
      (node (ref "E20") (pin "A1") (pinfunction "R_A1") (pintype "input"))
      (node (ref "E24") (pin "K2") (pinfunction "OUT_K2") (pintype "output"))
    )
    (net (code "932") (name "Net-(E23A-S)") (class "Default")
      (node (ref "E23") (pin "D1") (pinfunction "S_D1") (pintype "input"))
      (node (ref "F22") (pin "F2") (pinfunction "OUT_F2") (pintype "output"))
    )
    (net (code "933") (name "Net-(E24A-OUT)") (class "Default")
      (node (ref "E24") (pin "C1") (pinfunction "OUT_C1") (pintype "output"))
      (node (ref "E25") (pin "A1") (pinfunction "IN1_A1") (pintype "input"))
    )
    (net (code "934") (name "Net-(E24B-OUT)") (class "Default")
      (node (ref "E24") (pin "F1") (pinfunction "OUT_F1") (pintype "output"))
      (node (ref "F23") (pin "E2") (pinfunction "IN2_E2") (pintype "input"))
    )
    (net (code "935") (name "Net-(E24F-IN1)") (class "Default")
      (node (ref "E24") (pin "H1") (pinfunction "IN1_H1") (pintype "input"))
      (node (ref "E25") (pin "J1") (pinfunction "OUT_J1") (pintype "output"))
    )
    (net (code "936") (name "Net-(E24H-OUT)") (class "Default")
      (node (ref "E24") (pin "N1") (pinfunction "OUT_N1") (pintype "output"))
      (node (ref "E25") (pin "K1") (pinfunction "IN1_K1") (pintype "input"))
    )
    (net (code "937") (name "Net-(E24I-IN1)") (class "Default")
      (node (ref "E24") (pin "L2") (pinfunction "IN1_L2") (pintype "input"))
      (node (ref "F24") (pin "P2") (pinfunction "OUT_P2") (pintype "output"))
    )
    (net (code "938") (name "Net-(E24I-OUT)") (class "Default")
      (node (ref "E24") (pin "N2") (pinfunction "OUT_N2") (pintype "output"))
      (node (ref "F23") (pin "A1") (pinfunction "IN1_A1") (pintype "input"))
    )
    (net (code "939") (name "Net-(E24J-IN2)") (class "Default")
      (node (ref "E24") (pin "R1") (pinfunction "IN2_R1") (pintype "input"))
      (node (ref "F24") (pin "S1") (pinfunction "OUT_S1") (pintype "output"))
    )
    (net (code "940") (name "Net-(E24K-IN2)") (class "Default")
      (node (ref "E24") (pin "R2") (pinfunction "IN2_R2") (pintype "input"))
      (node (ref "F24") (pin "V2") (pinfunction "OUT_V2") (pintype "output"))
    )
    (net (code "941") (name "Net-(E24N-OUT)") (class "Default")
      (node (ref "E24") (pin "V2") (pinfunction "OUT_V2") (pintype "output"))
      (node (ref "E25") (pin "M1") (pinfunction "IN3_M1") (pintype "input"))
    )
    (net (code "942") (name "Net-(E25G-IN2)") (class "Default")
      (node (ref "E25") (pin "L1") (pinfunction "IN2_L1") (pintype "input"))
      (node (ref "F23") (pin "E1") (pinfunction "OUT_E1") (pintype "output"))
    )
    (net (code "943") (name "Net-(E25G-OUT)") (class "Default")
      (node (ref "E25") (pin "N1") (pinfunction "OUT_N1") (pintype "output"))
      (node (ref "E25") (pin "P2") (pinfunction "IN2_P2") (pintype "input"))
    )
    (net (code "944") (name "Net-(E25H-OUT)") (class "Default")
      (node (ref "E25") (pin "S2") (pinfunction "OUT_S2") (pintype "output"))
      (node (ref "E28") (pin "N2") (pinfunction "IN4A_N2") (pintype "input"))
      (node (ref "F25") (pin "L2") (pinfunction "IN1_L2") (pintype "input"))
    )
    (net (code "945") (name "Net-(E25I-IN1)") (class "Default")
      (node (ref "E25") (pin "P1") (pinfunction "IN1_P1") (pintype "input"))
      (node (ref "E25") (pin "V1") (pinfunction "OUT_V1") (pintype "output"))
    )
    (net (code "946") (name "Net-(E25I-IN3)") (class "Default")
      (node (ref "E25") (pin "S1") (pinfunction "IN3_S1") (pintype "input"))
      (node (ref "F25") (pin "V2") (pinfunction "OUT_V2") (pintype "output"))
    )
    (net (code "947") (name "Net-(E26C-OUT)") (class "Default")
      (node (ref "E26") (pin "R1") (pinfunction "OUT_R1") (pintype "output"))
      (node (ref "E32") (pin "F2") (pinfunction "IN3_F2") (pintype "input"))
    )
    (net (code "948") (name "Net-(E26D-IN1C)") (class "Default")
      (node (ref "E26") (pin "F2") (pinfunction "IN1C_F2") (pintype "input"))
      (node (ref "F26") (pin "V1") (pinfunction "OUT_V1") (pintype "output"))
    )
    (net (code "949") (name "Net-(E26D-OUT)") (class "Default")
      (node (ref "E26") (pin "T2") (pinfunction "OUT_T2") (pintype "output"))
      (node (ref "E32") (pin "L2") (pinfunction "IN2_L2") (pintype "input"))
    )
    (net (code "950") (name "Net-(E27C-IN4A)") (class "Default")
      (node (ref "E27") (pin "K1") (pinfunction "IN4A_K1") (pintype "input"))
      (node (ref "F11") (pin "S1") (pinfunction "OUT_S1") (pintype "output"))
    )
    (net (code "951") (name "Net-(E27C-OUT)") (class "Default")
      (node (ref "E27") (pin "R1") (pinfunction "OUT_R1") (pintype "output"))
      (node (ref "F27") (pin "L2") (pinfunction "IN2_L2") (pintype "input"))
    )
    (net (code "952") (name "Net-(E27D-OUT)") (class "Default")
      (node (ref "E27") (pin "T2") (pinfunction "OUT_T2") (pintype "output"))
      (node (ref "F27") (pin "M2") (pinfunction "IN3_M2") (pintype "input"))
    )
    (net (code "953") (name "Net-(E28D-IN3A)") (class "Default")
      (node (ref "E28") (pin "L2") (pinfunction "IN3A_L2") (pintype "input"))
      (node (ref "F25") (pin "N2") (pinfunction "OUT_N2") (pintype "output"))
    )
    (net (code "954") (name "Net-(E29C-IN2B)") (class "Default")
      (node (ref "E29") (pin "F1") (pinfunction "IN2B_F1") (pintype "input"))
      (node (ref "E29") (pin "T2") (pinfunction "OUT_T2") (pintype "output"))
    )
    (net (code "955") (name "Net-(E29C-OUT)") (class "Default")
      (node (ref "E29") (pin "R1") (pinfunction "OUT_R1") (pintype "output"))
      (node (ref "F31") (pin "B1") (pinfunction "IN2_B1") (pintype "input"))
    )
    (net (code "956") (name "Net-(E30C-OUT)") (class "Default")
      (node (ref "E30") (pin "R1") (pinfunction "OUT_R1") (pintype "output"))
      (node (ref "F31") (pin "H1") (pinfunction "IN2_H1") (pintype "input"))
      (node (ref "F31") (pin "K2") (pinfunction "IN1_K2") (pintype "input"))
    )
    (net (code "957") (name "Net-(E30D-IN3B)") (class "Default")
      (node (ref "E30") (pin "M2") (pinfunction "IN3B_M2") (pintype "input"))
      (node (ref "E30") (pin "V2") (pinfunction "OUT_V2") (pintype "output"))
    )
    (net (code "958") (name "Net-(E30D-OUT)") (class "Default")
      (node (ref "E30") (pin "T2") (pinfunction "OUT_T2") (pintype "output"))
      (node (ref "E32") (pin "N1") (pinfunction "IN2_N1") (pintype "input"))
    )
    (net (code "959") (name "Net-(E31A-IN1)") (class "Default")
      (node (ref "E31") (pin "A1") (pinfunction "IN1_A1") (pintype "input"))
      (node (ref "F26") (pin "H2") (pinfunction "OUT_H2") (pintype "output"))
    )
    (net (code "960") (name "Net-(E31D-IN4)") (class "Default")
      (node (ref "E31") (pin "H2") (pinfunction "IN4_H2") (pintype "input"))
      (node (ref "F26") (pin "D1") (pinfunction "OUT_D1") (pintype "output"))
    )
    (net (code "961") (name "Net-(E31E-IN3)") (class "Default")
      (node (ref "E31") (pin "J1") (pinfunction "IN3_J1") (pintype "input"))
      (node (ref "F26") (pin "J1") (pinfunction "OUT_J1") (pintype "output"))
    )
    (net (code "962") (name "Net-(E31F-IN3)") (class "Default")
      (node (ref "E31") (pin "M2") (pinfunction "IN3_M2") (pintype "input"))
      (node (ref "F26") (pin "M2") (pinfunction "OUT_M2") (pintype "output"))
    )
    (net (code "963") (name "Net-(E31G-IN1)") (class "Default")
      (node (ref "E31") (pin "M1") (pinfunction "IN1_M1") (pintype "input"))
      (node (ref "F26") (pin "N1") (pinfunction "OUT_N1") (pintype "output"))
    )
    (net (code "964") (name "Net-(E31G-IN2)") (class "Default")
      (node (ref "E31") (pin "N1") (pinfunction "IN2_N1") (pintype "input"))
      (node (ref "F24") (pin "E1") (pinfunction "OUT_E1") (pintype "output"))
    )
    (net (code "965") (name "Net-(E32A-IN1)") (class "Default")
      (node (ref "E32") (pin "A1") (pinfunction "IN1_A1") (pintype "input"))
      (node (ref "F32") (pin "F1") (pinfunction "OUT_F1") (pintype "output"))
    )
    (net (code "966") (name "Net-(E32A-IN4)") (class "Default")
      (node (ref "E32") (pin "D1") (pinfunction "IN4_D1") (pintype "input"))
      (node (ref "F32") (pin "F2") (pinfunction "OUT_F2") (pintype "output"))
    )
    (net (code "967") (name "Net-(E32D-IN2)") (class "Default")
      (node (ref "E32") (pin "E2") (pinfunction "IN2_E2") (pintype "input"))
      (node (ref "F32") (pin "N2") (pinfunction "OUT_N2") (pintype "output"))
    )
    (net (code "968") (name "Net-(E32D-IN4)") (class "Default")
      (node (ref "E32") (pin "H2") (pinfunction "IN4_H2") (pintype "input"))
      (node (ref "F26") (pin "S2") (pinfunction "OUT_S2") (pintype "output"))
    )
    (net (code "969") (name "Net-(E32E-IN4)") (class "Default")
      (node (ref "E32") (pin "K1") (pinfunction "IN4_K1") (pintype "input"))
      (node (ref "F32") (pin "K1") (pinfunction "OUT_K1") (pintype "output"))
    )
    (net (code "970") (name "Net-(E32I-IN3)") (class "Default")
      (node (ref "E32") (pin "T2") (pinfunction "IN3_T2") (pintype "input"))
      (node (ref "F32") (pin "K2") (pinfunction "OUT_K2") (pintype "output"))
    )
    (net (code "971") (name "Net-(E33A-S)") (class "Default")
      (node (ref "E33") (pin "D1") (pinfunction "S_D1") (pintype "input"))
      (node (ref "F20") (pin "C1") (pinfunction "OUT_C1") (pintype "output"))
    )
    (net (code "972") (name "Net-(E33D-D)") (class "Default")
      (node (ref "E33") (pin "E2") (pinfunction "D_E2") (pintype "input"))
      (node (ref "F21") (pin "C1") (pinfunction "OUT_C1") (pintype "output"))
    )
    (net (code "973") (name "Net-(E33E-D)") (class "Default")
      (node (ref "E33") (pin "J1") (pinfunction "D_J1") (pintype "input"))
      (node (ref "F11") (pin "V2") (pinfunction "OUT_V2") (pintype "output"))
    )
    (net (code "974") (name "Net-(E33F-C)") (class "Default")
      (node (ref "E33") (pin "L2") (pinfunction "C_L2") (pintype "input"))
      (node (ref "F21") (pin "F2") (pinfunction "OUT_F2") (pintype "output"))
    )
    (net (code "975") (name "Net-(E33G-C)") (class "Default")
      (node (ref "E33") (pin "N1") (pinfunction "C_N1") (pintype "input"))
      (node (ref "F21") (pin "K2") (pinfunction "OUT_K2") (pintype "output"))
    )
    (net (code "976") (name "Net-(E33H-D)") (class "Default")
      (node (ref "E33") (pin "T2") (pinfunction "D_T2") (pintype "input"))
      (node (ref "F33") (pin "R1") (pinfunction "OUT_R1") (pintype "output"))
    )
    (net (code "977") (name "Net-(EF10C-CS2)") (class "Default")
      (node (ref "EF10") (pin "AS2") (pinfunction "CS2_AS2") (pintype "input"))
      (node (ref "F19") (pin "J2") (pinfunction "OUT_J2") (pintype "output"))
    )
    (net (code "978") (name "Net-(EF34-PadBJ1)") (class "Default")
      (node (ref "EF34") (pin "BJ1") (pinfunction "BJ1_BJ1") (pintype "input"))
      (node (ref "EF35") (pin "BK2") (pinfunction "BK2_BK2") (pintype "output"))
    )
    (net (code "979") (name "Net-(EF35-PadBJ1)") (class "Default")
      (node (ref "EF35") (pin "BJ1") (pinfunction "BJ1_BJ1") (pintype "input"))
      (node (ref "EF36") (pin "BK2") (pinfunction "BK2_BK2") (pintype "output"))
    )
    (net (code "980") (name "Net-(EF37-PadBJ1)") (class "Default")
      (node (ref "EF37") (pin "BJ1") (pinfunction "BJ1_BJ1") (pintype "input"))
      (node (ref "EF38") (pin "BK2") (pinfunction "BK2_BK2") (pintype "output"))
    )
    (net (code "981") (name "Net-(EF38-PadBJ1)") (class "Default")
      (node (ref "EF38") (pin "BJ1") (pinfunction "BJ1_BJ1") (pintype "input"))
      (node (ref "EF39") (pin "BK2") (pinfunction "BK2_BK2") (pintype "output"))
    )
    (net (code "982") (name "Net-(F11F-IN3)") (class "Default")
      (node (ref "F11") (pin "M2") (pinfunction "IN3_M2") (pintype "input"))
      (node (ref "F27") (pin "E1") (pinfunction "OUT_E1") (pintype "output"))
      (node (ref "F31") (pin "E2") (pinfunction "IN2_E2") (pintype "input"))
    )
    (net (code "983") (name "Net-(F11F-IN4)") (class "Default")
      (node (ref "F11") (pin "N2") (pinfunction "IN4_N2") (pintype "input"))
      (node (ref "F27") (pin "J2") (pinfunction "OUT_J2") (pintype "output"))
      (node (ref "F31") (pin "H2") (pinfunction "IN4_H2") (pintype "input"))
    )
    (net (code "984") (name "Net-(F12A-IN)") (class "Default")
      (node (ref "F12") (pin "E1") (pinfunction "IN_E1") (pintype "input"))
      (node (ref "F12") (pin "T2") (pinfunction "T2_T2") (pintype "output"))
    )
    (net (code "985") (name "Net-(F13A-IN)") (class "Default")
      (node (ref "F13") (pin "E1") (pinfunction "IN_E1") (pintype "input"))
      (node (ref "F13") (pin "T2") (pinfunction "T2_T2") (pintype "output"))
    )
    (net (code "986") (name "Net-(F13A-OUT)") (class "Default")
      (node (ref "F13") (pin "F1") (pinfunction "OUT_F1") (pintype "output"))
      (node (ref "F14") (pin "H2") (pinfunction "H2_H2") (pintype "input"))
    )
    (net (code "987") (name "Net-(F13E-IN)") (class "Default")
      (node (ref "F13") (pin "H1") (pinfunction "IN_H1") (pintype "input"))
      (node (ref "F13") (pin "M2") (pinfunction "M2_M2") (pintype "output"))
    )
    (net (code "988") (name "Net-(F13E-OUT)") (class "Default")
      (node (ref "F13") (pin "J1") (pinfunction "OUT_J1") (pintype "output"))
      (node (ref "F20") (pin "D2") (pinfunction "IN1_D2") (pintype "input"))
    )
    (net (code "989") (name "Net-(F14A-IN)") (class "Default")
      (node (ref "F14") (pin "E1") (pinfunction "IN_E1") (pintype "input"))
      (node (ref "F14") (pin "T2") (pinfunction "T2_T2") (pintype "output"))
    )
    (net (code "990") (name "Net-(F14A-OUT)") (class "Default")
      (node (ref "F14") (pin "F1") (pinfunction "OUT_F1") (pintype "output"))
      (node (ref "F15") (pin "H2") (pinfunction "H2_H2") (pintype "input"))
    )
    (net (code "991") (name "Net-(F14E-IN)") (class "Default")
      (node (ref "F14") (pin "H1") (pinfunction "IN_H1") (pintype "input"))
      (node (ref "F14") (pin "S2") (pinfunction "S2_S2") (pintype "output"))
    )
    (net (code "992") (name "Net-(F15A-IN)") (class "Default")
      (node (ref "F15") (pin "E1") (pinfunction "IN_E1") (pintype "input"))
      (node (ref "F15") (pin "T2") (pinfunction "T2_T2") (pintype "output"))
    )
    (net (code "993") (name "Net-(F15E-IN)") (class "Default")
      (node (ref "F15") (pin "H1") (pinfunction "IN_H1") (pintype "input"))
      (node (ref "F15") (pin "M2") (pinfunction "M2_M2") (pintype "output"))
    )
    (net (code "994") (name "Net-(F15E-OUT)") (class "Default")
      (node (ref "F15") (pin "J1") (pinfunction "OUT_J1") (pintype "output"))
      (node (ref "F20") (pin "H1") (pinfunction "IN1_H1") (pintype "input"))
    )
    (net (code "995") (name "Net-(F16A-IN)") (class "Default")
      (node (ref "F16") (pin "E1") (pinfunction "IN_E1") (pintype "input"))
      (node (ref "F16") (pin "T2") (pinfunction "T2_T2") (pintype "output"))
    )
    (net (code "996") (name "Net-(F16A-OUT)") (class "Default")
      (node (ref "F16") (pin "F1") (pinfunction "OUT_F1") (pintype "output"))
      (node (ref "F17") (pin "H2") (pinfunction "H2_H2") (pintype "input"))
    )
    (net (code "997") (name "Net-(F16E-IN)") (class "Default")
      (node (ref "F16") (pin "H1") (pinfunction "IN_H1") (pintype "input"))
      (node (ref "F16") (pin "S2") (pinfunction "S2_S2") (pintype "output"))
    )
    (net (code "998") (name "Net-(F17A-IN)") (class "Default")
      (node (ref "F17") (pin "E1") (pinfunction "IN_E1") (pintype "input"))
      (node (ref "F17") (pin "T2") (pinfunction "T2_T2") (pintype "output"))
    )
    (net (code "999") (name "Net-(F17E-IN)") (class "Default")
      (node (ref "F17") (pin "H1") (pinfunction "IN_H1") (pintype "input"))
      (node (ref "F17") (pin "M2") (pinfunction "M2_M2") (pintype "output"))
    )
    (net (code "1000") (name "Net-(F17E-OUT)") (class "Default")
      (node (ref "F17") (pin "J1") (pinfunction "OUT_J1") (pintype "output"))
      (node (ref "F20") (pin "H2") (pinfunction "IN1_H2") (pintype "input"))
    )
    (net (code "1001") (name "Net-(F18A-IN)") (class "Default")
      (node (ref "F18") (pin "E1") (pinfunction "IN_E1") (pintype "input"))
      (node (ref "F18") (pin "T2") (pinfunction "T2_T2") (pintype "output"))
    )
    (net (code "1002") (name "Net-(F18E-IN)") (class "Default")
      (node (ref "F18") (pin "H1") (pinfunction "IN_H1") (pintype "input"))
      (node (ref "F18") (pin "S2") (pinfunction "S2_S2") (pintype "output"))
    )
    (net (code "1003") (name "Net-(F19A-IN1)") (class "Default")
      (node (ref "F19") (pin "A1") (pinfunction "IN1_A1") (pintype "input"))
      (node (ref "F20") (pin "N1") (pinfunction "OUT_N1") (pintype "output"))
    )
    (net (code "1004") (name "Net-(F19E-IN2)") (class "Default")
      (node (ref "F19") (pin "H1") (pinfunction "IN2_H1") (pintype "input"))
      (node (ref "F21") (pin "N2") (pinfunction "OUT_N2") (pintype "output"))
    )
    (net (code "1005") (name "Net-(F19E-OUT)") (class "Default")
      (node (ref "F19") (pin "L1") (pinfunction "OUT_L1") (pintype "output"))
      (node (ref "F21") (pin "H2") (pinfunction "IN1_H2") (pintype "input"))
    )
    (net (code "1006") (name "Net-(F19J-OUT)") (class "Default")
      (node (ref "F19") (pin "V2") (pinfunction "OUT_V2") (pintype "output"))
      (node (ref "F21") (pin "P1") (pinfunction "IN1_P1") (pintype "input"))
    )
    (net (code "1007") (name "Net-(F20A-IN2)") (class "Default")
      (node (ref "F20") (pin "B1") (pinfunction "IN2_B1") (pintype "input"))
      (node (ref "F20") (pin "F1") (pinfunction "OUT_F1") (pintype "output"))
    )
    (net (code "1008") (name "Net-(F20H-IN1)") (class "Default")
      (node (ref "F20") (pin "L1") (pinfunction "IN1_L1") (pintype "input"))
      (node (ref "F20") (pin "S1") (pinfunction "OUT_S1") (pintype "output"))
    )
    (net (code "1009") (name "Net-(F20I-OUT)") (class "Default")
      (node (ref "F20") (pin "N2") (pinfunction "OUT_N2") (pintype "output"))
      (node (ref "F30") (pin "A1") (pinfunction "IN1_A1") (pintype "input"))
    )
    (net (code "1010") (name "Net-(F20K-IN1)") (class "Default")
      (node (ref "F20") (pin "P2") (pinfunction "IN1_P2") (pintype "input"))
      (node (ref "F20") (pin "V2") (pinfunction "OUT_V2") (pintype "output"))
    )
    (net (code "1011") (name "Net-(F21C-IN1)") (class "Default")
      (node (ref "F21") (pin "D2") (pinfunction "IN1_D2") (pintype "input"))
      (node (ref "F21") (pin "K1") (pinfunction "OUT_K1") (pintype "output"))
    )
    (net (code "1012") (name "Net-(F21K-IN2)") (class "Default")
      (node (ref "F21") (pin "R2") (pinfunction "IN2_R2") (pintype "input"))
      (node (ref "F23") (pin "V2") (pinfunction "OUT_V2") (pintype "output"))
    )
    (net (code "1013") (name "Net-(F22J-OUT)") (class "Default")
      (node (ref "F22") (pin "P2") (pinfunction "IN1_P2") (pintype "input"))
      (node (ref "F22") (pin "S1") (pinfunction "OUT_S1") (pintype "output"))
    )
    (net (code "1014") (name "Net-(F23D-IN3)") (class "Default")
      (node (ref "F23") (pin "F2") (pinfunction "IN3_F2") (pintype "input"))
      (node (ref "F23") (pin "L1") (pinfunction "OUT_L1") (pintype "output"))
    )
    (net (code "1015") (name "Net-(F24D-OUT)") (class "Default")
      (node (ref "F24") (pin "J2") (pinfunction "OUT_J2") (pintype "output"))
      (node (ref "F25") (pin "D2") (pinfunction "IN1_D2") (pintype "input"))
    )
    (net (code "1016") (name "Net-(F24E-OUT)") (class "Default")
      (node (ref "F24") (pin "L1") (pinfunction "OUT_L1") (pintype "output"))
      (node (ref "F25") (pin "H1") (pinfunction "IN1_H1") (pintype "input"))
    )
    (net (code "1017") (name "Net-(F25C-OUT)") (class "Default")
      (node (ref "F25") (pin "F2") (pinfunction "OUT_F2") (pintype "output"))
      (node (ref "F27") (pin "M1") (pinfunction "IN1_M1") (pintype "input"))
    )
    (net (code "1018") (name "Net-(F25F-OUT)") (class "Default")
      (node (ref "F25") (pin "K1") (pinfunction "OUT_K1") (pintype "output"))
      (node (ref "F27") (pin "N1") (pinfunction "IN2_N1") (pintype "input"))
    )
    (net (code "1019") (name "Net-(F25G-IN1)") (class "Default")
      (node (ref "F25") (pin "H2") (pinfunction "IN1_H2") (pintype "input"))
      (node (ref "F25") (pin "N1") (pinfunction "OUT_N1") (pintype "output"))
    )
    (net (code "1020") (name "Net-(F25G-OUT)") (class "Default")
      (node (ref "F25") (pin "K2") (pinfunction "OUT_K2") (pintype "output"))
      (node (ref "F27") (pin "P1") (pinfunction "IN3_P1") (pintype "input"))
    )
    (net (code "1021") (name "Net-(F27D-IN2)") (class "Default")
      (node (ref "F27") (pin "E2") (pinfunction "IN2_E2") (pintype "input"))
      (node (ref "F29") (pin "F1") (pinfunction "OUT_F1") (pintype "output"))
    )
    (net (code "1022") (name "Net-(F27E-OUT)") (class "Default")
      (node (ref "F27") (pin "L1") (pinfunction "OUT_L1") (pintype "output"))
      (node (ref "F29") (pin "J1") (pinfunction "IN2_J1") (pintype "input"))
    )
    (net (code "1023") (name "Net-(F27F-OUT)") (class "Default")
      (node (ref "F27") (pin "P2") (pinfunction "OUT_P2") (pintype "output"))
      (node (ref "F32") (pin "A1") (pinfunction "IN1_A1") (pintype "input"))
    )
    (net (code "1024") (name "Net-(F28D-OUT)") (class "Default")
      (node (ref "F28") (pin "H2") (pinfunction "OUT_H2") (pintype "output"))
      (node (ref "F31") (pin "F1") (pinfunction "IN1_F1") (pintype "input"))
    )
    (net (code "1025") (name "Net-(F28F-OUT)") (class "Default")
      (node (ref "F28") (pin "M2") (pinfunction "OUT_M2") (pintype "output"))
      (node (ref "F32") (pin "M1") (pinfunction "IN2_M1") (pintype "input"))
    )
    (net (code "1026") (name "Net-(F28G-OUT)") (class "Default")
      (node (ref "F28") (pin "N1") (pinfunction "OUT_N1") (pintype "output"))
      (node (ref "F30") (pin "F1") (pinfunction "IN1_F1") (pintype "input"))
    )
    (net (code "1027") (name "Net-(F28I-OUT)") (class "Default")
      (node (ref "F28") (pin "U1") (pinfunction "OUT_U1") (pintype "output"))
      (node (ref "F33") (pin "A1") (pinfunction "IN1A_A1") (pintype "input"))
    )
    (net (code "1028") (name "Net-(F29H-OUT)") (class "Default")
      (node (ref "F29") (pin "N1") (pinfunction "OUT_N1") (pintype "output"))
      (node (ref "F30") (pin "K2") (pinfunction "IN1_K2") (pintype "input"))
    )
    (net (code "1029") (name "Net-(F29I-IN1)") (class "Default")
      (node (ref "F29") (pin "L2") (pinfunction "IN1_L2") (pintype "input"))
      (node (ref "F29") (pin "V2") (pinfunction "OUT_V2") (pintype "output"))
    )
    (net (code "1030") (name "Net-(F29J-OUT)") (class "Default")
      (node (ref "F29") (pin "S1") (pinfunction "OUT_S1") (pintype "output"))
      (node (ref "F30") (pin "M1") (pinfunction "IN1_M1") (pintype "input"))
    )
    (net (code "1031") (name "Net-(F32K-IN2)") (class "Default")
      (node (ref "F32") (pin "R2") (pinfunction "IN2_R2") (pintype "input"))
      (node (ref "F33") (pin "S1") (pinfunction "IN1A_S1") (pintype "input"))
      (node (ref "F33") (pin "T2") (pinfunction "OUT_T2") (pintype "output"))
    )
    (net (code "1032") (name "Net-(F32K-OUT)") (class "Default")
      (node (ref "F32") (pin "S2") (pinfunction "OUT_S2") (pintype "output"))
      (node (ref "F33") (pin "V1") (pinfunction "IN2A_V1") (pintype "input"))
    )
    (net (code "1033") (name "Net-(H07A-OUT)") (class "Default")
      (node (ref "H07") (pin "D2") (pinfunction "OUT_D2") (pintype "output"))
      (node (ref "J01") (pin "D2") (pinfunction "P$2_D2") (pintype "bidirectional"))
    )
    (net (code "1034") (name "Net-(H07B-OUT)") (class "Default")
      (node (ref "H07") (pin "K2") (pinfunction "OUT_K2") (pintype "output"))
      (node (ref "J01") (pin "E2") (pinfunction "P$2_E2") (pintype "bidirectional"))
    )
    (net (code "1035") (name "Net-(H07C-OUT)") (class "Default")
      (node (ref "H07") (pin "S2") (pinfunction "OUT_S2") (pintype "output"))
      (node (ref "J01") (pin "H2") (pinfunction "P$2_H2") (pintype "bidirectional"))
    )
    (net (code "1036") (name "Net-(H08A-OUT)") (class "Default")
      (node (ref "H08") (pin "D2") (pinfunction "OUT_D2") (pintype "output"))
      (node (ref "J01") (pin "K2") (pinfunction "P$2_K2") (pintype "bidirectional"))
    )
    (net (code "1037") (name "Net-(H08B-OUT)") (class "Default")
      (node (ref "H08") (pin "K2") (pinfunction "OUT_K2") (pintype "output"))
      (node (ref "J01") (pin "M2") (pinfunction "P$2_M2") (pintype "bidirectional"))
    )
    (net (code "1038") (name "Net-(H08C-OUT)") (class "Default")
      (node (ref "H08") (pin "S2") (pinfunction "OUT_S2") (pintype "output"))
      (node (ref "J01") (pin "P2") (pinfunction "P$2_P2") (pintype "bidirectional"))
    )
    (net (code "1039") (name "Net-(H09A-OUT)") (class "Default")
      (node (ref "H09") (pin "D2") (pinfunction "OUT_D2") (pintype "output"))
      (node (ref "J01") (pin "S2") (pinfunction "P$2_S2") (pintype "bidirectional"))
    )
    (net (code "1040") (name "Net-(H09B-OUT)") (class "Default")
      (node (ref "H09") (pin "K2") (pinfunction "OUT_K2") (pintype "output"))
      (node (ref "J01") (pin "T2") (pinfunction "P$2_T2") (pintype "bidirectional"))
    )
    (net (code "1041") (name "Net-(H09C-OUT)") (class "Default")
      (node (ref "H09") (pin "S2") (pinfunction "OUT_S2") (pintype "output"))
      (node (ref "J01") (pin "V2") (pinfunction "P$2_V2") (pintype "bidirectional"))
    )
    (net (code "1042") (name "Net-(H10A-OUT)") (class "Default")
      (node (ref "H10") (pin "D2") (pinfunction "OUT_D2") (pintype "output"))
      (node (ref "J02") (pin "D2") (pinfunction "P$2_D2") (pintype "bidirectional"))
    )
    (net (code "1043") (name "Net-(H10B-OUT)") (class "Default")
      (node (ref "H10") (pin "K2") (pinfunction "OUT_K2") (pintype "output"))
      (node (ref "J02") (pin "E2") (pinfunction "P$2_E2") (pintype "bidirectional"))
    )
    (net (code "1044") (name "Net-(H10C-OUT)") (class "Default")
      (node (ref "H10") (pin "S2") (pinfunction "OUT_S2") (pintype "output"))
      (node (ref "J02") (pin "H2") (pinfunction "P$2_H2") (pintype "bidirectional"))
    )
    (net (code "1045") (name "Net-(H11A-OUT)") (class "Default")
      (node (ref "H11") (pin "D2") (pinfunction "OUT_D2") (pintype "output"))
      (node (ref "J02") (pin "K2") (pinfunction "P$2_K2") (pintype "bidirectional"))
    )
    (net (code "1046") (name "Net-(H11B-OUT)") (class "Default")
      (node (ref "H11") (pin "K2") (pinfunction "OUT_K2") (pintype "output"))
      (node (ref "J02") (pin "M2") (pinfunction "P$2_M2") (pintype "bidirectional"))
    )
    (net (code "1047") (name "Net-(H11C-OUT)") (class "Default")
      (node (ref "H11") (pin "S2") (pinfunction "OUT_S2") (pintype "output"))
      (node (ref "J02") (pin "P2") (pinfunction "P$2_P2") (pintype "bidirectional"))
    )
    (net (code "1048") (name "Net-(H12A-OUT)") (class "Default")
      (node (ref "H12") (pin "D2") (pinfunction "OUT_D2") (pintype "output"))
      (node (ref "J02") (pin "S2") (pinfunction "P$2_S2") (pintype "bidirectional"))
    )
    (net (code "1049") (name "Net-(H12B-OUT)") (class "Default")
      (node (ref "H12") (pin "K2") (pinfunction "OUT_K2") (pintype "output"))
      (node (ref "J02") (pin "T2") (pinfunction "P$2_T2") (pintype "bidirectional"))
    )
    (net (code "1050") (name "Net-(H12C-OUT)") (class "Default")
      (node (ref "H12") (pin "S2") (pinfunction "OUT_S2") (pintype "output"))
      (node (ref "J02") (pin "V2") (pinfunction "P$2_V2") (pintype "bidirectional"))
    )
    (net (code "1051") (name "Net-(H13A-OUT)") (class "Default")
      (node (ref "H13") (pin "D2") (pinfunction "OUT_D2") (pintype "output"))
      (node (ref "J03") (pin "D2") (pinfunction "P$2_D2") (pintype "bidirectional"))
    )
    (net (code "1052") (name "Net-(H13B-OUT)") (class "Default")
      (node (ref "H13") (pin "K2") (pinfunction "OUT_K2") (pintype "output"))
      (node (ref "J03") (pin "E2") (pinfunction "P$2_E2") (pintype "bidirectional"))
    )
    (net (code "1053") (name "Net-(H13C-OUT)") (class "Default")
      (node (ref "H13") (pin "S2") (pinfunction "OUT_S2") (pintype "output"))
      (node (ref "J03") (pin "H2") (pinfunction "P$2_H2") (pintype "bidirectional"))
    )
    (net (code "1054") (name "Net-(H14A-OUT)") (class "Default")
      (node (ref "H14") (pin "D2") (pinfunction "OUT_D2") (pintype "output"))
      (node (ref "J03") (pin "K2") (pinfunction "P$2_K2") (pintype "bidirectional"))
    )
    (net (code "1055") (name "Net-(H14B-OUT)") (class "Default")
      (node (ref "H14") (pin "K2") (pinfunction "OUT_K2") (pintype "output"))
      (node (ref "J03") (pin "M2") (pinfunction "P$2_M2") (pintype "bidirectional"))
    )
    (net (code "1056") (name "Net-(H14C-OUT)") (class "Default")
      (node (ref "H14") (pin "S2") (pinfunction "OUT_S2") (pintype "output"))
      (node (ref "J03") (pin "P2") (pinfunction "P$2_P2") (pintype "bidirectional"))
    )
    (net (code "1057") (name "Net-(H15A-OUT)") (class "Default")
      (node (ref "H15") (pin "D2") (pinfunction "OUT_D2") (pintype "output"))
      (node (ref "J03") (pin "S2") (pinfunction "P$2_S2") (pintype "bidirectional"))
    )
    (net (code "1058") (name "Net-(H15B-OUT)") (class "Default")
      (node (ref "H15") (pin "K2") (pinfunction "OUT_K2") (pintype "output"))
      (node (ref "J03") (pin "T2") (pinfunction "P$2_T2") (pintype "bidirectional"))
    )
    (net (code "1059") (name "Net-(H15C-OUT)") (class "Default")
      (node (ref "H15") (pin "S2") (pinfunction "OUT_S2") (pintype "output"))
      (node (ref "J03") (pin "V2") (pinfunction "P$2_V2") (pintype "bidirectional"))
    )
    (net (code "1060") (name "Net-(H16A-OUT)") (class "Default")
      (node (ref "H16") (pin "D2") (pinfunction "OUT_D2") (pintype "output"))
      (node (ref "J04") (pin "D2") (pinfunction "P$2_D2") (pintype "bidirectional"))
    )
    (net (code "1061") (name "Net-(H16B-OUT)") (class "Default")
      (node (ref "H16") (pin "K2") (pinfunction "OUT_K2") (pintype "output"))
      (node (ref "J04") (pin "E2") (pinfunction "P$2_E2") (pintype "bidirectional"))
    )
    (net (code "1062") (name "Net-(H16C-OUT)") (class "Default")
      (node (ref "H16") (pin "S2") (pinfunction "OUT_S2") (pintype "output"))
      (node (ref "J04") (pin "H2") (pinfunction "P$2_H2") (pintype "bidirectional"))
    )
    (net (code "1063") (name "Net-(H17A-OUT)") (class "Default")
      (node (ref "H17") (pin "D2") (pinfunction "OUT_D2") (pintype "output"))
      (node (ref "J04") (pin "K2") (pinfunction "P$2_K2") (pintype "bidirectional"))
    )
    (net (code "1064") (name "Net-(H17B-OUT)") (class "Default")
      (node (ref "H17") (pin "K2") (pinfunction "OUT_K2") (pintype "output"))
      (node (ref "J04") (pin "M2") (pinfunction "P$2_M2") (pintype "bidirectional"))
    )
    (net (code "1065") (name "Net-(H17C-OUT)") (class "Default")
      (node (ref "H17") (pin "S2") (pinfunction "OUT_S2") (pintype "output"))
      (node (ref "J04") (pin "P2") (pinfunction "P$2_P2") (pintype "bidirectional"))
    )
    (net (code "1066") (name "Net-(H18A-OUT)") (class "Default")
      (node (ref "H18") (pin "D2") (pinfunction "OUT_D2") (pintype "output"))
      (node (ref "J04") (pin "S2") (pinfunction "P$2_S2") (pintype "bidirectional"))
    )
    (net (code "1067") (name "Net-(H18B-OUT)") (class "Default")
      (node (ref "H18") (pin "K2") (pinfunction "OUT_K2") (pintype "output"))
      (node (ref "J04") (pin "T2") (pinfunction "P$2_T2") (pintype "bidirectional"))
    )
    (net (code "1068") (name "Net-(H18C-OUT)") (class "Default")
      (node (ref "H18") (pin "S2") (pinfunction "OUT_S2") (pintype "output"))
      (node (ref "J04") (pin "V2") (pinfunction "P$2_V2") (pintype "bidirectional"))
    )
    (net (code "1069") (name "Net-(H19A-OUT)") (class "Default")
      (node (ref "H19") (pin "D2") (pinfunction "OUT_D2") (pintype "output"))
      (node (ref "J06") (pin "S2") (pinfunction "P$2_S2") (pintype "bidirectional"))
    )
    (net (code "1070") (name "Net-(H19B-OUT)") (class "Default")
      (node (ref "H19") (pin "K2") (pinfunction "OUT_K2") (pintype "output"))
      (node (ref "J06") (pin "T2") (pinfunction "P$2_T2") (pintype "bidirectional"))
    )
    (net (code "1071") (name "Net-(H19C-OUT)") (class "Default")
      (node (ref "H19") (pin "S2") (pinfunction "OUT_S2") (pintype "output"))
      (node (ref "J10") (pin "P2") (pinfunction "P$2_P2") (pintype "bidirectional"))
    )
    (net (code "1072") (name "Net-(H20A-OUT)") (class "Default")
      (node (ref "H20") (pin "D2") (pinfunction "OUT_D2") (pintype "output"))
      (node (ref "J08") (pin "P2") (pinfunction "P$2_P2") (pintype "bidirectional"))
    )
    (net (code "1073") (name "Net-(H20B-OUT)") (class "Default")
      (node (ref "H20") (pin "K2") (pinfunction "OUT_K2") (pintype "output"))
      (node (ref "J08") (pin "S2") (pinfunction "P$2_S2") (pintype "bidirectional"))
    )
    (net (code "1074") (name "Net-(HJ28-PadAU1)") (class "Default")
      (node (ref "HJ28") (pin "AU1") (pinfunction "AU1_AU1") (pintype "input"))
      (node (ref "HJ28") (pin "BV1") (pinfunction "BV1_BV1") (pintype "output"))
    )
    (net (code "1075") (name "Net-(J05A-P$2)") (class "Default")
      (node (ref "J05") (pin "D2") (pinfunction "P$2_D2") (pintype "bidirectional"))
      (node (ref "J13") (pin "A1") (pinfunction "IN_A1") (pintype "input"))
    )
    (net (code "1076") (name "Net-(J05B-P$2)") (class "Default")
      (node (ref "J05") (pin "E2") (pinfunction "P$2_E2") (pintype "bidirectional"))
      (node (ref "J13") (pin "D2") (pinfunction "IN_D2") (pintype "input"))
    )
    (net (code "1077") (name "Net-(J05J-P$2)") (class "Default")
      (node (ref "J05") (pin "H2") (pinfunction "P$2_H2") (pintype "bidirectional"))
      (node (ref "J13") (pin "F1") (pinfunction "IN_F1") (pintype "input"))
    )
    (net (code "1078") (name "Net-(J05K-P$2)") (class "Default")
      (node (ref "J05") (pin "K2") (pinfunction "P$2_K2") (pintype "bidirectional"))
      (node (ref "J13") (pin "K2") (pinfunction "IN_K2") (pintype "input"))
    )
    (net (code "1079") (name "Net-(J05L-P$2)") (class "Default")
      (node (ref "J05") (pin "M2") (pinfunction "P$2_M2") (pintype "bidirectional"))
      (node (ref "J13") (pin "M1") (pinfunction "IN_M1") (pintype "input"))
    )
    (net (code "1080") (name "Net-(J05M-P$2)") (class "Default")
      (node (ref "J05") (pin "P2") (pinfunction "P$2_P2") (pintype "bidirectional"))
      (node (ref "J13") (pin "R2") (pinfunction "IN_R2") (pintype "input"))
    )
    (net (code "1081") (name "Net-(J05N-P$2)") (class "Default")
      (node (ref "J05") (pin "S2") (pinfunction "P$2_S2") (pintype "bidirectional"))
      (node (ref "J14") (pin "A1") (pinfunction "IN_A1") (pintype "input"))
    )
    (net (code "1082") (name "Net-(J05O-P$2)") (class "Default")
      (node (ref "J05") (pin "T2") (pinfunction "P$2_T2") (pintype "bidirectional"))
      (node (ref "J14") (pin "D2") (pinfunction "IN_D2") (pintype "input"))
    )
    (net (code "1083") (name "Net-(J05P-P$2)") (class "Default")
      (node (ref "J05") (pin "V2") (pinfunction "P$2_V2") (pintype "bidirectional"))
      (node (ref "J14") (pin "F1") (pinfunction "IN_F1") (pintype "input"))
    )
    (net (code "1084") (name "Net-(J06A-P$2)") (class "Default")
      (node (ref "J06") (pin "D2") (pinfunction "P$2_D2") (pintype "bidirectional"))
      (node (ref "J14") (pin "K2") (pinfunction "IN_K2") (pintype "input"))
    )
    (net (code "1085") (name "Net-(J06B-P$2)") (class "Default")
      (node (ref "J06") (pin "E2") (pinfunction "P$2_E2") (pintype "bidirectional"))
      (node (ref "J14") (pin "M1") (pinfunction "IN_M1") (pintype "input"))
    )
    (net (code "1086") (name "Net-(J06J-P$2)") (class "Default")
      (node (ref "J06") (pin "H2") (pinfunction "P$2_H2") (pintype "bidirectional"))
      (node (ref "J14") (pin "R2") (pinfunction "IN_R2") (pintype "input"))
    )
    (net (code "1087") (name "Net-(J06K-P$2)") (class "Default")
      (node (ref "J06") (pin "K2") (pinfunction "P$2_K2") (pintype "bidirectional"))
      (node (ref "J15") (pin "A1") (pinfunction "IN_A1") (pintype "input"))
    )
    (net (code "1088") (name "Net-(J06L-P$2)") (class "Default")
      (node (ref "J06") (pin "M2") (pinfunction "P$2_M2") (pintype "bidirectional"))
      (node (ref "J15") (pin "D2") (pinfunction "IN_D2") (pintype "input"))
    )
    (net (code "1089") (name "Net-(J06M-P$2)") (class "Default")
      (node (ref "J06") (pin "P2") (pinfunction "P$2_P2") (pintype "bidirectional"))
      (node (ref "J15") (pin "F1") (pinfunction "IN_F1") (pintype "input"))
    )
    (net (code "1090") (name "Net-(J06P-P$2)") (class "Default")
      (node (ref "J06") (pin "V2") (pinfunction "P$2_V2") (pintype "bidirectional"))
      (node (ref "J15") (pin "K2") (pinfunction "IN_K2") (pintype "input"))
    )
    (net (code "1091") (name "Net-(J07A-P$2)") (class "Default")
      (node (ref "J07") (pin "D2") (pinfunction "P$2_D2") (pintype "bidirectional"))
      (node (ref "J16") (pin "A1") (pinfunction "IN_A1") (pintype "input"))
    )
    (net (code "1092") (name "Net-(J07B-P$2)") (class "Default")
      (node (ref "J07") (pin "E2") (pinfunction "P$2_E2") (pintype "bidirectional"))
      (node (ref "J16") (pin "D2") (pinfunction "IN_D2") (pintype "input"))
    )
    (net (code "1093") (name "Net-(J07J-P$2)") (class "Default")
      (node (ref "J07") (pin "H2") (pinfunction "P$2_H2") (pintype "bidirectional"))
      (node (ref "J16") (pin "F1") (pinfunction "IN_F1") (pintype "input"))
    )
    (net (code "1094") (name "Net-(J07K-P$2)") (class "Default")
      (node (ref "J07") (pin "K2") (pinfunction "P$2_K2") (pintype "bidirectional"))
      (node (ref "J16") (pin "K2") (pinfunction "IN_K2") (pintype "input"))
    )
    (net (code "1095") (name "Net-(J07L-P$2)") (class "Default")
      (node (ref "J07") (pin "M2") (pinfunction "P$2_M2") (pintype "bidirectional"))
      (node (ref "J16") (pin "M1") (pinfunction "IN_M1") (pintype "input"))
    )
    (net (code "1096") (name "Net-(J07M-P$2)") (class "Default")
      (node (ref "J07") (pin "P2") (pinfunction "P$2_P2") (pintype "bidirectional"))
      (node (ref "J16") (pin "R2") (pinfunction "IN_R2") (pintype "input"))
    )
    (net (code "1097") (name "Net-(J07N-P$2)") (class "Default")
      (node (ref "J07") (pin "S2") (pinfunction "P$2_S2") (pintype "bidirectional"))
      (node (ref "J17") (pin "A1") (pinfunction "IN_A1") (pintype "input"))
    )
    (net (code "1098") (name "Net-(J07O-P$2)") (class "Default")
      (node (ref "J07") (pin "T2") (pinfunction "P$2_T2") (pintype "bidirectional"))
      (node (ref "J17") (pin "D2") (pinfunction "IN_D2") (pintype "input"))
    )
    (net (code "1099") (name "Net-(J07P-P$2)") (class "Default")
      (node (ref "J07") (pin "V2") (pinfunction "P$2_V2") (pintype "bidirectional"))
      (node (ref "J17") (pin "F1") (pinfunction "IN_F1") (pintype "input"))
    )
    (net (code "1100") (name "Net-(J08A-P$2)") (class "Default")
      (node (ref "J08") (pin "D2") (pinfunction "P$2_D2") (pintype "bidirectional"))
      (node (ref "J17") (pin "K2") (pinfunction "IN_K2") (pintype "input"))
    )
    (net (code "1101") (name "Net-(J08B-P$2)") (class "Default")
      (node (ref "J08") (pin "E2") (pinfunction "P$2_E2") (pintype "bidirectional"))
      (node (ref "J17") (pin "M1") (pinfunction "IN_M1") (pintype "input"))
    )
    (net (code "1102") (name "Net-(J08J-P$2)") (class "Default")
      (node (ref "J08") (pin "H2") (pinfunction "P$2_H2") (pintype "bidirectional"))
      (node (ref "J17") (pin "R2") (pinfunction "IN_R2") (pintype "input"))
    )
    (net (code "1103") (name "Net-(J08K-P$2)") (class "Default")
      (node (ref "J08") (pin "K2") (pinfunction "P$2_K2") (pintype "bidirectional"))
      (node (ref "J15") (pin "M1") (pinfunction "IN_M1") (pintype "input"))
    )
    (net (code "1104") (name "Net-(J08L-P$2)") (class "Default")
      (node (ref "J08") (pin "M2") (pinfunction "P$2_M2") (pintype "bidirectional"))
      (node (ref "J15") (pin "R2") (pinfunction "IN_R2") (pintype "input"))
    )
    (net (code "1105") (name "Net-(J08O-P$2)") (class "Default")
      (node (ref "J08") (pin "T2") (pinfunction "P$2_T2") (pintype "bidirectional"))
      (node (ref "J20") (pin "A1") (pinfunction "IN_A1") (pintype "input"))
    )
    (net (code "1106") (name "Net-(J09A-P$2)") (class "Default")
      (node (ref "J09") (pin "D2") (pinfunction "P$2_D2") (pintype "bidirectional"))
      (node (ref "J18") (pin "A1") (pinfunction "IN_A1") (pintype "input"))
    )
    (net (code "1107") (name "Net-(J09B-P$2)") (class "Default")
      (node (ref "J09") (pin "E2") (pinfunction "P$2_E2") (pintype "bidirectional"))
      (node (ref "J18") (pin "D2") (pinfunction "IN_D2") (pintype "input"))
    )
    (net (code "1108") (name "Net-(J09J-P$2)") (class "Default")
      (node (ref "J09") (pin "H2") (pinfunction "P$2_H2") (pintype "bidirectional"))
      (node (ref "J18") (pin "F1") (pinfunction "IN_F1") (pintype "input"))
    )
    (net (code "1109") (name "Net-(J09K-P$2)") (class "Default")
      (node (ref "J09") (pin "K2") (pinfunction "P$2_K2") (pintype "bidirectional"))
      (node (ref "J18") (pin "K2") (pinfunction "IN_K2") (pintype "input"))
    )
    (net (code "1110") (name "Net-(J09L-P$2)") (class "Default")
      (node (ref "J09") (pin "M2") (pinfunction "P$2_M2") (pintype "bidirectional"))
      (node (ref "J18") (pin "M1") (pinfunction "IN_M1") (pintype "input"))
    )
    (net (code "1111") (name "Net-(J09M-P$2)") (class "Default")
      (node (ref "J09") (pin "P2") (pinfunction "P$2_P2") (pintype "bidirectional"))
      (node (ref "J18") (pin "R2") (pinfunction "IN_R2") (pintype "input"))
    )
    (net (code "1112") (name "Net-(J09N-P$2)") (class "Default")
      (node (ref "J09") (pin "S2") (pinfunction "P$2_S2") (pintype "bidirectional"))
      (node (ref "J19") (pin "A1") (pinfunction "IN_A1") (pintype "input"))
    )
    (net (code "1113") (name "Net-(J09O-P$2)") (class "Default")
      (node (ref "J09") (pin "T2") (pinfunction "P$2_T2") (pintype "bidirectional"))
      (node (ref "J19") (pin "D2") (pinfunction "IN_D2") (pintype "input"))
    )
    (net (code "1114") (name "Net-(J09P-P$2)") (class "Default")
      (node (ref "J09") (pin "V2") (pinfunction "P$2_V2") (pintype "bidirectional"))
      (node (ref "J19") (pin "F1") (pinfunction "IN_F1") (pintype "input"))
    )
    (net (code "1115") (name "Net-(J10A-P$2)") (class "Default")
      (node (ref "J10") (pin "D2") (pinfunction "P$2_D2") (pintype "bidirectional"))
      (node (ref "J19") (pin "K2") (pinfunction "IN_K2") (pintype "input"))
    )
    (net (code "1116") (name "Net-(J10B-P$2)") (class "Default")
      (node (ref "J10") (pin "E2") (pinfunction "P$2_E2") (pintype "bidirectional"))
      (node (ref "J19") (pin "M1") (pinfunction "IN_M1") (pintype "input"))
    )
    (net (code "1117") (name "Net-(J10J-P$2)") (class "Default")
      (node (ref "J10") (pin "H2") (pinfunction "P$2_H2") (pintype "bidirectional"))
      (node (ref "J19") (pin "R2") (pinfunction "IN_R2") (pintype "input"))
    )
    (net (code "1118") (name "Net-(J10K-P$2)") (class "Default")
      (node (ref "J10") (pin "K2") (pinfunction "P$2_K2") (pintype "bidirectional"))
      (node (ref "J20") (pin "D2") (pinfunction "IN_D2") (pintype "input"))
    )
    (net (code "1119") (name "Net-(J10L-P$2)") (class "Default")
      (node (ref "J10") (pin "M2") (pinfunction "P$2_M2") (pintype "bidirectional"))
      (node (ref "J20") (pin "F1") (pinfunction "IN_F1") (pintype "input"))
    )
    (net (code "1120") (name "Net-(J10N-P$2)") (class "Default")
      (node (ref "J10") (pin "S2") (pinfunction "P$2_S2") (pintype "bidirectional"))
      (node (ref "J11") (pin "D2") (pinfunction "P$2_D2") (pintype "bidirectional"))
      (node (ref "J20") (pin "R2") (pinfunction "IN_R2") (pintype "input"))
    )
    (net (code "1121") (name "Net-(J10O-P$2)") (class "Default")
      (node (ref "J10") (pin "T2") (pinfunction "P$2_T2") (pintype "bidirectional"))
      (node (ref "J11") (pin "E2") (pinfunction "P$2_E2") (pintype "bidirectional"))
      (node (ref "J20") (pin "M1") (pinfunction "IN_M1") (pintype "input"))
    )
    (net (code "1122") (name "Net-(J10P-P$2)") (class "Default")
      (node (ref "J10") (pin "V2") (pinfunction "P$2_V2") (pintype "bidirectional"))
      (node (ref "J11") (pin "H2") (pinfunction "P$2_H2") (pintype "bidirectional"))
      (node (ref "J20") (pin "K2") (pinfunction "IN_K2") (pintype "input"))
    )
    (net (code "1123") (name "Net-(J15G-IN2)") (class "Default")
      (node (ref "J15") (pin "L2") (pinfunction "IN2_L2") (pintype "passive"))
      (node (ref "J15") (pin "M2") (pinfunction "IN3_M2") (pintype "input"))
      (node (ref "J15") (pin "N2") (pinfunction "IN4_N2") (pintype "input"))
    )
    (net (code "1124") (name "Net-(J15H-IN2)") (class "Default")
      (node (ref "J15") (pin "N1") (pinfunction "IN2_N1") (pintype "passive"))
      (node (ref "J15") (pin "P1") (pinfunction "IN3_P1") (pintype "input"))
      (node (ref "J15") (pin "R1") (pinfunction "IN4_R1") (pintype "input"))
    )
    (net (code "1125") (name "Net-(J15I-IN2)") (class "Default")
      (node (ref "J15") (pin "S2") (pinfunction "IN2_S2") (pintype "passive"))
      (node (ref "J15") (pin "T2") (pinfunction "IN3_T2") (pintype "input"))
      (node (ref "J15") (pin "U2") (pinfunction "IN4_U2") (pintype "input"))
    )
    (net (code "1126") (name "Net-(J16A-IN2)") (class "Default")
      (node (ref "J16") (pin "B1") (pinfunction "IN2_B1") (pintype "passive"))
      (node (ref "J16") (pin "C1") (pinfunction "IN3_C1") (pintype "input"))
      (node (ref "J16") (pin "D1") (pinfunction "IN4_D1") (pintype "input"))
    )
    (net (code "1127") (name "Net-(J16E-IN2)") (class "Default")
      (node (ref "J16") (pin "E2") (pinfunction "IN2_E2") (pintype "passive"))
      (node (ref "J16") (pin "F2") (pinfunction "IN3_F2") (pintype "input"))
      (node (ref "J16") (pin "H2") (pinfunction "IN4_H2") (pintype "input"))
    )
    (net (code "1128") (name "Net-(J16F-IN2)") (class "Default")
      (node (ref "J16") (pin "H1") (pinfunction "IN2_H1") (pintype "passive"))
      (node (ref "J16") (pin "J1") (pinfunction "IN3_J1") (pintype "input"))
      (node (ref "J16") (pin "K1") (pinfunction "IN4_K1") (pintype "input"))
    )
    (net (code "1129") (name "Net-(J16G-IN2)") (class "Default")
      (node (ref "J16") (pin "L2") (pinfunction "IN2_L2") (pintype "passive"))
      (node (ref "J16") (pin "M2") (pinfunction "IN3_M2") (pintype "input"))
      (node (ref "J16") (pin "N2") (pinfunction "IN4_N2") (pintype "input"))
    )
    (net (code "1130") (name "Net-(J16H-IN2)") (class "Default")
      (node (ref "J16") (pin "N1") (pinfunction "IN2_N1") (pintype "passive"))
      (node (ref "J16") (pin "P1") (pinfunction "IN3_P1") (pintype "input"))
      (node (ref "J16") (pin "R1") (pinfunction "IN4_R1") (pintype "input"))
    )
    (net (code "1131") (name "Net-(J16I-IN2)") (class "Default")
      (node (ref "J16") (pin "S2") (pinfunction "IN2_S2") (pintype "passive"))
      (node (ref "J16") (pin "T2") (pinfunction "IN3_T2") (pintype "input"))
      (node (ref "J16") (pin "U2") (pinfunction "IN4_U2") (pintype "input"))
    )
    (net (code "1132") (name "Net-(J17A-IN2)") (class "Default")
      (node (ref "J17") (pin "B1") (pinfunction "IN2_B1") (pintype "passive"))
      (node (ref "J17") (pin "C1") (pinfunction "IN3_C1") (pintype "input"))
      (node (ref "J17") (pin "D1") (pinfunction "IN4_D1") (pintype "input"))
    )
    (net (code "1133") (name "Net-(J17E-IN2)") (class "Default")
      (node (ref "J17") (pin "E2") (pinfunction "IN2_E2") (pintype "passive"))
      (node (ref "J17") (pin "F2") (pinfunction "IN3_F2") (pintype "input"))
      (node (ref "J17") (pin "H2") (pinfunction "IN4_H2") (pintype "input"))
    )
    (net (code "1134") (name "Net-(J17F-IN2)") (class "Default")
      (node (ref "J17") (pin "H1") (pinfunction "IN2_H1") (pintype "passive"))
      (node (ref "J17") (pin "J1") (pinfunction "IN3_J1") (pintype "input"))
      (node (ref "J17") (pin "K1") (pinfunction "IN4_K1") (pintype "input"))
    )
    (net (code "1135") (name "Net-(J17G-IN2)") (class "Default")
      (node (ref "J17") (pin "L2") (pinfunction "IN2_L2") (pintype "passive"))
      (node (ref "J17") (pin "M2") (pinfunction "IN3_M2") (pintype "input"))
      (node (ref "J17") (pin "N2") (pinfunction "IN4_N2") (pintype "input"))
    )
    (net (code "1136") (name "Net-(J17H-IN2)") (class "Default")
      (node (ref "J17") (pin "N1") (pinfunction "IN2_N1") (pintype "passive"))
      (node (ref "J17") (pin "P1") (pinfunction "IN3_P1") (pintype "input"))
      (node (ref "J17") (pin "R1") (pinfunction "IN4_R1") (pintype "input"))
    )
    (net (code "1137") (name "Net-(J17I-IN2)") (class "Default")
      (node (ref "J17") (pin "S2") (pinfunction "IN2_S2") (pintype "passive"))
      (node (ref "J17") (pin "T2") (pinfunction "IN3_T2") (pintype "input"))
      (node (ref "J17") (pin "U2") (pinfunction "IN4_U2") (pintype "input"))
    )
    (net (code "1138") (name "Net-(J18A-IN2)") (class "Default")
      (node (ref "J18") (pin "B1") (pinfunction "IN2_B1") (pintype "passive"))
      (node (ref "J18") (pin "C1") (pinfunction "IN3_C1") (pintype "input"))
      (node (ref "J18") (pin "D1") (pinfunction "IN4_D1") (pintype "input"))
    )
    (net (code "1139") (name "Net-(J18E-IN2)") (class "Default")
      (node (ref "J18") (pin "E2") (pinfunction "IN2_E2") (pintype "passive"))
      (node (ref "J18") (pin "F2") (pinfunction "IN3_F2") (pintype "input"))
      (node (ref "J18") (pin "H2") (pinfunction "IN4_H2") (pintype "input"))
    )
    (net (code "1140") (name "Net-(J18F-IN2)") (class "Default")
      (node (ref "J18") (pin "H1") (pinfunction "IN2_H1") (pintype "passive"))
      (node (ref "J18") (pin "J1") (pinfunction "IN3_J1") (pintype "input"))
      (node (ref "J18") (pin "K1") (pinfunction "IN4_K1") (pintype "input"))
    )
    (net (code "1141") (name "Net-(J18G-IN2)") (class "Default")
      (node (ref "J18") (pin "L2") (pinfunction "IN2_L2") (pintype "passive"))
      (node (ref "J18") (pin "M2") (pinfunction "IN3_M2") (pintype "input"))
      (node (ref "J18") (pin "N2") (pinfunction "IN4_N2") (pintype "input"))
    )
    (net (code "1142") (name "Net-(J18H-IN2)") (class "Default")
      (node (ref "J18") (pin "N1") (pinfunction "IN2_N1") (pintype "passive"))
      (node (ref "J18") (pin "P1") (pinfunction "IN3_P1") (pintype "input"))
      (node (ref "J18") (pin "R1") (pinfunction "IN4_R1") (pintype "input"))
    )
    (net (code "1143") (name "Net-(J18I-IN2)") (class "Default")
      (node (ref "J18") (pin "S2") (pinfunction "IN2_S2") (pintype "passive"))
      (node (ref "J18") (pin "T2") (pinfunction "IN3_T2") (pintype "input"))
      (node (ref "J18") (pin "U2") (pinfunction "IN4_U2") (pintype "input"))
    )
    (net (code "1144") (name "Net-(J19A-IN2)") (class "Default")
      (node (ref "J19") (pin "B1") (pinfunction "IN2_B1") (pintype "passive"))
      (node (ref "J19") (pin "C1") (pinfunction "IN3_C1") (pintype "input"))
      (node (ref "J19") (pin "D1") (pinfunction "IN4_D1") (pintype "input"))
    )
    (net (code "1145") (name "Net-(J19E-IN2)") (class "Default")
      (node (ref "J19") (pin "E2") (pinfunction "IN2_E2") (pintype "passive"))
      (node (ref "J19") (pin "F2") (pinfunction "IN3_F2") (pintype "input"))
      (node (ref "J19") (pin "H2") (pinfunction "IN4_H2") (pintype "input"))
    )
    (net (code "1146") (name "Net-(J19F-IN2)") (class "Default")
      (node (ref "J19") (pin "H1") (pinfunction "IN2_H1") (pintype "passive"))
      (node (ref "J19") (pin "J1") (pinfunction "IN3_J1") (pintype "input"))
      (node (ref "J19") (pin "K1") (pinfunction "IN4_K1") (pintype "input"))
    )
    (net (code "1147") (name "Net-(J19G-IN2)") (class "Default")
      (node (ref "J19") (pin "L2") (pinfunction "IN2_L2") (pintype "passive"))
      (node (ref "J19") (pin "M2") (pinfunction "IN3_M2") (pintype "input"))
      (node (ref "J19") (pin "N2") (pinfunction "IN4_N2") (pintype "input"))
    )
    (net (code "1148") (name "Net-(J19H-IN2)") (class "Default")
      (node (ref "J19") (pin "N1") (pinfunction "IN2_N1") (pintype "passive"))
      (node (ref "J19") (pin "P1") (pinfunction "IN3_P1") (pintype "input"))
      (node (ref "J19") (pin "R1") (pinfunction "IN4_R1") (pintype "input"))
    )
    (net (code "1149") (name "Net-(J19I-IN2)") (class "Default")
      (node (ref "J19") (pin "S2") (pinfunction "IN2_S2") (pintype "passive"))
      (node (ref "J19") (pin "T2") (pinfunction "IN3_T2") (pintype "input"))
      (node (ref "J19") (pin "U2") (pinfunction "IN4_U2") (pintype "input"))
    )
    (net (code "1150") (name "Net-(J20A-IN2)") (class "Default")
      (node (ref "J20") (pin "B1") (pinfunction "IN2_B1") (pintype "passive"))
      (node (ref "J20") (pin "C1") (pinfunction "IN3_C1") (pintype "input"))
      (node (ref "J20") (pin "D1") (pinfunction "IN4_D1") (pintype "input"))
    )
    (net (code "1151") (name "Net-(J20E-IN2)") (class "Default")
      (node (ref "J20") (pin "E2") (pinfunction "IN2_E2") (pintype "passive"))
      (node (ref "J20") (pin "F2") (pinfunction "IN3_F2") (pintype "input"))
      (node (ref "J20") (pin "H2") (pinfunction "IN4_H2") (pintype "input"))
    )
    (net (code "1152") (name "Net-(J20F-IN2)") (class "Default")
      (node (ref "J20") (pin "H1") (pinfunction "IN2_H1") (pintype "passive"))
      (node (ref "J20") (pin "J1") (pinfunction "IN3_J1") (pintype "input"))
      (node (ref "J20") (pin "K1") (pinfunction "IN4_K1") (pintype "input"))
    )
    (net (code "1153") (name "Net-(J20G-IN2)") (class "Default")
      (node (ref "J20") (pin "L2") (pinfunction "IN2_L2") (pintype "passive"))
      (node (ref "J20") (pin "M2") (pinfunction "IN3_M2") (pintype "input"))
      (node (ref "J20") (pin "N2") (pinfunction "IN4_N2") (pintype "input"))
    )
    (net (code "1154") (name "Net-(J20H-IN2)") (class "Default")
      (node (ref "J20") (pin "N1") (pinfunction "IN2_N1") (pintype "passive"))
      (node (ref "J20") (pin "P1") (pinfunction "IN3_P1") (pintype "input"))
      (node (ref "J20") (pin "R1") (pinfunction "IN4_R1") (pintype "input"))
    )
    (net (code "1155") (name "Net-(J20I-IN2)") (class "Default")
      (node (ref "J20") (pin "S2") (pinfunction "IN2_S2") (pintype "passive"))
      (node (ref "J20") (pin "T2") (pinfunction "IN3_T2") (pintype "input"))
      (node (ref "J20") (pin "U2") (pinfunction "IN4_U2") (pintype "input"))
    )
    (net (code "1156") (name "OP1") (class "Default")
      (node (ref "E27") (pin "H1") (pinfunction "IN3A_H1") (pintype "input"))
      (node (ref "E28") (pin "C1") (pinfunction "IN1C_C1") (pintype "input"))
      (node (ref "E28") (pin "N1") (pinfunction "IN5B_N1") (pintype "input"))
      (node (ref "E30") (pin "L2") (pinfunction "IN3A_L2") (pintype "input"))
      (node (ref "F25") (pin "C1") (pinfunction "OUT_C1") (pintype "output"))
      (node (ref "F26") (pin "B1") (pinfunction "IN2_B1") (pintype "input"))
      (node (ref "F26") (pin "E2") (pinfunction "IN2_E2") (pintype "input"))
      (node (ref "F26") (pin "F1") (pinfunction "IN2_F1") (pintype "input"))
      (node (ref "F26") (pin "K2") (pinfunction "IN2_K2") (pintype "input"))
      (node (ref "F26") (pin "L1") (pinfunction "IN2_L1") (pintype "input"))
      (node (ref "F29") (pin "T2") (pinfunction "IN1_T2") (pintype "input"))
      (node (ref "F32") (pin "H2") (pinfunction "IN1_H2") (pintype "input"))
    )
    (net (code "1157") (name "OP1_") (class "Default")
      (node (ref "F24") (pin "A1") (pinfunction "IN1_A1") (pintype "input"))
      (node (ref "F25") (pin "A1") (pinfunction "IN1_A1") (pintype "input"))
      (node (ref "F27") (pin "V2") (pinfunction "OUT_V2") (pintype "output"))
    )
    (net (code "1158") (name "OP2") (class "Default")
      (node (ref "B04") (pin "E2") (pinfunction "IN2_E2") (pintype "input"))
      (node (ref "D18") (pin "E2") (pinfunction "IN2_E2") (pintype "input"))
      (node (ref "D18") (pin "F1") (pinfunction "IN2_F1") (pintype "input"))
      (node (ref "D21") (pin "K1") (pinfunction "IN4_K1") (pintype "input"))
      (node (ref "E13") (pin "C1") (pinfunction "IN1C_C1") (pintype "input"))
      (node (ref "E25") (pin "R2") (pinfunction "IN3_R2") (pintype "input"))
      (node (ref "E28") (pin "P2") (pinfunction "IN4B_P2") (pintype "input"))
      (node (ref "E30") (pin "D2") (pinfunction "IN1A_D2") (pintype "input"))
      (node (ref "F28") (pin "N2") (pinfunction "IN1_N2") (pintype "input"))
      (node (ref "F29") (pin "K1") (pinfunction "OUT_K1") (pintype "output"))
    )
    (net (code "1159") (name "OPR") (class "Default")
      (node (ref "D13") (pin "L2") (pinfunction "IN1_L2") (pintype "input"))
      (node (ref "D14") (pin "D2") (pinfunction "IN1_D2") (pintype "input"))
      (node (ref "D20") (pin "N1") (pinfunction "IN2_N1") (pintype "input"))
      (node (ref "D21") (pin "F2") (pinfunction "IN3_F2") (pintype "input"))
      (node (ref "E22") (pin "S2") (pinfunction "OUT_S2") (pintype "output"))
      (node (ref "E25") (pin "V2") (pinfunction "IN3_V2") (pintype "input"))
      (node (ref "E26") (pin "S2") (pinfunction "IN4D_S2") (pintype "input"))
      (node (ref "F27") (pin "F1") (pinfunction "IN1_F1") (pintype "input"))
      (node (ref "F27") (pin "R2") (pinfunction "IN1_R2") (pintype "input"))
    )
    (net (code "1160") (name "OPR_") (class "Default")
      (node (ref "D40") (pin "D2") (pinfunction "P$2_D2") (pintype "bidirectional"))
      (node (ref "E21") (pin "V1") (pinfunction "OUT_V1") (pintype "output"))
      (node (ref "E22") (pin "P2") (pinfunction "IN1_P2") (pintype "input"))
    )
    (net (code "1161") (name "OSR_") (class "Default")
      (node (ref "A06") (pin "E2") (pinfunction "IN2_E2") (pintype "input"))
      (node (ref "F28") (pin "S2") (pinfunction "OUT_S2") (pintype "output"))
    )
    (net (code "1162") (name "OUT_STOP2_") (class "Default")
      (node (ref "EF02") (pin "BN1") (pinfunction "BN1_BN1") (pintype "output"))
      (node (ref "EF02") (pin "BN2") (pinfunction "BN2_BN2") (pintype "input"))
    )
    (net (code "1163") (name "OVERFLOW") (class "Default")
      (node (ref "H30") (pin "V1") (pinfunction "V1_V1") (pintype "input"))
      (node (ref "HJ31") (pin "BS1") (pinfunction "BS1_BS1") (pintype "output"))
    )
    (net (code "1164") (name "PAUSE_") (class "Default")
      (node (ref "D40") (pin "M1") (pinfunction "P$2_M1") (pintype "bidirectional"))
      (node (ref "E14") (pin "B1") (pinfunction "IN2_B1") (pintype "input"))
      (node (ref "E18") (pin "M1") (pinfunction "0_M1") (pintype "output"))
    )
    (net (code "1165") (name "PC00_") (class "Default")
      (node (ref "E40") (pin "J2") (pinfunction "P$2_J2") (pintype "bidirectional"))
      (node (ref "EF34") (pin "AR2") (pinfunction "AR2_AR2") (pintype "output"))
    )
    (net (code "1166") (name "PC01_") (class "Default")
      (node (ref "E40") (pin "S1") (pinfunction "P$2_S1") (pintype "bidirectional"))
      (node (ref "EF34") (pin "AP2") (pinfunction "AP2_AP2") (pintype "output"))
    )
    (net (code "1167") (name "PC02_") (class "Default")
      (node (ref "E40") (pin "P2") (pinfunction "P$2_P2") (pintype "bidirectional"))
      (node (ref "EF35") (pin "AR2") (pinfunction "AR2_AR2") (pintype "output"))
    )
    (net (code "1168") (name "PC03_") (class "Default")
      (node (ref "E40") (pin "N1") (pinfunction "P$2_N1") (pintype "bidirectional"))
      (node (ref "EF35") (pin "AP2") (pinfunction "AP2_AP2") (pintype "output"))
    )
    (net (code "1169") (name "PC04_") (class "Default")
      (node (ref "E40") (pin "C1") (pinfunction "P$2_C1") (pintype "bidirectional"))
      (node (ref "EF36") (pin "AR2") (pinfunction "AR2_AR2") (pintype "output"))
    )
    (net (code "1170") (name "PC05_") (class "Default")
      (node (ref "E40") (pin "D1") (pinfunction "P$2_D1") (pintype "bidirectional"))
      (node (ref "EF36") (pin "AP2") (pinfunction "AP2_AP2") (pintype "output"))
    )
    (net (code "1171") (name "PC06_") (class "Default")
      (node (ref "EF37") (pin "AR2") (pinfunction "AR2_AR2") (pintype "output"))
      (node (ref "F40") (pin "J2") (pinfunction "P$2_J2") (pintype "bidirectional"))
    )
    (net (code "1172") (name "PC07_") (class "Default")
      (node (ref "EF37") (pin "AP2") (pinfunction "AP2_AP2") (pintype "output"))
      (node (ref "F40") (pin "S1") (pinfunction "P$2_S1") (pintype "bidirectional"))
    )
    (net (code "1173") (name "PC08_") (class "Default")
      (node (ref "EF38") (pin "AR2") (pinfunction "AR2_AR2") (pintype "output"))
      (node (ref "F40") (pin "P2") (pinfunction "P$2_P2") (pintype "bidirectional"))
    )
    (net (code "1174") (name "PC09_") (class "Default")
      (node (ref "EF38") (pin "AP2") (pinfunction "AP2_AP2") (pintype "output"))
      (node (ref "F40") (pin "N1") (pinfunction "P$2_N1") (pintype "bidirectional"))
    )
    (net (code "1175") (name "PC10_") (class "Default")
      (node (ref "EF39") (pin "AR2") (pinfunction "AR2_AR2") (pintype "output"))
      (node (ref "F40") (pin "C1") (pinfunction "P$2_C1") (pintype "bidirectional"))
    )
    (net (code "1176") (name "PC11_") (class "Default")
      (node (ref "EF39") (pin "AP2") (pinfunction "AP2_AP2") (pintype "output"))
      (node (ref "F40") (pin "D1") (pinfunction "P$2_D1") (pintype "bidirectional"))
    )
    (net (code "1177") (name "PC_ENABLE") (class "Default")
      (node (ref "EF34") (pin "BS2") (pinfunction "BS2_BS2") (pintype "input"))
      (node (ref "EF35") (pin "BS2") (pinfunction "BS2_BS2") (pintype "input"))
      (node (ref "EF36") (pin "BS2") (pinfunction "BS2_BS2") (pintype "input"))
      (node (ref "EF37") (pin "BS2") (pinfunction "BS2_BS2") (pintype "input"))
      (node (ref "EF38") (pin "BS2") (pinfunction "BS2_BS2") (pintype "input"))
      (node (ref "EF39") (pin "BS2") (pinfunction "BS2_BS2") (pintype "input"))
      (node (ref "F30") (pin "E1") (pinfunction "OUT_E1") (pintype "output"))
    )
    (net (code "1178") (name "PC_ENABLE_") (class "Default")
      (node (ref "F09") (pin "M2") (pinfunction "IN7_M2") (pintype "input"))
      (node (ref "F11") (pin "P1") (pinfunction "IN3_P1") (pintype "input"))
      (node (ref "F27") (pin "H2") (pinfunction "IN4_H2") (pintype "input"))
      (node (ref "F32") (pin "N1") (pinfunction "OUT_N1") (pintype "output"))
    )
    (net (code "1179") (name "PC_INCREMENT") (class "Default")
      (node (ref "E26") (pin "F1") (pinfunction "IN2B_F1") (pintype "input"))
      (node (ref "E27") (pin "F1") (pinfunction "IN2B_F1") (pintype "input"))
      (node (ref "E30") (pin "F1") (pinfunction "IN2B_F1") (pintype "input"))
      (node (ref "F28") (pin "V1") (pinfunction "OUT_V1") (pintype "output"))
    )
    (net (code "1180") (name "PC_LOAD") (class "Default")
      (node (ref "A15") (pin "H1") (pinfunction "IN1_H1") (pintype "input"))
      (node (ref "E32") (pin "J2") (pinfunction "OUT_J2") (pintype "output"))
      (node (ref "EF34") (pin "AN2") (pinfunction "AN2_AN2") (pintype "input"))
      (node (ref "EF35") (pin "AN2") (pinfunction "AN2_AN2") (pintype "input"))
      (node (ref "EF36") (pin "AN2") (pinfunction "AN2_AN2") (pintype "input"))
      (node (ref "EF37") (pin "AN2") (pinfunction "AN2_AN2") (pintype "input"))
      (node (ref "EF38") (pin "AN2") (pinfunction "AN2_AN2") (pintype "input"))
      (node (ref "EF39") (pin "AN2") (pinfunction "AN2_AN2") (pintype "input"))
      (node (ref "F25") (pin "P1") (pinfunction "IN1_P1") (pintype "input"))
    )
    (net (code "1181") (name "PC_LOADXSR_ENABLE_") (class "Default")
      (node (ref "A15") (pin "K1") (pinfunction "OUT_K1") (pintype "output"))
      (node (ref "A17") (pin "A1") (pinfunction "IN1_A1") (pintype "input"))
      (node (ref "A17") (pin "R2") (pinfunction "IN2_R2") (pintype "input"))
      (node (ref "A18") (pin "A1") (pinfunction "IN1_A1") (pintype "input"))
      (node (ref "B06") (pin "H1") (pinfunction "IN1_H1") (pintype "input"))
    )
    (net (code "1182") (name "PC_LOAD_") (class "Default")
      (node (ref "B04") (pin "M1") (pinfunction "IN3_M1") (pintype "input"))
      (node (ref "E18") (pin "R1") (pinfunction "S_R1") (pintype "input"))
      (node (ref "F25") (pin "S1") (pinfunction "OUT_S1") (pintype "output"))
    )
    (net (code "1183") (name "PEN_DOWN") (class "Default")
      (node (ref "D02") (pin "V2") (pinfunction "P$2_V2") (pintype "bidirectional"))
      (node (ref "HJ29") (pin "AV2") (pinfunction "AV2_AV2") (pintype "output"))
    )
    (net (code "1184") (name "PEN_LEFT") (class "Default")
      (node (ref "D02") (pin "R2") (pinfunction "P$2_R2") (pintype "bidirectional"))
      (node (ref "HJ29") (pin "AL2") (pinfunction "AL2_AL2") (pintype "output"))
    )
    (net (code "1185") (name "PEN_RIGHT") (class "Default")
      (node (ref "D02") (pin "P2") (pinfunction "P$2_P2") (pintype "bidirectional"))
      (node (ref "HJ29") (pin "AJ2") (pinfunction "AJ2_AJ2") (pintype "output"))
    )
    (net (code "1186") (name "PEN_STROBE") (class "Default")
      (node (ref "HJ23") (pin "AJ1") (pinfunction "AJ1_AJ1") (pintype "output"))
      (node (ref "HJ23") (pin "AK1") (pinfunction "AK1_AK1") (pintype "input"))
    )
    (net (code "1187") (name "PEN_UP") (class "Default")
      (node (ref "D02") (pin "U2") (pinfunction "P$2_U2") (pintype "bidirectional"))
      (node (ref "HJ29") (pin "AT2") (pinfunction "AT2_AT2") (pintype "output"))
    )
    (net (code "1188") (name "POWER_CLEAR_") (class "Default")
      (node (ref "AB02") (pin "AS2") (pinfunction "AS2_AS2") (pintype "bidirectional"))
      (node (ref "B21") (pin "T2") (pinfunction "IN1_T2") (pintype "input"))
      (node (ref "B21") (pin "U2") (pinfunction "IN2_U2") (pintype "input"))
    )
    (net (code "1189") (name "POWER_OK_") (class "Default")
      (node (ref "AB02") (pin "AJ2") (pinfunction "AJ2_AJ2") (pintype "bidirectional"))
      (node (ref "E13") (pin "L1") (pinfunction "IN4B_L1") (pintype "input"))
    )
    (net (code "1190") (name "PROCESSOR_IOT_") (class "Default")
      (node (ref "F19") (pin "D1") (pinfunction "IN4_D1") (pintype "input"))
      (node (ref "F21") (pin "V2") (pinfunction "OUT_V2") (pintype "output"))
    )
    (net (code "1191") (name "PUN_FEED_SWITCH_") (class "Default")
      (node (ref "C01") (pin "U2") (pinfunction "P$2_U2") (pintype "bidirectional"))
      (node (ref "HJ28") (pin "AT2") (pinfunction "AT2_AT2") (pintype "input"))
    )
    (net (code "1192") (name "PWR") (class "Default")
      (node (ref "D01") (pin "U2") (pinfunction "P$2_U2") (pintype "bidirectional"))
      (node (ref "HJ26") (pin "BR2") (pinfunction "BR2_BR2") (pintype "output"))
    )
    (net (code "1193") (name "PWR_LOW_") (class "Default")
      (node (ref "A04") (pin "R2") (pinfunction "R2_R2") (pintype "output"))
      (node (ref "F19") (pin "M1") (pinfunction "IN1_M1") (pintype "input"))
    )
    (net (code "1194") (name "PWR_SKIP_") (class "Default")
      (node (ref "A04") (pin "L2") (pinfunction "L2_L2") (pintype "output"))
      (node (ref "F19") (pin "M2") (pinfunction "IN3_M2") (pintype "input"))
    )
    (net (code "1195") (name "R0") (class "Default")
      (node (ref "C09") (pin "L2") (pinfunction "IN1_L2") (pintype "input"))
      (node (ref "D05") (pin "J2") (pinfunction "OUT_J2") (pintype "output"))
      (node (ref "D10") (pin "R2") (pinfunction "IN1_R2") (pintype "input"))
    )
    (net (code "1196") (name "R0_") (class "Default")
      (node (ref "C09") (pin "N2") (pinfunction "OUT_N2") (pintype "output"))
      (node (ref "D10") (pin "M1") (pinfunction "IN1_M1") (pintype "input"))
    )
    (net (code "1197") (name "RDR_ENABLE_") (class "Default")
      (node (ref "HJ26") (pin "BK2") (pinfunction "BK2_BK2") (pintype "output"))
      (node (ref "HJ27") (pin "AK2") (pinfunction "AK_AK2") (pintype "input"))
    )
    (net (code "1198") (name "RDR_FEED_SWITCH") (class "Default")
      (node (ref "D01") (pin "V2") (pinfunction "P$2_V2") (pintype "bidirectional"))
      (node (ref "HJ26") (pin "BM1") (pinfunction "BM1_BM1") (pintype "input"))
      (node (ref "HJ27") (pin "BP2") (pinfunction "BP_BP2") (pintype "input"))
    )
    (net (code "1199") (name "RDR_RUN_") (class "Default")
      (node (ref "HJ26") (pin "AK1") (pinfunction "AK1_AK1") (pintype "output"))
      (node (ref "HJ27") (pin "BS2") (pinfunction "BS_BS2") (pintype "input"))
    )
    (net (code "1200") (name "RDR_SHIFT") (class "Default")
      (node (ref "HJ26") (pin "BJ1") (pinfunction "BJ1_BJ1") (pintype "input"))
      (node (ref "HJ27") (pin "AS2") (pinfunction "AS_AS2") (pintype "output"))
    )
    (net (code "1201") (name "RDR_SHIFT_") (class "Default")
      (node (ref "HJ26") (pin "BD1") (pinfunction "BD1_BD1") (pintype "input"))
      (node (ref "HJ27") (pin "AT2") (pinfunction "AT_AT2") (pintype "output"))
    )
    (net (code "1202") (name "RD_HOLE1") (class "Default")
      (node (ref "D01") (pin "D2") (pinfunction "P$2_D2") (pintype "bidirectional"))
      (node (ref "HJ26") (pin "AD2") (pinfunction "AD2_AD2") (pintype "input"))
    )
    (net (code "1203") (name "RD_HOLE2") (class "Default")
      (node (ref "D01") (pin "E2") (pinfunction "P$2_E2") (pintype "bidirectional"))
      (node (ref "HJ26") (pin "AD1") (pinfunction "AD1_AD1") (pintype "input"))
    )
    (net (code "1204") (name "RD_HOLE3") (class "Default")
      (node (ref "D01") (pin "F2") (pinfunction "P$2_F2") (pintype "bidirectional"))
      (node (ref "HJ26") (pin "AE2") (pinfunction "AE2_AE2") (pintype "input"))
    )
    (net (code "1205") (name "RD_HOLE4") (class "Default")
      (node (ref "D01") (pin "H2") (pinfunction "P$2_H2") (pintype "bidirectional"))
      (node (ref "HJ26") (pin "AE1") (pinfunction "AE1_AE1") (pintype "input"))
    )
    (net (code "1206") (name "RD_HOLE5") (class "Default")
      (node (ref "D01") (pin "J2") (pinfunction "P$2_J2") (pintype "bidirectional"))
      (node (ref "HJ26") (pin "AH2") (pinfunction "AH2_AH2") (pintype "input"))
    )
    (net (code "1207") (name "RD_HOLE6") (class "Default")
      (node (ref "D01") (pin "K2") (pinfunction "P$2_K2") (pintype "bidirectional"))
      (node (ref "HJ26") (pin "AH1") (pinfunction "AH1_AH1") (pintype "input"))
    )
    (net (code "1208") (name "RD_HOLE7") (class "Default")
      (node (ref "D01") (pin "L2") (pinfunction "P$2_L2") (pintype "bidirectional"))
      (node (ref "HJ26") (pin "AF2") (pinfunction "AF2_AF2") (pintype "input"))
    )
    (net (code "1209") (name "RD_HOLE8") (class "Default")
      (node (ref "D01") (pin "M2") (pinfunction "P$2_M2") (pintype "bidirectional"))
      (node (ref "HJ26") (pin "AF1") (pinfunction "AF1_AF1") (pintype "input"))
    )
    (net (code "1210") (name "READER_RUN_") (class "Default")
      (node (ref "EF01") (pin "AU2") (pinfunction "AU2_AU2") (pintype "output"))
      (node (ref "J12") (pin "M2") (pinfunction "P$2_M2") (pintype "bidirectional"))
    )
    (net (code "1211") (name "REG_BUS00") (class "Default")
      (node (ref "EF34") (pin "AJ1") (pinfunction "AJ1_AJ1") (pintype "output"))
    )
    (net (code "1212") (name "REG_BUS01") (class "Default")
      (node (ref "EF34") (pin "AK2") (pinfunction "AK2_AK2") (pintype "output"))
    )
    (net (code "1213") (name "REG_BUS02") (class "Default")
      (node (ref "EF35") (pin "AJ1") (pinfunction "AJ1_AJ1") (pintype "output"))
    )
    (net (code "1214") (name "REG_BUS03") (class "Default")
      (node (ref "EF35") (pin "AK2") (pinfunction "AK2_AK2") (pintype "output"))
    )
    (net (code "1215") (name "REG_BUS04") (class "Default")
      (node (ref "EF36") (pin "AJ1") (pinfunction "AJ1_AJ1") (pintype "output"))
    )
    (net (code "1216") (name "REG_BUS05") (class "Default")
      (node (ref "EF36") (pin "AK2") (pinfunction "AK2_AK2") (pintype "output"))
    )
    (net (code "1217") (name "REG_BUS06") (class "Default")
      (node (ref "EF37") (pin "AJ1") (pinfunction "AJ1_AJ1") (pintype "output"))
    )
    (net (code "1218") (name "REG_BUS07") (class "Default")
      (node (ref "EF37") (pin "AK2") (pinfunction "AK2_AK2") (pintype "output"))
    )
    (net (code "1219") (name "REG_BUS08") (class "Default")
      (node (ref "EF38") (pin "AJ1") (pinfunction "AJ1_AJ1") (pintype "output"))
    )
    (net (code "1220") (name "REG_BUS09") (class "Default")
      (node (ref "EF38") (pin "AK2") (pinfunction "AK2_AK2") (pintype "output"))
    )
    (net (code "1221") (name "REG_BUS10") (class "Default")
      (node (ref "EF39") (pin "AJ1") (pinfunction "AJ1_AJ1") (pintype "output"))
    )
    (net (code "1222") (name "REG_BUS11") (class "Default")
      (node (ref "EF39") (pin "AK2") (pinfunction "AK2_AK2") (pintype "output"))
    )
    (net (code "1223") (name "RESTART") (class "Default")
      (node (ref "A04") (pin "N2") (pinfunction "N2_N2") (pintype "output"))
      (node (ref "E12") (pin "L2") (pinfunction "IN1_L2") (pintype "input"))
    )
    (net (code "1224") (name "RESTART_") (class "Default")
      (node (ref "A04") (pin "U1") (pinfunction "U1_U1") (pintype "output"))
      (node (ref "E11") (pin "E1") (pinfunction "IN2_E1") (pintype "input"))
      (node (ref "E14") (pin "D2") (pinfunction "IN1_D2") (pintype "input"))
      (node (ref "E14") (pin "K2") (pinfunction "IN2_K2") (pintype "input"))
      (node (ref "EF10") (pin "AR2") (pinfunction "CR2_AR2") (pintype "input"))
    )
    (net (code "1225") (name "RIB") (class "Default")
      (node (ref "A05") (pin "H2") (pinfunction "IN1_H2") (pintype "input"))
      (node (ref "A11") (pin "D2") (pinfunction "IN1_D2") (pintype "input"))
      (node (ref "A11") (pin "L1") (pinfunction "IN1_L1") (pintype "input"))
      (node (ref "A11") (pin "P2") (pinfunction "IN1_P2") (pintype "input"))
      (node (ref "A13") (pin "H2") (pinfunction "IN1_H2") (pintype "input"))
      (node (ref "A13") (pin "L2") (pinfunction "IN1_L2") (pintype "input"))
      (node (ref "A13") (pin "P2") (pinfunction "IN1_P2") (pintype "input"))
      (node (ref "A14") (pin "N2") (pinfunction "OUT_N2") (pintype "output"))
    )
    (net (code "1226") (name "RIGHT_SHIFT") (class "Default")
      (node (ref "C14") (pin "A1") (pinfunction "IN1_A1") (pintype "input"))
      (node (ref "C14") (pin "H1") (pinfunction "IN1_H1") (pintype "input"))
      (node (ref "C14") (pin "L2") (pinfunction "IN1_L2") (pintype "input"))
      (node (ref "C15") (pin "A1") (pinfunction "IN1_A1") (pintype "input"))
      (node (ref "C15") (pin "H1") (pinfunction "IN1_H1") (pintype "input"))
      (node (ref "C15") (pin "L2") (pinfunction "IN1_L2") (pintype "input"))
      (node (ref "C16") (pin "A1") (pinfunction "IN1_A1") (pintype "input"))
      (node (ref "C16") (pin "H1") (pinfunction "IN1_H1") (pintype "input"))
      (node (ref "C16") (pin "L2") (pinfunction "IN1_L2") (pintype "input"))
      (node (ref "C17") (pin "A1") (pinfunction "IN1_A1") (pintype "input"))
      (node (ref "C17") (pin "H1") (pinfunction "IN1_H1") (pintype "input"))
      (node (ref "C17") (pin "L2") (pinfunction "IN1_L2") (pintype "input"))
      (node (ref "E31") (pin "L1") (pinfunction "OUT_L1") (pintype "output"))
      (node (ref "EF34") (pin "AD2") (pinfunction "AD2_AD2") (pintype "input"))
      (node (ref "EF35") (pin "AD2") (pinfunction "AD2_AD2") (pintype "input"))
      (node (ref "EF36") (pin "AD2") (pinfunction "AD2_AD2") (pintype "input"))
      (node (ref "EF37") (pin "AD2") (pinfunction "AD2_AD2") (pintype "input"))
      (node (ref "EF38") (pin "AD2") (pinfunction "AD2_AD2") (pintype "input"))
      (node (ref "EF39") (pin "AD2") (pinfunction "AD2_AD2") (pintype "input"))
      (node (ref "F33") (pin "D1") (pinfunction "IN1D_D1") (pintype "input"))
    )
    (net (code "1227") (name "RMF_") (class "Default")
      (node (ref "A06") (pin "V2") (pinfunction "OUT_V2") (pintype "output"))
      (node (ref "A13") (pin "B1") (pinfunction "IN2_B1") (pintype "input"))
      (node (ref "A15") (pin "L2") (pinfunction "IN1_L2") (pintype "input"))
      (node (ref "A15") (pin "M1") (pinfunction "IN2_M1") (pintype "input"))
      (node (ref "B06") (pin "E1") (pinfunction "IN2_E1") (pintype "input"))
    )
    (net (code "1228") (name "RUN") (class "Default")
      (node (ref "B10") (pin "J2") (pinfunction "J2_J2") (pintype "input"))
      (node (ref "E14") (pin "C1") (pinfunction "IN3_C1") (pintype "input"))
      (node (ref "E18") (pin "P2") (pinfunction "1_P2") (pintype "output"))
    )
    (net (code "1229") (name "RUN_") (class "Default")
      (node (ref "D40") (pin "F1") (pinfunction "P$2_F1") (pintype "bidirectional"))
      (node (ref "E18") (pin "R2") (pinfunction "0_R2") (pintype "output"))
      (node (ref "EF10") (pin "AP2") (pinfunction "CP2_AP2") (pintype "input"))
      (node (ref "F21") (pin "E1") (pinfunction "IN2_E1") (pintype "input"))
      (node (ref "H19") (pin "H2") (pinfunction "IN2_H2") (pintype "input"))
    )
    (net (code "1230") (name "RX_DATA") (class "Default")
      (node (ref "EF01") (pin "BM2") (pinfunction "BM2_BM2") (pintype "input"))
      (node (ref "J12") (pin "E2") (pinfunction "P$2_E2") (pintype "bidirectional"))
    )
    (net (code "1231") (name "S") (class "Default")
      (node (ref "C07") (pin "U2") (pinfunction "IN2_U2") (pintype "input"))
      (node (ref "C10") (pin "R1") (pinfunction "IN2_R1") (pintype "input"))
      (node (ref "C11") (pin "L2") (pinfunction "IN3_L2") (pintype "input"))
      (node (ref "C11") (pin "P2") (pinfunction "IN2_P2") (pintype "input"))
      (node (ref "D07") (pin "T2") (pinfunction "IN1_T2") (pintype "input"))
      (node (ref "D09") (pin "A1") (pinfunction "IN1_A1") (pintype "input"))
      (node (ref "D10") (pin "D2") (pinfunction "IN1_D2") (pintype "input"))
      (node (ref "D10") (pin "K1") (pinfunction "IN4_K1") (pintype "input"))
      (node (ref "D11") (pin "F1") (pinfunction "0_F1") (pintype "output"))
    )
    (net (code "1232") (name "SC0") (class "Default")
      (node (ref "C21") (pin "F2") (pinfunction "IN3_F2") (pintype "input"))
      (node (ref "C22") (pin "E1") (pinfunction "1_E1") (pintype "output"))
      (node (ref "D23") (pin "L1") (pinfunction "IN4B_L1") (pintype "input"))
      (node (ref "EF37") (pin "BN1") (pinfunction "BN1_BN1") (pintype "input"))
    )
    (net (code "1233") (name "SC0_") (class "Default")
      (node (ref "C21") (pin "C1") (pinfunction "IN3_C1") (pintype "input"))
      (node (ref "C22") (pin "F1") (pinfunction "0_F1") (pintype "output"))
      (node (ref "C40") (pin "S2") (pinfunction "P$2_S2") (pintype "bidirectional"))
    )
    (net (code "1234") (name "SC0_3_0") (class "Default")
      (node (ref "C18") (pin "S2") (pinfunction "OUT_S2") (pintype "output"))
      (node (ref "D13") (pin "P2") (pinfunction "IN1_P2") (pintype "input"))
      (node (ref "D19") (pin "E1") (pinfunction "IN1_E1") (pintype "input"))
      (node (ref "D23") (pin "F2") (pinfunction "IN1C_F2") (pintype "input"))
    )
    (net (code "1235") (name "SC0_3_0_") (class "Default")
      (node (ref "C18") (pin "P2") (pinfunction "IN1_P2") (pintype "input"))
      (node (ref "D17") (pin "N2") (pinfunction "IN1_N2") (pintype "input"))
      (node (ref "D22") (pin "J2") (pinfunction "OUT_J2") (pintype "output"))
    )
    (net (code "1236") (name "SC1") (class "Default")
      (node (ref "C21") (pin "L2") (pinfunction "IN3_L2") (pintype "input"))
      (node (ref "C22") (pin "H2") (pinfunction "1_H2") (pintype "output"))
      (node (ref "D17") (pin "E1") (pinfunction "IN1_E1") (pintype "input"))
      (node (ref "D19") (pin "J2") (pinfunction "IN1_J2") (pintype "input"))
      (node (ref "D20") (pin "L2") (pinfunction "IN2_L2") (pintype "input"))
      (node (ref "D22") (pin "A1") (pinfunction "IN1_A1") (pintype "input"))
      (node (ref "D23") (pin "B1") (pinfunction "IN1B_B1") (pintype "input"))
      (node (ref "EF38") (pin "BD1") (pinfunction "BD1_BD1") (pintype "input"))
    )
    (net (code "1237") (name "SC1_") (class "Default")
      (node (ref "C21") (pin "H1") (pinfunction "IN3_H1") (pintype "input"))
      (node (ref "C22") (pin "J2") (pinfunction "0_J2") (pintype "output"))
      (node (ref "C40") (pin "M2") (pinfunction "P$2_M2") (pintype "bidirectional"))
      (node (ref "D22") (pin "E2") (pinfunction "IN2_E2") (pintype "input"))
    )
    (net (code "1238") (name "SC2") (class "Default")
      (node (ref "C21") (pin "R2") (pinfunction "IN3_R2") (pintype "input"))
      (node (ref "C22") (pin "L1") (pinfunction "1_L1") (pintype "output"))
      (node (ref "D17") (pin "H1") (pinfunction "IN3_H1") (pintype "input"))
      (node (ref "D19") (pin "A1") (pinfunction "IN1_A1") (pintype "input"))
      (node (ref "D19") (pin "L2") (pinfunction "IN3_L2") (pintype "input"))
      (node (ref "D22") (pin "B1") (pinfunction "IN2_B1") (pintype "input"))
      (node (ref "EF38") (pin "BN1") (pinfunction "BN1_BN1") (pintype "input"))
    )
    (net (code "1239") (name "SC2_") (class "Default")
      (node (ref "C21") (pin "M1") (pinfunction "IN3_M1") (pintype "input"))
      (node (ref "C22") (pin "M1") (pinfunction "0_M1") (pintype "output"))
      (node (ref "C40") (pin "N2") (pinfunction "P$2_N2") (pintype "bidirectional"))
      (node (ref "D22") (pin "F2") (pinfunction "IN3_F2") (pintype "input"))
    )
    (net (code "1240") (name "SC3") (class "Default")
      (node (ref "C18") (pin "H1") (pinfunction "IN1_H1") (pintype "input"))
      (node (ref "C21") (pin "U2") (pinfunction "IN2_U2") (pintype "input"))
      (node (ref "C22") (pin "P2") (pinfunction "1_P2") (pintype "output"))
      (node (ref "D19") (pin "B1") (pinfunction "IN2_B1") (pintype "input"))
      (node (ref "D22") (pin "C1") (pinfunction "IN3_C1") (pintype "input"))
      (node (ref "D23") (pin "C1") (pinfunction "IN1C_C1") (pintype "input"))
      (node (ref "EF39") (pin "BD1") (pinfunction "BD1_BD1") (pintype "input"))
    )
    (net (code "1241") (name "SC3_") (class "Default")
      (node (ref "C21") (pin "P1") (pinfunction "IN1_P1") (pintype "input"))
      (node (ref "C22") (pin "R2") (pinfunction "0_R2") (pintype "output"))
      (node (ref "C40") (pin "L2") (pinfunction "P$2_L2") (pintype "bidirectional"))
      (node (ref "D22") (pin "H2") (pinfunction "IN4_H2") (pintype "input"))
    )
    (net (code "1242") (name "SC4") (class "Default")
      (node (ref "C18") (pin "J1") (pinfunction "IN2_J1") (pintype "input"))
      (node (ref "C21") (pin "S1") (pinfunction "IN3_S1") (pintype "input"))
      (node (ref "C22") (pin "S1") (pinfunction "1_S1") (pintype "output"))
      (node (ref "D19") (pin "C1") (pinfunction "IN3_C1") (pintype "input"))
      (node (ref "D19") (pin "K2") (pinfunction "IN2_K2") (pintype "input"))
      (node (ref "D22") (pin "D1") (pinfunction "IN4_D1") (pintype "input"))
      (node (ref "D23") (pin "D1") (pinfunction "IN1D_D1") (pintype "input"))
      (node (ref "EF39") (pin "BN1") (pinfunction "BN1_BN1") (pintype "input"))
    )
    (net (code "1243") (name "SC4_") (class "Default")
      (node (ref "C18") (pin "M2") (pinfunction "IN2_M2") (pintype "input"))
      (node (ref "C21") (pin "V2") (pinfunction "IN3_V2") (pintype "input"))
      (node (ref "C22") (pin "U1") (pinfunction "0_U1") (pintype "output"))
      (node (ref "C40") (pin "F1") (pinfunction "P$2_F1") (pintype "bidirectional"))
      (node (ref "D13") (pin "R2") (pinfunction "IN2_R2") (pintype "input"))
      (node (ref "D19") (pin "H1") (pinfunction "IN3_H1") (pintype "input"))
      (node (ref "D23") (pin "H2") (pinfunction "IN1D_H2") (pintype "input"))
    )
    (net (code "1244") (name "SCL_") (class "Default")
      (node (ref "D14") (pin "J1") (pinfunction "IN2_J1") (pintype "input"))
      (node (ref "D17") (pin "T2") (pinfunction "IN1_T2") (pintype "input"))
      (node (ref "D19") (pin "S2") (pinfunction "OUT_S2") (pintype "output"))
    )
    (net (code "1245") (name "SC_0_") (class "Default")
      (node (ref "D13") (pin "S2") (pinfunction "OUT_S2") (pintype "output"))
      (node (ref "D13") (pin "T2") (pinfunction "IN1_T2") (pintype "input"))
    )
    (net (code "1246") (name "SC_ENABLE") (class "Default")
      (node (ref "D22") (pin "P2") (pinfunction "OUT_P2") (pintype "output"))
      (node (ref "EF34") (pin "BF2") (pinfunction "BF2_BF2") (pintype "input"))
      (node (ref "EF35") (pin "BF2") (pinfunction "BF2_BF2") (pintype "input"))
      (node (ref "EF36") (pin "BF2") (pinfunction "BF2_BF2") (pintype "input"))
      (node (ref "EF37") (pin "BF2") (pinfunction "BF2_BF2") (pintype "input"))
      (node (ref "EF38") (pin "BF2") (pinfunction "BF2_BF2") (pintype "input"))
      (node (ref "EF39") (pin "BF2") (pinfunction "BF2_BF2") (pintype "input"))
    )
    (net (code "1247") (name "SC_FULL") (class "Default")
      (node (ref "C18") (pin "C1") (pinfunction "OUT_C1") (pintype "output"))
      (node (ref "C21") (pin "B1") (pinfunction "IN2_B1") (pintype "input"))
      (node (ref "D23") (pin "K1") (pinfunction "IN4A_K1") (pintype "input"))
    )
    (net (code "1248") (name "SC_LOAD") (class "Default")
      (node (ref "C22") (pin "B1") (pinfunction "C_B1") (pintype "input"))
      (node (ref "C22") (pin "D2") (pinfunction "C_D2") (pintype "input"))
      (node (ref "C22") (pin "H1") (pinfunction "C_H1") (pintype "input"))
      (node (ref "C22") (pin "L2") (pinfunction "C_L2") (pintype "input"))
      (node (ref "C22") (pin "N1") (pinfunction "C_N1") (pintype "input"))
      (node (ref "D22") (pin "V2") (pinfunction "OUT_V2") (pintype "output"))
    )
    (net (code "1249") (name "SF0") (class "Default")
      (node (ref "A11") (pin "E2") (pinfunction "IN2_E2") (pintype "input"))
      (node (ref "A18") (pin "J1") (pinfunction "IN2_J1") (pintype "input"))
      (node (ref "B19") (pin "E1") (pinfunction "1_E1") (pintype "output"))
    )
    (net (code "1250") (name "SF1") (class "Default")
      (node (ref "A11") (pin "M1") (pinfunction "IN2_M1") (pintype "input"))
      (node (ref "A18") (pin "M2") (pinfunction "IN2_M2") (pintype "input"))
      (node (ref "B19") (pin "H2") (pinfunction "1_H2") (pintype "output"))
    )
    (net (code "1251") (name "SF2") (class "Default")
      (node (ref "A11") (pin "R2") (pinfunction "IN2_R2") (pintype "input"))
      (node (ref "A18") (pin "U2") (pinfunction "IN2_U2") (pintype "input"))
      (node (ref "B19") (pin "L1") (pinfunction "1_L1") (pintype "output"))
    )
    (net (code "1252") (name "SF3") (class "Default")
      (node (ref "A12") (pin "J1") (pinfunction "IN2_J1") (pintype "input"))
      (node (ref "A13") (pin "J2") (pinfunction "IN2_J2") (pintype "input"))
      (node (ref "B19") (pin "P2") (pinfunction "1_P2") (pintype "output"))
    )
    (net (code "1253") (name "SF4") (class "Default")
      (node (ref "A12") (pin "M2") (pinfunction "IN2_M2") (pintype "input"))
      (node (ref "A13") (pin "M2") (pinfunction "IN2_M2") (pintype "input"))
      (node (ref "B19") (pin "S1") (pinfunction "1_S1") (pintype "output"))
    )
    (net (code "1254") (name "SF5") (class "Default")
      (node (ref "A12") (pin "U2") (pinfunction "IN2_U2") (pintype "input"))
      (node (ref "A13") (pin "R2") (pinfunction "IN2_R2") (pintype "input"))
      (node (ref "B19") (pin "V2") (pinfunction "1_V2") (pintype "output"))
    )
    (net (code "1255") (name "SF_ENABLE") (class "Default")
      (node (ref "A12") (pin "H1") (pinfunction "IN1_H1") (pintype "input"))
      (node (ref "A12") (pin "L2") (pinfunction "IN1_L2") (pintype "input"))
      (node (ref "A12") (pin "T2") (pinfunction "IN1_T2") (pintype "input"))
      (node (ref "A15") (pin "N2") (pinfunction "OUT_N2") (pintype "output"))
      (node (ref "A18") (pin "H1") (pinfunction "IN1_H1") (pintype "input"))
      (node (ref "A18") (pin "L2") (pinfunction "IN1_L2") (pintype "input"))
      (node (ref "A18") (pin "T2") (pinfunction "IN1_T2") (pintype "input"))
      (node (ref "B06") (pin "R1") (pinfunction "IN2_R1") (pintype "input"))
    )
    (net (code "1256") (name "SHUT_DOWN_") (class "Default")
      (node (ref "A04") (pin "U2") (pinfunction "U2_U2") (pintype "input"))
      (node (ref "AB02") (pin "AF2") (pinfunction "AF2_AF2") (pintype "output"))
    )
    (net (code "1257") (name "SINT") (class "Default")
      (node (ref "A05") (pin "V2") (pinfunction "OUT_V2") (pintype "output"))
      (node (ref "B04") (pin "L2") (pinfunction "IN3_L2") (pintype "input"))
    )
    (net (code "1258") (name "SKIP_") (class "Default")
      (node (ref "B04") (pin "U2") (pinfunction "IN2_U2") (pintype "input"))
      (node (ref "E18") (pin "S1") (pinfunction "1_S1") (pintype "output"))
      (node (ref "F25") (pin "U2") (pinfunction "IN2_U2") (pintype "input"))
    )
    (net (code "1259") (name "SKIP_OR") (class "Default")
      (node (ref "B04") (pin "V1") (pinfunction "OUT_V1") (pintype "output"))
      (node (ref "E27") (pin "L1") (pinfunction "IN4B_L1") (pintype "input"))
    )
    (net (code "1260") (name "SLOW_CYCLE") (class "Default")
      (node (ref "E12") (pin "N1") (pinfunction "OUT_N1") (pintype "output"))
      (node (ref "E15") (pin "R1") (pinfunction "IN2_R1") (pintype "input"))
    )
    (net (code "1261") (name "SLOW_CYCLE_") (class "Default")
      (node (ref "E12") (pin "M1") (pinfunction "IN2_M1") (pintype "input"))
      (node (ref "E14") (pin "M1") (pinfunction "IN3_M1") (pintype "input"))
      (node (ref "F19") (pin "E1") (pinfunction "OUT_E1") (pintype "output"))
    )
    (net (code "1262") (name "SPECIAL_CYCLE_") (class "Default")
      (node (ref "E24") (pin "K1") (pinfunction "OUT_K1") (pintype "output"))
      (node (ref "F23") (pin "M1") (pinfunction "IN1_M1") (pintype "input"))
      (node (ref "F23") (pin "M2") (pinfunction "IN3_M2") (pintype "input"))
    )
    (net (code "1263") (name "SR00") (class "Default")
      (node (ref "A40") (pin "L2") (pinfunction "P$2_L2") (pintype "bidirectional"))
      (node (ref "EF34") (pin "BE1") (pinfunction "BE1_BE1") (pintype "input"))
    )
    (net (code "1264") (name "SR01") (class "Default")
      (node (ref "A40") (pin "M2") (pinfunction "P$2_M2") (pintype "bidirectional"))
      (node (ref "EF34") (pin "BD2") (pinfunction "BD2_BD2") (pintype "input"))
    )
    (net (code "1265") (name "SR02") (class "Default")
      (node (ref "A40") (pin "R2") (pinfunction "P$2_R2") (pintype "bidirectional"))
      (node (ref "EF35") (pin "BE1") (pinfunction "BE1_BE1") (pintype "input"))
    )
    (net (code "1266") (name "SR03") (class "Default")
      (node (ref "A40") (pin "S2") (pinfunction "P$2_S2") (pintype "bidirectional"))
      (node (ref "EF35") (pin "BD2") (pinfunction "BD2_BD2") (pintype "input"))
    )
    (net (code "1267") (name "SR04") (class "Default")
      (node (ref "A40") (pin "T2") (pinfunction "P$2_T2") (pintype "bidirectional"))
      (node (ref "EF36") (pin "BE1") (pinfunction "BE1_BE1") (pintype "input"))
    )
    (net (code "1268") (name "SR05") (class "Default")
      (node (ref "A40") (pin "U2") (pinfunction "P$2_U2") (pintype "bidirectional"))
      (node (ref "EF36") (pin "BD2") (pinfunction "BD2_BD2") (pintype "input"))
    )
    (net (code "1269") (name "SR06") (class "Default")
      (node (ref "A40") (pin "V2") (pinfunction "P$2_V2") (pintype "bidirectional"))
      (node (ref "EF37") (pin "BE1") (pinfunction "BE1_BE1") (pintype "input"))
    )
    (net (code "1270") (name "SR07") (class "Default")
      (node (ref "B40") (pin "D2") (pinfunction "P$2_D2") (pintype "bidirectional"))
      (node (ref "EF37") (pin "BD2") (pinfunction "BD2_BD2") (pintype "input"))
    )
    (net (code "1271") (name "SR08") (class "Default")
      (node (ref "B40") (pin "E2") (pinfunction "P$2_E2") (pintype "bidirectional"))
      (node (ref "EF38") (pin "BE1") (pinfunction "BE1_BE1") (pintype "input"))
    )
    (net (code "1272") (name "SR09") (class "Default")
      (node (ref "B40") (pin "F2") (pinfunction "P$2_F2") (pintype "bidirectional"))
      (node (ref "EF38") (pin "BD2") (pinfunction "BD2_BD2") (pintype "input"))
    )
    (net (code "1273") (name "SR10") (class "Default")
      (node (ref "B40") (pin "H2") (pinfunction "P$2_H2") (pintype "bidirectional"))
      (node (ref "EF39") (pin "BE1") (pinfunction "BE1_BE1") (pintype "input"))
    )
    (net (code "1274") (name "SR11") (class "Default")
      (node (ref "B40") (pin "J2") (pinfunction "P$2_J2") (pintype "bidirectional"))
      (node (ref "EF39") (pin "BD2") (pinfunction "BD2_BD2") (pintype "input"))
    )
    (net (code "1275") (name "SR_ENABLE") (class "Default")
      (node (ref "A12") (pin "D1") (pinfunction "IN1_D1") (pintype "input"))
      (node (ref "A12") (pin "H2") (pinfunction "IN1_H2") (pintype "input"))
      (node (ref "A12") (pin "P1") (pinfunction "IN1_P1") (pintype "input"))
      (node (ref "A18") (pin "D1") (pinfunction "IN1_D1") (pintype "input"))
      (node (ref "A18") (pin "H2") (pinfunction "IN1_H2") (pintype "input"))
      (node (ref "A18") (pin "P1") (pinfunction "IN1_P1") (pintype "input"))
      (node (ref "EF34") (pin "BC1") (pinfunction "BC1_BC1") (pintype "input"))
      (node (ref "EF35") (pin "BC1") (pinfunction "BC1_BC1") (pintype "input"))
      (node (ref "EF36") (pin "BC1") (pinfunction "BC1_BC1") (pintype "input"))
      (node (ref "EF37") (pin "BC1") (pinfunction "BC1_BC1") (pintype "input"))
      (node (ref "EF38") (pin "BC1") (pinfunction "BC1_BC1") (pintype "input"))
      (node (ref "EF39") (pin "BC1") (pinfunction "BC1_BC1") (pintype "input"))
      (node (ref "F30") (pin "S1") (pinfunction "OUT_S1") (pintype "output"))
    )
    (net (code "1276") (name "STOP_COMPLETE") (class "Default")
      (node (ref "HJ26") (pin "BN2") (pinfunction "BN2_BN2") (pintype "input"))
      (node (ref "HJ27") (pin "BR2") (pinfunction "BR_BR2") (pintype "output"))
    )
    (net (code "1277") (name "STOP_OK") (class "Default")
      (node (ref "A04") (pin "P2") (pinfunction "P2_P2") (pintype "output"))
      (node (ref "AB02") (pin "AH2") (pinfunction "AH2_AH2") (pintype "input"))
      (node (ref "E13") (pin "K1") (pinfunction "IN4A_K1") (pintype "input"))
    )
    (net (code "1278") (name "STORE_") (class "Default")
      (node (ref "D07") (pin "D2") (pinfunction "IN1_D2") (pintype "input"))
      (node (ref "D09") (pin "P1") (pinfunction "IN1_P1") (pintype "input"))
      (node (ref "D10") (pin "S1") (pinfunction "OUT_S1") (pintype "output"))
      (node (ref "F31") (pin "C1") (pinfunction "IN3_C1") (pintype "input"))
    )
    (net (code "1279") (name "STROBE_") (class "Default")
      (node (ref "B10") (pin "E2") (pinfunction "E2_E2") (pintype "open_collector"))
      (node (ref "E15") (pin "H2") (pinfunction "IN1_H2") (pintype "input"))
      (node (ref "E18") (pin "A1") (pinfunction "R_A1") (pintype "input"))
      (node (ref "E19") (pin "D1") (pinfunction "S_D1") (pintype "input"))
      (node (ref "EF10") (pin "BE2") (pinfunction "P$1_BE2") (pintype "passive"))
      (node (ref "F20") (pin "D1") (pinfunction "IN1_D1") (pintype "input"))
      (node (ref "H05") (pin "P2") (pinfunction "P$2_P2") (pintype "bidirectional"))
    )
    (net (code "1280") (name "SYNC_PUN") (class "Default")
      (node (ref "C01") (pin "F2") (pinfunction "P$2_F2") (pintype "bidirectional"))
      (node (ref "HJ28") (pin "AV2") (pinfunction "AV2_AV2") (pintype "input"))
    )
    (net (code "1281") (name "S_") (class "Default")
      (node (ref "D09") (pin "R2") (pinfunction "IN3_R2") (pintype "input"))
      (node (ref "D11") (pin "E1") (pinfunction "1_E1") (pintype "output"))
      (node (ref "E09") (pin "A1") (pinfunction "IN1_A1") (pintype "input"))
    )
    (net (code "1282") (name "S_FEED_HOLE") (class "Default")
      (node (ref "D01") (pin "N2") (pinfunction "P$2_N2") (pintype "bidirectional"))
      (node (ref "HJ26") (pin "BM2") (pinfunction "BM2_BM2") (pintype "input"))
    )
    (net (code "1283") (name "S_SET_") (class "Default")
      (node (ref "C11") (pin "C1") (pinfunction "IN3_C1") (pintype "input"))
      (node (ref "D10") (pin "E1") (pinfunction "OUT_E1") (pintype "output"))
      (node (ref "D11") (pin "C1") (pinfunction "D_C1") (pintype "input"))
    )
    (net (code "1284") (name "S_UF") (class "Default")
      (node (ref "A05") (pin "J2") (pinfunction "IN2_J2") (pintype "input"))
      (node (ref "B05") (pin "S1") (pinfunction "1_S1") (pintype "output"))
      (node (ref "B06") (pin "P1") (pinfunction "IN1_P1") (pintype "input"))
    )
    (net (code "1285") (name "TAD") (class "Default")
      (node (ref "E22") (pin "F1") (pinfunction "OUT_F1") (pintype "output"))
      (node (ref "F28") (pin "A1") (pinfunction "IN1_A1") (pintype "input"))
    )
    (net (code "1286") (name "TAD_") (class "Default")
      (node (ref "D40") (pin "T2") (pinfunction "P$2_T2") (pintype "bidirectional"))
      (node (ref "E21") (pin "D1") (pinfunction "OUT_D1") (pintype "output"))
      (node (ref "E22") (pin "D1") (pinfunction "IN1_D1") (pintype "input"))
      (node (ref "F26") (pin "U2") (pinfunction "IN2_U2") (pintype "input"))
    )
    (net (code "1287") (name "TELEPRINTER_FLAG_") (class "Default")
      (node (ref "EF02") (pin "BK2") (pinfunction "BK2_BK2") (pintype "output"))
      (node (ref "F19") (pin "R1") (pinfunction "IN4_R1") (pintype "input"))
    )
    (net (code "1288") (name "TP1") (class "Default")
      (node (ref "D07") (pin "U2") (pinfunction "IN2_U2") (pintype "input"))
      (node (ref "E09") (pin "B1") (pinfunction "IN2_B1") (pintype "input"))
      (node (ref "E15") (pin "K2") (pinfunction "OUT_K2") (pintype "output"))
      (node (ref "E20") (pin "L2") (pinfunction "C_L2") (pintype "input"))
      (node (ref "E26") (pin "E1") (pinfunction "IN2A_E1") (pintype "input"))
      (node (ref "E26") (pin "S1") (pinfunction "IN1A_S1") (pintype "input"))
    )
    (net (code "1289") (name "TP2") (class "Default")
      (node (ref "E15") (pin "L1") (pinfunction "IN1_L1") (pintype "input"))
      (node (ref "E17") (pin "F1") (pinfunction "OUT_F1") (pintype "output"))
      (node (ref "E19") (pin "B1") (pinfunction "C_B1") (pintype "input"))
      (node (ref "E22") (pin "L1") (pinfunction "IN1_L1") (pintype "input"))
      (node (ref "E33") (pin "D2") (pinfunction "C_D2") (pintype "input"))
      (node (ref "F25") (pin "P2") (pinfunction "IN1_P2") (pintype "input"))
      (node (ref "F32") (pin "J1") (pinfunction "IN2_J1") (pintype "input"))
    )
    (net (code "1290") (name "TP2E_") (class "Default")
      (node (ref "B04") (pin "K1") (pinfunction "IN1_K1") (pintype "input"))
      (node (ref "B04") (pin "L1") (pinfunction "IN2_L1") (pintype "input"))
      (node (ref "E25") (pin "R1") (pinfunction "IN2_R1") (pintype "input"))
      (node (ref "F25") (pin "S2") (pinfunction "OUT_S2") (pintype "output"))
    )
    (net (code "1291") (name "TP3") (class "Default")
      (node (ref "A13") (pin "D2") (pinfunction "IN1_D2") (pintype "input"))
      (node (ref "A14") (pin "P2") (pinfunction "IN1_P2") (pintype "input"))
      (node (ref "A19") (pin "L1") (pinfunction "IN1_L1") (pintype "input"))
      (node (ref "A20") (pin "B1") (pinfunction "IN2_B1") (pintype "input"))
      (node (ref "B04") (pin "K2") (pinfunction "IN2_K2") (pintype "input"))
      (node (ref "B05") (pin "L2") (pinfunction "C_L2") (pintype "input"))
      (node (ref "B10") (pin "V2") (pinfunction "V2_V2") (pintype "input"))
      (node (ref "B11") (pin "L2") (pinfunction "C_L2") (pintype "input"))
      (node (ref "C08") (pin "J2") (pinfunction "IN2_J2") (pintype "input"))
      (node (ref "D09") (pin "U2") (pinfunction "IN2_U2") (pintype "input"))
      (node (ref "D12") (pin "P2") (pinfunction "IN1_P2") (pintype "input"))
      (node (ref "D14") (pin "P2") (pinfunction "IN1_P2") (pintype "input"))
      (node (ref "D14") (pin "T2") (pinfunction "IN1_T2") (pintype "input"))
      (node (ref "D17") (pin "U2") (pinfunction "IN2_U2") (pintype "input"))
      (node (ref "D18") (pin "M1") (pinfunction "IN3_M1") (pintype "input"))
      (node (ref "E14") (pin "K1") (pinfunction "IN1_K1") (pintype "input"))
      (node (ref "E15") (pin "P1") (pinfunction "IN1_P1") (pintype "input"))
      (node (ref "E17") (pin "J1") (pinfunction "OUT_J1") (pintype "output"))
      (node (ref "E18") (pin "L2") (pinfunction "C_L2") (pintype "input"))
      (node (ref "E19") (pin "D2") (pinfunction "C_D2") (pintype "input"))
      (node (ref "E25") (pin "T2") (pinfunction "IN1_T2") (pintype "input"))
      (node (ref "E26") (pin "A1") (pinfunction "IN1A_A1") (pintype "input"))
      (node (ref "E26") (pin "E2") (pinfunction "IN1B_E2") (pintype "input"))
      (node (ref "E26") (pin "H1") (pinfunction "IN3A_H1") (pintype "input"))
      (node (ref "E26") (pin "M1") (pinfunction "IN5A_M1") (pintype "input"))
      (node (ref "E26") (pin "P2") (pinfunction "IN4B_P2") (pintype "input"))
      (node (ref "F26") (pin "N2") (pinfunction "IN1_N2") (pintype "input"))
    )
    (net (code "1292") (name "TP4") (class "Default")
      (node (ref "D11") (pin "B1") (pinfunction "C_B1") (pintype "input"))
      (node (ref "D11") (pin "D2") (pinfunction "C_D2") (pintype "input"))
      (node (ref "E15") (pin "F2") (pinfunction "OUT_F2") (pintype "output"))
      (node (ref "E18") (pin "B1") (pinfunction "C_B1") (pintype "input"))
      (node (ref "E19") (pin "H1") (pinfunction "C_H1") (pintype "input"))
      (node (ref "E23") (pin "B1") (pinfunction "C_B1") (pintype "input"))
      (node (ref "E23") (pin "D2") (pinfunction "C_D2") (pintype "input"))
      (node (ref "E23") (pin "H1") (pinfunction "C_H1") (pintype "input"))
      (node (ref "E23") (pin "L2") (pinfunction "C_L2") (pintype "input"))
      (node (ref "E23") (pin "N1") (pinfunction "C_N1") (pintype "input"))
      (node (ref "E23") (pin "S2") (pinfunction "C_S2") (pintype "input"))
      (node (ref "E24") (pin "H2") (pinfunction "IN1_H2") (pintype "input"))
      (node (ref "E33") (pin "B1") (pinfunction "C_B1") (pintype "input"))
      (node (ref "F32") (pin "D2") (pinfunction "IN1_D2") (pintype "input"))
    )
    (net (code "1293") (name "TS1") (class "Default")
      (node (ref "C07") (pin "V2") (pinfunction "IN1_V2") (pintype "input"))
      (node (ref "E18") (pin "E1") (pinfunction "1_E1") (pintype "output"))
      (node (ref "E27") (pin "E1") (pinfunction "IN2A_E1") (pintype "input"))
      (node (ref "E30") (pin "E1") (pinfunction "IN2A_E1") (pintype "input"))
    )
    (net (code "1294") (name "TS1_") (class "Default")
      (node (ref "E18") (pin "F1") (pinfunction "0_F1") (pintype "output"))
      (node (ref "H12") (pin "N2") (pinfunction "IN2_N2") (pintype "input"))
    )
    (net (code "1295") (name "TS2") (class "Default")
      (node (ref "C11") (pin "H1") (pinfunction "IN3_H1") (pintype "input"))
      (node (ref "C11") (pin "J2") (pinfunction "IN1_J2") (pintype "input"))
      (node (ref "D09") (pin "B1") (pinfunction "IN2_B1") (pintype "input"))
      (node (ref "D10") (pin "F1") (pinfunction "IN1_F1") (pintype "input"))
      (node (ref "E19") (pin "E1") (pinfunction "1_E1") (pintype "output"))
      (node (ref "E27") (pin "A1") (pinfunction "IN1A_A1") (pintype "input"))
      (node (ref "E27") (pin "P2") (pinfunction "IN4B_P2") (pintype "input"))
      (node (ref "E28") (pin "D2") (pinfunction "IN1A_D2") (pintype "input"))
      (node (ref "E29") (pin "E1") (pinfunction "IN2A_E1") (pintype "input"))
      (node (ref "E30") (pin "P2") (pinfunction "IN4B_P2") (pintype "input"))
      (node (ref "F28") (pin "E1") (pinfunction "IN1_E1") (pintype "input"))
      (node (ref "F28") (pin "K1") (pinfunction "IN1_K1") (pintype "input"))
    )
    (net (code "1296") (name "TS3") (class "Default")
      (node (ref "C11") (pin "K1") (pinfunction "IN1_K1") (pintype "input"))
      (node (ref "C11") (pin "N2") (pinfunction "IN1_N2") (pintype "input"))
      (node (ref "C12") (pin "E2") (pinfunction "IN2_E2") (pintype "input"))
      (node (ref "D09") (pin "D2") (pinfunction "IN1_D2") (pintype "input"))
      (node (ref "D10") (pin "P1") (pinfunction "IN3_P1") (pintype "input"))
      (node (ref "D10") (pin "T2") (pinfunction "IN3_T2") (pintype "input"))
      (node (ref "E19") (pin "H2") (pinfunction "1_H2") (pintype "output"))
      (node (ref "E27") (pin "M1") (pinfunction "IN5A_M1") (pintype "input"))
      (node (ref "E29") (pin "A1") (pinfunction "IN1A_A1") (pintype "input"))
      (node (ref "E30") (pin "M1") (pinfunction "IN5A_M1") (pintype "input"))
      (node (ref "F26") (pin "R1") (pinfunction "IN2_R1") (pintype "input"))
      (node (ref "F27") (pin "A1") (pinfunction "IN1_A1") (pintype "input"))
      (node (ref "F27") (pin "H1") (pinfunction "IN2_H1") (pintype "input"))
      (node (ref "F27") (pin "S2") (pinfunction "IN2_S2") (pintype "input"))
      (node (ref "F28") (pin "B1") (pinfunction "IN2_B1") (pintype "input"))
    )
    (net (code "1297") (name "TS3_") (class "Default")
      (node (ref "E19") (pin "J2") (pinfunction "0_J2") (pintype "output"))
      (node (ref "H12") (pin "H2") (pinfunction "IN2_H2") (pintype "input"))
    )
    (net (code "1298") (name "TS4") (class "Default")
      (node (ref "C12") (pin "L2") (pinfunction "IN2_L2") (pintype "input"))
      (node (ref "E19") (pin "L1") (pinfunction "1_L1") (pintype "output"))
      (node (ref "E29") (pin "K1") (pinfunction "IN4A_K1") (pintype "input"))
      (node (ref "E29") (pin "M1") (pinfunction "IN5A_M1") (pintype "input"))
      (node (ref "E30") (pin "H1") (pinfunction "IN3A_H1") (pintype "input"))
      (node (ref "F27") (pin "D2") (pinfunction "IN1_D2") (pintype "input"))
      (node (ref "F29") (pin "L1") (pinfunction "IN1_L1") (pintype "input"))
      (node (ref "F32") (pin "L1") (pinfunction "IN1_L1") (pintype "input"))
    )
    (net (code "1299") (name "TS4_") (class "Default")
      (node (ref "A19") (pin "J1") (pinfunction "IN2_J1") (pintype "input"))
      (node (ref "E19") (pin "M1") (pinfunction "0_M1") (pintype "output"))
    )
    (net (code "1300") (name "TT0_") (class "Default")
      (node (ref "EF01") (pin "AK2") (pinfunction "AK2_AK2") (pintype "output"))
      (node (ref "J13") (pin "P1") (pinfunction "IN3_P1") (pintype "input"))
    )
    (net (code "1301") (name "TT1_") (class "Default")
      (node (ref "EF01") (pin "AR2") (pinfunction "AR2_AR2") (pintype "output"))
      (node (ref "J13") (pin "T2") (pinfunction "IN3_T2") (pintype "input"))
    )
    (net (code "1302") (name "TT2_") (class "Default")
      (node (ref "EF01") (pin "AS2") (pinfunction "AS2_AS2") (pintype "output"))
      (node (ref "J14") (pin "C1") (pinfunction "IN3_C1") (pintype "input"))
    )
    (net (code "1303") (name "TT3_") (class "Default")
      (node (ref "EF01") (pin "AL1") (pinfunction "AL1_AL1") (pintype "output"))
      (node (ref "J14") (pin "F2") (pinfunction "IN3_F2") (pintype "input"))
    )
    (net (code "1304") (name "TT4_") (class "Default")
      (node (ref "EF01") (pin "AM1") (pinfunction "AM1_AM1") (pintype "output"))
      (node (ref "J14") (pin "J1") (pinfunction "IN3_J1") (pintype "input"))
    )
    (net (code "1305") (name "TT5_") (class "Default")
      (node (ref "EF01") (pin "AP2") (pinfunction "AP2_AP2") (pintype "output"))
      (node (ref "J14") (pin "M2") (pinfunction "IN3_M2") (pintype "input"))
    )
    (net (code "1306") (name "TT6_") (class "Default")
      (node (ref "EF01") (pin "AT2") (pinfunction "AT2_AT2") (pintype "output"))
      (node (ref "J14") (pin "P1") (pinfunction "IN3_P1") (pintype "input"))
    )
    (net (code "1307") (name "TT7_") (class "Default")
      (node (ref "EF01") (pin "AN2") (pinfunction "AN2_AN2") (pintype "output"))
      (node (ref "J14") (pin "T2") (pinfunction "IN3_T2") (pintype "input"))
    )
    (net (code "1308") (name "TTI2") (class "Default")
      (node (ref "EF01") (pin "AJ2") (pinfunction "AJ2_AJ2") (pintype "output"))
      (node (ref "EF01") (pin "AK1") (pinfunction "AK1_AK1") (pintype "input"))
    )
    (net (code "1309") (name "TTI_CLOCK") (class "Default")
      (node (ref "EF01") (pin "AN1") (pinfunction "AN1_AN1") (pintype "input"))
      (node (ref "F03") (pin "R2") (pinfunction "R2_R2") (pintype "output"))
    )
    (net (code "1310") (name "TTI_DATA") (class "Default")
      (node (ref "EF01") (pin "AM2") (pinfunction "AM2_AM2") (pintype "output"))
      (node (ref "EF01") (pin "AR1") (pinfunction "AR1_AR1") (pintype "input"))
    )
    (net (code "1311") (name "TTI_SKIP_") (class "Default")
      (node (ref "EF01") (pin "BH2") (pinfunction "BH2_BH2") (pintype "output"))
      (node (ref "F19") (pin "K2") (pinfunction "IN1_K2") (pintype "input"))
    )
    (net (code "1312") (name "TTO_CLOCK_") (class "Default")
      (node (ref "EF02") (pin "BP2") (pinfunction "BP2_BP2") (pintype "input"))
      (node (ref "F03") (pin "K2") (pinfunction "K2_K2") (pintype "output"))
    )
    (net (code "1313") (name "TTO_SKIP_") (class "Default")
      (node (ref "EF02") (pin "BJ2") (pinfunction "BJ2_BJ2") (pintype "output"))
      (node (ref "F19") (pin "L2") (pinfunction "IN2_L2") (pintype "input"))
    )
    (net (code "1314") (name "TT_AC_CLR_") (class "Default")
      (node (ref "EF01") (pin "BE2") (pinfunction "BE2_BE2") (pintype "output"))
      (node (ref "J15") (pin "J1") (pinfunction "IN3_J1") (pintype "input"))
    )
    (net (code "1315") (name "TT_AC_LOAD_") (class "Default")
      (node (ref "D09") (pin "V1") (pinfunction "OUT_V1") (pintype "output"))
      (node (ref "E32") (pin "M2") (pinfunction "IN3_M2") (pintype "input"))
    )
    (net (code "1316") (name "TT_CARRY_INSERT") (class "Default")
      (node (ref "C09") (pin "P1") (pinfunction "IN1_P1") (pintype "input"))
      (node (ref "D09") (pin "N1") (pinfunction "OUT_N1") (pintype "output"))
      (node (ref "E26") (pin "J1") (pinfunction "IN3B_J1") (pintype "input"))
    )
    (net (code "1317") (name "TT_CARRY_INSERT_") (class "Default")
      (node (ref "C09") (pin "S1") (pinfunction "OUT_S1") (pintype "output"))
      (node (ref "E31") (pin "P1") (pinfunction "IN3_P1") (pintype "input"))
      (node (ref "F09") (pin "N2") (pinfunction "IN8_N2") (pintype "input"))
      (node (ref "F27") (pin "N2") (pinfunction "IN4_N2") (pintype "input"))
    )
    (net (code "1318") (name "TT_CARRY_INSERT_C_") (class "Default")
      (node (ref "D09") (pin "H2") (pinfunction "OUT_H2") (pintype "output"))
      (node (ref "D09") (pin "K1") (pinfunction "IN1_K1") (pintype "input"))
    )
    (net (code "1319") (name "TT_CARRY_INSERT_S") (class "Default")
      (node (ref "C09") (pin "S2") (pinfunction "OUT_S2") (pintype "output"))
      (node (ref "EF39") (pin "BE2") (pinfunction "BE2_BE2") (pintype "input"))
    )
    (net (code "1320") (name "TT_CARRY_INSERT_S_") (class "Default")
      (node (ref "C09") (pin "P2") (pinfunction "IN1_P2") (pintype "input"))
      (node (ref "C11") (pin "S2") (pinfunction "OUT_S2") (pintype "output"))
      (node (ref "D09") (pin "L1") (pinfunction "IN2_L1") (pintype "input"))
    )
    (net (code "1321") (name "TT_CYCLE_") (class "Default")
      (node (ref "C10") (pin "N1") (pinfunction "OUT_N1") (pintype "output"))
      (node (ref "F28") (pin "V2") (pinfunction "IN3_V2") (pintype "input"))
    )
    (net (code "1322") (name "TT_DATA") (class "Default")
      (node (ref "C10") (pin "N2") (pinfunction "OUT_N2") (pintype "output"))
      (node (ref "F33") (pin "H2") (pinfunction "IN1D_H2") (pintype "input"))
    )
    (net (code "1323") (name "TT_INCREMENT_") (class "Default")
      (node (ref "D10") (pin "L1") (pinfunction "OUT_L1") (pintype "output"))
      (node (ref "F25") (pin "E2") (pinfunction "IN2_E2") (pintype "input"))
      (node (ref "F25") (pin "J1") (pinfunction "IN2_J1") (pintype "input"))
      (node (ref "F25") (pin "J2") (pinfunction "IN2_J2") (pintype "input"))
    )
    (net (code "1324") (name "TT_INST") (class "Default")
      (node (ref "C10") (pin "F2") (pinfunction "OUT_F2") (pintype "output"))
      (node (ref "C11") (pin "M1") (pinfunction "IN3_M1") (pintype "input"))
      (node (ref "D10") (pin "A1") (pinfunction "IN1_A1") (pintype "input"))
    )
    (net (code "1325") (name "TT_INST_") (class "Default")
      (node (ref "C10") (pin "E2") (pinfunction "IN2_E2") (pintype "input"))
      (node (ref "C10") (pin "M1") (pinfunction "IN2_M1") (pintype "input"))
      (node (ref "D09") (pin "P2") (pinfunction "IN2_P2") (pintype "input"))
      (node (ref "D10") (pin "P2") (pinfunction "OUT_P2") (pintype "output"))
      (node (ref "F19") (pin "C1") (pinfunction "IN3_C1") (pintype "input"))
      (node (ref "F28") (pin "S1") (pinfunction "IN3_S1") (pintype "input"))
      (node (ref "F33") (pin "F2") (pinfunction "IN1C_F2") (pintype "input"))
      (node (ref "H19") (pin "N2") (pinfunction "IN2_N2") (pintype "input"))
    )
    (net (code "1326") (name "TT_INT_") (class "Default")
      (node (ref "E12") (pin "V2") (pinfunction "OUT_V2") (pintype "output"))
      (node (ref "J15") (pin "F2") (pinfunction "IN3_F2") (pintype "input"))
    )
    (net (code "1327") (name "TT_IO_ENABLE_") (class "Default")
      (node (ref "C11") (pin "F2") (pinfunction "IN3_F2") (pintype "input"))
      (node (ref "C11") (pin "N1") (pinfunction "OUT_N1") (pintype "output"))
      (node (ref "D09") (pin "S1") (pinfunction "IN3_S1") (pintype "input"))
      (node (ref "F30") (pin "H2") (pinfunction "IN4_H2") (pintype "input"))
    )
    (net (code "1328") (name "TT_LINE_SHIFT_") (class "Default")
      (node (ref "C09") (pin "D2") (pinfunction "IN1_D2") (pintype "input"))
      (node (ref "C11") (pin "M2") (pinfunction "OUT_M2") (pintype "output"))
      (node (ref "EF34") (pin "AB2") (pinfunction "AB2_AB2") (pintype "input"))
      (node (ref "EF35") (pin "AB2") (pinfunction "AB2_AB2") (pintype "input"))
      (node (ref "EF36") (pin "AB2") (pinfunction "AB2_AB2") (pintype "input"))
      (node (ref "EF37") (pin "AB2") (pinfunction "AB2_AB2") (pintype "input"))
      (node (ref "EF38") (pin "AB2") (pinfunction "AB2_AB2") (pintype "input"))
      (node (ref "EF39") (pin "AB2") (pinfunction "AB2_AB2") (pintype "input"))
    )
    (net (code "1329") (name "TT_L_DISABLE") (class "Default")
      (node (ref "C10") (pin "L1") (pinfunction "IN1_L1") (pintype "input"))
      (node (ref "D09") (pin "S2") (pinfunction "OUT_S2") (pintype "output"))
      (node (ref "E28") (pin "J1") (pinfunction "IN3B_J1") (pintype "input"))
    )
    (net (code "1330") (name "TT_RIGHT_SHIFT_ENABLE") (class "Default")
      (node (ref "C10") (pin "E1") (pinfunction "IN2_E1") (pintype "input"))
      (node (ref "C11") (pin "H2") (pinfunction "OUT_H2") (pintype "output"))
    )
    (net (code "1331") (name "TT_RIGHT_SHIFT_ENABLE_") (class "Default")
      (node (ref "C09") (pin "E2") (pinfunction "IN2_E2") (pintype "input"))
      (node (ref "C10") (pin "F1") (pinfunction "OUT_F1") (pintype "output"))
      (node (ref "E31") (pin "H1") (pinfunction "IN2_H1") (pintype "input"))
    )
    (net (code "1332") (name "TT_SET_") (class "Default")
      (node (ref "C10") (pin "C1") (pinfunction "OUT_C1") (pintype "output"))
      (node (ref "E25") (pin "E1") (pinfunction "IN1_E1") (pintype "input"))
      (node (ref "F28") (pin "L2") (pinfunction "IN3_L2") (pintype "input"))
    )
    (net (code "1333") (name "TT_SHIFT_ENABLE") (class "Default")
      (node (ref "C09") (pin "F2") (pinfunction "OUT_F2") (pintype "output"))
      (node (ref "C09") (pin "H1") (pinfunction "IN1_H1") (pintype "input"))
      (node (ref "F33") (pin "E2") (pinfunction "IN1B_E2") (pintype "input"))
    )
    (net (code "1334") (name "TT_SHIFT_ENABLE_") (class "Default")
      (node (ref "C09") (pin "K1") (pinfunction "OUT_K1") (pintype "output"))
      (node (ref "F24") (pin "B1") (pinfunction "IN2_B1") (pintype "input"))
    )
    (net (code "1335") (name "TT_SKIP_") (class "Default")
      (node (ref "E12") (pin "S1") (pinfunction "OUT_S1") (pintype "output"))
      (node (ref "J15") (pin "C1") (pinfunction "IN3_C1") (pintype "input"))
    )
    (net (code "1336") (name "TX_DATA") (class "Default")
      (node (ref "EF02") (pin "AV2") (pinfunction "AV2_AV2") (pintype "output"))
      (node (ref "J12") (pin "H2") (pinfunction "P$2_H2") (pintype "bidirectional"))
    )
    (net (code "1337") (name "UB") (class "Default")
      (node (ref "B05") (pin "E1") (pinfunction "1_E1") (pintype "output"))
      (node (ref "B06") (pin "P2") (pinfunction "IN1_P2") (pintype "input"))
    )
    (net (code "1338") (name "UF") (class "Default")
      (node (ref "A05") (pin "M1") (pinfunction "IN2_M1") (pintype "input"))
      (node (ref "B05") (pin "H2") (pinfunction "1_H2") (pintype "output"))
      (node (ref "B05") (pin "P1") (pinfunction "D_P1") (pintype "input"))
    )
    (net (code "1339") (name "UF_") (class "Default")
      (node (ref "A06") (pin "J1") (pinfunction "IN2_J1") (pintype "input"))
      (node (ref "B05") (pin "J2") (pinfunction "0_J2") (pintype "output"))
      (node (ref "E13") (pin "D1") (pinfunction "IN1D_D1") (pintype "input"))
      (node (ref "F11") (pin "D1") (pinfunction "IN4_D1") (pintype "input"))
    )
    (net (code "1340") (name "UINT") (class "Default")
      (node (ref "A05") (pin "M2") (pinfunction "IN2_M2") (pintype "input"))
      (node (ref "B04") (pin "J2") (pinfunction "IN1_J2") (pintype "input"))
      (node (ref "B05") (pin "P2") (pinfunction "1_P2") (pintype "output"))
    )
    (net (code "1341") (name "UINT_") (class "Default")
      (node (ref "A05") (pin "S2") (pinfunction "OUT_S2") (pintype "output"))
      (node (ref "F19") (pin "N1") (pinfunction "IN2_N1") (pintype "input"))
    )
    (net (code "1342") (name "USF_") (class "Default")
      (node (ref "B04") (pin "T2") (pinfunction "IN1_T2") (pintype "input"))
      (node (ref "B05") (pin "V1") (pinfunction "0_V1") (pintype "output"))
    )
    (net (code "1343") (name "VCC") (class "Default")
      (node (ref "A40") (pin "A2") (pinfunction "P$2_A2") (pintype "bidirectional"))
      (node (ref "B40") (pin "A2") (pinfunction "P$2_A2") (pintype "bidirectional"))
      (node (ref "C40") (pin "A2") (pinfunction "P$2_A2") (pintype "bidirectional"))
      (node (ref "D03") (pin "A2") (pinfunction "P$2_A2") (pintype "bidirectional"))
      (node (ref "E40") (pin "A2") (pinfunction "P$2_A2") (pintype "bidirectional"))
      (node (ref "F40") (pin "A2") (pinfunction "P$2_A2") (pintype "bidirectional"))
    )
    (net (code "1344") (name "WC_OVERFLOW_") (class "Default")
      (node (ref "E33") (pin "H2") (pinfunction "1_H2") (pintype "output"))
      (node (ref "H19") (pin "U2") (pinfunction "IN2_U2") (pintype "input"))
    )
    (net (code "1345") (name "WC_SET") (class "Default")
      (node (ref "E23") (pin "M2") (pinfunction "D_M2") (pintype "input"))
      (node (ref "F22") (pin "N2") (pinfunction "OUT_N2") (pintype "output"))
    )
    (net (code "1346") (name "WC_SET_") (class "Default")
      (node (ref "A19") (pin "A1") (pinfunction "IN1_A1") (pintype "input"))
      (node (ref "F22") (pin "L2") (pinfunction "IN1_L2") (pintype "input"))
      (node (ref "F22") (pin "R1") (pinfunction "IN2_R1") (pintype "input"))
      (node (ref "F22") (pin "V2") (pinfunction "OUT_V2") (pintype "output"))
    )
    (net (code "1347") (name "WORD_COUNT") (class "Default")
      (node (ref "E23") (pin "P1") (pinfunction "D_P1") (pintype "input"))
      (node (ref "E23") (pin "P2") (pinfunction "1_P2") (pintype "output"))
      (node (ref "E27") (pin "D2") (pinfunction "IN1A_D2") (pintype "input"))
      (node (ref "E30") (pin "J1") (pinfunction "IN3B_J1") (pintype "input"))
    )
    (net (code "1348") (name "WORD_COUNT_") (class "Default")
      (node (ref "A19") (pin "B1") (pinfunction "IN2_B1") (pintype "input"))
      (node (ref "D40") (pin "A1") (pinfunction "P$2_A1") (pintype "bidirectional"))
      (node (ref "E12") (pin "P2") (pinfunction "IN1_P2") (pintype "input"))
      (node (ref "E23") (pin "R2") (pinfunction "0_R2") (pintype "output"))
      (node (ref "E25") (pin "H1") (pinfunction "IN3_H1") (pintype "input"))
    )
    (net (code "1349") (name "X_AXIS") (class "Default")
      (node (ref "D03") (pin "D2") (pinfunction "P$2_D2") (pintype "bidirectional"))
      (node (ref "HJ24") (pin "BS2") (pinfunction "BS2_BS2") (pintype "output"))
    )
    (net (code "1350") (name "X_STROBE") (class "Default")
      (node (ref "HJ23") (pin "AS1") (pinfunction "AS1_AS1") (pintype "output"))
      (node (ref "HJ24") (pin "AD2") (pinfunction "AD2_AD2") (pintype "bidirectional"))
    )
    (net (code "1351") (name "Y_AXIS") (class "Default")
      (node (ref "D03") (pin "E2") (pinfunction "P$2_E2") (pintype "bidirectional"))
      (node (ref "HJ25") (pin "BS2") (pinfunction "BS2_BS2") (pintype "output"))
    )
    (net (code "1352") (name "Y_STROBE") (class "Default")
      (node (ref "HJ23") (pin "AP2") (pinfunction "AP2_AP2") (pintype "output"))
      (node (ref "HJ25") (pin "AD2") (pinfunction "AD2_AD2") (pintype "bidirectional"))
    )
    (net (code "1353") (name "ZONE01_INDEX") (class "Default")
      (node (ref "HJ32") (pin "AK2") (pinfunction "AK2_AK2") (pintype "input"))
      (node (ref "HJ34") (pin "BD2") (pinfunction "P$2_BD2") (pintype "bidirectional"))
    )
    (net (code "1354") (name "ZONE02_INDEX") (class "Default")
      (node (ref "HJ32") (pin "AR2") (pinfunction "AR2_AR2") (pintype "input"))
      (node (ref "HJ34") (pin "BE2") (pinfunction "P$2_BE2") (pintype "bidirectional"))
    )
    (net (code "1355") (name "ZONE03_INDEX") (class "Default")
      (node (ref "HJ32") (pin "AP2") (pinfunction "AP2_AP2") (pintype "input"))
      (node (ref "HJ34") (pin "BF2") (pinfunction "P$2_BF2") (pintype "bidirectional"))
    )
    (net (code "1356") (name "ZONE04_INDEX") (class "Default")
      (node (ref "HJ32") (pin "BE2") (pinfunction "BE2_BE2") (pintype "input"))
      (node (ref "HJ34") (pin "BJ2") (pinfunction "P$2_BJ2") (pintype "bidirectional"))
    )
    (net (code "1357") (name "ZONE05_INDEX") (class "Default")
      (node (ref "HJ32") (pin "AS2") (pinfunction "AS2_AS2") (pintype "input"))
      (node (ref "HJ34") (pin "BK2") (pinfunction "P$2_BK2") (pintype "bidirectional"))
    )
    (net (code "1358") (name "ZONE06_INDEX") (class "Default")
      (node (ref "HJ32") (pin "BS1") (pinfunction "BS1_BS1") (pintype "input"))
      (node (ref "HJ34") (pin "BL2") (pinfunction "P$2_BL2") (pintype "bidirectional"))
    )
    (net (code "1359") (name "ZONE07_INDEX") (class "Default")
      (node (ref "HJ32") (pin "BR1") (pinfunction "BR1_BR1") (pintype "input"))
      (node (ref "HJ34") (pin "BM2") (pinfunction "P$2_BM2") (pintype "bidirectional"))
    )
    (net (code "1360") (name "ZONE08_INDEX") (class "Default")
      (node (ref "HJ32") (pin "BK2") (pinfunction "BK2_BK2") (pintype "input"))
      (node (ref "HJ34") (pin "BN2") (pinfunction "P$2_BN2") (pintype "bidirectional"))
    )
    (net (code "1361") (name "ZONE09_INDEX") (class "Default")
      (node (ref "HJ32") (pin "BL2") (pinfunction "BL2_BL2") (pintype "input"))
      (node (ref "HJ34") (pin "BS2") (pinfunction "P$2_BS2") (pintype "bidirectional"))
    )
    (net (code "1362") (name "ZONE10_INDEX") (class "Default")
      (node (ref "HJ32") (pin "AL2") (pinfunction "AL2_AL2") (pintype "input"))
      (node (ref "HJ34") (pin "BT2") (pinfunction "P$2_BT2") (pintype "bidirectional"))
    )
    (net (code "1363") (name "ZONE11_INDEX") (class "Default")
      (node (ref "HJ32") (pin "AE1") (pinfunction "AE1_AE1") (pintype "input"))
      (node (ref "HJ34") (pin "BU2") (pinfunction "P$2_BU2") (pintype "bidirectional"))
    )
    (net (code "1364") (name "ZONE12_INDEX") (class "Default")
      (node (ref "HJ32") (pin "AE2") (pinfunction "AE2_AE2") (pintype "input"))
      (node (ref "HJ34") (pin "BV2") (pinfunction "P$2_BV2") (pintype "bidirectional"))
    )
    (net (code "1365") (name "Z_AXIS") (class "Default")
      (node (ref "D03") (pin "F2") (pinfunction "P$2_F2") (pintype "bidirectional"))
      (node (ref "HJ23") (pin "AE2") (pinfunction "AE2_AE2") (pintype "output"))
    )
    (net (code "1366") (name "unconnected-(A04-PadT2)") (class "Default")
      (node (ref "A04") (pin "T2") (pinfunction "T2_T2") (pintype "output"))
    )
    (net (code "1367") (name "unconnected-(A08C-ODD-PadK1)") (class "Default")
      (node (ref "A08") (pin "K1") (pinfunction "ODD_K1") (pintype "output"))
    )
    (net (code "1368") (name "unconnected-(A10C-EVEN-PadL1)") (class "Default")
      (node (ref "A10") (pin "L1") (pinfunction "EVEN_L1") (pintype "output"))
    )
    (net (code "1369") (name "unconnected-(AB02-PadBJ2)") (class "Default")
      (node (ref "AB02") (pin "BJ2") (pinfunction "BJ2_BJ2") (pintype "output"))
    )
    (net (code "1370") (name "unconnected-(AB02-PadBK2)") (class "Default")
      (node (ref "AB02") (pin "BK2") (pinfunction "BK2_BK2") (pintype "passive"))
    )
    (net (code "1371") (name "unconnected-(AB02-PadBR2)") (class "Default")
      (node (ref "AB02") (pin "BR2") (pinfunction "BR2_BR2") (pintype "passive"))
    )
    (net (code "1372") (name "unconnected-(AB02-PadBS2)") (class "Default")
      (node (ref "AB02") (pin "BS2") (pinfunction "BS2_BS2") (pintype "passive"))
    )
    (net (code "1373") (name "unconnected-(B05A-0-PadF1)") (class "Default")
      (node (ref "B05") (pin "F1") (pinfunction "0_F1") (pintype "output"))
    )
    (net (code "1374") (name "unconnected-(B05G-0-PadU1)") (class "Default")
      (node (ref "B05") (pin "U1") (pinfunction "0_U1") (pintype "output"))
    )
    (net (code "1375") (name "unconnected-(B05H-1-PadV2)") (class "Default")
      (node (ref "B05") (pin "V2") (pinfunction "1_V2") (pintype "output"))
    )
    (net (code "1376") (name "unconnected-(B11A-1-PadE1)") (class "Default")
      (node (ref "B11") (pin "E1") (pinfunction "1_E1") (pintype "output"))
    )
    (net (code "1377") (name "unconnected-(B11D-1-PadH2)") (class "Default")
      (node (ref "B11") (pin "H2") (pinfunction "1_H2") (pintype "output"))
    )
    (net (code "1378") (name "unconnected-(B11E-1-PadL1)") (class "Default")
      (node (ref "B11") (pin "L1") (pinfunction "1_L1") (pintype "output"))
    )
    (net (code "1379") (name "unconnected-(B11F-0-PadR2)") (class "Default")
      (node (ref "B11") (pin "R2") (pinfunction "0_R2") (pintype "output"))
    )
    (net (code "1380") (name "unconnected-(B11G-0-PadU1)") (class "Default")
      (node (ref "B11") (pin "U1") (pinfunction "0_U1") (pintype "output"))
    )
    (net (code "1381") (name "unconnected-(B17F-0-PadR2)") (class "Default")
      (node (ref "B17") (pin "R2") (pinfunction "0_R2") (pintype "output"))
    )
    (net (code "1382") (name "unconnected-(B17G-0-PadU1)") (class "Default")
      (node (ref "B17") (pin "U1") (pinfunction "0_U1") (pintype "output"))
    )
    (net (code "1383") (name "unconnected-(B17H-0-PadV1)") (class "Default")
      (node (ref "B17") (pin "V1") (pinfunction "0_V1") (pintype "output"))
    )
    (net (code "1384") (name "unconnected-(B18F-0-PadR2)") (class "Default")
      (node (ref "B18") (pin "R2") (pinfunction "0_R2") (pintype "output"))
    )
    (net (code "1385") (name "unconnected-(B18G-0-PadU1)") (class "Default")
      (node (ref "B18") (pin "U1") (pinfunction "0_U1") (pintype "output"))
    )
    (net (code "1386") (name "unconnected-(B18H-0-PadV1)") (class "Default")
      (node (ref "B18") (pin "V1") (pinfunction "0_V1") (pintype "output"))
    )
    (net (code "1387") (name "unconnected-(B19A-0-PadF1)") (class "Default")
      (node (ref "B19") (pin "F1") (pinfunction "0_F1") (pintype "output"))
    )
    (net (code "1388") (name "unconnected-(B19D-0-PadJ2)") (class "Default")
      (node (ref "B19") (pin "J2") (pinfunction "0_J2") (pintype "output"))
    )
    (net (code "1389") (name "unconnected-(B19E-0-PadM1)") (class "Default")
      (node (ref "B19") (pin "M1") (pinfunction "0_M1") (pintype "output"))
    )
    (net (code "1390") (name "unconnected-(B19F-0-PadR2)") (class "Default")
      (node (ref "B19") (pin "R2") (pinfunction "0_R2") (pintype "output"))
    )
    (net (code "1391") (name "unconnected-(B19G-0-PadU1)") (class "Default")
      (node (ref "B19") (pin "U1") (pinfunction "0_U1") (pintype "output"))
    )
    (net (code "1392") (name "unconnected-(B19H-0-PadV1)") (class "Default")
      (node (ref "B19") (pin "V1") (pinfunction "0_V1") (pintype "output"))
    )
    (net (code "1393") (name "unconnected-(C13-PadJ2)") (class "Default")
      (node (ref "C13") (pin "J2") (pinfunction "J2_J2") (pintype "output"))
    )
    (net (code "1394") (name "unconnected-(C13-PadK2)") (class "Default")
      (node (ref "C13") (pin "K2") (pinfunction "K2_K2") (pintype "output"))
    )
    (net (code "1395") (name "unconnected-(C13-PadL2)") (class "Default")
      (node (ref "C13") (pin "L2") (pinfunction "L2_L2") (pintype "output"))
    )
    (net (code "1396") (name "unconnected-(C13-PadM2)") (class "Default")
      (node (ref "C13") (pin "M2") (pinfunction "M2_M2") (pintype "output"))
    )
    (net (code "1397") (name "unconnected-(C13-PadN2)") (class "Default")
      (node (ref "C13") (pin "N2") (pinfunction "N2_N2") (pintype "output"))
    )
    (net (code "1398") (name "unconnected-(C13-PadR2)") (class "Default")
      (node (ref "C13") (pin "R2") (pinfunction "R2_R2") (pintype "output"))
    )
    (net (code "1399") (name "unconnected-(C13-PadT2)") (class "Default")
      (node (ref "C13") (pin "T2") (pinfunction "T2_T2") (pintype "output"))
    )
    (net (code "1400") (name "unconnected-(C13-PadU2)") (class "Default")
      (node (ref "C13") (pin "U2") (pinfunction "U2_U2") (pintype "output"))
    )
    (net (code "1401") (name "unconnected-(C13-PadV2)") (class "Default")
      (node (ref "C13") (pin "V2") (pinfunction "V2_V2") (pintype "output"))
    )
    (net (code "1402") (name "unconnected-(C22H-0-PadV1)") (class "Default")
      (node (ref "C22") (pin "V1") (pinfunction "0_V1") (pintype "output"))
    )
    (net (code "1403") (name "unconnected-(D06-PadJ2)") (class "Default")
      (node (ref "D06") (pin "J2") (pinfunction "J2_J2") (pintype "output"))
    )
    (net (code "1404") (name "unconnected-(D06-PadK2)") (class "Default")
      (node (ref "D06") (pin "K2") (pinfunction "K2_K2") (pintype "output"))
    )
    (net (code "1405") (name "unconnected-(D06-PadL2)") (class "Default")
      (node (ref "D06") (pin "L2") (pinfunction "L2_L2") (pintype "output"))
    )
    (net (code "1406") (name "unconnected-(D06-PadM2)") (class "Default")
      (node (ref "D06") (pin "M2") (pinfunction "M2_M2") (pintype "output"))
    )
    (net (code "1407") (name "unconnected-(D06-PadN2)") (class "Default")
      (node (ref "D06") (pin "N2") (pinfunction "N2_N2") (pintype "output"))
    )
    (net (code "1408") (name "unconnected-(D06-PadP2)") (class "Default")
      (node (ref "D06") (pin "P2") (pinfunction "P2_P2") (pintype "output"))
    )
    (net (code "1409") (name "unconnected-(D06-PadS2)") (class "Default")
      (node (ref "D06") (pin "S2") (pinfunction "S2_S2") (pintype "output"))
    )
    (net (code "1410") (name "unconnected-(D06-PadT2)") (class "Default")
      (node (ref "D06") (pin "T2") (pinfunction "T2_T2") (pintype "output"))
    )
    (net (code "1411") (name "unconnected-(D06-PadU2)") (class "Default")
      (node (ref "D06") (pin "U2") (pinfunction "U2_U2") (pintype "output"))
    )
    (net (code "1412") (name "unconnected-(D06-PadV2)") (class "Default")
      (node (ref "D06") (pin "V2") (pinfunction "V2_V2") (pintype "output"))
    )
    (net (code "1413") (name "unconnected-(D24H-0-PadV1)") (class "Default")
      (node (ref "D24") (pin "V1") (pinfunction "0_V1") (pintype "output"))
    )
    (net (code "1414") (name "unconnected-(E16-PadJ2)") (class "Default")
      (node (ref "E16") (pin "J2") (pinfunction "J2_J2") (pintype "output"))
    )
    (net (code "1415") (name "unconnected-(E16-PadK2)") (class "Default")
      (node (ref "E16") (pin "K2") (pinfunction "K2_K2") (pintype "output"))
    )
    (net (code "1416") (name "unconnected-(E16-PadL2)") (class "Default")
      (node (ref "E16") (pin "L2") (pinfunction "L2_L2") (pintype "output"))
    )
    (net (code "1417") (name "unconnected-(E16-PadM2)") (class "Default")
      (node (ref "E16") (pin "M2") (pinfunction "M2_M2") (pintype "output"))
    )
    (net (code "1418") (name "unconnected-(E16-PadN2)") (class "Default")
      (node (ref "E16") (pin "N2") (pinfunction "N2_N2") (pintype "output"))
    )
    (net (code "1419") (name "unconnected-(E16-PadP2)") (class "Default")
      (node (ref "E16") (pin "P2") (pinfunction "P2_P2") (pintype "output"))
    )
    (net (code "1420") (name "unconnected-(E16-PadS2)") (class "Default")
      (node (ref "E16") (pin "S2") (pinfunction "S2_S2") (pintype "output"))
    )
    (net (code "1421") (name "unconnected-(E16-PadT2)") (class "Default")
      (node (ref "E16") (pin "T2") (pinfunction "T2_T2") (pintype "output"))
    )
    (net (code "1422") (name "unconnected-(E16-PadU2)") (class "Default")
      (node (ref "E16") (pin "U2") (pinfunction "U2_U2") (pintype "output"))
    )
    (net (code "1423") (name "unconnected-(E16-PadV2)") (class "Default")
      (node (ref "E16") (pin "V2") (pinfunction "V2_V2") (pintype "output"))
    )
    (net (code "1424") (name "unconnected-(E17-PadJ2)") (class "Default")
      (node (ref "E17") (pin "J2") (pinfunction "J2_J2") (pintype "output"))
    )
    (net (code "1425") (name "unconnected-(E17-PadK2)") (class "Default")
      (node (ref "E17") (pin "K2") (pinfunction "K2_K2") (pintype "output"))
    )
    (net (code "1426") (name "unconnected-(E17-PadL2)") (class "Default")
      (node (ref "E17") (pin "L2") (pinfunction "L2_L2") (pintype "output"))
    )
    (net (code "1427") (name "unconnected-(E17-PadN2)") (class "Default")
      (node (ref "E17") (pin "N2") (pinfunction "N2_N2") (pintype "output"))
    )
    (net (code "1428") (name "unconnected-(E17-PadP2)") (class "Default")
      (node (ref "E17") (pin "P2") (pinfunction "P2_P2") (pintype "output"))
    )
    (net (code "1429") (name "unconnected-(E17-PadR2)") (class "Default")
      (node (ref "E17") (pin "R2") (pinfunction "R2_R2") (pintype "output"))
    )
    (net (code "1430") (name "unconnected-(E17-PadS2)") (class "Default")
      (node (ref "E17") (pin "S2") (pinfunction "S2_S2") (pintype "output"))
    )
    (net (code "1431") (name "unconnected-(E17-PadT2)") (class "Default")
      (node (ref "E17") (pin "T2") (pinfunction "T2_T2") (pintype "output"))
    )
    (net (code "1432") (name "unconnected-(E17-PadV2)") (class "Default")
      (node (ref "E17") (pin "V2") (pinfunction "V2_V2") (pintype "output"))
    )
    (net (code "1433") (name "unconnected-(E18D-0-PadJ2)") (class "Default")
      (node (ref "E18") (pin "J2") (pinfunction "0_J2") (pintype "output"))
    )
    (net (code "1434") (name "unconnected-(E18E-1-PadL1)") (class "Default")
      (node (ref "E18") (pin "L1") (pinfunction "1_L1") (pintype "output"))
    )
    (net (code "1435") (name "unconnected-(E18G-0-PadU1)") (class "Default")
      (node (ref "E18") (pin "U1") (pinfunction "0_U1") (pintype "output"))
    )
    (net (code "1436") (name "unconnected-(E19A-0-PadF1)") (class "Default")
      (node (ref "E19") (pin "F1") (pinfunction "0_F1") (pintype "output"))
    )
    (net (code "1437") (name "unconnected-(E20F-0-PadR2)") (class "Default")
      (node (ref "E20") (pin "R2") (pinfunction "0_R2") (pintype "output"))
    )
    (net (code "1438") (name "unconnected-(E20G-0-PadU1)") (class "Default")
      (node (ref "E20") (pin "U1") (pinfunction "0_U1") (pintype "output"))
    )
    (net (code "1439") (name "unconnected-(E22N-OUT-PadV2)") (class "Default")
      (node (ref "E22") (pin "V2") (pinfunction "OUT_V2") (pintype "output"))
    )
    (net (code "1440") (name "unconnected-(E23A-1-PadE1)") (class "Default")
      (node (ref "E23") (pin "E1") (pinfunction "1_E1") (pintype "output"))
    )
    (net (code "1441") (name "unconnected-(E23E-1-PadL1)") (class "Default")
      (node (ref "E23") (pin "L1") (pinfunction "1_L1") (pintype "output"))
    )
    (net (code "1442") (name "unconnected-(E33A-0-PadF1)") (class "Default")
      (node (ref "E33") (pin "F1") (pinfunction "0_F1") (pintype "output"))
    )
    (net (code "1443") (name "unconnected-(E33D-0-PadJ2)") (class "Default")
      (node (ref "E33") (pin "J2") (pinfunction "0_J2") (pintype "output"))
    )
    (net (code "1444") (name "unconnected-(E33E-1-PadL1)") (class "Default")
      (node (ref "E33") (pin "L1") (pinfunction "1_L1") (pintype "output"))
    )
    (net (code "1445") (name "unconnected-(E33F-1-PadP2)") (class "Default")
      (node (ref "E33") (pin "P2") (pinfunction "1_P2") (pintype "output"))
    )
    (net (code "1446") (name "unconnected-(EF01-PadAD1)") (class "Default")
      (node (ref "EF01") (pin "AD1") (pinfunction "AD1_AD1") (pintype "output"))
    )
    (net (code "1447") (name "unconnected-(EF01-PadAS1)") (class "Default")
      (node (ref "EF01") (pin "AS1") (pinfunction "AS1_AS1") (pintype "output"))
    )
    (net (code "1448") (name "unconnected-(EF01-PadBK2)") (class "Default")
      (node (ref "EF01") (pin "BK2") (pinfunction "BK2_BK2") (pintype "output"))
    )
    (net (code "1449") (name "unconnected-(EF01-PadBN2)") (class "Default")
      (node (ref "EF01") (pin "BN2") (pinfunction "BN2_BN2") (pintype "output"))
    )
    (net (code "1450") (name "unconnected-(EF01-PadBS1)") (class "Default")
      (node (ref "EF01") (pin "BS1") (pinfunction "BS1_BS1") (pintype "output"))
    )
    (net (code "1451") (name "unconnected-(EF01-PadBS2)") (class "Default")
      (node (ref "EF01") (pin "BS2") (pinfunction "BS2_BS2") (pintype "output"))
    )
    (net (code "1452") (name "unconnected-(EF01-PadBU2)") (class "Default")
      (node (ref "EF01") (pin "BU2") (pinfunction "BU2_BU2") (pintype "output"))
    )
    (net (code "1453") (name "unconnected-(EF02-PadAD1)") (class "Default")
      (node (ref "EF02") (pin "AD1") (pinfunction "AD1_AD1") (pintype "output"))
    )
    (net (code "1454") (name "unconnected-(EF02-PadAD2)") (class "Default")
      (node (ref "EF02") (pin "AD2") (pinfunction "AD2_AD2") (pintype "output"))
    )
    (net (code "1455") (name "unconnected-(EF02-PadAJ1)") (class "Default")
      (node (ref "EF02") (pin "AJ1") (pinfunction "AJ1_AJ1") (pintype "output"))
    )
    (net (code "1456") (name "unconnected-(EF02-PadAR1)") (class "Default")
      (node (ref "EF02") (pin "AR1") (pinfunction "AR1_AR1") (pintype "output"))
    )
    (net (code "1457") (name "unconnected-(EF02-PadBP1)") (class "Default")
      (node (ref "EF02") (pin "BP1") (pinfunction "BP1_BP1") (pintype "output"))
    )
    (net (code "1458") (name "unconnected-(EF02-PadBR2)") (class "Default")
      (node (ref "EF02") (pin "BR2") (pinfunction "BR2_BR2") (pintype "output"))
    )
    (net (code "1459") (name "unconnected-(EF10C-CN2-PadAN2)") (class "Default")
      (node (ref "EF10") (pin "AN2") (pinfunction "CN2_AN2") (pintype "output"))
    )
    (net (code "1460") (name "unconnected-(EF34-PadAL2)") (class "Default")
      (node (ref "EF34") (pin "AL2") (pinfunction "AL2_AL2") (pintype "output"))
    )
    (net (code "1461") (name "unconnected-(EF34-PadAM2)") (class "Default")
      (node (ref "EF34") (pin "AM2") (pinfunction "AM2_AM2") (pintype "output"))
    )
    (net (code "1462") (name "unconnected-(EF34-PadAN1)") (class "Default")
      (node (ref "EF34") (pin "AN1") (pinfunction "AN1_AN1") (pintype "output"))
    )
    (net (code "1463") (name "unconnected-(EF34-PadAP1)") (class "Default")
      (node (ref "EF34") (pin "AP1") (pinfunction "AP1_AP1") (pintype "output"))
    )
    (net (code "1464") (name "unconnected-(EF35-PadAL2)") (class "Default")
      (node (ref "EF35") (pin "AL2") (pinfunction "AL2_AL2") (pintype "output"))
    )
    (net (code "1465") (name "unconnected-(EF35-PadAM2)") (class "Default")
      (node (ref "EF35") (pin "AM2") (pinfunction "AM2_AM2") (pintype "output"))
    )
    (net (code "1466") (name "unconnected-(EF35-PadAN1)") (class "Default")
      (node (ref "EF35") (pin "AN1") (pinfunction "AN1_AN1") (pintype "output"))
    )
    (net (code "1467") (name "unconnected-(EF35-PadAP1)") (class "Default")
      (node (ref "EF35") (pin "AP1") (pinfunction "AP1_AP1") (pintype "output"))
    )
    (net (code "1468") (name "unconnected-(EF36-PadAL2)") (class "Default")
      (node (ref "EF36") (pin "AL2") (pinfunction "AL2_AL2") (pintype "output"))
    )
    (net (code "1469") (name "unconnected-(EF36-PadAM2)") (class "Default")
      (node (ref "EF36") (pin "AM2") (pinfunction "AM2_AM2") (pintype "output"))
    )
    (net (code "1470") (name "unconnected-(EF36-PadAN1)") (class "Default")
      (node (ref "EF36") (pin "AN1") (pinfunction "AN1_AN1") (pintype "output"))
    )
    (net (code "1471") (name "unconnected-(EF36-PadAP1)") (class "Default")
      (node (ref "EF36") (pin "AP1") (pinfunction "AP1_AP1") (pintype "output"))
    )
    (net (code "1472") (name "unconnected-(EF37-PadAL2)") (class "Default")
      (node (ref "EF37") (pin "AL2") (pinfunction "AL2_AL2") (pintype "output"))
    )
    (net (code "1473") (name "unconnected-(EF37-PadAM2)") (class "Default")
      (node (ref "EF37") (pin "AM2") (pinfunction "AM2_AM2") (pintype "output"))
    )
    (net (code "1474") (name "unconnected-(EF37-PadAN1)") (class "Default")
      (node (ref "EF37") (pin "AN1") (pinfunction "AN1_AN1") (pintype "output"))
    )
    (net (code "1475") (name "unconnected-(EF37-PadAP1)") (class "Default")
      (node (ref "EF37") (pin "AP1") (pinfunction "AP1_AP1") (pintype "output"))
    )
    (net (code "1476") (name "unconnected-(EF38-PadAL2)") (class "Default")
      (node (ref "EF38") (pin "AL2") (pinfunction "AL2_AL2") (pintype "output"))
    )
    (net (code "1477") (name "unconnected-(EF38-PadAN1)") (class "Default")
      (node (ref "EF38") (pin "AN1") (pinfunction "AN1_AN1") (pintype "output"))
    )
    (net (code "1478") (name "unconnected-(EF38-PadAP1)") (class "Default")
      (node (ref "EF38") (pin "AP1") (pinfunction "AP1_AP1") (pintype "output"))
    )
    (net (code "1479") (name "unconnected-(EF39-PadAL2)") (class "Default")
      (node (ref "EF39") (pin "AL2") (pinfunction "AL2_AL2") (pintype "output"))
    )
    (net (code "1480") (name "unconnected-(EF39-PadAM2)") (class "Default")
      (node (ref "EF39") (pin "AM2") (pinfunction "AM2_AM2") (pintype "output"))
    )
    (net (code "1481") (name "unconnected-(EF39-PadAN1)") (class "Default")
      (node (ref "EF39") (pin "AN1") (pinfunction "AN1_AN1") (pintype "output"))
    )
    (net (code "1482") (name "unconnected-(EF39-PadAP1)") (class "Default")
      (node (ref "EF39") (pin "AP1") (pinfunction "AP1_AP1") (pintype "output"))
    )
    (net (code "1483") (name "unconnected-(F03-PadL2)") (class "Default")
      (node (ref "F03") (pin "L2") (pinfunction "L2_L2") (pintype "output"))
    )
    (net (code "1484") (name "unconnected-(F03-PadM2)") (class "Default")
      (node (ref "F03") (pin "M2") (pinfunction "M2_M2") (pintype "output"))
    )
    (net (code "1485") (name "unconnected-(F03-PadN2)") (class "Default")
      (node (ref "F03") (pin "N2") (pinfunction "N2_N2") (pintype "output"))
    )
    (net (code "1486") (name "unconnected-(F12-PadJ2)") (class "Default")
      (node (ref "F12") (pin "J2") (pinfunction "J2_J2") (pintype "output"))
    )
    (net (code "1487") (name "unconnected-(F12-PadK2)") (class "Default")
      (node (ref "F12") (pin "K2") (pinfunction "K2_K2") (pintype "output"))
    )
    (net (code "1488") (name "unconnected-(F12-PadL2)") (class "Default")
      (node (ref "F12") (pin "L2") (pinfunction "L2_L2") (pintype "output"))
    )
    (net (code "1489") (name "unconnected-(F12-PadM2)") (class "Default")
      (node (ref "F12") (pin "M2") (pinfunction "M2_M2") (pintype "output"))
    )
    (net (code "1490") (name "unconnected-(F12-PadN2)") (class "Default")
      (node (ref "F12") (pin "N2") (pinfunction "N2_N2") (pintype "output"))
    )
    (net (code "1491") (name "unconnected-(F12-PadP2)") (class "Default")
      (node (ref "F12") (pin "P2") (pinfunction "P2_P2") (pintype "output"))
    )
    (net (code "1492") (name "unconnected-(F12-PadR2)") (class "Default")
      (node (ref "F12") (pin "R2") (pinfunction "R2_R2") (pintype "output"))
    )
    (net (code "1493") (name "unconnected-(F12-PadS2)") (class "Default")
      (node (ref "F12") (pin "S2") (pinfunction "S2_S2") (pintype "output"))
    )
    (net (code "1494") (name "unconnected-(F12-PadU2)") (class "Default")
      (node (ref "F12") (pin "U2") (pinfunction "U2_U2") (pintype "output"))
    )
    (net (code "1495") (name "unconnected-(F12-PadV2)") (class "Default")
      (node (ref "F12") (pin "V2") (pinfunction "V2_V2") (pintype "output"))
    )
    (net (code "1496") (name "unconnected-(F13-PadJ2)") (class "Default")
      (node (ref "F13") (pin "J2") (pinfunction "J2_J2") (pintype "output"))
    )
    (net (code "1497") (name "unconnected-(F13-PadK2)") (class "Default")
      (node (ref "F13") (pin "K2") (pinfunction "K2_K2") (pintype "output"))
    )
    (net (code "1498") (name "unconnected-(F13-PadL2)") (class "Default")
      (node (ref "F13") (pin "L2") (pinfunction "L2_L2") (pintype "output"))
    )
    (net (code "1499") (name "unconnected-(F13-PadN2)") (class "Default")
      (node (ref "F13") (pin "N2") (pinfunction "N2_N2") (pintype "output"))
    )
    (net (code "1500") (name "unconnected-(F13-PadP2)") (class "Default")
      (node (ref "F13") (pin "P2") (pinfunction "P2_P2") (pintype "output"))
    )
    (net (code "1501") (name "unconnected-(F13-PadR2)") (class "Default")
      (node (ref "F13") (pin "R2") (pinfunction "R2_R2") (pintype "output"))
    )
    (net (code "1502") (name "unconnected-(F13-PadS2)") (class "Default")
      (node (ref "F13") (pin "S2") (pinfunction "S2_S2") (pintype "output"))
    )
    (net (code "1503") (name "unconnected-(F13-PadU2)") (class "Default")
      (node (ref "F13") (pin "U2") (pinfunction "U2_U2") (pintype "output"))
    )
    (net (code "1504") (name "unconnected-(F13-PadV2)") (class "Default")
      (node (ref "F13") (pin "V2") (pinfunction "V2_V2") (pintype "output"))
    )
    (net (code "1505") (name "unconnected-(F14-PadJ2)") (class "Default")
      (node (ref "F14") (pin "J2") (pinfunction "J2_J2") (pintype "output"))
    )
    (net (code "1506") (name "unconnected-(F14-PadK2)") (class "Default")
      (node (ref "F14") (pin "K2") (pinfunction "K2_K2") (pintype "output"))
    )
    (net (code "1507") (name "unconnected-(F14-PadL2)") (class "Default")
      (node (ref "F14") (pin "L2") (pinfunction "L2_L2") (pintype "output"))
    )
    (net (code "1508") (name "unconnected-(F14-PadM2)") (class "Default")
      (node (ref "F14") (pin "M2") (pinfunction "M2_M2") (pintype "output"))
    )
    (net (code "1509") (name "unconnected-(F14-PadN2)") (class "Default")
      (node (ref "F14") (pin "N2") (pinfunction "N2_N2") (pintype "output"))
    )
    (net (code "1510") (name "unconnected-(F14-PadP2)") (class "Default")
      (node (ref "F14") (pin "P2") (pinfunction "P2_P2") (pintype "output"))
    )
    (net (code "1511") (name "unconnected-(F14-PadR2)") (class "Default")
      (node (ref "F14") (pin "R2") (pinfunction "R2_R2") (pintype "output"))
    )
    (net (code "1512") (name "unconnected-(F14-PadU2)") (class "Default")
      (node (ref "F14") (pin "U2") (pinfunction "U2_U2") (pintype "output"))
    )
    (net (code "1513") (name "unconnected-(F14-PadV2)") (class "Default")
      (node (ref "F14") (pin "V2") (pinfunction "V2_V2") (pintype "output"))
    )
    (net (code "1514") (name "unconnected-(F15-PadJ2)") (class "Default")
      (node (ref "F15") (pin "J2") (pinfunction "J2_J2") (pintype "output"))
    )
    (net (code "1515") (name "unconnected-(F15-PadK2)") (class "Default")
      (node (ref "F15") (pin "K2") (pinfunction "K2_K2") (pintype "output"))
    )
    (net (code "1516") (name "unconnected-(F15-PadL2)") (class "Default")
      (node (ref "F15") (pin "L2") (pinfunction "L2_L2") (pintype "output"))
    )
    (net (code "1517") (name "unconnected-(F15-PadN2)") (class "Default")
      (node (ref "F15") (pin "N2") (pinfunction "N2_N2") (pintype "output"))
    )
    (net (code "1518") (name "unconnected-(F15-PadP2)") (class "Default")
      (node (ref "F15") (pin "P2") (pinfunction "P2_P2") (pintype "output"))
    )
    (net (code "1519") (name "unconnected-(F15-PadR2)") (class "Default")
      (node (ref "F15") (pin "R2") (pinfunction "R2_R2") (pintype "output"))
    )
    (net (code "1520") (name "unconnected-(F15-PadS2)") (class "Default")
      (node (ref "F15") (pin "S2") (pinfunction "S2_S2") (pintype "output"))
    )
    (net (code "1521") (name "unconnected-(F15-PadU2)") (class "Default")
      (node (ref "F15") (pin "U2") (pinfunction "U2_U2") (pintype "output"))
    )
    (net (code "1522") (name "unconnected-(F15-PadV2)") (class "Default")
      (node (ref "F15") (pin "V2") (pinfunction "V2_V2") (pintype "output"))
    )
    (net (code "1523") (name "unconnected-(F16-PadJ2)") (class "Default")
      (node (ref "F16") (pin "J2") (pinfunction "J2_J2") (pintype "output"))
    )
    (net (code "1524") (name "unconnected-(F16-PadK2)") (class "Default")
      (node (ref "F16") (pin "K2") (pinfunction "K2_K2") (pintype "output"))
    )
    (net (code "1525") (name "unconnected-(F16-PadL2)") (class "Default")
      (node (ref "F16") (pin "L2") (pinfunction "L2_L2") (pintype "output"))
    )
    (net (code "1526") (name "unconnected-(F16-PadM2)") (class "Default")
      (node (ref "F16") (pin "M2") (pinfunction "M2_M2") (pintype "output"))
    )
    (net (code "1527") (name "unconnected-(F16-PadN2)") (class "Default")
      (node (ref "F16") (pin "N2") (pinfunction "N2_N2") (pintype "output"))
    )
    (net (code "1528") (name "unconnected-(F16-PadP2)") (class "Default")
      (node (ref "F16") (pin "P2") (pinfunction "P2_P2") (pintype "output"))
    )
    (net (code "1529") (name "unconnected-(F16-PadR2)") (class "Default")
      (node (ref "F16") (pin "R2") (pinfunction "R2_R2") (pintype "output"))
    )
    (net (code "1530") (name "unconnected-(F16-PadU2)") (class "Default")
      (node (ref "F16") (pin "U2") (pinfunction "U2_U2") (pintype "output"))
    )
    (net (code "1531") (name "unconnected-(F16-PadV2)") (class "Default")
      (node (ref "F16") (pin "V2") (pinfunction "V2_V2") (pintype "output"))
    )
    (net (code "1532") (name "unconnected-(F17-PadJ2)") (class "Default")
      (node (ref "F17") (pin "J2") (pinfunction "J2_J2") (pintype "output"))
    )
    (net (code "1533") (name "unconnected-(F17-PadK2)") (class "Default")
      (node (ref "F17") (pin "K2") (pinfunction "K2_K2") (pintype "output"))
    )
    (net (code "1534") (name "unconnected-(F17-PadL2)") (class "Default")
      (node (ref "F17") (pin "L2") (pinfunction "L2_L2") (pintype "output"))
    )
    (net (code "1535") (name "unconnected-(F17-PadN2)") (class "Default")
      (node (ref "F17") (pin "N2") (pinfunction "N2_N2") (pintype "output"))
    )
    (net (code "1536") (name "unconnected-(F17-PadP2)") (class "Default")
      (node (ref "F17") (pin "P2") (pinfunction "P2_P2") (pintype "output"))
    )
    (net (code "1537") (name "unconnected-(F17-PadR2)") (class "Default")
      (node (ref "F17") (pin "R2") (pinfunction "R2_R2") (pintype "output"))
    )
    (net (code "1538") (name "unconnected-(F17-PadS2)") (class "Default")
      (node (ref "F17") (pin "S2") (pinfunction "S2_S2") (pintype "output"))
    )
    (net (code "1539") (name "unconnected-(F17-PadU2)") (class "Default")
      (node (ref "F17") (pin "U2") (pinfunction "U2_U2") (pintype "output"))
    )
    (net (code "1540") (name "unconnected-(F17-PadV2)") (class "Default")
      (node (ref "F17") (pin "V2") (pinfunction "V2_V2") (pintype "output"))
    )
    (net (code "1541") (name "unconnected-(F18-PadJ2)") (class "Default")
      (node (ref "F18") (pin "J2") (pinfunction "J2_J2") (pintype "output"))
    )
    (net (code "1542") (name "unconnected-(F18-PadK2)") (class "Default")
      (node (ref "F18") (pin "K2") (pinfunction "K2_K2") (pintype "output"))
    )
    (net (code "1543") (name "unconnected-(F18-PadL2)") (class "Default")
      (node (ref "F18") (pin "L2") (pinfunction "L2_L2") (pintype "output"))
    )
    (net (code "1544") (name "unconnected-(F18-PadM2)") (class "Default")
      (node (ref "F18") (pin "M2") (pinfunction "M2_M2") (pintype "output"))
    )
    (net (code "1545") (name "unconnected-(F18-PadN2)") (class "Default")
      (node (ref "F18") (pin "N2") (pinfunction "N2_N2") (pintype "output"))
    )
    (net (code "1546") (name "unconnected-(F18-PadP2)") (class "Default")
      (node (ref "F18") (pin "P2") (pinfunction "P2_P2") (pintype "output"))
    )
    (net (code "1547") (name "unconnected-(F18-PadR2)") (class "Default")
      (node (ref "F18") (pin "R2") (pinfunction "R2_R2") (pintype "output"))
    )
    (net (code "1548") (name "unconnected-(F18-PadU2)") (class "Default")
      (node (ref "F18") (pin "U2") (pinfunction "U2_U2") (pintype "output"))
    )
    (net (code "1549") (name "unconnected-(F18-PadV2)") (class "Default")
      (node (ref "F18") (pin "V2") (pinfunction "V2_V2") (pintype "output"))
    )
    (net (code "1550") (name "unconnected-(H30-PadD1)") (class "Default")
      (node (ref "H30") (pin "D1") (pinfunction "D1_D1") (pintype "output"))
    )
    (net (code "1551") (name "unconnected-(H30-PadE1)") (class "Default")
      (node (ref "H30") (pin "E1") (pinfunction "E1_E1") (pintype "output"))
    )
    (net (code "1552") (name "unconnected-(H30-PadK1)") (class "Default")
      (node (ref "H30") (pin "K1") (pinfunction "K1_K1") (pintype "output"))
    )
    (net (code "1553") (name "unconnected-(HJ26-PadAJ1)") (class "Default")
      (node (ref "HJ26") (pin "AJ1") (pinfunction "AJ1_AJ1") (pintype "output"))
    )
    (net (code "1554") (name "unconnected-(HJ26-PadAJ2)") (class "Default")
      (node (ref "HJ26") (pin "AJ2") (pinfunction "AJ2_AJ2") (pintype "output"))
    )
    (net (code "1555") (name "unconnected-(HJ26-PadAM2)") (class "Default")
      (node (ref "HJ26") (pin "AM2") (pinfunction "AM2_AM2") (pintype "output"))
    )
    (net (code "1556") (name "unconnected-(HJ26-PadAT2)") (class "Default")
      (node (ref "HJ26") (pin "AT2") (pinfunction "AT2_AT2") (pintype "output"))
    )
    (net (code "1557") (name "unconnected-(HJ27D-AM-PadAM2)") (class "Default")
      (node (ref "HJ27") (pin "AM2") (pinfunction "AM_AM2") (pintype "output"))
    )
    (net (code "1558") (name "unconnected-(HJ27D-AP-PadAP2)") (class "Default")
      (node (ref "HJ27") (pin "AP2") (pinfunction "AP_AP2") (pintype "output"))
    )
    (net (code "1559") (name "unconnected-(HJ28-PadAJ1)") (class "Default")
      (node (ref "HJ28") (pin "AJ1") (pinfunction "AJ1_AJ1") (pintype "output"))
    )
    (net (code "1560") (name "unconnected-(HJ28-PadAJ2)") (class "Default")
      (node (ref "HJ28") (pin "AJ2") (pinfunction "AJ2_AJ2") (pintype "output"))
    )
    (net (code "1561") (name "unconnected-(HJ28-PadAS1)") (class "Default")
      (node (ref "HJ28") (pin "AS1") (pinfunction "AS1_AS1") (pintype "output"))
    )
    (net (code "1562") (name "unconnected-(HJ28-PadAU2)") (class "Default")
      (node (ref "HJ28") (pin "AU2") (pinfunction "AU2_AU2") (pintype "output"))
    )
    (net (code "1563") (name "unconnected-(HJ29-PadAM2)") (class "Default")
      (node (ref "HJ29") (pin "AM2") (pinfunction "AM2_AM2") (pintype "output"))
    )
    (net (code "1564") (name "unconnected-(HJ29-PadAP2)") (class "Default")
      (node (ref "HJ29") (pin "AP2") (pinfunction "AP2_AP2") (pintype "output"))
    )
    (net (code "1565") (name "unconnected-(HJ29-PadAU2)") (class "Default")
      (node (ref "HJ29") (pin "AU2") (pinfunction "AU2_AU2") (pintype "output"))
    )
    (net (code "1566") (name "unconnected-(HJ29-PadBD2)") (class "Default")
      (node (ref "HJ29") (pin "BD2") (pinfunction "BD2_BD2") (pintype "output"))
    )
    (net (code "1567") (name "unconnected-(HJ29-PadBJ2)") (class "Default")
      (node (ref "HJ29") (pin "BJ2") (pinfunction "BJ2_BJ2") (pintype "output"))
    )
    (net (code "1568") (name "unconnected-(HJ29-PadBK2)") (class "Default")
      (node (ref "HJ29") (pin "BK2") (pinfunction "BK2_BK2") (pintype "output"))
    )
    (net (code "1569") (name "unconnected-(HJ29-PadBS2)") (class "Default")
      (node (ref "HJ29") (pin "BS2") (pinfunction "BS2_BS2") (pintype "output"))
    )
    (net (code "1570") (name "unconnected-(HJ31-PadAE2)") (class "Default")
      (node (ref "HJ31") (pin "AE2") (pinfunction "AE2_AE2") (pintype "output"))
    )
    (net (code "1571") (name "unconnected-(HJ31-PadBF1)") (class "Default")
      (node (ref "HJ31") (pin "BF1") (pinfunction "BF1_BF1") (pintype "output"))
    )
    (net (code "1572") (name "unconnected-(HJ31-PadBH1)") (class "Default")
      (node (ref "HJ31") (pin "BH1") (pinfunction "BH1_BH1") (pintype "output"))
    )
    (net (code "1573") (name "unconnected-(HJ31-PadBH2)") (class "Default")
      (node (ref "HJ31") (pin "BH2") (pinfunction "BH2_BH2") (pintype "output"))
    )
    (net (code "1574") (name "unconnected-(HJ31-PadBM1)") (class "Default")
      (node (ref "HJ31") (pin "BM1") (pinfunction "BM1_BM1") (pintype "output"))
    )
    (net (code "1575") (name "unconnected-(HJ31-PadBR1)") (class "Default")
      (node (ref "HJ31") (pin "BR1") (pinfunction "BR1_BR1") (pintype "output"))
    )
    (net (code "1576") (name "unconnected-(J33-PadH1)") (class "Default")
      (node (ref "J33") (pin "H1") (pinfunction "H1_H1") (pintype "output"))
    )
    (net (code "1577") (name "unconnected-(J33-PadJ2)") (class "Default")
      (node (ref "J33") (pin "J2") (pinfunction "J2_J2") (pintype "output"))
    )
    (net (code "1578") (name "unconnected-(J33-PadL1)") (class "Default")
      (node (ref "J33") (pin "L1") (pinfunction "L1_L1") (pintype "output"))
    )
    (net (code "1579") (name "unconnected-(J33-PadM1)") (class "Default")
      (node (ref "J33") (pin "M1") (pinfunction "M1_M1") (pintype "output"))
    )
    (net (code "1580") (name "unconnected-(J33-PadS1)") (class "Default")
      (node (ref "J33") (pin "S1") (pinfunction "S1_S1") (pintype "output"))
    )
    (net (code "1581") (name "unconnected-(J33-PadT2)") (class "Default")
      (node (ref "J33") (pin "T2") (pinfunction "T2_T2") (pintype "output"))
    )
    (net (code "1582") (name "unconnected-(J33-PadU1)") (class "Default")
      (node (ref "J33") (pin "U1") (pinfunction "U1_U1") (pintype "output"))
    )
  )
)
